# pdp8i-dec.net
KiCad netlist of a schematic drawn in EAGLE
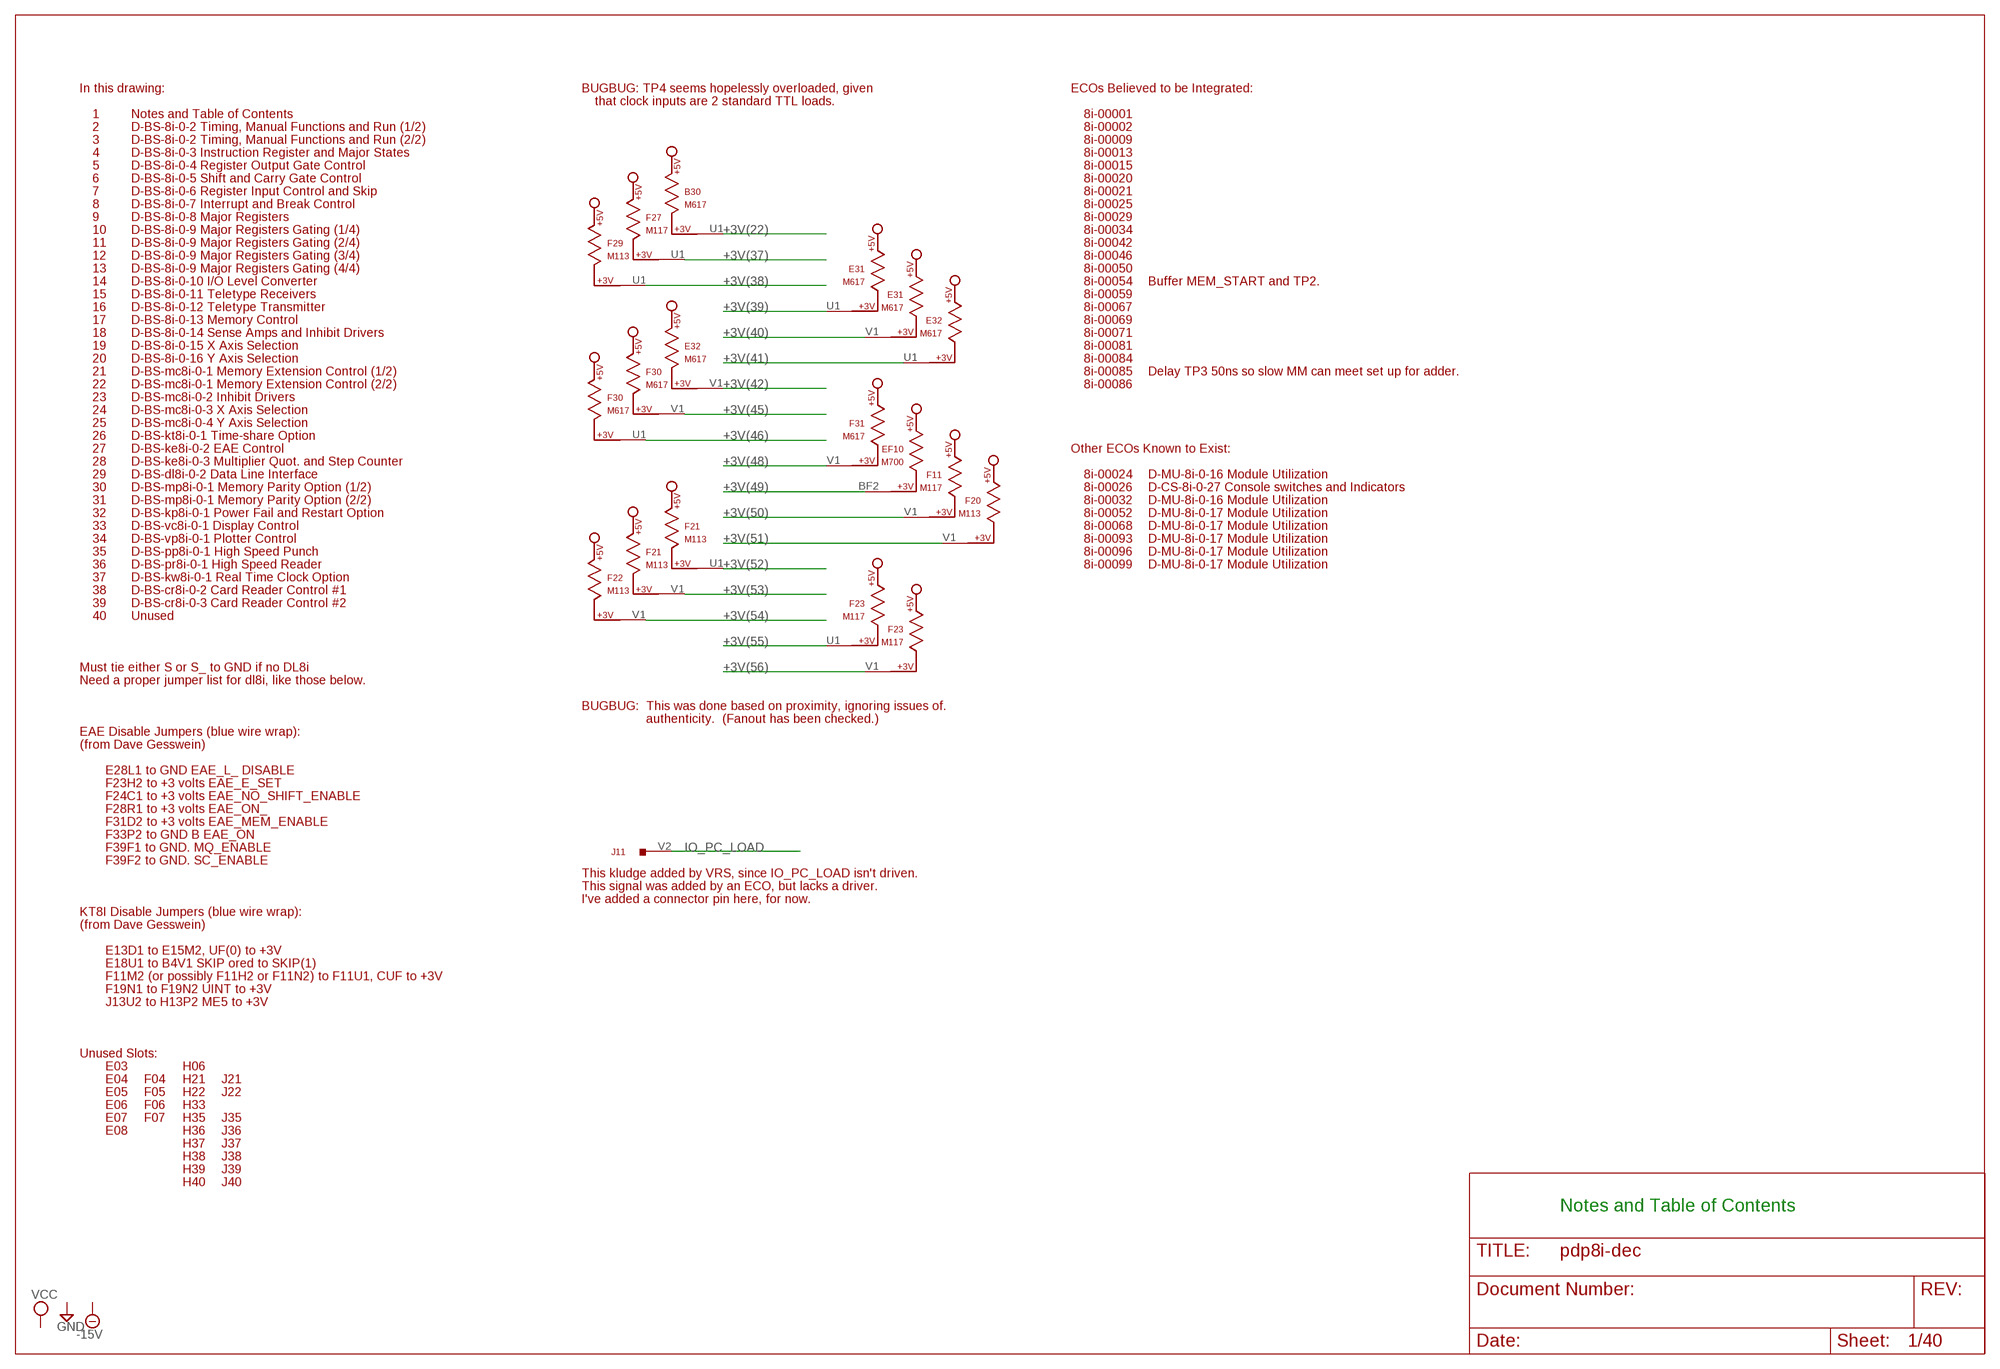
[diagram p0: schematic, sheet 1]
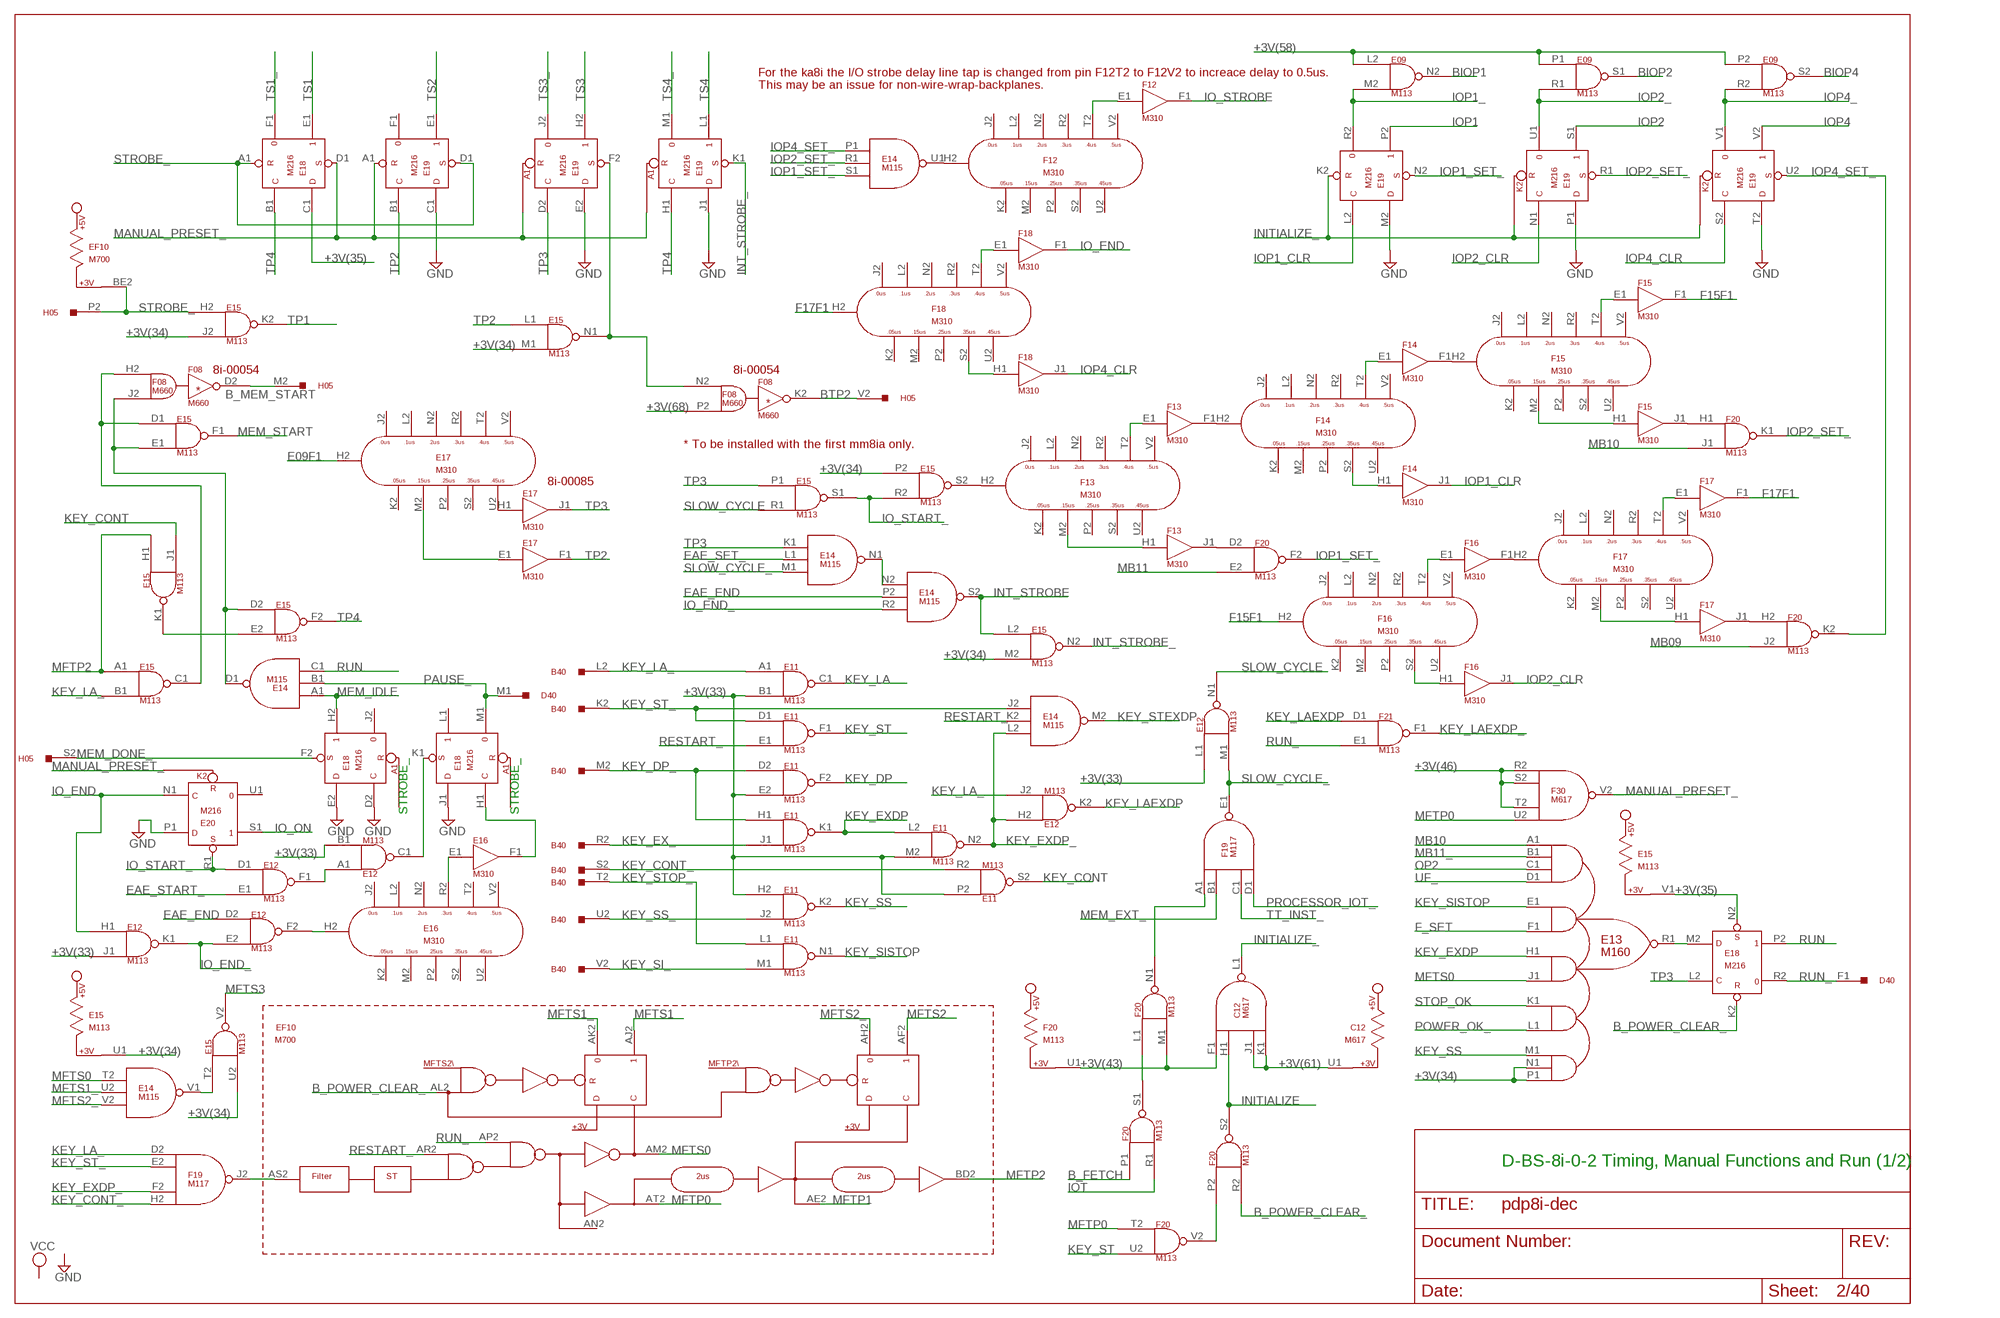
[diagram p1: schematic, sheet 2]
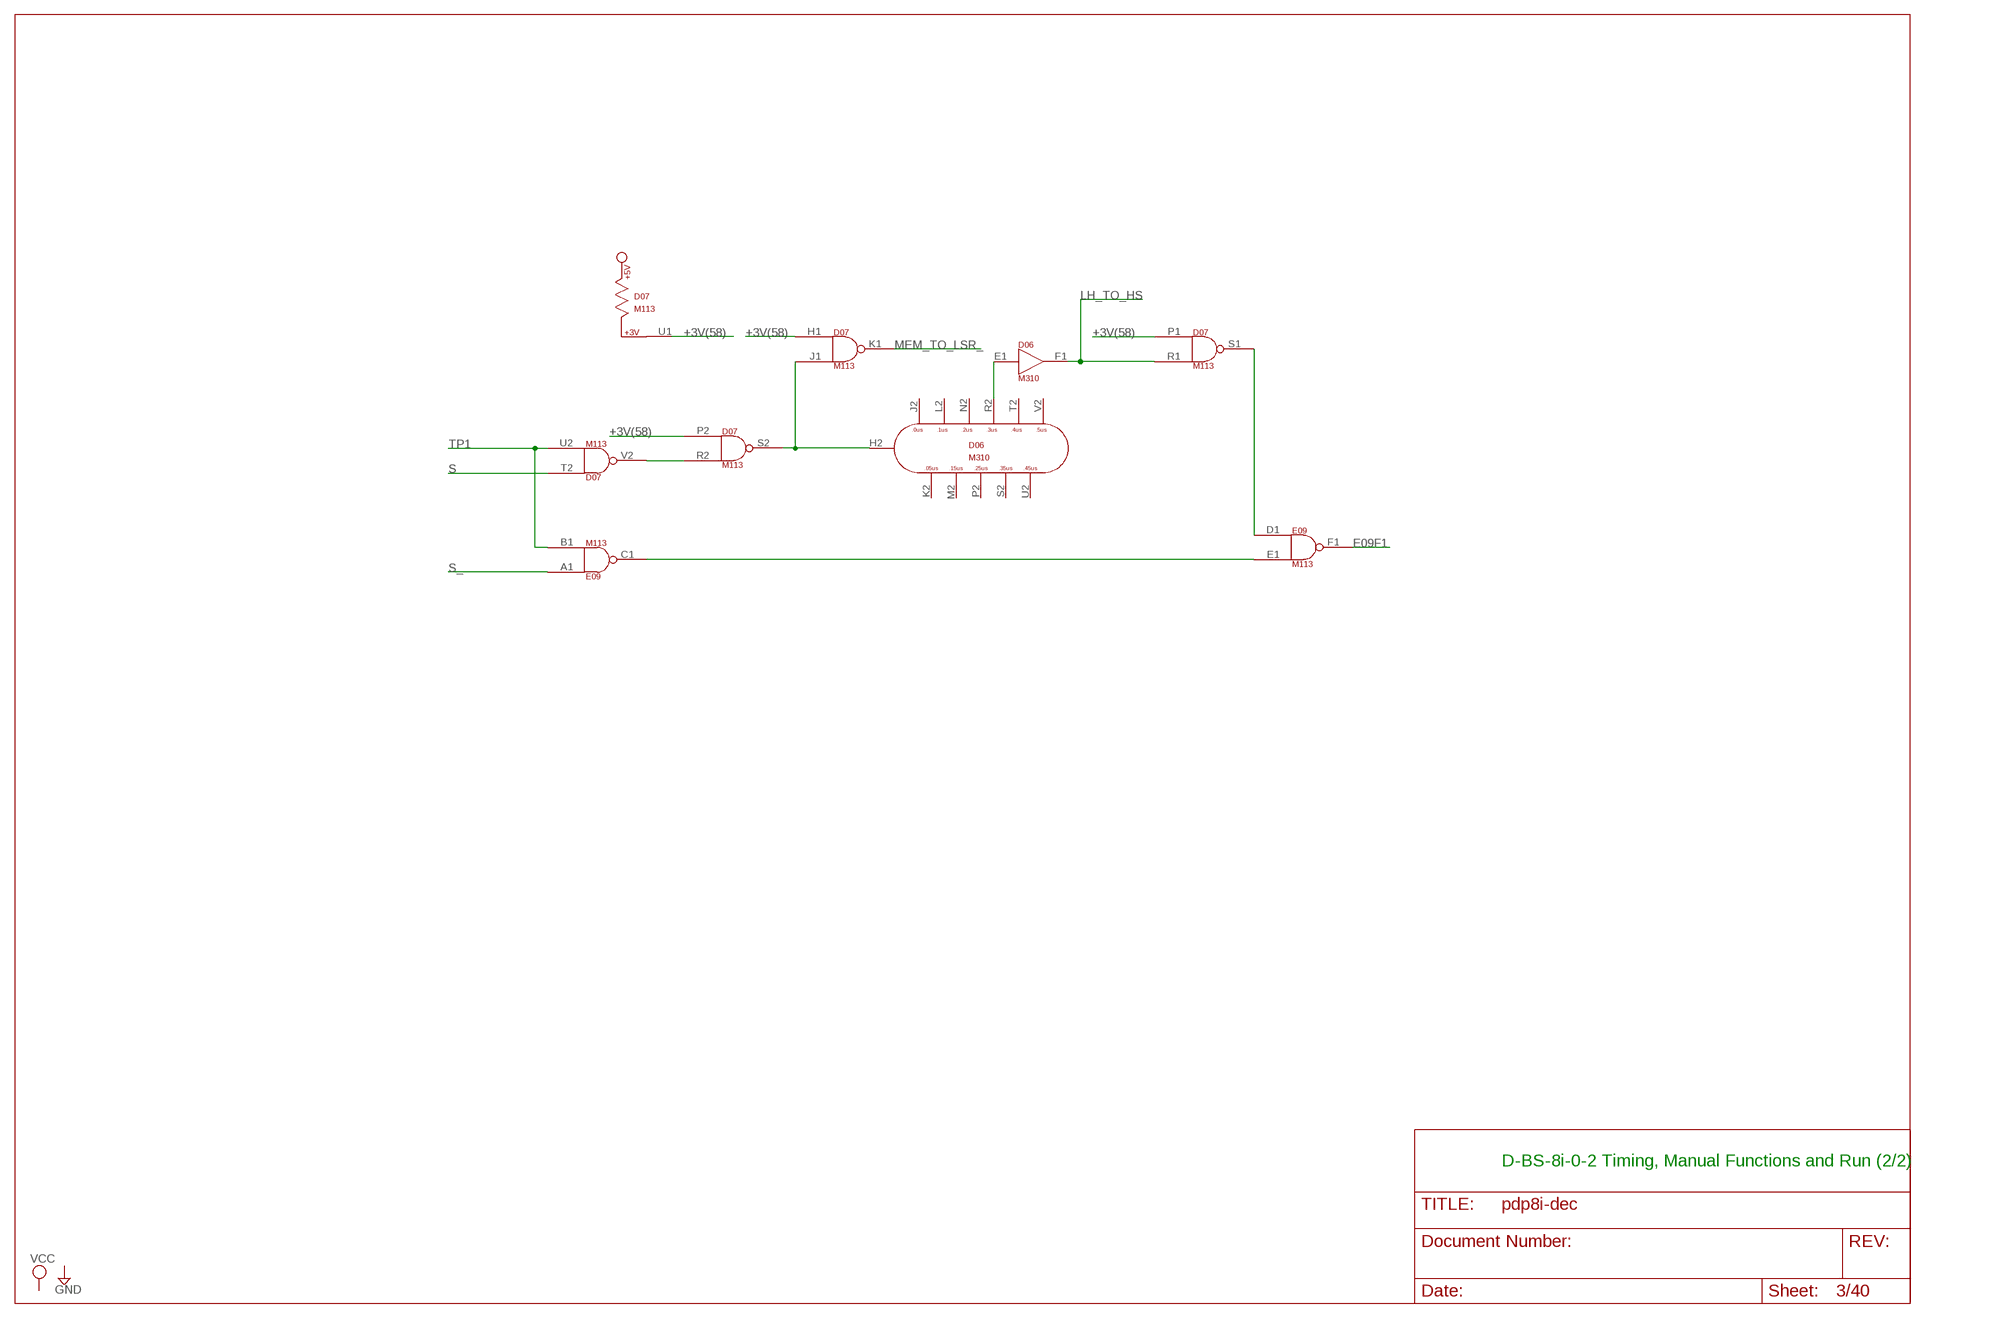
[diagram p2: schematic, sheet 3]
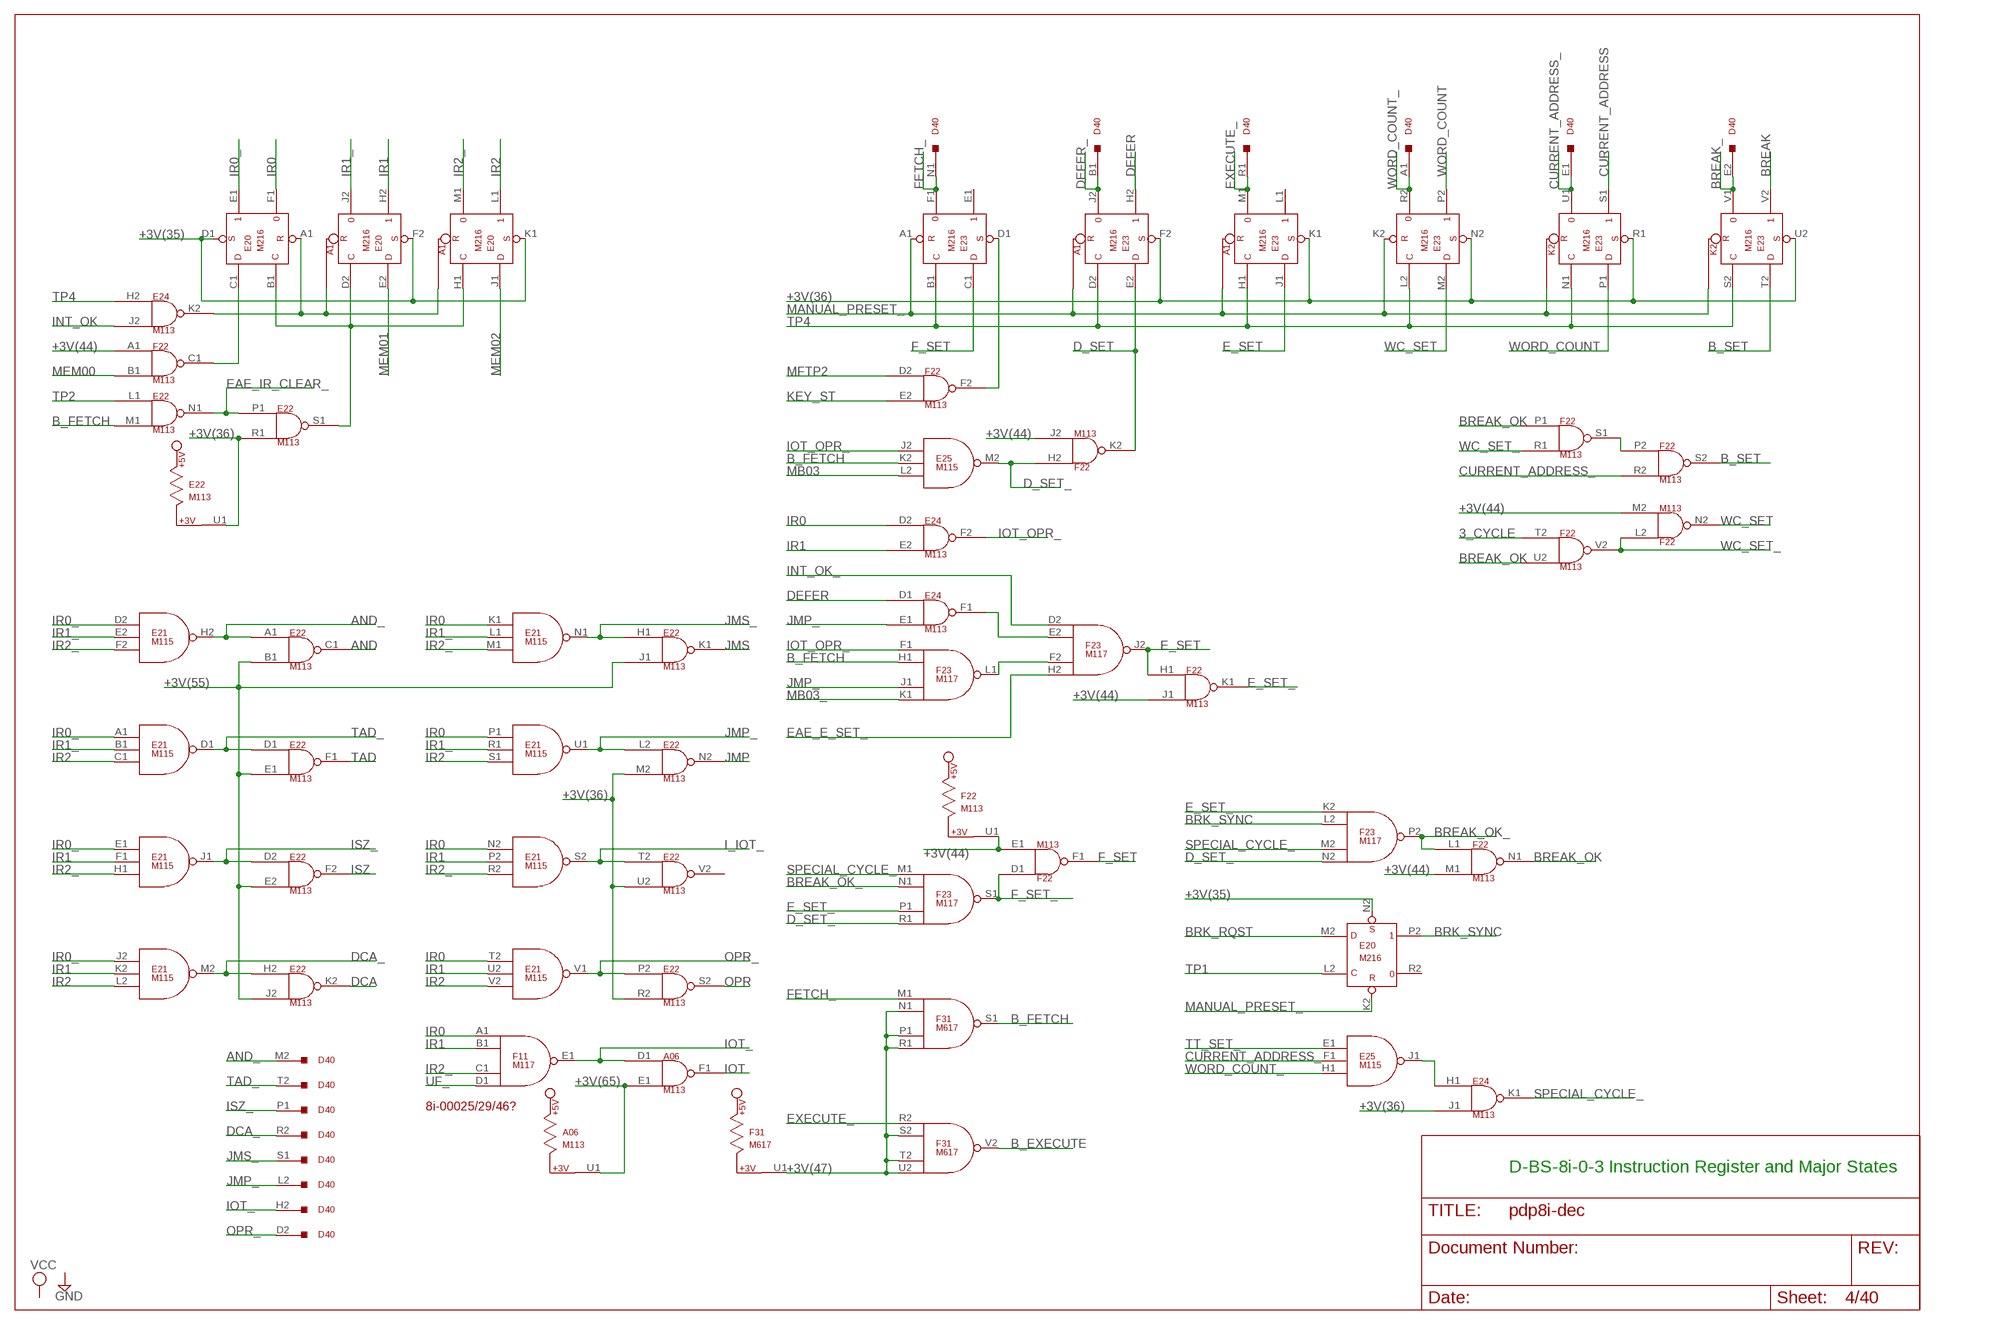
[diagram p3: schematic, sheet 4]
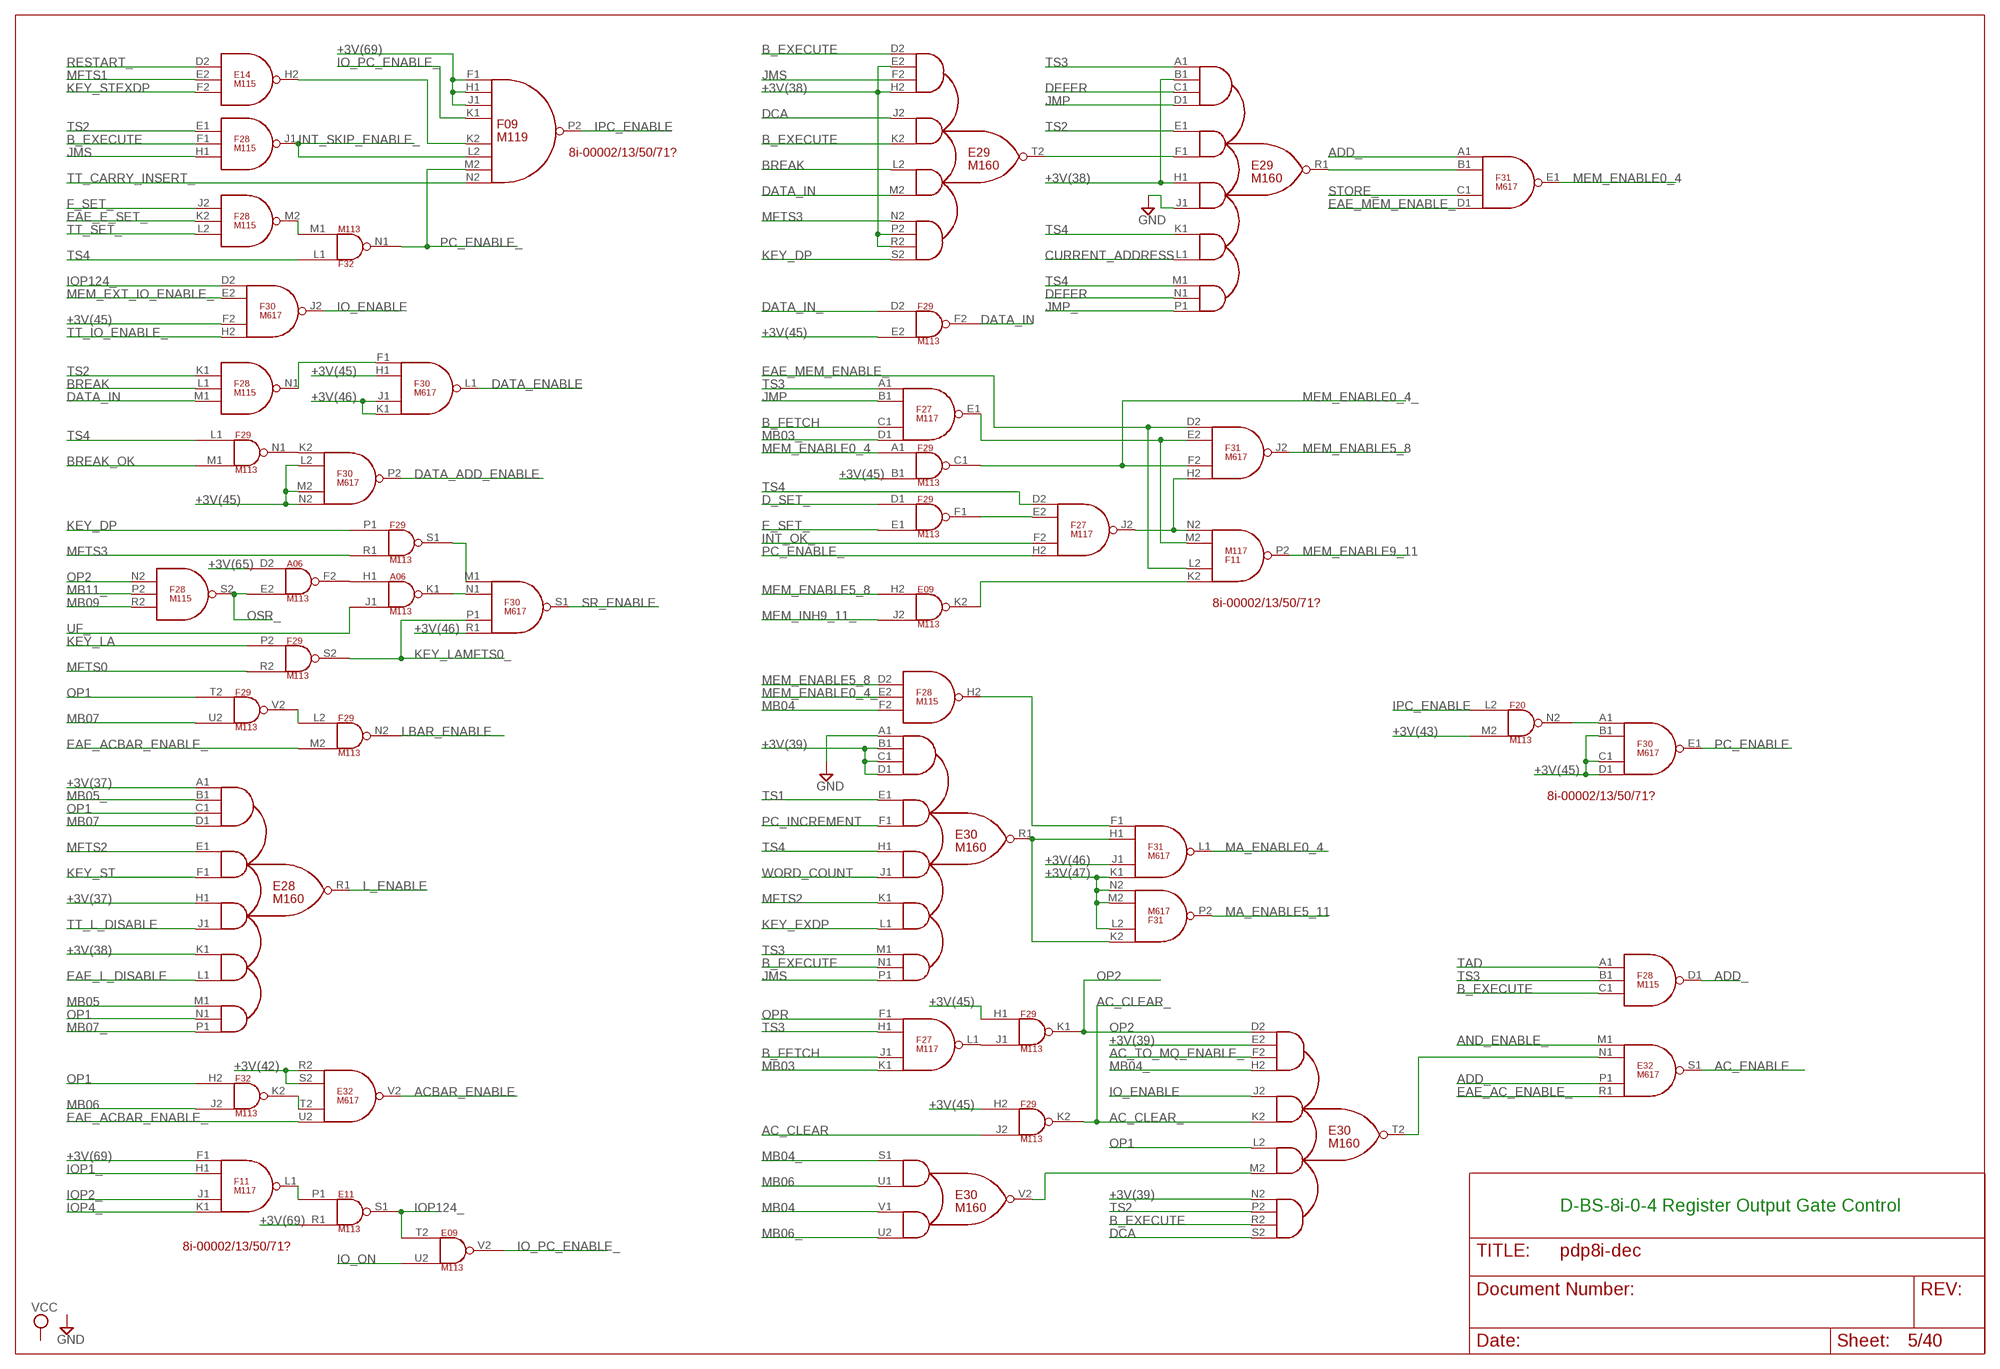
[diagram p4: schematic, sheet 5]
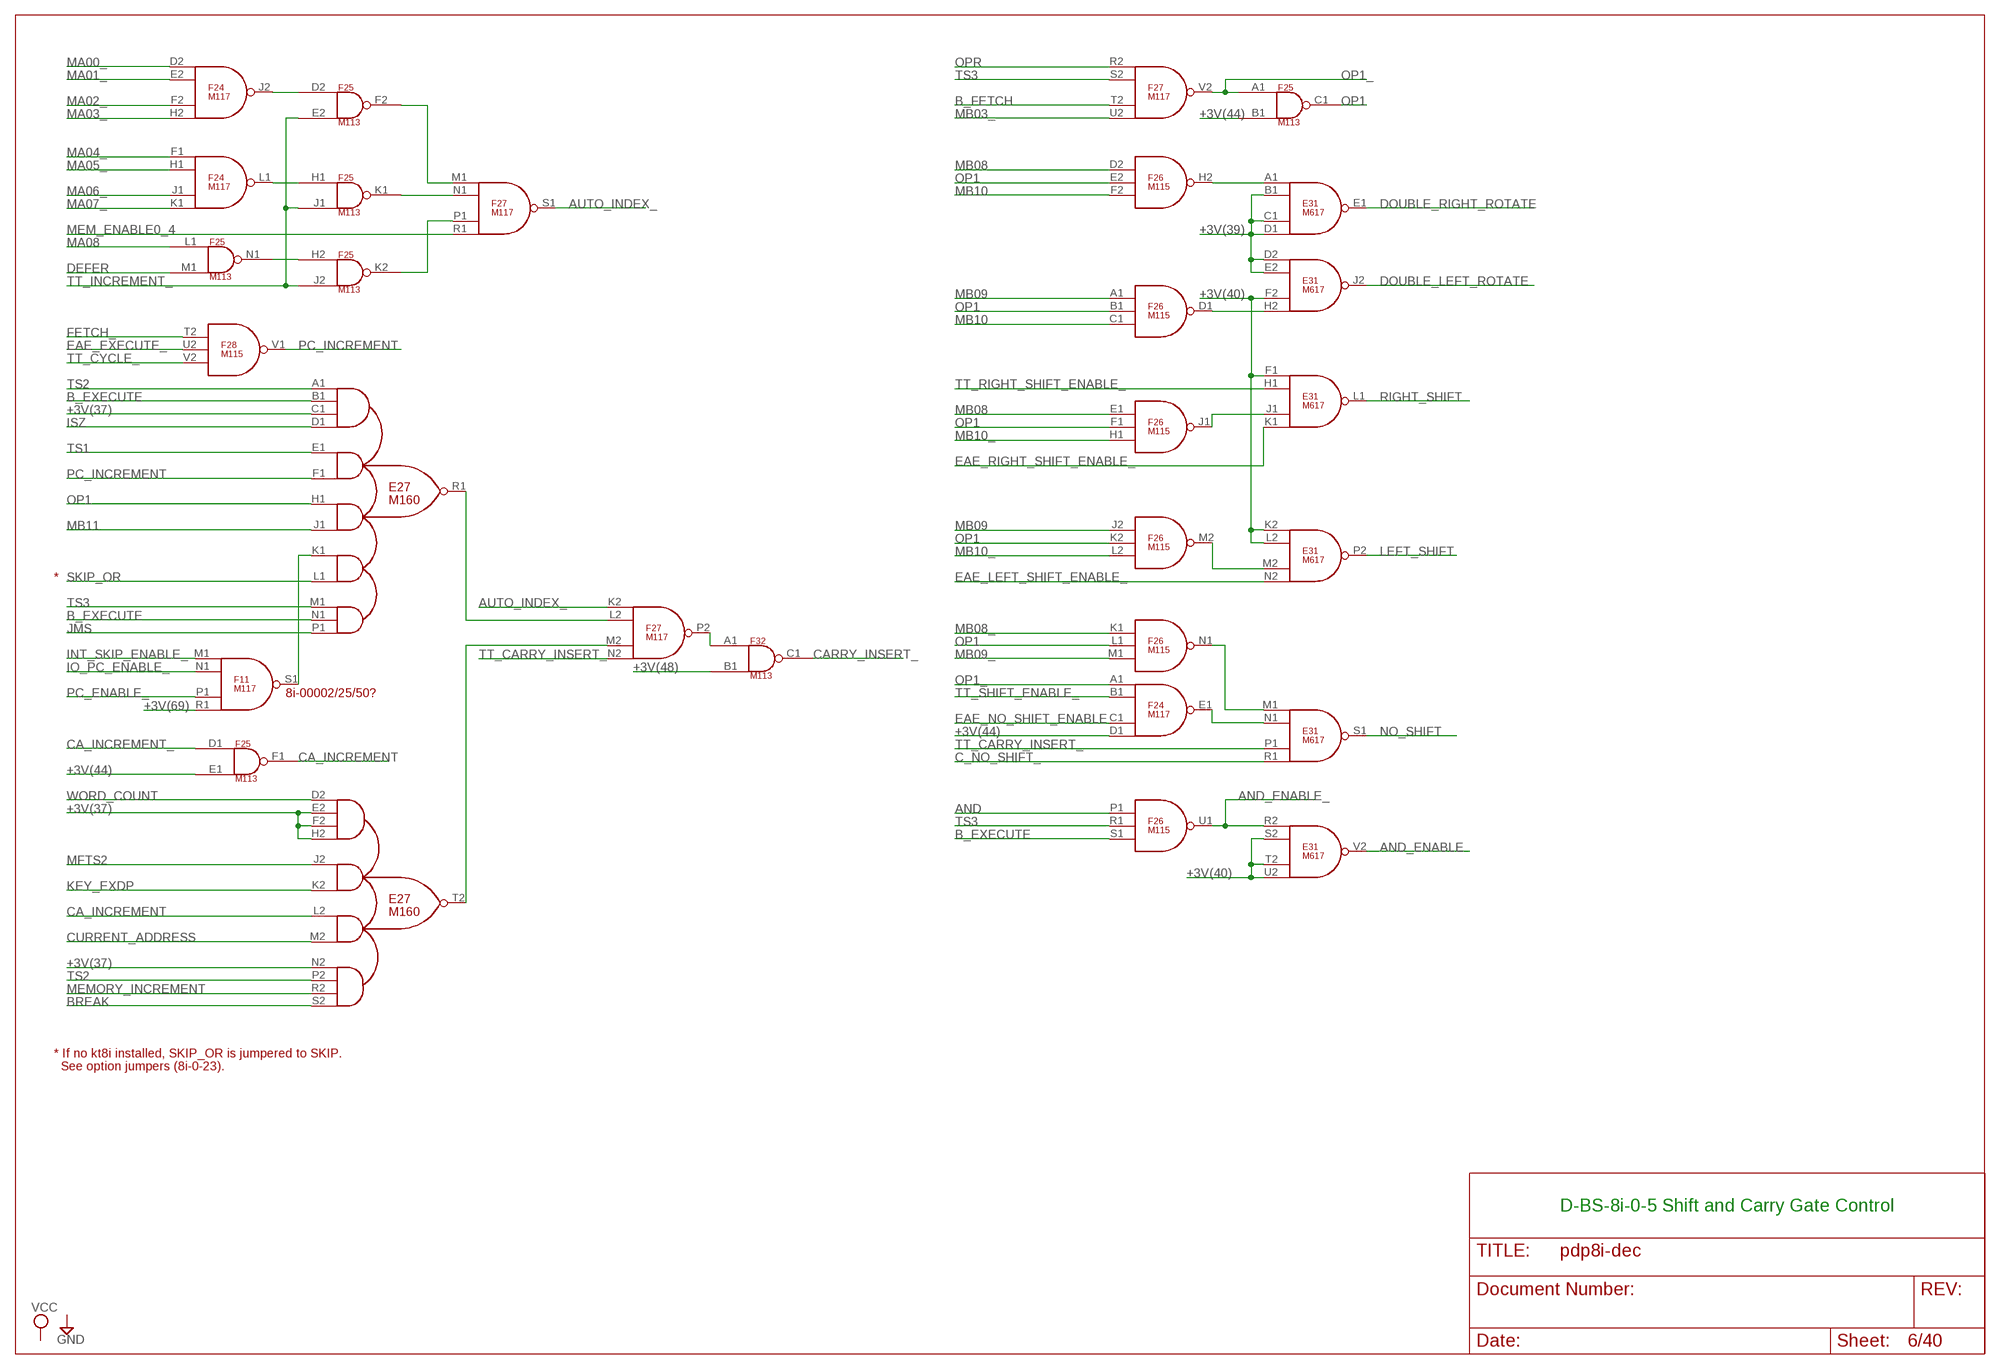
[diagram p5: schematic, sheet 6]
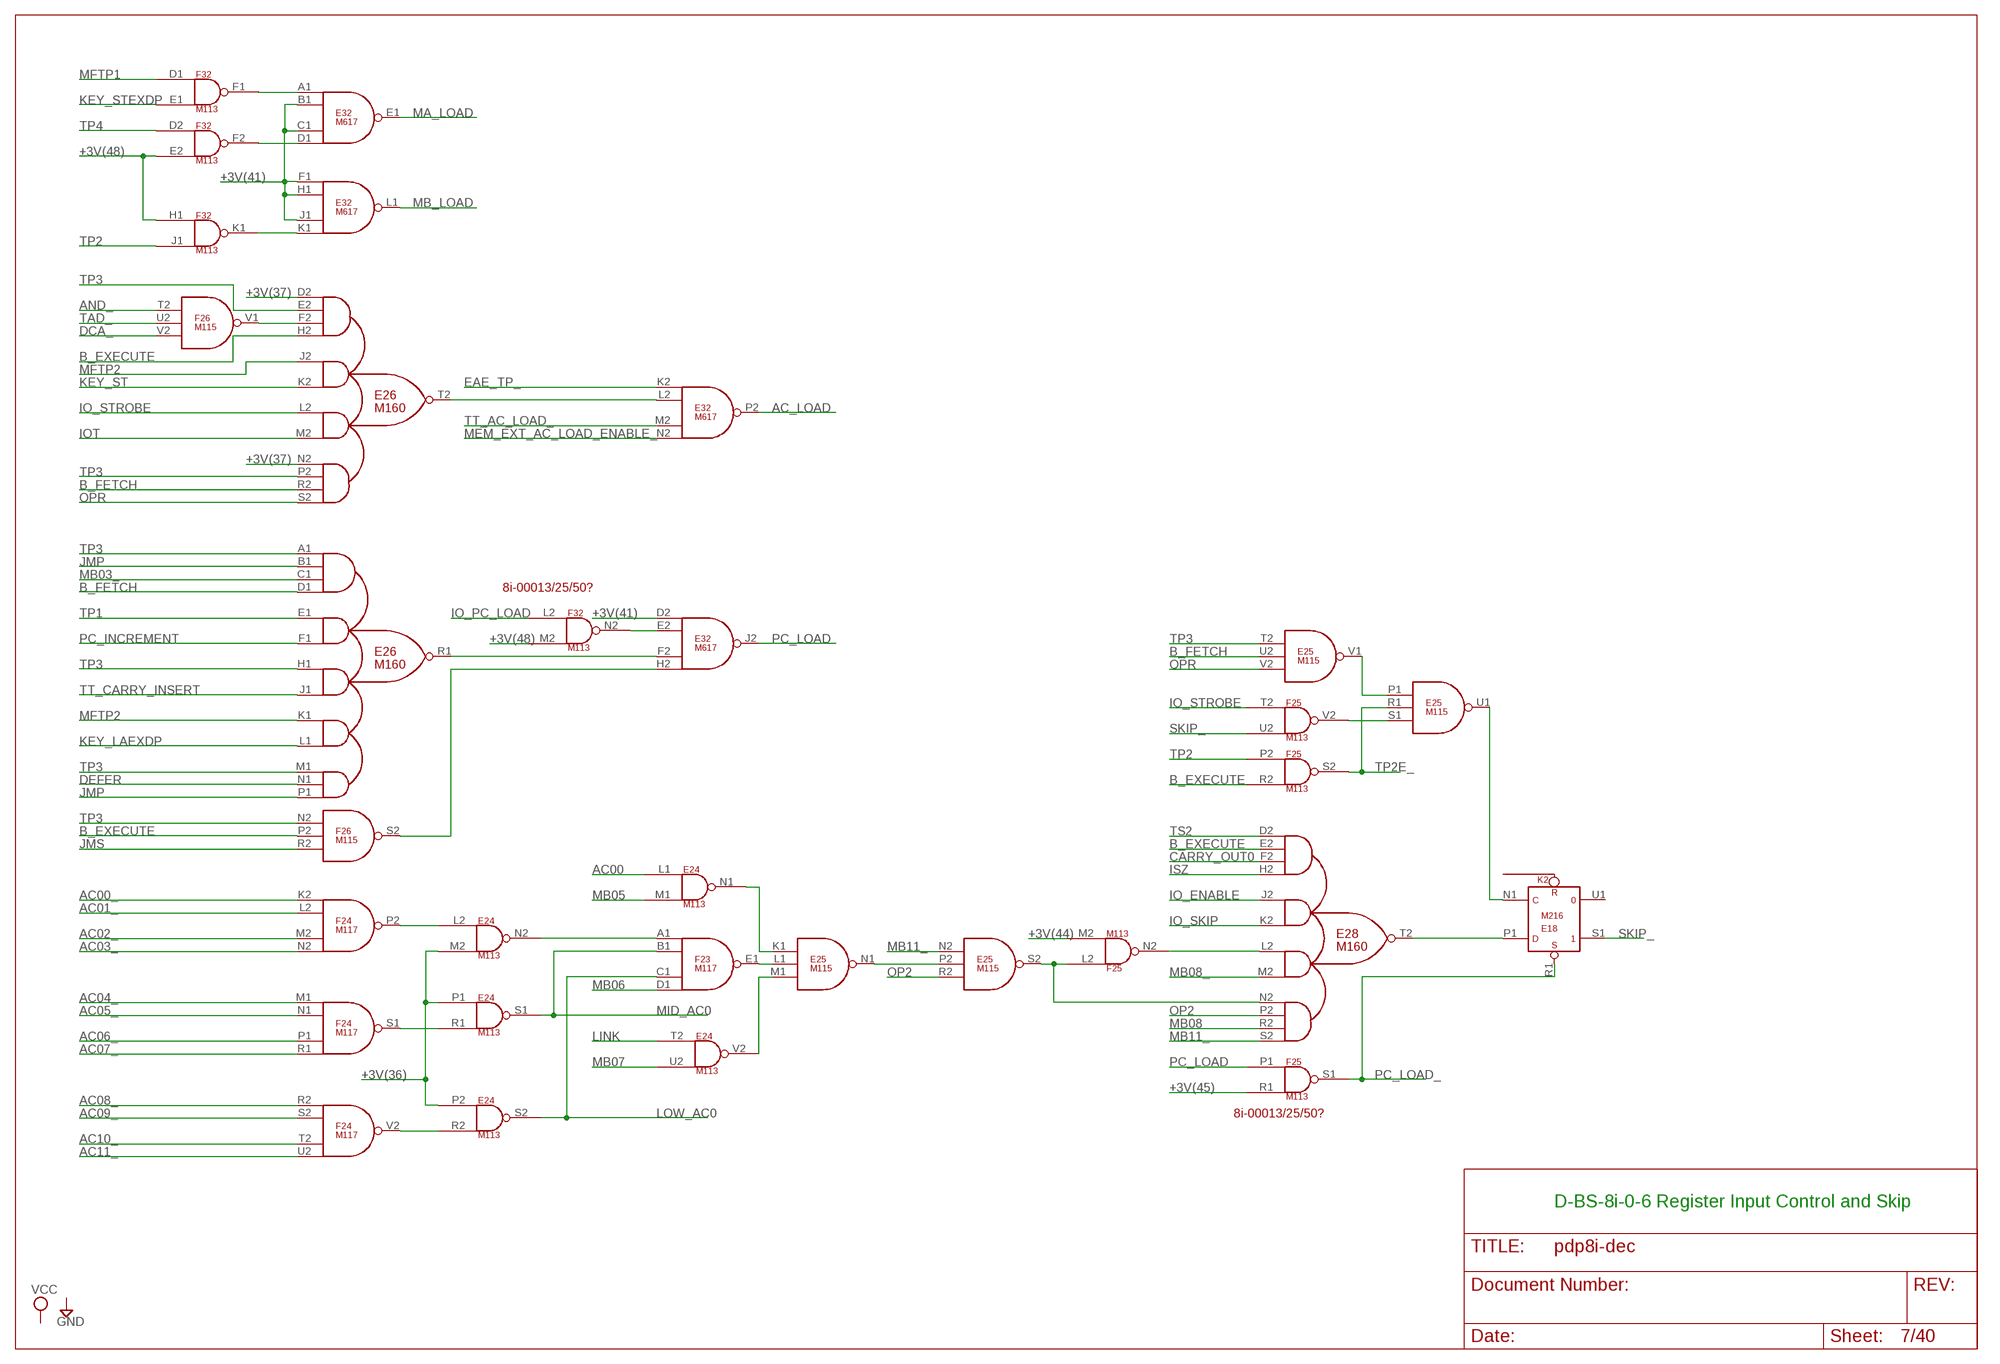
[diagram p6: schematic, sheet 7]
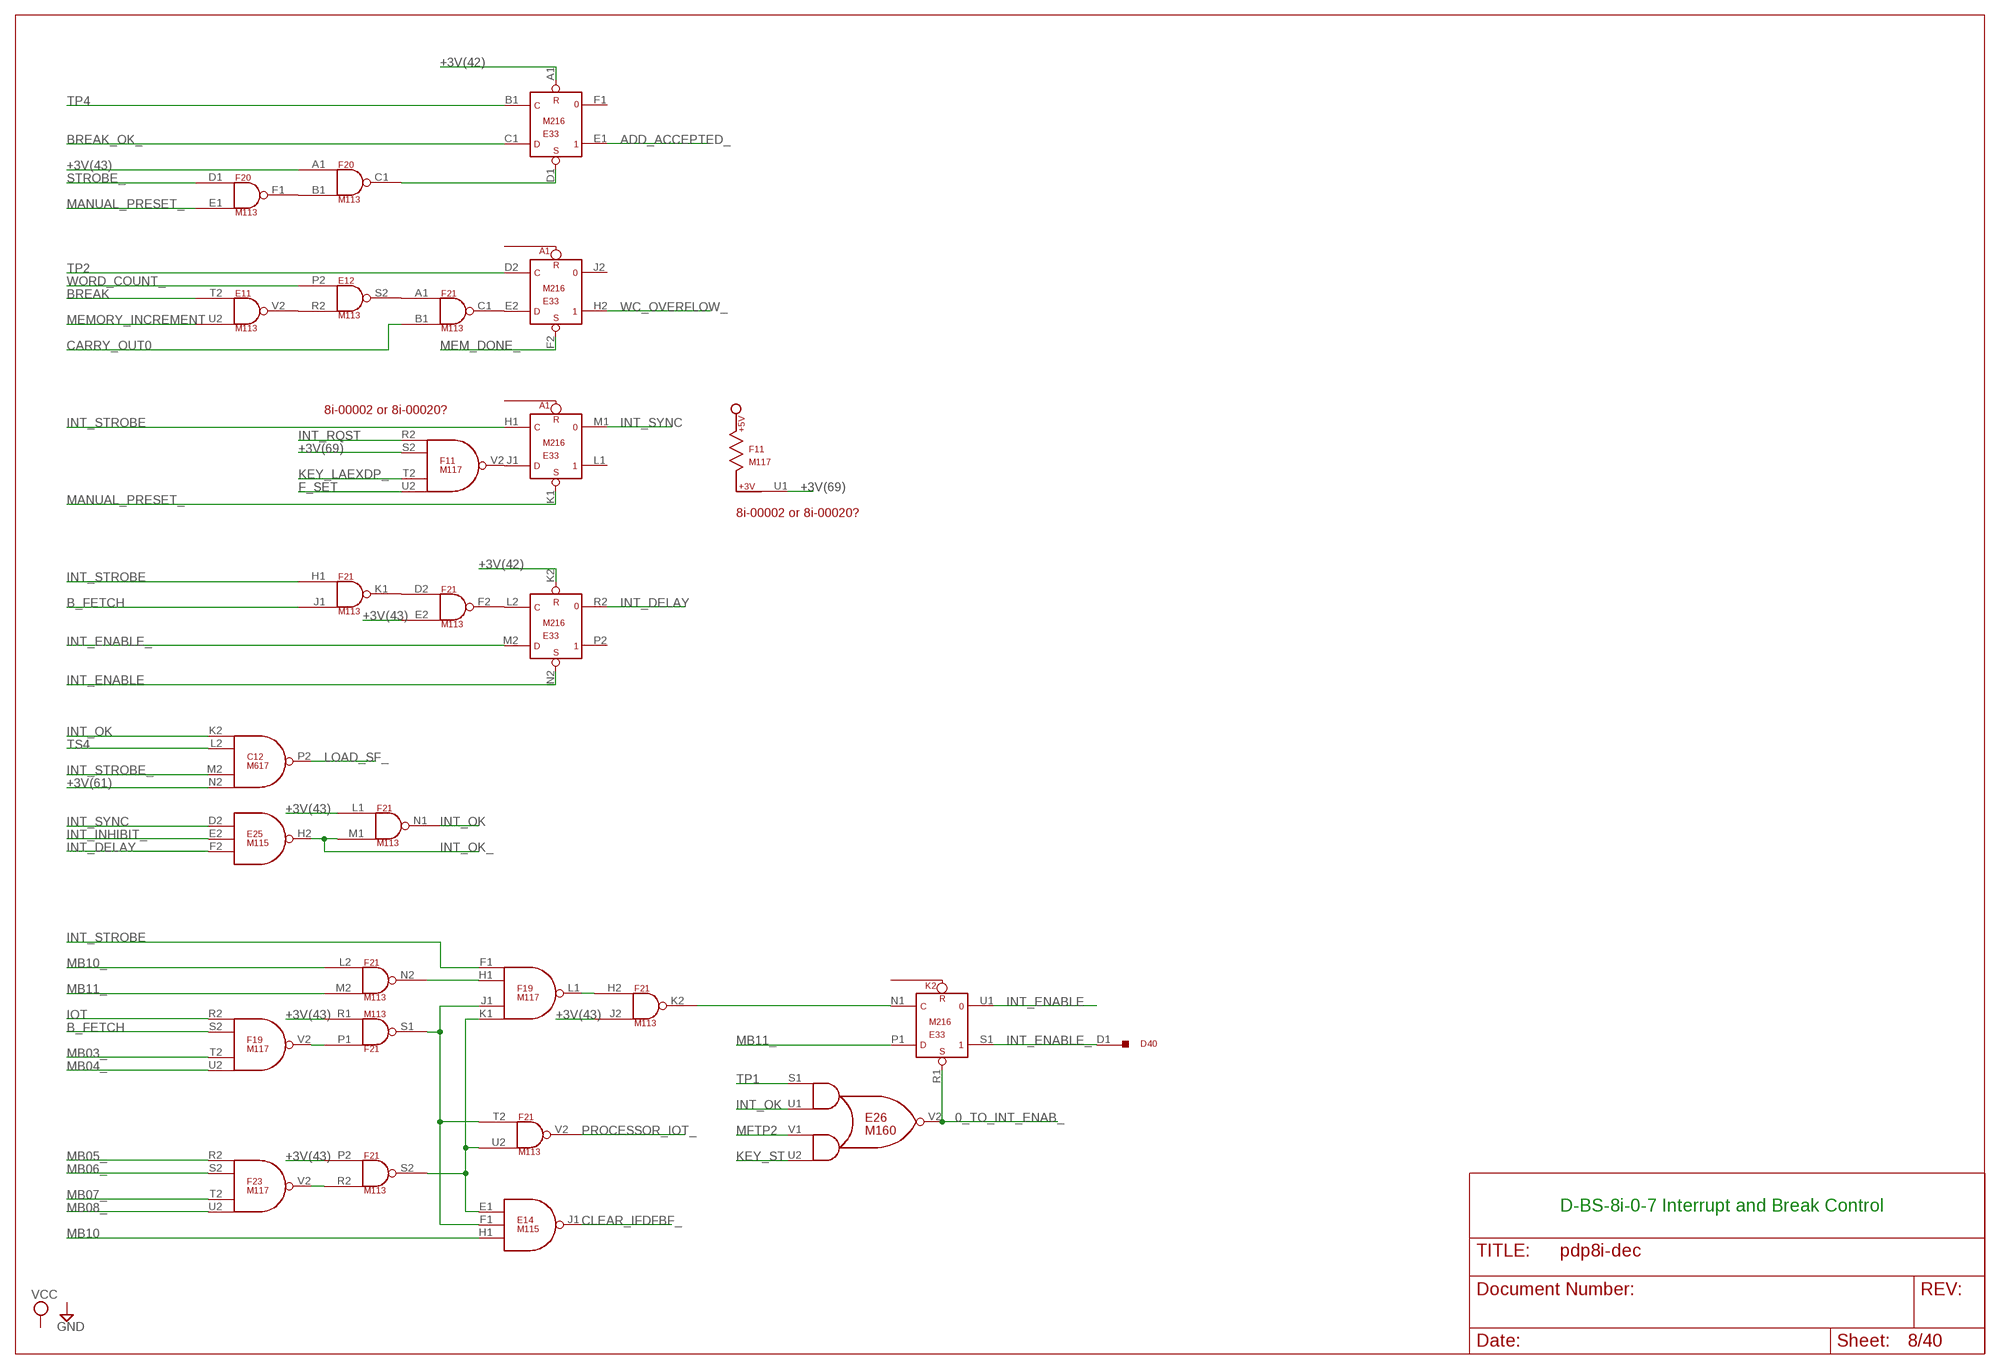
[diagram p7: schematic, sheet 8]
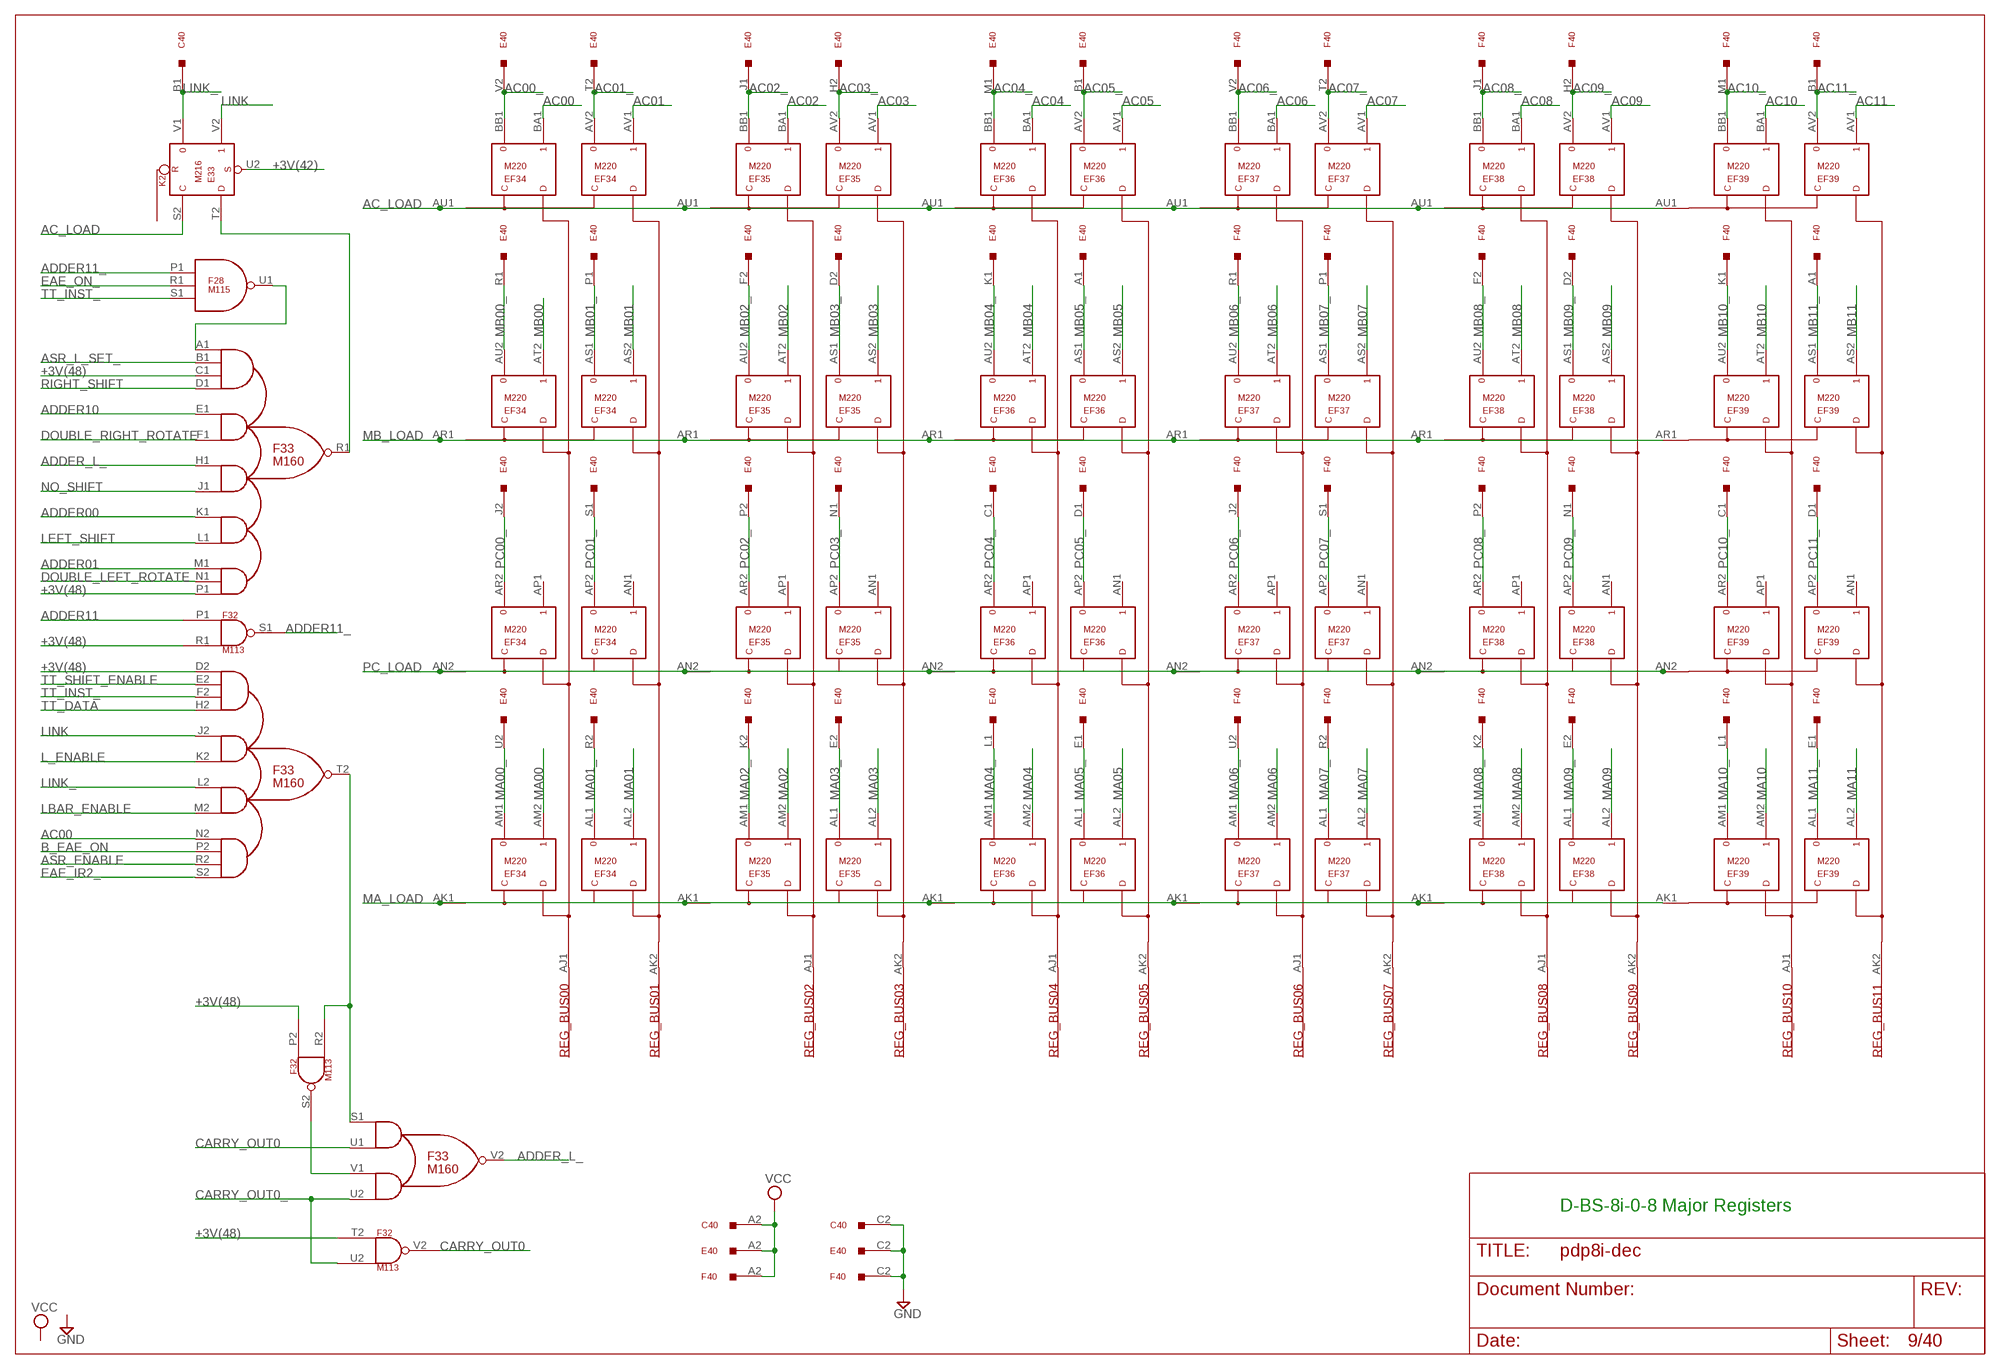
[diagram p8: schematic, sheet 9]
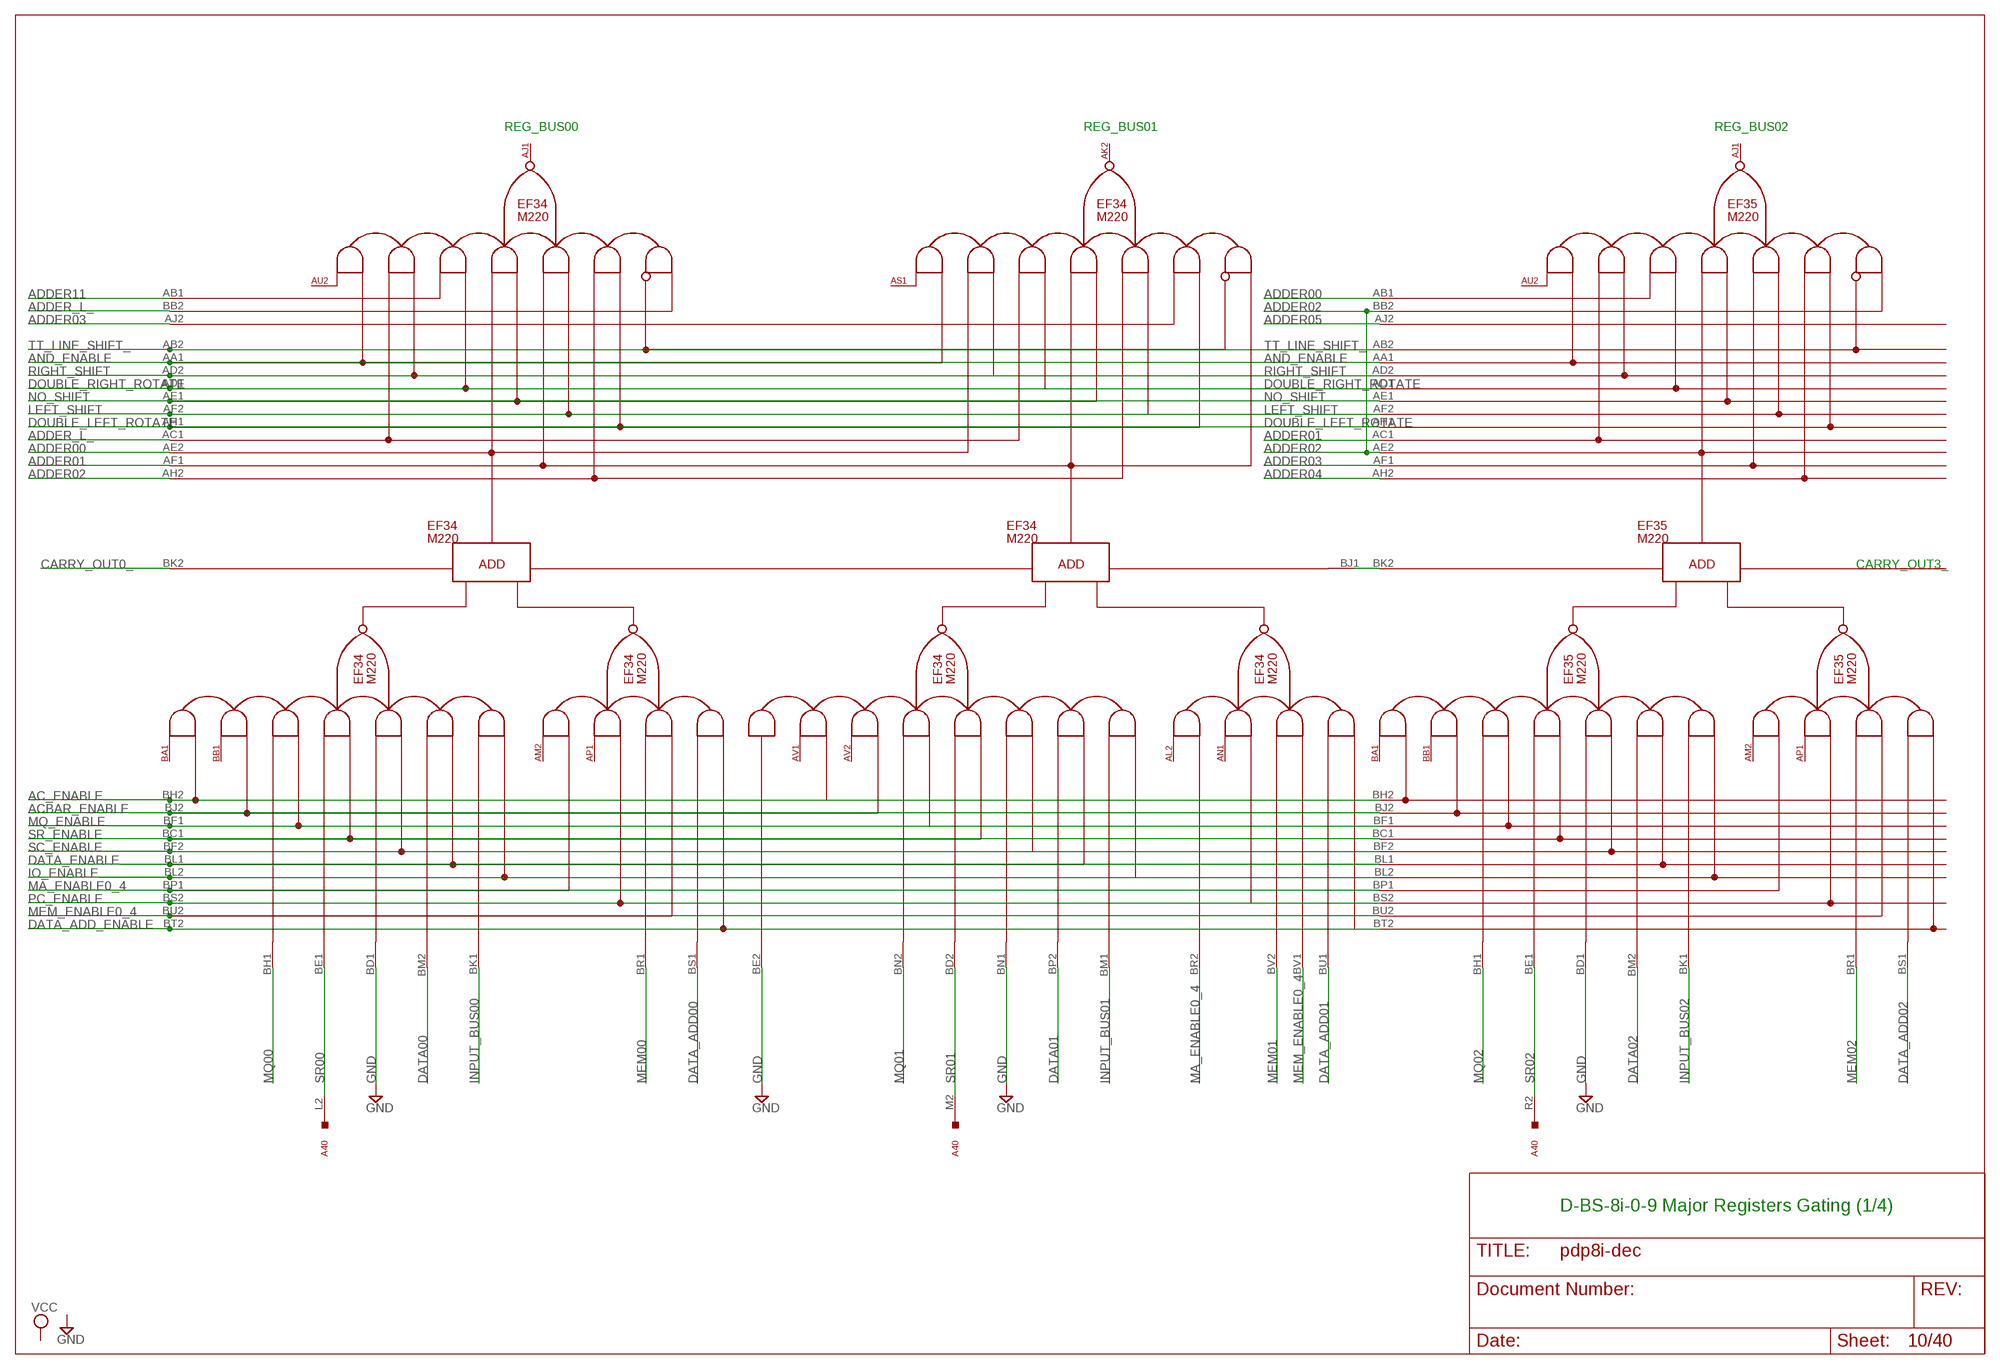
[diagram p9: schematic, sheet 10]
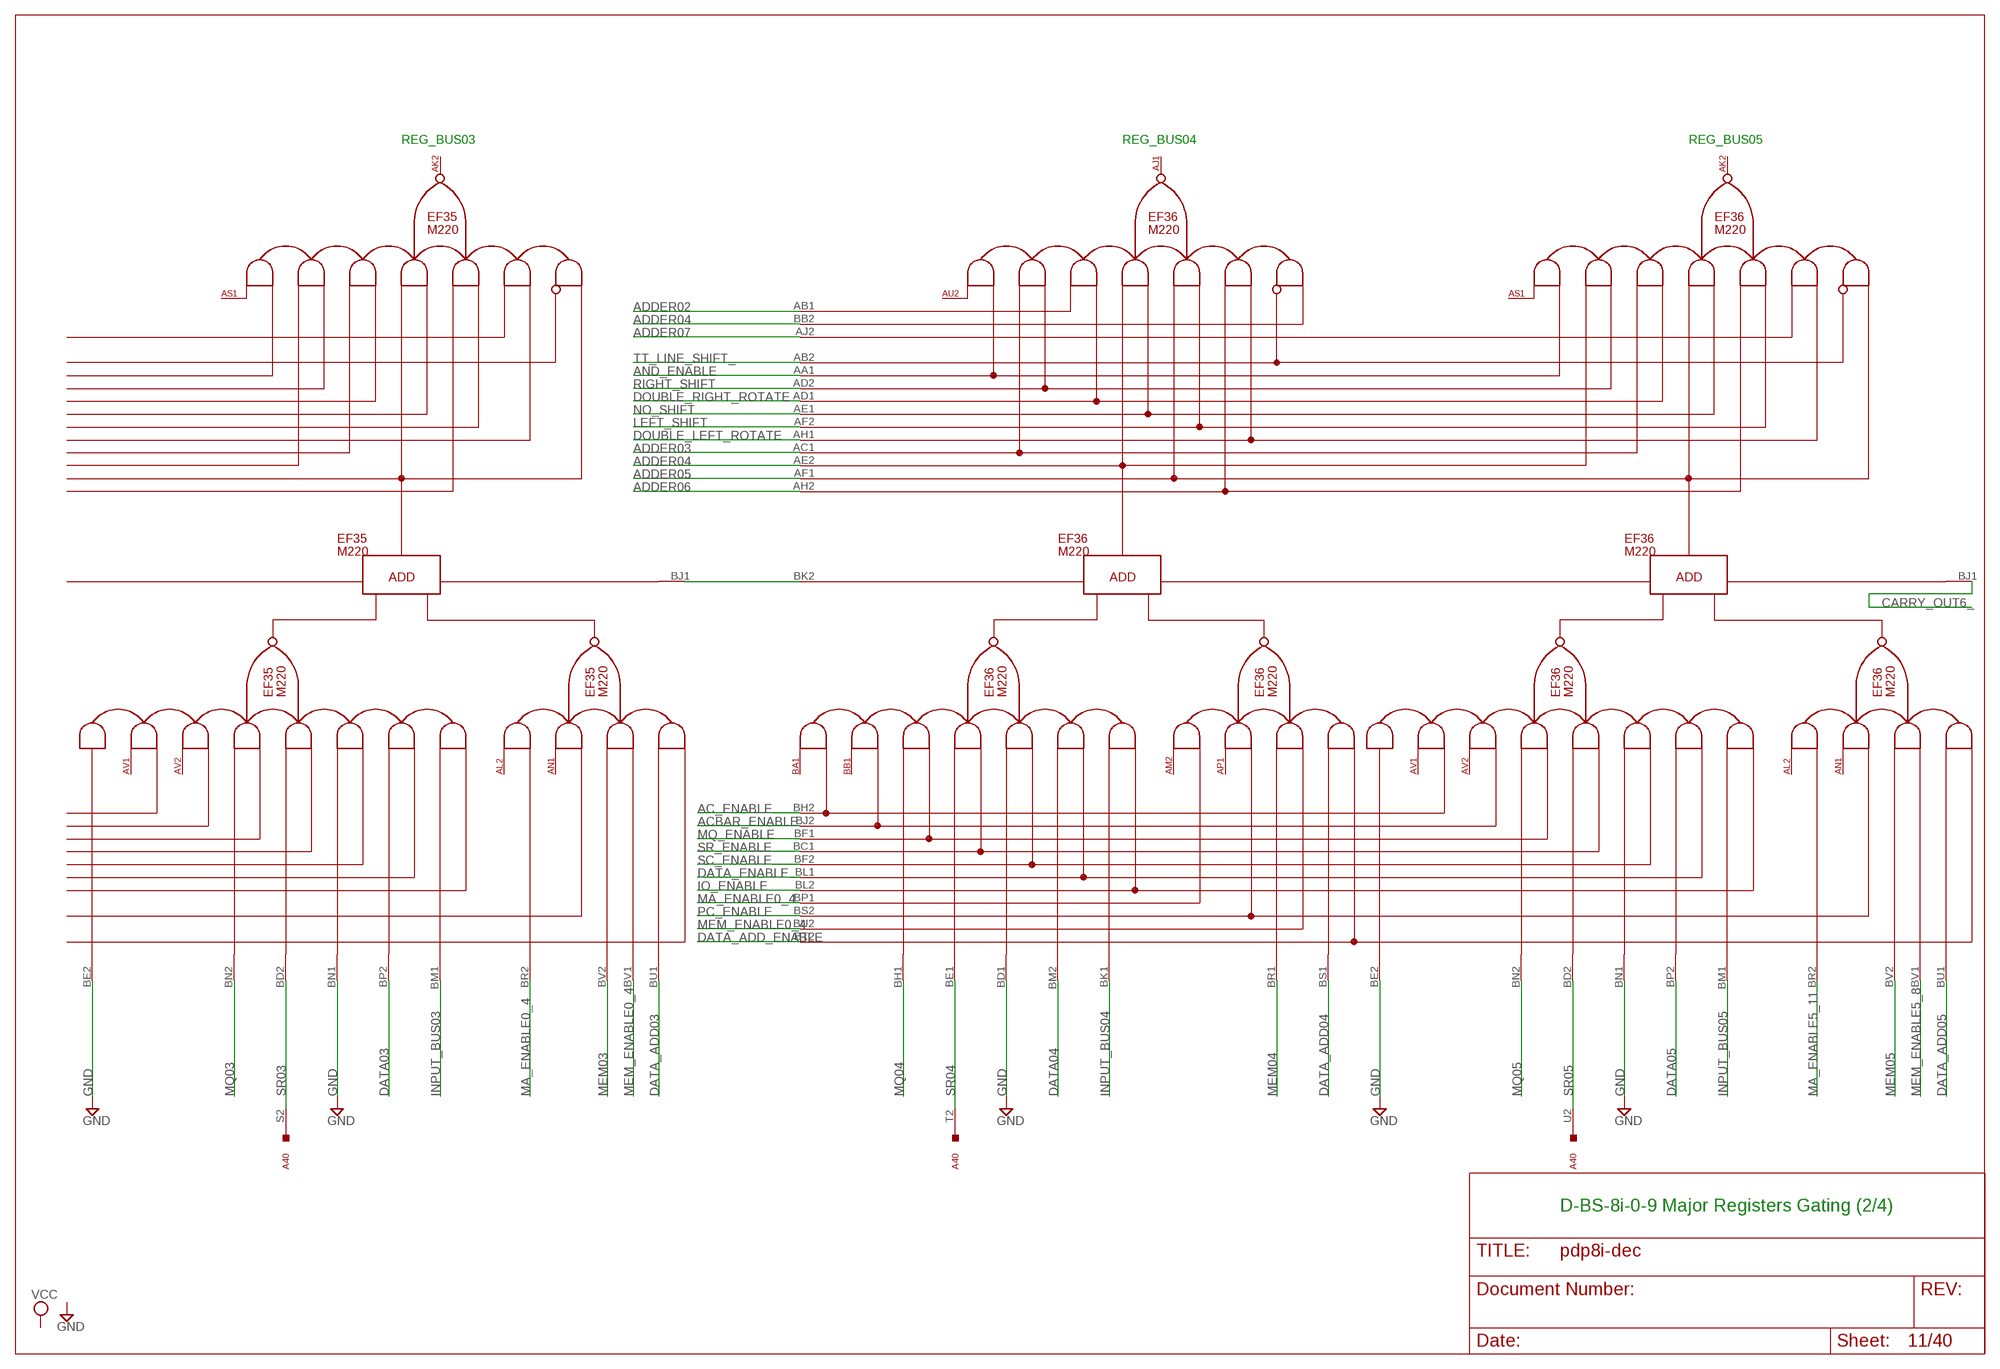
[diagram p10: schematic, sheet 11]
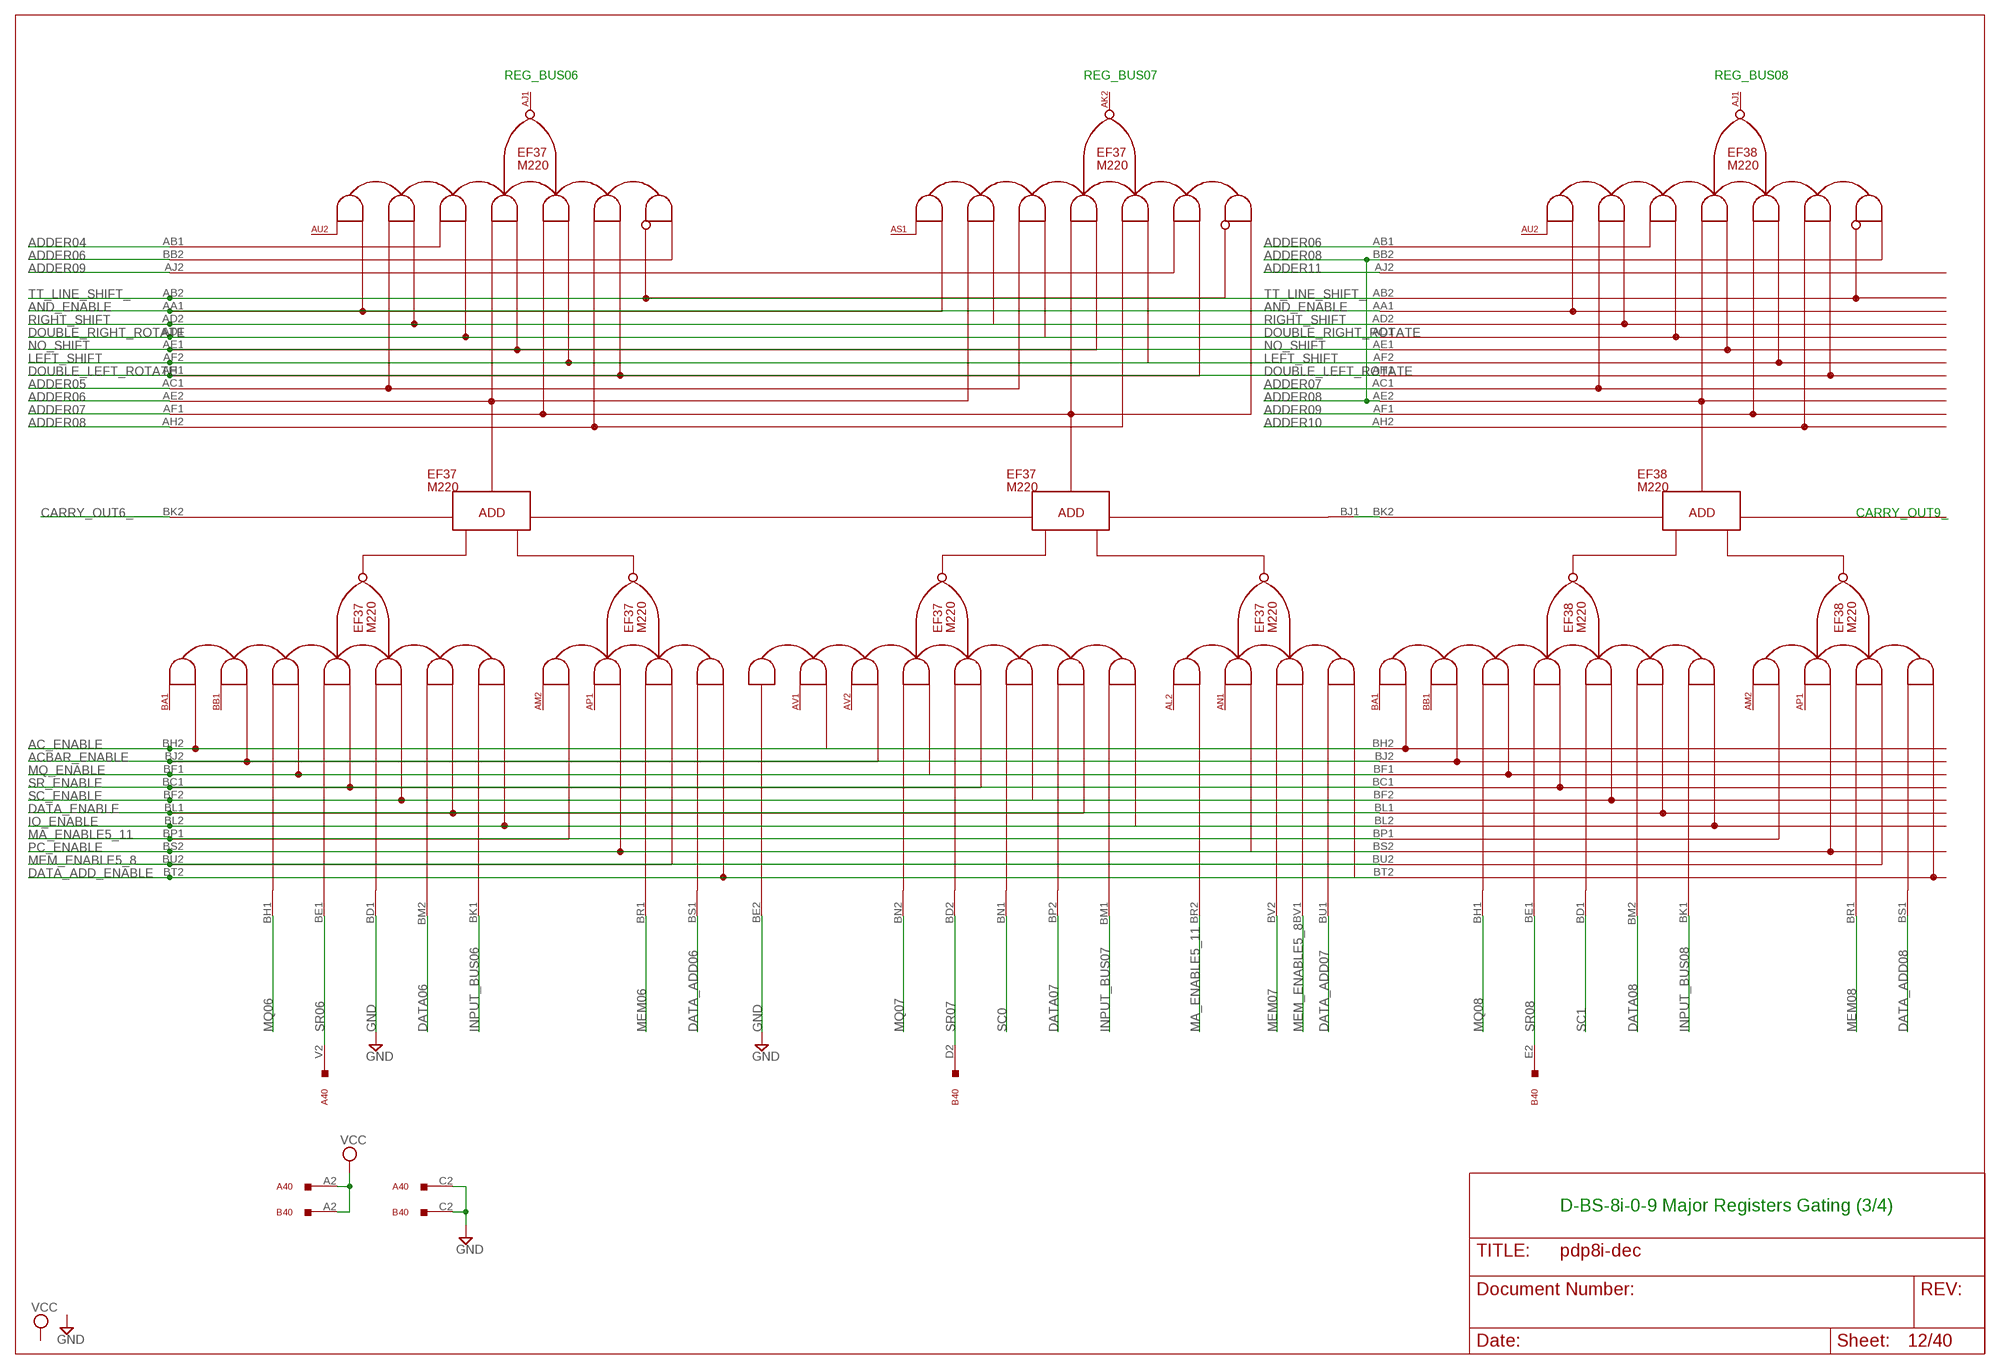
[diagram p11: schematic, sheet 12]
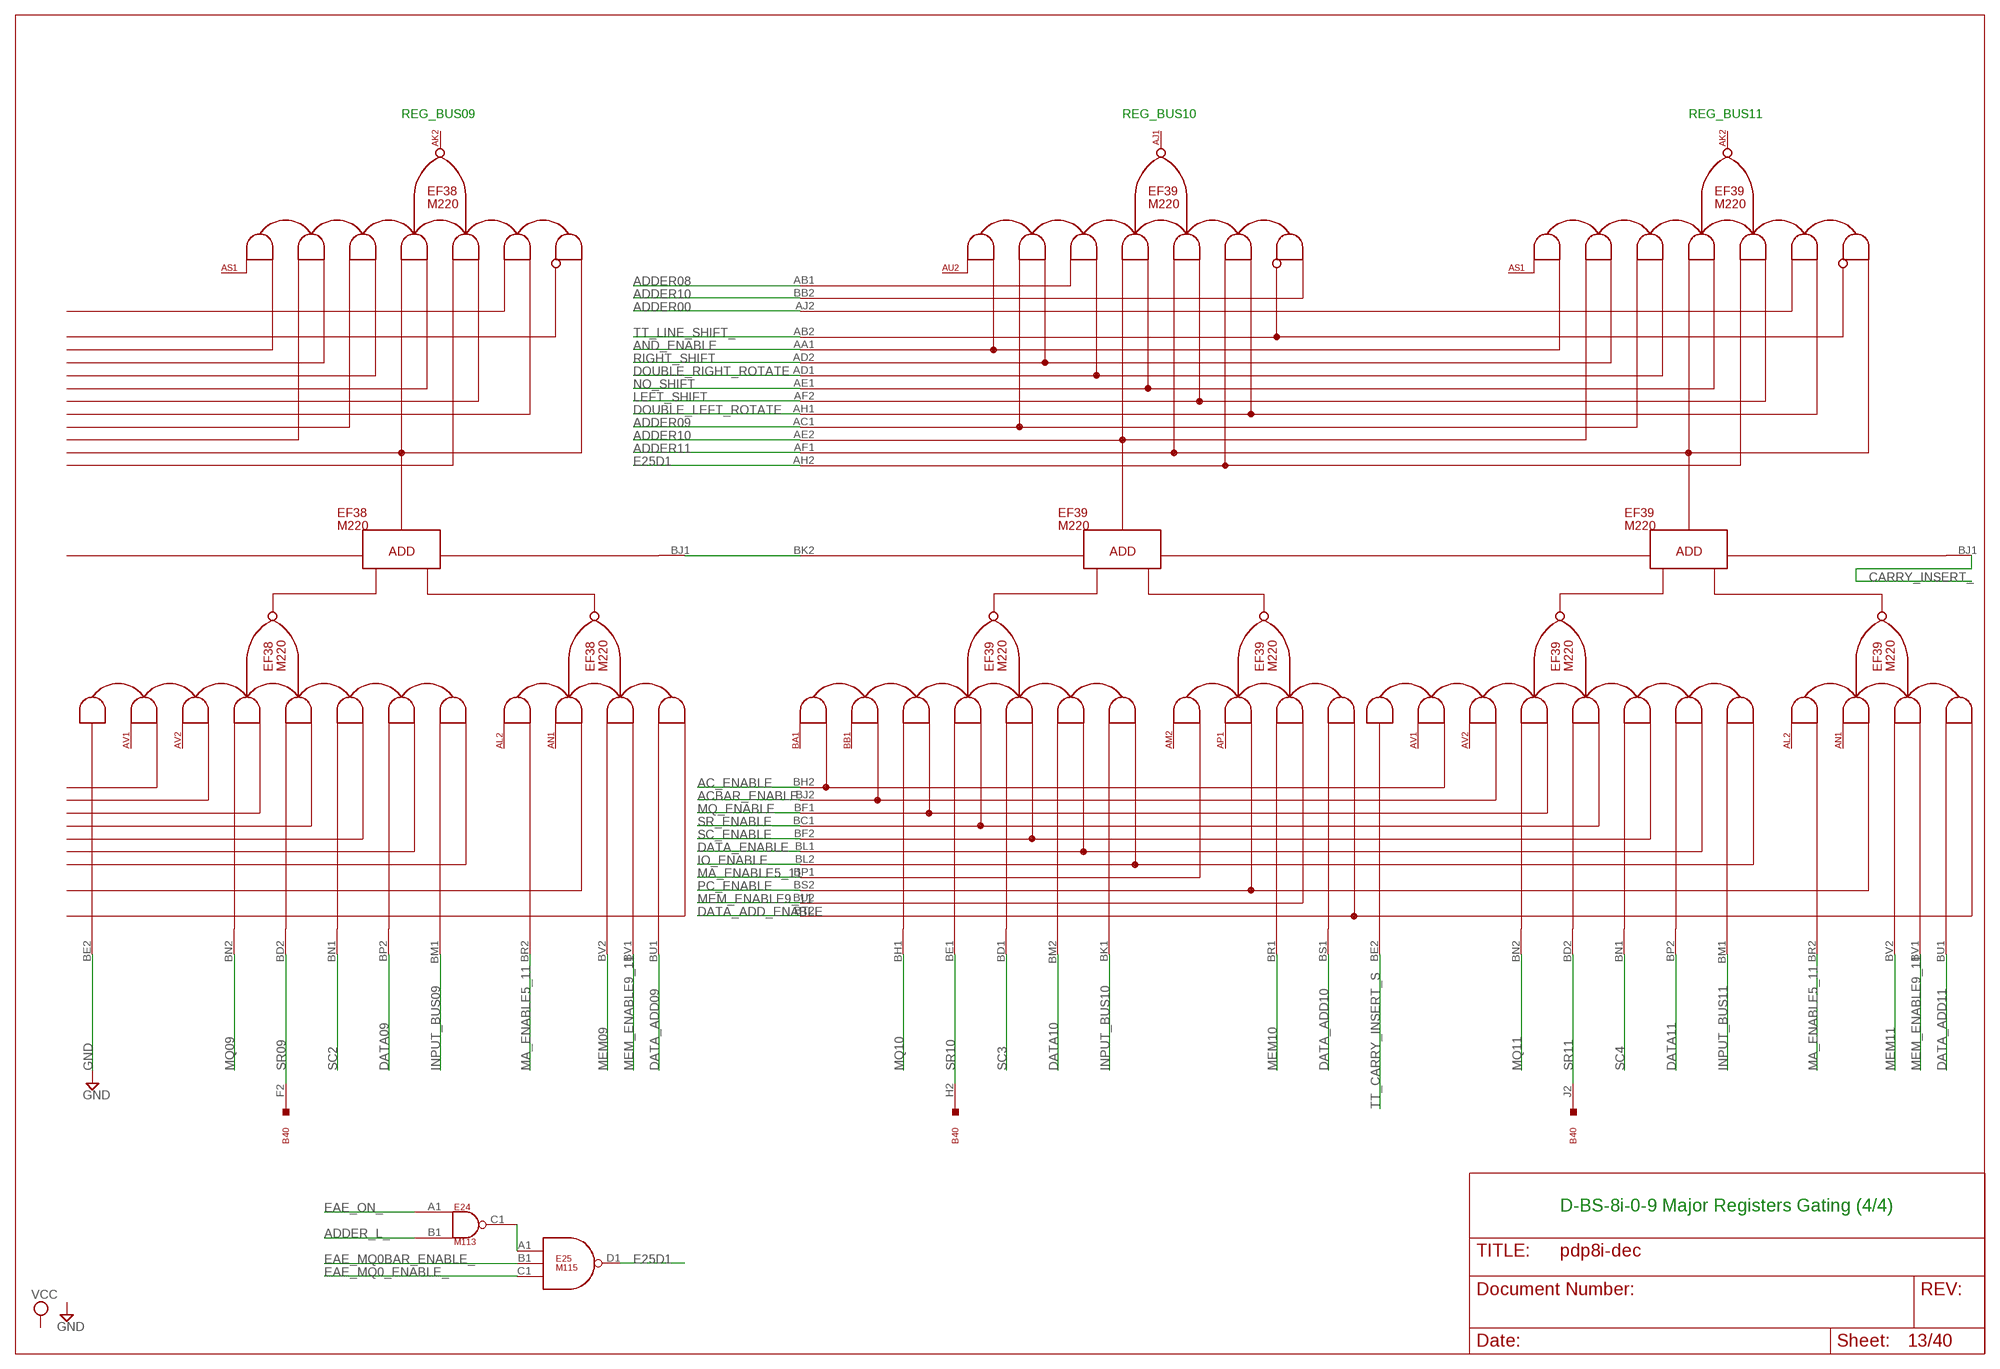
[diagram p12: schematic, sheet 13]
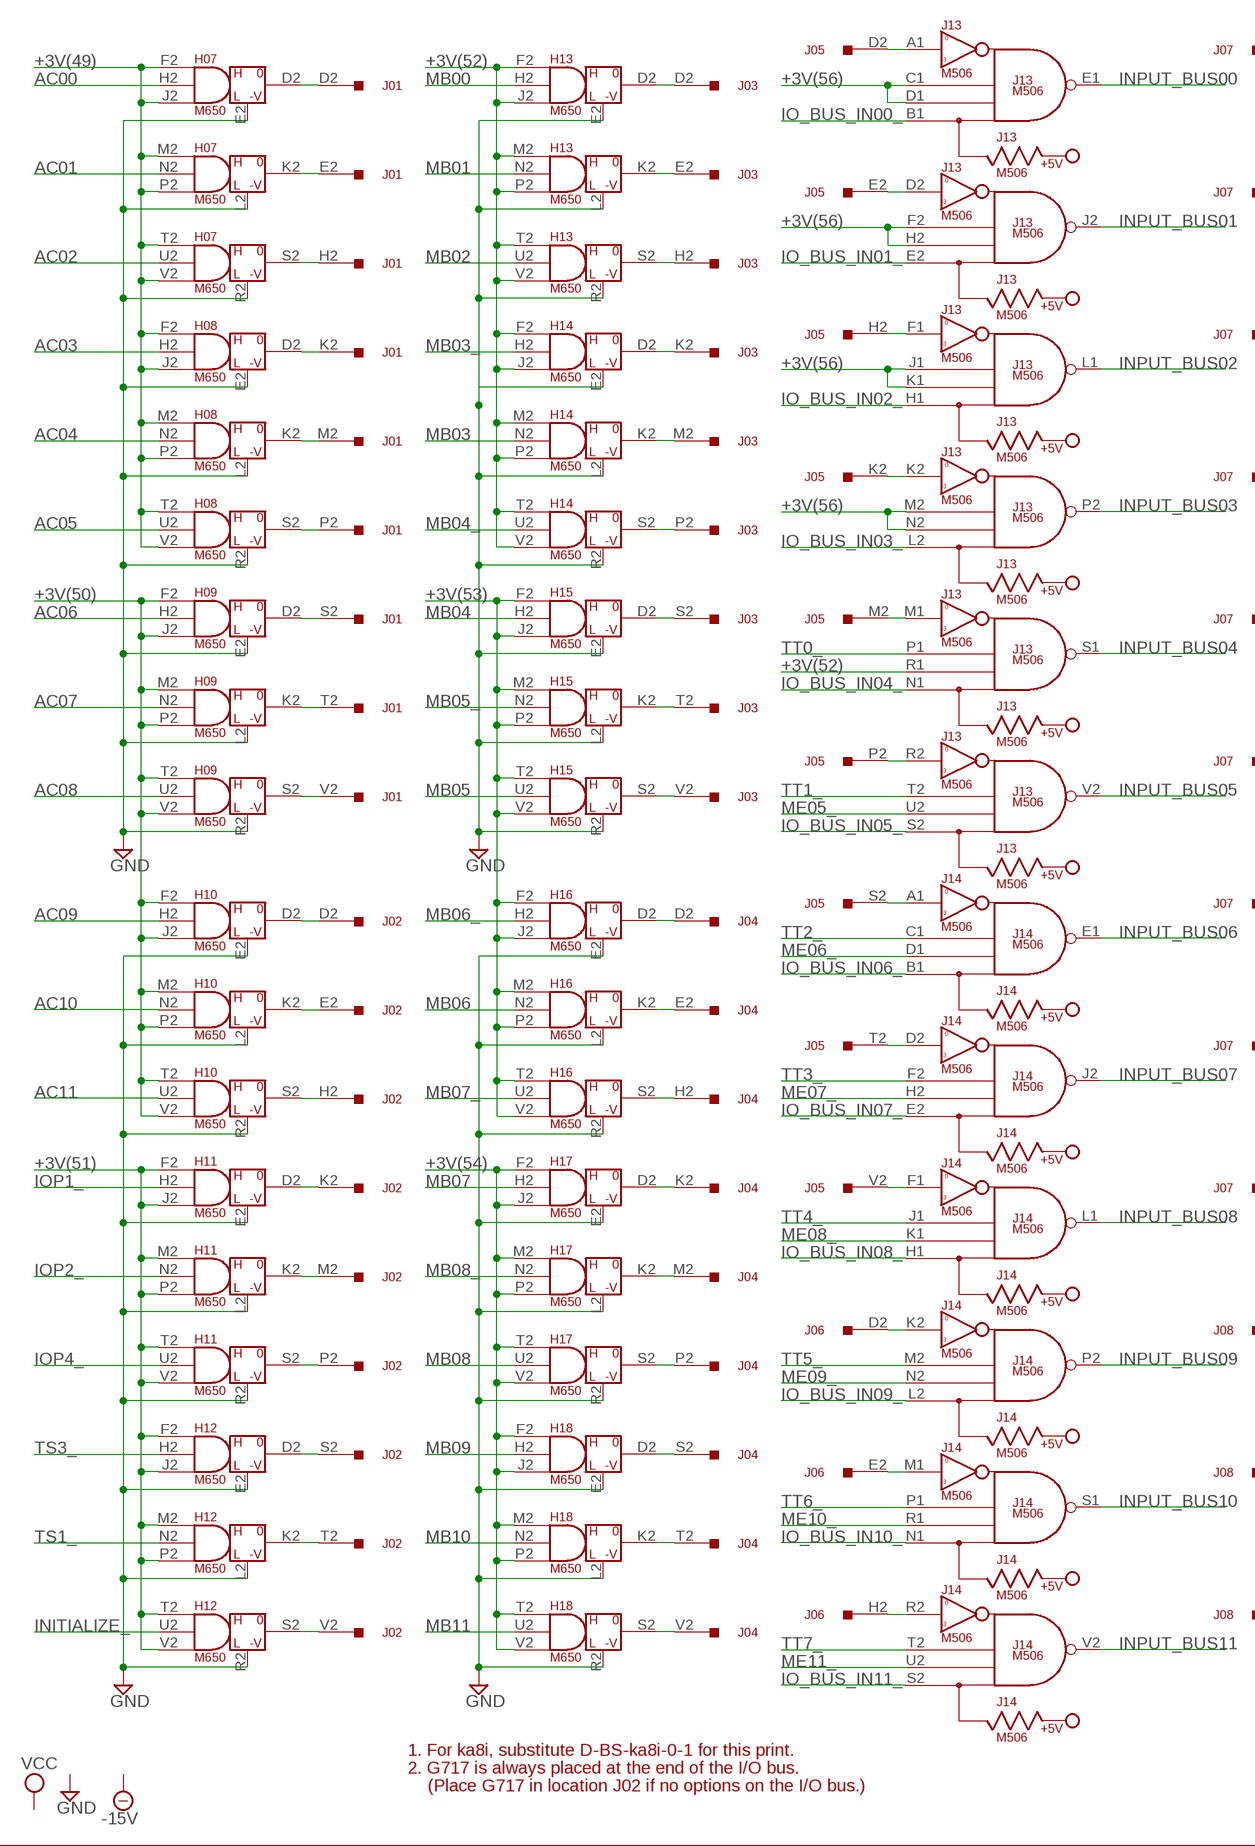
[diagram p13: schematic, sheet 14, part 1 of 2]
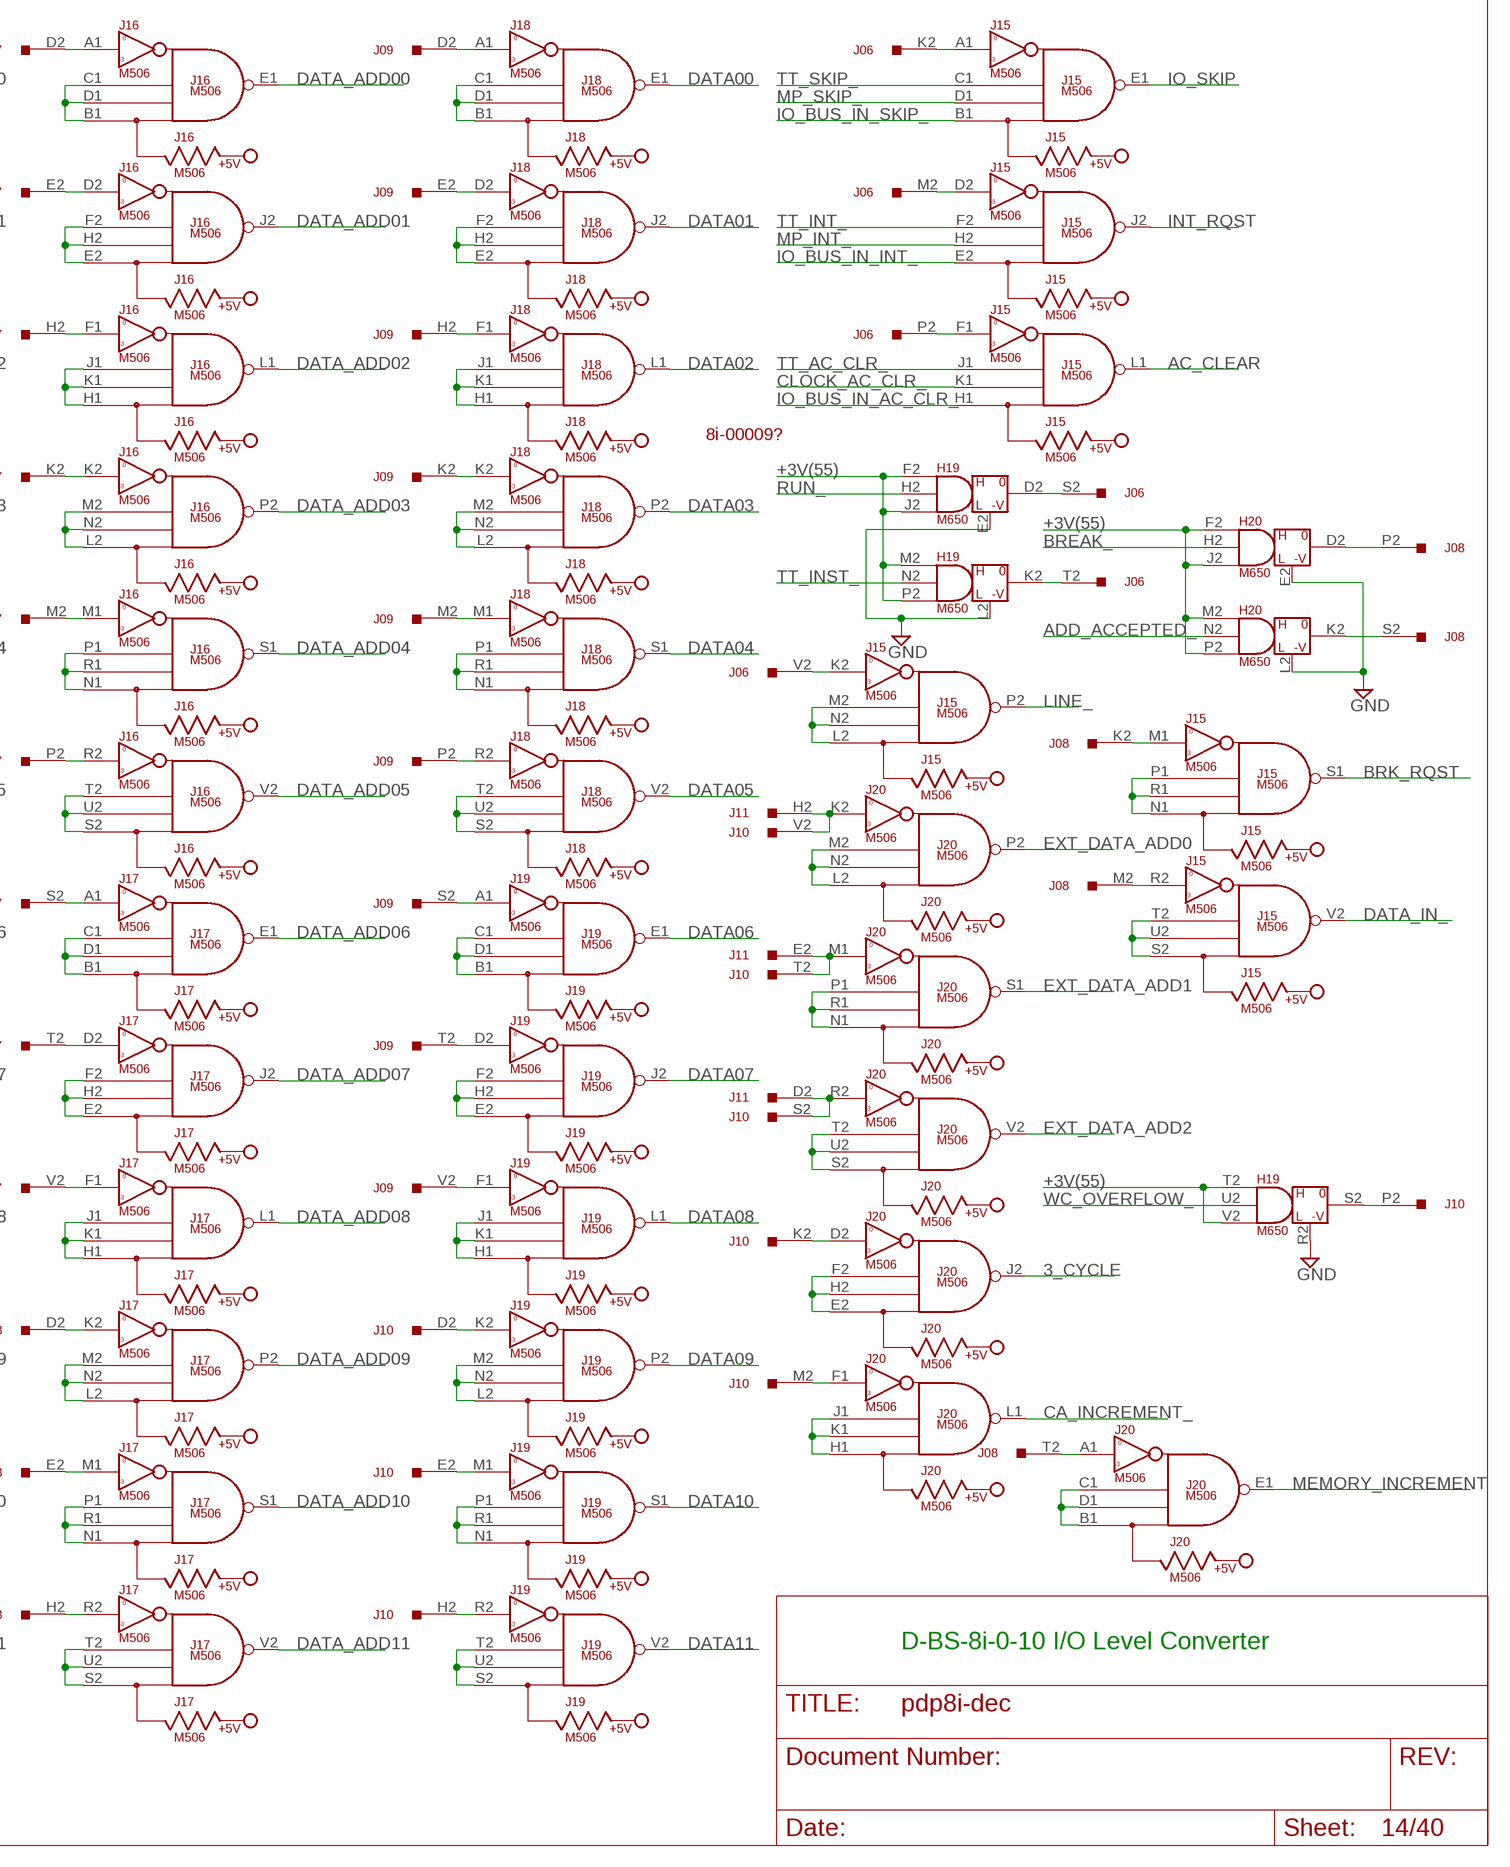
[diagram p14: schematic, sheet 14, part 2 of 2]
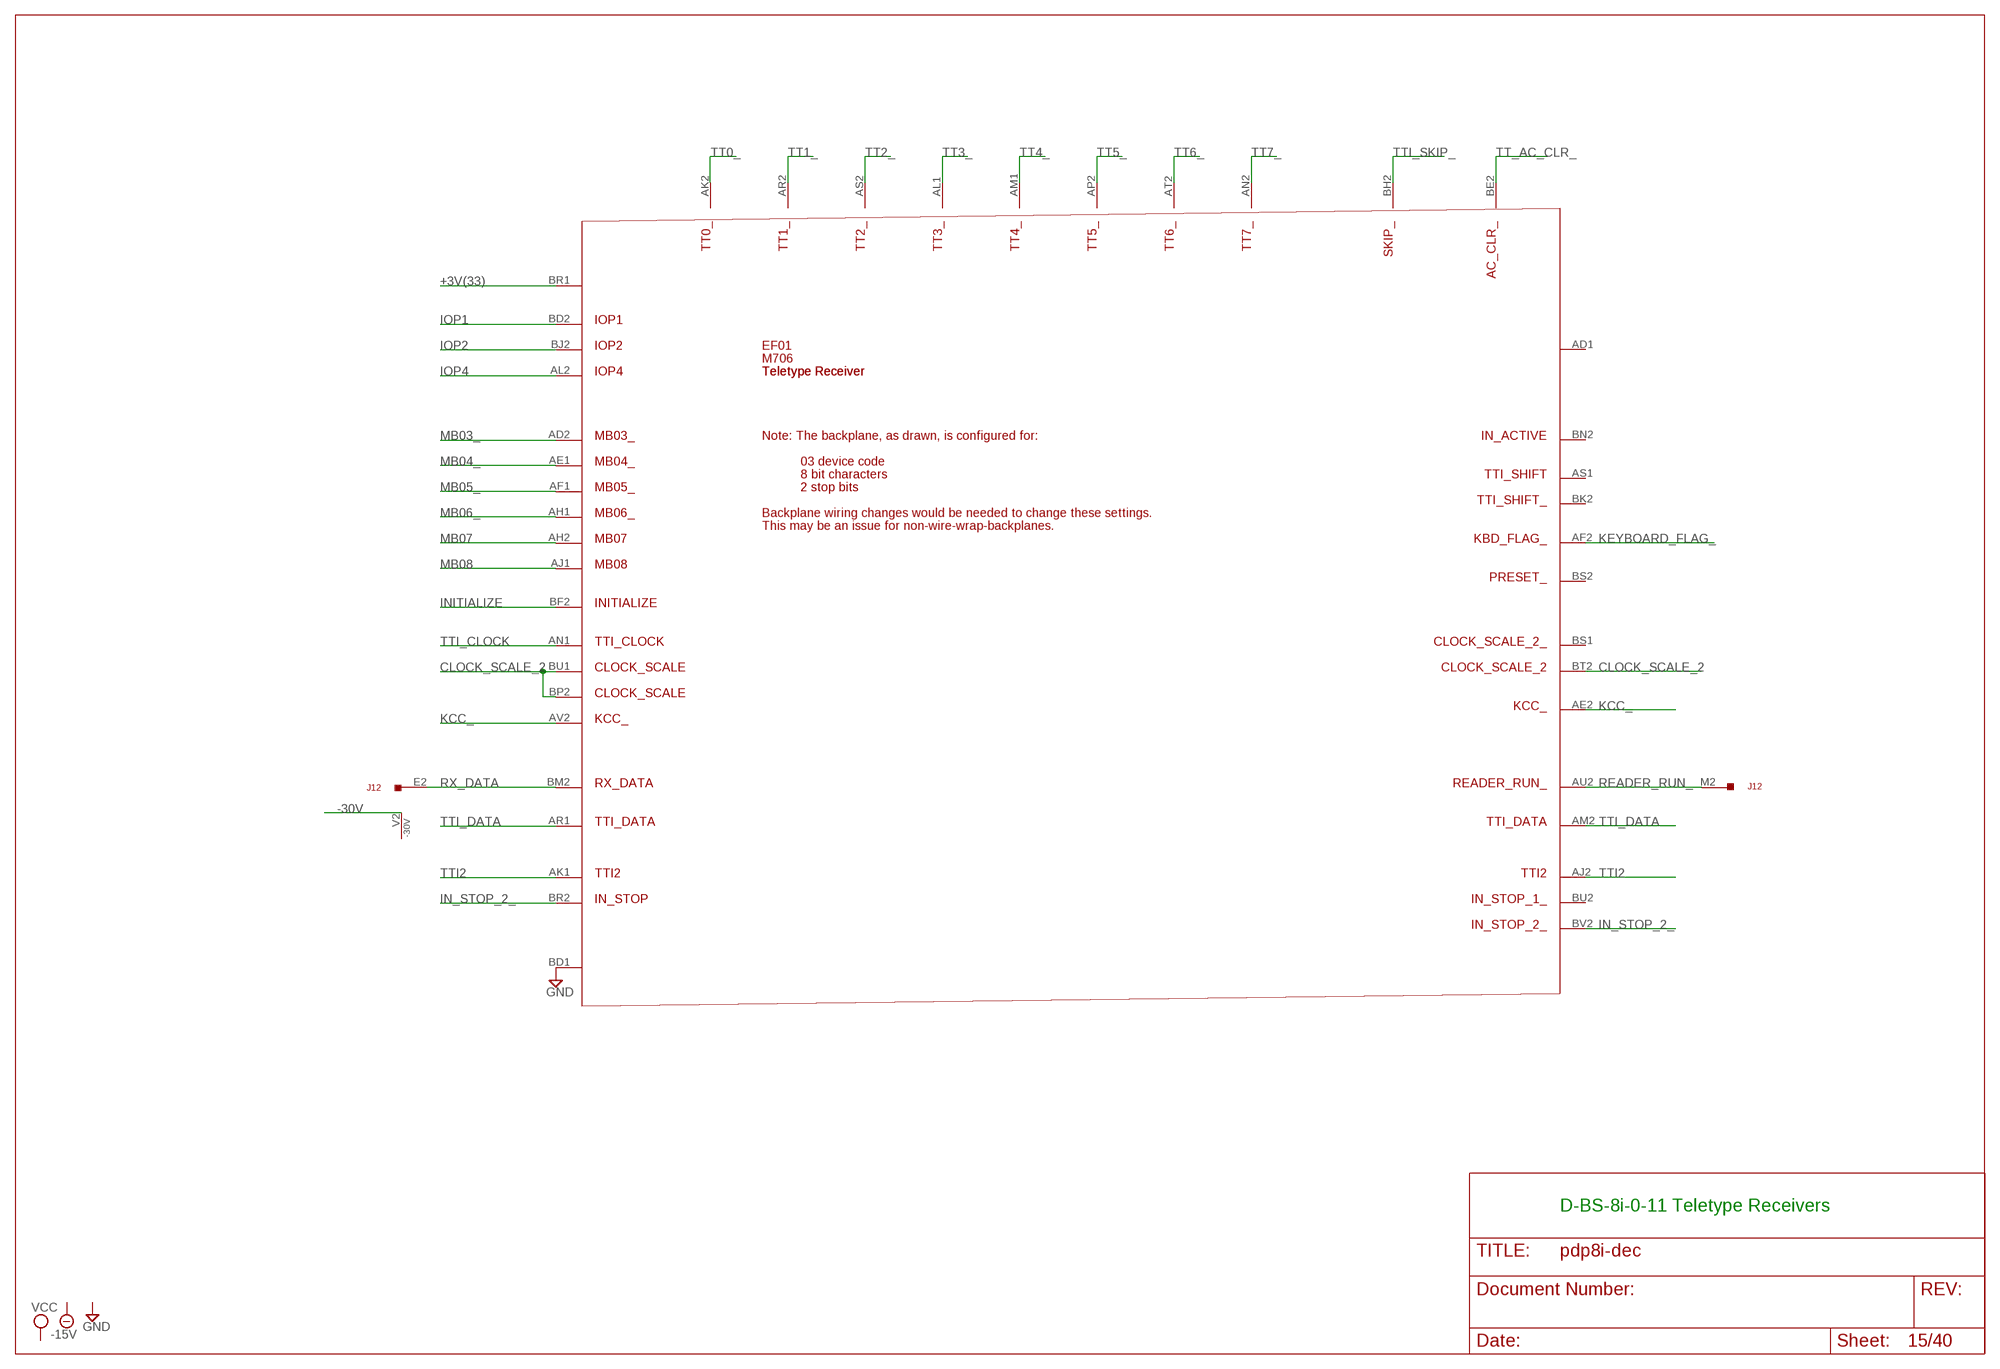
[diagram p15: schematic, sheet 15]
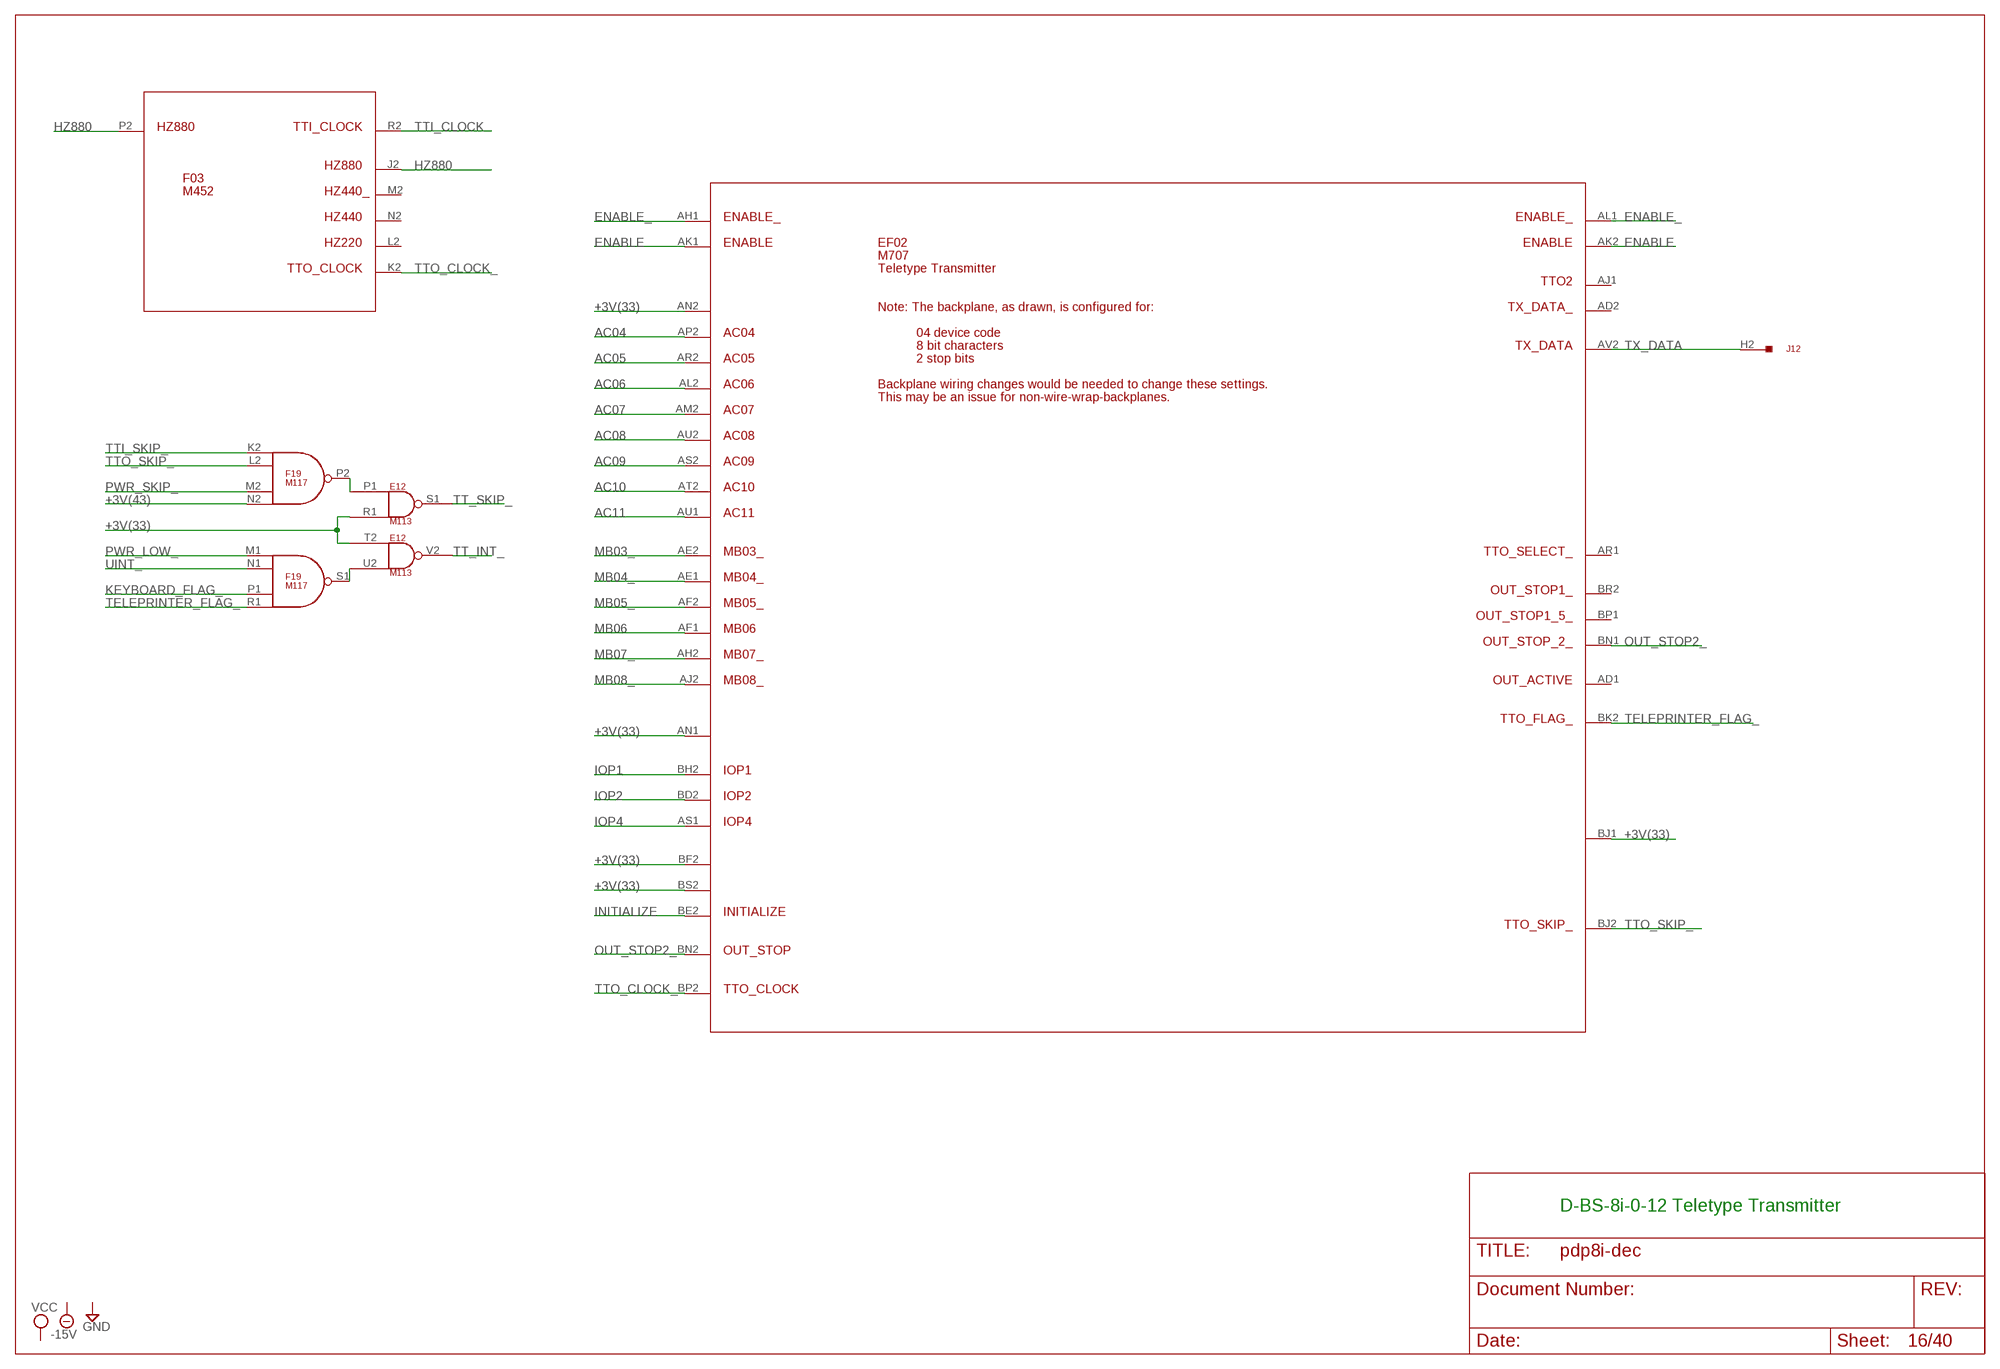
[diagram p16: schematic, sheet 16]
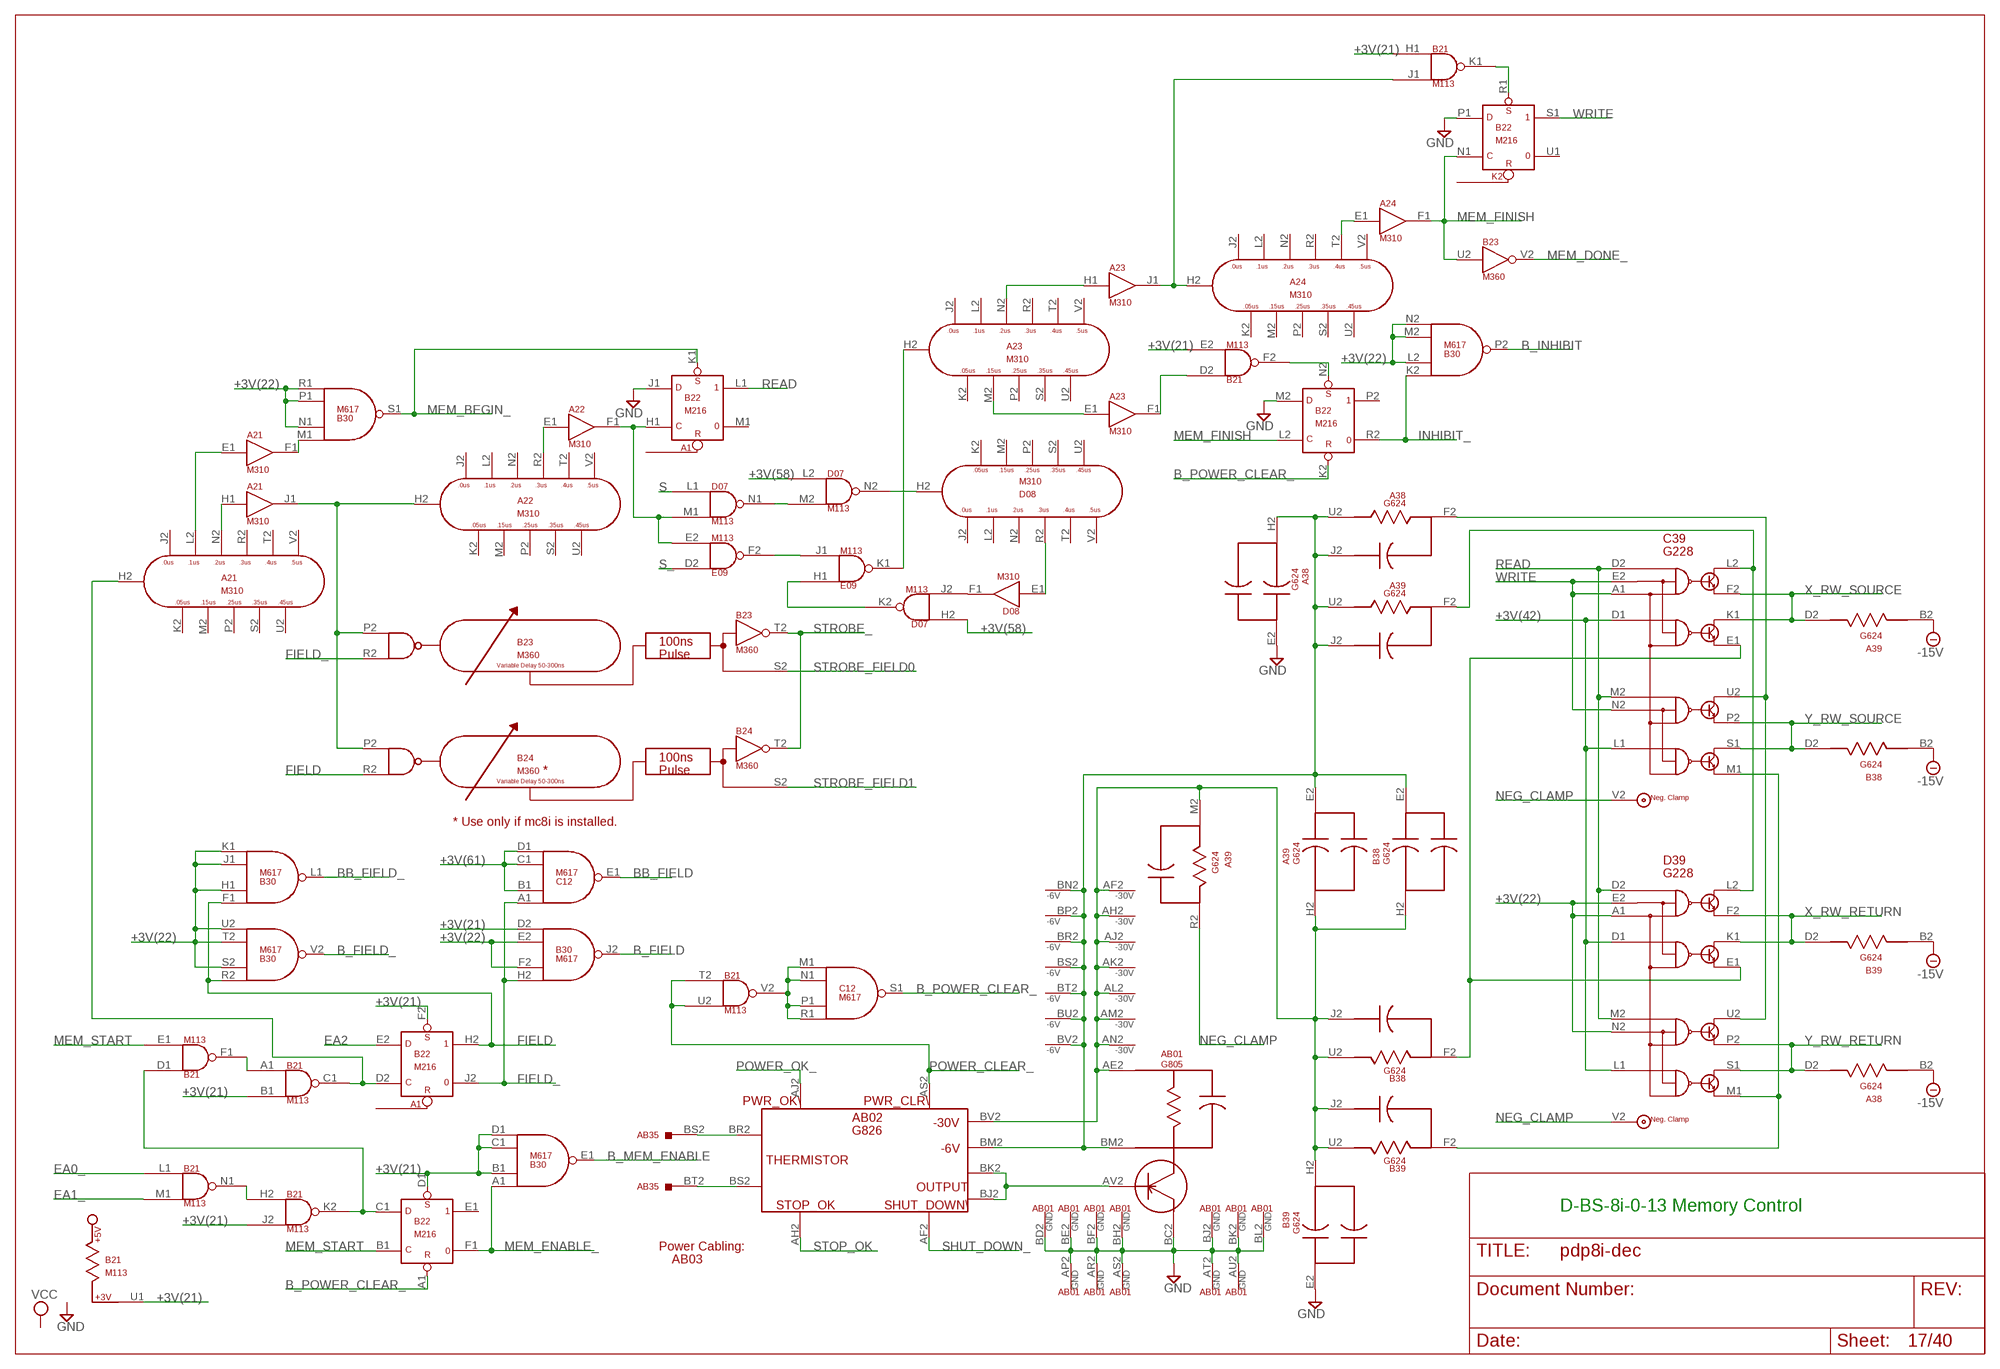
[diagram p17: schematic, sheet 17]
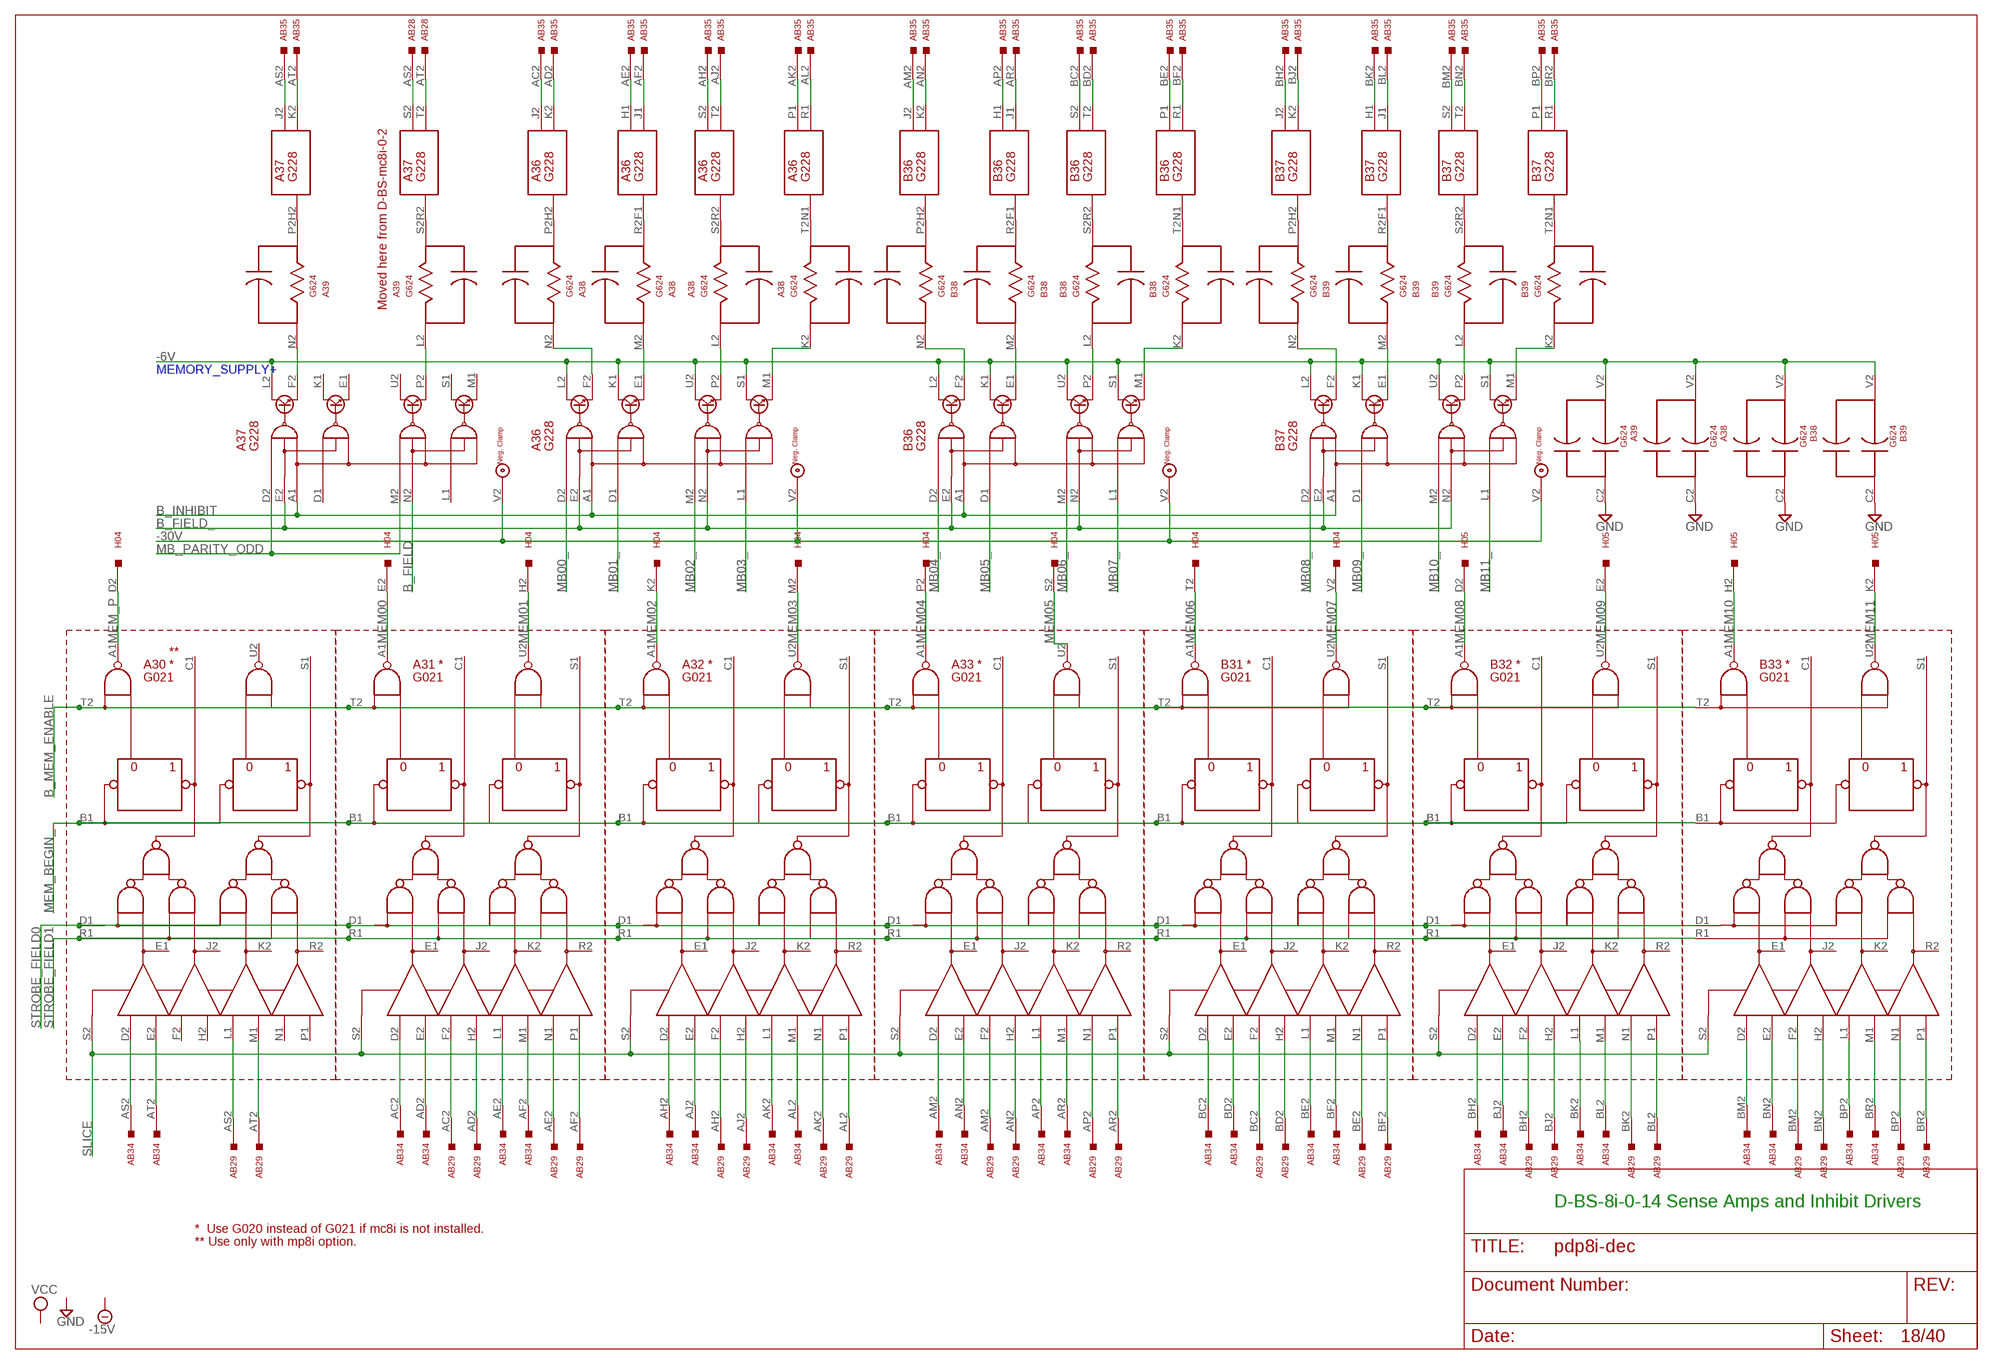
[diagram p18: schematic, sheet 18]
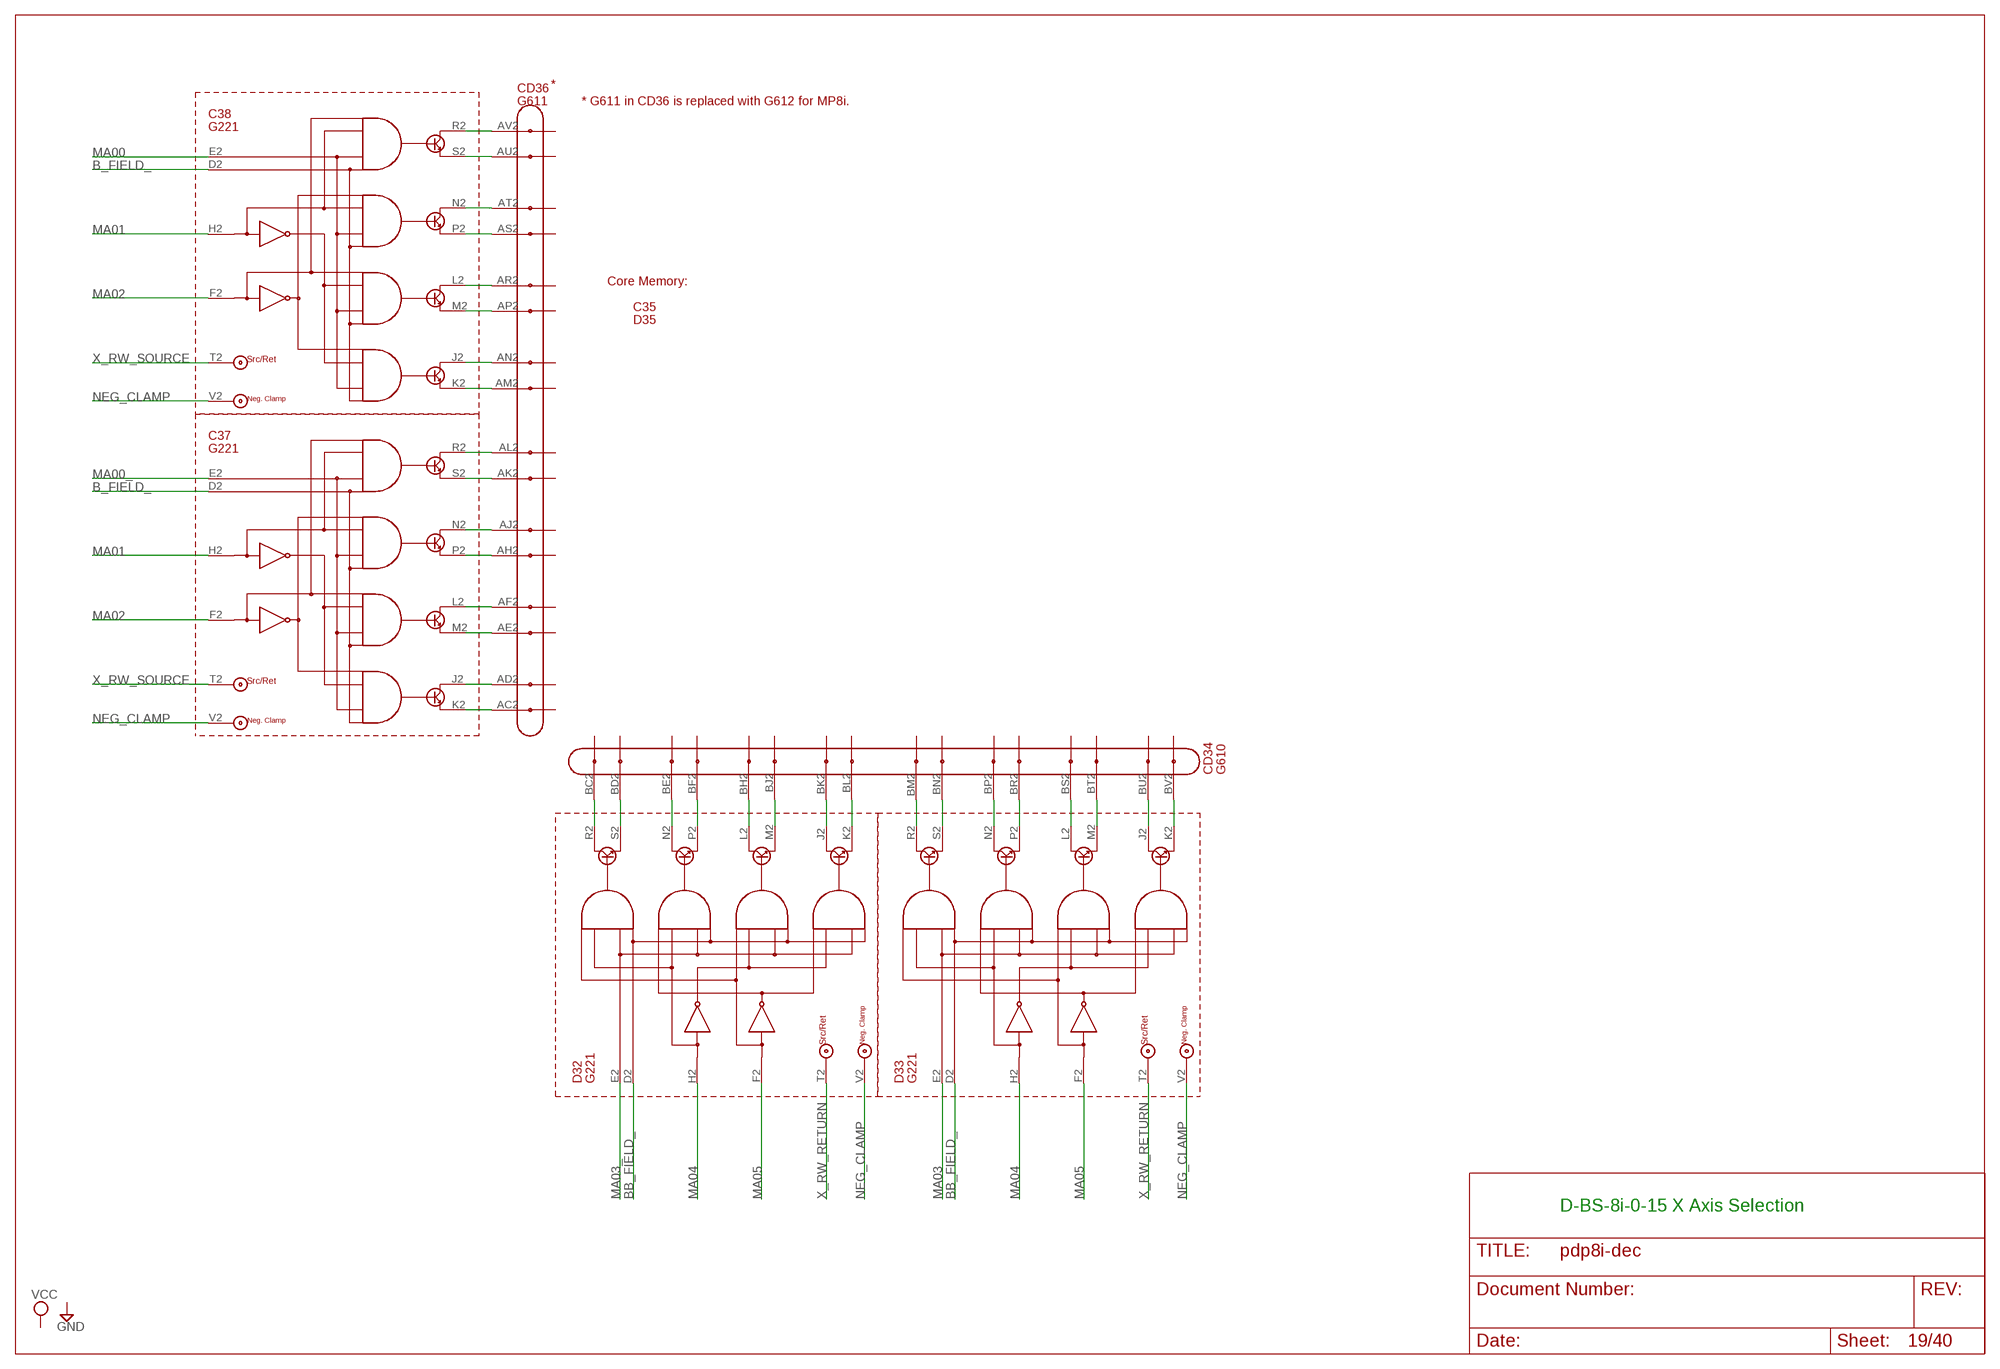
[diagram p19: schematic, sheet 19]
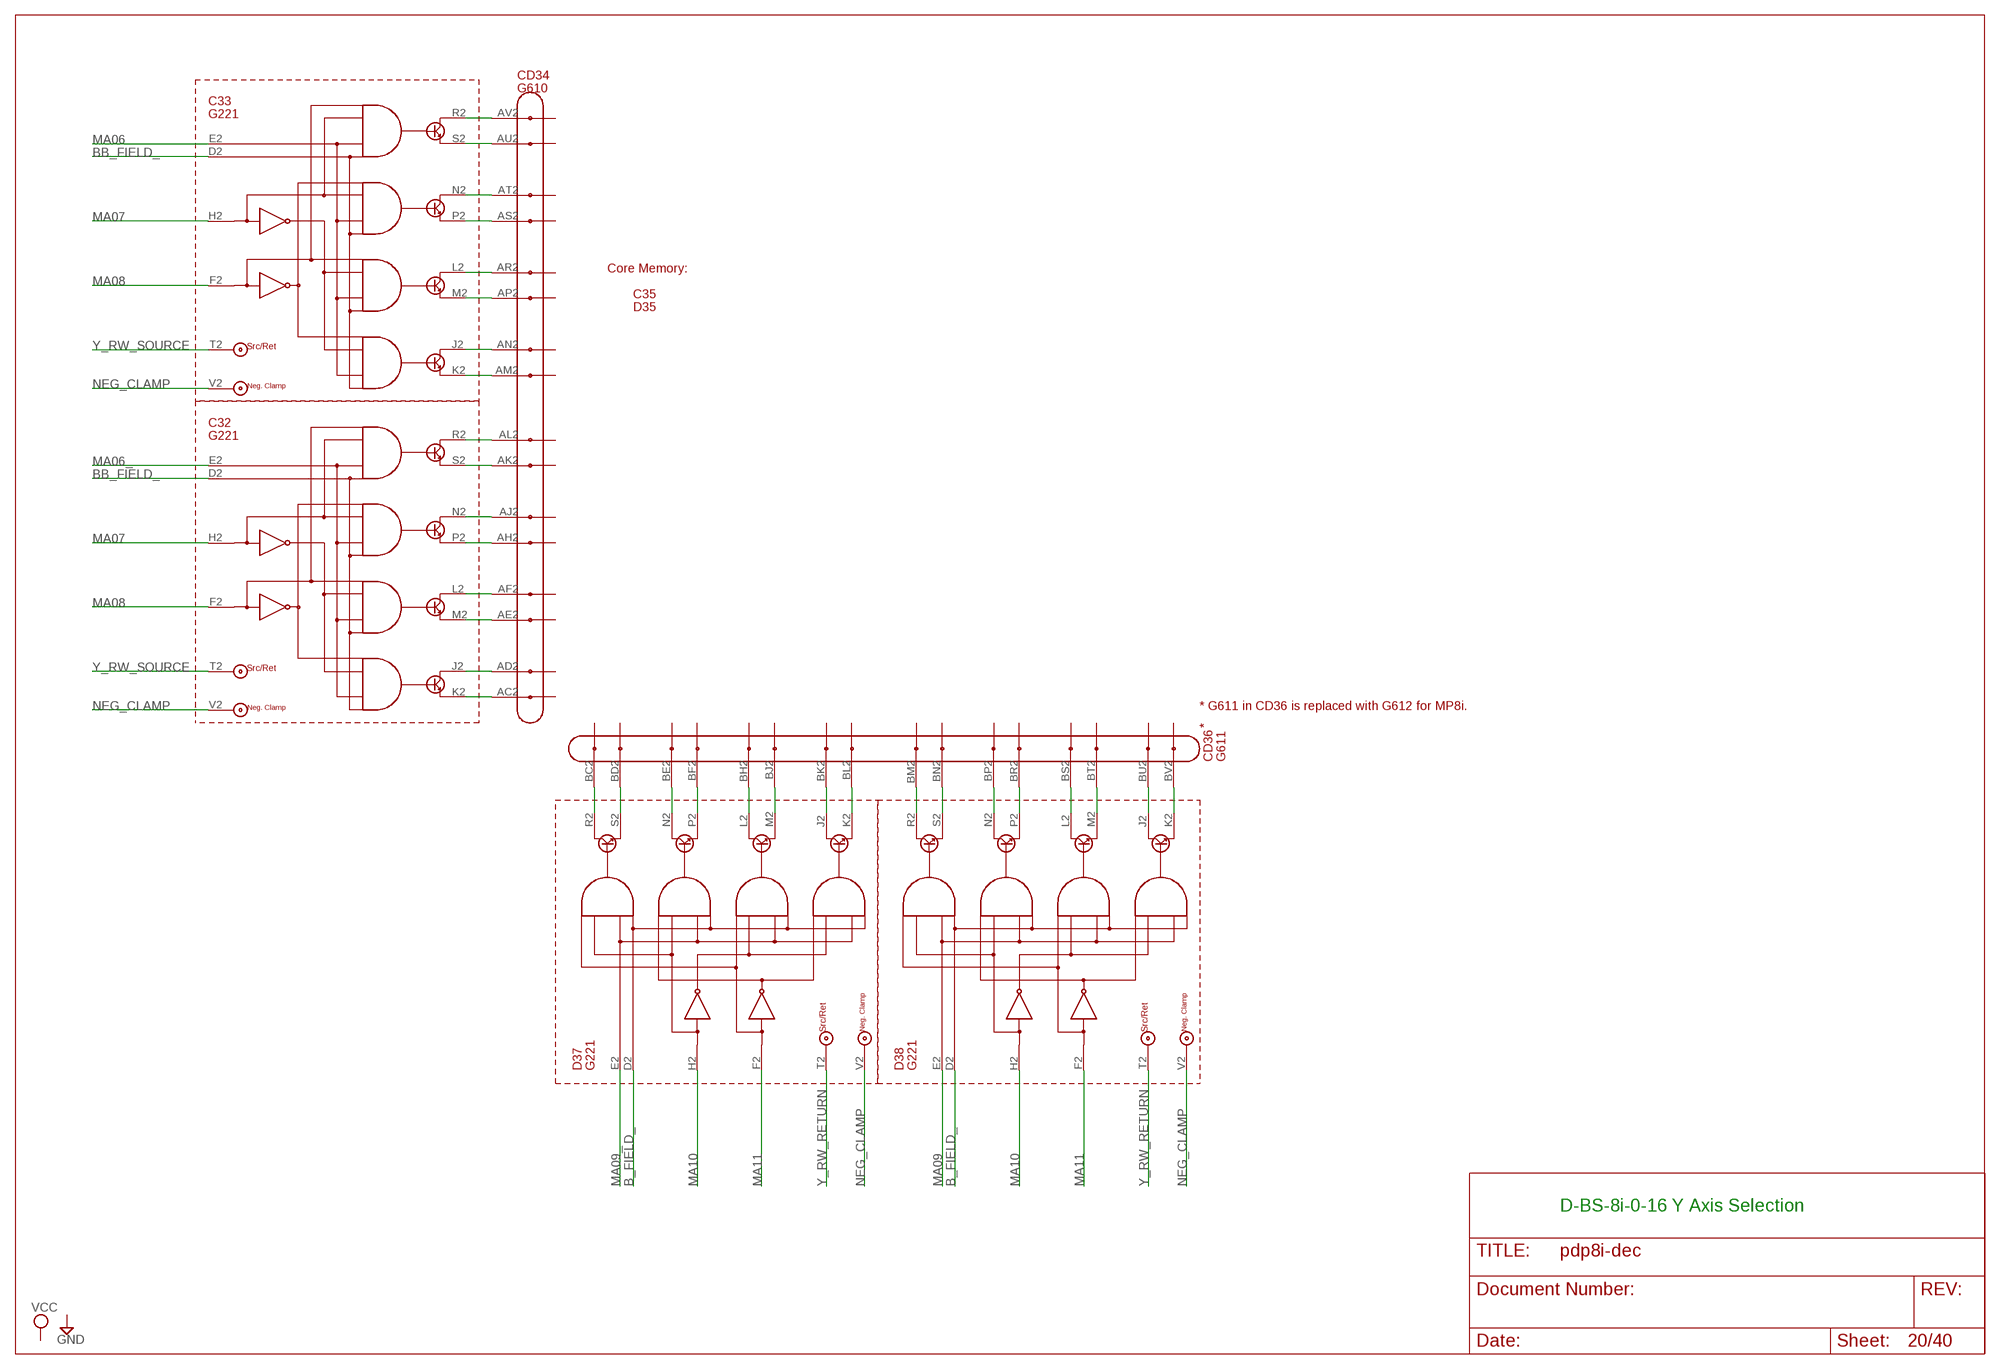
[diagram p20: schematic, sheet 20]
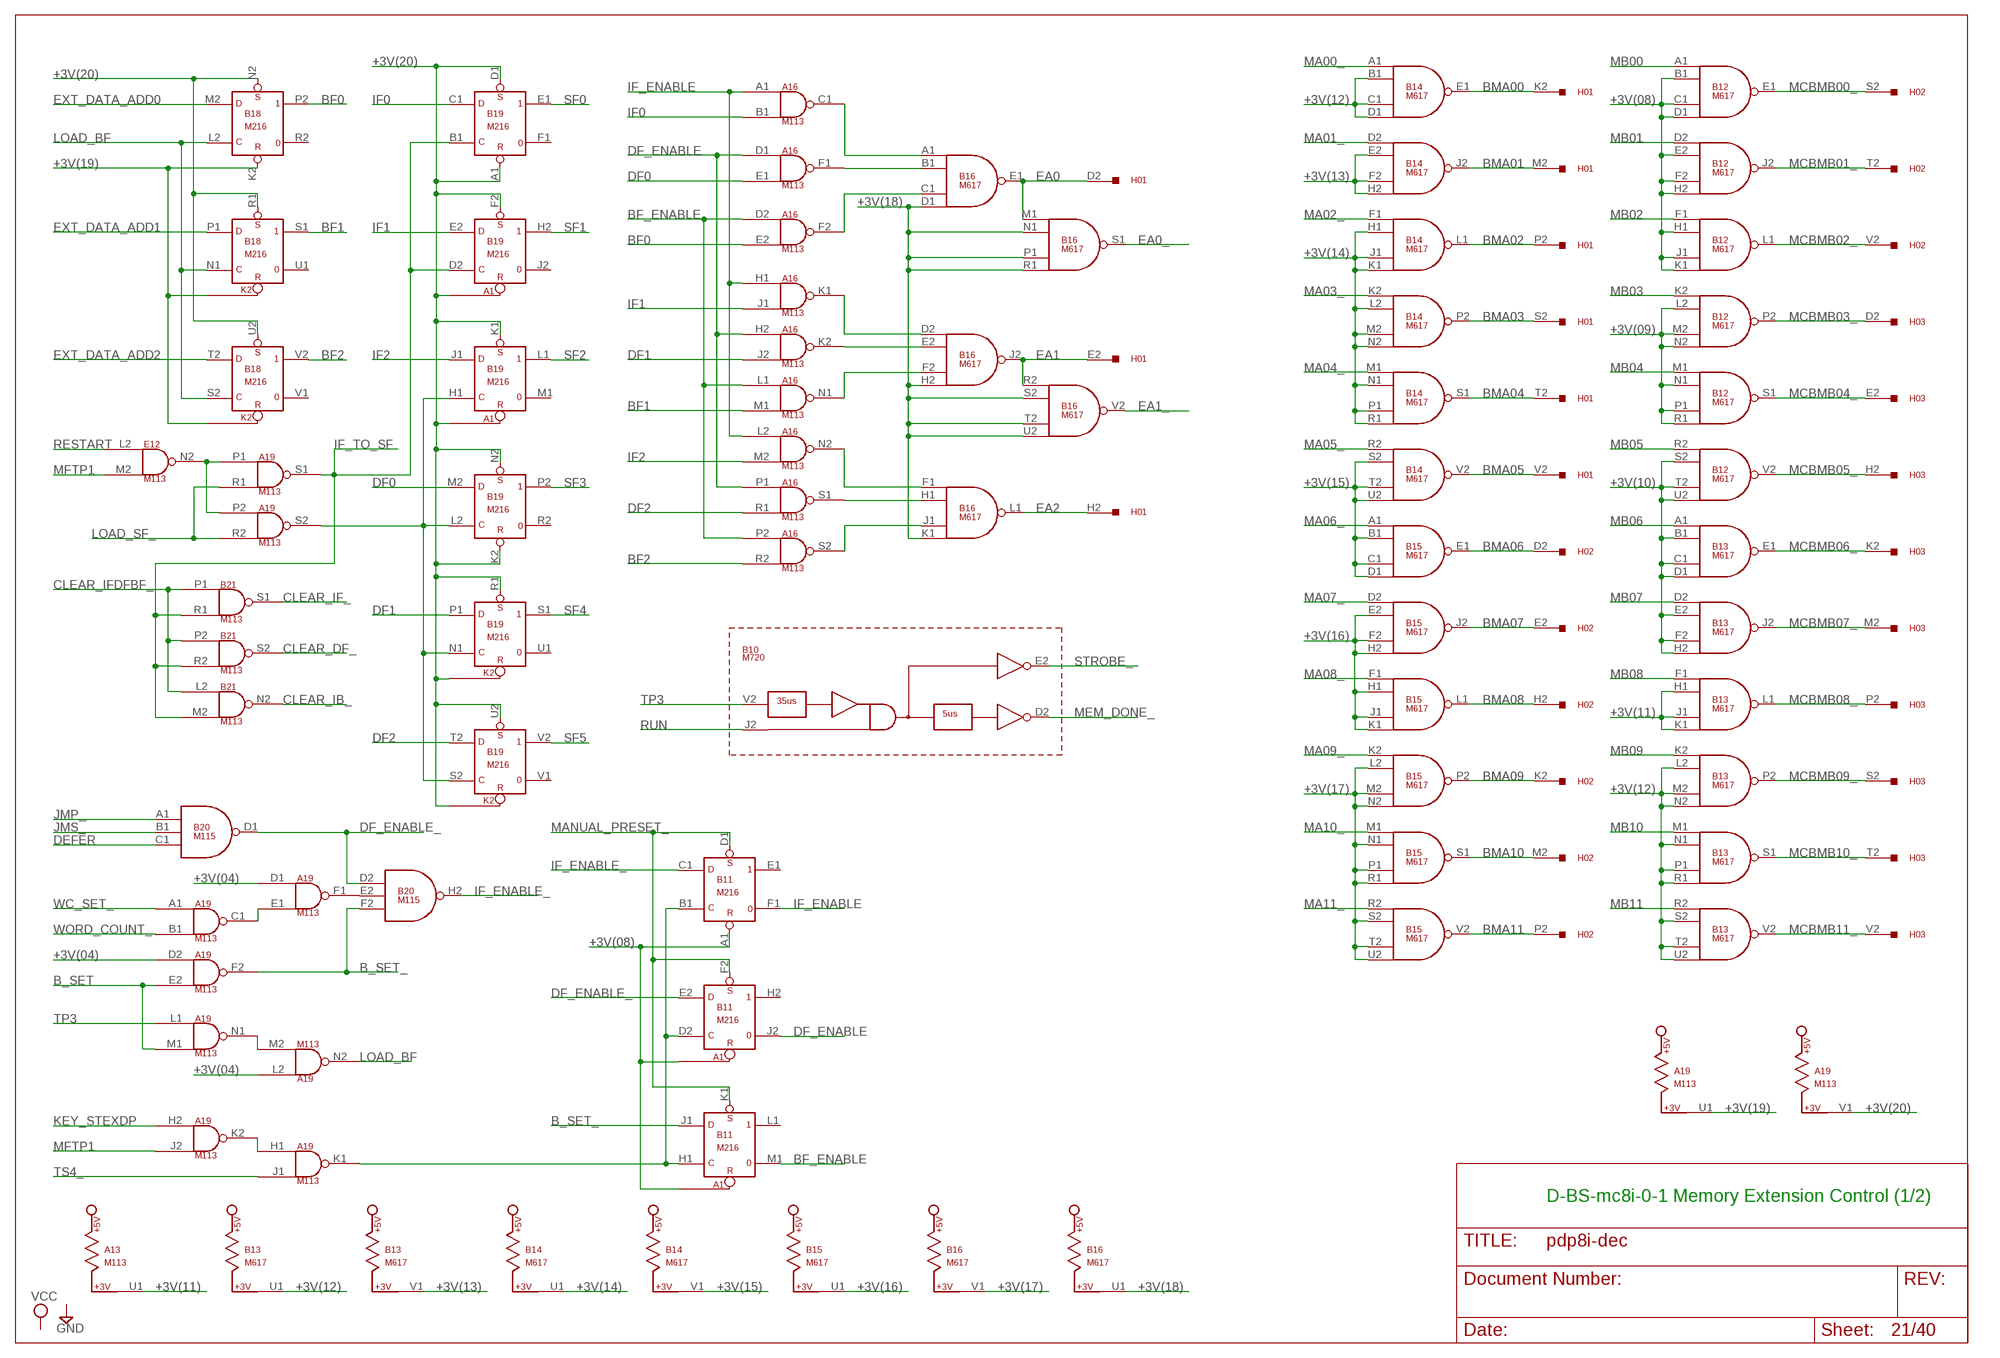
[diagram p21: schematic, sheet 21]
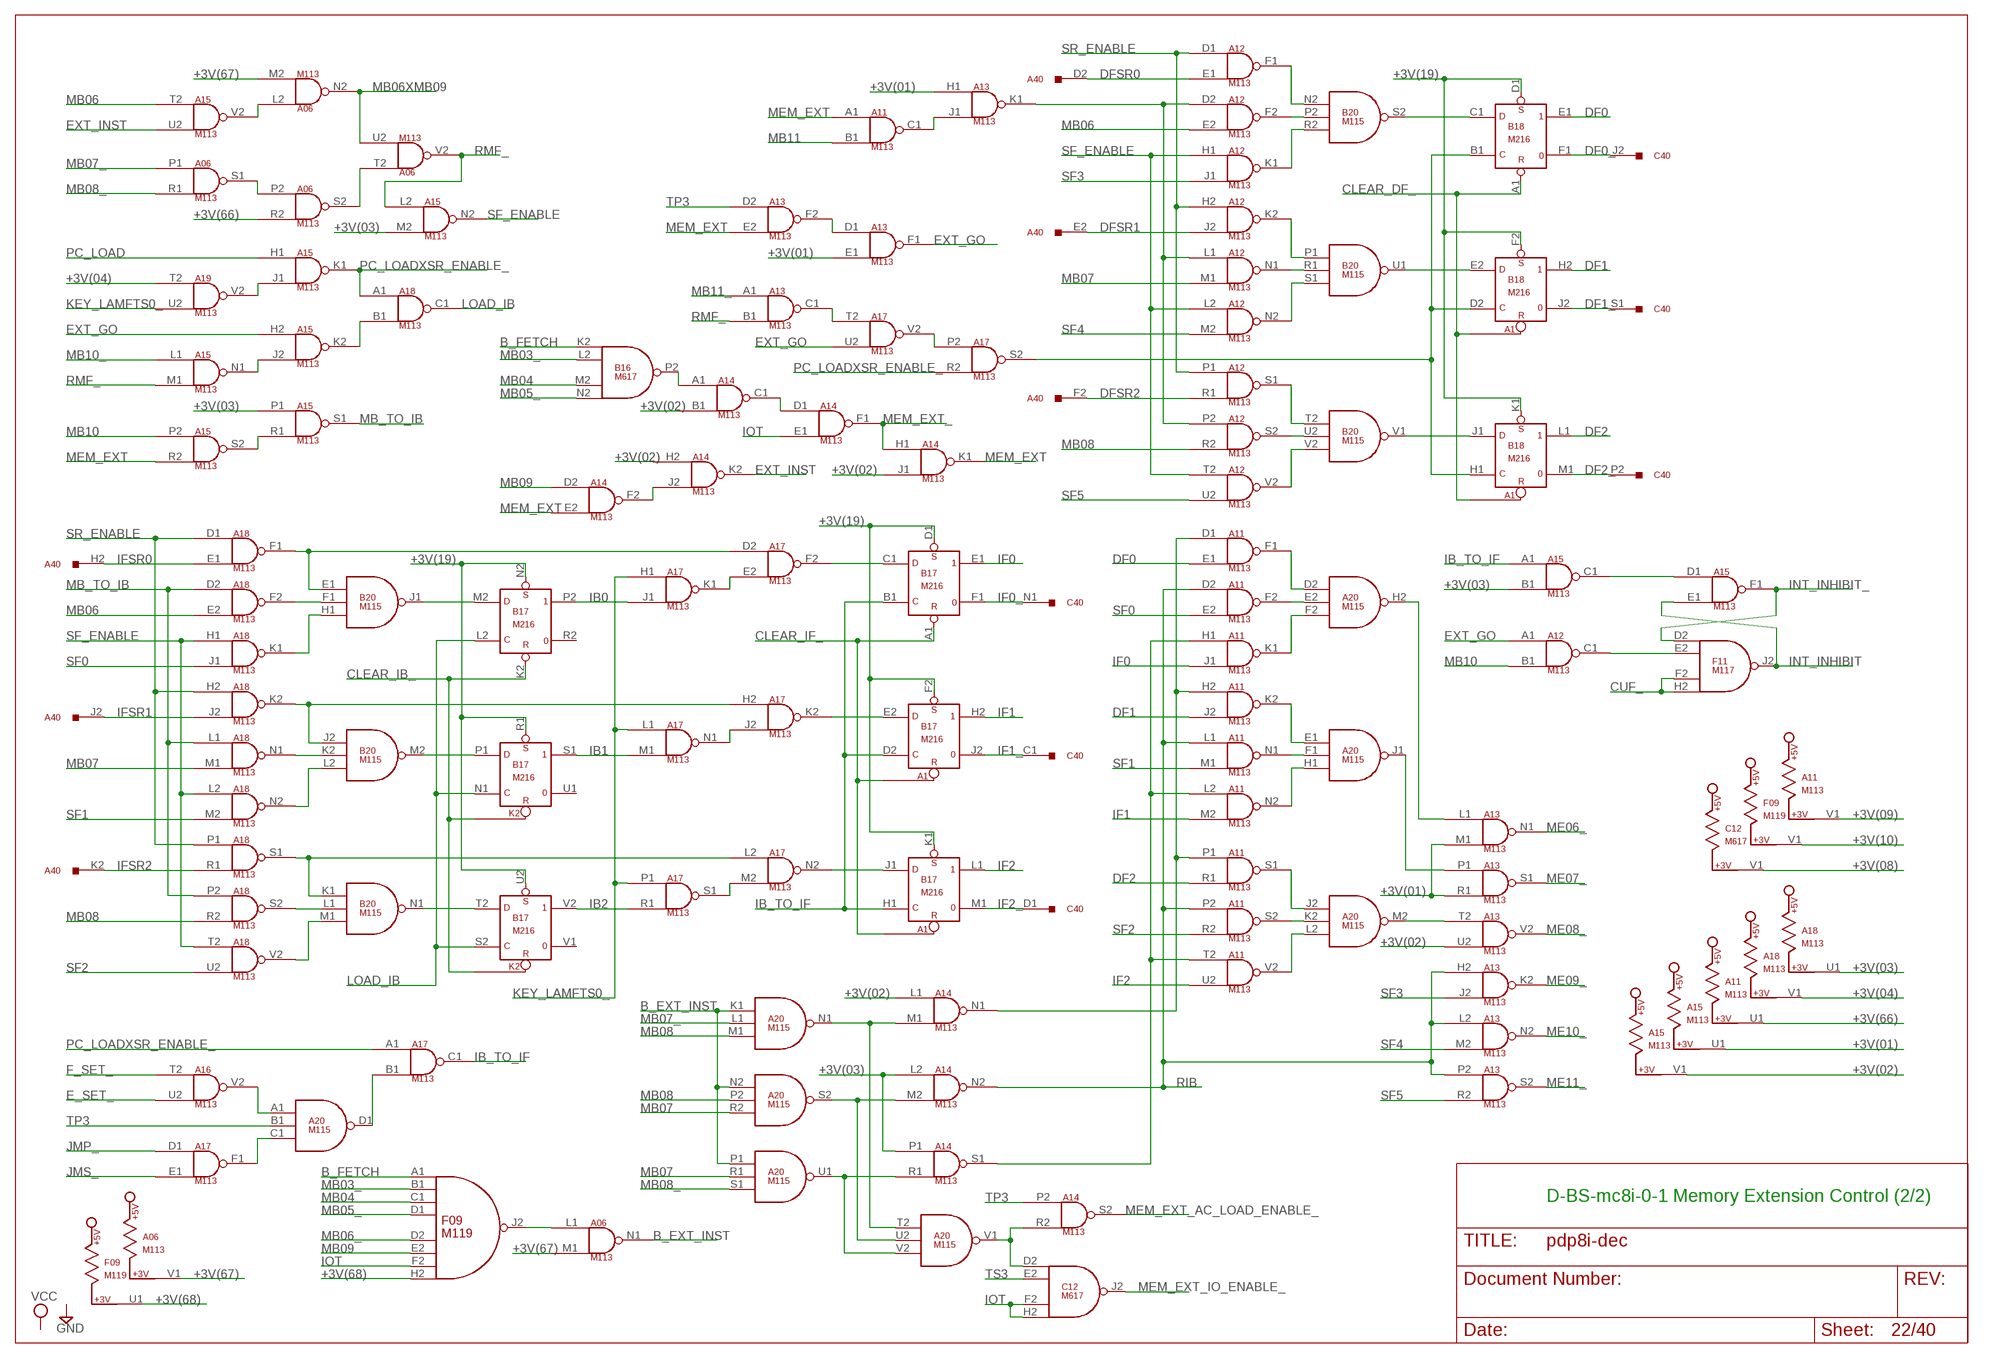
[diagram p22: schematic, sheet 22]
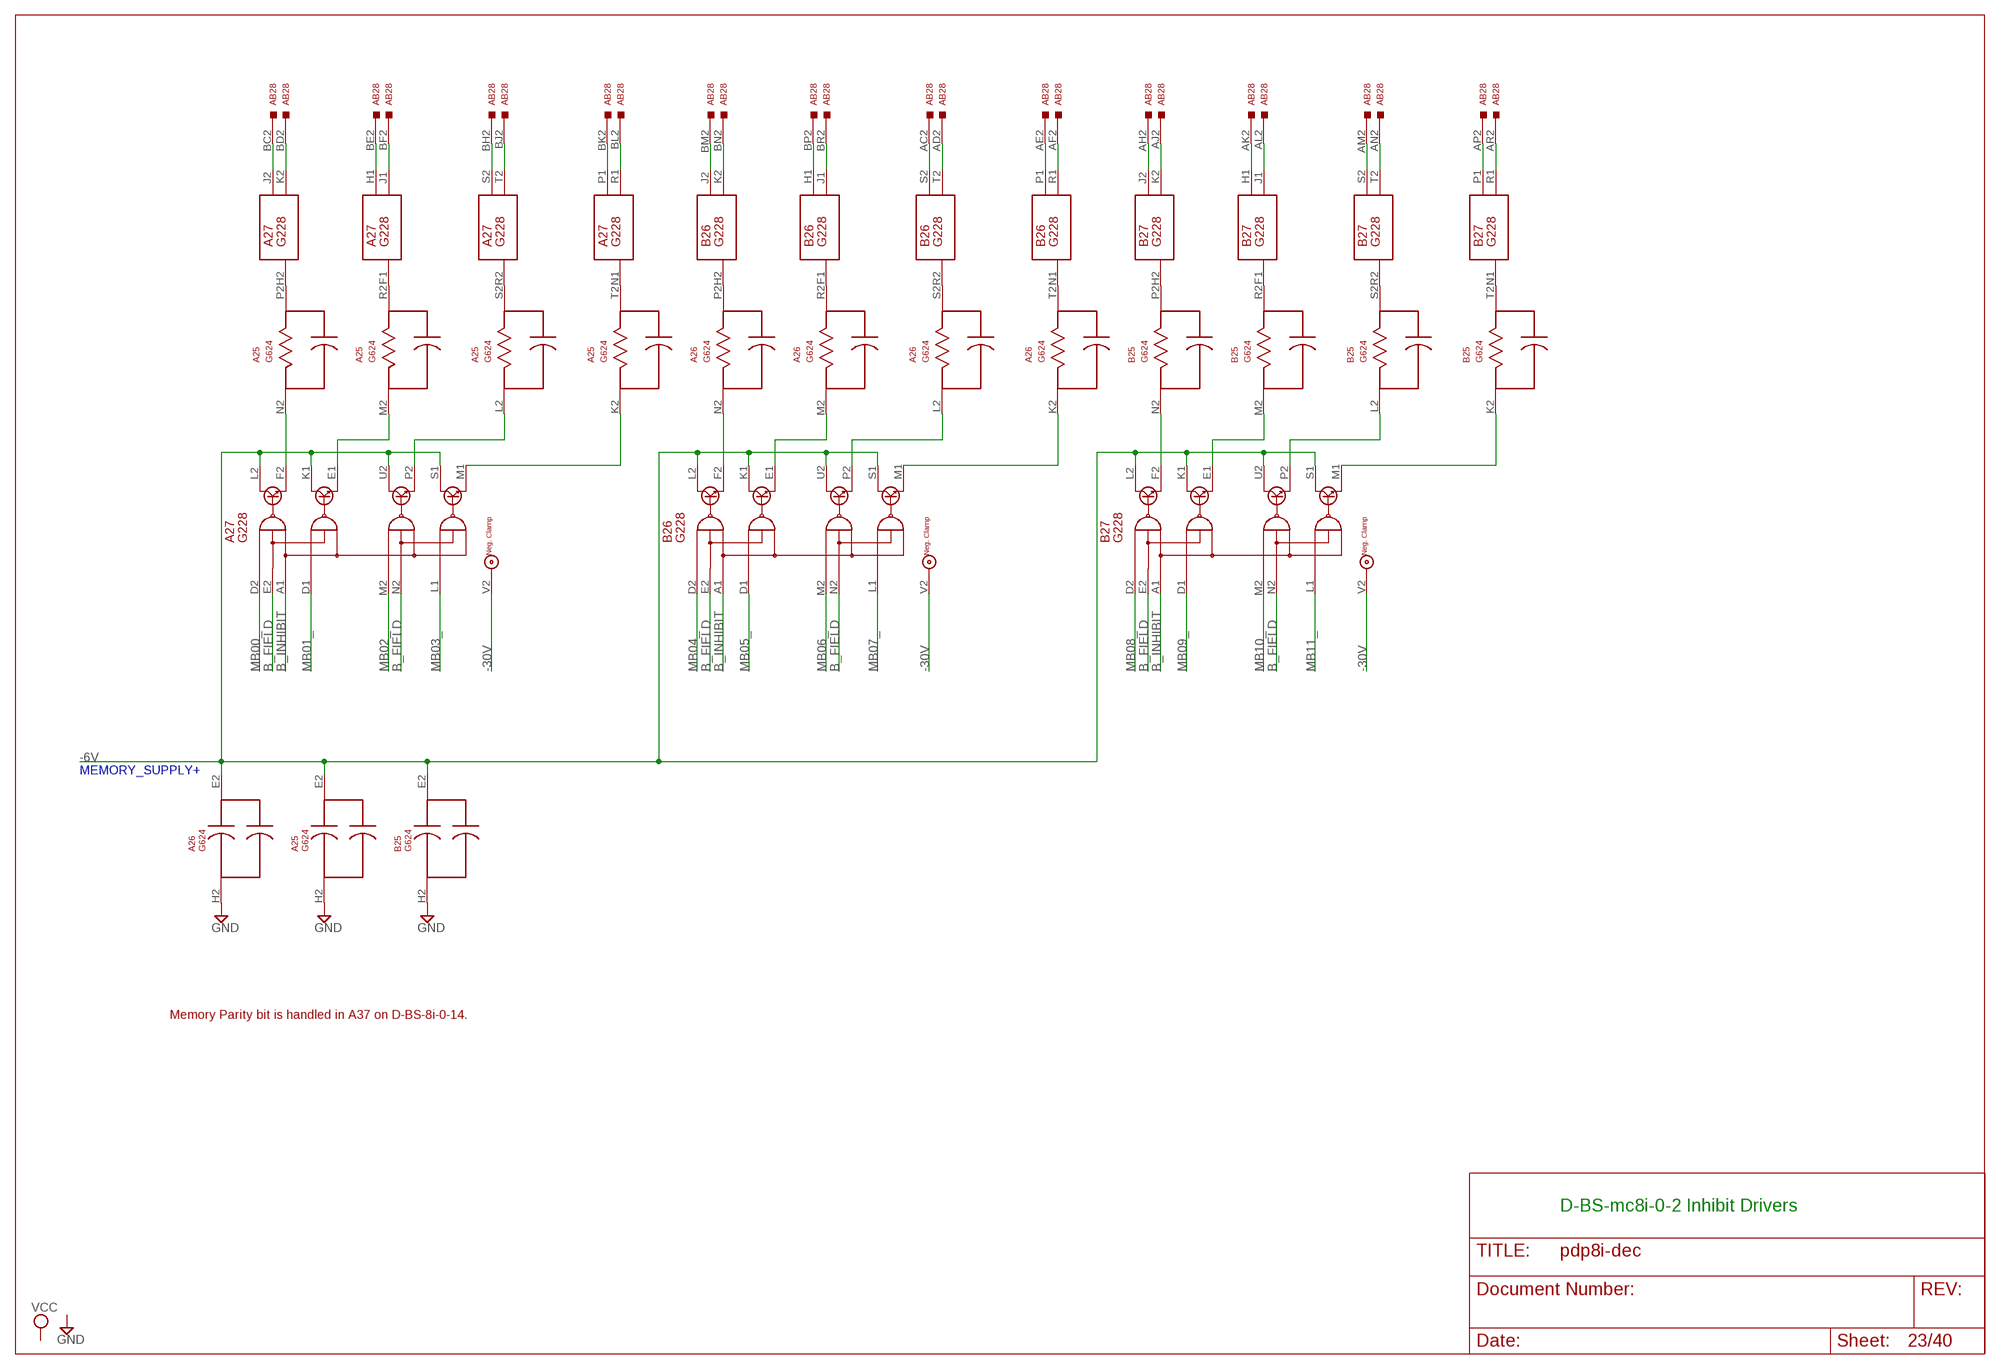
[diagram p23: schematic, sheet 23]
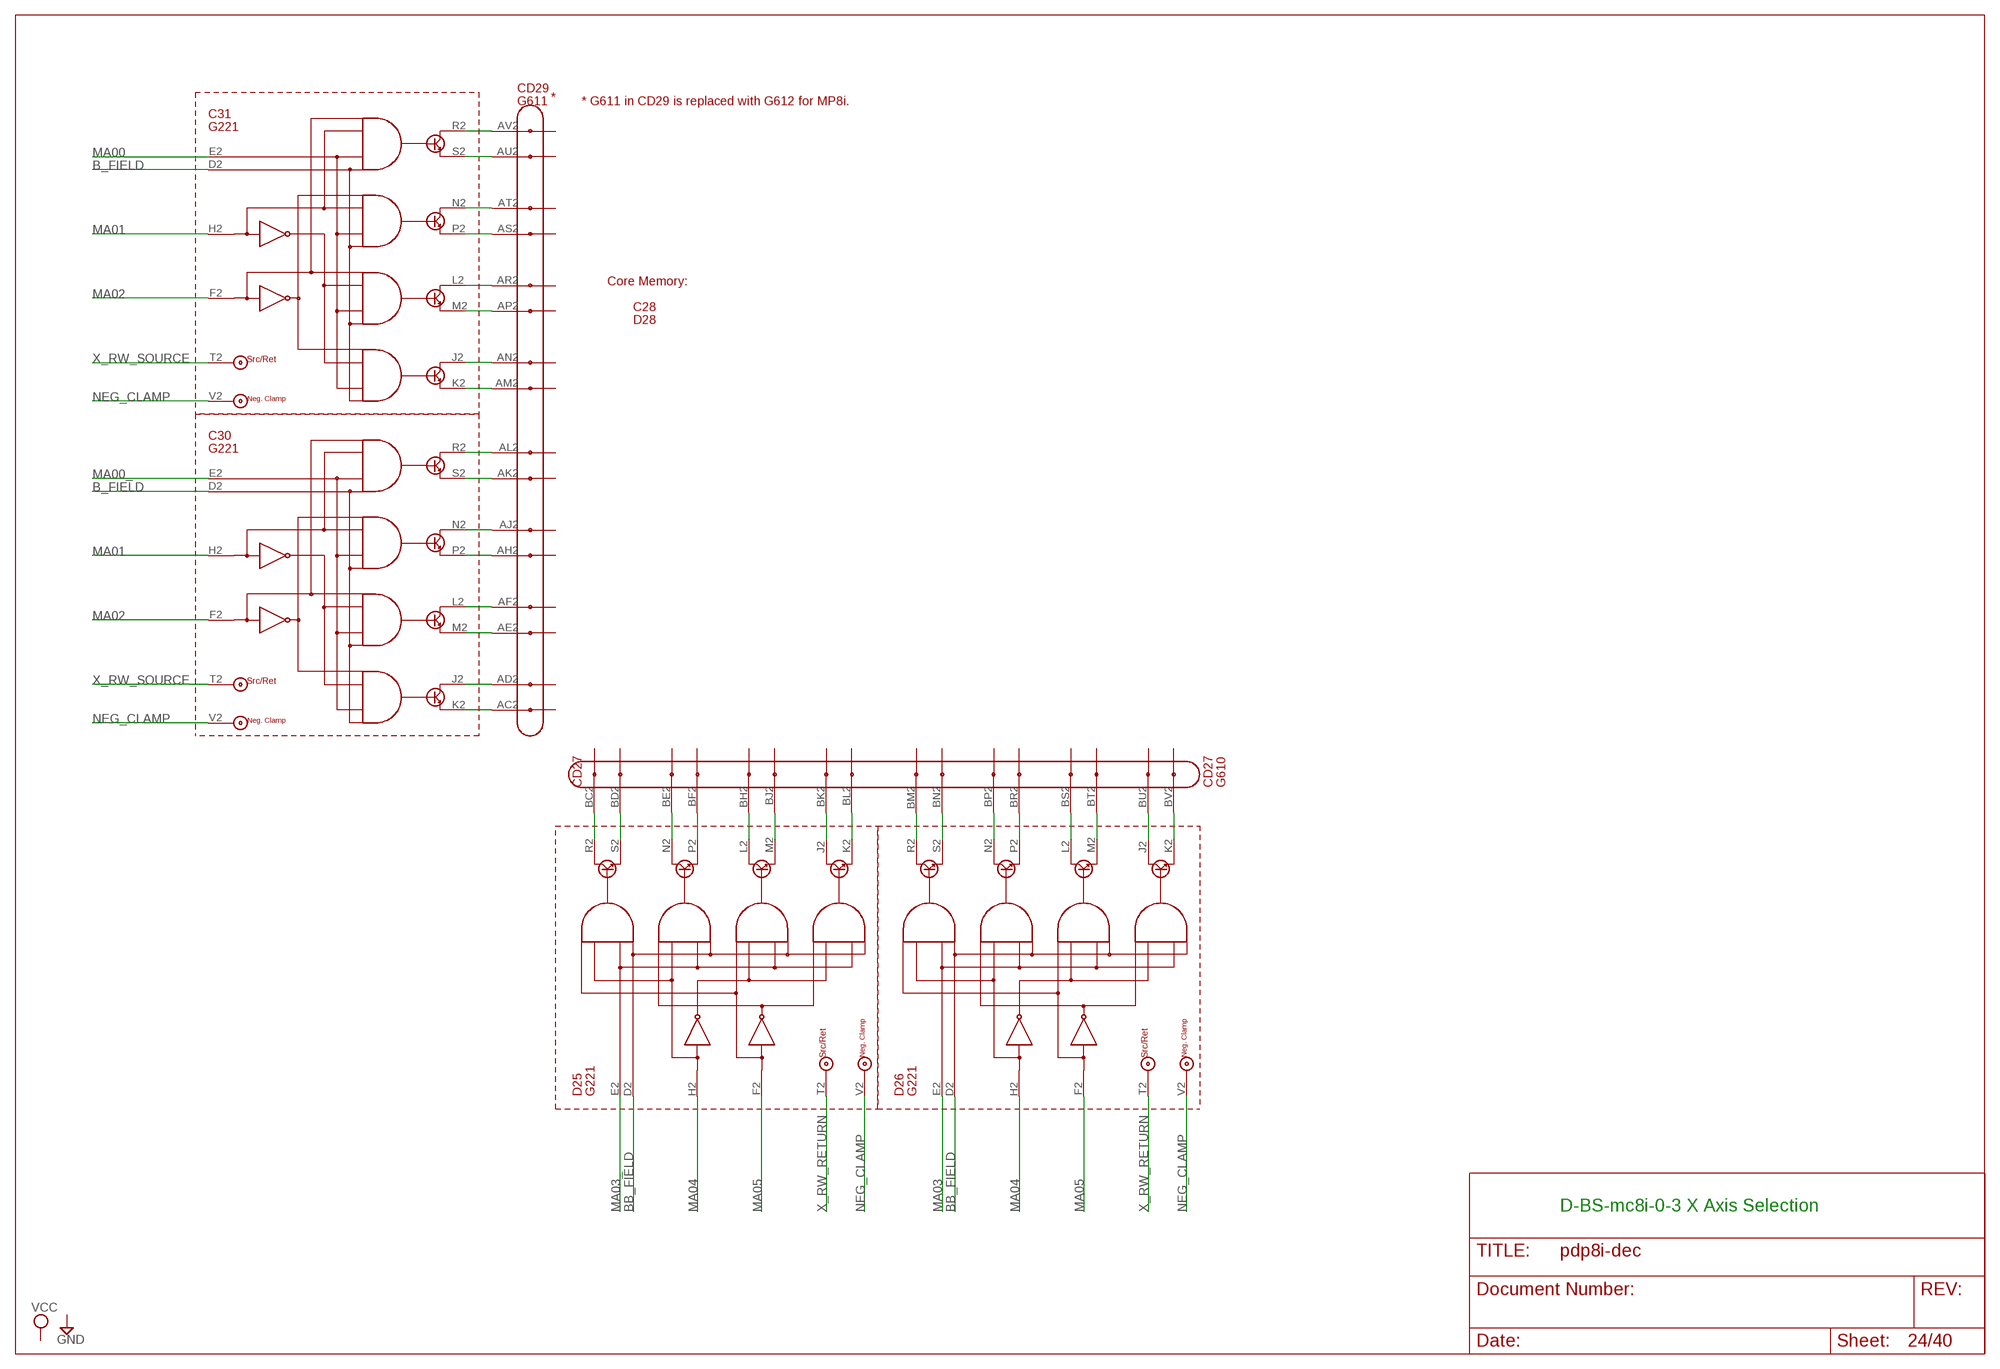
[diagram p24: schematic, sheet 24]
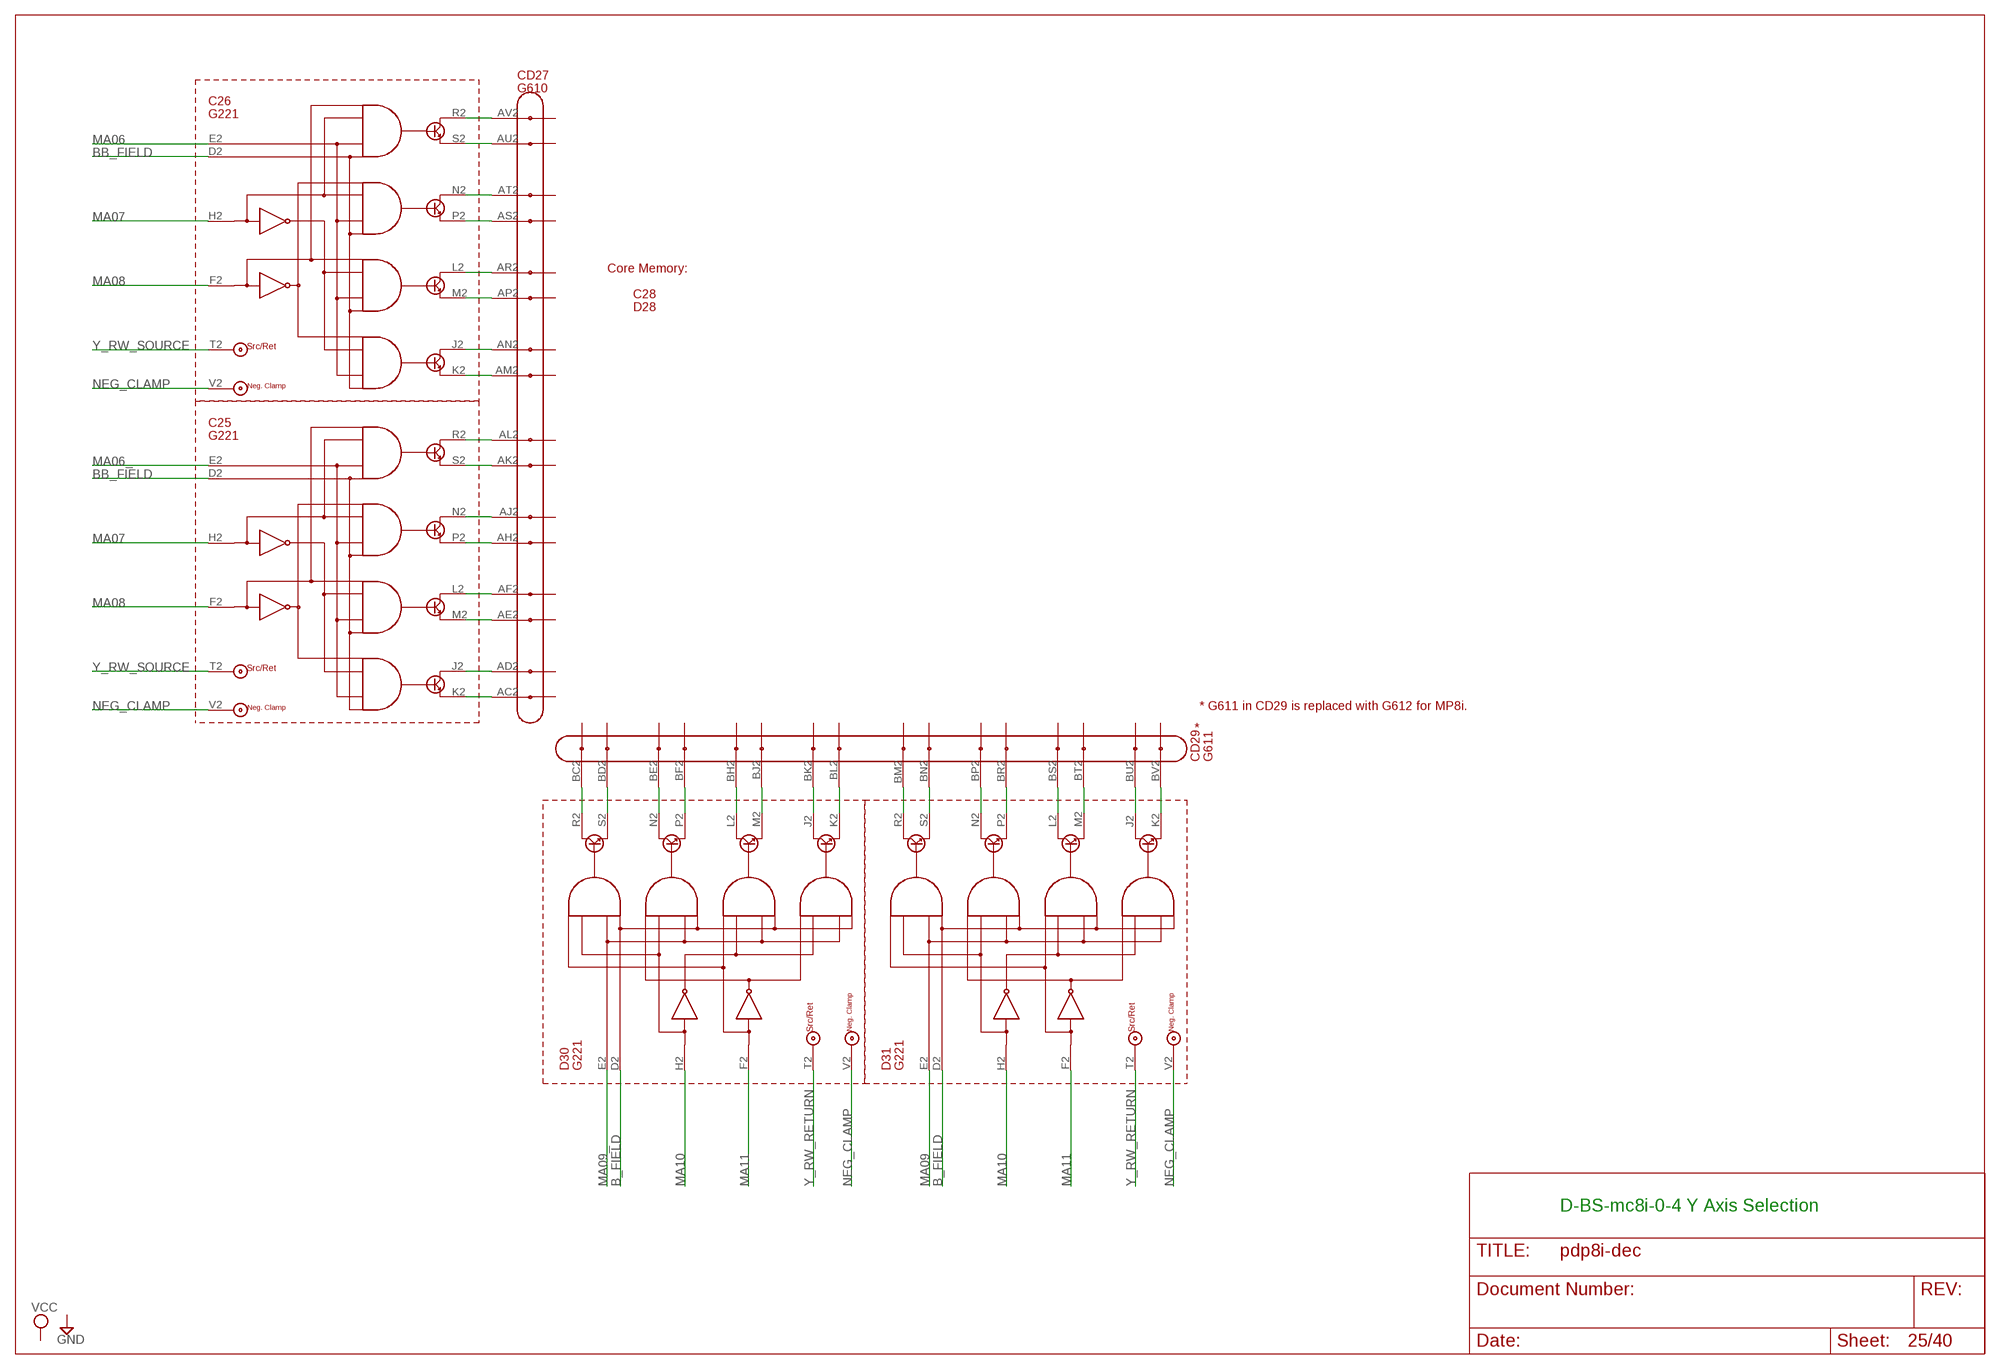
[diagram p25: schematic, sheet 25]
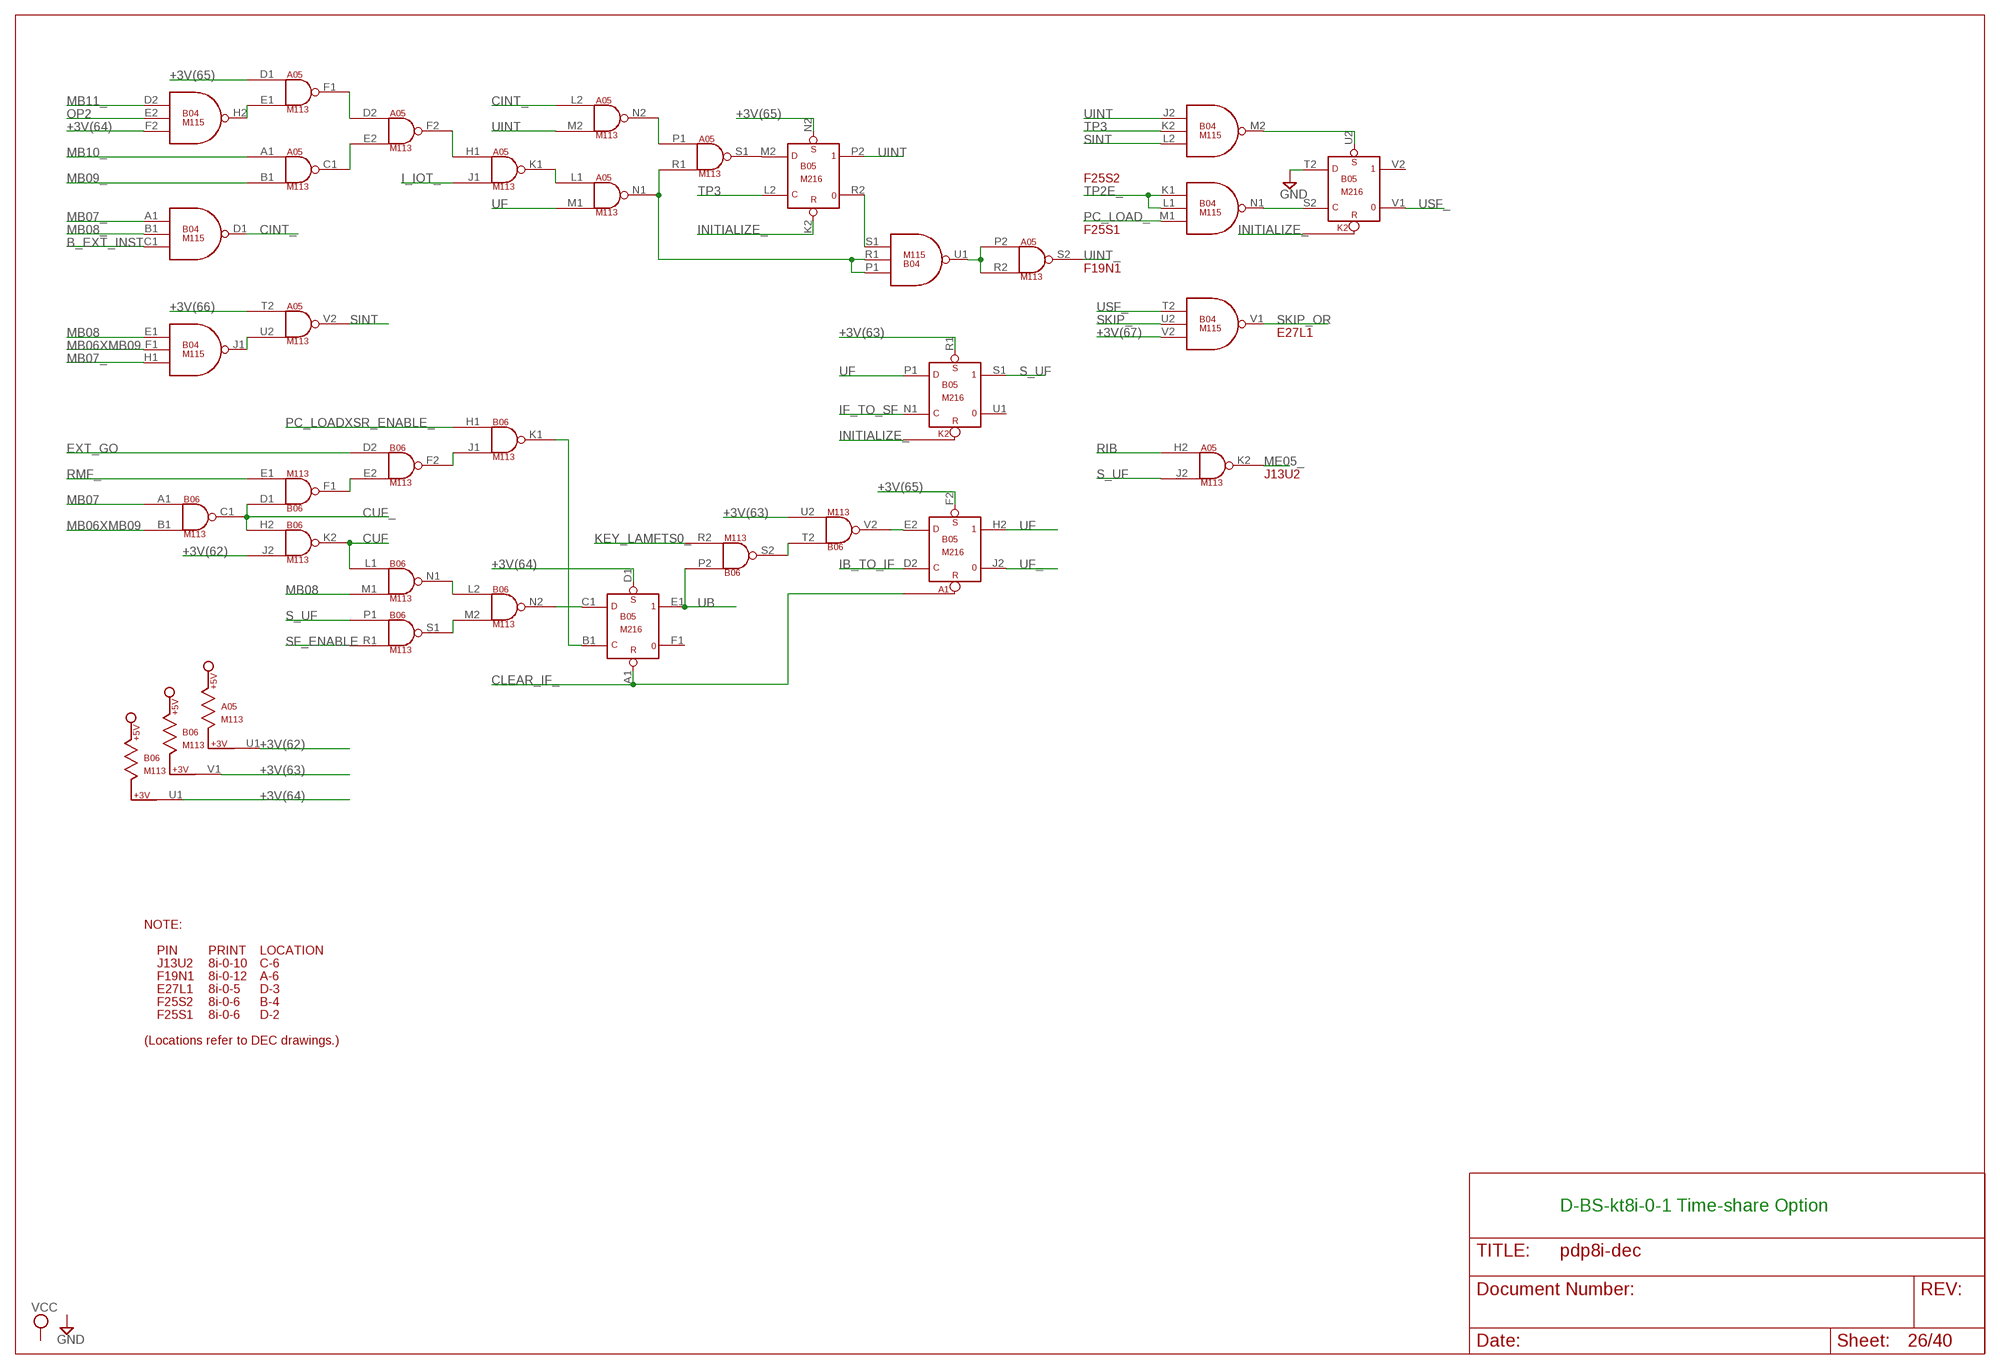
[diagram p26: schematic, sheet 26]
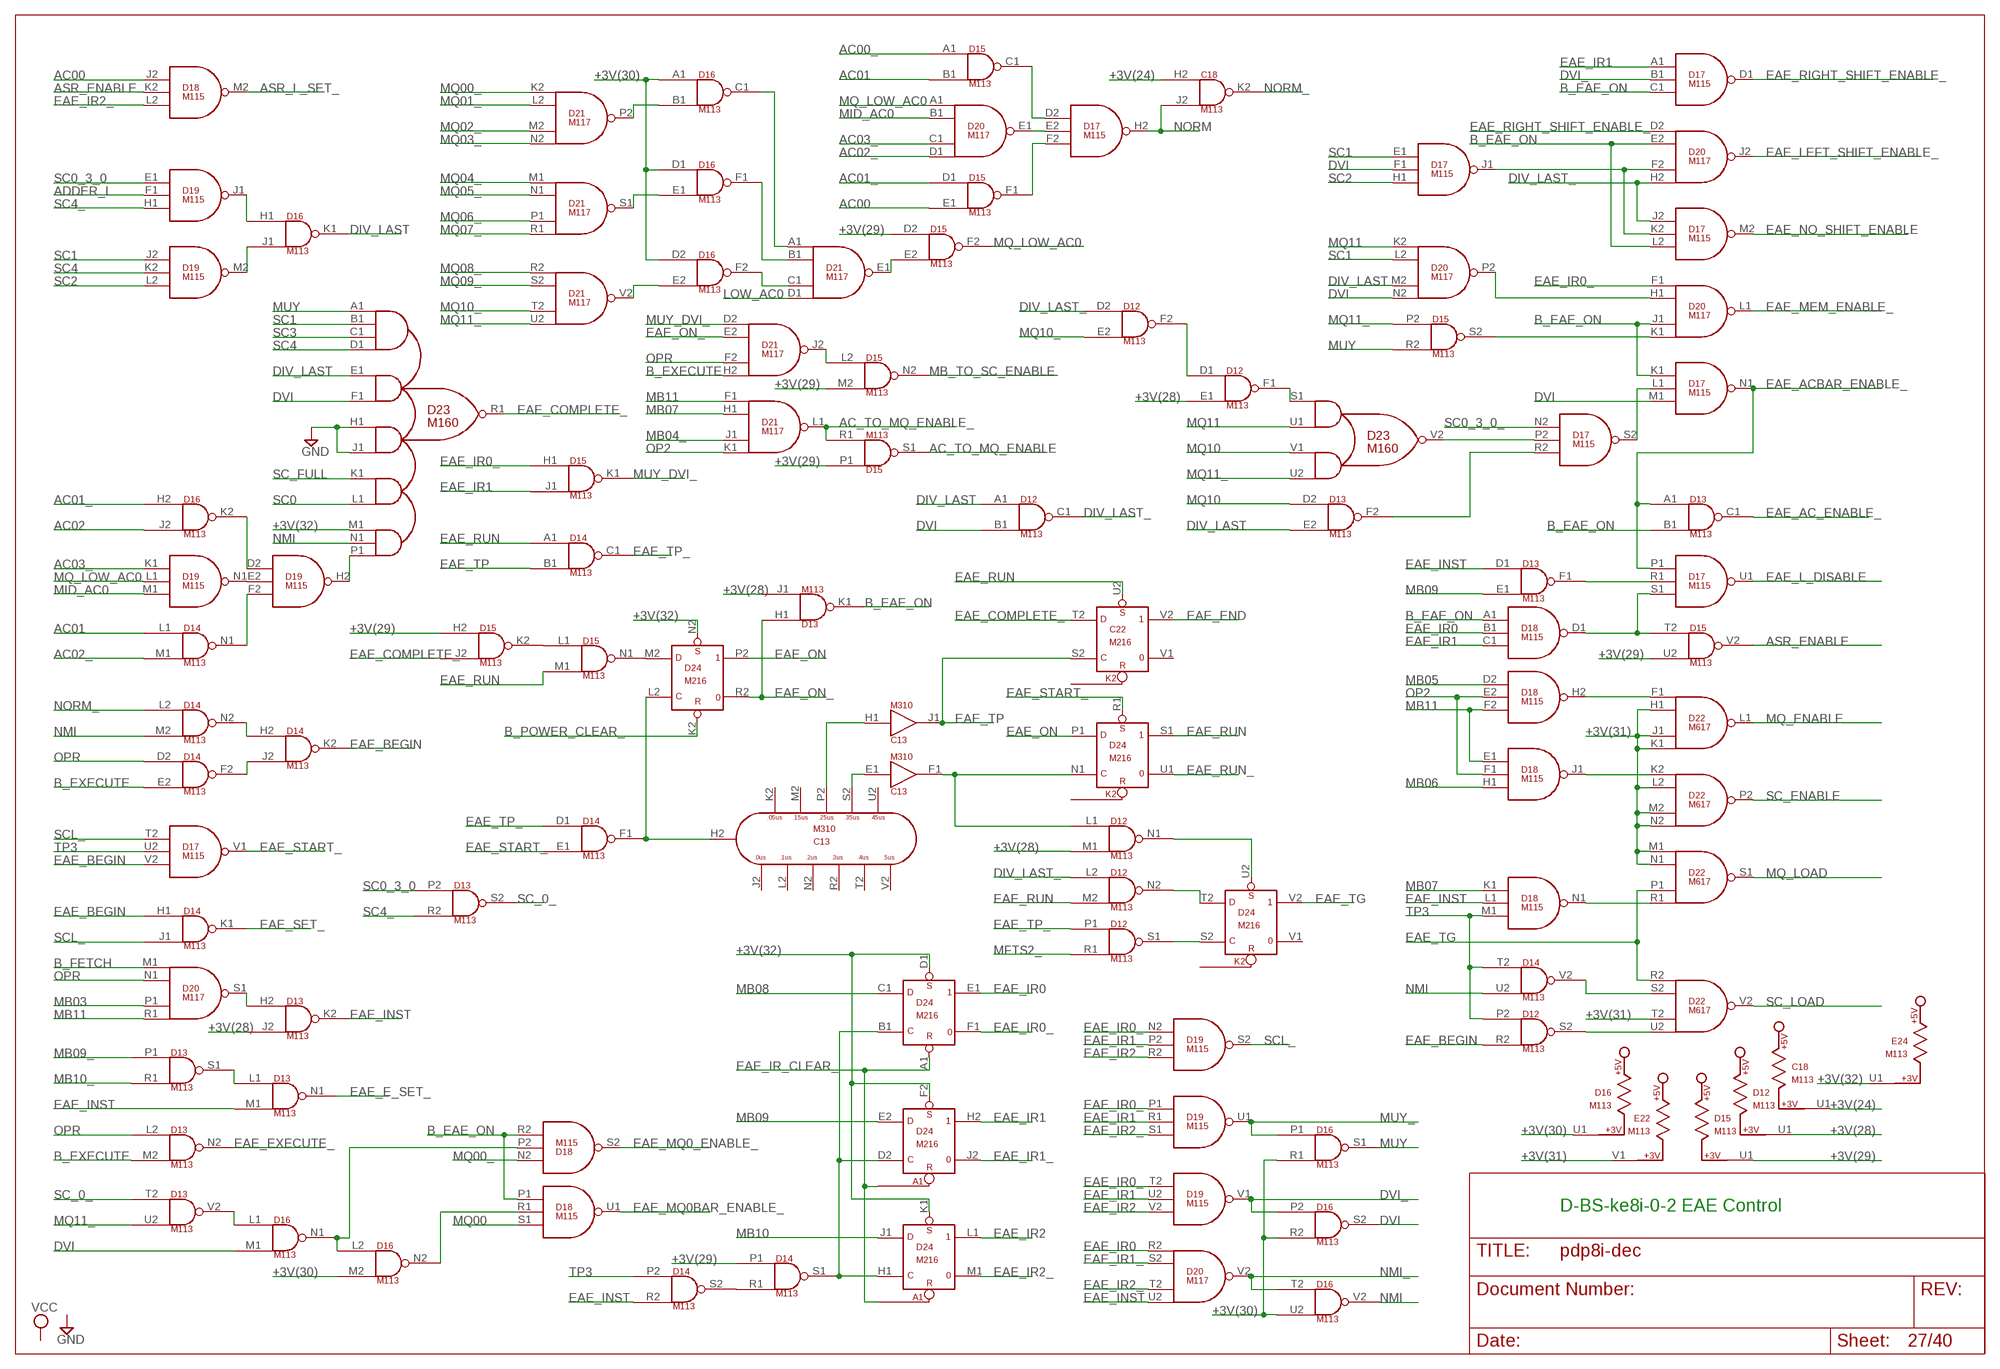
[diagram p27: schematic, sheet 27]
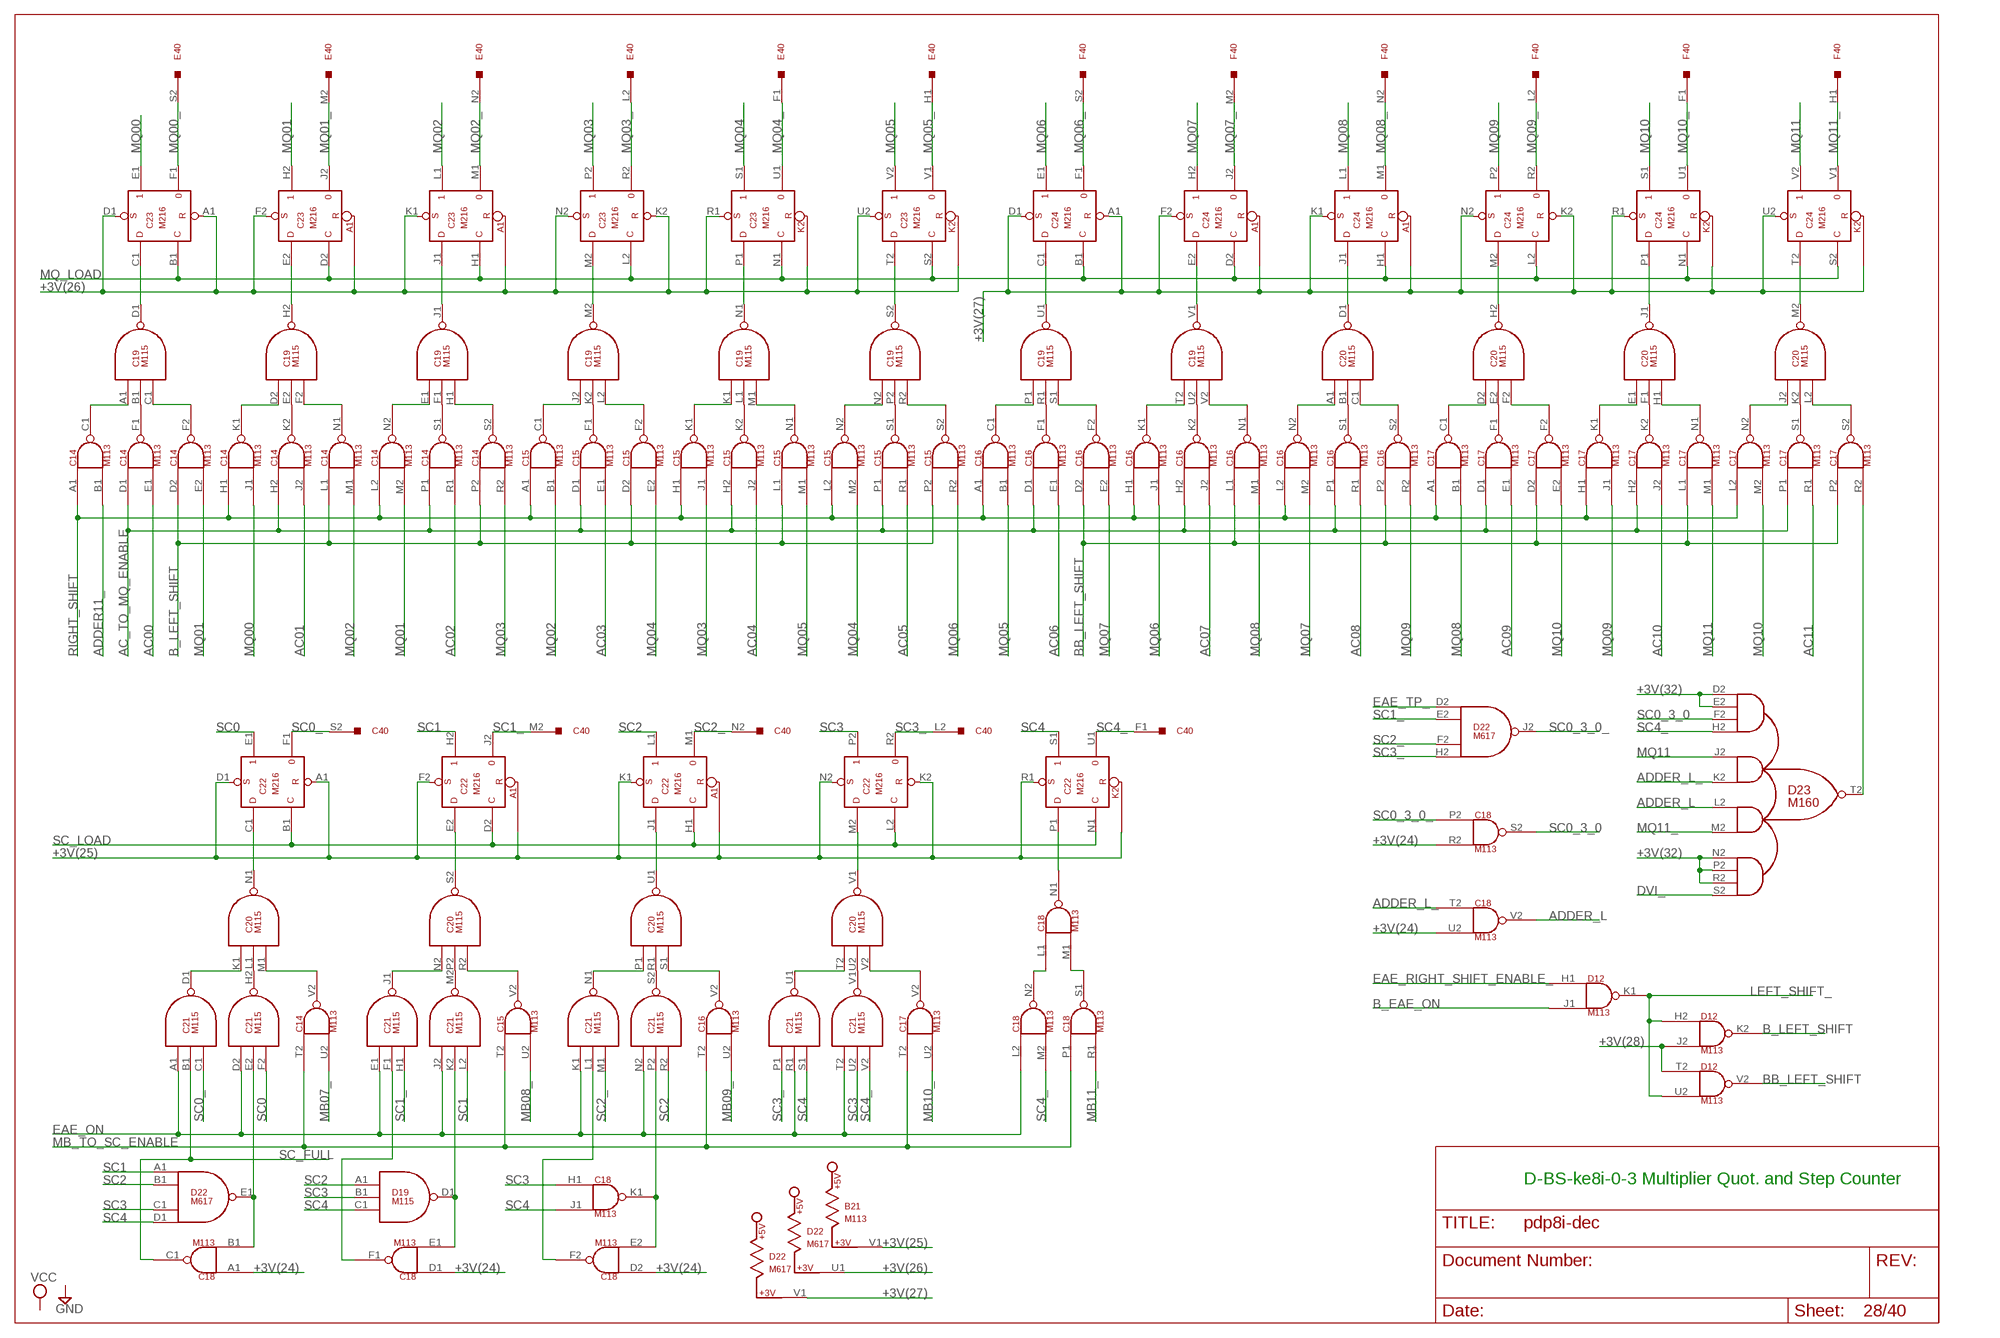
[diagram p28: schematic, sheet 28]
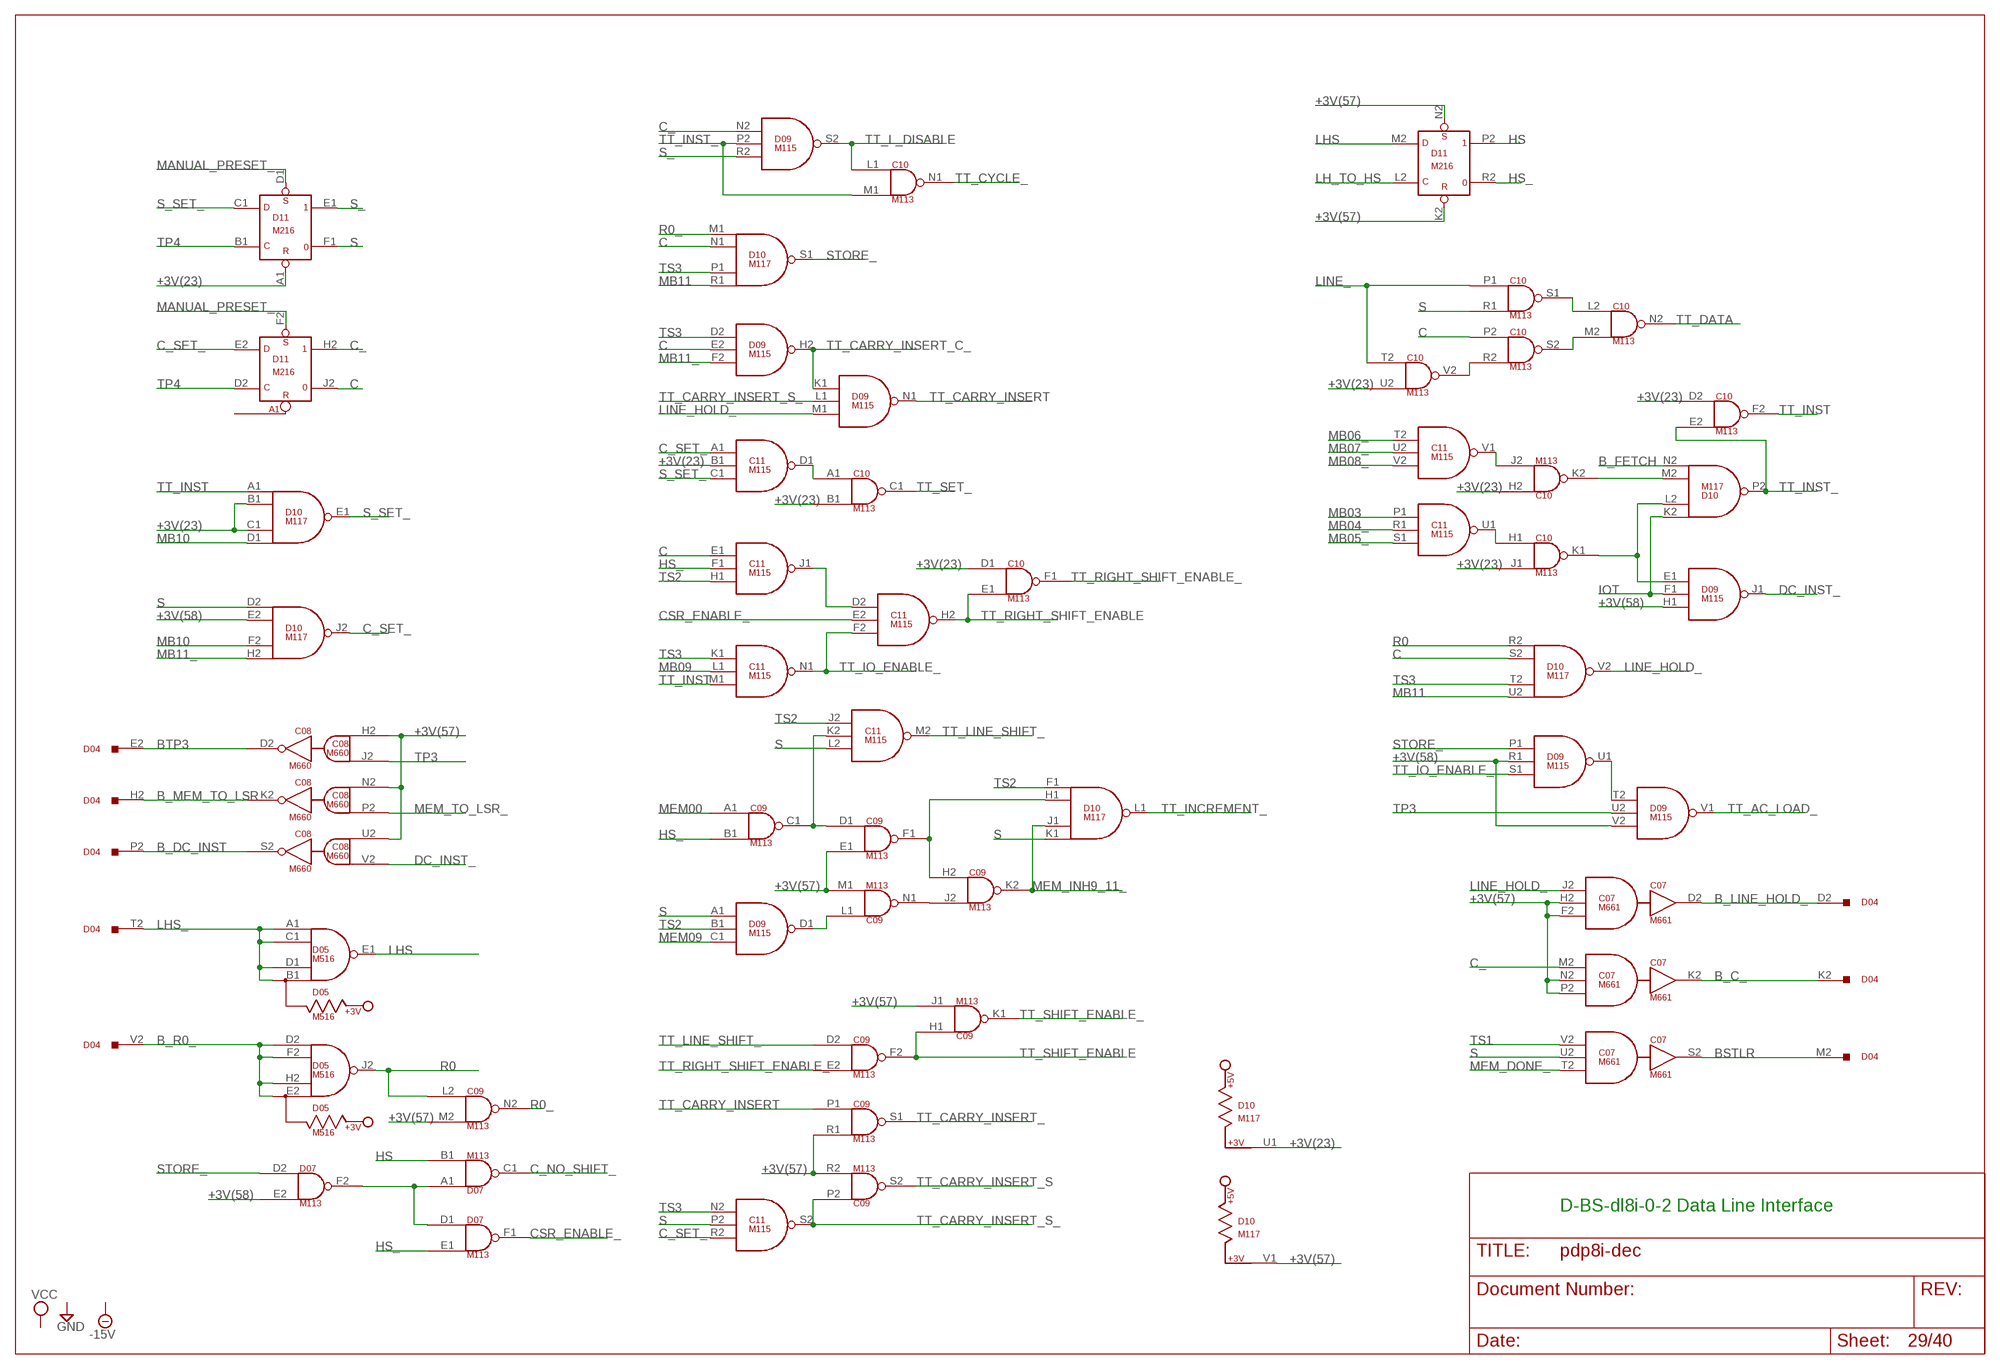
[diagram p29: schematic, sheet 29]
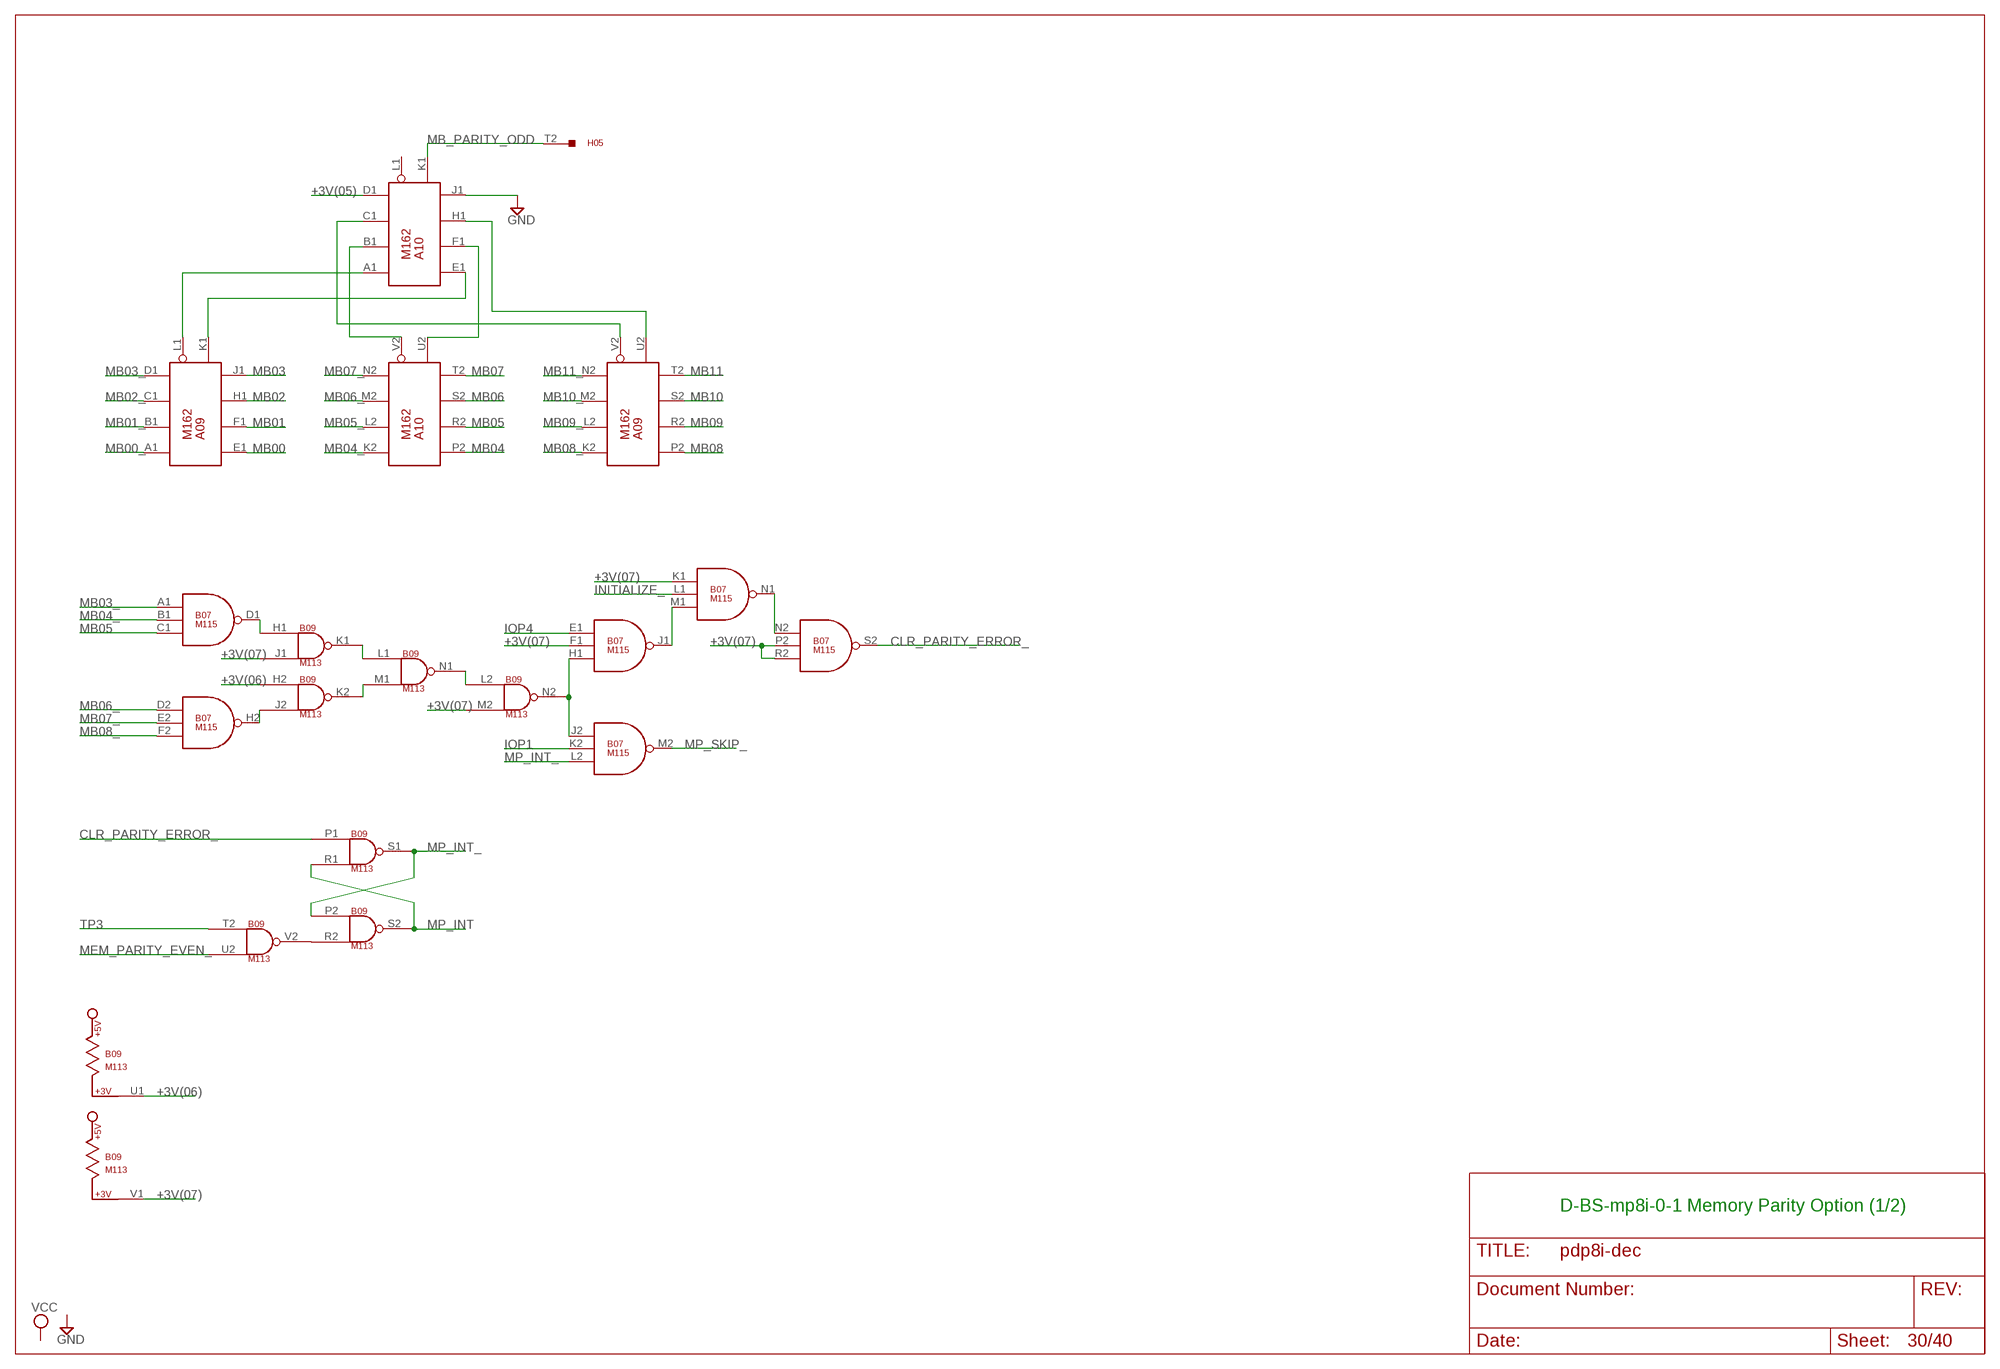
[diagram p30: schematic, sheet 30]
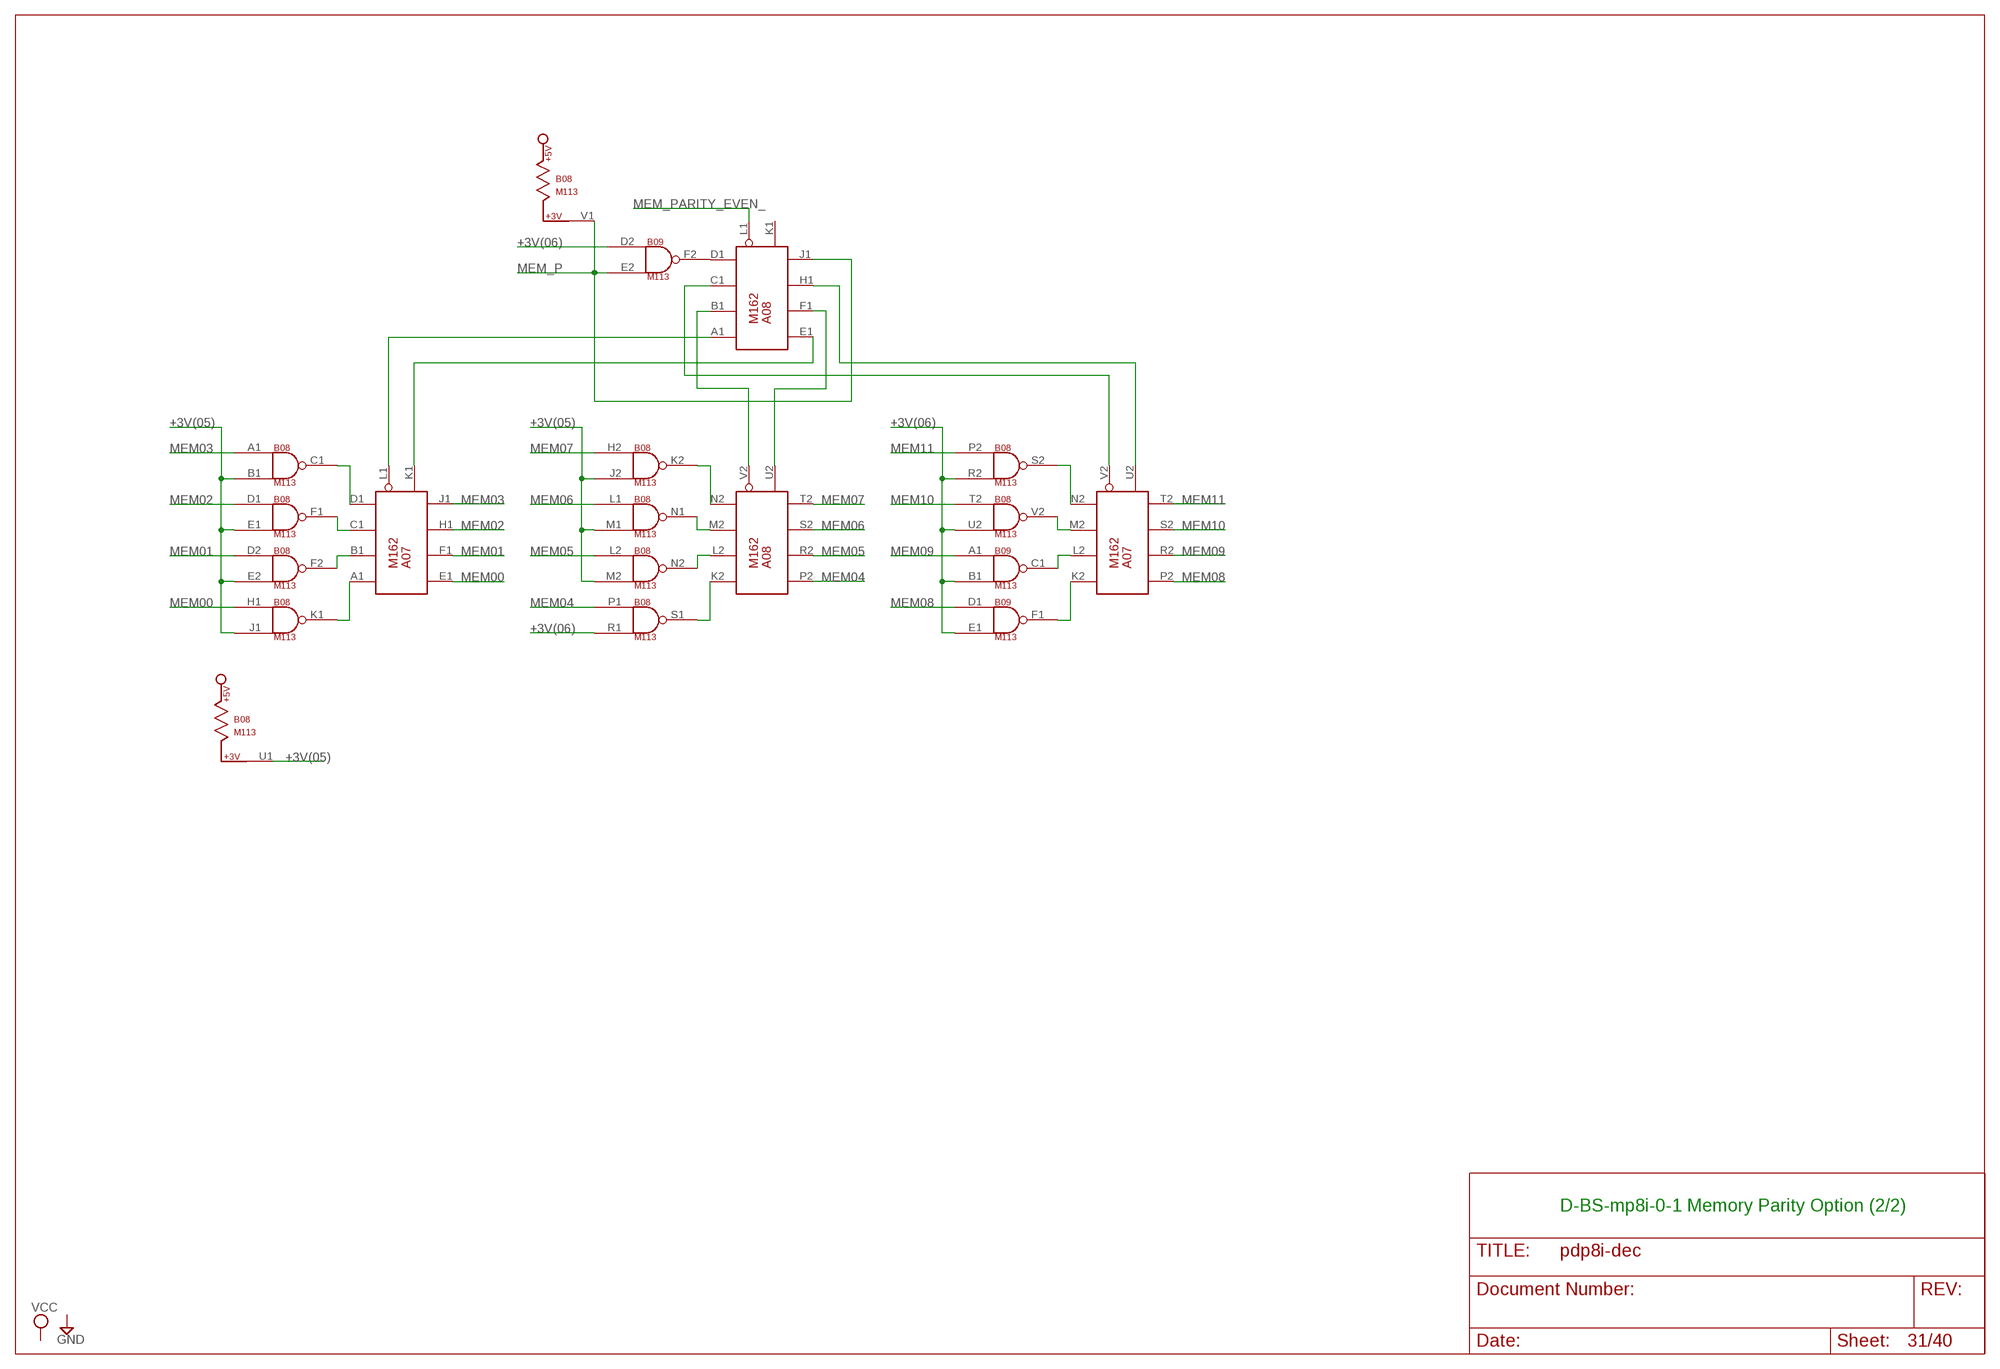
[diagram p31: schematic, sheet 31]
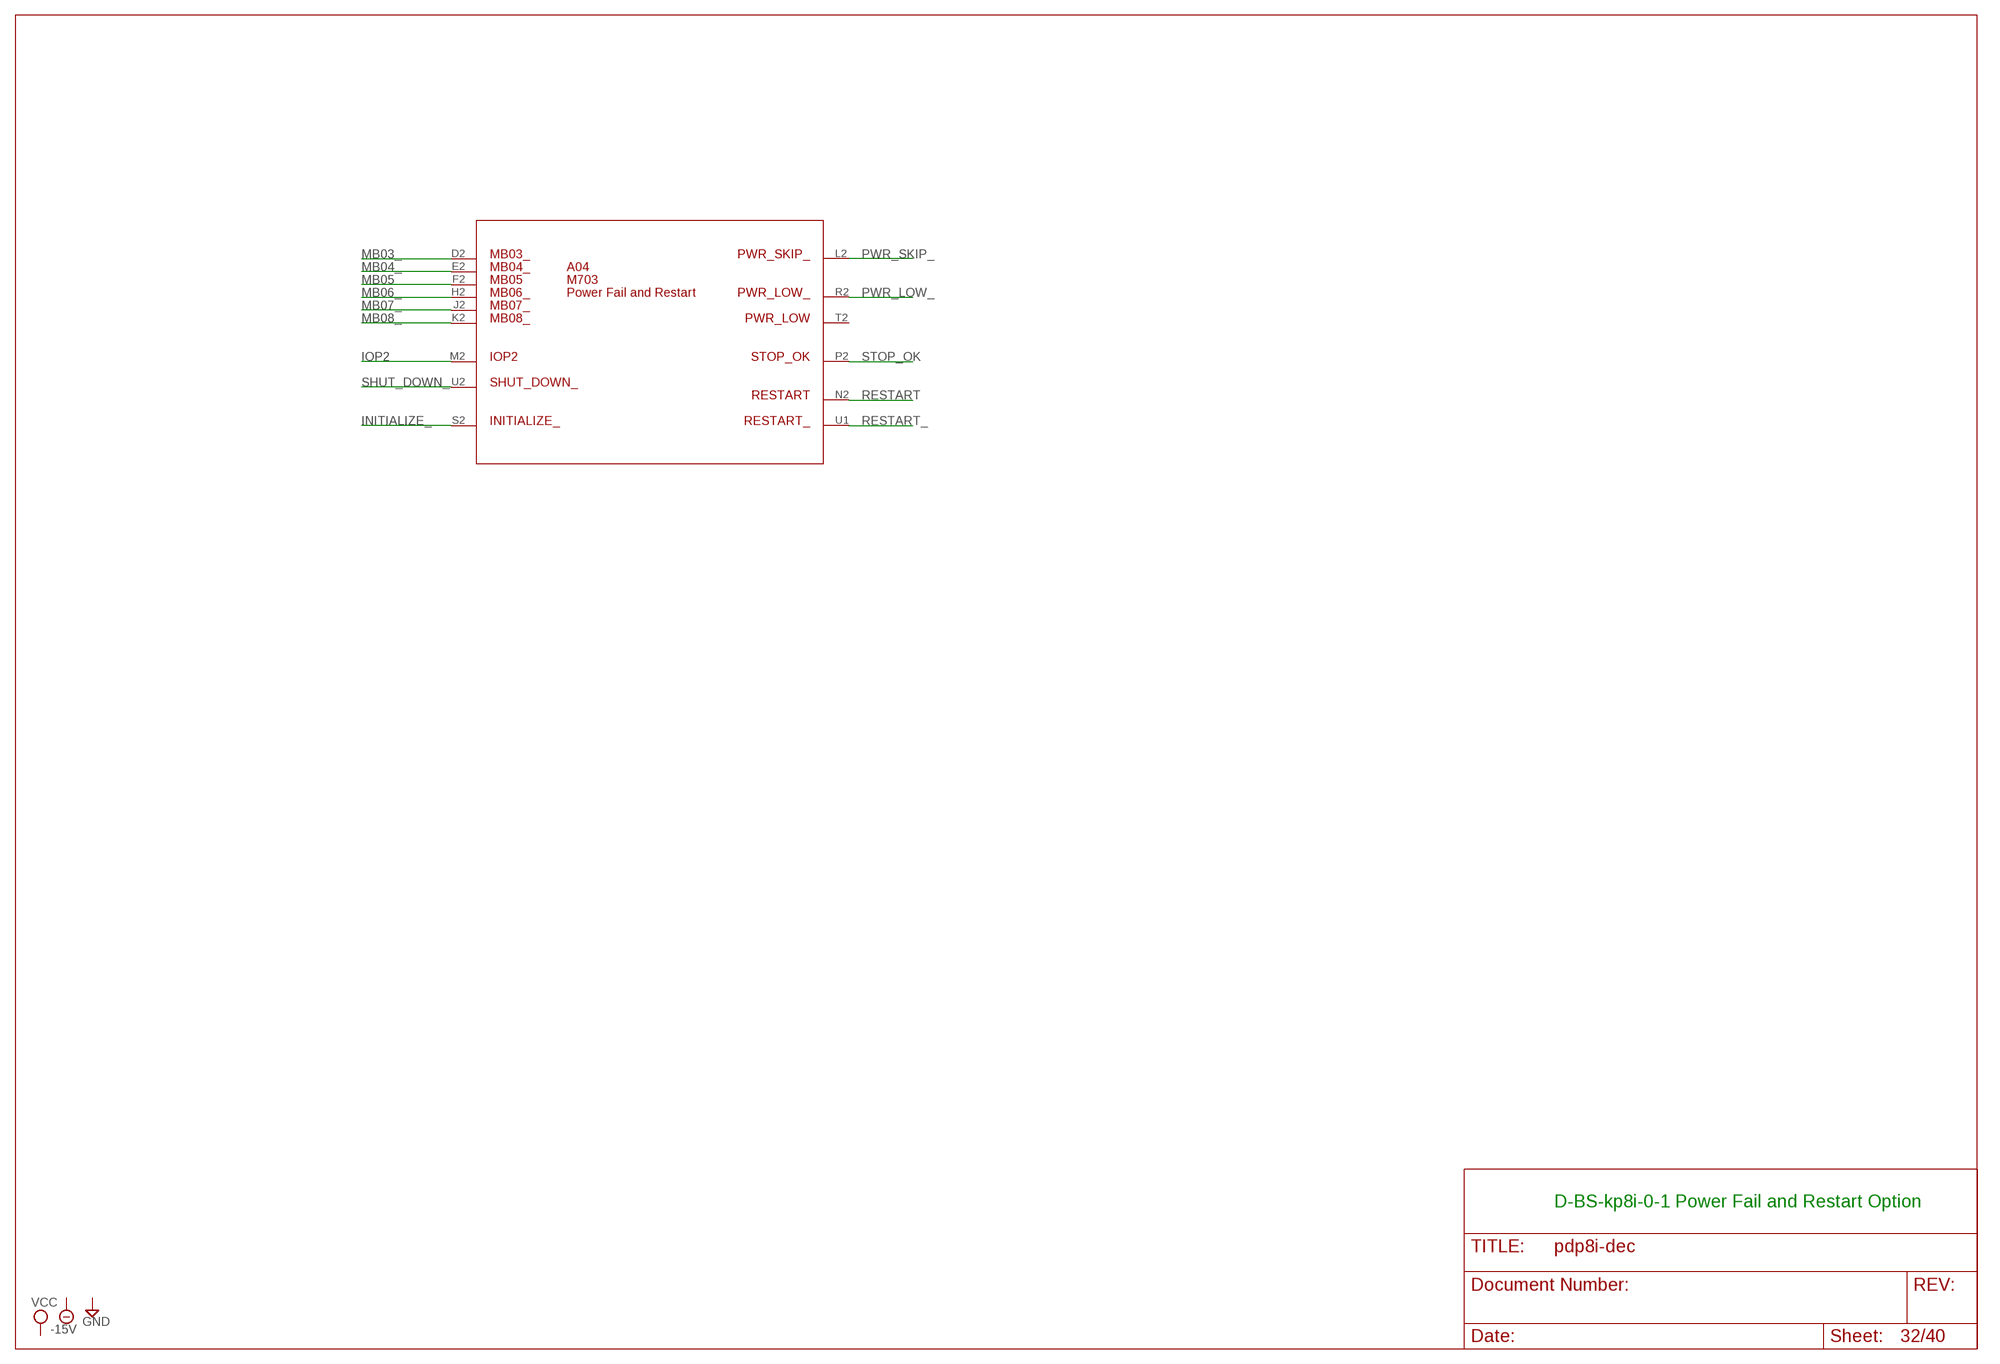
[diagram p32: schematic, sheet 32]
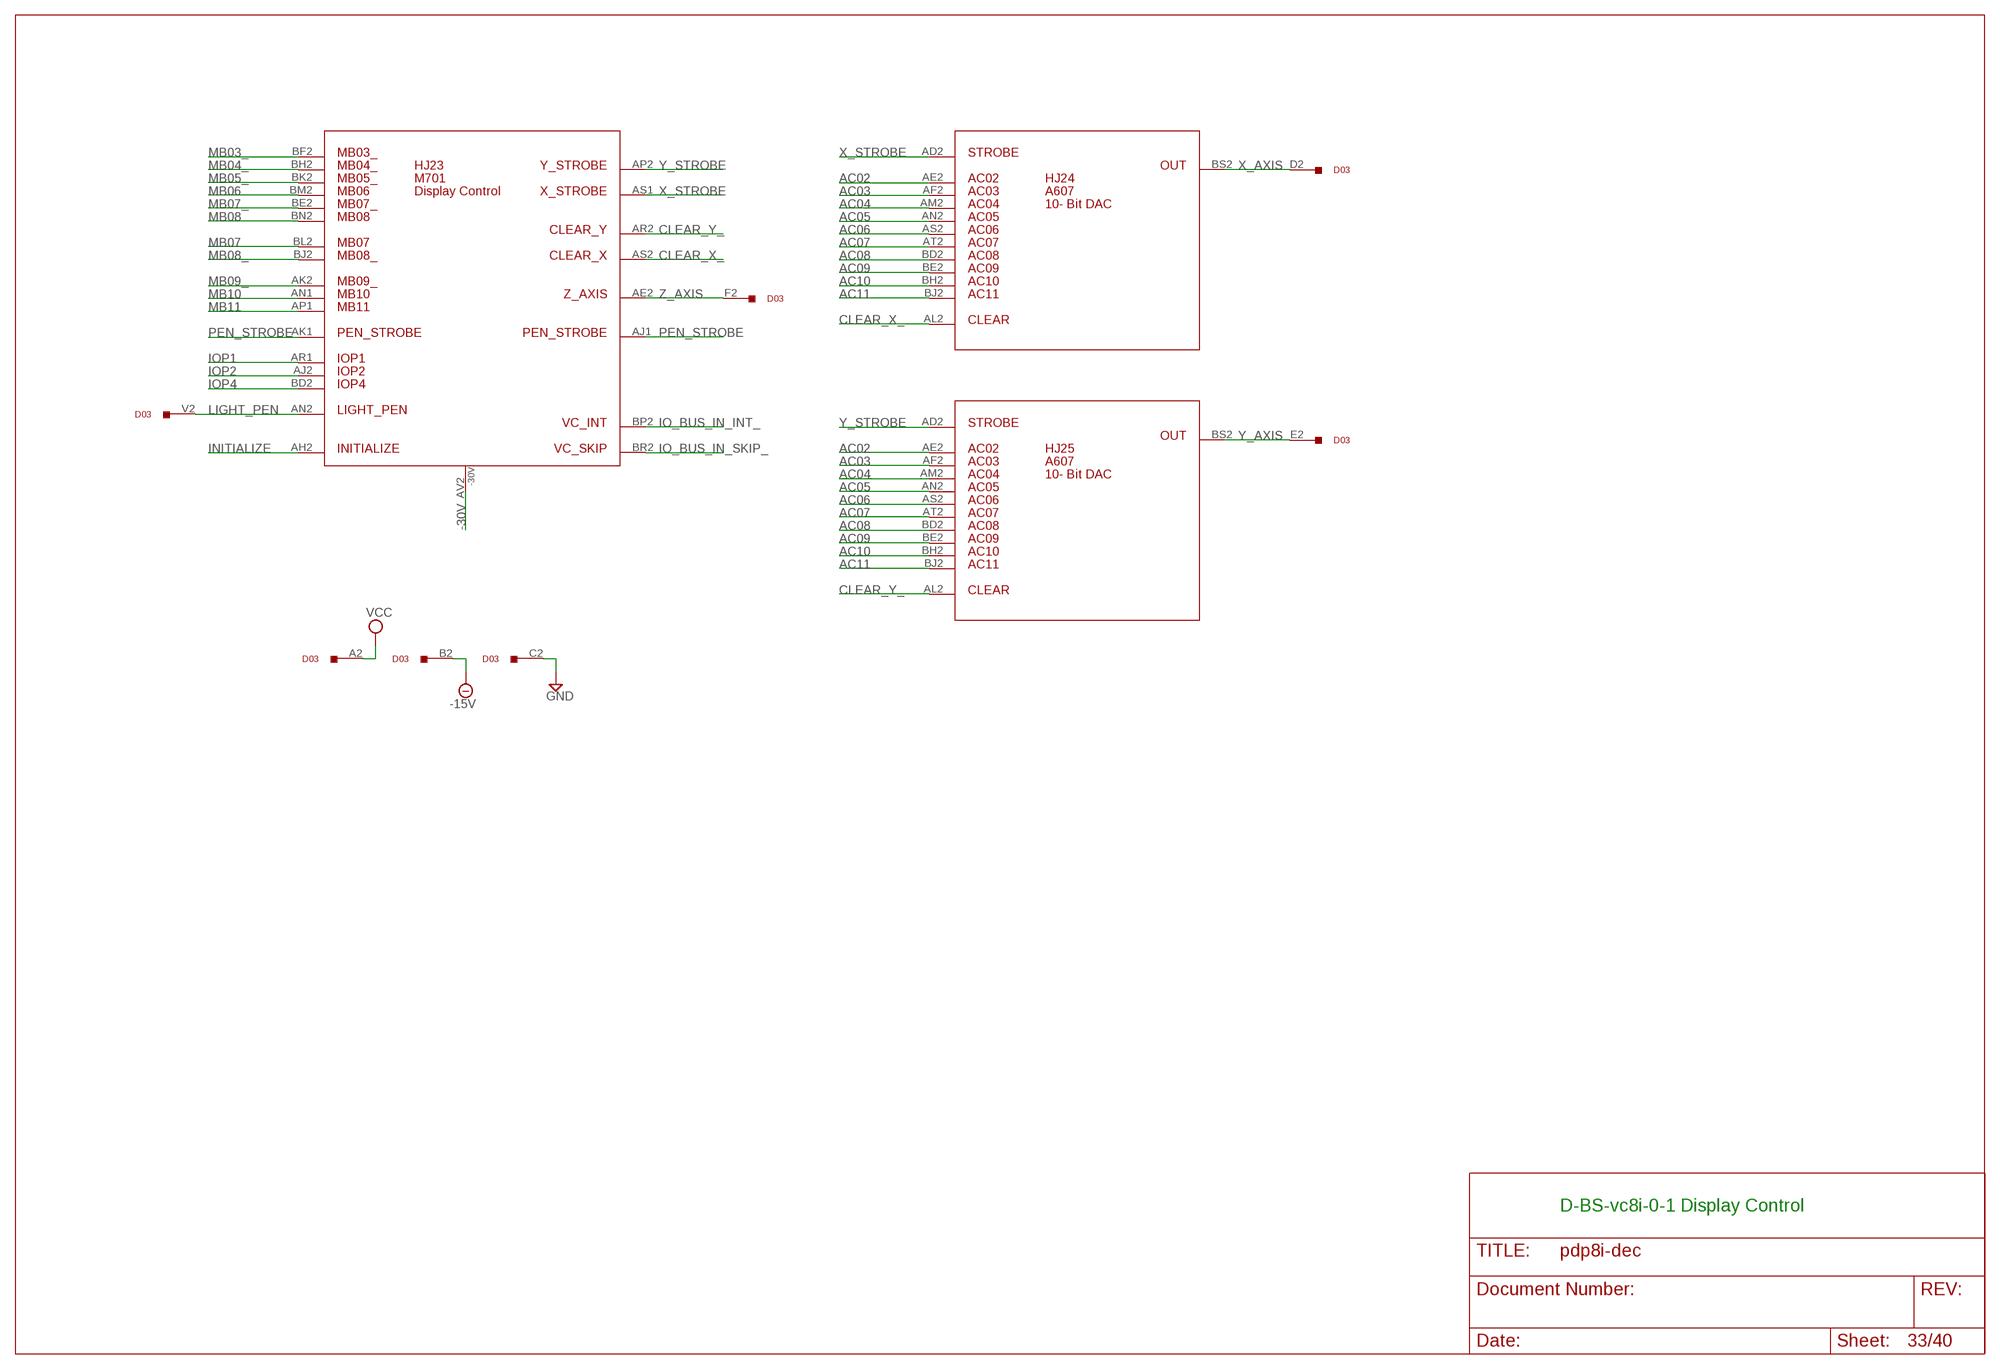
[diagram p33: schematic, sheet 33]
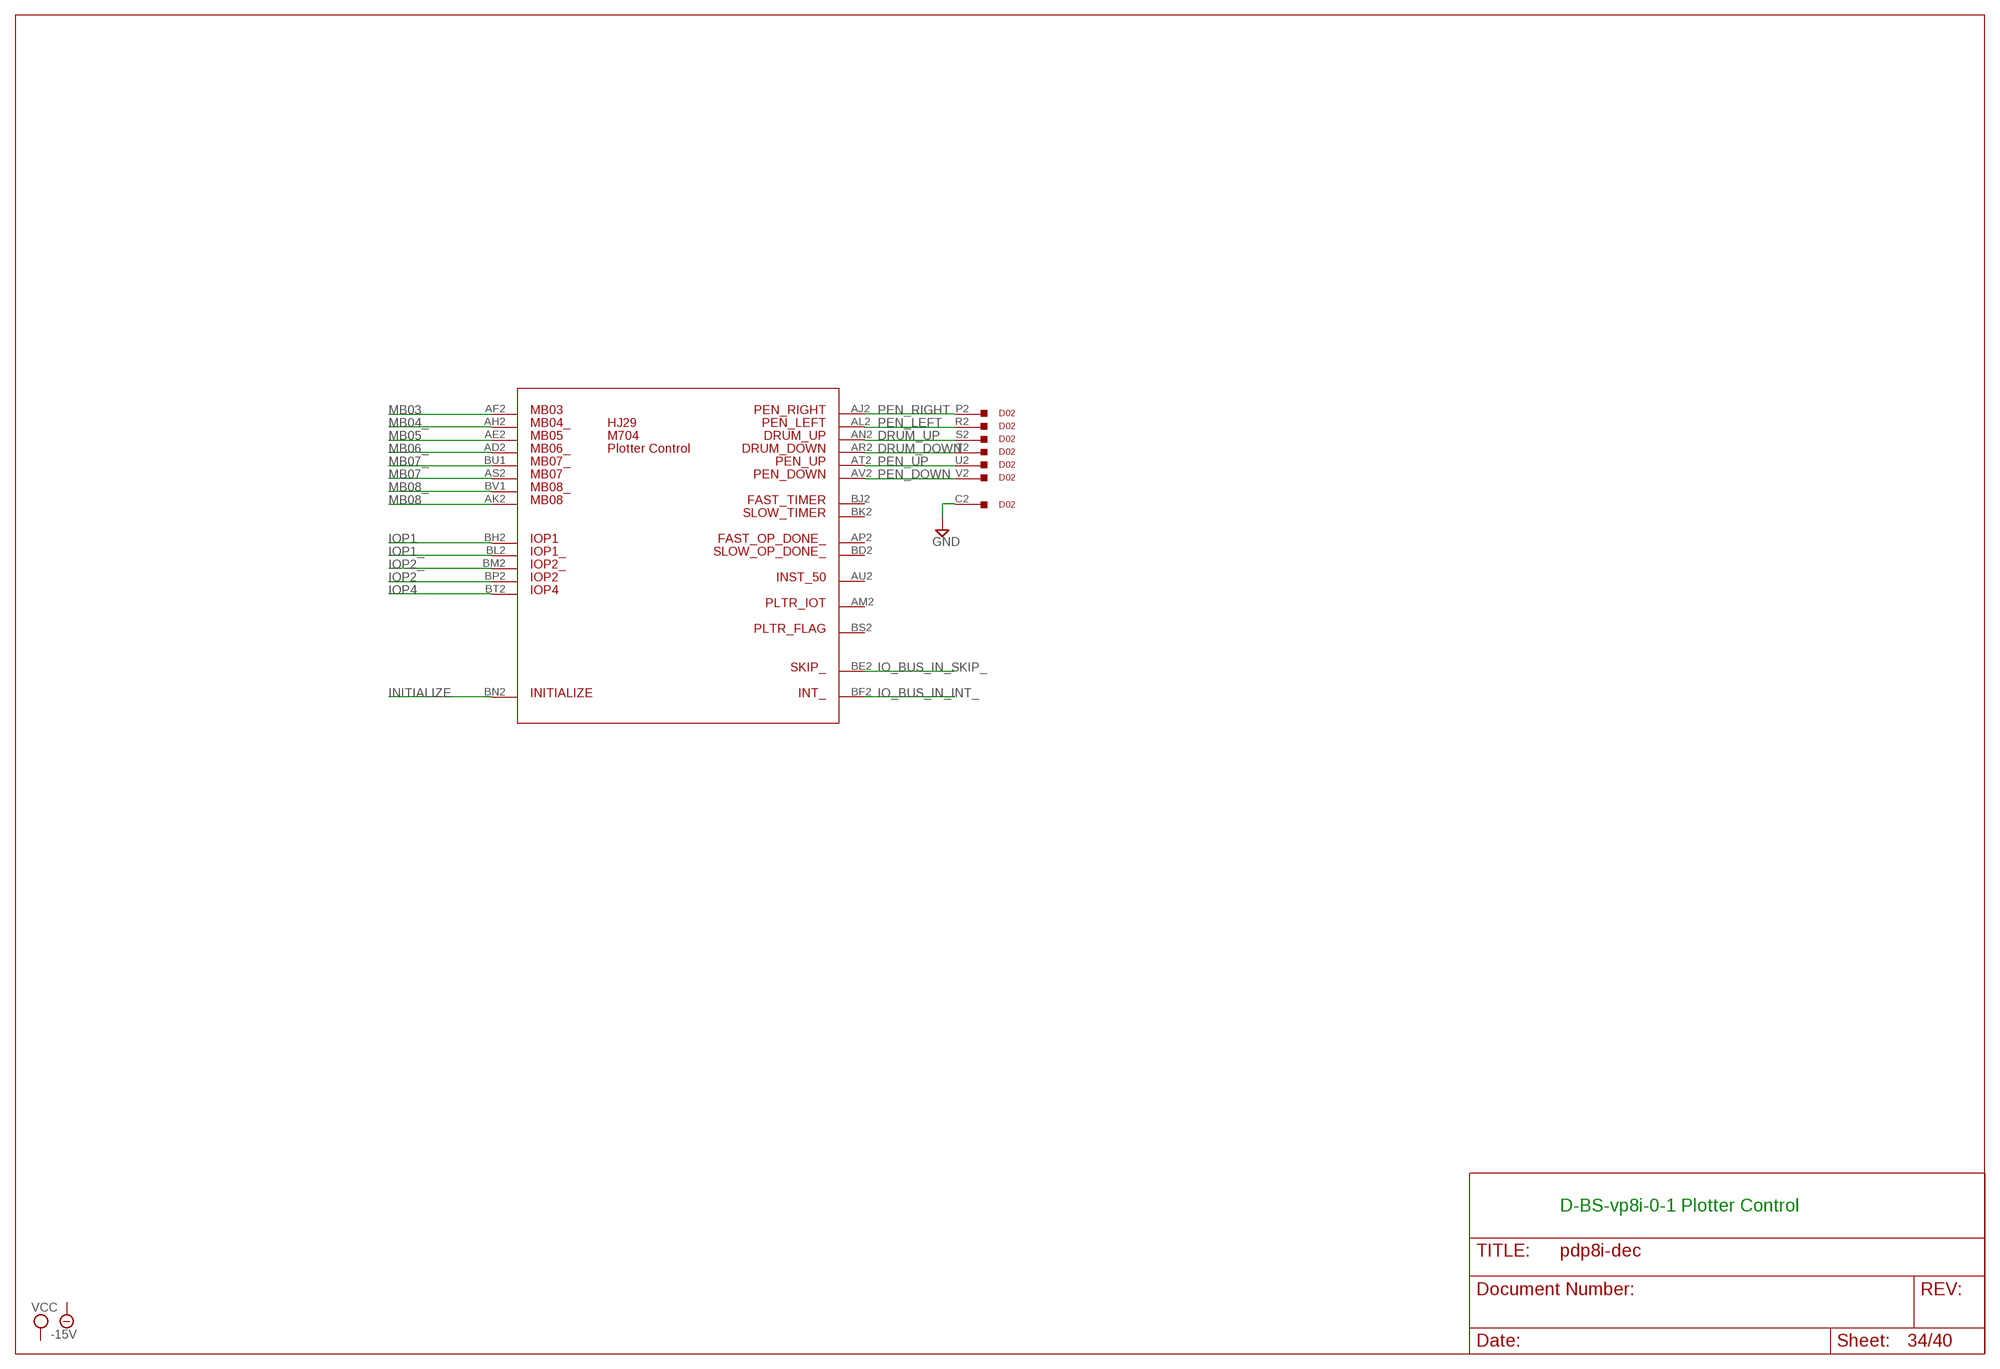
[diagram p34: schematic, sheet 34]
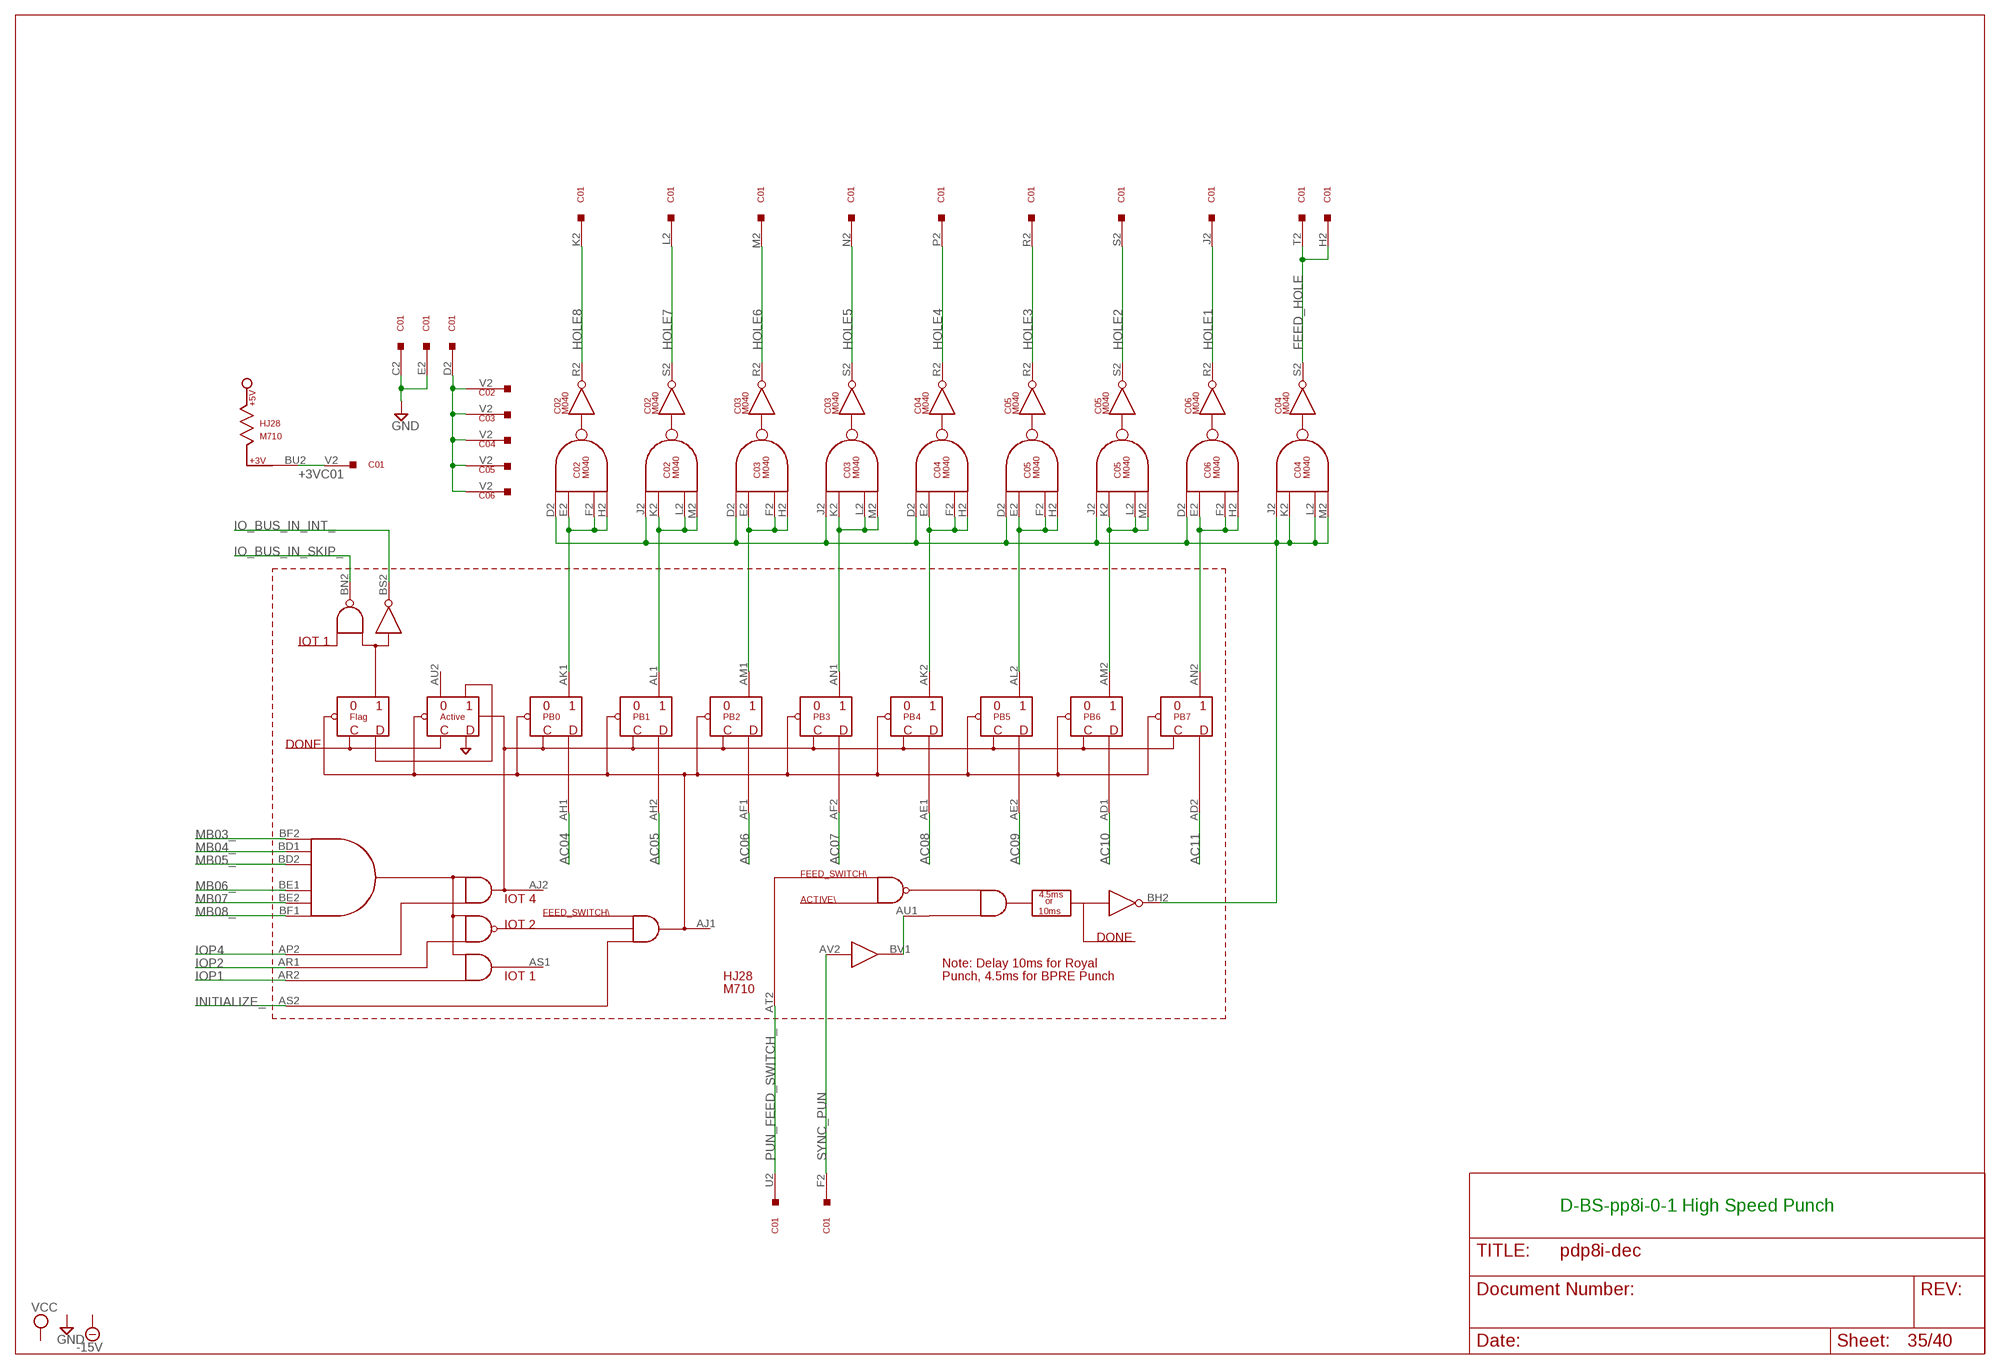
[diagram p35: schematic, sheet 35]
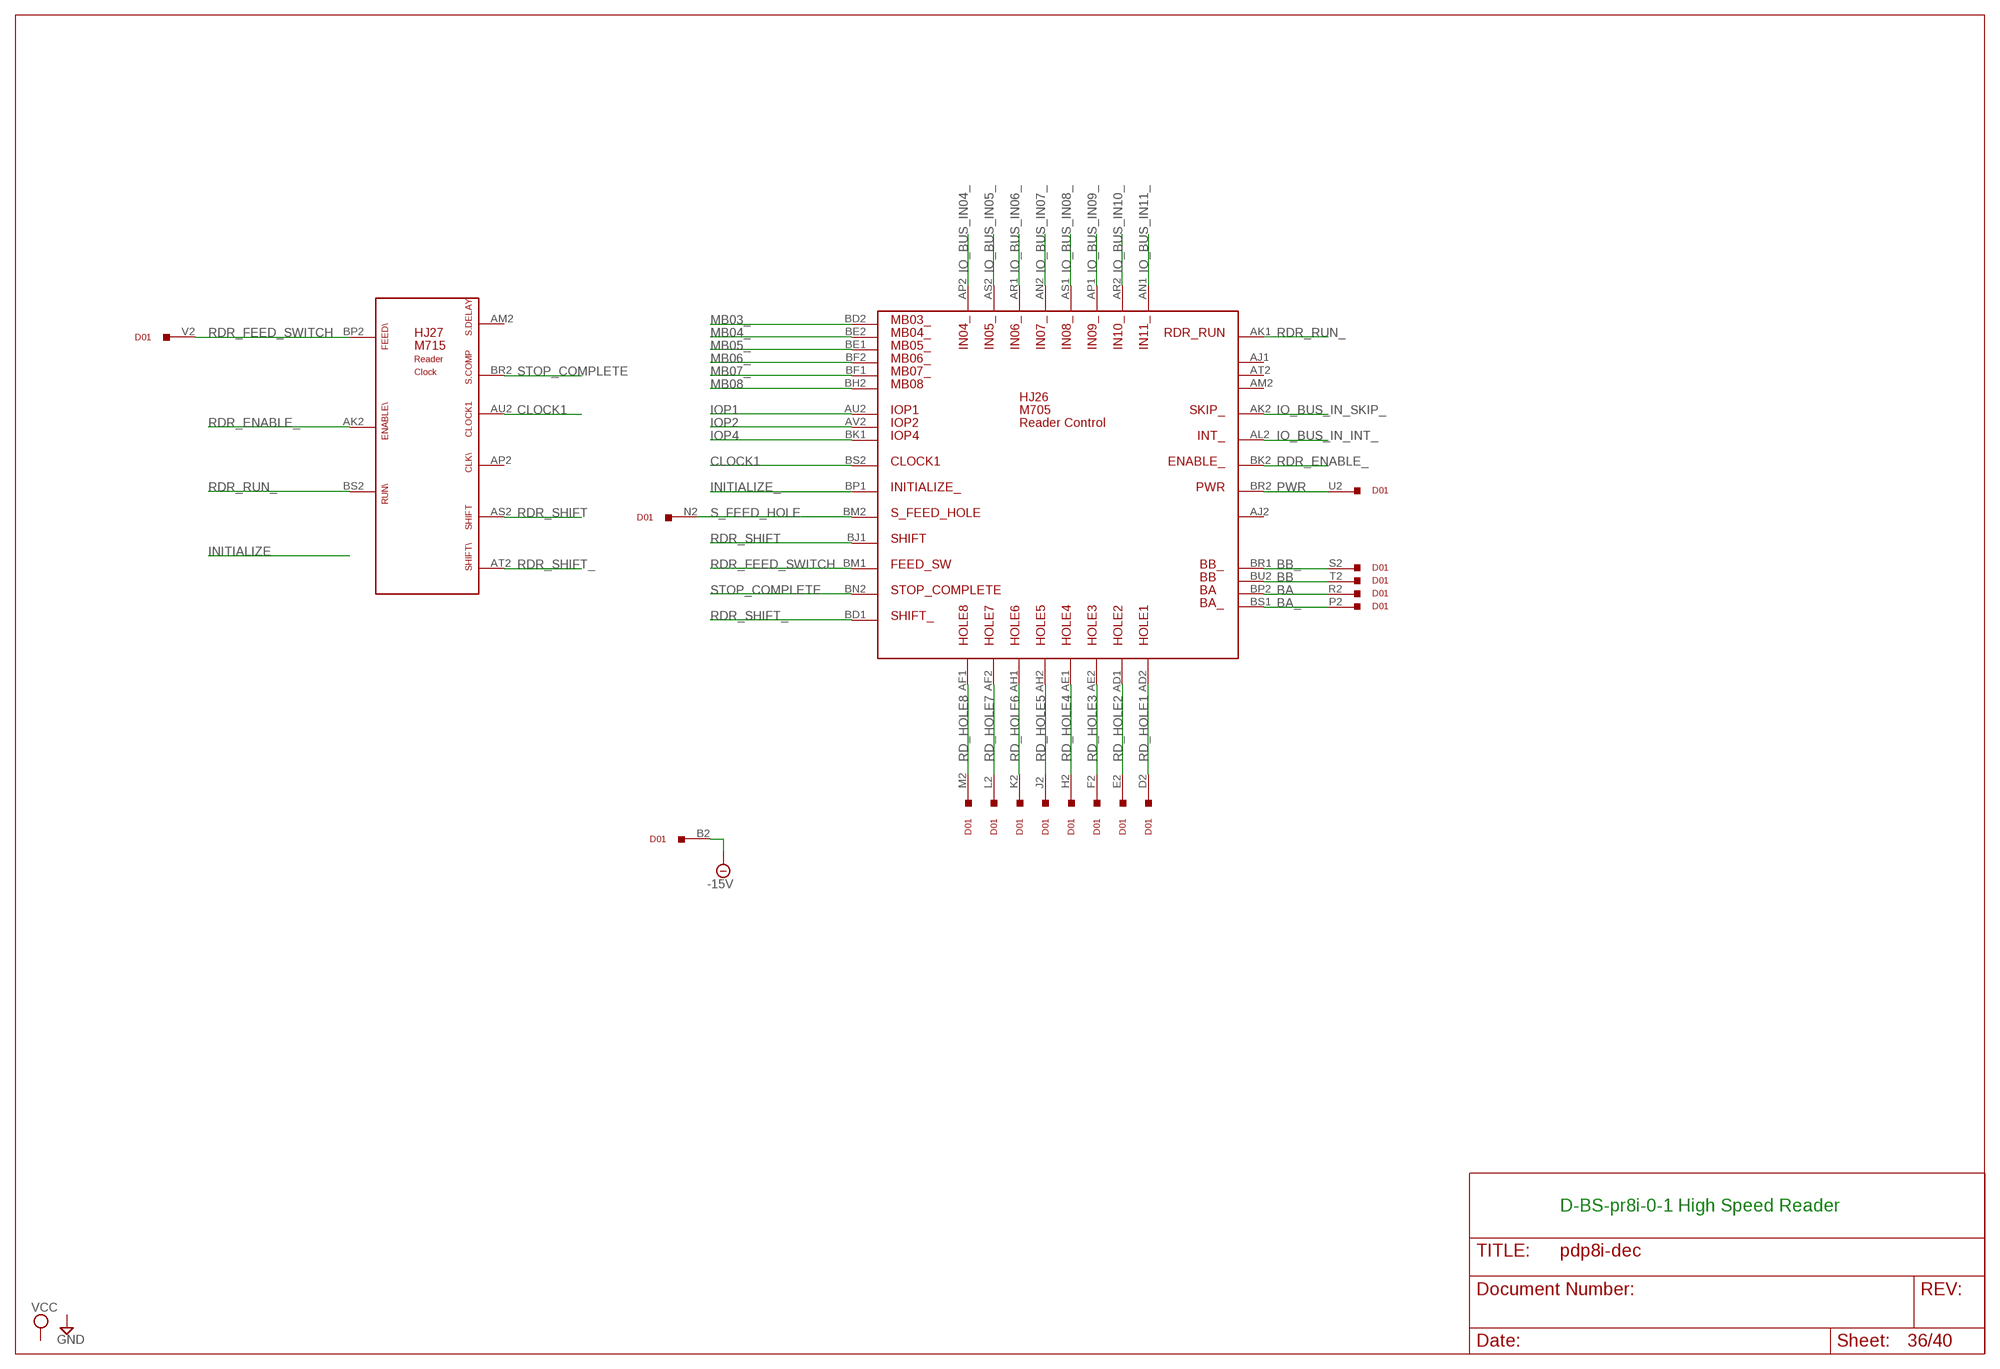
[diagram p36: schematic, sheet 36]
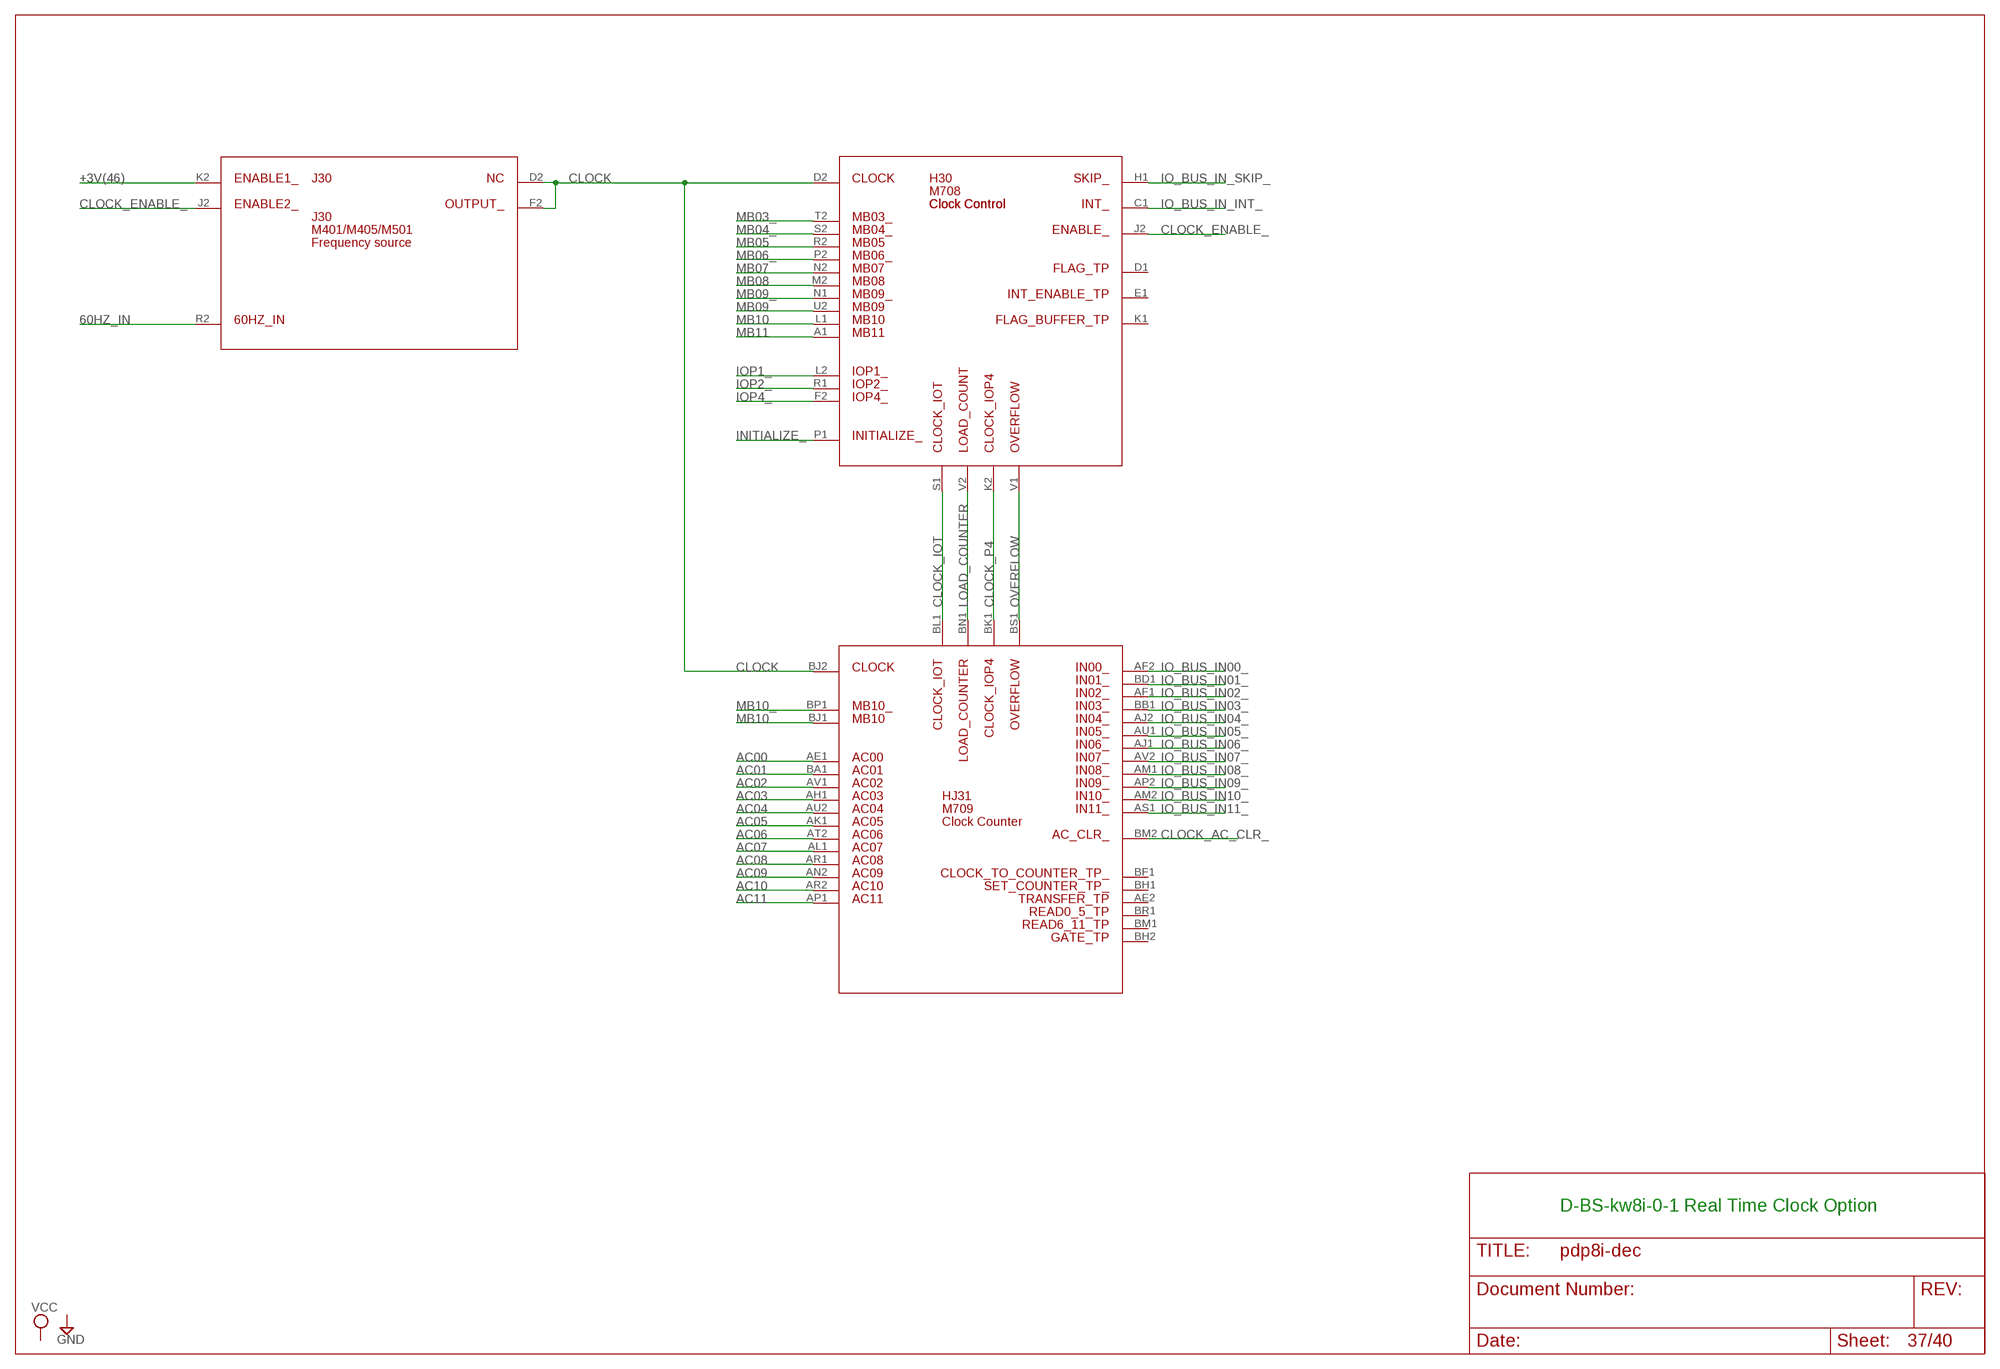
[diagram p37: schematic, sheet 37]
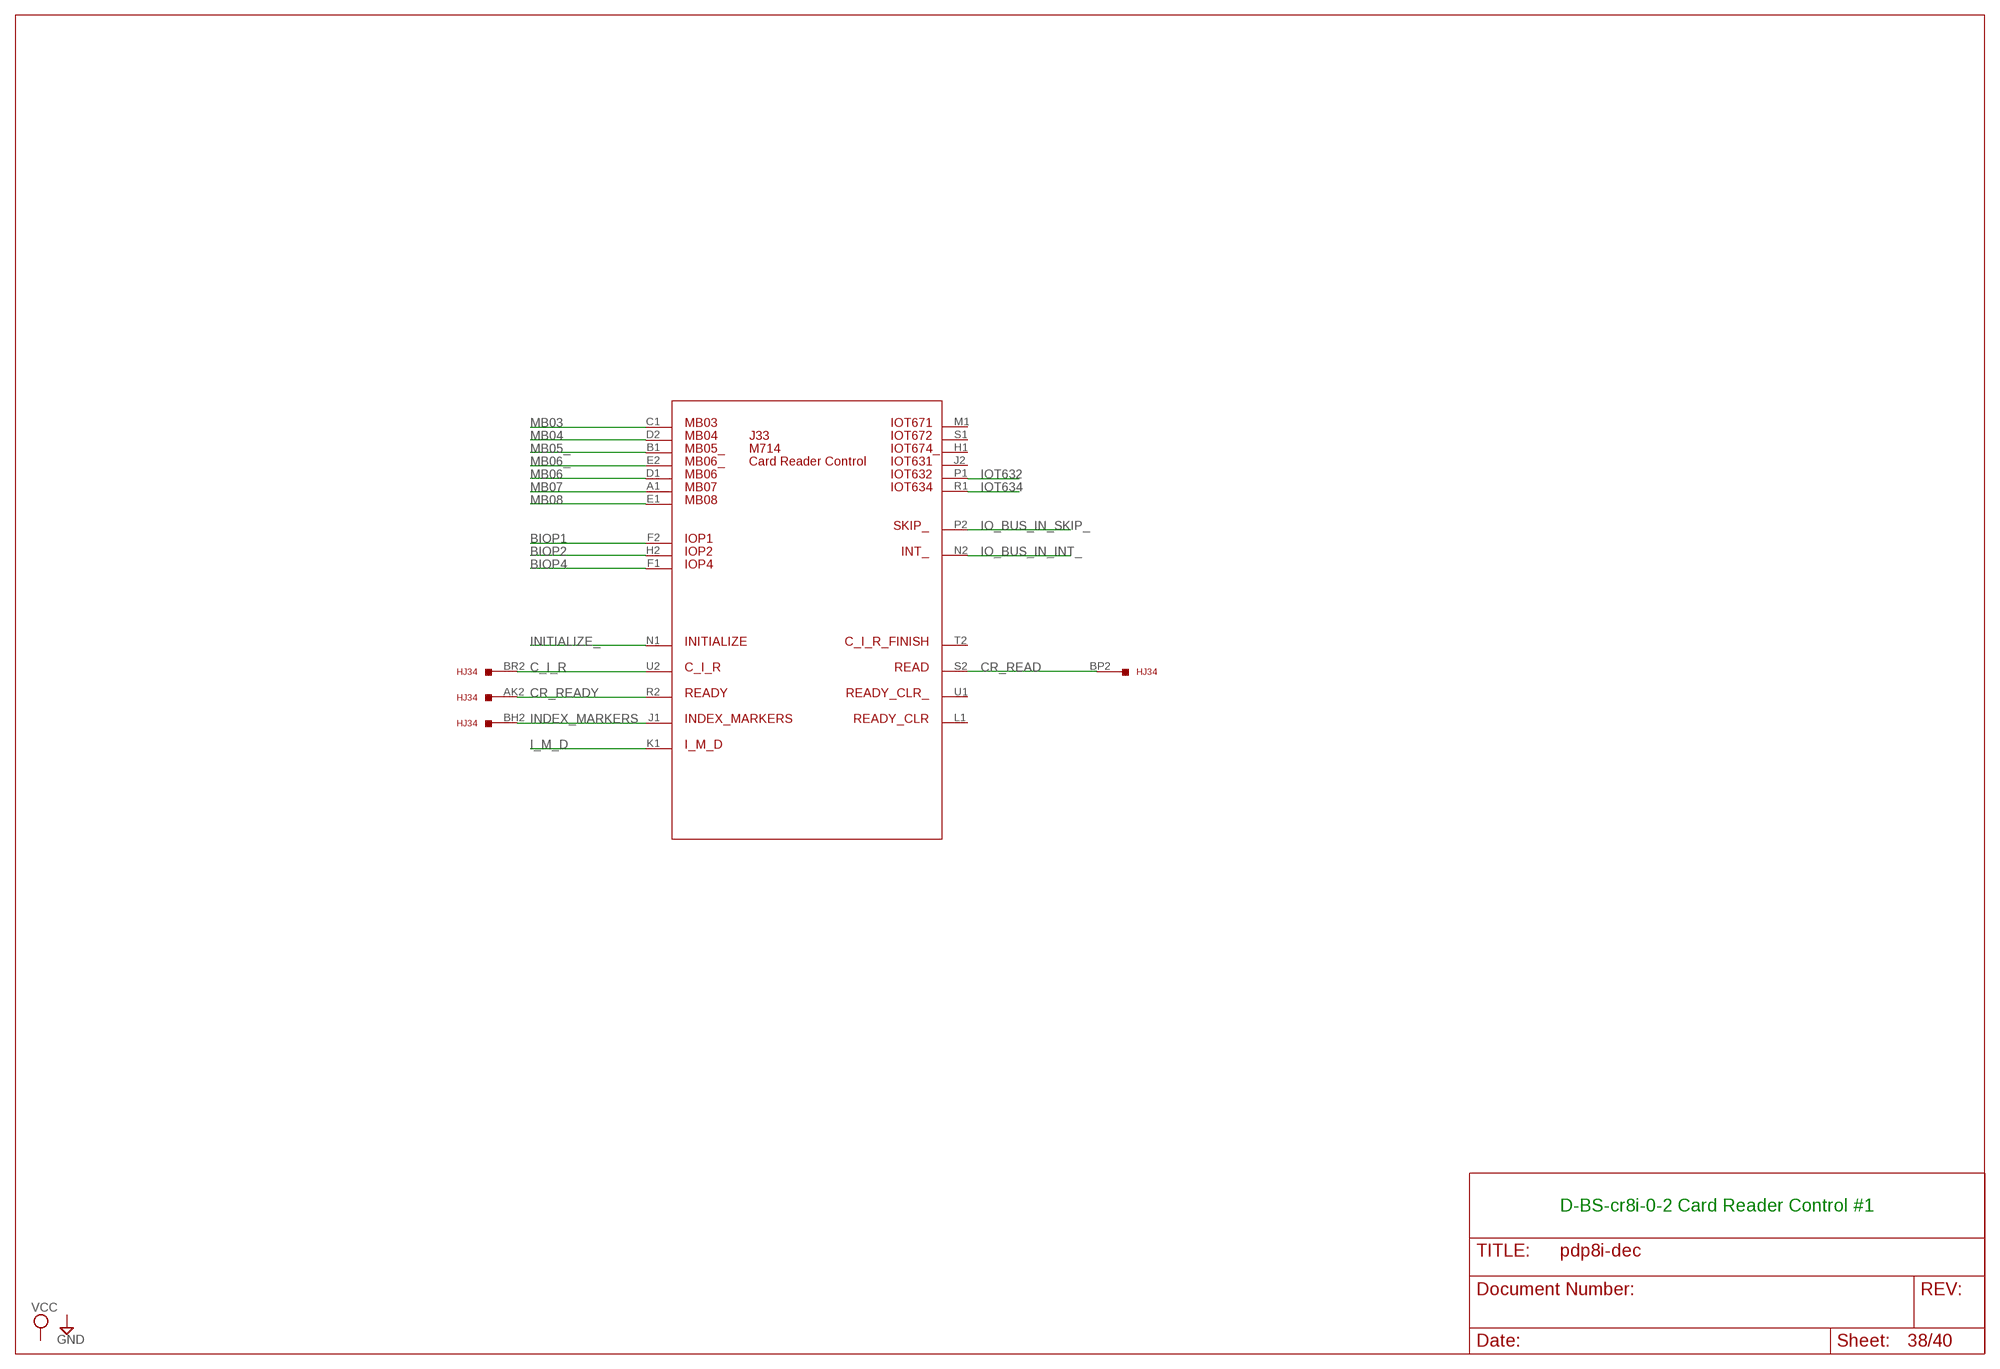
[diagram p38: schematic, sheet 38]
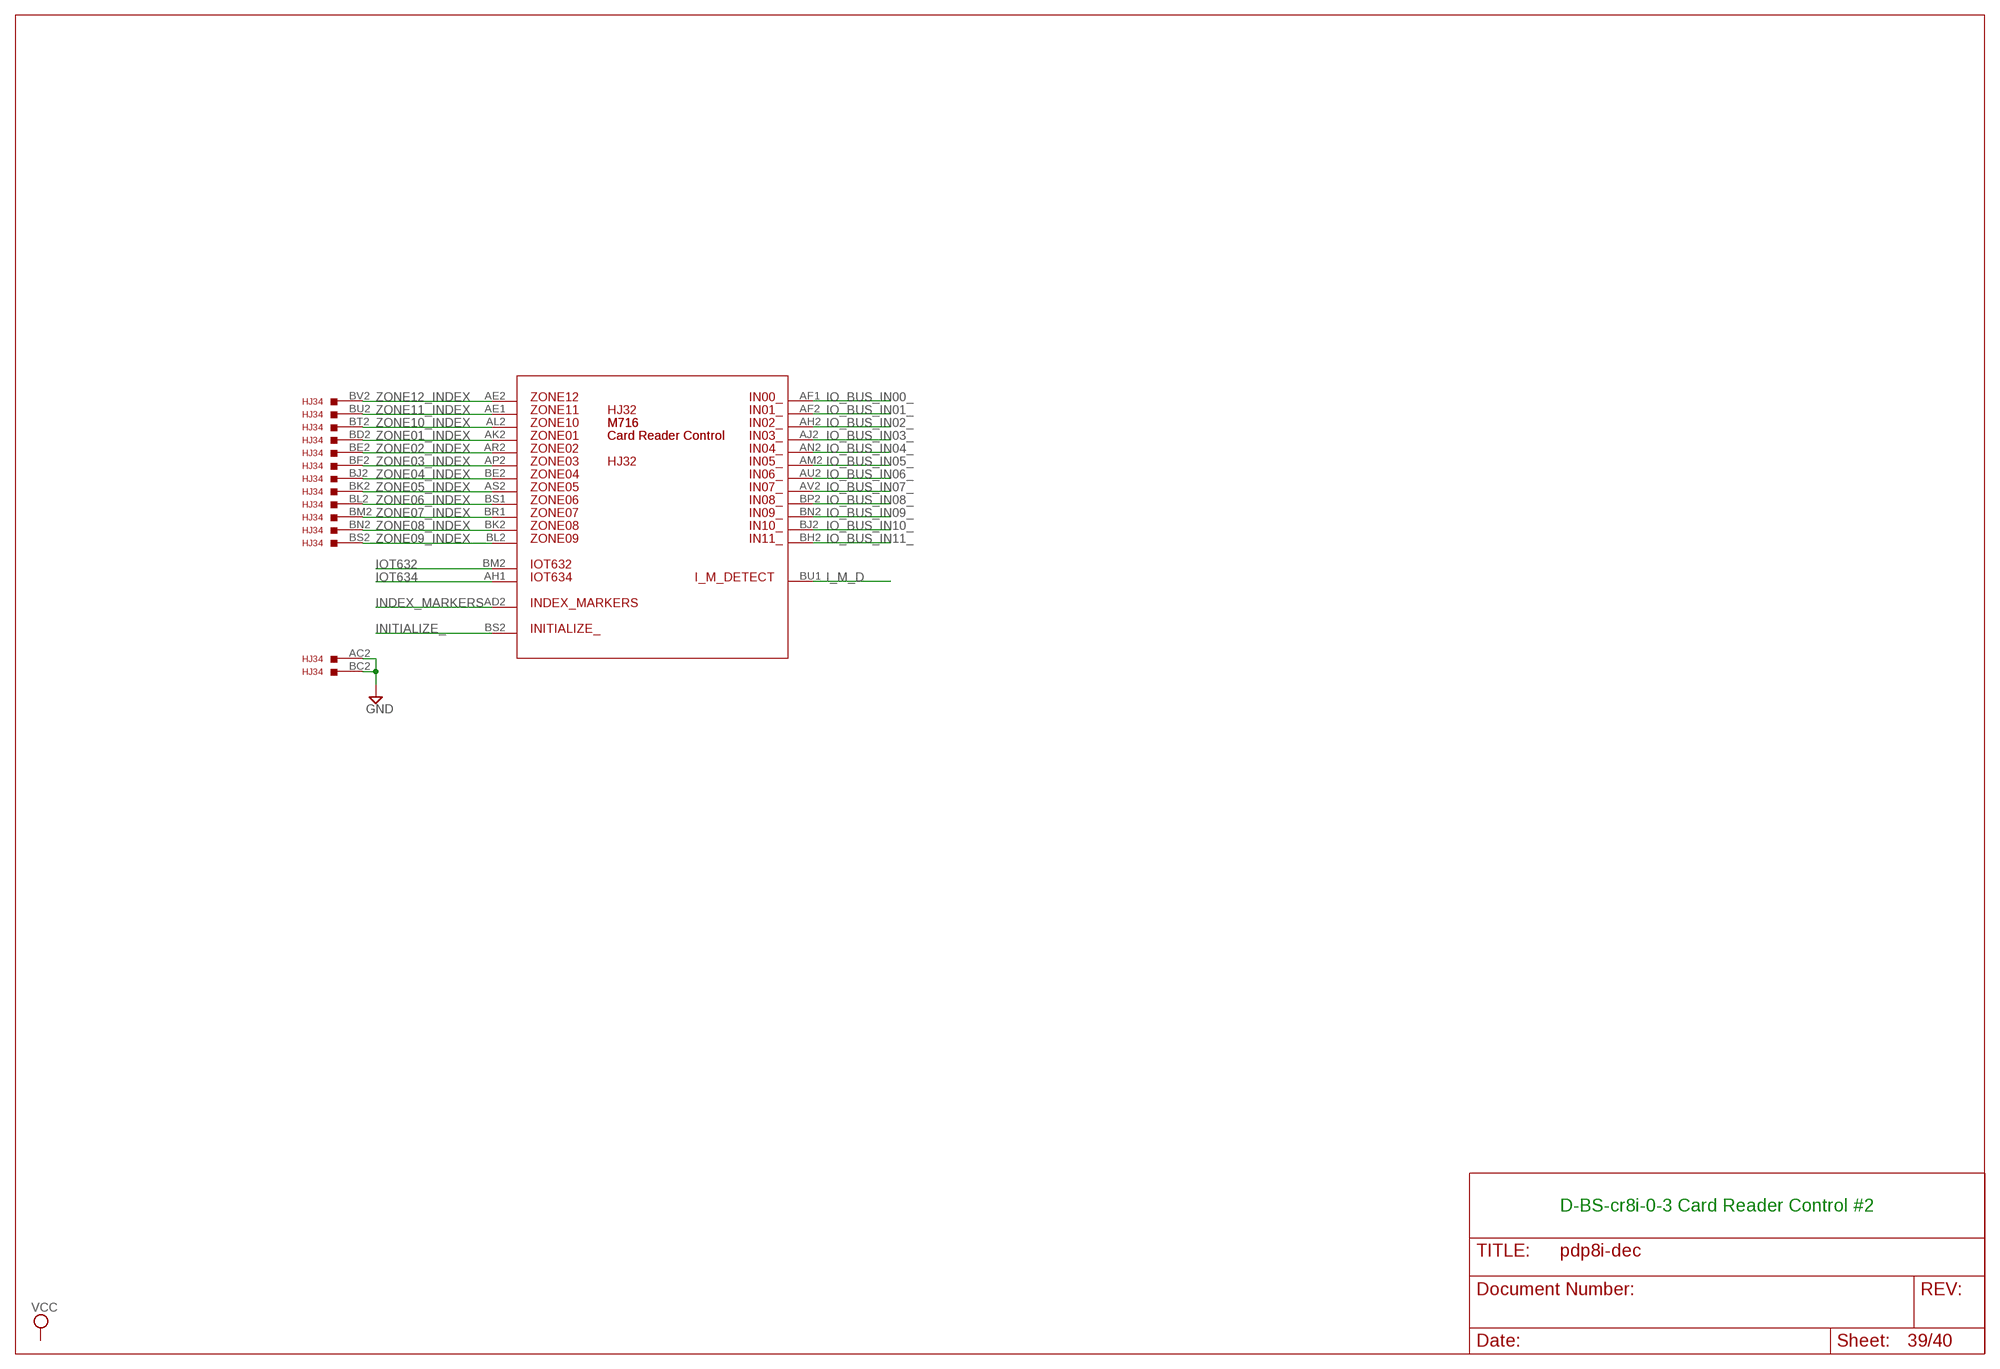
[diagram p39: schematic, sheet 39]
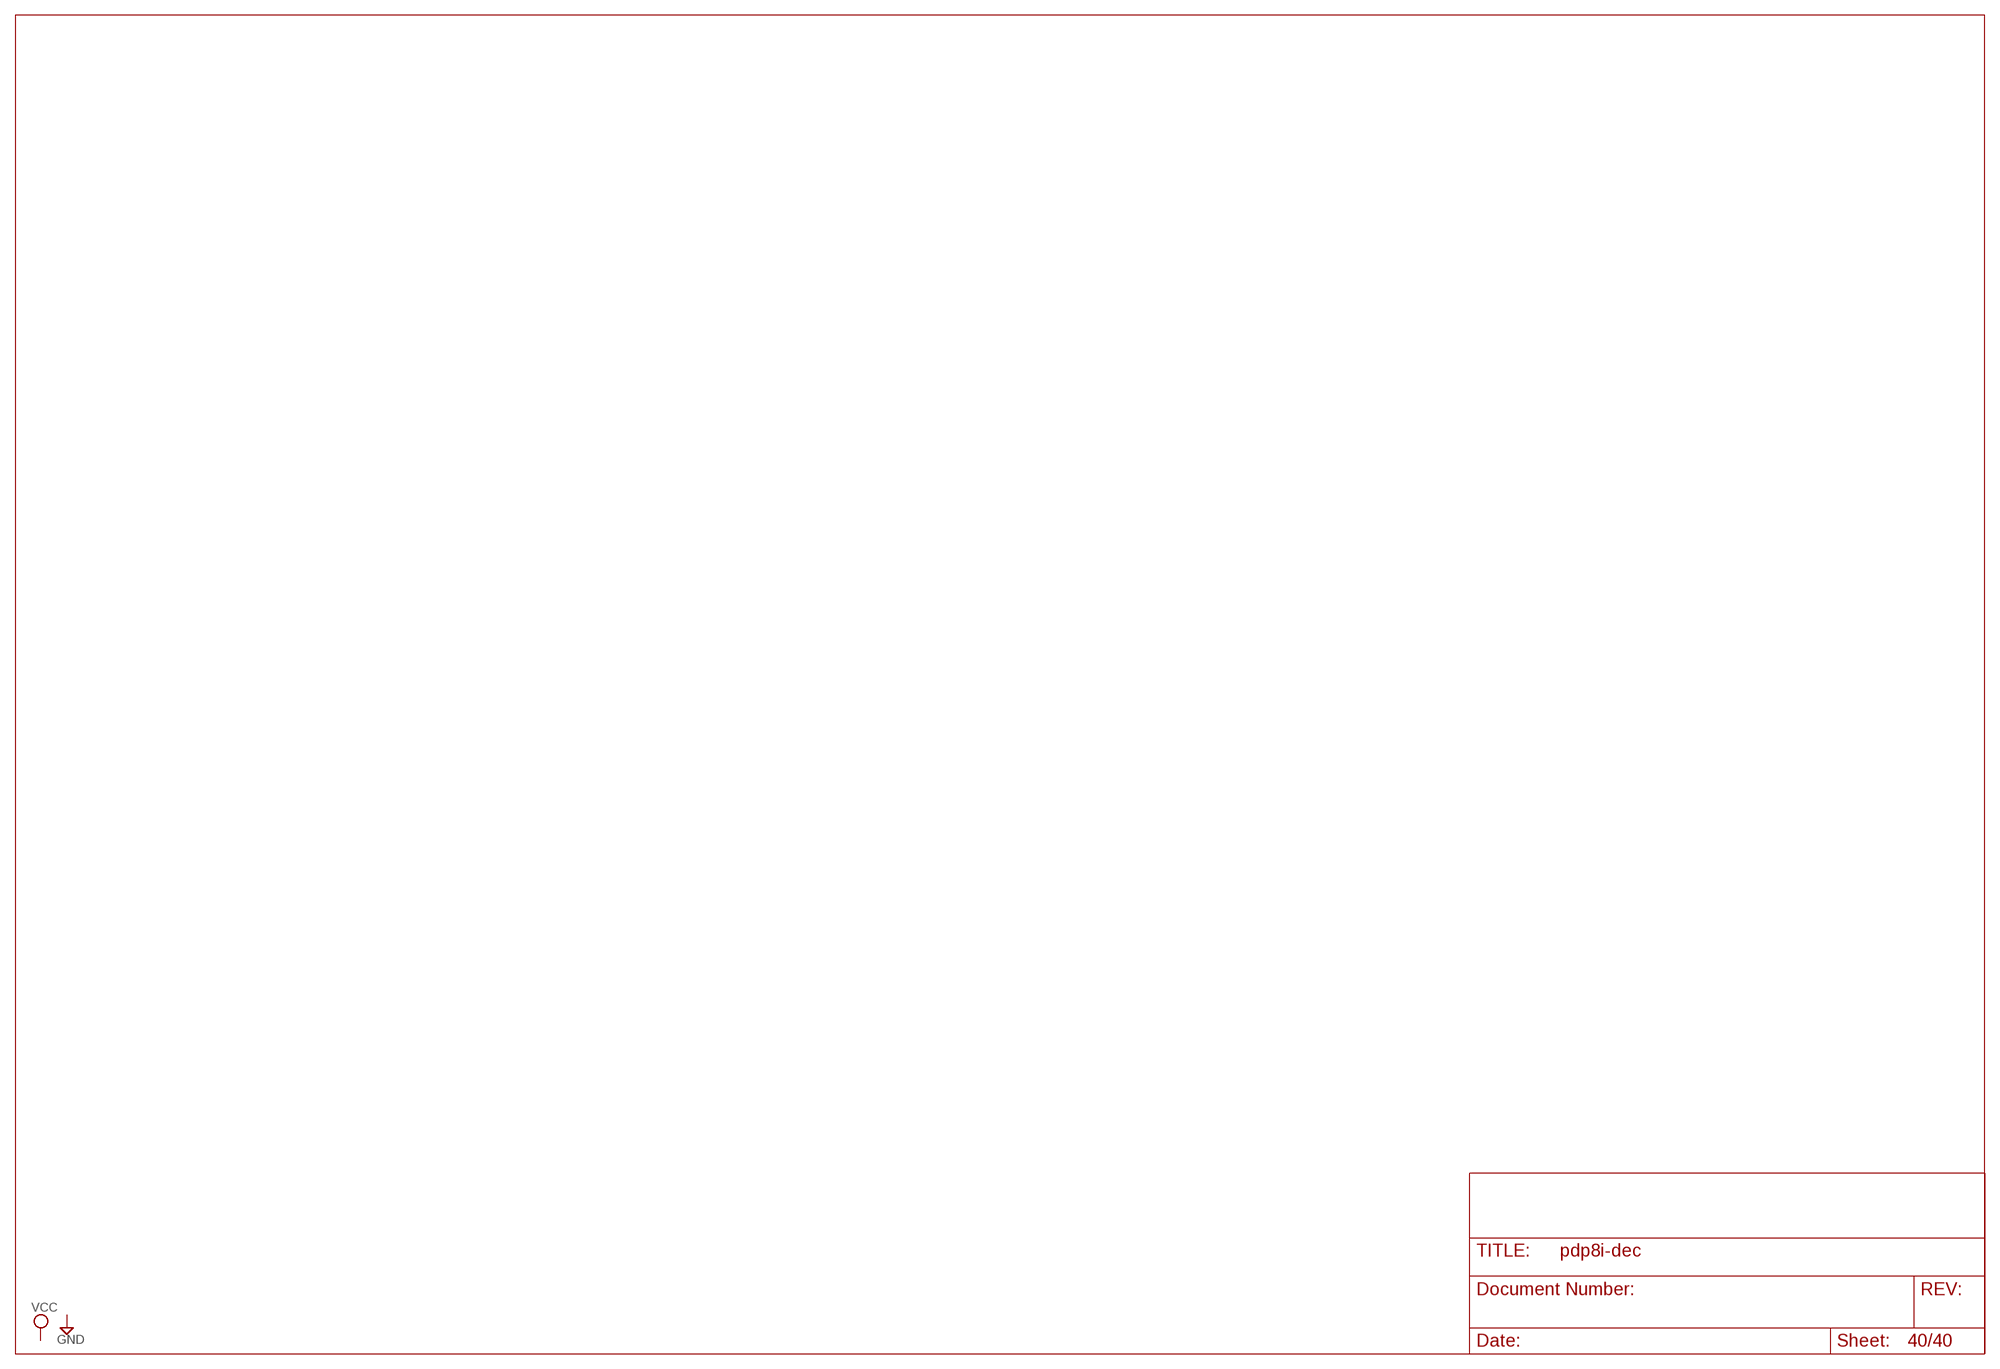
[diagram p40: schematic, sheet 40]

(export (version "E")
  (design (tool "Eeschema 10.0.6"))
  (components
    (comp (ref "EF01")
      (value "M706")
      (footprint "eagle-import:H807-2")
      (libsource (lib "eagle-import") (part "M706"))
    )
    (comp (ref "J12")
      (value "W076")
      (footprint "eagle-import:H807")
      (libsource (lib "eagle-import") (part "W076"))
    )
    (comp (ref "A09")
      (value "M162")
      (footprint "eagle-import:H807")
      (libsource (lib "eagle-import") (part "M162"))
    )
    (comp (ref "A10")
      (value "M162")
      (footprint "eagle-import:H807")
      (libsource (lib "eagle-import") (part "M162"))
    )
    (comp (ref "B07")
      (value "M115")
      (footprint "eagle-import:H807")
      (libsource (lib "eagle-import") (part "M115"))
    )
    (comp (ref "B09")
      (value "M113")
      (footprint "eagle-import:H807")
      (libsource (lib "eagle-import") (part "M113"))
    )
    (comp (ref "H05")
      (value "W011")
      (footprint "eagle-import:H807")
      (libsource (lib "eagle-import") (part "W011"))
    )
    (comp (ref "E27")
      (value "M160")
      (footprint "eagle-import:H807")
      (libsource (lib "eagle-import") (part "M160"))
    )
    (comp (ref "E31")
      (value "M617")
      (footprint "eagle-import:H807")
      (libsource (lib "eagle-import") (part "M617"))
    )
    (comp (ref "F11")
      (value "M117")
      (footprint "eagle-import:H807")
      (libsource (lib "eagle-import") (part "M117"))
    )
    (comp (ref "F24")
      (value "M117")
      (footprint "eagle-import:H807")
      (libsource (lib "eagle-import") (part "M117"))
    )
    (comp (ref "F25")
      (value "M113")
      (footprint "eagle-import:H807")
      (libsource (lib "eagle-import") (part "M113"))
    )
    (comp (ref "F26")
      (value "M115")
      (footprint "eagle-import:H807")
      (libsource (lib "eagle-import") (part "M115"))
    )
    (comp (ref "F27")
      (value "M117")
      (footprint "eagle-import:H807")
      (libsource (lib "eagle-import") (part "M117"))
    )
    (comp (ref "F28")
      (value "M115")
      (footprint "eagle-import:H807")
      (libsource (lib "eagle-import") (part "M115"))
    )
    (comp (ref "F32")
      (value "M113")
      (footprint "eagle-import:H807")
      (libsource (lib "eagle-import") (part "M113"))
    )
    (comp (ref "A21")
      (value "M310")
      (footprint "eagle-import:H807")
      (libsource (lib "eagle-import") (part "M310"))
    )
    (comp (ref "A22")
      (value "M310")
      (footprint "eagle-import:H807")
      (libsource (lib "eagle-import") (part "M310"))
    )
    (comp (ref "A23")
      (value "M310")
      (footprint "eagle-import:H807")
      (libsource (lib "eagle-import") (part "M310"))
    )
    (comp (ref "A24")
      (value "M310")
      (footprint "eagle-import:H807")
      (libsource (lib "eagle-import") (part "M310"))
    )
    (comp (ref "A38")
      (value "G624")
      (footprint "eagle-import:H807")
      (libsource (lib "eagle-import") (part "G624"))
    )
    (comp (ref "A39")
      (value "G624")
      (footprint "eagle-import:H807")
      (libsource (lib "eagle-import") (part "G624"))
    )
    (comp (ref "AB01")
      (value "G805")
      (footprint "eagle-import:H807-2")
      (libsource (lib "eagle-import") (part "G805"))
    )
    (comp (ref "AB02")
      (value "G826")
      (footprint "eagle-import:H807-2")
      (libsource (lib "eagle-import") (part "G826"))
    )
    (comp (ref "AB03")
      (value "G792")
      (footprint "eagle-import:H807-2")
      (libsource (lib "eagle-import") (part "G792"))
    )
    (comp (ref "AB35")
      (value "W025")
      (footprint "eagle-import:H807-2")
      (libsource (lib "eagle-import") (part "W025"))
    )
    (comp (ref "B21")
      (value "M113")
      (footprint "eagle-import:H807")
      (libsource (lib "eagle-import") (part "M113"))
    )
    (comp (ref "B22")
      (value "M216")
      (footprint "eagle-import:H807")
      (libsource (lib "eagle-import") (part "M206X"))
    )
    (comp (ref "B23")
      (value "M360")
      (footprint "eagle-import:H807")
      (libsource (lib "eagle-import") (part "M360"))
    )
    (comp (ref "B24")
      (value "M360")
      (footprint "eagle-import:H807")
      (libsource (lib "eagle-import") (part "M360"))
    )
    (comp (ref "B30")
      (value "M617")
      (footprint "eagle-import:H807")
      (libsource (lib "eagle-import") (part "M617"))
    )
    (comp (ref "B38")
      (value "G624")
      (footprint "eagle-import:H807")
      (libsource (lib "eagle-import") (part "G624"))
    )
    (comp (ref "B39")
      (value "G624")
      (footprint "eagle-import:H807")
      (libsource (lib "eagle-import") (part "G624"))
    )
    (comp (ref "C12")
      (value "M617")
      (footprint "eagle-import:H807")
      (libsource (lib "eagle-import") (part "M617"))
    )
    (comp (ref "C39")
      (value "G228")
      (footprint "eagle-import:H807")
      (libsource (lib "eagle-import") (part "G228"))
    )
    (comp (ref "D07")
      (value "M113")
      (footprint "eagle-import:H807")
      (libsource (lib "eagle-import") (part "M113"))
    )
    (comp (ref "D08")
      (value "M310")
      (footprint "eagle-import:H807")
      (libsource (lib "eagle-import") (part "M310"))
    )
    (comp (ref "D39")
      (value "G228")
      (footprint "eagle-import:H807")
      (libsource (lib "eagle-import") (part "G228"))
    )
    (comp (ref "E09")
      (value "M113")
      (footprint "eagle-import:H807")
      (libsource (lib "eagle-import") (part "M113"))
    )
    (comp (ref "E18")
      (value "M216")
      (footprint "eagle-import:H807")
      (libsource (lib "eagle-import") (part "M206X"))
    )
    (comp (ref "E24")
      (value "M113")
      (footprint "eagle-import:H807")
      (libsource (lib "eagle-import") (part "M113"))
    )
    (comp (ref "E25")
      (value "M115")
      (footprint "eagle-import:H807")
      (libsource (lib "eagle-import") (part "M115"))
    )
    (comp (ref "E26")
      (value "M160")
      (footprint "eagle-import:H807")
      (libsource (lib "eagle-import") (part "M160"))
    )
    (comp (ref "E28")
      (value "M160")
      (footprint "eagle-import:H807")
      (libsource (lib "eagle-import") (part "M160"))
    )
    (comp (ref "E32")
      (value "M617")
      (footprint "eagle-import:H807")
      (libsource (lib "eagle-import") (part "M617"))
    )
    (comp (ref "F23")
      (value "M117")
      (footprint "eagle-import:H807")
      (libsource (lib "eagle-import") (part "M117"))
    )
    (comp (ref "A40")
      (value "W077")
      (footprint "eagle-import:H807")
      (libsource (lib "eagle-import") (part "M916"))
    )
    (comp (ref "B40")
      (value "W077")
      (footprint "eagle-import:H807")
      (libsource (lib "eagle-import") (part "M916"))
    )
    (comp (ref "EF37")
      (value "M220")
      (footprint "eagle-import:H807-2")
      (libsource (lib "eagle-import") (part "M220"))
    )
    (comp (ref "EF38")
      (value "M220")
      (footprint "eagle-import:H807-2")
      (libsource (lib "eagle-import") (part "M220"))
    )
    (comp (ref "A30")
      (value "G021")
      (footprint "eagle-import:H807")
      (libsource (lib "eagle-import") (part "G021"))
    )
    (comp (ref "A31")
      (value "G021")
      (footprint "eagle-import:H807")
      (libsource (lib "eagle-import") (part "G021"))
    )
    (comp (ref "A32")
      (value "G021")
      (footprint "eagle-import:H807")
      (libsource (lib "eagle-import") (part "G021"))
    )
    (comp (ref "A33")
      (value "G021")
      (footprint "eagle-import:H807")
      (libsource (lib "eagle-import") (part "G021"))
    )
    (comp (ref "A36")
      (value "G228")
      (footprint "eagle-import:H807")
      (libsource (lib "eagle-import") (part "G228"))
    )
    (comp (ref "A37")
      (value "G228")
      (footprint "eagle-import:H807")
      (libsource (lib "eagle-import") (part "G228"))
    )
    (comp (ref "AB28")
      (value "W025")
      (footprint "eagle-import:H807-2")
      (libsource (lib "eagle-import") (part "W025"))
    )
    (comp (ref "AB29")
      (value "W025")
      (footprint "eagle-import:H807-2")
      (libsource (lib "eagle-import") (part "W025"))
    )
    (comp (ref "AB34")
      (value "W025")
      (footprint "eagle-import:H807-2")
      (libsource (lib "eagle-import") (part "W025"))
    )
    (comp (ref "B31")
      (value "G021")
      (footprint "eagle-import:H807")
      (libsource (lib "eagle-import") (part "G021"))
    )
    (comp (ref "B32")
      (value "G021")
      (footprint "eagle-import:H807")
      (libsource (lib "eagle-import") (part "G021"))
    )
    (comp (ref "B33")
      (value "G021")
      (footprint "eagle-import:H807")
      (libsource (lib "eagle-import") (part "G021"))
    )
    (comp (ref "B36")
      (value "G228")
      (footprint "eagle-import:H807")
      (libsource (lib "eagle-import") (part "G228"))
    )
    (comp (ref "B37")
      (value "G228")
      (footprint "eagle-import:H807")
      (libsource (lib "eagle-import") (part "G228"))
    )
    (comp (ref "H04")
      (value "W011")
      (footprint "eagle-import:H807")
      (libsource (lib "eagle-import") (part "W011"))
    )
    (comp (ref "D01")
      (value "W077")
      (footprint "eagle-import:H807")
      (libsource (lib "eagle-import") (part "W023"))
    )
    (comp (ref "HJ26")
      (value "M705")
      (footprint "eagle-import:H807-2")
      (libsource (lib "eagle-import") (part "M705"))
    )
    (comp (ref "HJ27")
      (value "M715")
      (footprint "eagle-import:H807-2")
      (libsource (lib "eagle-import") (part "M715"))
    )
    (comp (ref "EF35")
      (value "M220")
      (footprint "eagle-import:H807-2")
      (libsource (lib "eagle-import") (part "M220"))
    )
    (comp (ref "EF36")
      (value "M220")
      (footprint "eagle-import:H807-2")
      (libsource (lib "eagle-import") (part "M220"))
    )
    (comp (ref "A06")
      (value "M113")
      (footprint "eagle-import:H807")
      (libsource (lib "eagle-import") (part "M113"))
    )
    (comp (ref "D40")
      (value "M900")
      (footprint "eagle-import:H807")
      (libsource (lib "eagle-import") (part "M916"))
    )
    (comp (ref "E20")
      (value "M216")
      (footprint "eagle-import:H807")
      (libsource (lib "eagle-import") (part "M206X"))
    )
    (comp (ref "E21")
      (value "M115")
      (footprint "eagle-import:H807")
      (libsource (lib "eagle-import") (part "M115"))
    )
    (comp (ref "E22")
      (value "M113")
      (footprint "eagle-import:H807")
      (libsource (lib "eagle-import") (part "M113"))
    )
    (comp (ref "E23")
      (value "M216")
      (footprint "eagle-import:H807")
      (libsource (lib "eagle-import") (part "M206X"))
    )
    (comp (ref "F22")
      (value "M113")
      (footprint "eagle-import:H807")
      (libsource (lib "eagle-import") (part "M113"))
    )
    (comp (ref "F31")
      (value "M617")
      (footprint "eagle-import:H807")
      (libsource (lib "eagle-import") (part "M617"))
    )
    (comp (ref "C25")
      (value "G221")
      (footprint "eagle-import:H807")
      (libsource (lib "eagle-import") (part "G221"))
    )
    (comp (ref "C26")
      (value "G221")
      (footprint "eagle-import:H807")
      (libsource (lib "eagle-import") (part "G221"))
    )
    (comp (ref "CD27")
      (value "G610")
      (footprint "eagle-import:H807-2")
      (libsource (lib "eagle-import") (part "G610"))
    )
    (comp (ref "CD29")
      (value "G611")
      (footprint "eagle-import:H807-2")
      (libsource (lib "eagle-import") (part "G610"))
    )
    (comp (ref "D30")
      (value "G221")
      (footprint "eagle-import:H807")
      (libsource (lib "eagle-import") (part "G221"))
    )
    (comp (ref "D31")
      (value "G221")
      (footprint "eagle-import:H807")
      (libsource (lib "eagle-import") (part "G221"))
    )
    (comp (ref "E03")
      (value "EMPTY")
      (footprint "eagle-import:H807")
      (libsource (lib "eagle-import") (part "EMPTY"))
    )
    (comp (ref "E04")
      (value "EMPTY")
      (footprint "eagle-import:H807")
      (libsource (lib "eagle-import") (part "EMPTY"))
    )
    (comp (ref "E05")
      (value "EMPTY")
      (footprint "eagle-import:H807")
      (libsource (lib "eagle-import") (part "EMPTY"))
    )
    (comp (ref "E06")
      (value "EMPTY")
      (footprint "eagle-import:H807")
      (libsource (lib "eagle-import") (part "EMPTY"))
    )
    (comp (ref "E07")
      (value "EMPTY")
      (footprint "eagle-import:H807")
      (libsource (lib "eagle-import") (part "EMPTY"))
    )
    (comp (ref "E08")
      (value "EMPTY")
      (footprint "eagle-import:H807")
      (libsource (lib "eagle-import") (part "EMPTY"))
    )
    (comp (ref "EF10")
      (value "M700")
      (footprint "eagle-import:H807-2")
      (libsource (lib "eagle-import") (part "M700"))
    )
    (comp (ref "F04")
      (value "EMPTY")
      (footprint "eagle-import:H807")
      (libsource (lib "eagle-import") (part "EMPTY"))
    )
    (comp (ref "F05")
      (value "EMPTY")
      (footprint "eagle-import:H807")
      (libsource (lib "eagle-import") (part "EMPTY"))
    )
    (comp (ref "F06")
      (value "EMPTY")
      (footprint "eagle-import:H807")
      (libsource (lib "eagle-import") (part "EMPTY"))
    )
    (comp (ref "F07")
      (value "EMPTY")
      (footprint "eagle-import:H807")
      (libsource (lib "eagle-import") (part "EMPTY"))
    )
    (comp (ref "F20")
      (value "M113")
      (footprint "eagle-import:H807")
      (libsource (lib "eagle-import") (part "M113"))
    )
    (comp (ref "F21")
      (value "M113")
      (footprint "eagle-import:H807")
      (libsource (lib "eagle-import") (part "M113"))
    )
    (comp (ref "F29")
      (value "M113")
      (footprint "eagle-import:H807")
      (libsource (lib "eagle-import") (part "M113"))
    )
    (comp (ref "F30")
      (value "M617")
      (footprint "eagle-import:H807")
      (libsource (lib "eagle-import") (part "M617"))
    )
    (comp (ref "H06")
      (value "EMPTY")
      (footprint "eagle-import:H807")
      (libsource (lib "eagle-import") (part "EMPTY"))
    )
    (comp (ref "H21")
      (value "EMPTY")
      (footprint "eagle-import:H807")
      (libsource (lib "eagle-import") (part "EMPTY"))
    )
    (comp (ref "H22")
      (value "EMPTY")
      (footprint "eagle-import:H807")
      (libsource (lib "eagle-import") (part "EMPTY"))
    )
    (comp (ref "H33")
      (value "EMPTY")
      (footprint "eagle-import:H807")
      (libsource (lib "eagle-import") (part "EMPTY"))
    )
    (comp (ref "H35")
      (value "EMPTY")
      (footprint "eagle-import:H807")
      (libsource (lib "eagle-import") (part "EMPTY"))
    )
    (comp (ref "H36")
      (value "EMPTY")
      (footprint "eagle-import:H807")
      (libsource (lib "eagle-import") (part "EMPTY"))
    )
    (comp (ref "H37")
      (value "EMPTY")
      (footprint "eagle-import:H807")
      (libsource (lib "eagle-import") (part "EMPTY"))
    )
    (comp (ref "H38")
      (value "EMPTY")
      (footprint "eagle-import:H807")
      (libsource (lib "eagle-import") (part "EMPTY"))
    )
    (comp (ref "H39")
      (value "EMPTY")
      (footprint "eagle-import:H807")
      (libsource (lib "eagle-import") (part "EMPTY"))
    )
    (comp (ref "H40")
      (value "EMPTY")
      (footprint "eagle-import:H807")
      (libsource (lib "eagle-import") (part "EMPTY"))
    )
    (comp (ref "J11")
      (value "W011")
      (footprint "eagle-import:H807")
      (libsource (lib "eagle-import") (part "W011"))
    )
    (comp (ref "J21")
      (value "EMPTY")
      (footprint "eagle-import:H807")
      (libsource (lib "eagle-import") (part "EMPTY"))
    )
    (comp (ref "J22")
      (value "EMPTY")
      (footprint "eagle-import:H807")
      (libsource (lib "eagle-import") (part "EMPTY"))
    )
    (comp (ref "J35")
      (value "EMPTY")
      (footprint "eagle-import:H807")
      (libsource (lib "eagle-import") (part "EMPTY"))
    )
    (comp (ref "J36")
      (value "EMPTY")
      (footprint "eagle-import:H807")
      (libsource (lib "eagle-import") (part "EMPTY"))
    )
    (comp (ref "J37")
      (value "EMPTY")
      (footprint "eagle-import:H807")
      (libsource (lib "eagle-import") (part "EMPTY"))
    )
    (comp (ref "J38")
      (value "EMPTY")
      (footprint "eagle-import:H807")
      (libsource (lib "eagle-import") (part "EMPTY"))
    )
    (comp (ref "J39")
      (value "EMPTY")
      (footprint "eagle-import:H807")
      (libsource (lib "eagle-import") (part "EMPTY"))
    )
    (comp (ref "J40")
      (value "EMPTY")
      (footprint "eagle-import:H807")
      (libsource (lib "eagle-import") (part "EMPTY"))
    )
    (comp (ref "C28")
      (value "H807")
      (footprint "eagle-import:H807")
      (libsource (lib "eagle-import") (part "H807"))
    )
    (comp (ref "C30")
      (value "G221")
      (footprint "eagle-import:H807")
      (libsource (lib "eagle-import") (part "G221"))
    )
    (comp (ref "C31")
      (value "G221")
      (footprint "eagle-import:H807")
      (libsource (lib "eagle-import") (part "G221"))
    )
    (comp (ref "D25")
      (value "G221")
      (footprint "eagle-import:H807")
      (libsource (lib "eagle-import") (part "G221"))
    )
    (comp (ref "D26")
      (value "G221")
      (footprint "eagle-import:H807")
      (libsource (lib "eagle-import") (part "G221"))
    )
    (comp (ref "D28")
      (value "H807")
      (footprint "eagle-import:H807")
      (libsource (lib "eagle-import") (part "H807"))
    )
    (comp (ref "C35")
      (value "H807")
      (footprint "eagle-import:H807")
      (libsource (lib "eagle-import") (part "H807"))
    )
    (comp (ref "C37")
      (value "G221")
      (footprint "eagle-import:H807")
      (libsource (lib "eagle-import") (part "G221"))
    )
    (comp (ref "C38")
      (value "G221")
      (footprint "eagle-import:H807")
      (libsource (lib "eagle-import") (part "G221"))
    )
    (comp (ref "CD34")
      (value "G610")
      (footprint "eagle-import:H807-2")
      (libsource (lib "eagle-import") (part "G610"))
    )
    (comp (ref "CD36")
      (value "G611")
      (footprint "eagle-import:H807-2")
      (libsource (lib "eagle-import") (part "G610"))
    )
    (comp (ref "D32")
      (value "G221")
      (footprint "eagle-import:H807")
      (libsource (lib "eagle-import") (part "G221"))
    )
    (comp (ref "D33")
      (value "G221")
      (footprint "eagle-import:H807")
      (libsource (lib "eagle-import") (part "G221"))
    )
    (comp (ref "D35")
      (value "H807")
      (footprint "eagle-import:H807")
      (libsource (lib "eagle-import") (part "H807"))
    )
    (comp (ref "C40")
      (value "M900")
      (footprint "eagle-import:H807")
      (libsource (lib "eagle-import") (part "M916"))
    )
    (comp (ref "E33")
      (value "M216")
      (footprint "eagle-import:H807")
      (libsource (lib "eagle-import") (part "M206X"))
    )
    (comp (ref "E40")
      (value "M900")
      (footprint "eagle-import:H807")
      (libsource (lib "eagle-import") (part "M916"))
    )
    (comp (ref "EF34")
      (value "M220")
      (footprint "eagle-import:H807-2")
      (libsource (lib "eagle-import") (part "M220"))
    )
    (comp (ref "EF39")
      (value "M220")
      (footprint "eagle-import:H807-2")
      (libsource (lib "eagle-import") (part "M220"))
    )
    (comp (ref "F33")
      (value "M160")
      (footprint "eagle-import:H807")
      (libsource (lib "eagle-import") (part "M160"))
    )
    (comp (ref "F40")
      (value "M900")
      (footprint "eagle-import:H807")
      (libsource (lib "eagle-import") (part "M916"))
    )
    (comp (ref "C14")
      (value "M113")
      (footprint "eagle-import:H807")
      (libsource (lib "eagle-import") (part "M113"))
    )
    (comp (ref "C15")
      (value "M113")
      (footprint "eagle-import:H807")
      (libsource (lib "eagle-import") (part "M113"))
    )
    (comp (ref "C16")
      (value "M113")
      (footprint "eagle-import:H807")
      (libsource (lib "eagle-import") (part "M113"))
    )
    (comp (ref "C17")
      (value "M113")
      (footprint "eagle-import:H807")
      (libsource (lib "eagle-import") (part "M113"))
    )
    (comp (ref "C18")
      (value "M113")
      (footprint "eagle-import:H807")
      (libsource (lib "eagle-import") (part "M113"))
    )
    (comp (ref "C19")
      (value "M115")
      (footprint "eagle-import:H807")
      (libsource (lib "eagle-import") (part "M115"))
    )
    (comp (ref "C20")
      (value "M115")
      (footprint "eagle-import:H807")
      (libsource (lib "eagle-import") (part "M115"))
    )
    (comp (ref "C21")
      (value "M115")
      (footprint "eagle-import:H807")
      (libsource (lib "eagle-import") (part "M115"))
    )
    (comp (ref "C22")
      (value "M216")
      (footprint "eagle-import:H807")
      (libsource (lib "eagle-import") (part "M216"))
    )
    (comp (ref "C23")
      (value "M216")
      (footprint "eagle-import:H807")
      (libsource (lib "eagle-import") (part "M216"))
    )
    (comp (ref "C24")
      (value "M216")
      (footprint "eagle-import:H807")
      (libsource (lib "eagle-import") (part "M216"))
    )
    (comp (ref "D12")
      (value "M113")
      (footprint "eagle-import:H807")
      (libsource (lib "eagle-import") (part "M113"))
    )
    (comp (ref "D19")
      (value "M115")
      (footprint "eagle-import:H807")
      (libsource (lib "eagle-import") (part "M115"))
    )
    (comp (ref "D22")
      (value "M617")
      (footprint "eagle-import:H807")
      (libsource (lib "eagle-import") (part "M617"))
    )
    (comp (ref "D23")
      (value "M160")
      (footprint "eagle-import:H807")
      (libsource (lib "eagle-import") (part "M160"))
    )
    (comp (ref "A07")
      (value "M162")
      (footprint "eagle-import:H807")
      (libsource (lib "eagle-import") (part "M162"))
    )
    (comp (ref "A08")
      (value "M162")
      (footprint "eagle-import:H807")
      (libsource (lib "eagle-import") (part "M162"))
    )
    (comp (ref "B08")
      (value "M113")
      (footprint "eagle-import:H807")
      (libsource (lib "eagle-import") (part "M113"))
    )
    (comp (ref "D03")
      (value "W023")
      (footprint "eagle-import:H807")
      (libsource (lib "eagle-import") (part "W023"))
    )
    (comp (ref "HJ23")
      (value "M701")
      (footprint "eagle-import:H807-2")
      (libsource (lib "eagle-import") (part "M701"))
    )
    (comp (ref "HJ24")
      (value "A607")
      (footprint "eagle-import:H807-2")
      (libsource (lib "eagle-import") (part "A607"))
    )
    (comp (ref "HJ25")
      (value "A607")
      (footprint "eagle-import:H807-2")
      (libsource (lib "eagle-import") (part "A607"))
    )
    (comp (ref "C13")
      (value "M310")
      (footprint "eagle-import:H807")
      (libsource (lib "eagle-import") (part "M310"))
    )
    (comp (ref "D13")
      (value "M113")
      (footprint "eagle-import:H807")
      (libsource (lib "eagle-import") (part "M113"))
    )
    (comp (ref "D14")
      (value "M113")
      (footprint "eagle-import:H807")
      (libsource (lib "eagle-import") (part "M113"))
    )
    (comp (ref "D15")
      (value "M113")
      (footprint "eagle-import:H807")
      (libsource (lib "eagle-import") (part "M113"))
    )
    (comp (ref "D16")
      (value "M113")
      (footprint "eagle-import:H807")
      (libsource (lib "eagle-import") (part "M113"))
    )
    (comp (ref "D17")
      (value "M115")
      (footprint "eagle-import:H807")
      (libsource (lib "eagle-import") (part "M115"))
    )
    (comp (ref "D18")
      (value "M115")
      (footprint "eagle-import:H807")
      (libsource (lib "eagle-import") (part "M115"))
    )
    (comp (ref "D20")
      (value "M117")
      (footprint "eagle-import:H807")
      (libsource (lib "eagle-import") (part "M117"))
    )
    (comp (ref "D21")
      (value "M117")
      (footprint "eagle-import:H807")
      (libsource (lib "eagle-import") (part "M117"))
    )
    (comp (ref "D24")
      (value "M216")
      (footprint "eagle-import:H807")
      (libsource (lib "eagle-import") (part "M216"))
    )
    (comp (ref "C32")
      (value "G221")
      (footprint "eagle-import:H807")
      (libsource (lib "eagle-import") (part "G221"))
    )
    (comp (ref "C33")
      (value "G221")
      (footprint "eagle-import:H807")
      (libsource (lib "eagle-import") (part "G221"))
    )
    (comp (ref "D37")
      (value "G221")
      (footprint "eagle-import:H807")
      (libsource (lib "eagle-import") (part "G221"))
    )
    (comp (ref "D38")
      (value "G221")
      (footprint "eagle-import:H807")
      (libsource (lib "eagle-import") (part "G221"))
    )
    (comp (ref "A05")
      (value "M113")
      (footprint "eagle-import:H807")
      (libsource (lib "eagle-import") (part "M113"))
    )
    (comp (ref "B04")
      (value "M115")
      (footprint "eagle-import:H807")
      (libsource (lib "eagle-import") (part "M115"))
    )
    (comp (ref "B05")
      (value "M216")
      (footprint "eagle-import:H807")
      (libsource (lib "eagle-import") (part "M216"))
    )
    (comp (ref "B06")
      (value "M113")
      (footprint "eagle-import:H807")
      (libsource (lib "eagle-import") (part "M113"))
    )
    (comp (ref "A11")
      (value "M113")
      (footprint "eagle-import:H807")
      (libsource (lib "eagle-import") (part "M113"))
    )
    (comp (ref "A12")
      (value "M113")
      (footprint "eagle-import:H807")
      (libsource (lib "eagle-import") (part "M113"))
    )
    (comp (ref "A13")
      (value "M113")
      (footprint "eagle-import:H807")
      (libsource (lib "eagle-import") (part "M113"))
    )
    (comp (ref "A14")
      (value "M113")
      (footprint "eagle-import:H807")
      (libsource (lib "eagle-import") (part "M113"))
    )
    (comp (ref "A15")
      (value "M113")
      (footprint "eagle-import:H807")
      (libsource (lib "eagle-import") (part "M113"))
    )
    (comp (ref "A16")
      (value "M113")
      (footprint "eagle-import:H807")
      (libsource (lib "eagle-import") (part "M113"))
    )
    (comp (ref "A17")
      (value "M113")
      (footprint "eagle-import:H807")
      (libsource (lib "eagle-import") (part "M113"))
    )
    (comp (ref "A18")
      (value "M113")
      (footprint "eagle-import:H807")
      (libsource (lib "eagle-import") (part "M113"))
    )
    (comp (ref "A19")
      (value "M113")
      (footprint "eagle-import:H807")
      (libsource (lib "eagle-import") (part "M113"))
    )
    (comp (ref "A20")
      (value "M115")
      (footprint "eagle-import:H807")
      (libsource (lib "eagle-import") (part "M115"))
    )
    (comp (ref "B16")
      (value "M617")
      (footprint "eagle-import:H807")
      (libsource (lib "eagle-import") (part "M617"))
    )
    (comp (ref "B17")
      (value "M216")
      (footprint "eagle-import:H807")
      (libsource (lib "eagle-import") (part "M216"))
    )
    (comp (ref "B18")
      (value "M216")
      (footprint "eagle-import:H807")
      (libsource (lib "eagle-import") (part "M216"))
    )
    (comp (ref "B20")
      (value "M115")
      (footprint "eagle-import:H807")
      (libsource (lib "eagle-import") (part "M115"))
    )
    (comp (ref "F09")
      (value "M119")
      (footprint "eagle-import:H807")
      (libsource (lib "eagle-import") (part "M119"))
    )
    (comp (ref "E11")
      (value "M113")
      (footprint "eagle-import:H807")
      (libsource (lib "eagle-import") (part "M113"))
    )
    (comp (ref "E14")
      (value "M115")
      (footprint "eagle-import:H807")
      (libsource (lib "eagle-import") (part "M115"))
    )
    (comp (ref "E29")
      (value "M160")
      (footprint "eagle-import:H807")
      (libsource (lib "eagle-import") (part "M160"))
    )
    (comp (ref "E30")
      (value "M160")
      (footprint "eagle-import:H807")
      (libsource (lib "eagle-import") (part "M160"))
    )
    (comp (ref "HJ32")
      (value "M716")
      (footprint "eagle-import:H807-2")
      (libsource (lib "eagle-import") (part "M716"))
    )
    (comp (ref "HJ34")
      (value "W991")
      (footprint "eagle-import:H807-2")
      (libsource (lib "eagle-import") (part "W991"))
    )
    (comp (ref "H30")
      (value "M708")
      (footprint "eagle-import:H807")
      (libsource (lib "eagle-import") (part "M708"))
    )
    (comp (ref "HJ31")
      (value "M709")
      (footprint "eagle-import:H807-2")
      (libsource (lib "eagle-import") (part "M709"))
    )
    (comp (ref "J30")
      (value "M401/M405/M501")
      (footprint "eagle-import:H807")
      (libsource (lib "eagle-import") (part "M501"))
    )
    (comp (ref "E12")
      (value "M113")
      (footprint "eagle-import:H807")
      (libsource (lib "eagle-import") (part "M113"))
    )
    (comp (ref "E13")
      (value "M160")
      (footprint "eagle-import:H807")
      (libsource (lib "eagle-import") (part "M160"))
    )
    (comp (ref "E15")
      (value "M113")
      (footprint "eagle-import:H807")
      (libsource (lib "eagle-import") (part "M113"))
    )
    (comp (ref "E16")
      (value "M310")
      (footprint "eagle-import:H807")
      (libsource (lib "eagle-import") (part "M310"))
    )
    (comp (ref "E17")
      (value "M310")
      (footprint "eagle-import:H807")
      (libsource (lib "eagle-import") (part "M310"))
    )
    (comp (ref "E19")
      (value "M216")
      (footprint "eagle-import:H807")
      (libsource (lib "eagle-import") (part "M206X"))
    )
    (comp (ref "F08")
      (value "M660")
      (footprint "eagle-import:H807")
      (libsource (lib "eagle-import") (part "M660"))
    )
    (comp (ref "F12")
      (value "M310")
      (footprint "eagle-import:H807")
      (libsource (lib "eagle-import") (part "M310"))
    )
    (comp (ref "F13")
      (value "M310")
      (footprint "eagle-import:H807")
      (libsource (lib "eagle-import") (part "M310"))
    )
    (comp (ref "F14")
      (value "M310")
      (footprint "eagle-import:H807")
      (libsource (lib "eagle-import") (part "M310"))
    )
    (comp (ref "F15")
      (value "M310")
      (footprint "eagle-import:H807")
      (libsource (lib "eagle-import") (part "M310"))
    )
    (comp (ref "F16")
      (value "M310")
      (footprint "eagle-import:H807")
      (libsource (lib "eagle-import") (part "M310"))
    )
    (comp (ref "F17")
      (value "M310")
      (footprint "eagle-import:H807")
      (libsource (lib "eagle-import") (part "M310"))
    )
    (comp (ref "F18")
      (value "M310")
      (footprint "eagle-import:H807")
      (libsource (lib "eagle-import") (part "M310"))
    )
    (comp (ref "F19")
      (value "M117")
      (footprint "eagle-import:H807")
      (libsource (lib "eagle-import") (part "M117"))
    )
    (comp (ref "EF02")
      (value "M707")
      (footprint "eagle-import:H807-2")
      (libsource (lib "eagle-import") (part "M707"))
    )
    (comp (ref "F03")
      (value "M452")
      (footprint "eagle-import:H807")
      (libsource (lib "eagle-import") (part "M452"))
    )
    (comp (ref "A25")
      (value "G624")
      (footprint "eagle-import:H807")
      (libsource (lib "eagle-import") (part "G624"))
    )
    (comp (ref "A26")
      (value "G624")
      (footprint "eagle-import:H807")
      (libsource (lib "eagle-import") (part "G624"))
    )
    (comp (ref "A27")
      (value "G228")
      (footprint "eagle-import:H807")
      (libsource (lib "eagle-import") (part "G228"))
    )
    (comp (ref "B25")
      (value "G624")
      (footprint "eagle-import:H807")
      (libsource (lib "eagle-import") (part "G624"))
    )
    (comp (ref "B26")
      (value "G228")
      (footprint "eagle-import:H807")
      (libsource (lib "eagle-import") (part "G228"))
    )
    (comp (ref "B27")
      (value "G228")
      (footprint "eagle-import:H807")
      (libsource (lib "eagle-import") (part "G228"))
    )
    (comp (ref "J33")
      (value "M714")
      (footprint "eagle-import:H807")
      (libsource (lib "eagle-import") (part "M714"))
    )
    (comp (ref "A04")
      (value "M703")
      (footprint "eagle-import:H807")
      (libsource (lib "eagle-import") (part "M703"))
    )
    (comp (ref "C07")
      (value "M661")
      (footprint "eagle-import:H807")
      (libsource (lib "eagle-import") (part "M661"))
    )
    (comp (ref "C08")
      (value "M660")
      (footprint "eagle-import:H807")
      (libsource (lib "eagle-import") (part "M660"))
    )
    (comp (ref "C09")
      (value "M113")
      (footprint "eagle-import:H807")
      (libsource (lib "eagle-import") (part "M113"))
    )
    (comp (ref "C10")
      (value "M113")
      (footprint "eagle-import:H807")
      (libsource (lib "eagle-import") (part "M113"))
    )
    (comp (ref "C11")
      (value "M115")
      (footprint "eagle-import:H807")
      (libsource (lib "eagle-import") (part "M115"))
    )
    (comp (ref "D04")
      (value "W011")
      (footprint "eagle-import:H807")
      (libsource (lib "eagle-import") (part "W011"))
    )
    (comp (ref "D05")
      (value "M516")
      (footprint "eagle-import:H807")
      (libsource (lib "eagle-import") (part "M516"))
    )
    (comp (ref "D09")
      (value "M115")
      (footprint "eagle-import:H807")
      (libsource (lib "eagle-import") (part "M115"))
    )
    (comp (ref "D10")
      (value "M117")
      (footprint "eagle-import:H807")
      (libsource (lib "eagle-import") (part "M117"))
    )
    (comp (ref "D11")
      (value "M216")
      (footprint "eagle-import:H807")
      (libsource (lib "eagle-import") (part "M216"))
    )
    (comp (ref "D02")
      (value "W023")
      (footprint "eagle-import:H807")
      (libsource (lib "eagle-import") (part "W023"))
    )
    (comp (ref "HJ29")
      (value "M704")
      (footprint "eagle-import:H807-2")
      (libsource (lib "eagle-import") (part "M704"))
    )
    (comp (ref "C01")
      (value "W023")
      (footprint "eagle-import:H807")
      (libsource (lib "eagle-import") (part "W023"))
    )
    (comp (ref "C02")
      (value "M040")
      (footprint "eagle-import:H807")
      (libsource (lib "eagle-import") (part "M040"))
    )
    (comp (ref "C03")
      (value "M040")
      (footprint "eagle-import:H807")
      (libsource (lib "eagle-import") (part "M040"))
    )
    (comp (ref "C04")
      (value "M040")
      (footprint "eagle-import:H807")
      (libsource (lib "eagle-import") (part "M040"))
    )
    (comp (ref "C05")
      (value "M040")
      (footprint "eagle-import:H807")
      (libsource (lib "eagle-import") (part "M040"))
    )
    (comp (ref "C06")
      (value "M040")
      (footprint "eagle-import:H807")
      (libsource (lib "eagle-import") (part "M040"))
    )
    (comp (ref "HJ28")
      (value "M710")
      (footprint "eagle-import:H807-2")
      (libsource (lib "eagle-import") (part "M710"))
    )
    (comp (ref "H07")
      (value "M650")
      (footprint "eagle-import:H807")
      (libsource (lib "eagle-import") (part "M650"))
    )
    (comp (ref "H08")
      (value "M650")
      (footprint "eagle-import:H807")
      (libsource (lib "eagle-import") (part "M650"))
    )
    (comp (ref "H09")
      (value "M650")
      (footprint "eagle-import:H807")
      (libsource (lib "eagle-import") (part "M650"))
    )
    (comp (ref "H10")
      (value "M650")
      (footprint "eagle-import:H807")
      (libsource (lib "eagle-import") (part "M650"))
    )
    (comp (ref "H11")
      (value "M650")
      (footprint "eagle-import:H807")
      (libsource (lib "eagle-import") (part "M650"))
    )
    (comp (ref "H12")
      (value "M650")
      (footprint "eagle-import:H807")
      (libsource (lib "eagle-import") (part "M650"))
    )
    (comp (ref "H13")
      (value "M650")
      (footprint "eagle-import:H807")
      (libsource (lib "eagle-import") (part "M650"))
    )
    (comp (ref "H14")
      (value "M650")
      (footprint "eagle-import:H807")
      (libsource (lib "eagle-import") (part "M650"))
    )
    (comp (ref "H15")
      (value "M650")
      (footprint "eagle-import:H807")
      (libsource (lib "eagle-import") (part "M650"))
    )
    (comp (ref "H16")
      (value "M650")
      (footprint "eagle-import:H807")
      (libsource (lib "eagle-import") (part "M650"))
    )
    (comp (ref "H17")
      (value "M650")
      (footprint "eagle-import:H807")
      (libsource (lib "eagle-import") (part "M650"))
    )
    (comp (ref "H18")
      (value "M650")
      (footprint "eagle-import:H807")
      (libsource (lib "eagle-import") (part "M650"))
    )
    (comp (ref "H19")
      (value "M650")
      (footprint "eagle-import:H807")
      (libsource (lib "eagle-import") (part "M650"))
    )
    (comp (ref "H20")
      (value "M650")
      (footprint "eagle-import:H807")
      (libsource (lib "eagle-import") (part "M650"))
    )
    (comp (ref "J01")
      (value "W011")
      (footprint "eagle-import:H807")
      (libsource (lib "eagle-import") (part "W011"))
    )
    (comp (ref "J02")
      (value "W011")
      (footprint "eagle-import:H807")
      (libsource (lib "eagle-import") (part "W011"))
    )
    (comp (ref "J03")
      (value "W011")
      (footprint "eagle-import:H807")
      (libsource (lib "eagle-import") (part "W011"))
    )
    (comp (ref "J04")
      (value "W011")
      (footprint "eagle-import:H807")
      (libsource (lib "eagle-import") (part "W011"))
    )
    (comp (ref "J05")
      (value "W011")
      (footprint "eagle-import:H807")
      (libsource (lib "eagle-import") (part "W011"))
    )
    (comp (ref "J06")
      (value "W011")
      (footprint "eagle-import:H807")
      (libsource (lib "eagle-import") (part "W011"))
    )
    (comp (ref "J07")
      (value "W011")
      (footprint "eagle-import:H807")
      (libsource (lib "eagle-import") (part "W011"))
    )
    (comp (ref "J08")
      (value "W011")
      (footprint "eagle-import:H807")
      (libsource (lib "eagle-import") (part "W011"))
    )
    (comp (ref "J09")
      (value "W011")
      (footprint "eagle-import:H807")
      (libsource (lib "eagle-import") (part "W011"))
    )
    (comp (ref "J10")
      (value "W011")
      (footprint "eagle-import:H807")
      (libsource (lib "eagle-import") (part "W011"))
    )
    (comp (ref "J13")
      (value "M506")
      (footprint "eagle-import:H807")
      (libsource (lib "eagle-import") (part "M506"))
    )
    (comp (ref "J14")
      (value "M506")
      (footprint "eagle-import:H807")
      (libsource (lib "eagle-import") (part "M506"))
    )
    (comp (ref "J15")
      (value "M506")
      (footprint "eagle-import:H807")
      (libsource (lib "eagle-import") (part "M506"))
    )
    (comp (ref "J16")
      (value "M506")
      (footprint "eagle-import:H807")
      (libsource (lib "eagle-import") (part "M506"))
    )
    (comp (ref "J17")
      (value "M506")
      (footprint "eagle-import:H807")
      (libsource (lib "eagle-import") (part "M506"))
    )
    (comp (ref "J18")
      (value "M506")
      (footprint "eagle-import:H807")
      (libsource (lib "eagle-import") (part "M506"))
    )
    (comp (ref "J19")
      (value "M506")
      (footprint "eagle-import:H807")
      (libsource (lib "eagle-import") (part "M506"))
    )
    (comp (ref "J20")
      (value "M506")
      (footprint "eagle-import:H807")
      (libsource (lib "eagle-import") (part "M506"))
    )
    (comp (ref "B10")
      (value "M720")
      (footprint "eagle-import:H807")
      (libsource (lib "eagle-import") (part "M720"))
    )
    (comp (ref "B11")
      (value "M216")
      (footprint "eagle-import:H807")
      (libsource (lib "eagle-import") (part "M216"))
    )
    (comp (ref "B12")
      (value "M617")
      (footprint "eagle-import:H807")
      (libsource (lib "eagle-import") (part "M617"))
    )
    (comp (ref "B13")
      (value "M617")
      (footprint "eagle-import:H807")
      (libsource (lib "eagle-import") (part "M617"))
    )
    (comp (ref "B14")
      (value "M617")
      (footprint "eagle-import:H807")
      (libsource (lib "eagle-import") (part "M617"))
    )
    (comp (ref "B15")
      (value "M617")
      (footprint "eagle-import:H807")
      (libsource (lib "eagle-import") (part "M617"))
    )
    (comp (ref "B19")
      (value "M216")
      (footprint "eagle-import:H807")
      (libsource (lib "eagle-import") (part "M216"))
    )
    (comp (ref "H01")
      (value "W011")
      (footprint "eagle-import:H807")
      (libsource (lib "eagle-import") (part "W011"))
    )
    (comp (ref "H02")
      (value "W011")
      (footprint "eagle-import:H807")
      (libsource (lib "eagle-import") (part "W011"))
    )
    (comp (ref "H03")
      (value "W011")
      (footprint "eagle-import:H807")
      (libsource (lib "eagle-import") (part "W011"))
    )
    (comp (ref "D06")
      (value "M310")
      (footprint "eagle-import:H807")
      (libsource (lib "eagle-import") (part "M310"))
    )
  )
  (nets
    (net (code "1") (name "+3V(01)") (class "Default")
      (node (ref "A13") (pin "E1") (pinfunction "IN2_E1") (pintype "input"))
      (node (ref "A13") (pin "H1") (pinfunction "IN1_H1") (pintype "input"))
      (node (ref "A13") (pin "M1") (pinfunction "IN2_M1") (pintype "input"))
      (node (ref "A13") (pin "R1") (pinfunction "IN2_R1") (pintype "input"))
      (node (ref "A15") (pin "U1") (pinfunction "P$1_U1") (pintype "passive"))
    )
    (net (code "2") (name "+3V(02)") (class "Default")
      (node (ref "A13") (pin "U2") (pinfunction "IN2_U2") (pintype "input"))
      (node (ref "A14") (pin "B1") (pinfunction "IN2_B1") (pintype "input"))
      (node (ref "A14") (pin "H2") (pinfunction "IN1_H2") (pintype "input"))
      (node (ref "A14") (pin "J1") (pinfunction "IN2_J1") (pintype "input"))
      (node (ref "A14") (pin "L1") (pinfunction "IN1_L1") (pintype "input"))
      (node (ref "A15") (pin "V1") (pinfunction "P$1_V1") (pintype "passive"))
    )
    (net (code "3") (name "+3V(03)") (class "Default")
      (node (ref "A14") (pin "L2") (pinfunction "IN1_L2") (pintype "input"))
      (node (ref "A14") (pin "P1") (pinfunction "IN1_P1") (pintype "input"))
      (node (ref "A15") (pin "B1") (pinfunction "IN2_B1") (pintype "input"))
      (node (ref "A15") (pin "M2") (pinfunction "IN2_M2") (pintype "input"))
      (node (ref "A15") (pin "P1") (pinfunction "IN1_P1") (pintype "input"))
      (node (ref "A18") (pin "U1") (pinfunction "P$1_U1") (pintype "passive"))
    )
    (net (code "4") (name "+3V(04)") (class "Default")
      (node (ref "A18") (pin "V1") (pinfunction "P$1_V1") (pintype "passive"))
      (node (ref "A19") (pin "D1") (pinfunction "IN1_D1") (pintype "input"))
      (node (ref "A19") (pin "D2") (pinfunction "IN1_D2") (pintype "input"))
      (node (ref "A19") (pin "L2") (pinfunction "IN1_L2") (pintype "input"))
      (node (ref "A19") (pin "T2") (pinfunction "IN1_T2") (pintype "input"))
    )
    (net (code "5") (name "+3V(05)") (class "Default")
      (node (ref "A10") (pin "D1") (pinfunction "8B_D1") (pintype "input"))
      (node (ref "B08") (pin "B1") (pinfunction "IN2_B1") (pintype "input"))
      (node (ref "B08") (pin "E1") (pinfunction "IN2_E1") (pintype "input"))
      (node (ref "B08") (pin "E2") (pinfunction "IN2_E2") (pintype "input"))
      (node (ref "B08") (pin "J1") (pinfunction "IN2_J1") (pintype "input"))
      (node (ref "B08") (pin "J2") (pinfunction "IN2_J2") (pintype "input"))
      (node (ref "B08") (pin "M1") (pinfunction "IN2_M1") (pintype "input"))
      (node (ref "B08") (pin "M2") (pinfunction "IN2_M2") (pintype "input"))
      (node (ref "B08") (pin "U1") (pinfunction "P$1_U1") (pintype "passive"))
    )
    (net (code "6") (name "+3V(06)") (class "Default")
      (node (ref "B08") (pin "R1") (pinfunction "IN2_R1") (pintype "input"))
      (node (ref "B08") (pin "R2") (pinfunction "IN2_R2") (pintype "input"))
      (node (ref "B08") (pin "U2") (pinfunction "IN2_U2") (pintype "input"))
      (node (ref "B09") (pin "B1") (pinfunction "IN2_B1") (pintype "input"))
      (node (ref "B09") (pin "D2") (pinfunction "IN1_D2") (pintype "input"))
      (node (ref "B09") (pin "E1") (pinfunction "IN2_E1") (pintype "input"))
      (node (ref "B09") (pin "H2") (pinfunction "IN1_H2") (pintype "input"))
      (node (ref "B09") (pin "U1") (pinfunction "P$1_U1") (pintype "passive"))
    )
    (net (code "7") (name "+3V(07)") (class "Default")
      (node (ref "B07") (pin "F1") (pinfunction "IN2_F1") (pintype "input"))
      (node (ref "B07") (pin "K1") (pinfunction "IN1_K1") (pintype "input"))
      (node (ref "B07") (pin "P2") (pinfunction "IN2_P2") (pintype "input"))
      (node (ref "B07") (pin "R2") (pinfunction "IN3_R2") (pintype "input"))
      (node (ref "B09") (pin "J1") (pinfunction "IN2_J1") (pintype "input"))
      (node (ref "B09") (pin "M2") (pinfunction "IN2_M2") (pintype "input"))
      (node (ref "B09") (pin "V1") (pinfunction "P$1_V1") (pintype "passive"))
    )
    (net (code "8") (name "+3V(08)") (class "Default")
      (node (ref "B11") (pin "A1") (pinfunction "R_A1") (pintype "input"))
      (node (ref "B12") (pin "B1") (pinfunction "IN2_B1") (pintype "input"))
      (node (ref "B12") (pin "C1") (pinfunction "IN3_C1") (pintype "input"))
      (node (ref "B12") (pin "D1") (pinfunction "IN4_D1") (pintype "input"))
      (node (ref "B12") (pin "E2") (pinfunction "IN2_E2") (pintype "input"))
      (node (ref "B12") (pin "F2") (pinfunction "IN3_F2") (pintype "input"))
      (node (ref "B12") (pin "H1") (pinfunction "IN2_H1") (pintype "input"))
      (node (ref "B12") (pin "H2") (pinfunction "IN4_H2") (pintype "input"))
      (node (ref "B12") (pin "J1") (pinfunction "IN3_J1") (pintype "input"))
      (node (ref "B12") (pin "K1") (pinfunction "IN4_K1") (pintype "input"))
      (node (ref "C12") (pin "V1") (pinfunction "P$1_V1") (pintype "passive"))
    )
    (net (code "9") (name "+3V(09)") (class "Default")
      (node (ref "A11") (pin "V1") (pinfunction "P$1_V1") (pintype "passive"))
      (node (ref "B12") (pin "L2") (pinfunction "IN2_L2") (pintype "input"))
      (node (ref "B12") (pin "M2") (pinfunction "IN3_M2") (pintype "input"))
      (node (ref "B12") (pin "N1") (pinfunction "IN2_N1") (pintype "input"))
      (node (ref "B12") (pin "N2") (pinfunction "IN4_N2") (pintype "input"))
      (node (ref "B12") (pin "P1") (pinfunction "IN3_P1") (pintype "input"))
      (node (ref "B12") (pin "R1") (pinfunction "IN4_R1") (pintype "input"))
    )
    (net (code "10") (name "+3V(10)") (class "Default")
      (node (ref "B12") (pin "S2") (pinfunction "IN2_S2") (pintype "input"))
      (node (ref "B12") (pin "T2") (pinfunction "IN3_T2") (pintype "input"))
      (node (ref "B12") (pin "U2") (pinfunction "IN4_U2") (pintype "input"))
      (node (ref "B13") (pin "B1") (pinfunction "IN2_B1") (pintype "input"))
      (node (ref "B13") (pin "C1") (pinfunction "IN3_C1") (pintype "input"))
      (node (ref "B13") (pin "D1") (pinfunction "IN4_D1") (pintype "input"))
      (node (ref "B13") (pin "E2") (pinfunction "IN2_E2") (pintype "input"))
      (node (ref "B13") (pin "F2") (pinfunction "IN3_F2") (pintype "input"))
      (node (ref "B13") (pin "H2") (pinfunction "IN4_H2") (pintype "input"))
      (node (ref "F09") (pin "V1") (pinfunction "P$1_V1") (pintype "passive"))
    )
    (net (code "11") (name "+3V(11)") (class "Default")
      (node (ref "A13") (pin "U1") (pinfunction "P$1_U1") (pintype "passive"))
      (node (ref "B13") (pin "H1") (pinfunction "IN2_H1") (pintype "input"))
      (node (ref "B13") (pin "J1") (pinfunction "IN3_J1") (pintype "input"))
      (node (ref "B13") (pin "K1") (pinfunction "IN4_K1") (pintype "input"))
    )
    (net (code "12") (name "+3V(12)") (class "Default")
      (node (ref "B13") (pin "L2") (pinfunction "IN2_L2") (pintype "input"))
      (node (ref "B13") (pin "M2") (pinfunction "IN3_M2") (pintype "input"))
      (node (ref "B13") (pin "N1") (pinfunction "IN2_N1") (pintype "input"))
      (node (ref "B13") (pin "N2") (pinfunction "IN4_N2") (pintype "input"))
      (node (ref "B13") (pin "P1") (pinfunction "IN3_P1") (pintype "input"))
      (node (ref "B13") (pin "R1") (pinfunction "IN4_R1") (pintype "input"))
      (node (ref "B13") (pin "S2") (pinfunction "IN2_S2") (pintype "input"))
      (node (ref "B13") (pin "T2") (pinfunction "IN3_T2") (pintype "input"))
      (node (ref "B13") (pin "U1") (pinfunction "P$1_U1") (pintype "passive"))
      (node (ref "B13") (pin "U2") (pinfunction "IN4_U2") (pintype "input"))
      (node (ref "B14") (pin "B1") (pinfunction "IN2_B1") (pintype "input"))
      (node (ref "B14") (pin "C1") (pinfunction "IN3_C1") (pintype "input"))
      (node (ref "B14") (pin "D1") (pinfunction "IN4_D1") (pintype "input"))
    )
    (net (code "13") (name "+3V(13)") (class "Default")
      (node (ref "B13") (pin "V1") (pinfunction "P$1_V1") (pintype "passive"))
      (node (ref "B14") (pin "E2") (pinfunction "IN2_E2") (pintype "input"))
      (node (ref "B14") (pin "F2") (pinfunction "IN3_F2") (pintype "input"))
      (node (ref "B14") (pin "H2") (pinfunction "IN4_H2") (pintype "input"))
    )
    (net (code "14") (name "+3V(14)") (class "Default")
      (node (ref "B14") (pin "H1") (pinfunction "IN2_H1") (pintype "input"))
      (node (ref "B14") (pin "J1") (pinfunction "IN3_J1") (pintype "input"))
      (node (ref "B14") (pin "K1") (pinfunction "IN4_K1") (pintype "input"))
      (node (ref "B14") (pin "L2") (pinfunction "IN2_L2") (pintype "input"))
      (node (ref "B14") (pin "M2") (pinfunction "IN3_M2") (pintype "input"))
      (node (ref "B14") (pin "N1") (pinfunction "IN2_N1") (pintype "input"))
      (node (ref "B14") (pin "N2") (pinfunction "IN4_N2") (pintype "input"))
      (node (ref "B14") (pin "P1") (pinfunction "IN3_P1") (pintype "input"))
      (node (ref "B14") (pin "R1") (pinfunction "IN4_R1") (pintype "input"))
      (node (ref "B14") (pin "U1") (pinfunction "P$1_U1") (pintype "passive"))
    )
    (net (code "15") (name "+3V(15)") (class "Default")
      (node (ref "B14") (pin "S2") (pinfunction "IN2_S2") (pintype "input"))
      (node (ref "B14") (pin "T2") (pinfunction "IN3_T2") (pintype "input"))
      (node (ref "B14") (pin "U2") (pinfunction "IN4_U2") (pintype "input"))
      (node (ref "B14") (pin "V1") (pinfunction "P$1_V1") (pintype "passive"))
      (node (ref "B15") (pin "B1") (pinfunction "IN2_B1") (pintype "input"))
      (node (ref "B15") (pin "C1") (pinfunction "IN3_C1") (pintype "input"))
      (node (ref "B15") (pin "D1") (pinfunction "IN4_D1") (pintype "input"))
    )
    (net (code "16") (name "+3V(16)") (class "Default")
      (node (ref "B15") (pin "E2") (pinfunction "IN2_E2") (pintype "input"))
      (node (ref "B15") (pin "F2") (pinfunction "IN3_F2") (pintype "input"))
      (node (ref "B15") (pin "H1") (pinfunction "IN2_H1") (pintype "input"))
      (node (ref "B15") (pin "H2") (pinfunction "IN4_H2") (pintype "input"))
      (node (ref "B15") (pin "J1") (pinfunction "IN3_J1") (pintype "input"))
      (node (ref "B15") (pin "K1") (pinfunction "IN4_K1") (pintype "input"))
      (node (ref "B15") (pin "U1") (pinfunction "P$1_U1") (pintype "passive"))
    )
    (net (code "17") (name "+3V(17)") (class "Default")
      (node (ref "B15") (pin "L2") (pinfunction "IN2_L2") (pintype "input"))
      (node (ref "B15") (pin "M2") (pinfunction "IN3_M2") (pintype "input"))
      (node (ref "B15") (pin "N1") (pinfunction "IN2_N1") (pintype "input"))
      (node (ref "B15") (pin "N2") (pinfunction "IN4_N2") (pintype "input"))
      (node (ref "B15") (pin "P1") (pinfunction "IN3_P1") (pintype "input"))
      (node (ref "B15") (pin "R1") (pinfunction "IN4_R1") (pintype "input"))
      (node (ref "B15") (pin "S2") (pinfunction "IN2_S2") (pintype "input"))
      (node (ref "B15") (pin "T2") (pinfunction "IN3_T2") (pintype "input"))
      (node (ref "B15") (pin "U2") (pinfunction "IN4_U2") (pintype "input"))
      (node (ref "B16") (pin "V1") (pinfunction "P$1_V1") (pintype "passive"))
    )
    (net (code "18") (name "+3V(18)") (class "Default")
      (node (ref "B16") (pin "D1") (pinfunction "IN4_D1") (pintype "input"))
      (node (ref "B16") (pin "H2") (pinfunction "IN4_H2") (pintype "input"))
      (node (ref "B16") (pin "K1") (pinfunction "IN4_K1") (pintype "input"))
      (node (ref "B16") (pin "N1") (pinfunction "IN2_N1") (pintype "input"))
      (node (ref "B16") (pin "P1") (pinfunction "IN3_P1") (pintype "input"))
      (node (ref "B16") (pin "R1") (pinfunction "IN4_R1") (pintype "input"))
      (node (ref "B16") (pin "S2") (pinfunction "IN2_S2") (pintype "input"))
      (node (ref "B16") (pin "T2") (pinfunction "IN3_T2") (pintype "input"))
      (node (ref "B16") (pin "U1") (pinfunction "P$1_U1") (pintype "passive"))
      (node (ref "B16") (pin "U2") (pinfunction "IN4_U2") (pintype "input"))
    )
    (net (code "19") (name "+3V(19)") (class "Default")
      (node (ref "A19") (pin "U1") (pinfunction "P$1_U1") (pintype "passive"))
      (node (ref "B17") (pin "D1") (pinfunction "S_D1") (pintype "input"))
      (node (ref "B17") (pin "F2") (pinfunction "S_F2") (pintype "input"))
      (node (ref "B17") (pin "K1") (pinfunction "S_K1") (pintype "input"))
      (node (ref "B17") (pin "N2") (pinfunction "S_N2") (pintype "input"))
      (node (ref "B17") (pin "R1") (pinfunction "S_R1") (pintype "input"))
      (node (ref "B17") (pin "U2") (pinfunction "S_U2") (pintype "input"))
      (node (ref "B18") (pin "D1") (pinfunction "S_D1") (pintype "input"))
      (node (ref "B18") (pin "F2") (pinfunction "S_F2") (pintype "input"))
      (node (ref "B18") (pin "K1") (pinfunction "S_K1") (pintype "input"))
      (node (ref "B18") (pin "K2") (pinfunction "R_K2") (pintype "input"))
    )
    (net (code "20") (name "+3V(20)") (class "Default")
      (node (ref "A19") (pin "V1") (pinfunction "P$1_V1") (pintype "passive"))
      (node (ref "B18") (pin "N2") (pinfunction "S_N2") (pintype "input"))
      (node (ref "B18") (pin "R1") (pinfunction "S_R1") (pintype "input"))
      (node (ref "B18") (pin "U2") (pinfunction "S_U2") (pintype "input"))
      (node (ref "B19") (pin "A1") (pinfunction "R_A1") (pintype "input"))
      (node (ref "B19") (pin "D1") (pinfunction "S_D1") (pintype "input"))
      (node (ref "B19") (pin "F2") (pinfunction "S_F2") (pintype "input"))
      (node (ref "B19") (pin "K1") (pinfunction "S_K1") (pintype "input"))
      (node (ref "B19") (pin "K2") (pinfunction "R_K2") (pintype "input"))
      (node (ref "B19") (pin "N2") (pinfunction "S_N2") (pintype "input"))
      (node (ref "B19") (pin "R1") (pinfunction "S_R1") (pintype "input"))
      (node (ref "B19") (pin "U2") (pinfunction "S_U2") (pintype "input"))
    )
    (net (code "21") (name "+3V(21)") (class "Default")
      (node (ref "B21") (pin "B1") (pinfunction "IN2_B1") (pintype "input"))
      (node (ref "B21") (pin "E2") (pinfunction "IN2_E2") (pintype "input"))
      (node (ref "B21") (pin "H1") (pinfunction "IN1_H1") (pintype "input"))
      (node (ref "B21") (pin "J2") (pinfunction "IN2_J2") (pintype "input"))
      (node (ref "B21") (pin "U1") (pinfunction "P$1_U1") (pintype "passive"))
      (node (ref "B22") (pin "D1") (pinfunction "S_D1") (pintype "input"))
      (node (ref "B22") (pin "F2") (pinfunction "S_F2") (pintype "input"))
      (node (ref "B30") (pin "B1") (pinfunction "IN2_B1") (pintype "input"))
      (node (ref "B30") (pin "C1") (pinfunction "IN3_C1") (pintype "input"))
      (node (ref "B30") (pin "D1") (pinfunction "IN4_D1") (pintype "input"))
      (node (ref "B30") (pin "D2") (pinfunction "IN1_D2") (pintype "input"))
    )
    (net (code "22") (name "+3V(22)") (class "Default")
      (node (ref "B30") (pin "E2") (pinfunction "IN2_E2") (pintype "input"))
      (node (ref "B30") (pin "F2") (pinfunction "IN3_F2") (pintype "input"))
      (node (ref "B30") (pin "H1") (pinfunction "IN2_H1") (pintype "input"))
      (node (ref "B30") (pin "J1") (pinfunction "IN3_J1") (pintype "input"))
      (node (ref "B30") (pin "K1") (pinfunction "IN4_K1") (pintype "input"))
      (node (ref "B30") (pin "L2") (pinfunction "IN2_L2") (pintype "input"))
      (node (ref "B30") (pin "M2") (pinfunction "IN3_M2") (pintype "input"))
      (node (ref "B30") (pin "N1") (pinfunction "IN2_N1") (pintype "input"))
      (node (ref "B30") (pin "N2") (pinfunction "IN4_N2") (pintype "input"))
      (node (ref "B30") (pin "P1") (pinfunction "IN3_P1") (pintype "input"))
      (node (ref "B30") (pin "R1") (pinfunction "IN4_R1") (pintype "input"))
      (node (ref "B30") (pin "S2") (pinfunction "IN2_S2") (pintype "input"))
      (node (ref "B30") (pin "T2") (pinfunction "IN3_T2") (pintype "input"))
      (node (ref "B30") (pin "U1") (pinfunction "P$1_U1") (pintype "passive"))
      (node (ref "B30") (pin "U2") (pinfunction "IN4_U2") (pintype "input"))
      (node (ref "D39") (pin "A1") (pinfunction "A1_A1") (pintype "input"))
      (node (ref "D39") (pin "E2") (pinfunction "E2_E2") (pintype "input"))
      (node (ref "D39") (pin "N2") (pinfunction "N2_N2") (pintype "input"))
    )
    (net (code "23") (name "+3V(23)") (class "Default")
      (node (ref "C10") (pin "B1") (pinfunction "IN2_B1") (pintype "input"))
      (node (ref "C10") (pin "D1") (pinfunction "IN1_D1") (pintype "input"))
      (node (ref "C10") (pin "D2") (pinfunction "IN1_D2") (pintype "input"))
      (node (ref "C10") (pin "H2") (pinfunction "IN1_H2") (pintype "input"))
      (node (ref "C10") (pin "J1") (pinfunction "IN2_J1") (pintype "input"))
      (node (ref "C10") (pin "U2") (pinfunction "IN2_U2") (pintype "input"))
      (node (ref "C11") (pin "B1") (pinfunction "IN2_B1") (pintype "input"))
      (node (ref "D10") (pin "B1") (pinfunction "IN2_B1") (pintype "input"))
      (node (ref "D10") (pin "C1") (pinfunction "IN3_C1") (pintype "input"))
      (node (ref "D10") (pin "U1") (pinfunction "P$1_U1") (pintype "passive"))
      (node (ref "D11") (pin "A1") (pinfunction "R_A1") (pintype "input"))
    )
    (net (code "24") (name "+3V(24)") (class "Default")
      (node (ref "C18") (pin "A1") (pinfunction "IN1_A1") (pintype "input"))
      (node (ref "C18") (pin "D1") (pinfunction "IN1_D1") (pintype "input"))
      (node (ref "C18") (pin "D2") (pinfunction "IN1_D2") (pintype "input"))
      (node (ref "C18") (pin "H2") (pinfunction "IN1_H2") (pintype "input"))
      (node (ref "C18") (pin "R2") (pinfunction "IN2_R2") (pintype "input"))
      (node (ref "C18") (pin "U1") (pinfunction "P$1_U1") (pintype "passive"))
      (node (ref "C18") (pin "U2") (pinfunction "IN2_U2") (pintype "input"))
    )
    (net (code "25") (name "+3V(25)") (class "Default")
      (node (ref "B21") (pin "V1") (pinfunction "P$1_V1") (pintype "passive"))
      (node (ref "C22") (pin "A1") (pinfunction "R_A1") (pintype "input"))
      (node (ref "C22") (pin "D1") (pinfunction "S_D1") (pintype "input"))
      (node (ref "C22") (pin "F2") (pinfunction "S_F2") (pintype "input"))
      (node (ref "C22") (pin "K1") (pinfunction "S_K1") (pintype "input"))
      (node (ref "C22") (pin "K2") (pinfunction "R_K2") (pintype "input"))
      (node (ref "C22") (pin "N2") (pinfunction "S_N2") (pintype "input"))
      (node (ref "C22") (pin "R1") (pinfunction "S_R1") (pintype "input"))
    )
    (net (code "26") (name "+3V(26)") (class "Default")
      (node (ref "C23") (pin "A1") (pinfunction "R_A1") (pintype "input"))
      (node (ref "C23") (pin "D1") (pinfunction "S_D1") (pintype "input"))
      (node (ref "C23") (pin "F2") (pinfunction "S_F2") (pintype "input"))
      (node (ref "C23") (pin "K1") (pinfunction "S_K1") (pintype "input"))
      (node (ref "C23") (pin "K2") (pinfunction "R_K2") (pintype "input"))
      (node (ref "C23") (pin "N2") (pinfunction "S_N2") (pintype "input"))
      (node (ref "C23") (pin "R1") (pinfunction "S_R1") (pintype "input"))
      (node (ref "C23") (pin "U2") (pinfunction "S_U2") (pintype "input"))
      (node (ref "D22") (pin "U1") (pinfunction "P$1_U1") (pintype "passive"))
    )
    (net (code "27") (name "+3V(27)") (class "Default")
      (node (ref "C24") (pin "A1") (pinfunction "R_A1") (pintype "input"))
      (node (ref "C24") (pin "D1") (pinfunction "S_D1") (pintype "input"))
      (node (ref "C24") (pin "F2") (pinfunction "S_F2") (pintype "input"))
      (node (ref "C24") (pin "K1") (pinfunction "S_K1") (pintype "input"))
      (node (ref "C24") (pin "K2") (pinfunction "R_K2") (pintype "input"))
      (node (ref "C24") (pin "N2") (pinfunction "S_N2") (pintype "input"))
      (node (ref "C24") (pin "R1") (pinfunction "S_R1") (pintype "input"))
      (node (ref "C24") (pin "U2") (pinfunction "S_U2") (pintype "input"))
      (node (ref "D22") (pin "V1") (pinfunction "P$1_V1") (pintype "passive"))
    )
    (net (code "28") (name "+3V(28)") (class "Default")
      (node (ref "D12") (pin "E1") (pinfunction "IN2_E1") (pintype "input"))
      (node (ref "D12") (pin "J2") (pinfunction "IN2_J2") (pintype "input"))
      (node (ref "D12") (pin "M1") (pinfunction "IN2_M1") (pintype "input"))
      (node (ref "D12") (pin "T2") (pinfunction "IN1_T2") (pintype "input"))
      (node (ref "D12") (pin "U1") (pinfunction "P$1_U1") (pintype "passive"))
      (node (ref "D13") (pin "J1") (pinfunction "IN2_J1") (pintype "input"))
      (node (ref "D13") (pin "J2") (pinfunction "IN2_J2") (pintype "input"))
    )
    (net (code "29") (name "+3V(29)") (class "Default")
      (node (ref "D14") (pin "P1") (pinfunction "IN1_P1") (pintype "input"))
      (node (ref "D15") (pin "D2") (pinfunction "IN1_D2") (pintype "input"))
      (node (ref "D15") (pin "H2") (pinfunction "IN1_H2") (pintype "input"))
      (node (ref "D15") (pin "M2") (pinfunction "IN2_M2") (pintype "input"))
      (node (ref "D15") (pin "P1") (pinfunction "IN1_P1") (pintype "input"))
      (node (ref "D15") (pin "U1") (pinfunction "P$1_U1") (pintype "passive"))
      (node (ref "D15") (pin "U2") (pinfunction "IN2_U2") (pintype "input"))
    )
    (net (code "30") (name "+3V(30)") (class "Default")
      (node (ref "D16") (pin "A1") (pinfunction "IN1_A1") (pintype "input"))
      (node (ref "D16") (pin "D1") (pinfunction "IN1_D1") (pintype "input"))
      (node (ref "D16") (pin "D2") (pinfunction "IN1_D2") (pintype "input"))
      (node (ref "D16") (pin "M2") (pinfunction "IN2_M2") (pintype "input"))
      (node (ref "D16") (pin "R1") (pinfunction "IN2_R1") (pintype "input"))
      (node (ref "D16") (pin "R2") (pinfunction "IN2_R2") (pintype "input"))
      (node (ref "D16") (pin "U1") (pinfunction "P$1_U1") (pintype "passive"))
      (node (ref "D16") (pin "U2") (pinfunction "IN2_U2") (pintype "input"))
    )
    (net (code "31") (name "+3V(31)") (class "Default")
      (node (ref "D22") (pin "H1") (pinfunction "IN2_H1") (pintype "input"))
      (node (ref "D22") (pin "J1") (pinfunction "IN3_J1") (pintype "input"))
      (node (ref "D22") (pin "K1") (pinfunction "IN4_K1") (pintype "input"))
      (node (ref "D22") (pin "L2") (pinfunction "IN2_L2") (pintype "input"))
      (node (ref "D22") (pin "M1") (pinfunction "IN1_M1") (pintype "input"))
      (node (ref "D22") (pin "M2") (pinfunction "IN3_M2") (pintype "input"))
      (node (ref "D22") (pin "N1") (pinfunction "IN2_N1") (pintype "input"))
      (node (ref "D22") (pin "N2") (pinfunction "IN4_N2") (pintype "input"))
      (node (ref "D22") (pin "T2") (pinfunction "IN3_T2") (pintype "input"))
      (node (ref "E22") (pin "V1") (pinfunction "P$1_V1") (pintype "passive"))
    )
    (net (code "32") (name "+3V(32)") (class "Default")
      (node (ref "D23") (pin "D2") (pinfunction "IN1A_D2") (pintype "input"))
      (node (ref "D23") (pin "E2") (pinfunction "IN1B_E2") (pintype "input"))
      (node (ref "D23") (pin "M1") (pinfunction "IN5A_M1") (pintype "input"))
      (node (ref "D23") (pin "N2") (pinfunction "IN4A_N2") (pintype "input"))
      (node (ref "D23") (pin "P2") (pinfunction "IN4B_P2") (pintype "input"))
      (node (ref "D23") (pin "R2") (pinfunction "IN4C_R2") (pintype "input"))
      (node (ref "D24") (pin "D1") (pinfunction "S_D1") (pintype "input"))
      (node (ref "D24") (pin "F2") (pinfunction "S_F2") (pintype "input"))
      (node (ref "D24") (pin "K1") (pinfunction "S_K1") (pintype "input"))
      (node (ref "D24") (pin "N2") (pinfunction "S_N2") (pintype "input"))
      (node (ref "E24") (pin "U1") (pinfunction "P$1_U1") (pintype "passive"))
    )
    (net (code "33") (name "+3V(33)") (class "Default")
      (node (ref "E11") (pin "B1") (pinfunction "IN2_B1") (pintype "input"))
      (node (ref "E11") (pin "E2") (pinfunction "IN2_E2") (pintype "input"))
      (node (ref "E11") (pin "H2") (pinfunction "IN1_H2") (pintype "input"))
      (node (ref "E11") (pin "M2") (pinfunction "IN2_M2") (pintype "input"))
      (node (ref "E11") (pin "P2") (pinfunction "IN1_P2") (pintype "input"))
      (node (ref "E12") (pin "B1") (pinfunction "IN2_B1") (pintype "input"))
      (node (ref "E12") (pin "J1") (pinfunction "IN2_J1") (pintype "input"))
      (node (ref "E12") (pin "L1") (pinfunction "IN1_L1") (pintype "input"))
      (node (ref "E12") (pin "R1") (pinfunction "IN2_R1") (pintype "input"))
      (node (ref "E12") (pin "T2") (pinfunction "IN1_T2") (pintype "input"))
      (node (ref "EF01") (pin "BR1") (pinfunction "BR1_BR1") (pintype "input"))
      (node (ref "EF02") (pin "AN1") (pinfunction "AN1_AN1") (pintype "input"))
      (node (ref "EF02") (pin "AN2") (pinfunction "AN2_AN2") (pintype "input"))
      (node (ref "EF02") (pin "BF2") (pinfunction "BF2_BF2") (pintype "input"))
      (node (ref "EF02") (pin "BJ1") (pinfunction "BJ1_BJ1") (pintype "output"))
      (node (ref "EF02") (pin "BS2") (pinfunction "BS2_BS2") (pintype "input"))
    )
    (net (code "34") (name "+3V(34)") (class "Default")
      (node (ref "E13") (pin "N1") (pinfunction "IN5B_N1") (pintype "input"))
      (node (ref "E13") (pin "P1") (pinfunction "IN5C_P1") (pintype "input"))
      (node (ref "E15") (pin "J2") (pinfunction "IN2_J2") (pintype "input"))
      (node (ref "E15") (pin "M1") (pinfunction "IN2_M1") (pintype "input"))
      (node (ref "E15") (pin "M2") (pinfunction "IN2_M2") (pintype "input"))
      (node (ref "E15") (pin "P2") (pinfunction "IN1_P2") (pintype "input"))
      (node (ref "E15") (pin "U1") (pinfunction "P$1_U1") (pintype "passive"))
      (node (ref "E15") (pin "U2") (pinfunction "IN2_U2") (pintype "input"))
    )
    (net (code "35") (name "+3V(35)") (class "Default")
      (node (ref "E15") (pin "V1") (pinfunction "P$1_V1") (pintype "passive"))
      (node (ref "E18") (pin "C1") (pinfunction "D_C1") (pintype "input"))
      (node (ref "E18") (pin "N2") (pinfunction "S_N2") (pintype "input"))
      (node (ref "E20") (pin "D1") (pinfunction "S_D1") (pintype "input"))
      (node (ref "E20") (pin "F2") (pinfunction "S_F2") (pintype "input"))
      (node (ref "E20") (pin "K1") (pinfunction "S_K1") (pintype "input"))
      (node (ref "E20") (pin "N2") (pinfunction "S_N2") (pintype "input"))
    )
    (net (code "36") (name "+3V(36)") (class "Default")
      (node (ref "E22") (pin "M2") (pinfunction "IN2_M2") (pintype "input"))
      (node (ref "E22") (pin "R1") (pinfunction "IN2_R1") (pintype "input"))
      (node (ref "E22") (pin "R2") (pinfunction "IN2_R2") (pintype "input"))
      (node (ref "E22") (pin "U1") (pinfunction "P$1_U1") (pintype "passive"))
      (node (ref "E22") (pin "U2") (pinfunction "IN2_U2") (pintype "input"))
      (node (ref "E23") (pin "F2") (pinfunction "S_F2") (pintype "input"))
      (node (ref "E23") (pin "K1") (pinfunction "S_K1") (pintype "input"))
      (node (ref "E23") (pin "N2") (pinfunction "S_N2") (pintype "input"))
      (node (ref "E23") (pin "R1") (pinfunction "S_R1") (pintype "input"))
      (node (ref "E23") (pin "U2") (pinfunction "S_U2") (pintype "input"))
      (node (ref "E24") (pin "J1") (pinfunction "IN2_J1") (pintype "input"))
      (node (ref "E24") (pin "M2") (pinfunction "IN2_M2") (pintype "input"))
      (node (ref "E24") (pin "P1") (pinfunction "IN1_P1") (pintype "input"))
      (node (ref "E24") (pin "P2") (pinfunction "IN1_P2") (pintype "input"))
    )
    (net (code "37") (name "+3V(37)") (class "Default")
      (node (ref "E26") (pin "D2") (pinfunction "IN1A_D2") (pintype "input"))
      (node (ref "E26") (pin "N2") (pinfunction "IN4A_N2") (pintype "input"))
      (node (ref "E27") (pin "C1") (pinfunction "IN1C_C1") (pintype "input"))
      (node (ref "E27") (pin "E2") (pinfunction "IN1B_E2") (pintype "input"))
      (node (ref "E27") (pin "F2") (pinfunction "IN1C_F2") (pintype "input"))
      (node (ref "E27") (pin "H2") (pinfunction "IN1D_H2") (pintype "input"))
      (node (ref "E27") (pin "N2") (pinfunction "IN4A_N2") (pintype "input"))
      (node (ref "E28") (pin "A1") (pinfunction "IN1A_A1") (pintype "input"))
      (node (ref "E28") (pin "H1") (pinfunction "IN3A_H1") (pintype "input"))
      (node (ref "F27") (pin "U1") (pinfunction "P$1_U1") (pintype "passive"))
    )
    (net (code "38") (name "+3V(38)") (class "Default")
      (node (ref "E28") (pin "K1") (pinfunction "IN4A_K1") (pintype "input"))
      (node (ref "E29") (pin "B1") (pinfunction "IN1B_B1") (pintype "input"))
      (node (ref "E29") (pin "E2") (pinfunction "IN1B_E2") (pintype "input"))
      (node (ref "E29") (pin "H1") (pinfunction "IN3A_H1") (pintype "input"))
      (node (ref "E29") (pin "H2") (pinfunction "IN1D_H2") (pintype "input"))
      (node (ref "E29") (pin "P2") (pinfunction "IN4B_P2") (pintype "input"))
      (node (ref "E29") (pin "R2") (pinfunction "IN4C_R2") (pintype "input"))
      (node (ref "F29") (pin "U1") (pinfunction "P$1_U1") (pintype "passive"))
    )
    (net (code "39") (name "+3V(39)") (class "Default")
      (node (ref "E30") (pin "B1") (pinfunction "IN1B_B1") (pintype "input"))
      (node (ref "E30") (pin "C1") (pinfunction "IN1C_C1") (pintype "input"))
      (node (ref "E30") (pin "D1") (pinfunction "IN1D_D1") (pintype "input"))
      (node (ref "E30") (pin "E2") (pinfunction "IN1B_E2") (pintype "input"))
      (node (ref "E30") (pin "N2") (pinfunction "IN4A_N2") (pintype "input"))
      (node (ref "E31") (pin "B1") (pinfunction "IN2_B1") (pintype "input"))
      (node (ref "E31") (pin "C1") (pinfunction "IN3_C1") (pintype "input"))
      (node (ref "E31") (pin "D1") (pinfunction "IN4_D1") (pintype "input"))
      (node (ref "E31") (pin "D2") (pinfunction "IN1_D2") (pintype "input"))
      (node (ref "E31") (pin "E2") (pinfunction "IN2_E2") (pintype "input"))
      (node (ref "E31") (pin "U1") (pinfunction "P$1_U1") (pintype "passive"))
    )
    (net (code "40") (name "+3V(40)") (class "Default")
      (node (ref "E31") (pin "F1") (pinfunction "IN1_F1") (pintype "input"))
      (node (ref "E31") (pin "F2") (pinfunction "IN3_F2") (pintype "input"))
      (node (ref "E31") (pin "K2") (pinfunction "IN1_K2") (pintype "input"))
      (node (ref "E31") (pin "L2") (pinfunction "IN2_L2") (pintype "input"))
      (node (ref "E31") (pin "S2") (pinfunction "IN2_S2") (pintype "input"))
      (node (ref "E31") (pin "T2") (pinfunction "IN3_T2") (pintype "input"))
      (node (ref "E31") (pin "U2") (pinfunction "IN4_U2") (pintype "input"))
      (node (ref "E31") (pin "V1") (pinfunction "P$1_V1") (pintype "passive"))
    )
    (net (code "41") (name "+3V(41)") (class "Default")
      (node (ref "E32") (pin "B1") (pinfunction "IN2_B1") (pintype "input"))
      (node (ref "E32") (pin "C1") (pinfunction "IN3_C1") (pintype "input"))
      (node (ref "E32") (pin "D2") (pinfunction "IN1_D2") (pintype "input"))
      (node (ref "E32") (pin "F1") (pinfunction "IN1_F1") (pintype "input"))
      (node (ref "E32") (pin "H1") (pinfunction "IN2_H1") (pintype "input"))
      (node (ref "E32") (pin "J1") (pinfunction "IN3_J1") (pintype "input"))
      (node (ref "E32") (pin "U1") (pinfunction "P$1_U1") (pintype "passive"))
    )
    (net (code "42") (name "+3V(42)") (class "Default")
      (node (ref "C39") (pin "D1") (pinfunction "D1_D1") (pintype "input"))
      (node (ref "C39") (pin "L1") (pinfunction "L1_L1") (pintype "input"))
      (node (ref "D39") (pin "D1") (pinfunction "D1_D1") (pintype "input"))
      (node (ref "D39") (pin "L1") (pinfunction "L1_L1") (pintype "input"))
      (node (ref "E32") (pin "R2") (pinfunction "IN1_R2") (pintype "input"))
      (node (ref "E32") (pin "S2") (pinfunction "IN2_S2") (pintype "input"))
      (node (ref "E32") (pin "V1") (pinfunction "P$1_V1") (pintype "passive"))
      (node (ref "E33") (pin "A1") (pinfunction "R_A1") (pintype "input"))
      (node (ref "E33") (pin "K2") (pinfunction "R_K2") (pintype "input"))
      (node (ref "E33") (pin "U2") (pinfunction "S_U2") (pintype "input"))
    )
    (net (code "43") (name "+3V(43)") (class "Default")
      (node (ref "C12") (pin "F1") (pinfunction "IN1_F1") (pintype "input"))
      (node (ref "F19") (pin "N2") (pinfunction "IN4_N2") (pintype "input"))
      (node (ref "F20") (pin "A1") (pinfunction "IN1_A1") (pintype "input"))
      (node (ref "F20") (pin "M1") (pinfunction "IN2_M1") (pintype "input"))
      (node (ref "F20") (pin "M2") (pinfunction "IN2_M2") (pintype "input"))
      (node (ref "F20") (pin "U1") (pinfunction "P$1_U1") (pintype "passive"))
      (node (ref "F21") (pin "E2") (pinfunction "IN2_E2") (pintype "input"))
      (node (ref "F21") (pin "J2") (pinfunction "IN2_J2") (pintype "input"))
      (node (ref "F21") (pin "L1") (pinfunction "IN1_L1") (pintype "input"))
      (node (ref "F21") (pin "P2") (pinfunction "IN1_P2") (pintype "input"))
      (node (ref "F21") (pin "R1") (pinfunction "IN2_R1") (pintype "input"))
    )
    (net (code "44") (name "+3V(44)") (class "Default")
      (node (ref "F22") (pin "A1") (pinfunction "IN1_A1") (pintype "input"))
      (node (ref "F22") (pin "E1") (pinfunction "IN2_E1") (pintype "input"))
      (node (ref "F22") (pin "J1") (pinfunction "IN2_J1") (pintype "input"))
      (node (ref "F22") (pin "J2") (pinfunction "IN2_J2") (pintype "input"))
      (node (ref "F22") (pin "M1") (pinfunction "IN2_M1") (pintype "input"))
      (node (ref "F22") (pin "M2") (pinfunction "IN2_M2") (pintype "input"))
      (node (ref "F22") (pin "U1") (pinfunction "P$1_U1") (pintype "passive"))
      (node (ref "F24") (pin "D1") (pinfunction "IN4_D1") (pintype "input"))
      (node (ref "F25") (pin "B1") (pinfunction "IN2_B1") (pintype "input"))
      (node (ref "F25") (pin "E1") (pinfunction "IN2_E1") (pintype "input"))
      (node (ref "F25") (pin "M2") (pinfunction "IN2_M2") (pintype "input"))
    )
    (net (code "45") (name "+3V(45)") (class "Default")
      (node (ref "F25") (pin "R1") (pinfunction "IN2_R1") (pintype "input"))
      (node (ref "F29") (pin "B1") (pinfunction "IN2_B1") (pintype "input"))
      (node (ref "F29") (pin "E2") (pinfunction "IN2_E2") (pintype "input"))
      (node (ref "F29") (pin "H1") (pinfunction "IN1_H1") (pintype "input"))
      (node (ref "F29") (pin "H2") (pinfunction "IN1_H2") (pintype "input"))
      (node (ref "F30") (pin "B1") (pinfunction "IN2_B1") (pintype "input"))
      (node (ref "F30") (pin "C1") (pinfunction "IN3_C1") (pintype "input"))
      (node (ref "F30") (pin "D1") (pinfunction "IN4_D1") (pintype "input"))
      (node (ref "F30") (pin "F2") (pinfunction "IN3_F2") (pintype "input"))
      (node (ref "F30") (pin "H1") (pinfunction "IN2_H1") (pintype "input"))
      (node (ref "F30") (pin "L2") (pinfunction "IN2_L2") (pintype "input"))
      (node (ref "F30") (pin "M2") (pinfunction "IN3_M2") (pintype "input"))
      (node (ref "F30") (pin "N2") (pinfunction "IN4_N2") (pintype "input"))
      (node (ref "F30") (pin "V1") (pinfunction "P$1_V1") (pintype "passive"))
    )
    (net (code "46") (name "+3V(46)") (class "Default")
      (node (ref "F30") (pin "J1") (pinfunction "IN3_J1") (pintype "input"))
      (node (ref "F30") (pin "K1") (pinfunction "IN4_K1") (pintype "input"))
      (node (ref "F30") (pin "R1") (pinfunction "IN4_R1") (pintype "input"))
      (node (ref "F30") (pin "R2") (pinfunction "IN1_R2") (pintype "input"))
      (node (ref "F30") (pin "S2") (pinfunction "IN2_S2") (pintype "input"))
      (node (ref "F30") (pin "T2") (pinfunction "IN3_T2") (pintype "input"))
      (node (ref "F30") (pin "U1") (pinfunction "P$1_U1") (pintype "passive"))
      (node (ref "F31") (pin "J1") (pinfunction "IN3_J1") (pintype "input"))
      (node (ref "J30") (pin "K2") (pinfunction "K2_K2") (pintype "input"))
    )
    (net (code "47") (name "+3V(47)") (class "Default")
      (node (ref "F31") (pin "K1") (pinfunction "IN4_K1") (pintype "input"))
      (node (ref "F31") (pin "L2") (pinfunction "IN2_L2") (pintype "input"))
      (node (ref "F31") (pin "M2") (pinfunction "IN3_M2") (pintype "input"))
      (node (ref "F31") (pin "N1") (pinfunction "IN2_N1") (pintype "input"))
      (node (ref "F31") (pin "N2") (pinfunction "IN4_N2") (pintype "input"))
      (node (ref "F31") (pin "P1") (pinfunction "IN3_P1") (pintype "input"))
      (node (ref "F31") (pin "R1") (pinfunction "IN4_R1") (pintype "input"))
      (node (ref "F31") (pin "S2") (pinfunction "IN2_S2") (pintype "input"))
      (node (ref "F31") (pin "T2") (pinfunction "IN3_T2") (pintype "input"))
      (node (ref "F31") (pin "U1") (pinfunction "P$1_U1") (pintype "passive"))
      (node (ref "F31") (pin "U2") (pinfunction "IN4_U2") (pintype "input"))
    )
    (net (code "48") (name "+3V(48)") (class "Default")
      (node (ref "F31") (pin "V1") (pinfunction "P$1_V1") (pintype "passive"))
      (node (ref "F32") (pin "B1") (pinfunction "IN2_B1") (pintype "input"))
      (node (ref "F32") (pin "E2") (pinfunction "IN2_E2") (pintype "input"))
      (node (ref "F32") (pin "H1") (pinfunction "IN1_H1") (pintype "input"))
      (node (ref "F32") (pin "M2") (pinfunction "IN2_M2") (pintype "input"))
      (node (ref "F32") (pin "P2") (pinfunction "IN1_P2") (pintype "input"))
      (node (ref "F32") (pin "R1") (pinfunction "IN2_R1") (pintype "input"))
      (node (ref "F32") (pin "T2") (pinfunction "IN1_T2") (pintype "input"))
      (node (ref "F33") (pin "C1") (pinfunction "IN1C_C1") (pintype "input"))
      (node (ref "F33") (pin "D2") (pinfunction "IN1A_D2") (pintype "input"))
      (node (ref "F33") (pin "P1") (pinfunction "IN5C_P1") (pintype "input"))
    )
    (net (code "49") (name "+3V(49)") (class "Default")
      (node (ref "EF10") (pin "BF2") (pinfunction "P$1_BF2") (pintype "passive"))
      (node (ref "H07") (pin "F2") (pinfunction "IN1_F2") (pintype "input"))
      (node (ref "H07") (pin "J2") (pinfunction "IN3_J2") (pintype "input"))
      (node (ref "H07") (pin "M2") (pinfunction "IN1_M2") (pintype "input"))
      (node (ref "H07") (pin "P2") (pinfunction "IN3_P2") (pintype "input"))
      (node (ref "H07") (pin "T2") (pinfunction "IN1_T2") (pintype "input"))
      (node (ref "H07") (pin "V2") (pinfunction "IN3_V2") (pintype "input"))
      (node (ref "H08") (pin "F2") (pinfunction "IN1_F2") (pintype "input"))
      (node (ref "H08") (pin "J2") (pinfunction "IN3_J2") (pintype "input"))
      (node (ref "H08") (pin "M2") (pinfunction "IN1_M2") (pintype "input"))
      (node (ref "H08") (pin "P2") (pinfunction "IN3_P2") (pintype "input"))
      (node (ref "H08") (pin "T2") (pinfunction "IN1_T2") (pintype "input"))
      (node (ref "H08") (pin "V2") (pinfunction "IN3_V2") (pintype "input"))
    )
    (net (code "50") (name "+3V(50)") (class "Default")
      (node (ref "F11") (pin "V1") (pinfunction "P$1_V1") (pintype "passive"))
      (node (ref "H09") (pin "F2") (pinfunction "IN1_F2") (pintype "input"))
      (node (ref "H09") (pin "J2") (pinfunction "IN3_J2") (pintype "input"))
      (node (ref "H09") (pin "M2") (pinfunction "IN1_M2") (pintype "input"))
      (node (ref "H09") (pin "P2") (pinfunction "IN3_P2") (pintype "input"))
      (node (ref "H09") (pin "T2") (pinfunction "IN1_T2") (pintype "input"))
      (node (ref "H09") (pin "V2") (pinfunction "IN3_V2") (pintype "input"))
      (node (ref "H10") (pin "F2") (pinfunction "IN1_F2") (pintype "input"))
      (node (ref "H10") (pin "J2") (pinfunction "IN3_J2") (pintype "input"))
      (node (ref "H10") (pin "M2") (pinfunction "IN1_M2") (pintype "input"))
      (node (ref "H10") (pin "P2") (pinfunction "IN3_P2") (pintype "input"))
      (node (ref "H10") (pin "T2") (pinfunction "IN1_T2") (pintype "input"))
      (node (ref "H10") (pin "V2") (pinfunction "IN3_V2") (pintype "input"))
    )
    (net (code "51") (name "+3V(51)") (class "Default")
      (node (ref "F20") (pin "V1") (pinfunction "P$1_V1") (pintype "passive"))
      (node (ref "H11") (pin "F2") (pinfunction "IN1_F2") (pintype "input"))
      (node (ref "H11") (pin "J2") (pinfunction "IN3_J2") (pintype "input"))
      (node (ref "H11") (pin "M2") (pinfunction "IN1_M2") (pintype "input"))
      (node (ref "H11") (pin "P2") (pinfunction "IN3_P2") (pintype "input"))
      (node (ref "H11") (pin "T2") (pinfunction "IN1_T2") (pintype "input"))
      (node (ref "H11") (pin "V2") (pinfunction "IN3_V2") (pintype "input"))
      (node (ref "H12") (pin "F2") (pinfunction "IN1_F2") (pintype "input"))
      (node (ref "H12") (pin "J2") (pinfunction "IN3_J2") (pintype "input"))
      (node (ref "H12") (pin "M2") (pinfunction "IN1_M2") (pintype "input"))
      (node (ref "H12") (pin "P2") (pinfunction "IN3_P2") (pintype "input"))
      (node (ref "H12") (pin "T2") (pinfunction "IN1_T2") (pintype "input"))
      (node (ref "H12") (pin "V2") (pinfunction "IN3_V2") (pintype "input"))
    )
    (net (code "52") (name "+3V(52)") (class "Default")
      (node (ref "F21") (pin "U1") (pinfunction "P$1_U1") (pintype "passive"))
      (node (ref "H13") (pin "F2") (pinfunction "IN1_F2") (pintype "input"))
      (node (ref "H13") (pin "J2") (pinfunction "IN3_J2") (pintype "input"))
      (node (ref "H13") (pin "M2") (pinfunction "IN1_M2") (pintype "input"))
      (node (ref "H13") (pin "P2") (pinfunction "IN3_P2") (pintype "input"))
      (node (ref "H13") (pin "T2") (pinfunction "IN1_T2") (pintype "input"))
      (node (ref "H13") (pin "V2") (pinfunction "IN3_V2") (pintype "input"))
      (node (ref "H14") (pin "F2") (pinfunction "IN1_F2") (pintype "input"))
      (node (ref "H14") (pin "J2") (pinfunction "IN3_J2") (pintype "input"))
      (node (ref "H14") (pin "M2") (pinfunction "IN1_M2") (pintype "input"))
      (node (ref "H14") (pin "P2") (pinfunction "IN3_P2") (pintype "input"))
      (node (ref "H14") (pin "T2") (pinfunction "IN1_T2") (pintype "input"))
      (node (ref "H14") (pin "V2") (pinfunction "IN3_V2") (pintype "input"))
      (node (ref "J13") (pin "R1") (pinfunction "IN4_R1") (pintype "input"))
    )
    (net (code "53") (name "+3V(53)") (class "Default")
      (node (ref "F21") (pin "V1") (pinfunction "P$1_V1") (pintype "passive"))
      (node (ref "H15") (pin "F2") (pinfunction "IN1_F2") (pintype "input"))
      (node (ref "H15") (pin "J2") (pinfunction "IN3_J2") (pintype "input"))
      (node (ref "H15") (pin "M2") (pinfunction "IN1_M2") (pintype "input"))
      (node (ref "H15") (pin "P2") (pinfunction "IN3_P2") (pintype "input"))
      (node (ref "H15") (pin "T2") (pinfunction "IN1_T2") (pintype "input"))
      (node (ref "H15") (pin "V2") (pinfunction "IN3_V2") (pintype "input"))
      (node (ref "H16") (pin "F2") (pinfunction "IN1_F2") (pintype "input"))
      (node (ref "H16") (pin "J2") (pinfunction "IN3_J2") (pintype "input"))
      (node (ref "H16") (pin "M2") (pinfunction "IN1_M2") (pintype "input"))
      (node (ref "H16") (pin "P2") (pinfunction "IN3_P2") (pintype "input"))
      (node (ref "H16") (pin "T2") (pinfunction "IN1_T2") (pintype "input"))
      (node (ref "H16") (pin "V2") (pinfunction "IN3_V2") (pintype "input"))
    )
    (net (code "54") (name "+3V(54)") (class "Default")
      (node (ref "F22") (pin "V1") (pinfunction "P$1_V1") (pintype "passive"))
      (node (ref "H17") (pin "F2") (pinfunction "IN1_F2") (pintype "input"))
      (node (ref "H17") (pin "J2") (pinfunction "IN3_J2") (pintype "input"))
      (node (ref "H17") (pin "M2") (pinfunction "IN1_M2") (pintype "input"))
      (node (ref "H17") (pin "P2") (pinfunction "IN3_P2") (pintype "input"))
      (node (ref "H17") (pin "T2") (pinfunction "IN1_T2") (pintype "input"))
      (node (ref "H17") (pin "V2") (pinfunction "IN3_V2") (pintype "input"))
      (node (ref "H18") (pin "F2") (pinfunction "IN1_F2") (pintype "input"))
      (node (ref "H18") (pin "J2") (pinfunction "IN3_J2") (pintype "input"))
      (node (ref "H18") (pin "M2") (pinfunction "IN1_M2") (pintype "input"))
      (node (ref "H18") (pin "P2") (pinfunction "IN3_P2") (pintype "input"))
      (node (ref "H18") (pin "T2") (pinfunction "IN1_T2") (pintype "input"))
      (node (ref "H18") (pin "V2") (pinfunction "IN3_V2") (pintype "input"))
    )
    (net (code "55") (name "+3V(55)") (class "Default")
      (node (ref "E22") (pin "B1") (pinfunction "IN2_B1") (pintype "input"))
      (node (ref "E22") (pin "E1") (pinfunction "IN2_E1") (pintype "input"))
      (node (ref "E22") (pin "E2") (pinfunction "IN2_E2") (pintype "input"))
      (node (ref "E22") (pin "J1") (pinfunction "IN2_J1") (pintype "input"))
      (node (ref "E22") (pin "J2") (pinfunction "IN2_J2") (pintype "input"))
      (node (ref "F23") (pin "U1") (pinfunction "P$1_U1") (pintype "passive"))
      (node (ref "H19") (pin "F2") (pinfunction "IN1_F2") (pintype "input"))
      (node (ref "H19") (pin "J2") (pinfunction "IN3_J2") (pintype "input"))
      (node (ref "H19") (pin "M2") (pinfunction "IN1_M2") (pintype "input"))
      (node (ref "H19") (pin "P2") (pinfunction "IN3_P2") (pintype "input"))
      (node (ref "H19") (pin "T2") (pinfunction "IN1_T2") (pintype "input"))
      (node (ref "H19") (pin "V2") (pinfunction "IN3_V2") (pintype "input"))
      (node (ref "H20") (pin "F2") (pinfunction "IN1_F2") (pintype "input"))
      (node (ref "H20") (pin "J2") (pinfunction "IN3_J2") (pintype "input"))
      (node (ref "H20") (pin "M2") (pinfunction "IN1_M2") (pintype "input"))
      (node (ref "H20") (pin "P2") (pinfunction "IN3_P2") (pintype "input"))
    )
    (net (code "56") (name "+3V(56)") (class "Default")
      (node (ref "F23") (pin "V1") (pinfunction "P$1_V1") (pintype "passive"))
      (node (ref "J13") (pin "C1") (pinfunction "IN3_C1") (pintype "input"))
      (node (ref "J13") (pin "D1") (pinfunction "IN4_D1") (pintype "input"))
      (node (ref "J13") (pin "F2") (pinfunction "IN3_F2") (pintype "input"))
      (node (ref "J13") (pin "H2") (pinfunction "IN4_H2") (pintype "input"))
      (node (ref "J13") (pin "J1") (pinfunction "IN3_J1") (pintype "input"))
      (node (ref "J13") (pin "K1") (pinfunction "IN4_K1") (pintype "input"))
      (node (ref "J13") (pin "M2") (pinfunction "IN3_M2") (pintype "input"))
      (node (ref "J13") (pin "N2") (pinfunction "IN4_N2") (pintype "input"))
    )
    (net (code "57") (name "+3V(57)") (class "Default")
      (node (ref "C07") (pin "F2") (pinfunction "IN3_F2") (pintype "input"))
      (node (ref "C07") (pin "H2") (pinfunction "IN2_H2") (pintype "input"))
      (node (ref "C07") (pin "N2") (pinfunction "IN2_N2") (pintype "input"))
      (node (ref "C07") (pin "P2") (pinfunction "IN3_P2") (pintype "input"))
      (node (ref "C08") (pin "H2") (pinfunction "IN1_H2") (pintype "input"))
      (node (ref "C08") (pin "N2") (pinfunction "IN1_N2") (pintype "input"))
      (node (ref "C08") (pin "U2") (pinfunction "IN1_U2") (pintype "input"))
      (node (ref "C09") (pin "E1") (pinfunction "IN2_E1") (pintype "input"))
      (node (ref "C09") (pin "J1") (pinfunction "IN2_J1") (pintype "input"))
      (node (ref "C09") (pin "M1") (pinfunction "IN2_M1") (pintype "input"))
      (node (ref "C09") (pin "M2") (pinfunction "IN2_M2") (pintype "input"))
      (node (ref "C09") (pin "R1") (pinfunction "IN2_R1") (pintype "input"))
      (node (ref "C09") (pin "R2") (pinfunction "IN2_R2") (pintype "input"))
      (node (ref "D10") (pin "V1") (pinfunction "P$1_V1") (pintype "passive"))
      (node (ref "D11") (pin "K2") (pinfunction "R_K2") (pintype "input"))
      (node (ref "D11") (pin "N2") (pinfunction "S_N2") (pintype "input"))
    )
    (net (code "58") (name "+3V(58)") (class "Default")
      (node (ref "D07") (pin "E2") (pinfunction "IN2_E2") (pintype "input"))
      (node (ref "D07") (pin "H1") (pinfunction "IN1_H1") (pintype "input"))
      (node (ref "D07") (pin "H2") (pinfunction "IN1_H2") (pintype "input"))
      (node (ref "D07") (pin "L2") (pinfunction "IN1_L2") (pintype "input"))
      (node (ref "D07") (pin "P1") (pinfunction "IN1_P1") (pintype "input"))
      (node (ref "D07") (pin "P2") (pinfunction "IN1_P2") (pintype "input"))
      (node (ref "D07") (pin "U1") (pinfunction "P$1_U1") (pintype "passive"))
      (node (ref "D09") (pin "H1") (pinfunction "IN3_H1") (pintype "input"))
      (node (ref "D09") (pin "R1") (pinfunction "IN2_R1") (pintype "input"))
      (node (ref "D09") (pin "V2") (pinfunction "IN3_V2") (pintype "input"))
      (node (ref "D10") (pin "E2") (pinfunction "IN2_E2") (pintype "input"))
      (node (ref "E09") (pin "L2") (pinfunction "IN1_L2") (pintype "input"))
      (node (ref "E09") (pin "P1") (pinfunction "IN1_P1") (pintype "input"))
      (node (ref "E09") (pin "P2") (pinfunction "IN1_P2") (pintype "input"))
    )
    (net (code "59") (name "+3V(61)") (class "Default")
      (node (ref "C12") (pin "B1") (pinfunction "IN2_B1") (pintype "input"))
      (node (ref "C12") (pin "C1") (pinfunction "IN3_C1") (pintype "input"))
      (node (ref "C12") (pin "D1") (pinfunction "IN4_D1") (pintype "input"))
      (node (ref "C12") (pin "J1") (pinfunction "IN3_J1") (pintype "input"))
      (node (ref "C12") (pin "K1") (pinfunction "IN4_K1") (pintype "input"))
      (node (ref "C12") (pin "N2") (pinfunction "IN4_N2") (pintype "input"))
      (node (ref "C12") (pin "U1") (pinfunction "P$1_U1") (pintype "passive"))
    )
    (net (code "60") (name "+3V(62)") (class "Default")
      (node (ref "A05") (pin "U1") (pinfunction "P$1_U1") (pintype "passive"))
      (node (ref "B06") (pin "J2") (pinfunction "IN2_J2") (pintype "input"))
    )
    (net (code "61") (name "+3V(63)") (class "Default")
      (node (ref "B05") (pin "R1") (pinfunction "S_R1") (pintype "input"))
      (node (ref "B06") (pin "U2") (pinfunction "IN2_U2") (pintype "input"))
      (node (ref "B06") (pin "V1") (pinfunction "P$1_V1") (pintype "passive"))
    )
    (net (code "62") (name "+3V(64)") (class "Default")
      (node (ref "B04") (pin "F2") (pinfunction "IN3_F2") (pintype "input"))
      (node (ref "B05") (pin "D1") (pinfunction "S_D1") (pintype "input"))
      (node (ref "B06") (pin "U1") (pinfunction "P$1_U1") (pintype "passive"))
    )
    (net (code "63") (name "+3V(65)") (class "Default")
      (node (ref "A05") (pin "D1") (pinfunction "IN1_D1") (pintype "input"))
      (node (ref "A06") (pin "D2") (pinfunction "IN1_D2") (pintype "input"))
      (node (ref "A06") (pin "E1") (pinfunction "IN2_E1") (pintype "input"))
      (node (ref "A06") (pin "U1") (pinfunction "P$1_U1") (pintype "passive"))
      (node (ref "B05") (pin "F2") (pinfunction "S_F2") (pintype "input"))
      (node (ref "B05") (pin "N2") (pinfunction "S_N2") (pintype "input"))
    )
    (net (code "64") (name "+3V(66)") (class "Default")
      (node (ref "A05") (pin "T2") (pinfunction "IN1_T2") (pintype "input"))
      (node (ref "A06") (pin "R2") (pinfunction "IN2_R2") (pintype "input"))
      (node (ref "A11") (pin "U1") (pinfunction "P$1_U1") (pintype "passive"))
    )
    (net (code "65") (name "+3V(67)") (class "Default")
      (node (ref "A06") (pin "M1") (pinfunction "IN2_M1") (pintype "input"))
      (node (ref "A06") (pin "M2") (pinfunction "IN2_M2") (pintype "input"))
      (node (ref "A06") (pin "V1") (pinfunction "P$1_V1") (pintype "passive"))
      (node (ref "B04") (pin "V2") (pinfunction "IN3_V2") (pintype "input"))
    )
    (net (code "66") (name "+3V(68)") (class "Default")
      (node (ref "F08") (pin "P2") (pinfunction "IN2_P2") (pintype "input"))
      (node (ref "F09") (pin "H2") (pinfunction "IN8_H2") (pintype "input"))
      (node (ref "F09") (pin "U1") (pinfunction "P$1_U1") (pintype "passive"))
    )
    (net (code "67") (name "+3V(69)") (class "Default")
      (node (ref "E11") (pin "R1") (pinfunction "IN2_R1") (pintype "input"))
      (node (ref "F09") (pin "F1") (pinfunction "IN1_F1") (pintype "input"))
      (node (ref "F09") (pin "H1") (pinfunction "IN2_H1") (pintype "input"))
      (node (ref "F09") (pin "J1") (pinfunction "IN3_J1") (pintype "input"))
      (node (ref "F11") (pin "F1") (pinfunction "IN1_F1") (pintype "input"))
      (node (ref "F11") (pin "R1") (pinfunction "IN4_R1") (pintype "input"))
      (node (ref "F11") (pin "S2") (pinfunction "IN2_S2") (pintype "input"))
      (node (ref "F11") (pin "U1") (pinfunction "P$1_U1") (pintype "passive"))
    )
    (net (code "68") (name "+3VC01") (class "Default")
      (node (ref "C01") (pin "V2") (pinfunction "P$2_V2") (pintype "bidirectional"))
      (node (ref "HJ28") (pin "BU2") (pinfunction "P$1_BU2") (pintype "passive"))
    )
    (net (code "69") (name "-6V") (class "Default")
      (node (ref "A25") (pin "E2") (pinfunction "P$2_E2") (pintype "passive"))
      (node (ref "A26") (pin "E2") (pinfunction "P$2_E2") (pintype "passive"))
      (node (ref "A27") (pin "K1") (pinfunction "K1_K1") (pintype "passive"))
      (node (ref "A27") (pin "L2") (pinfunction "L2_L2") (pintype "passive"))
      (node (ref "A27") (pin "S1") (pinfunction "S1_S1") (pintype "passive"))
      (node (ref "A27") (pin "U2") (pinfunction "U2_U2") (pintype "passive"))
      (node (ref "A36") (pin "K1") (pinfunction "K1_K1") (pintype "passive"))
      (node (ref "A36") (pin "L2") (pinfunction "L2_L2") (pintype "passive"))
      (node (ref "A36") (pin "S1") (pinfunction "S1_S1") (pintype "passive"))
      (node (ref "A36") (pin "U2") (pinfunction "U2_U2") (pintype "passive"))
      (node (ref "A37") (pin "L2") (pinfunction "L2_L2") (pintype "passive"))
      (node (ref "A38") (pin "H2") (pinfunction "P$1_H2") (pintype "passive"))
      (node (ref "A38") (pin "J2") (pinfunction "P$3_J2") (pintype "passive"))
      (node (ref "A38") (pin "U2") (pinfunction "P$2_U2") (pintype "passive"))
      (node (ref "A38") (pin "V2") (pinfunction "P$1_V2") (pintype "passive"))
      (node (ref "A39") (pin "E2") (pinfunction "P$2_E2") (pintype "passive"))
      (node (ref "A39") (pin "J2") (pinfunction "P$3_J2") (pintype "passive"))
      (node (ref "A39") (pin "U2") (pinfunction "P$2_U2") (pintype "passive"))
      (node (ref "A39") (pin "V2") (pinfunction "P$1_V2") (pintype "passive"))
      (node (ref "AB01") (pin "BM2") (pinfunction "-6V_BM2") (pintype "power_in"))
      (node (ref "AB01") (pin "BN2") (pinfunction "-6V_BN2") (pintype "power_in"))
      (node (ref "AB01") (pin "BP2") (pinfunction "-6V_BP2") (pintype "power_in"))
      (node (ref "AB01") (pin "BR2") (pinfunction "-6V_BR2") (pintype "power_in"))
      (node (ref "AB01") (pin "BS2") (pinfunction "-6V_BS2") (pintype "power_in"))
      (node (ref "AB01") (pin "BT2") (pinfunction "-6V_BT2") (pintype "power_in"))
      (node (ref "AB01") (pin "BU2") (pinfunction "-6V_BU2") (pintype "power_in"))
      (node (ref "AB01") (pin "BV2") (pinfunction "-6V_BV2") (pintype "power_in"))
      (node (ref "AB02") (pin "BM2") (pinfunction "-6V_BM2") (pintype "power_in"))
      (node (ref "B25") (pin "E2") (pinfunction "P$2_E2") (pintype "passive"))
      (node (ref "B26") (pin "K1") (pinfunction "K1_K1") (pintype "passive"))
      (node (ref "B26") (pin "L2") (pinfunction "L2_L2") (pintype "passive"))
      (node (ref "B26") (pin "S1") (pinfunction "S1_S1") (pintype "passive"))
      (node (ref "B26") (pin "U2") (pinfunction "U2_U2") (pintype "passive"))
      (node (ref "B27") (pin "K1") (pinfunction "K1_K1") (pintype "passive"))
      (node (ref "B27") (pin "L2") (pinfunction "L2_L2") (pintype "passive"))
      (node (ref "B27") (pin "S1") (pinfunction "S1_S1") (pintype "passive"))
      (node (ref "B27") (pin "U2") (pinfunction "U2_U2") (pintype "passive"))
      (node (ref "B36") (pin "K1") (pinfunction "K1_K1") (pintype "passive"))
      (node (ref "B36") (pin "L2") (pinfunction "L2_L2") (pintype "passive"))
      (node (ref "B36") (pin "S1") (pinfunction "S1_S1") (pintype "passive"))
      (node (ref "B36") (pin "U2") (pinfunction "U2_U2") (pintype "passive"))
      (node (ref "B37") (pin "K1") (pinfunction "K1_K1") (pintype "passive"))
      (node (ref "B37") (pin "L2") (pinfunction "L2_L2") (pintype "passive"))
      (node (ref "B37") (pin "S1") (pinfunction "S1_S1") (pintype "passive"))
      (node (ref "B37") (pin "U2") (pinfunction "U2_U2") (pintype "passive"))
      (node (ref "B38") (pin "E2") (pinfunction "P$2_E2") (pintype "passive"))
      (node (ref "B38") (pin "V2") (pinfunction "P$1_V2") (pintype "passive"))
      (node (ref "B39") (pin "V2") (pinfunction "P$1_V2") (pintype "passive"))
    )
    (net (code "70") (name "-15V") (class "Default")
      (node (ref "A38") (pin "B2") (pinfunction "P$1_B2") (pintype "passive"))
      (node (ref "A39") (pin "B2") (pinfunction "P$1_B2") (pintype "passive"))
      (node (ref "B38") (pin "B2") (pinfunction "P$1_B2") (pintype "passive"))
      (node (ref "B39") (pin "B2") (pinfunction "P$1_B2") (pintype "passive"))
      (node (ref "D01") (pin "B2") (pinfunction "P$2_B2") (pintype "bidirectional"))
      (node (ref "D03") (pin "B2") (pinfunction "P$2_B2") (pintype "bidirectional"))
    )
    (net (code "71") (name "-30V") (class "Default")
      (node (ref "A27") (pin "V2") (pinfunction "V2_V2") (pintype "input"))
      (node (ref "A36") (pin "V2") (pinfunction "V2_V2") (pintype "input"))
      (node (ref "A37") (pin "V2") (pinfunction "V2_V2") (pintype "input"))
      (node (ref "A39") (pin "H2") (pinfunction "P$1_H2") (pintype "passive"))
      (node (ref "A39") (pin "M2") (pinfunction "P$1_M2") (pintype "passive"))
      (node (ref "AB01") (pin "AE2") (pinfunction "-30V_AE2") (pintype "power_in"))
      (node (ref "AB01") (pin "AF2") (pinfunction "-30V_AF2") (pintype "power_in"))
      (node (ref "AB01") (pin "AH2") (pinfunction "-30V_AH2") (pintype "power_in"))
      (node (ref "AB01") (pin "AJ2") (pinfunction "-30V_AJ2") (pintype "power_in"))
      (node (ref "AB01") (pin "AK2") (pinfunction "-30V_AK2") (pintype "power_in"))
      (node (ref "AB01") (pin "AL2") (pinfunction "-30V_AL2") (pintype "power_in"))
      (node (ref "AB01") (pin "AM2") (pinfunction "-30V_AM2") (pintype "power_in"))
      (node (ref "AB01") (pin "AN2") (pinfunction "-30V_AN2") (pintype "power_in"))
      (node (ref "AB02") (pin "BV2") (pinfunction "-30V_BV2") (pintype "power_in"))
      (node (ref "B26") (pin "V2") (pinfunction "V2_V2") (pintype "input"))
      (node (ref "B27") (pin "V2") (pinfunction "V2_V2") (pintype "input"))
      (node (ref "B36") (pin "V2") (pinfunction "V2_V2") (pintype "input"))
      (node (ref "B37") (pin "V2") (pinfunction "V2_V2") (pintype "input"))
      (node (ref "B38") (pin "H2") (pinfunction "P$1_H2") (pintype "passive"))
      (node (ref "B38") (pin "J2") (pinfunction "P$3_J2") (pintype "passive"))
      (node (ref "B38") (pin "U2") (pinfunction "P$2_U2") (pintype "passive"))
      (node (ref "B39") (pin "H2") (pinfunction "P$1_H2") (pintype "passive"))
      (node (ref "B39") (pin "J2") (pinfunction "P$3_J2") (pintype "passive"))
      (node (ref "B39") (pin "U2") (pinfunction "P$2_U2") (pintype "passive"))
      (node (ref "HJ23") (pin "AV2") (pinfunction "-30V_AV2") (pintype "power_in"))
      (node (ref "J12") (pin "V2") (pinfunction "-30V_V2") (pintype "power_in"))
    )
    (net (code "72") (name "0_TO_INT_ENAB_") (class "Default")
      (node (ref "E26") (pin "V2") (pinfunction "OUT_V2") (pintype "output"))
      (node (ref "E33") (pin "R1") (pinfunction "S_R1") (pintype "input"))
    )
    (net (code "73") (name "3_CYCLE") (class "Default")
      (node (ref "F22") (pin "T2") (pinfunction "IN1_T2") (pintype "input"))
      (node (ref "J20") (pin "J2") (pinfunction "OUT_J2") (pintype "output"))
    )
    (net (code "74") (name "60HZ_IN") (class "Default")
      (node (ref "J30") (pin "R2") (pinfunction "R2_R2") (pintype "input"))
    )
    (net (code "75") (name "AC00") (class "Default")
      (node (ref "C14") (pin "E1") (pinfunction "IN2_E1") (pintype "input"))
      (node (ref "D15") (pin "E1") (pinfunction "IN2_E1") (pintype "input"))
      (node (ref "D18") (pin "J2") (pinfunction "IN1_J2") (pintype "input"))
      (node (ref "E24") (pin "L1") (pinfunction "IN1_L1") (pintype "input"))
      (node (ref "EF34") (pin "BA1") (pinfunction "BA1_BA1") (pintype "output"))
      (node (ref "F33") (pin "N2") (pinfunction "IN4A_N2") (pintype "input"))
      (node (ref "H07") (pin "H2") (pinfunction "IN2_H2") (pintype "input"))
      (node (ref "HJ31") (pin "AE1") (pinfunction "AE1_AE1") (pintype "input"))
    )
    (net (code "76") (name "AC00_") (class "Default")
      (node (ref "D15") (pin "A1") (pinfunction "IN1_A1") (pintype "input"))
      (node (ref "E40") (pin "V2") (pinfunction "P$2_V2") (pintype "bidirectional"))
      (node (ref "EF34") (pin "BB1") (pinfunction "BB1_BB1") (pintype "output"))
      (node (ref "F24") (pin "K2") (pinfunction "IN1_K2") (pintype "input"))
    )
    (net (code "77") (name "AC01") (class "Default")
      (node (ref "C14") (pin "J2") (pinfunction "IN2_J2") (pintype "input"))
      (node (ref "D14") (pin "L1") (pinfunction "IN1_L1") (pintype "input"))
      (node (ref "D15") (pin "B1") (pinfunction "IN2_B1") (pintype "input"))
      (node (ref "EF34") (pin "AV1") (pinfunction "AV1_AV1") (pintype "output"))
      (node (ref "H07") (pin "N2") (pinfunction "IN2_N2") (pintype "input"))
      (node (ref "HJ31") (pin "BA1") (pinfunction "BA1_BA1") (pintype "input"))
    )
    (net (code "78") (name "AC01_") (class "Default")
      (node (ref "D15") (pin "D1") (pinfunction "IN1_D1") (pintype "input"))
      (node (ref "D16") (pin "H2") (pinfunction "IN1_H2") (pintype "input"))
      (node (ref "E40") (pin "T2") (pinfunction "P$2_T2") (pintype "bidirectional"))
      (node (ref "EF34") (pin "AV2") (pinfunction "AV2_AV2") (pintype "output"))
      (node (ref "F24") (pin "L2") (pinfunction "IN2_L2") (pintype "input"))
    )
    (net (code "79") (name "AC02") (class "Default")
      (node (ref "C14") (pin "R1") (pinfunction "IN2_R1") (pintype "input"))
      (node (ref "D16") (pin "J2") (pinfunction "IN2_J2") (pintype "input"))
      (node (ref "EF35") (pin "BA1") (pinfunction "BA1_BA1") (pintype "output"))
      (node (ref "H07") (pin "U2") (pinfunction "IN2_U2") (pintype "input"))
      (node (ref "HJ24") (pin "AE2") (pinfunction "AE2_AE2") (pintype "input"))
      (node (ref "HJ25") (pin "AE2") (pinfunction "AE2_AE2") (pintype "input"))
      (node (ref "HJ31") (pin "AV1") (pinfunction "AV1_AV1") (pintype "input"))
    )
    (net (code "80") (name "AC02_") (class "Default")
      (node (ref "D14") (pin "M1") (pinfunction "IN2_M1") (pintype "input"))
      (node (ref "D20") (pin "D1") (pinfunction "IN4_D1") (pintype "input"))
      (node (ref "E40") (pin "J1") (pinfunction "P$2_J1") (pintype "bidirectional"))
      (node (ref "EF35") (pin "BB1") (pinfunction "BB1_BB1") (pintype "output"))
      (node (ref "F24") (pin "M2") (pinfunction "IN3_M2") (pintype "input"))
    )
    (net (code "81") (name "AC03") (class "Default")
      (node (ref "C15") (pin "E1") (pinfunction "IN2_E1") (pintype "input"))
      (node (ref "EF35") (pin "AV1") (pinfunction "AV1_AV1") (pintype "output"))
      (node (ref "H08") (pin "H2") (pinfunction "IN2_H2") (pintype "input"))
      (node (ref "HJ24") (pin "AF2") (pinfunction "AF2_AF2") (pintype "input"))
      (node (ref "HJ25") (pin "AF2") (pinfunction "AF2_AF2") (pintype "input"))
      (node (ref "HJ31") (pin "AH1") (pinfunction "AH1_AH1") (pintype "input"))
    )
    (net (code "82") (name "AC03_") (class "Default")
      (node (ref "D19") (pin "K1") (pinfunction "IN1_K1") (pintype "input"))
      (node (ref "D20") (pin "C1") (pinfunction "IN3_C1") (pintype "input"))
      (node (ref "E40") (pin "H2") (pinfunction "P$2_H2") (pintype "bidirectional"))
      (node (ref "EF35") (pin "AV2") (pinfunction "AV2_AV2") (pintype "output"))
      (node (ref "F24") (pin "N2") (pinfunction "IN4_N2") (pintype "input"))
    )
    (net (code "83") (name "AC04") (class "Default")
      (node (ref "C15") (pin "J2") (pinfunction "IN2_J2") (pintype "input"))
      (node (ref "EF02") (pin "AP2") (pinfunction "AP2_AP2") (pintype "input"))
      (node (ref "EF36") (pin "BA1") (pinfunction "BA1_BA1") (pintype "output"))
      (node (ref "H08") (pin "N2") (pinfunction "IN2_N2") (pintype "input"))
      (node (ref "HJ24") (pin "AM2") (pinfunction "AM2_AM2") (pintype "input"))
      (node (ref "HJ25") (pin "AM2") (pinfunction "AM2_AM2") (pintype "input"))
      (node (ref "HJ28") (pin "AH1") (pinfunction "AH1_AH1") (pintype "input"))
      (node (ref "HJ31") (pin "AU2") (pinfunction "AU2_AU2") (pintype "input"))
    )
    (net (code "84") (name "AC04_") (class "Default")
      (node (ref "E40") (pin "M1") (pinfunction "P$2_M1") (pintype "bidirectional"))
      (node (ref "EF36") (pin "BB1") (pinfunction "BB1_BB1") (pintype "output"))
      (node (ref "F24") (pin "M1") (pinfunction "IN1_M1") (pintype "input"))
    )
    (net (code "85") (name "AC05") (class "Default")
      (node (ref "C15") (pin "R1") (pinfunction "IN2_R1") (pintype "input"))
      (node (ref "EF02") (pin "AR2") (pinfunction "AR2_AR2") (pintype "input"))
      (node (ref "EF36") (pin "AV1") (pinfunction "AV1_AV1") (pintype "output"))
      (node (ref "H08") (pin "U2") (pinfunction "IN2_U2") (pintype "input"))
      (node (ref "HJ24") (pin "AN2") (pinfunction "AN2_AN2") (pintype "input"))
      (node (ref "HJ25") (pin "AN2") (pinfunction "AN2_AN2") (pintype "input"))
      (node (ref "HJ28") (pin "AH2") (pinfunction "AH2_AH2") (pintype "input"))
      (node (ref "HJ31") (pin "AK1") (pinfunction "AK1_AK1") (pintype "input"))
    )
    (net (code "86") (name "AC05_") (class "Default")
      (node (ref "E40") (pin "B1") (pinfunction "P$2_B1") (pintype "bidirectional"))
      (node (ref "EF36") (pin "AV2") (pinfunction "AV2_AV2") (pintype "output"))
      (node (ref "F24") (pin "N1") (pinfunction "IN2_N1") (pintype "input"))
    )
    (net (code "87") (name "AC06") (class "Default")
      (node (ref "C16") (pin "E1") (pinfunction "IN2_E1") (pintype "input"))
      (node (ref "EF02") (pin "AL2") (pinfunction "AL2_AL2") (pintype "input"))
      (node (ref "EF37") (pin "BA1") (pinfunction "BA1_BA1") (pintype "output"))
      (node (ref "H09") (pin "H2") (pinfunction "IN2_H2") (pintype "input"))
      (node (ref "HJ24") (pin "AS2") (pinfunction "AS2_AS2") (pintype "input"))
      (node (ref "HJ25") (pin "AS2") (pinfunction "AS2_AS2") (pintype "input"))
      (node (ref "HJ28") (pin "AF1") (pinfunction "AF1_AF1") (pintype "input"))
      (node (ref "HJ31") (pin "AT2") (pinfunction "AT2_AT2") (pintype "input"))
    )
    (net (code "88") (name "AC06_") (class "Default")
      (node (ref "EF37") (pin "BB1") (pinfunction "BB1_BB1") (pintype "output"))
      (node (ref "F24") (pin "P1") (pinfunction "IN3_P1") (pintype "input"))
      (node (ref "F40") (pin "V2") (pinfunction "P$2_V2") (pintype "bidirectional"))
    )
    (net (code "89") (name "AC07") (class "Default")
      (node (ref "C16") (pin "J2") (pinfunction "IN2_J2") (pintype "input"))
      (node (ref "EF02") (pin "AM2") (pinfunction "AM2_AM2") (pintype "input"))
      (node (ref "EF37") (pin "AV1") (pinfunction "AV1_AV1") (pintype "output"))
      (node (ref "H09") (pin "N2") (pinfunction "IN2_N2") (pintype "input"))
      (node (ref "HJ24") (pin "AT2") (pinfunction "AT2_AT2") (pintype "input"))
      (node (ref "HJ25") (pin "AT2") (pinfunction "AT2_AT2") (pintype "input"))
      (node (ref "HJ28") (pin "AF2") (pinfunction "AF2_AF2") (pintype "input"))
      (node (ref "HJ31") (pin "AL1") (pinfunction "AL1_AL1") (pintype "input"))
    )
    (net (code "90") (name "AC07_") (class "Default")
      (node (ref "EF37") (pin "AV2") (pinfunction "AV2_AV2") (pintype "output"))
      (node (ref "F24") (pin "R1") (pinfunction "IN4_R1") (pintype "input"))
      (node (ref "F40") (pin "T2") (pinfunction "P$2_T2") (pintype "bidirectional"))
    )
    (net (code "91") (name "AC08") (class "Default")
      (node (ref "C16") (pin "R1") (pinfunction "IN2_R1") (pintype "input"))
      (node (ref "EF02") (pin "AU2") (pinfunction "AU2_AU2") (pintype "input"))
      (node (ref "EF38") (pin "BA1") (pinfunction "BA1_BA1") (pintype "output"))
      (node (ref "H09") (pin "U2") (pinfunction "IN2_U2") (pintype "input"))
      (node (ref "HJ24") (pin "BD2") (pinfunction "BD2_BD2") (pintype "input"))
      (node (ref "HJ25") (pin "BD2") (pinfunction "BD2_BD2") (pintype "input"))
      (node (ref "HJ28") (pin "AE1") (pinfunction "AE1_AE1") (pintype "input"))
      (node (ref "HJ31") (pin "AR1") (pinfunction "AR1_AR1") (pintype "input"))
    )
    (net (code "92") (name "AC08_") (class "Default")
      (node (ref "EF38") (pin "BB1") (pinfunction "BB1_BB1") (pintype "output"))
      (node (ref "F24") (pin "R2") (pinfunction "IN1_R2") (pintype "input"))
      (node (ref "F40") (pin "J1") (pinfunction "P$2_J1") (pintype "bidirectional"))
    )
    (net (code "93") (name "AC09") (class "Default")
      (node (ref "C17") (pin "E1") (pinfunction "IN2_E1") (pintype "input"))
      (node (ref "EF02") (pin "AS2") (pinfunction "AS2_AS2") (pintype "input"))
      (node (ref "EF38") (pin "AV1") (pinfunction "AV1_AV1") (pintype "output"))
      (node (ref "H10") (pin "H2") (pinfunction "IN2_H2") (pintype "input"))
      (node (ref "HJ24") (pin "BE2") (pinfunction "BE2_BE2") (pintype "input"))
      (node (ref "HJ25") (pin "BE2") (pinfunction "BE2_BE2") (pintype "input"))
      (node (ref "HJ28") (pin "AE2") (pinfunction "AE2_AE2") (pintype "input"))
      (node (ref "HJ31") (pin "AN2") (pinfunction "AN2_AN2") (pintype "input"))
    )
    (net (code "94") (name "AC09_") (class "Default")
      (node (ref "EF38") (pin "AV2") (pinfunction "AV2_AV2") (pintype "output"))
      (node (ref "F24") (pin "S2") (pinfunction "IN2_S2") (pintype "input"))
      (node (ref "F40") (pin "H2") (pinfunction "P$2_H2") (pintype "bidirectional"))
    )
    (net (code "95") (name "AC10") (class "Default")
      (node (ref "C17") (pin "J2") (pinfunction "IN2_J2") (pintype "input"))
      (node (ref "EF02") (pin "AT2") (pinfunction "AT2_AT2") (pintype "input"))
      (node (ref "EF39") (pin "BA1") (pinfunction "BA1_BA1") (pintype "output"))
      (node (ref "H10") (pin "N2") (pinfunction "IN2_N2") (pintype "input"))
      (node (ref "HJ24") (pin "BH2") (pinfunction "BH2_BH2") (pintype "input"))
      (node (ref "HJ25") (pin "BH2") (pinfunction "BH2_BH2") (pintype "input"))
      (node (ref "HJ28") (pin "AD1") (pinfunction "AD1_AD1") (pintype "input"))
      (node (ref "HJ31") (pin "AR2") (pinfunction "AR2_AR2") (pintype "input"))
    )
    (net (code "96") (name "AC10_") (class "Default")
      (node (ref "EF39") (pin "BB1") (pinfunction "BB1_BB1") (pintype "output"))
      (node (ref "F24") (pin "T2") (pinfunction "IN3_T2") (pintype "input"))
      (node (ref "F40") (pin "M1") (pinfunction "P$2_M1") (pintype "bidirectional"))
    )
    (net (code "97") (name "AC11") (class "Default")
      (node (ref "C17") (pin "R1") (pinfunction "IN2_R1") (pintype "input"))
      (node (ref "EF02") (pin "AU1") (pinfunction "AU1_AU1") (pintype "input"))
      (node (ref "EF39") (pin "AV1") (pinfunction "AV1_AV1") (pintype "output"))
      (node (ref "H10") (pin "U2") (pinfunction "IN2_U2") (pintype "input"))
      (node (ref "HJ24") (pin "BJ2") (pinfunction "BJ2_BJ2") (pintype "input"))
      (node (ref "HJ25") (pin "BJ2") (pinfunction "BJ2_BJ2") (pintype "input"))
      (node (ref "HJ28") (pin "AD2") (pinfunction "AD2_AD2") (pintype "input"))
      (node (ref "HJ31") (pin "AP1") (pinfunction "AP1_AP1") (pintype "input"))
    )
    (net (code "98") (name "AC11_") (class "Default")
      (node (ref "EF39") (pin "AV2") (pinfunction "AV2_AV2") (pintype "output"))
      (node (ref "F24") (pin "U2") (pinfunction "IN4_U2") (pintype "input"))
      (node (ref "F40") (pin "B1") (pinfunction "P$2_B1") (pintype "bidirectional"))
    )
    (net (code "99") (name "ACBAR_ENABLE") (class "Default")
      (node (ref "E32") (pin "V2") (pinfunction "OUT_V2") (pintype "open_collector"))
      (node (ref "EF34") (pin "BJ2") (pinfunction "BJ2_BJ2") (pintype "input"))
      (node (ref "EF35") (pin "BJ2") (pinfunction "BJ2_BJ2") (pintype "input"))
      (node (ref "EF36") (pin "BJ2") (pinfunction "BJ2_BJ2") (pintype "input"))
      (node (ref "EF37") (pin "BJ2") (pinfunction "BJ2_BJ2") (pintype "input"))
      (node (ref "EF38") (pin "BJ2") (pinfunction "BJ2_BJ2") (pintype "input"))
      (node (ref "EF39") (pin "BJ2") (pinfunction "BJ2_BJ2") (pintype "input"))
    )
    (net (code "100") (name "AC_CLEAR") (class "Default")
      (node (ref "F29") (pin "J2") (pinfunction "IN2_J2") (pintype "input"))
      (node (ref "J15") (pin "L1") (pinfunction "OUT_L1") (pintype "output"))
    )
    (net (code "101") (name "AC_CLEAR_") (class "Default")
      (node (ref "E30") (pin "K2") (pinfunction "IN2B_K2") (pintype "input"))
      (node (ref "F29") (pin "K2") (pinfunction "OUT_K2") (pintype "output"))
    )
    (net (code "102") (name "AC_ENABLE") (class "Default")
      (node (ref "E32") (pin "S1") (pinfunction "OUT_S1") (pintype "open_collector"))
      (node (ref "EF34") (pin "BH2") (pinfunction "BH2_BH2") (pintype "input"))
      (node (ref "EF35") (pin "BH2") (pinfunction "BH2_BH2") (pintype "input"))
      (node (ref "EF36") (pin "BH2") (pinfunction "BH2_BH2") (pintype "input"))
      (node (ref "EF37") (pin "BH2") (pinfunction "BH2_BH2") (pintype "input"))
      (node (ref "EF38") (pin "BH2") (pinfunction "BH2_BH2") (pintype "input"))
      (node (ref "EF39") (pin "BH2") (pinfunction "BH2_BH2") (pintype "input"))
    )
    (net (code "103") (name "AC_LOAD") (class "Default")
      (node (ref "E32") (pin "P2") (pinfunction "OUT_P2") (pintype "open_collector"))
      (node (ref "E33") (pin "S2") (pinfunction "C_S2") (pintype "input"))
      (node (ref "EF34") (pin "AU1") (pinfunction "AU1_AU1") (pintype "input"))
      (node (ref "EF35") (pin "AU1") (pinfunction "AU1_AU1") (pintype "input"))
      (node (ref "EF36") (pin "AU1") (pinfunction "AU1_AU1") (pintype "input"))
      (node (ref "EF37") (pin "AU1") (pinfunction "AU1_AU1") (pintype "input"))
      (node (ref "EF38") (pin "AU1") (pinfunction "AU1_AU1") (pintype "input"))
      (node (ref "EF39") (pin "AU1") (pinfunction "AU1_AU1") (pintype "input"))
    )
    (net (code "104") (name "AC_TO_MQ_ENABLE") (class "Default")
      (node (ref "C14") (pin "D1") (pinfunction "IN1_D1") (pintype "input"))
      (node (ref "C14") (pin "H2") (pinfunction "IN1_H2") (pintype "input"))
      (node (ref "C14") (pin "P1") (pinfunction "IN1_P1") (pintype "input"))
      (node (ref "C15") (pin "D1") (pinfunction "IN1_D1") (pintype "input"))
      (node (ref "C15") (pin "H2") (pinfunction "IN1_H2") (pintype "input"))
      (node (ref "C15") (pin "P1") (pinfunction "IN1_P1") (pintype "input"))
      (node (ref "C16") (pin "D1") (pinfunction "IN1_D1") (pintype "input"))
      (node (ref "C16") (pin "H2") (pinfunction "IN1_H2") (pintype "input"))
      (node (ref "C16") (pin "P1") (pinfunction "IN1_P1") (pintype "input"))
      (node (ref "C17") (pin "D1") (pinfunction "IN1_D1") (pintype "input"))
      (node (ref "C17") (pin "H2") (pinfunction "IN1_H2") (pintype "input"))
      (node (ref "C17") (pin "P1") (pinfunction "IN1_P1") (pintype "input"))
      (node (ref "D15") (pin "S1") (pinfunction "OUT_S1") (pintype "output"))
    )
    (net (code "105") (name "AC_TO_MQ_ENABLE_") (class "Default")
      (node (ref "D15") (pin "R1") (pinfunction "IN2_R1") (pintype "input"))
      (node (ref "D21") (pin "L1") (pinfunction "OUT_L1") (pintype "output"))
      (node (ref "E30") (pin "F2") (pinfunction "IN1C_F2") (pintype "input"))
    )
    (net (code "106") (name "ADDER00") (class "Default")
      (node (ref "EF34") (pin "AE2") (pinfunction "AE2_AE2") (pintype "output"))
      (node (ref "EF35") (pin "AB1") (pinfunction "AB1_AB1") (pintype "input"))
      (node (ref "EF39") (pin "AJ2") (pinfunction "AJ2_AJ2") (pintype "input"))
      (node (ref "F33") (pin "K1") (pinfunction "IN4A_K1") (pintype "input"))
    )
    (net (code "107") (name "ADDER01") (class "Default")
      (node (ref "EF34") (pin "AF1") (pinfunction "AF1_AF1") (pintype "output"))
      (node (ref "EF35") (pin "AC1") (pinfunction "AC1_AC1") (pintype "input"))
      (node (ref "F33") (pin "M1") (pinfunction "IN5A_M1") (pintype "input"))
    )
    (net (code "108") (name "ADDER02") (class "Default")
      (node (ref "EF34") (pin "AH2") (pinfunction "AH2_AH2") (pintype "input"))
      (node (ref "EF35") (pin "AE2") (pinfunction "AE2_AE2") (pintype "output"))
      (node (ref "EF35") (pin "BB2") (pinfunction "BB2_BB2") (pintype "input"))
      (node (ref "EF36") (pin "AB1") (pinfunction "AB1_AB1") (pintype "input"))
    )
    (net (code "109") (name "ADDER03") (class "Default")
      (node (ref "EF34") (pin "AJ2") (pinfunction "AJ2_AJ2") (pintype "input"))
      (node (ref "EF35") (pin "AF1") (pinfunction "AF1_AF1") (pintype "output"))
      (node (ref "EF36") (pin "AC1") (pinfunction "AC1_AC1") (pintype "input"))
    )
    (net (code "110") (name "ADDER04") (class "Default")
      (node (ref "EF35") (pin "AH2") (pinfunction "AH2_AH2") (pintype "input"))
      (node (ref "EF36") (pin "AE2") (pinfunction "AE2_AE2") (pintype "output"))
      (node (ref "EF36") (pin "BB2") (pinfunction "BB2_BB2") (pintype "input"))
      (node (ref "EF37") (pin "AB1") (pinfunction "AB1_AB1") (pintype "input"))
    )
    (net (code "111") (name "ADDER05") (class "Default")
      (node (ref "EF35") (pin "AJ2") (pinfunction "AJ2_AJ2") (pintype "input"))
      (node (ref "EF36") (pin "AF1") (pinfunction "AF1_AF1") (pintype "output"))
      (node (ref "EF37") (pin "AC1") (pinfunction "AC1_AC1") (pintype "input"))
    )
    (net (code "112") (name "ADDER06") (class "Default")
      (node (ref "EF36") (pin "AH2") (pinfunction "AH2_AH2") (pintype "input"))
      (node (ref "EF37") (pin "AE2") (pinfunction "AE2_AE2") (pintype "output"))
      (node (ref "EF37") (pin "BB2") (pinfunction "BB2_BB2") (pintype "input"))
      (node (ref "EF38") (pin "AB1") (pinfunction "AB1_AB1") (pintype "input"))
    )
    (net (code "113") (name "ADDER07") (class "Default")
      (node (ref "EF36") (pin "AJ2") (pinfunction "AJ2_AJ2") (pintype "input"))
      (node (ref "EF37") (pin "AF1") (pinfunction "AF1_AF1") (pintype "output"))
      (node (ref "EF38") (pin "AC1") (pinfunction "AC1_AC1") (pintype "input"))
    )
    (net (code "114") (name "ADDER08") (class "Default")
      (node (ref "EF37") (pin "AH2") (pinfunction "AH2_AH2") (pintype "input"))
      (node (ref "EF38") (pin "AE2") (pinfunction "AE2_AE2") (pintype "output"))
      (node (ref "EF38") (pin "BB2") (pinfunction "BB2_BB2") (pintype "input"))
      (node (ref "EF39") (pin "AB1") (pinfunction "AB1_AB1") (pintype "input"))
    )
    (net (code "115") (name "ADDER09") (class "Default")
      (node (ref "EF37") (pin "AJ2") (pinfunction "AJ2_AJ2") (pintype "input"))
      (node (ref "EF38") (pin "AF1") (pinfunction "AF1_AF1") (pintype "output"))
      (node (ref "EF39") (pin "AC1") (pinfunction "AC1_AC1") (pintype "input"))
    )
    (net (code "116") (name "ADDER10") (class "Default")
      (node (ref "EF38") (pin "AH2") (pinfunction "AH2_AH2") (pintype "input"))
      (node (ref "EF39") (pin "AE2") (pinfunction "AE2_AE2") (pintype "output"))
      (node (ref "EF39") (pin "BB2") (pinfunction "BB2_BB2") (pintype "input"))
      (node (ref "F33") (pin "E1") (pinfunction "IN2A_E1") (pintype "input"))
    )
    (net (code "117") (name "ADDER11") (class "Default")
      (node (ref "EF34") (pin "AB1") (pinfunction "AB1_AB1") (pintype "input"))
      (node (ref "EF38") (pin "AJ2") (pinfunction "AJ2_AJ2") (pintype "input"))
      (node (ref "EF39") (pin "AF1") (pinfunction "AF1_AF1") (pintype "output"))
      (node (ref "F32") (pin "P1") (pinfunction "IN1_P1") (pintype "input"))
    )
    (net (code "118") (name "ADDER11_") (class "Default")
      (node (ref "C14") (pin "B1") (pinfunction "IN2_B1") (pintype "input"))
      (node (ref "F28") (pin "P1") (pinfunction "IN1_P1") (pintype "input"))
      (node (ref "F32") (pin "S1") (pinfunction "OUT_S1") (pintype "output"))
    )
    (net (code "119") (name "ADDER_L") (class "Default")
      (node (ref "C18") (pin "V2") (pinfunction "OUT_V2") (pintype "output"))
      (node (ref "D19") (pin "F1") (pinfunction "IN2_F1") (pintype "input"))
      (node (ref "D23") (pin "L2") (pinfunction "IN3A_L2") (pintype "input"))
    )
    (net (code "120") (name "ADDER_L_") (class "Default")
      (node (ref "C18") (pin "T2") (pinfunction "IN1_T2") (pintype "input"))
      (node (ref "D23") (pin "K2") (pinfunction "IN2B_K2") (pintype "input"))
      (node (ref "E24") (pin "B1") (pinfunction "IN2_B1") (pintype "input"))
      (node (ref "EF34") (pin "AC1") (pinfunction "AC1_AC1") (pintype "input"))
      (node (ref "EF34") (pin "BB2") (pinfunction "BB2_BB2") (pintype "input"))
      (node (ref "F33") (pin "H1") (pinfunction "IN3A_H1") (pintype "input"))
      (node (ref "F33") (pin "V2") (pinfunction "OUT_V2") (pintype "output"))
    )
    (net (code "121") (name "ADD_") (class "Default")
      (node (ref "E32") (pin "P1") (pinfunction "IN3_P1") (pintype "input"))
      (node (ref "F28") (pin "D1") (pinfunction "OUT_D1") (pintype "output"))
      (node (ref "F31") (pin "A1") (pinfunction "IN1_A1") (pintype "input"))
    )
    (net (code "122") (name "ADD_ACCEPTED_") (class "Default")
      (node (ref "E33") (pin "E1") (pinfunction "1_E1") (pintype "output"))
      (node (ref "H20") (pin "N2") (pinfunction "IN2_N2") (pintype "input"))
    )
    (net (code "123") (name "AND") (class "Default")
      (node (ref "E22") (pin "C1") (pinfunction "OUT_C1") (pintype "output"))
      (node (ref "F26") (pin "P1") (pinfunction "IN1_P1") (pintype "input"))
    )
    (net (code "124") (name "AND_") (class "Default")
      (node (ref "D40") (pin "M2") (pinfunction "P$2_M2") (pintype "bidirectional"))
      (node (ref "E21") (pin "H2") (pinfunction "OUT_H2") (pintype "output"))
      (node (ref "E22") (pin "A1") (pinfunction "IN1_A1") (pintype "input"))
      (node (ref "F26") (pin "T2") (pinfunction "IN1_T2") (pintype "input"))
    )
    (net (code "125") (name "AND_ENABLE") (class "Default")
      (node (ref "E31") (pin "V2") (pinfunction "OUT_V2") (pintype "open_collector"))
      (node (ref "EF34") (pin "AA1") (pinfunction "AA1_AA1") (pintype "input"))
      (node (ref "EF35") (pin "AA1") (pinfunction "AA1_AA1") (pintype "input"))
      (node (ref "EF36") (pin "AA1") (pinfunction "AA1_AA1") (pintype "input"))
      (node (ref "EF37") (pin "AA1") (pinfunction "AA1_AA1") (pintype "input"))
      (node (ref "EF38") (pin "AA1") (pinfunction "AA1_AA1") (pintype "input"))
      (node (ref "EF39") (pin "AA1") (pinfunction "AA1_AA1") (pintype "input"))
    )
    (net (code "126") (name "AND_ENABLE_") (class "Default")
      (node (ref "E31") (pin "R2") (pinfunction "IN1_R2") (pintype "input"))
      (node (ref "E32") (pin "M1") (pinfunction "IN1_M1") (pintype "input"))
      (node (ref "F26") (pin "U1") (pinfunction "OUT_U1") (pintype "output"))
    )
    (net (code "127") (name "ASR_ENABLE") (class "Default")
      (node (ref "D15") (pin "V2") (pinfunction "OUT_V2") (pintype "output"))
      (node (ref "D18") (pin "K2") (pinfunction "IN2_K2") (pintype "input"))
      (node (ref "F33") (pin "R2") (pinfunction "IN4C_R2") (pintype "input"))
    )
    (net (code "128") (name "ASR_L_SET_") (class "Default")
      (node (ref "D18") (pin "M2") (pinfunction "OUT_M2") (pintype "output"))
      (node (ref "F33") (pin "B1") (pinfunction "IN1B_B1") (pintype "input"))
    )
    (net (code "129") (name "AUTO_INDEX_") (class "Default")
      (node (ref "F27") (pin "K2") (pinfunction "IN1_K2") (pintype "input"))
      (node (ref "F27") (pin "S1") (pinfunction "OUT_S1") (pintype "output"))
    )
    (net (code "130") (name "BA") (class "Default")
      (node (ref "D01") (pin "R2") (pinfunction "P$2_R2") (pintype "bidirectional"))
      (node (ref "HJ26") (pin "BP2") (pinfunction "BP2_BP2") (pintype "output"))
    )
    (net (code "131") (name "BA_") (class "Default")
      (node (ref "D01") (pin "P2") (pinfunction "P$2_P2") (pintype "bidirectional"))
      (node (ref "HJ26") (pin "BS1") (pinfunction "BS1_BS1") (pintype "output"))
    )
    (net (code "132") (name "BB") (class "Default")
      (node (ref "D01") (pin "T2") (pinfunction "P$2_T2") (pintype "bidirectional"))
      (node (ref "HJ26") (pin "BU2") (pinfunction "BU2_BU2") (pintype "output"))
    )
    (net (code "133") (name "BB_") (class "Default")
      (node (ref "D01") (pin "S2") (pinfunction "P$2_S2") (pintype "bidirectional"))
      (node (ref "HJ26") (pin "BR1") (pinfunction "BR1_BR1") (pintype "output"))
    )
    (net (code "134") (name "BB_FIELD") (class "Default")
      (node (ref "C12") (pin "E1") (pinfunction "OUT_E1") (pintype "open_collector"))
      (node (ref "C25") (pin "D2") (pinfunction "D2_D2") (pintype "input"))
      (node (ref "C26") (pin "D2") (pinfunction "D2_D2") (pintype "input"))
      (node (ref "D25") (pin "D2") (pinfunction "D2_D2") (pintype "input"))
      (node (ref "D26") (pin "D2") (pinfunction "D2_D2") (pintype "input"))
    )
    (net (code "135") (name "BB_FIELD_") (class "Default")
      (node (ref "B30") (pin "L1") (pinfunction "OUT_L1") (pintype "open_collector"))
      (node (ref "C32") (pin "D2") (pinfunction "D2_D2") (pintype "input"))
      (node (ref "C33") (pin "D2") (pinfunction "D2_D2") (pintype "input"))
      (node (ref "D32") (pin "D2") (pinfunction "D2_D2") (pintype "input"))
      (node (ref "D33") (pin "D2") (pinfunction "D2_D2") (pintype "input"))
    )
    (net (code "136") (name "BB_LEFT_SHIFT") (class "Default")
      (node (ref "C16") (pin "D2") (pinfunction "IN1_D2") (pintype "input"))
      (node (ref "C16") (pin "L1") (pinfunction "IN1_L1") (pintype "input"))
      (node (ref "C16") (pin "P2") (pinfunction "IN1_P2") (pintype "input"))
      (node (ref "C17") (pin "D2") (pinfunction "IN1_D2") (pintype "input"))
      (node (ref "C17") (pin "L1") (pinfunction "IN1_L1") (pintype "input"))
      (node (ref "C17") (pin "P2") (pinfunction "IN1_P2") (pintype "input"))
      (node (ref "D12") (pin "V2") (pinfunction "OUT_V2") (pintype "output"))
    )
    (net (code "137") (name "BF0") (class "Default")
      (node (ref "A16") (pin "E2") (pinfunction "IN2_E2") (pintype "input"))
      (node (ref "B18") (pin "P2") (pinfunction "1_P2") (pintype "output"))
    )
    (net (code "138") (name "BF1") (class "Default")
      (node (ref "A16") (pin "M1") (pinfunction "IN2_M1") (pintype "input"))
      (node (ref "B18") (pin "S1") (pinfunction "1_S1") (pintype "output"))
    )
    (net (code "139") (name "BF2") (class "Default")
      (node (ref "A16") (pin "R2") (pinfunction "IN2_R2") (pintype "input"))
      (node (ref "B18") (pin "V2") (pinfunction "1_V2") (pintype "output"))
    )
    (net (code "140") (name "BF_ENABLE") (class "Default")
      (node (ref "A16") (pin "D2") (pinfunction "IN1_D2") (pintype "input"))
      (node (ref "A16") (pin "L1") (pinfunction "IN1_L1") (pintype "input"))
      (node (ref "A16") (pin "P2") (pinfunction "IN1_P2") (pintype "input"))
      (node (ref "B11") (pin "M1") (pinfunction "0_M1") (pintype "output"))
    )
    (net (code "141") (name "BIOP1") (class "Default")
      (node (ref "E09") (pin "N2") (pinfunction "OUT_N2") (pintype "output"))
      (node (ref "J33") (pin "F2") (pinfunction "F2_F2") (pintype "input"))
    )
    (net (code "142") (name "BIOP2") (class "Default")
      (node (ref "E09") (pin "S1") (pinfunction "OUT_S1") (pintype "output"))
      (node (ref "J33") (pin "H2") (pinfunction "H2_H2") (pintype "input"))
    )
    (net (code "143") (name "BIOP4") (class "Default")
      (node (ref "E09") (pin "S2") (pinfunction "OUT_S2") (pintype "output"))
      (node (ref "J33") (pin "F1") (pinfunction "F1_F1") (pintype "input"))
    )
    (net (code "144") (name "BMA00") (class "Default")
      (node (ref "B14") (pin "E1") (pinfunction "OUT_E1") (pintype "open_collector"))
      (node (ref "H01") (pin "K2") (pinfunction "P$2_K2") (pintype "bidirectional"))
    )
    (net (code "145") (name "BMA01") (class "Default")
      (node (ref "B14") (pin "J2") (pinfunction "OUT_J2") (pintype "open_collector"))
      (node (ref "H01") (pin "M2") (pinfunction "P$2_M2") (pintype "bidirectional"))
    )
    (net (code "146") (name "BMA02") (class "Default")
      (node (ref "B14") (pin "L1") (pinfunction "OUT_L1") (pintype "open_collector"))
      (node (ref "H01") (pin "P2") (pinfunction "P$2_P2") (pintype "bidirectional"))
    )
    (net (code "147") (name "BMA03") (class "Default")
      (node (ref "B14") (pin "P2") (pinfunction "OUT_P2") (pintype "open_collector"))
      (node (ref "H01") (pin "S2") (pinfunction "P$2_S2") (pintype "bidirectional"))
    )
    (net (code "148") (name "BMA04") (class "Default")
      (node (ref "B14") (pin "S1") (pinfunction "OUT_S1") (pintype "open_collector"))
      (node (ref "H01") (pin "T2") (pinfunction "P$2_T2") (pintype "bidirectional"))
    )
    (net (code "149") (name "BMA05") (class "Default")
      (node (ref "B14") (pin "V2") (pinfunction "OUT_V2") (pintype "open_collector"))
      (node (ref "H01") (pin "V2") (pinfunction "P$2_V2") (pintype "bidirectional"))
    )
    (net (code "150") (name "BMA06") (class "Default")
      (node (ref "B15") (pin "E1") (pinfunction "OUT_E1") (pintype "open_collector"))
      (node (ref "H02") (pin "D2") (pinfunction "P$2_D2") (pintype "bidirectional"))
    )
    (net (code "151") (name "BMA07") (class "Default")
      (node (ref "B15") (pin "J2") (pinfunction "OUT_J2") (pintype "open_collector"))
      (node (ref "H02") (pin "E2") (pinfunction "P$2_E2") (pintype "bidirectional"))
    )
    (net (code "152") (name "BMA08") (class "Default")
      (node (ref "B15") (pin "L1") (pinfunction "OUT_L1") (pintype "open_collector"))
      (node (ref "H02") (pin "H2") (pinfunction "P$2_H2") (pintype "bidirectional"))
    )
    (net (code "153") (name "BMA09") (class "Default")
      (node (ref "B15") (pin "P2") (pinfunction "OUT_P2") (pintype "open_collector"))
      (node (ref "H02") (pin "K2") (pinfunction "P$2_K2") (pintype "bidirectional"))
    )
    (net (code "154") (name "BMA10") (class "Default")
      (node (ref "B15") (pin "S1") (pinfunction "OUT_S1") (pintype "open_collector"))
      (node (ref "H02") (pin "M2") (pinfunction "P$2_M2") (pintype "bidirectional"))
    )
    (net (code "155") (name "BMA11") (class "Default")
      (node (ref "B15") (pin "V2") (pinfunction "OUT_V2") (pintype "open_collector"))
      (node (ref "H02") (pin "P2") (pinfunction "P$2_P2") (pintype "bidirectional"))
    )
    (net (code "156") (name "BREAK") (class "Default")
      (node (ref "E11") (pin "T2") (pinfunction "IN1_T2") (pintype "input"))
      (node (ref "E23") (pin "V2") (pinfunction "1_V2") (pintype "output"))
      (node (ref "E27") (pin "S2") (pinfunction "IN4D_S2") (pintype "input"))
      (node (ref "E29") (pin "L2") (pinfunction "IN3A_L2") (pintype "input"))
      (node (ref "F28") (pin "L1") (pinfunction "IN2_L1") (pintype "input"))
    )
    (net (code "157") (name "BREAK_") (class "Default")
      (node (ref "D40") (pin "E2") (pinfunction "P$2_E2") (pintype "bidirectional"))
      (node (ref "E23") (pin "V1") (pinfunction "0_V1") (pintype "output"))
      (node (ref "H20") (pin "H2") (pinfunction "IN2_H2") (pintype "input"))
    )
    (net (code "158") (name "BREAK_OK") (class "Default")
      (node (ref "F22") (pin "N1") (pinfunction "OUT_N1") (pintype "output"))
      (node (ref "F22") (pin "P1") (pinfunction "IN1_P1") (pintype "input"))
      (node (ref "F22") (pin "U2") (pinfunction "IN2_U2") (pintype "input"))
      (node (ref "F29") (pin "M1") (pinfunction "IN2_M1") (pintype "input"))
    )
    (net (code "159") (name "BREAK_OK_") (class "Default")
      (node (ref "E33") (pin "C1") (pinfunction "D_C1") (pintype "input"))
      (node (ref "F22") (pin "L1") (pinfunction "IN1_L1") (pintype "input"))
      (node (ref "F23") (pin "N1") (pinfunction "IN2_N1") (pintype "input"))
      (node (ref "F23") (pin "P2") (pinfunction "OUT_P2") (pintype "output"))
    )
    (net (code "160") (name "BRK_RQST") (class "Default")
      (node (ref "E20") (pin "M2") (pinfunction "D_M2") (pintype "input"))
      (node (ref "J15") (pin "S1") (pinfunction "OUT_S1") (pintype "output"))
    )
    (net (code "161") (name "BRK_SYNC") (class "Default")
      (node (ref "E20") (pin "P2") (pinfunction "1_P2") (pintype "output"))
      (node (ref "F23") (pin "L2") (pinfunction "IN2_L2") (pintype "input"))
    )
    (net (code "162") (name "BSTLR") (class "Default")
      (node (ref "C07") (pin "S2") (pinfunction "OUT_S2") (pintype "output"))
      (node (ref "D04") (pin "M2") (pinfunction "P$2_M2") (pintype "bidirectional"))
    )
    (net (code "163") (name "BTP2") (class "Default")
      (node (ref "F08") (pin "K2") (pinfunction "OUT_K2") (pintype "output"))
      (node (ref "H05") (pin "V2") (pinfunction "P$2_V2") (pintype "bidirectional"))
    )
    (net (code "164") (name "BTP3") (class "Default")
      (node (ref "C08") (pin "D2") (pinfunction "OUT_D2") (pintype "output"))
      (node (ref "D04") (pin "E2") (pinfunction "P$2_E2") (pintype "bidirectional"))
    )
    (net (code "165") (name "B_C_") (class "Default")
      (node (ref "C07") (pin "K2") (pinfunction "OUT_K2") (pintype "output"))
      (node (ref "D04") (pin "K2") (pinfunction "P$2_K2") (pintype "bidirectional"))
    )
    (net (code "166") (name "B_DC_INST") (class "Default")
      (node (ref "C08") (pin "S2") (pinfunction "OUT_S2") (pintype "output"))
      (node (ref "D04") (pin "P2") (pinfunction "P$2_P2") (pintype "bidirectional"))
    )
    (net (code "167") (name "B_EAE_ON") (class "Default")
      (node (ref "D12") (pin "J1") (pinfunction "IN2_J1") (pintype "input"))
      (node (ref "D13") (pin "B1") (pinfunction "IN2_B1") (pintype "input"))
      (node (ref "D13") (pin "K1") (pinfunction "OUT_K1") (pintype "output"))
      (node (ref "D17") (pin "C1") (pinfunction "IN3_C1") (pintype "input"))
      (node (ref "D17") (pin "K1") (pinfunction "IN1_K1") (pintype "input"))
      (node (ref "D17") (pin "L2") (pinfunction "IN3_L2") (pintype "input"))
      (node (ref "D18") (pin "A1") (pinfunction "IN1_A1") (pintype "input"))
      (node (ref "D18") (pin "P1") (pinfunction "IN1_P1") (pintype "input"))
      (node (ref "D18") (pin "R2") (pinfunction "IN3_R2") (pintype "input"))
      (node (ref "D20") (pin "E2") (pinfunction "IN2_E2") (pintype "input"))
      (node (ref "D20") (pin "J1") (pinfunction "IN3_J1") (pintype "input"))
      (node (ref "F33") (pin "P2") (pinfunction "IN4B_P2") (pintype "input"))
    )
    (net (code "168") (name "B_EXECUTE") (class "Default")
      (node (ref "D13") (pin "M2") (pinfunction "IN2_M2") (pintype "input"))
      (node (ref "D14") (pin "E2") (pinfunction "IN2_E2") (pintype "input"))
      (node (ref "D21") (pin "H2") (pinfunction "IN4_H2") (pintype "input"))
      (node (ref "E26") (pin "H2") (pinfunction "IN1D_H2") (pintype "input"))
      (node (ref "E27") (pin "B1") (pinfunction "IN1B_B1") (pintype "input"))
      (node (ref "E27") (pin "N1") (pinfunction "IN5B_N1") (pintype "input"))
      (node (ref "E28") (pin "E2") (pinfunction "IN1B_E2") (pintype "input"))
      (node (ref "E29") (pin "D2") (pinfunction "IN1A_D2") (pintype "input"))
      (node (ref "E29") (pin "K2") (pinfunction "IN2B_K2") (pintype "input"))
      (node (ref "E30") (pin "N1") (pinfunction "IN5B_N1") (pintype "input"))
      (node (ref "E30") (pin "R2") (pinfunction "IN4C_R2") (pintype "input"))
      (node (ref "F25") (pin "R2") (pinfunction "IN2_R2") (pintype "input"))
      (node (ref "F26") (pin "P2") (pinfunction "IN2_P2") (pintype "input"))
      (node (ref "F26") (pin "S1") (pinfunction "IN3_S1") (pintype "input"))
      (node (ref "F28") (pin "C1") (pinfunction "IN3_C1") (pintype "input"))
      (node (ref "F28") (pin "F1") (pinfunction "IN2_F1") (pintype "input"))
      (node (ref "F31") (pin "V2") (pinfunction "OUT_V2") (pintype "open_collector"))
    )
    (net (code "169") (name "B_EXT_INST") (class "Default")
      (node (ref "A06") (pin "N1") (pinfunction "OUT_N1") (pintype "output"))
      (node (ref "A20") (pin "K1") (pinfunction "IN1_K1") (pintype "input"))
      (node (ref "A20") (pin "N2") (pinfunction "IN1_N2") (pintype "input"))
      (node (ref "A20") (pin "P1") (pinfunction "IN1_P1") (pintype "input"))
      (node (ref "B04") (pin "C1") (pinfunction "IN3_C1") (pintype "input"))
    )
    (net (code "170") (name "B_FETCH") (class "Default")
      (node (ref "B16") (pin "K2") (pinfunction "IN1_K2") (pintype "input"))
      (node (ref "D10") (pin "N2") (pinfunction "IN4_N2") (pintype "input"))
      (node (ref "D20") (pin "M1") (pinfunction "IN1_M1") (pintype "input"))
      (node (ref "E22") (pin "M1") (pinfunction "IN2_M1") (pintype "input"))
      (node (ref "E25") (pin "K2") (pinfunction "IN2_K2") (pintype "input"))
      (node (ref "E25") (pin "U2") (pinfunction "IN2_U2") (pintype "input"))
      (node (ref "E26") (pin "D1") (pinfunction "IN1D_D1") (pintype "input"))
      (node (ref "E26") (pin "R2") (pinfunction "IN4C_R2") (pintype "input"))
      (node (ref "F09") (pin "A1") (pinfunction "IN1_A1") (pintype "input"))
      (node (ref "F19") (pin "S2") (pinfunction "IN2_S2") (pintype "input"))
      (node (ref "F20") (pin "P1") (pinfunction "IN1_P1") (pintype "input"))
      (node (ref "F21") (pin "J1") (pinfunction "IN2_J1") (pintype "input"))
      (node (ref "F23") (pin "H1") (pinfunction "IN2_H1") (pintype "input"))
      (node (ref "F27") (pin "C1") (pinfunction "IN3_C1") (pintype "input"))
      (node (ref "F27") (pin "J1") (pinfunction "IN3_J1") (pintype "input"))
      (node (ref "F27") (pin "T2") (pinfunction "IN3_T2") (pintype "input"))
      (node (ref "F31") (pin "S1") (pinfunction "OUT_S1") (pintype "open_collector"))
    )
    (net (code "171") (name "B_FIELD") (class "Default")
      (node (ref "A27") (pin "E2") (pinfunction "E2_E2") (pintype "input"))
      (node (ref "A27") (pin "N2") (pinfunction "N2_N2") (pintype "input"))
      (node (ref "A37") (pin "N2") (pinfunction "N2_N2") (pintype "input"))
      (node (ref "B26") (pin "E2") (pinfunction "E2_E2") (pintype "input"))
      (node (ref "B26") (pin "N2") (pinfunction "N2_N2") (pintype "input"))
      (node (ref "B27") (pin "E2") (pinfunction "E2_E2") (pintype "input"))
      (node (ref "B27") (pin "N2") (pinfunction "N2_N2") (pintype "input"))
      (node (ref "B30") (pin "J2") (pinfunction "OUT_J2") (pintype "open_collector"))
      (node (ref "C30") (pin "D2") (pinfunction "D2_D2") (pintype "input"))
      (node (ref "C31") (pin "D2") (pinfunction "D2_D2") (pintype "input"))
      (node (ref "D30") (pin "D2") (pinfunction "D2_D2") (pintype "input"))
      (node (ref "D31") (pin "D2") (pinfunction "D2_D2") (pintype "input"))
    )
    (net (code "172") (name "B_FIELD_") (class "Default")
      (node (ref "A36") (pin "E2") (pinfunction "E2_E2") (pintype "input"))
      (node (ref "A36") (pin "N2") (pinfunction "N2_N2") (pintype "input"))
      (node (ref "A37") (pin "E2") (pinfunction "E2_E2") (pintype "input"))
      (node (ref "B30") (pin "V2") (pinfunction "OUT_V2") (pintype "open_collector"))
      (node (ref "B36") (pin "E2") (pinfunction "E2_E2") (pintype "input"))
      (node (ref "B36") (pin "N2") (pinfunction "N2_N2") (pintype "input"))
      (node (ref "B37") (pin "E2") (pinfunction "E2_E2") (pintype "input"))
      (node (ref "B37") (pin "N2") (pinfunction "N2_N2") (pintype "input"))
      (node (ref "C37") (pin "D2") (pinfunction "D2_D2") (pintype "input"))
      (node (ref "C38") (pin "D2") (pinfunction "D2_D2") (pintype "input"))
      (node (ref "D37") (pin "D2") (pinfunction "D2_D2") (pintype "input"))
      (node (ref "D38") (pin "D2") (pinfunction "D2_D2") (pintype "input"))
    )
    (net (code "173") (name "B_INHIBIT") (class "Default")
      (node (ref "A27") (pin "A1") (pinfunction "A1_A1") (pintype "input"))
      (node (ref "A36") (pin "A1") (pinfunction "A1_A1") (pintype "input"))
      (node (ref "A37") (pin "A1") (pinfunction "A1_A1") (pintype "input"))
      (node (ref "B26") (pin "A1") (pinfunction "A1_A1") (pintype "input"))
      (node (ref "B27") (pin "A1") (pinfunction "A1_A1") (pintype "input"))
      (node (ref "B30") (pin "P2") (pinfunction "OUT_P2") (pintype "open_collector"))
      (node (ref "B36") (pin "A1") (pinfunction "A1_A1") (pintype "input"))
      (node (ref "B37") (pin "A1") (pinfunction "A1_A1") (pintype "input"))
    )
    (net (code "174") (name "B_LEFT_SHIFT") (class "Default")
      (node (ref "C14") (pin "D2") (pinfunction "IN1_D2") (pintype "input"))
      (node (ref "C14") (pin "L1") (pinfunction "IN1_L1") (pintype "input"))
      (node (ref "C14") (pin "P2") (pinfunction "IN1_P2") (pintype "input"))
      (node (ref "C15") (pin "D2") (pinfunction "IN1_D2") (pintype "input"))
      (node (ref "C15") (pin "L1") (pinfunction "IN1_L1") (pintype "input"))
      (node (ref "C15") (pin "P2") (pinfunction "IN1_P2") (pintype "input"))
      (node (ref "D12") (pin "K2") (pinfunction "OUT_K2") (pintype "output"))
    )
    (net (code "175") (name "B_LINE_HOLD_") (class "Default")
      (node (ref "C07") (pin "D2") (pinfunction "OUT_D2") (pintype "output"))
      (node (ref "D04") (pin "D2") (pinfunction "P$2_D2") (pintype "bidirectional"))
    )
    (net (code "176") (name "B_MEM_ENABLE") (class "Default")
      (node (ref "A30") (pin "T2") (pinfunction "T2_T2") (pintype "input"))
      (node (ref "A31") (pin "T2") (pinfunction "T2_T2") (pintype "input"))
      (node (ref "A32") (pin "T2") (pinfunction "T2_T2") (pintype "input"))
      (node (ref "A33") (pin "T2") (pinfunction "T2_T2") (pintype "input"))
      (node (ref "B30") (pin "E1") (pinfunction "OUT_E1") (pintype "open_collector"))
      (node (ref "B31") (pin "T2") (pinfunction "T2_T2") (pintype "input"))
      (node (ref "B32") (pin "T2") (pinfunction "T2_T2") (pintype "input"))
      (node (ref "B33") (pin "T2") (pinfunction "T2_T2") (pintype "input"))
    )
    (net (code "177") (name "B_MEM_START") (class "Default")
      (node (ref "F08") (pin "D2") (pinfunction "OUT_D2") (pintype "output"))
      (node (ref "H05") (pin "M2") (pinfunction "P$2_M2") (pintype "bidirectional"))
    )
    (net (code "178") (name "B_MEM_TO_LSR") (class "Default")
      (node (ref "C08") (pin "K2") (pinfunction "OUT_K2") (pintype "output"))
      (node (ref "D04") (pin "H2") (pinfunction "P$2_H2") (pintype "bidirectional"))
    )
    (net (code "179") (name "B_POWER_CLEAR_") (class "Default")
      (node (ref "B22") (pin "A1") (pinfunction "R_A1") (pintype "input"))
      (node (ref "B22") (pin "K2") (pinfunction "R_K2") (pintype "input"))
      (node (ref "C12") (pin "S1") (pinfunction "OUT_S1") (pintype "open_collector"))
      (node (ref "D24") (pin "K2") (pinfunction "R_K2") (pintype "input"))
      (node (ref "E18") (pin "K2") (pinfunction "R_K2") (pintype "input"))
      (node (ref "EF10") (pin "AL2") (pinfunction "CL2_AL2") (pintype "input"))
      (node (ref "F20") (pin "R2") (pinfunction "IN2_R2") (pintype "input"))
    )
    (net (code "180") (name "B_R0_") (class "Default")
      (node (ref "D04") (pin "V2") (pinfunction "P$2_V2") (pintype "bidirectional"))
      (node (ref "D05") (pin "D2") (pinfunction "IN_D2") (pintype "input"))
      (node (ref "D05") (pin "E2") (pinfunction "IN2_E2") (pintype "bidirectional"))
      (node (ref "D05") (pin "F2") (pinfunction "IN3_F2") (pintype "input"))
      (node (ref "D05") (pin "H2") (pinfunction "IN4_H2") (pintype "input"))
    )
    (net (code "181") (name "B_SET") (class "Default")
      (node (ref "A19") (pin "E2") (pinfunction "IN2_E2") (pintype "input"))
      (node (ref "A19") (pin "M1") (pinfunction "IN2_M1") (pintype "input"))
      (node (ref "E23") (pin "T2") (pinfunction "D_T2") (pintype "input"))
      (node (ref "F22") (pin "S2") (pinfunction "OUT_S2") (pintype "output"))
    )
    (net (code "182") (name "B_SET_") (class "Default")
      (node (ref "A19") (pin "F2") (pinfunction "OUT_F2") (pintype "output"))
      (node (ref "B11") (pin "J1") (pinfunction "D_J1") (pintype "input"))
      (node (ref "B20") (pin "F2") (pinfunction "IN3_F2") (pintype "input"))
    )
    (net (code "183") (name "C") (class "Default")
      (node (ref "C10") (pin "P2") (pinfunction "IN1_P2") (pintype "input"))
      (node (ref "C11") (pin "E1") (pinfunction "IN1_E1") (pintype "input"))
      (node (ref "D09") (pin "E2") (pinfunction "IN2_E2") (pintype "input"))
      (node (ref "D10") (pin "N1") (pinfunction "IN2_N1") (pintype "input"))
      (node (ref "D10") (pin "S2") (pinfunction "IN2_S2") (pintype "input"))
      (node (ref "D11") (pin "J2") (pinfunction "0_J2") (pintype "output"))
    )
    (net (code "184") (name "CARRY_INSERT_") (class "Default")
      (node (ref "EF39") (pin "BJ1") (pinfunction "BJ1_BJ1") (pintype "input"))
      (node (ref "F32") (pin "C1") (pinfunction "OUT_C1") (pintype "output"))
    )
    (net (code "185") (name "CARRY_OUT0") (class "Default")
      (node (ref "E28") (pin "F2") (pinfunction "IN1C_F2") (pintype "input"))
      (node (ref "F21") (pin "B1") (pinfunction "IN2_B1") (pintype "input"))
      (node (ref "F32") (pin "V2") (pinfunction "OUT_V2") (pintype "output"))
      (node (ref "F33") (pin "U1") (pinfunction "IN1B_U1") (pintype "input"))
    )
    (net (code "186") (name "CARRY_OUT0_") (class "Default")
      (node (ref "EF34") (pin "BK2") (pinfunction "BK2_BK2") (pintype "output"))
      (node (ref "F32") (pin "U2") (pinfunction "IN2_U2") (pintype "input"))
      (node (ref "F33") (pin "U2") (pinfunction "IN2B_U2") (pintype "input"))
    )
    (net (code "187") (name "CARRY_OUT6_") (class "Default")
      (node (ref "EF36") (pin "BJ1") (pinfunction "BJ1_BJ1") (pintype "input"))
      (node (ref "EF37") (pin "BK2") (pinfunction "BK2_BK2") (pintype "output"))
    )
    (net (code "188") (name "CA_INCREMENT") (class "Default")
      (node (ref "E27") (pin "L2") (pinfunction "IN3A_L2") (pintype "input"))
      (node (ref "F25") (pin "F1") (pinfunction "OUT_F1") (pintype "output"))
    )
    (net (code "189") (name "CA_INCREMENT_") (class "Default")
      (node (ref "F25") (pin "D1") (pinfunction "IN1_D1") (pintype "input"))
      (node (ref "J20") (pin "L1") (pinfunction "OUT_L1") (pintype "output"))
    )
    (net (code "190") (name "CINT_") (class "Default")
      (node (ref "A05") (pin "L2") (pinfunction "IN1_L2") (pintype "input"))
      (node (ref "B04") (pin "D1") (pinfunction "OUT_D1") (pintype "output"))
    )
    (net (code "191") (name "CLEAR_DF_") (class "Default")
      (node (ref "B18") (pin "A1") (pinfunction "R_A1") (pintype "input"))
      (node (ref "B21") (pin "S2") (pinfunction "OUT_S2") (pintype "output"))
    )
    (net (code "192") (name "CLEAR_IB_") (class "Default")
      (node (ref "B17") (pin "K2") (pinfunction "R_K2") (pintype "input"))
      (node (ref "B21") (pin "N2") (pinfunction "OUT_N2") (pintype "output"))
    )
    (net (code "193") (name "CLEAR_IFDFBF_") (class "Default")
      (node (ref "B21") (pin "L2") (pinfunction "IN1_L2") (pintype "input"))
      (node (ref "B21") (pin "P1") (pinfunction "IN1_P1") (pintype "input"))
      (node (ref "B21") (pin "P2") (pinfunction "IN1_P2") (pintype "input"))
      (node (ref "E14") (pin "J1") (pinfunction "OUT_J1") (pintype "output"))
    )
    (net (code "194") (name "CLEAR_IF_") (class "Default")
      (node (ref "B05") (pin "A1") (pinfunction "R_A1") (pintype "input"))
      (node (ref "B17") (pin "A1") (pinfunction "R_A1") (pintype "input"))
      (node (ref "B21") (pin "S1") (pinfunction "OUT_S1") (pintype "output"))
    )
    (net (code "195") (name "CLEAR_X_") (class "Default")
      (node (ref "HJ23") (pin "AS2") (pinfunction "AS2_AS2") (pintype "output"))
      (node (ref "HJ24") (pin "AL2") (pinfunction "AL2_AL2") (pintype "bidirectional"))
    )
    (net (code "196") (name "CLEAR_Y_") (class "Default")
      (node (ref "HJ23") (pin "AR2") (pinfunction "AR2_AR2") (pintype "output"))
      (node (ref "HJ25") (pin "AL2") (pinfunction "AL2_AL2") (pintype "bidirectional"))
    )
    (net (code "197") (name "CLOCK") (class "Default")
      (node (ref "H30") (pin "D2") (pinfunction "D2_D2") (pintype "input"))
      (node (ref "HJ31") (pin "BJ2") (pinfunction "BJ2_BJ2") (pintype "input"))
      (node (ref "J30") (pin "D2") (pinfunction "D2_D2") (pintype "output"))
      (node (ref "J30") (pin "F2") (pinfunction "F2_F2") (pintype "bidirectional"))
    )
    (net (code "198") (name "CLOCK1") (class "Default")
      (node (ref "HJ26") (pin "BS2") (pinfunction "BS2_BS2") (pintype "input"))
      (node (ref "HJ27") (pin "AU2") (pinfunction "AU_AU2") (pintype "output"))
    )
    (net (code "199") (name "CLOCK_AC_CLR_") (class "Default")
      (node (ref "HJ31") (pin "BM2") (pinfunction "BM2_BM2") (pintype "open_collector"))
      (node (ref "J15") (pin "K1") (pinfunction "IN4_K1") (pintype "input"))
    )
    (net (code "200") (name "CLOCK_ENABLE_") (class "Default")
      (node (ref "H30") (pin "J2") (pinfunction "J2_J2") (pintype "output"))
      (node (ref "J30") (pin "J2") (pinfunction "J2_J2") (pintype "input"))
    )
    (net (code "201") (name "CLOCK_IOT") (class "Default")
      (node (ref "H30") (pin "S1") (pinfunction "S1_S1") (pintype "output"))
      (node (ref "HJ31") (pin "BL1") (pinfunction "BL1_BL1") (pintype "input"))
    )
    (net (code "202") (name "CLOCK_P4") (class "Default")
      (node (ref "H30") (pin "K2") (pinfunction "K2_K2") (pintype "output"))
      (node (ref "HJ31") (pin "BK1") (pinfunction "BK1_BK1") (pintype "input"))
    )
    (net (code "203") (name "CLOCK_SCALE_2") (class "Default")
      (node (ref "EF01") (pin "BP2") (pinfunction "BP2_BP2") (pintype "input"))
      (node (ref "EF01") (pin "BT2") (pinfunction "BT2_BT2") (pintype "output"))
      (node (ref "EF01") (pin "BU1") (pinfunction "BU1_BU1") (pintype "input"))
    )
    (net (code "204") (name "CLR_PARITY_ERROR_") (class "Default")
      (node (ref "B07") (pin "S2") (pinfunction "OUT_S2") (pintype "output"))
      (node (ref "B09") (pin "P1") (pinfunction "IN1_P1") (pintype "input"))
    )
    (net (code "205") (name "CR_READ") (class "Default")
      (node (ref "HJ34") (pin "BP2") (pinfunction "P$2_BP2") (pintype "bidirectional"))
      (node (ref "J33") (pin "S2") (pinfunction "S2_S2") (pintype "output"))
    )
    (net (code "206") (name "CR_READY") (class "Default")
      (node (ref "HJ34") (pin "AK2") (pinfunction "P$2_AK2") (pintype "bidirectional"))
      (node (ref "J33") (pin "R2") (pinfunction "R2_R2") (pintype "input"))
    )
    (net (code "207") (name "CSR_ENABLE_") (class "Default")
      (node (ref "C11") (pin "E2") (pinfunction "IN2_E2") (pintype "input"))
      (node (ref "D07") (pin "F1") (pinfunction "OUT_F1") (pintype "output"))
    )
    (net (code "208") (name "CUF") (class "Default")
      (node (ref "B06") (pin "K2") (pinfunction "OUT_K2") (pintype "output"))
      (node (ref "B06") (pin "L1") (pinfunction "IN1_L1") (pintype "input"))
    )
    (net (code "209") (name "CUF_") (class "Default")
      (node (ref "B06") (pin "C1") (pinfunction "OUT_C1") (pintype "output"))
      (node (ref "B06") (pin "D1") (pinfunction "IN1_D1") (pintype "input"))
      (node (ref "B06") (pin "H2") (pinfunction "IN1_H2") (pintype "input"))
      (node (ref "F11") (pin "F2") (pinfunction "IN3_F2") (pintype "input"))
      (node (ref "F11") (pin "H2") (pinfunction "IN4_H2") (pintype "input"))
    )
    (net (code "210") (name "CURRENT_ADDRESS") (class "Default")
      (node (ref "E23") (pin "S1") (pinfunction "1_S1") (pintype "output"))
      (node (ref "E27") (pin "M2") (pinfunction "IN3B_M2") (pintype "input"))
      (node (ref "E29") (pin "L1") (pinfunction "IN4B_L1") (pintype "input"))
    )
    (net (code "211") (name "CURRENT_ADDRESS_") (class "Default")
      (node (ref "D40") (pin "E1") (pinfunction "P$2_E1") (pintype "bidirectional"))
      (node (ref "E23") (pin "U1") (pinfunction "0_U1") (pintype "output"))
      (node (ref "E25") (pin "F1") (pinfunction "IN2_F1") (pintype "input"))
      (node (ref "F22") (pin "R2") (pinfunction "IN2_R2") (pintype "input"))
    )
    (net (code "212") (name "C_") (class "Default")
      (node (ref "C07") (pin "M2") (pinfunction "IN1_M2") (pintype "input"))
      (node (ref "D09") (pin "N2") (pinfunction "IN1_N2") (pintype "input"))
      (node (ref "D11") (pin "H2") (pinfunction "1_H2") (pintype "output"))
    )
    (net (code "213") (name "C_I_R") (class "Default")
      (node (ref "HJ34") (pin "BR2") (pinfunction "P$2_BR2") (pintype "bidirectional"))
      (node (ref "J33") (pin "U2") (pinfunction "U2_U2") (pintype "input"))
    )
    (net (code "214") (name "C_NO_SHIFT_") (class "Default")
      (node (ref "D07") (pin "C1") (pinfunction "OUT_C1") (pintype "output"))
      (node (ref "E31") (pin "R1") (pinfunction "IN4_R1") (pintype "input"))
    )
    (net (code "215") (name "C_SET_") (class "Default")
      (node (ref "C11") (pin "A1") (pinfunction "IN1_A1") (pintype "input"))
      (node (ref "C11") (pin "R2") (pinfunction "IN3_R2") (pintype "input"))
      (node (ref "D10") (pin "J2") (pinfunction "OUT_J2") (pintype "output"))
      (node (ref "D11") (pin "E2") (pinfunction "D_E2") (pintype "input"))
    )
    (net (code "216") (name "DATA00") (class "Default")
      (node (ref "EF34") (pin "BM2") (pinfunction "BM2_BM2") (pintype "input"))
      (node (ref "J18") (pin "E1") (pinfunction "OUT_E1") (pintype "output"))
    )
    (net (code "217") (name "DATA01") (class "Default")
      (node (ref "EF34") (pin "BP2") (pinfunction "BP2_BP2") (pintype "input"))
      (node (ref "J18") (pin "J2") (pinfunction "OUT_J2") (pintype "output"))
    )
    (net (code "218") (name "DATA02") (class "Default")
      (node (ref "EF35") (pin "BM2") (pinfunction "BM2_BM2") (pintype "input"))
      (node (ref "J18") (pin "L1") (pinfunction "OUT_L1") (pintype "output"))
    )
    (net (code "219") (name "DATA03") (class "Default")
      (node (ref "EF35") (pin "BP2") (pinfunction "BP2_BP2") (pintype "input"))
      (node (ref "J18") (pin "P2") (pinfunction "OUT_P2") (pintype "output"))
    )
    (net (code "220") (name "DATA04") (class "Default")
      (node (ref "EF36") (pin "BM2") (pinfunction "BM2_BM2") (pintype "input"))
      (node (ref "J18") (pin "S1") (pinfunction "OUT_S1") (pintype "output"))
    )
    (net (code "221") (name "DATA05") (class "Default")
      (node (ref "EF36") (pin "BP2") (pinfunction "BP2_BP2") (pintype "input"))
      (node (ref "J18") (pin "V2") (pinfunction "OUT_V2") (pintype "output"))
    )
    (net (code "222") (name "DATA06") (class "Default")
      (node (ref "EF37") (pin "BM2") (pinfunction "BM2_BM2") (pintype "input"))
      (node (ref "J19") (pin "E1") (pinfunction "OUT_E1") (pintype "output"))
    )
    (net (code "223") (name "DATA07") (class "Default")
      (node (ref "EF37") (pin "BP2") (pinfunction "BP2_BP2") (pintype "input"))
      (node (ref "J19") (pin "J2") (pinfunction "OUT_J2") (pintype "output"))
    )
    (net (code "224") (name "DATA08") (class "Default")
      (node (ref "EF38") (pin "BM2") (pinfunction "BM2_BM2") (pintype "input"))
      (node (ref "J19") (pin "L1") (pinfunction "OUT_L1") (pintype "output"))
    )
    (net (code "225") (name "DATA09") (class "Default")
      (node (ref "EF38") (pin "BP2") (pinfunction "BP2_BP2") (pintype "input"))
      (node (ref "J19") (pin "P2") (pinfunction "OUT_P2") (pintype "output"))
    )
    (net (code "226") (name "DATA10") (class "Default")
      (node (ref "EF39") (pin "BM2") (pinfunction "BM2_BM2") (pintype "input"))
      (node (ref "J19") (pin "S1") (pinfunction "OUT_S1") (pintype "output"))
    )
    (net (code "227") (name "DATA11") (class "Default")
      (node (ref "EF39") (pin "BP2") (pinfunction "BP2_BP2") (pintype "input"))
      (node (ref "J19") (pin "V2") (pinfunction "OUT_V2") (pintype "output"))
    )
    (net (code "228") (name "DATA_ADD00") (class "Default")
      (node (ref "EF34") (pin "BS1") (pinfunction "BS1_BS1") (pintype "input"))
      (node (ref "J16") (pin "E1") (pinfunction "OUT_E1") (pintype "output"))
    )
    (net (code "229") (name "DATA_ADD01") (class "Default")
      (node (ref "EF34") (pin "BU1") (pinfunction "BU1_BU1") (pintype "input"))
      (node (ref "J16") (pin "J2") (pinfunction "OUT_J2") (pintype "output"))
    )
    (net (code "230") (name "DATA_ADD02") (class "Default")
      (node (ref "EF35") (pin "BS1") (pinfunction "BS1_BS1") (pintype "input"))
      (node (ref "J16") (pin "L1") (pinfunction "OUT_L1") (pintype "output"))
    )
    (net (code "231") (name "DATA_ADD03") (class "Default")
      (node (ref "EF35") (pin "BU1") (pinfunction "BU1_BU1") (pintype "input"))
      (node (ref "J16") (pin "P2") (pinfunction "OUT_P2") (pintype "output"))
    )
    (net (code "232") (name "DATA_ADD04") (class "Default")
      (node (ref "EF36") (pin "BS1") (pinfunction "BS1_BS1") (pintype "input"))
      (node (ref "J16") (pin "S1") (pinfunction "OUT_S1") (pintype "output"))
    )
    (net (code "233") (name "DATA_ADD05") (class "Default")
      (node (ref "EF36") (pin "BU1") (pinfunction "BU1_BU1") (pintype "input"))
      (node (ref "J16") (pin "V2") (pinfunction "OUT_V2") (pintype "output"))
    )
    (net (code "234") (name "DATA_ADD06") (class "Default")
      (node (ref "EF37") (pin "BS1") (pinfunction "BS1_BS1") (pintype "input"))
      (node (ref "J17") (pin "E1") (pinfunction "OUT_E1") (pintype "output"))
    )
    (net (code "235") (name "DATA_ADD07") (class "Default")
      (node (ref "EF37") (pin "BU1") (pinfunction "BU1_BU1") (pintype "input"))
      (node (ref "J17") (pin "J2") (pinfunction "OUT_J2") (pintype "output"))
    )
    (net (code "236") (name "DATA_ADD08") (class "Default")
      (node (ref "EF38") (pin "BS1") (pinfunction "BS1_BS1") (pintype "input"))
      (node (ref "J17") (pin "L1") (pinfunction "OUT_L1") (pintype "output"))
    )
    (net (code "237") (name "DATA_ADD09") (class "Default")
      (node (ref "EF38") (pin "BU1") (pinfunction "BU1_BU1") (pintype "input"))
      (node (ref "J17") (pin "P2") (pinfunction "OUT_P2") (pintype "output"))
    )
    (net (code "238") (name "DATA_ADD10") (class "Default")
      (node (ref "EF39") (pin "BS1") (pinfunction "BS1_BS1") (pintype "input"))
      (node (ref "J17") (pin "S1") (pinfunction "OUT_S1") (pintype "output"))
    )
    (net (code "239") (name "DATA_ADD11") (class "Default")
      (node (ref "EF39") (pin "BU1") (pinfunction "BU1_BU1") (pintype "input"))
      (node (ref "J17") (pin "V2") (pinfunction "OUT_V2") (pintype "output"))
    )
    (net (code "240") (name "DATA_ADD_ENABLE") (class "Default")
      (node (ref "EF34") (pin "BT2") (pinfunction "BT2_BT2") (pintype "input"))
      (node (ref "EF35") (pin "BT2") (pinfunction "BT2_BT2") (pintype "input"))
      (node (ref "EF36") (pin "BT2") (pinfunction "BT2_BT2") (pintype "input"))
      (node (ref "EF37") (pin "BT2") (pinfunction "BT2_BT2") (pintype "input"))
      (node (ref "EF38") (pin "BT2") (pinfunction "BT2_BT2") (pintype "input"))
      (node (ref "EF39") (pin "BT2") (pinfunction "BT2_BT2") (pintype "input"))
      (node (ref "F30") (pin "P2") (pinfunction "OUT_P2") (pintype "open_collector"))
    )
    (net (code "241") (name "DATA_ENABLE") (class "Default")
      (node (ref "EF34") (pin "BL1") (pinfunction "BL1_BL1") (pintype "input"))
      (node (ref "EF35") (pin "BL1") (pinfunction "BL1_BL1") (pintype "input"))
      (node (ref "EF36") (pin "BL1") (pinfunction "BL1_BL1") (pintype "input"))
      (node (ref "EF37") (pin "BL1") (pinfunction "BL1_BL1") (pintype "input"))
      (node (ref "EF38") (pin "BL1") (pinfunction "BL1_BL1") (pintype "input"))
      (node (ref "EF39") (pin "BL1") (pinfunction "BL1_BL1") (pintype "input"))
      (node (ref "F30") (pin "L1") (pinfunction "OUT_L1") (pintype "open_collector"))
    )
    (net (code "242") (name "DATA_IN") (class "Default")
      (node (ref "E29") (pin "M2") (pinfunction "IN3B_M2") (pintype "input"))
      (node (ref "F28") (pin "M1") (pinfunction "IN3_M1") (pintype "input"))
      (node (ref "F29") (pin "F2") (pinfunction "OUT_F2") (pintype "output"))
    )
    (net (code "243") (name "DATA_IN_") (class "Default")
      (node (ref "F29") (pin "D2") (pinfunction "IN1_D2") (pintype "input"))
      (node (ref "J15") (pin "V2") (pinfunction "OUT_V2") (pintype "output"))
    )
    (net (code "244") (name "DCA") (class "Default")
      (node (ref "E22") (pin "K2") (pinfunction "OUT_K2") (pintype "output"))
      (node (ref "E29") (pin "J2") (pinfunction "IN2A_J2") (pintype "input"))
      (node (ref "E30") (pin "S2") (pinfunction "IN4D_S2") (pintype "input"))
    )
    (net (code "245") (name "DCA_") (class "Default")
      (node (ref "D40") (pin "R2") (pinfunction "P$2_R2") (pintype "bidirectional"))
      (node (ref "E21") (pin "M2") (pinfunction "OUT_M2") (pintype "output"))
      (node (ref "E22") (pin "H2") (pinfunction "IN1_H2") (pintype "input"))
      (node (ref "F26") (pin "V2") (pinfunction "IN3_V2") (pintype "input"))
    )
    (net (code "246") (name "DC_INST_") (class "Default")
      (node (ref "C08") (pin "V2") (pinfunction "IN2_V2") (pintype "input"))
      (node (ref "D09") (pin "J1") (pinfunction "OUT_J1") (pintype "output"))
    )
    (net (code "247") (name "DEFER") (class "Default")
      (node (ref "B20") (pin "C1") (pinfunction "IN3_C1") (pintype "input"))
      (node (ref "E23") (pin "H2") (pinfunction "1_H2") (pintype "output"))
      (node (ref "E24") (pin "D1") (pinfunction "IN1_D1") (pintype "input"))
      (node (ref "E26") (pin "N1") (pinfunction "IN5B_N1") (pintype "input"))
      (node (ref "E29") (pin "C1") (pinfunction "IN1C_C1") (pintype "input"))
      (node (ref "E29") (pin "N1") (pinfunction "IN5B_N1") (pintype "input"))
      (node (ref "F25") (pin "M1") (pinfunction "IN2_M1") (pintype "input"))
    )
    (net (code "248") (name "DEFER_") (class "Default")
      (node (ref "D40") (pin "B1") (pinfunction "P$2_B1") (pintype "bidirectional"))
      (node (ref "E23") (pin "J2") (pinfunction "0_J2") (pintype "output"))
    )
    (net (code "249") (name "DF0") (class "Default")
      (node (ref "A11") (pin "E1") (pinfunction "IN2_E1") (pintype "input"))
      (node (ref "A16") (pin "E1") (pinfunction "IN2_E1") (pintype "input"))
      (node (ref "B18") (pin "E1") (pinfunction "1_E1") (pintype "output"))
      (node (ref "B19") (pin "M2") (pinfunction "D_M2") (pintype "input"))
    )
    (net (code "250") (name "DF0_") (class "Default")
      (node (ref "B18") (pin "F1") (pinfunction "0_F1") (pintype "output"))
      (node (ref "C40") (pin "J2") (pinfunction "P$2_J2") (pintype "bidirectional"))
    )
    (net (code "251") (name "DF1") (class "Default")
      (node (ref "A11") (pin "J2") (pinfunction "IN2_J2") (pintype "input"))
      (node (ref "A16") (pin "J2") (pinfunction "IN2_J2") (pintype "input"))
      (node (ref "B18") (pin "H2") (pinfunction "1_H2") (pintype "output"))
      (node (ref "B19") (pin "P1") (pinfunction "D_P1") (pintype "input"))
    )
    (net (code "252") (name "DF1_") (class "Default")
      (node (ref "B18") (pin "J2") (pinfunction "0_J2") (pintype "output"))
      (node (ref "C40") (pin "S1") (pinfunction "P$2_S1") (pintype "bidirectional"))
    )
    (net (code "253") (name "DF2") (class "Default")
      (node (ref "A11") (pin "R1") (pinfunction "IN2_R1") (pintype "input"))
      (node (ref "A16") (pin "R1") (pinfunction "IN2_R1") (pintype "input"))
      (node (ref "B18") (pin "L1") (pinfunction "1_L1") (pintype "output"))
      (node (ref "B19") (pin "T2") (pinfunction "D_T2") (pintype "input"))
    )
    (net (code "254") (name "DF2_") (class "Default")
      (node (ref "B18") (pin "M1") (pinfunction "0_M1") (pintype "output"))
      (node (ref "C40") (pin "P2") (pinfunction "P$2_P2") (pintype "bidirectional"))
    )
    (net (code "255") (name "DFSR0") (class "Default")
      (node (ref "A12") (pin "E1") (pinfunction "IN2_E1") (pintype "input"))
      (node (ref "A40") (pin "D2") (pinfunction "P$2_D2") (pintype "bidirectional"))
    )
    (net (code "256") (name "DFSR1") (class "Default")
      (node (ref "A12") (pin "J2") (pinfunction "IN2_J2") (pintype "input"))
      (node (ref "A40") (pin "E2") (pinfunction "P$2_E2") (pintype "bidirectional"))
    )
    (net (code "257") (name "DFSR2") (class "Default")
      (node (ref "A12") (pin "R1") (pinfunction "IN2_R1") (pintype "input"))
      (node (ref "A40") (pin "F2") (pinfunction "P$2_F2") (pintype "bidirectional"))
    )
    (net (code "258") (name "DF_ENABLE") (class "Default")
      (node (ref "A16") (pin "D1") (pinfunction "IN1_D1") (pintype "input"))
      (node (ref "A16") (pin "H2") (pinfunction "IN1_H2") (pintype "input"))
      (node (ref "A16") (pin "P1") (pinfunction "IN1_P1") (pintype "input"))
      (node (ref "B11") (pin "J2") (pinfunction "0_J2") (pintype "output"))
    )
    (net (code "259") (name "DF_ENABLE_") (class "Default")
      (node (ref "B11") (pin "E2") (pinfunction "D_E2") (pintype "input"))
      (node (ref "B20") (pin "D1") (pinfunction "OUT_D1") (pintype "output"))
      (node (ref "B20") (pin "D2") (pinfunction "IN1_D2") (pintype "input"))
    )
    (net (code "260") (name "DIV_LAST") (class "Default")
      (node (ref "D12") (pin "A1") (pinfunction "IN1_A1") (pintype "input"))
      (node (ref "D13") (pin "E2") (pinfunction "IN2_E2") (pintype "input"))
      (node (ref "D16") (pin "K1") (pinfunction "OUT_K1") (pintype "output"))
      (node (ref "D20") (pin "M2") (pinfunction "IN3_M2") (pintype "input"))
      (node (ref "D23") (pin "E1") (pinfunction "IN2A_E1") (pintype "input"))
    )
    (net (code "261") (name "DIV_LAST_") (class "Default")
      (node (ref "D12") (pin "C1") (pinfunction "OUT_C1") (pintype "output"))
      (node (ref "D12") (pin "D2") (pinfunction "IN1_D2") (pintype "input"))
      (node (ref "D12") (pin "L2") (pinfunction "IN1_L2") (pintype "input"))
      (node (ref "D17") (pin "J2") (pinfunction "IN1_J2") (pintype "input"))
      (node (ref "D20") (pin "H2") (pinfunction "IN4_H2") (pintype "input"))
    )
    (net (code "262") (name "DOUBLE_LEFT_ROTATE") (class "Default")
      (node (ref "E31") (pin "J2") (pinfunction "OUT_J2") (pintype "open_collector"))
      (node (ref "EF34") (pin "AH1") (pinfunction "AH1_AH1") (pintype "input"))
      (node (ref "EF35") (pin "AH1") (pinfunction "AH1_AH1") (pintype "input"))
      (node (ref "EF36") (pin "AH1") (pinfunction "AH1_AH1") (pintype "input"))
      (node (ref "EF37") (pin "AH1") (pinfunction "AH1_AH1") (pintype "input"))
      (node (ref "EF38") (pin "AH1") (pinfunction "AH1_AH1") (pintype "input"))
      (node (ref "EF39") (pin "AH1") (pinfunction "AH1_AH1") (pintype "input"))
      (node (ref "F33") (pin "N1") (pinfunction "IN5B_N1") (pintype "input"))
    )
    (net (code "263") (name "DOUBLE_RIGHT_ROTATE") (class "Default")
      (node (ref "E31") (pin "E1") (pinfunction "OUT_E1") (pintype "open_collector"))
      (node (ref "EF34") (pin "AD1") (pinfunction "AD1_AD1") (pintype "input"))
      (node (ref "EF35") (pin "AD1") (pinfunction "AD1_AD1") (pintype "input"))
      (node (ref "EF36") (pin "AD1") (pinfunction "AD1_AD1") (pintype "input"))
      (node (ref "EF37") (pin "AD1") (pinfunction "AD1_AD1") (pintype "input"))
      (node (ref "EF38") (pin "AD1") (pinfunction "AD1_AD1") (pintype "input"))
      (node (ref "EF39") (pin "AD1") (pinfunction "AD1_AD1") (pintype "input"))
      (node (ref "F33") (pin "F1") (pinfunction "IN2B_F1") (pintype "input"))
    )
    (net (code "264") (name "DRUM_DOWN") (class "Default")
      (node (ref "D02") (pin "T2") (pinfunction "P$2_T2") (pintype "bidirectional"))
      (node (ref "HJ29") (pin "AR2") (pinfunction "AR2_AR2") (pintype "output"))
    )
    (net (code "265") (name "DRUM_UP") (class "Default")
      (node (ref "D02") (pin "S2") (pinfunction "P$2_S2") (pintype "bidirectional"))
      (node (ref "HJ29") (pin "AN2") (pinfunction "AN2_AN2") (pintype "output"))
    )
    (net (code "266") (name "DVI") (class "Default")
      (node (ref "D12") (pin "B1") (pinfunction "IN2_B1") (pintype "input"))
      (node (ref "D16") (pin "M1") (pinfunction "IN2_M1") (pintype "input"))
      (node (ref "D16") (pin "S2") (pinfunction "OUT_S2") (pintype "output"))
      (node (ref "D17") (pin "F1") (pinfunction "IN2_F1") (pintype "input"))
      (node (ref "D17") (pin "M1") (pinfunction "IN3_M1") (pintype "input"))
      (node (ref "D20") (pin "N2") (pinfunction "IN4_N2") (pintype "input"))
      (node (ref "D23") (pin "F1") (pinfunction "IN2B_F1") (pintype "input"))
    )
    (net (code "267") (name "DVI_") (class "Default")
      (node (ref "D16") (pin "P2") (pinfunction "IN1_P2") (pintype "input"))
      (node (ref "D17") (pin "B1") (pinfunction "IN2_B1") (pintype "input"))
      (node (ref "D19") (pin "V1") (pinfunction "OUT_V1") (pintype "output"))
      (node (ref "D23") (pin "S2") (pinfunction "IN4D_S2") (pintype "input"))
    )
    (net (code "268") (name "D_SET") (class "Default")
      (node (ref "E23") (pin "E2") (pinfunction "D_E2") (pintype "input"))
      (node (ref "F22") (pin "K2") (pinfunction "OUT_K2") (pintype "output"))
    )
    (net (code "269") (name "D_SET_") (class "Default")
      (node (ref "E25") (pin "M2") (pinfunction "OUT_M2") (pintype "output"))
      (node (ref "F22") (pin "H2") (pinfunction "IN1_H2") (pintype "input"))
      (node (ref "F23") (pin "N2") (pinfunction "IN4_N2") (pintype "input"))
      (node (ref "F23") (pin "R1") (pinfunction "IN4_R1") (pintype "input"))
      (node (ref "F29") (pin "D1") (pinfunction "IN1_D1") (pintype "input"))
    )
    (net (code "270") (name "E09F1") (class "Default")
      (node (ref "E09") (pin "F1") (pinfunction "OUT_F1") (pintype "output"))
      (node (ref "E17") (pin "H2") (pinfunction "H2_H2") (pintype "input"))
    )
    (net (code "271") (name "E25D1") (class "Default")
      (node (ref "E25") (pin "D1") (pinfunction "OUT_D1") (pintype "output"))
      (node (ref "EF39") (pin "AH2") (pinfunction "AH2_AH2") (pintype "input"))
    )
    (net (code "272") (name "EA0") (class "Default")
      (node (ref "B16") (pin "E1") (pinfunction "OUT_E1") (pintype "open_collector"))
      (node (ref "B16") (pin "M1") (pinfunction "IN1_M1") (pintype "input"))
      (node (ref "H01") (pin "D2") (pinfunction "P$2_D2") (pintype "bidirectional"))
    )
    (net (code "273") (name "EA0_") (class "Default")
      (node (ref "B16") (pin "S1") (pinfunction "OUT_S1") (pintype "open_collector"))
      (node (ref "B21") (pin "L1") (pinfunction "IN1_L1") (pintype "input"))
    )
    (net (code "274") (name "EA1") (class "Default")
      (node (ref "B16") (pin "J2") (pinfunction "OUT_J2") (pintype "open_collector"))
      (node (ref "B16") (pin "R2") (pinfunction "IN1_R2") (pintype "input"))
      (node (ref "H01") (pin "E2") (pinfunction "P$2_E2") (pintype "bidirectional"))
    )
    (net (code "275") (name "EA1_") (class "Default")
      (node (ref "B16") (pin "V2") (pinfunction "OUT_V2") (pintype "open_collector"))
      (node (ref "B21") (pin "M1") (pinfunction "IN2_M1") (pintype "input"))
    )
    (net (code "276") (name "EA2") (class "Default")
      (node (ref "B16") (pin "L1") (pinfunction "OUT_L1") (pintype "open_collector"))
      (node (ref "B22") (pin "E2") (pinfunction "D_E2") (pintype "input"))
      (node (ref "H01") (pin "H2") (pinfunction "P$2_H2") (pintype "bidirectional"))
    )
    (net (code "277") (name "EAE_ACBAR_ENABLE_") (class "Default")
      (node (ref "D13") (pin "A1") (pinfunction "IN1_A1") (pintype "input"))
      (node (ref "D17") (pin "N1") (pinfunction "OUT_N1") (pintype "output"))
      (node (ref "D17") (pin "P1") (pinfunction "IN1_P1") (pintype "input"))
      (node (ref "E32") (pin "U2") (pinfunction "IN4_U2") (pintype "input"))
      (node (ref "F29") (pin "M2") (pinfunction "IN2_M2") (pintype "input"))
    )
    (net (code "278") (name "EAE_AC_ENABLE_") (class "Default")
      (node (ref "D13") (pin "C1") (pinfunction "OUT_C1") (pintype "output"))
      (node (ref "E32") (pin "R1") (pinfunction "IN4_R1") (pintype "input"))
    )
    (net (code "279") (name "EAE_BEGIN") (class "Default")
      (node (ref "D12") (pin "R2") (pinfunction "IN2_R2") (pintype "input"))
      (node (ref "D14") (pin "H1") (pinfunction "IN1_H1") (pintype "input"))
      (node (ref "D14") (pin "K2") (pinfunction "OUT_K2") (pintype "output"))
      (node (ref "D17") (pin "V2") (pinfunction "IN3_V2") (pintype "input"))
    )
    (net (code "280") (name "EAE_COMPLETE_") (class "Default")
      (node (ref "C22") (pin "T2") (pinfunction "D_T2") (pintype "input"))
      (node (ref "D15") (pin "J2") (pinfunction "IN2_J2") (pintype "input"))
      (node (ref "D23") (pin "R1") (pinfunction "OUT_R1") (pintype "output"))
    )
    (net (code "281") (name "EAE_END") (class "Default")
      (node (ref "C22") (pin "V2") (pinfunction "1_V2") (pintype "output"))
      (node (ref "E12") (pin "D2") (pinfunction "IN1_D2") (pintype "input"))
      (node (ref "E14") (pin "P2") (pinfunction "IN2_P2") (pintype "input"))
    )
    (net (code "282") (name "EAE_EXECUTE_") (class "Default")
      (node (ref "D13") (pin "N2") (pinfunction "OUT_N2") (pintype "output"))
      (node (ref "F28") (pin "U2") (pinfunction "IN2_U2") (pintype "input"))
    )
    (net (code "283") (name "EAE_E_SET_") (class "Default")
      (node (ref "D13") (pin "N1") (pinfunction "OUT_N1") (pintype "output"))
      (node (ref "F23") (pin "H2") (pinfunction "IN4_H2") (pintype "input"))
      (node (ref "F28") (pin "K2") (pinfunction "IN2_K2") (pintype "input"))
    )
    (net (code "284") (name "EAE_INST") (class "Default")
      (node (ref "D13") (pin "D1") (pinfunction "IN1_D1") (pintype "input"))
      (node (ref "D13") (pin "K2") (pinfunction "OUT_K2") (pintype "output"))
      (node (ref "D13") (pin "M1") (pinfunction "IN2_M1") (pintype "input"))
      (node (ref "D14") (pin "R2") (pinfunction "IN2_R2") (pintype "input"))
      (node (ref "D18") (pin "L1") (pinfunction "IN2_L1") (pintype "input"))
      (node (ref "D20") (pin "U2") (pinfunction "IN4_U2") (pintype "input"))
    )
    (net (code "285") (name "EAE_IR0") (class "Default")
      (node (ref "D18") (pin "B1") (pinfunction "IN2_B1") (pintype "input"))
      (node (ref "D20") (pin "R2") (pinfunction "IN1_R2") (pintype "input"))
      (node (ref "D24") (pin "E1") (pinfunction "1_E1") (pintype "output"))
    )
    (net (code "286") (name "EAE_IR0_") (class "Default")
      (node (ref "D15") (pin "H1") (pinfunction "IN1_H1") (pintype "input"))
      (node (ref "D19") (pin "N2") (pinfunction "IN1_N2") (pintype "input"))
      (node (ref "D19") (pin "P1") (pinfunction "IN1_P1") (pintype "input"))
      (node (ref "D19") (pin "T2") (pinfunction "IN1_T2") (pintype "input"))
      (node (ref "D20") (pin "F1") (pinfunction "IN1_F1") (pintype "input"))
      (node (ref "D24") (pin "F1") (pinfunction "0_F1") (pintype "output"))
    )
    (net (code "287") (name "EAE_IR1") (class "Default")
      (node (ref "D15") (pin "J1") (pinfunction "IN2_J1") (pintype "input"))
      (node (ref "D17") (pin "A1") (pinfunction "IN1_A1") (pintype "input"))
      (node (ref "D18") (pin "C1") (pinfunction "IN3_C1") (pintype "input"))
      (node (ref "D19") (pin "R1") (pinfunction "IN2_R1") (pintype "input"))
      (node (ref "D19") (pin "U2") (pinfunction "IN2_U2") (pintype "input"))
      (node (ref "D24") (pin "H2") (pinfunction "1_H2") (pintype "output"))
    )
    (net (code "288") (name "EAE_IR1_") (class "Default")
      (node (ref "D19") (pin "P2") (pinfunction "IN2_P2") (pintype "input"))
      (node (ref "D20") (pin "S2") (pinfunction "IN2_S2") (pintype "input"))
      (node (ref "D24") (pin "J2") (pinfunction "0_J2") (pintype "output"))
    )
    (net (code "289") (name "EAE_IR2") (class "Default")
      (node (ref "D19") (pin "R2") (pinfunction "IN3_R2") (pintype "input"))
      (node (ref "D19") (pin "V2") (pinfunction "IN3_V2") (pintype "input"))
      (node (ref "D24") (pin "L1") (pinfunction "1_L1") (pintype "output"))
    )
    (net (code "290") (name "EAE_IR2_") (class "Default")
      (node (ref "D18") (pin "L2") (pinfunction "IN3_L2") (pintype "input"))
      (node (ref "D19") (pin "S1") (pinfunction "IN3_S1") (pintype "input"))
      (node (ref "D20") (pin "T2") (pinfunction "IN3_T2") (pintype "input"))
      (node (ref "D24") (pin "M1") (pinfunction "0_M1") (pintype "output"))
      (node (ref "F33") (pin "S2") (pinfunction "IN4D_S2") (pintype "input"))
    )
    (net (code "291") (name "EAE_IR_CLEAR_") (class "Default")
      (node (ref "D24") (pin "A1") (pinfunction "R_A1") (pintype "input"))
      (node (ref "E22") (pin "N1") (pinfunction "OUT_N1") (pintype "output"))
      (node (ref "E22") (pin "P1") (pinfunction "IN1_P1") (pintype "input"))
    )
    (net (code "292") (name "EAE_LEFT_SHIFT_ENABLE_") (class "Default")
      (node (ref "D20") (pin "J2") (pinfunction "OUT_J2") (pintype "output"))
      (node (ref "E31") (pin "N2") (pinfunction "IN4_N2") (pintype "input"))
    )
    (net (code "293") (name "EAE_L_DISABLE") (class "Default")
      (node (ref "D17") (pin "U1") (pinfunction "OUT_U1") (pintype "output"))
      (node (ref "E28") (pin "L1") (pinfunction "IN4B_L1") (pintype "input"))
    )
    (net (code "294") (name "EAE_MEM_ENABLE_") (class "Default")
      (node (ref "D20") (pin "L1") (pinfunction "OUT_L1") (pintype "output"))
      (node (ref "F11") (pin "L2") (pinfunction "IN2_L2") (pintype "input"))
      (node (ref "F31") (pin "D1") (pinfunction "IN4_D1") (pintype "input"))
      (node (ref "F31") (pin "D2") (pinfunction "IN1_D2") (pintype "input"))
    )
    (net (code "295") (name "EAE_MQ0BAR_ENABLE_") (class "Default")
      (node (ref "D18") (pin "U1") (pinfunction "OUT_U1") (pintype "output"))
      (node (ref "E25") (pin "B1") (pinfunction "IN2_B1") (pintype "input"))
    )
    (net (code "296") (name "EAE_MQ0_ENABLE_") (class "Default")
      (node (ref "D18") (pin "S2") (pinfunction "OUT_S2") (pintype "output"))
      (node (ref "E25") (pin "C1") (pinfunction "IN3_C1") (pintype "input"))
    )
    (net (code "297") (name "EAE_NO_SHIFT_ENABLE") (class "Default")
      (node (ref "D17") (pin "M2") (pinfunction "OUT_M2") (pintype "output"))
      (node (ref "F24") (pin "C1") (pinfunction "IN3_C1") (pintype "input"))
    )
    (net (code "298") (name "EAE_ON") (class "Default")
      (node (ref "C18") (pin "L2") (pinfunction "IN1_L2") (pintype "input"))
      (node (ref "C21") (pin "A1") (pinfunction "IN1_A1") (pintype "input"))
      (node (ref "C21") (pin "D2") (pinfunction "IN1_D2") (pintype "input"))
      (node (ref "C21") (pin "E1") (pinfunction "IN1_E1") (pintype "input"))
      (node (ref "C21") (pin "J2") (pinfunction "IN1_J2") (pintype "input"))
      (node (ref "C21") (pin "K1") (pinfunction "IN1_K1") (pintype "input"))
      (node (ref "C21") (pin "N2") (pinfunction "IN1_N2") (pintype "input"))
      (node (ref "C21") (pin "R1") (pinfunction "IN2_R1") (pintype "input"))
      (node (ref "C21") (pin "T2") (pinfunction "IN1_T2") (pintype "input"))
      (node (ref "D24") (pin "P1") (pinfunction "D_P1") (pintype "input"))
      (node (ref "D24") (pin "P2") (pinfunction "1_P2") (pintype "output"))
    )
    (net (code "299") (name "EAE_ON_") (class "Default")
      (node (ref "D13") (pin "H1") (pinfunction "IN1_H1") (pintype "input"))
      (node (ref "D21") (pin "E2") (pinfunction "IN2_E2") (pintype "input"))
      (node (ref "D24") (pin "R2") (pinfunction "0_R2") (pintype "output"))
      (node (ref "E24") (pin "A1") (pinfunction "IN1_A1") (pintype "input"))
      (node (ref "F28") (pin "R1") (pinfunction "IN2_R1") (pintype "input"))
    )
    (net (code "300") (name "EAE_RIGHT_SHIFT_ENABLE_") (class "Default")
      (node (ref "D12") (pin "H1") (pinfunction "IN1_H1") (pintype "input"))
      (node (ref "D17") (pin "D1") (pinfunction "OUT_D1") (pintype "output"))
      (node (ref "D20") (pin "D2") (pinfunction "IN1_D2") (pintype "input"))
      (node (ref "E31") (pin "K1") (pinfunction "IN4_K1") (pintype "input"))
    )
    (net (code "301") (name "EAE_RUN") (class "Default")
      (node (ref "C22") (pin "U2") (pinfunction "S_U2") (pintype "input"))
      (node (ref "D12") (pin "M2") (pinfunction "IN2_M2") (pintype "input"))
      (node (ref "D14") (pin "A1") (pinfunction "IN1_A1") (pintype "input"))
      (node (ref "D15") (pin "M1") (pinfunction "IN2_M1") (pintype "input"))
      (node (ref "D24") (pin "S1") (pinfunction "1_S1") (pintype "output"))
    )
    (net (code "302") (name "EAE_RUN_") (class "Default")
      (node (ref "D24") (pin "U1") (pinfunction "0_U1") (pintype "output"))
    )
    (net (code "303") (name "EAE_SET_") (class "Default")
      (node (ref "D14") (pin "K1") (pinfunction "OUT_K1") (pintype "output"))
      (node (ref "E14") (pin "L1") (pinfunction "IN2_L1") (pintype "input"))
    )
    (net (code "304") (name "EAE_START_") (class "Default")
      (node (ref "D14") (pin "E1") (pinfunction "IN2_E1") (pintype "input"))
      (node (ref "D17") (pin "V1") (pinfunction "OUT_V1") (pintype "output"))
      (node (ref "D24") (pin "R1") (pinfunction "S_R1") (pintype "input"))
      (node (ref "E12") (pin "E1") (pinfunction "IN2_E1") (pintype "input"))
    )
    (net (code "305") (name "EAE_TG") (class "Default")
      (node (ref "D22") (pin "P1") (pinfunction "IN3_P1") (pintype "input"))
      (node (ref "D22") (pin "R2") (pinfunction "IN1_R2") (pintype "input"))
      (node (ref "D24") (pin "V2") (pinfunction "1_V2") (pintype "output"))
    )
    (net (code "306") (name "EAE_TP") (class "Default")
      (node (ref "C13") (pin "J1") (pinfunction "OUT_J1") (pintype "output"))
      (node (ref "C22") (pin "S2") (pinfunction "C_S2") (pintype "input"))
      (node (ref "D14") (pin "B1") (pinfunction "IN2_B1") (pintype "input"))
    )
    (net (code "307") (name "EAE_TP_") (class "Default")
      (node (ref "D12") (pin "P1") (pinfunction "IN1_P1") (pintype "input"))
      (node (ref "D14") (pin "C1") (pinfunction "OUT_C1") (pintype "output"))
      (node (ref "D14") (pin "D1") (pinfunction "IN1_D1") (pintype "input"))
      (node (ref "D22") (pin "D2") (pinfunction "IN1_D2") (pintype "input"))
      (node (ref "E32") (pin "K2") (pinfunction "IN1_K2") (pintype "input"))
    )
    (net (code "308") (name "ENABLE") (class "Default")
      (node (ref "EF02") (pin "AK1") (pinfunction "AK1_AK1") (pintype "input"))
      (node (ref "EF02") (pin "AK2") (pinfunction "AK2_AK2") (pintype "output"))
    )
    (net (code "309") (name "ENABLE_") (class "Default")
      (node (ref "EF02") (pin "AH1") (pinfunction "AH1_AH1") (pintype "input"))
      (node (ref "EF02") (pin "AL1") (pinfunction "AL1_AL1") (pintype "output"))
    )
    (net (code "310") (name "EXECUTE_") (class "Default")
      (node (ref "D40") (pin "R1") (pinfunction "P$2_R1") (pintype "bidirectional"))
      (node (ref "E23") (pin "M1") (pinfunction "0_M1") (pintype "output"))
      (node (ref "F31") (pin "R2") (pinfunction "IN1_R2") (pintype "input"))
    )
    (net (code "311") (name "EXT_DATA_ADD0") (class "Default")
      (node (ref "B18") (pin "M2") (pinfunction "D_M2") (pintype "input"))
      (node (ref "J20") (pin "P2") (pinfunction "OUT_P2") (pintype "output"))
    )
    (net (code "312") (name "EXT_DATA_ADD1") (class "Default")
      (node (ref "B18") (pin "P1") (pinfunction "D_P1") (pintype "input"))
      (node (ref "J20") (pin "S1") (pinfunction "OUT_S1") (pintype "output"))
    )
    (net (code "313") (name "EXT_DATA_ADD2") (class "Default")
      (node (ref "B18") (pin "T2") (pinfunction "D_T2") (pintype "input"))
      (node (ref "J20") (pin "V2") (pinfunction "OUT_V2") (pintype "output"))
    )
    (net (code "314") (name "EXT_GO") (class "Default")
      (node (ref "A12") (pin "A1") (pinfunction "IN1_A1") (pintype "input"))
      (node (ref "A13") (pin "F1") (pinfunction "OUT_F1") (pintype "output"))
      (node (ref "A15") (pin "H2") (pinfunction "IN1_H2") (pintype "input"))
      (node (ref "A17") (pin "U2") (pinfunction "IN2_U2") (pintype "input"))
      (node (ref "B06") (pin "D2") (pinfunction "IN1_D2") (pintype "input"))
    )
    (net (code "315") (name "EXT_INST") (class "Default")
      (node (ref "A14") (pin "K2") (pinfunction "OUT_K2") (pintype "output"))
      (node (ref "A15") (pin "U2") (pinfunction "IN2_U2") (pintype "input"))
    )
    (net (code "316") (name "E_SET") (class "Default")
      (node (ref "E23") (pin "J1") (pinfunction "D_J1") (pintype "input"))
      (node (ref "F22") (pin "H1") (pinfunction "IN1_H1") (pintype "input"))
      (node (ref "F23") (pin "J2") (pinfunction "OUT_J2") (pintype "output"))
    )
    (net (code "317") (name "E_SET_") (class "Default")
      (node (ref "A16") (pin "U2") (pinfunction "IN2_U2") (pintype "input"))
      (node (ref "F22") (pin "K1") (pinfunction "OUT_K1") (pintype "output"))
      (node (ref "F23") (pin "K2") (pinfunction "IN1_K2") (pintype "input"))
      (node (ref "F23") (pin "P1") (pinfunction "IN3_P1") (pintype "input"))
      (node (ref "F29") (pin "E1") (pinfunction "IN2_E1") (pintype "input"))
    )
    (net (code "318") (name "F15F1") (class "Default")
      (node (ref "F15") (pin "F1") (pinfunction "OUT_F1") (pintype "output"))
      (node (ref "F16") (pin "H2") (pinfunction "H2_H2") (pintype "input"))
    )
    (net (code "319") (name "F17F1") (class "Default")
      (node (ref "F17") (pin "F1") (pinfunction "OUT_F1") (pintype "output"))
      (node (ref "F18") (pin "H2") (pinfunction "H2_H2") (pintype "input"))
    )
    (net (code "320") (name "FEED_HOLE") (class "Default")
      (node (ref "C01") (pin "H2") (pinfunction "P$2_H2") (pintype "bidirectional"))
      (node (ref "C01") (pin "T2") (pinfunction "P$2_T2") (pintype "bidirectional"))
      (node (ref "C04") (pin "S2") (pinfunction "R_S2") (pintype "open_collector"))
    )
    (net (code "321") (name "FETCH_") (class "Default")
      (node (ref "D40") (pin "N1") (pinfunction "P$2_N1") (pintype "bidirectional"))
      (node (ref "E23") (pin "F1") (pinfunction "0_F1") (pintype "output"))
      (node (ref "F28") (pin "T2") (pinfunction "IN1_T2") (pintype "input"))
      (node (ref "F31") (pin "M1") (pinfunction "IN1_M1") (pintype "input"))
    )
    (net (code "322") (name "FIELD") (class "Default")
      (node (ref "B22") (pin "H2") (pinfunction "1_H2") (pintype "output"))
      (node (ref "B24") (pin "R2") (pinfunction "R_R2") (pintype "input"))
      (node (ref "B30") (pin "F1") (pinfunction "IN1_F1") (pintype "input"))
      (node (ref "B30") (pin "R2") (pinfunction "IN1_R2") (pintype "input"))
    )
    (net (code "323") (name "FIELD_") (class "Default")
      (node (ref "B22") (pin "J2") (pinfunction "0_J2") (pintype "output"))
      (node (ref "B23") (pin "R2") (pinfunction "R_R2") (pintype "input"))
      (node (ref "B30") (pin "H2") (pinfunction "IN4_H2") (pintype "input"))
      (node (ref "C12") (pin "A1") (pinfunction "IN1_A1") (pintype "input"))
    )
    (net (code "324") (name "F_SET") (class "Default")
      (node (ref "E13") (pin "F1") (pinfunction "IN2B_F1") (pintype "input"))
      (node (ref "E23") (pin "C1") (pinfunction "D_C1") (pintype "input"))
      (node (ref "F11") (pin "U2") (pinfunction "IN4_U2") (pintype "input"))
      (node (ref "F22") (pin "F1") (pinfunction "OUT_F1") (pintype "output"))
    )
    (net (code "325") (name "F_SET_") (class "Default")
      (node (ref "A16") (pin "T2") (pinfunction "IN1_T2") (pintype "input"))
      (node (ref "F22") (pin "D1") (pinfunction "IN1_D1") (pintype "input"))
      (node (ref "F23") (pin "S1") (pinfunction "OUT_S1") (pintype "output"))
      (node (ref "F28") (pin "J2") (pinfunction "IN1_J2") (pintype "input"))
    )
    (net (code "326") (name "GND") (class "Default")
      (node (ref "A10") (pin "J1") (pinfunction "8A_J1") (pintype "input"))
      (node (ref "A25") (pin "H2") (pinfunction "P$1_H2") (pintype "passive"))
      (node (ref "A26") (pin "H2") (pinfunction "P$1_H2") (pintype "passive"))
      (node (ref "A38") (pin "C2") (pinfunction "P$2_C2") (pintype "passive"))
      (node (ref "A38") (pin "E2") (pinfunction "P$2_E2") (pintype "passive"))
      (node (ref "A39") (pin "C2") (pinfunction "P$2_C2") (pintype "passive"))
      (node (ref "A40") (pin "C2") (pinfunction "P$2_C2") (pintype "bidirectional"))
      (node (ref "AB01") (pin "AP2") (pinfunction "GND_AP2") (pintype "power_in"))
      (node (ref "AB01") (pin "AR2") (pinfunction "GND_AR2") (pintype "power_in"))
      (node (ref "AB01") (pin "AS2") (pinfunction "GND_AS2") (pintype "power_in"))
      (node (ref "AB01") (pin "AT2") (pinfunction "GND_AT2") (pintype "power_in"))
      (node (ref "AB01") (pin "AU2") (pinfunction "GND_AU2") (pintype "power_in"))
      (node (ref "AB01") (pin "BC2") (pinfunction "GND_BC2") (pintype "power_in"))
      (node (ref "AB01") (pin "BD2") (pinfunction "GND_BD2") (pintype "power_in"))
      (node (ref "AB01") (pin "BE2") (pinfunction "GND_BE2") (pintype "power_in"))
      (node (ref "AB01") (pin "BF2") (pinfunction "GND_BF2") (pintype "power_in"))
      (node (ref "AB01") (pin "BH2") (pinfunction "GND_BH2") (pintype "power_in"))
      (node (ref "AB01") (pin "BJ2") (pinfunction "GND_BJ2") (pintype "power_in"))
      (node (ref "AB01") (pin "BK2") (pinfunction "GND_BK2") (pintype "power_in"))
      (node (ref "AB01") (pin "BL2") (pinfunction "GND_BL2") (pintype "power_in"))
      (node (ref "B05") (pin "T2") (pinfunction "D_T2") (pintype "input"))
      (node (ref "B22") (pin "J1") (pinfunction "D_J1") (pintype "input"))
      (node (ref "B22") (pin "M2") (pinfunction "D_M2") (pintype "input"))
      (node (ref "B22") (pin "P1") (pinfunction "D_P1") (pintype "input"))
      (node (ref "B25") (pin "H2") (pinfunction "P$1_H2") (pintype "passive"))
      (node (ref "B38") (pin "C2") (pinfunction "P$2_C2") (pintype "passive"))
      (node (ref "B39") (pin "C2") (pinfunction "P$2_C2") (pintype "passive"))
      (node (ref "B39") (pin "E2") (pinfunction "P$2_E2") (pintype "passive"))
      (node (ref "B40") (pin "C2") (pinfunction "P$2_C2") (pintype "bidirectional"))
      (node (ref "C01") (pin "C2") (pinfunction "P$2_C2") (pintype "bidirectional"))
      (node (ref "C01") (pin "E2") (pinfunction "P$2_E2") (pintype "bidirectional"))
      (node (ref "C40") (pin "C2") (pinfunction "P$2_C2") (pintype "bidirectional"))
      (node (ref "D02") (pin "C2") (pinfunction "P$2_C2") (pintype "bidirectional"))
      (node (ref "D03") (pin "C2") (pinfunction "P$2_C2") (pintype "bidirectional"))
      (node (ref "D23") (pin "H1") (pinfunction "IN3A_H1") (pintype "input"))
      (node (ref "D23") (pin "J1") (pinfunction "IN3B_J1") (pintype "input"))
      (node (ref "E18") (pin "D2") (pinfunction "C_D2") (pintype "input"))
      (node (ref "E18") (pin "E2") (pinfunction "D_E2") (pintype "input"))
      (node (ref "E18") (pin "J1") (pinfunction "D_J1") (pintype "input"))
      (node (ref "E19") (pin "C1") (pinfunction "D_C1") (pintype "input"))
      (node (ref "E19") (pin "E2") (pinfunction "D_E2") (pintype "input"))
      (node (ref "E19") (pin "J1") (pinfunction "D_J1") (pintype "input"))
      (node (ref "E19") (pin "M2") (pinfunction "D_M2") (pintype "input"))
      (node (ref "E19") (pin "P1") (pinfunction "D_P1") (pintype "input"))
      (node (ref "E19") (pin "T2") (pinfunction "D_T2") (pintype "input"))
      (node (ref "E20") (pin "P1") (pinfunction "D_P1") (pintype "input"))
      (node (ref "E29") (pin "J1") (pinfunction "IN3B_J1") (pintype "input"))
      (node (ref "E30") (pin "A1") (pinfunction "IN1A_A1") (pintype "input"))
      (node (ref "E40") (pin "C2") (pinfunction "P$2_C2") (pintype "bidirectional"))
      (node (ref "EF01") (pin "BD1") (pinfunction "BD1_BD1") (pintype "input"))
      (node (ref "EF34") (pin "BD1") (pinfunction "BD1_BD1") (pintype "input"))
      (node (ref "EF34") (pin "BE2") (pinfunction "BE2_BE2") (pintype "input"))
      (node (ref "EF34") (pin "BN1") (pinfunction "BN1_BN1") (pintype "input"))
      (node (ref "EF35") (pin "BD1") (pinfunction "BD1_BD1") (pintype "input"))
      (node (ref "EF35") (pin "BE2") (pinfunction "BE2_BE2") (pintype "input"))
      (node (ref "EF35") (pin "BN1") (pinfunction "BN1_BN1") (pintype "input"))
      (node (ref "EF36") (pin "BD1") (pinfunction "BD1_BD1") (pintype "input"))
      (node (ref "EF36") (pin "BE2") (pinfunction "BE2_BE2") (pintype "input"))
      (node (ref "EF36") (pin "BN1") (pinfunction "BN1_BN1") (pintype "input"))
      (node (ref "EF37") (pin "BD1") (pinfunction "BD1_BD1") (pintype "input"))
      (node (ref "EF37") (pin "BE2") (pinfunction "BE2_BE2") (pintype "input"))
      (node (ref "EF38") (pin "BE2") (pinfunction "BE2_BE2") (pintype "input"))
      (node (ref "F40") (pin "C2") (pinfunction "P$2_C2") (pintype "bidirectional"))
      (node (ref "H07") (pin "E2") (pinfunction "SLOW_E2") (pintype "passive"))
      (node (ref "H07") (pin "L2") (pinfunction "SLOW_L2") (pintype "passive"))
      (node (ref "H07") (pin "R2") (pinfunction "SLOW_R2") (pintype "passive"))
      (node (ref "H08") (pin "E2") (pinfunction "SLOW_E2") (pintype "passive"))
      (node (ref "H08") (pin "L2") (pinfunction "SLOW_L2") (pintype "passive"))
      (node (ref "H08") (pin "R2") (pinfunction "SLOW_R2") (pintype "passive"))
      (node (ref "H09") (pin "E2") (pinfunction "SLOW_E2") (pintype "passive"))
      (node (ref "H09") (pin "L2") (pinfunction "SLOW_L2") (pintype "passive"))
      (node (ref "H09") (pin "R2") (pinfunction "SLOW_R2") (pintype "passive"))
      (node (ref "H10") (pin "E2") (pinfunction "SLOW_E2") (pintype "passive"))
      (node (ref "H10") (pin "L2") (pinfunction "SLOW_L2") (pintype "passive"))
      (node (ref "H10") (pin "R2") (pinfunction "SLOW_R2") (pintype "passive"))
      (node (ref "H11") (pin "E2") (pinfunction "SLOW_E2") (pintype "passive"))
      (node (ref "H11") (pin "L2") (pinfunction "SLOW_L2") (pintype "passive"))
      (node (ref "H11") (pin "R2") (pinfunction "SLOW_R2") (pintype "passive"))
      (node (ref "H12") (pin "E2") (pinfunction "SLOW_E2") (pintype "passive"))
      (node (ref "H12") (pin "L2") (pinfunction "SLOW_L2") (pintype "passive"))
      (node (ref "H12") (pin "R2") (pinfunction "SLOW_R2") (pintype "passive"))
      (node (ref "H13") (pin "E2") (pinfunction "SLOW_E2") (pintype "passive"))
      (node (ref "H13") (pin "L2") (pinfunction "SLOW_L2") (pintype "passive"))
      (node (ref "H13") (pin "R2") (pinfunction "SLOW_R2") (pintype "passive"))
      (node (ref "H14") (pin "E2") (pinfunction "SLOW_E2") (pintype "passive"))
      (node (ref "H14") (pin "L2") (pinfunction "SLOW_L2") (pintype "passive"))
      (node (ref "H14") (pin "R2") (pinfunction "SLOW_R2") (pintype "passive"))
      (node (ref "H15") (pin "E2") (pinfunction "SLOW_E2") (pintype "passive"))
      (node (ref "H15") (pin "L2") (pinfunction "SLOW_L2") (pintype "passive"))
      (node (ref "H15") (pin "R2") (pinfunction "SLOW_R2") (pintype "passive"))
      (node (ref "H16") (pin "E2") (pinfunction "SLOW_E2") (pintype "passive"))
      (node (ref "H16") (pin "L2") (pinfunction "SLOW_L2") (pintype "passive"))
      (node (ref "H16") (pin "R2") (pinfunction "SLOW_R2") (pintype "passive"))
      (node (ref "H17") (pin "E2") (pinfunction "SLOW_E2") (pintype "passive"))
      (node (ref "H17") (pin "L2") (pinfunction "SLOW_L2") (pintype "passive"))
      (node (ref "H17") (pin "R2") (pinfunction "SLOW_R2") (pintype "passive"))
      (node (ref "H18") (pin "E2") (pinfunction "SLOW_E2") (pintype "passive"))
      (node (ref "H18") (pin "L2") (pinfunction "SLOW_L2") (pintype "passive"))
      (node (ref "H18") (pin "R2") (pinfunction "SLOW_R2") (pintype "passive"))
      (node (ref "H19") (pin "E2") (pinfunction "SLOW_E2") (pintype "passive"))
      (node (ref "H19") (pin "L2") (pinfunction "SLOW_L2") (pintype "passive"))
      (node (ref "H19") (pin "R2") (pinfunction "SLOW_R2") (pintype "passive"))
      (node (ref "H20") (pin "E2") (pinfunction "SLOW_E2") (pintype "passive"))
      (node (ref "H20") (pin "L2") (pinfunction "SLOW_L2") (pintype "passive"))
      (node (ref "HJ34") (pin "AC2") (pinfunction "P$2_AC2") (pintype "bidirectional"))
      (node (ref "HJ34") (pin "BC2") (pinfunction "P$2_BC2") (pintype "bidirectional"))
    )
    (net (code "327") (name "HOLE1") (class "Default")
      (node (ref "C01") (pin "J2") (pinfunction "P$2_J2") (pintype "bidirectional"))
      (node (ref "C06") (pin "R2") (pinfunction "R_R2") (pintype "open_collector"))
    )
    (net (code "328") (name "HOLE2") (class "Default")
      (node (ref "C01") (pin "S2") (pinfunction "P$2_S2") (pintype "bidirectional"))
      (node (ref "C05") (pin "S2") (pinfunction "R_S2") (pintype "open_collector"))
    )
    (net (code "329") (name "HOLE3") (class "Default")
      (node (ref "C01") (pin "R2") (pinfunction "P$2_R2") (pintype "bidirectional"))
      (node (ref "C05") (pin "R2") (pinfunction "R_R2") (pintype "open_collector"))
    )
    (net (code "330") (name "HOLE4") (class "Default")
      (node (ref "C01") (pin "P2") (pinfunction "P$2_P2") (pintype "bidirectional"))
      (node (ref "C04") (pin "R2") (pinfunction "R_R2") (pintype "open_collector"))
    )
    (net (code "331") (name "HOLE5") (class "Default")
      (node (ref "C01") (pin "N2") (pinfunction "P$2_N2") (pintype "bidirectional"))
      (node (ref "C03") (pin "S2") (pinfunction "R_S2") (pintype "open_collector"))
    )
    (net (code "332") (name "HOLE6") (class "Default")
      (node (ref "C01") (pin "M2") (pinfunction "P$2_M2") (pintype "bidirectional"))
      (node (ref "C03") (pin "R2") (pinfunction "R_R2") (pintype "open_collector"))
    )
    (net (code "333") (name "HOLE7") (class "Default")
      (node (ref "C01") (pin "L2") (pinfunction "P$2_L2") (pintype "bidirectional"))
      (node (ref "C02") (pin "S2") (pinfunction "R_S2") (pintype "open_collector"))
    )
    (net (code "334") (name "HOLE8") (class "Default")
      (node (ref "C01") (pin "K2") (pinfunction "P$2_K2") (pintype "bidirectional"))
      (node (ref "C02") (pin "R2") (pinfunction "R_R2") (pintype "open_collector"))
    )
    (net (code "335") (name "HS") (class "Default")
      (node (ref "D07") (pin "B1") (pinfunction "IN2_B1") (pintype "input"))
      (node (ref "D11") (pin "P2") (pinfunction "1_P2") (pintype "output"))
    )
    (net (code "336") (name "HS_") (class "Default")
      (node (ref "C09") (pin "B1") (pinfunction "IN2_B1") (pintype "input"))
      (node (ref "C11") (pin "F1") (pinfunction "IN2_F1") (pintype "input"))
      (node (ref "D07") (pin "E1") (pinfunction "IN2_E1") (pintype "input"))
      (node (ref "D11") (pin "R2") (pinfunction "0_R2") (pintype "output"))
    )
    (net (code "337") (name "HZ880") (class "Default")
      (node (ref "F03") (pin "J2") (pinfunction "J2_J2") (pintype "output"))
      (node (ref "F03") (pin "P2") (pinfunction "P2_P2") (pintype "input"))
    )
    (net (code "338") (name "IB0") (class "Default")
      (node (ref "A17") (pin "J1") (pinfunction "IN2_J1") (pintype "input"))
      (node (ref "B17") (pin "P2") (pinfunction "1_P2") (pintype "output"))
    )
    (net (code "339") (name "IB1") (class "Default")
      (node (ref "A17") (pin "M1") (pinfunction "IN2_M1") (pintype "input"))
      (node (ref "B17") (pin "S1") (pinfunction "1_S1") (pintype "output"))
    )
    (net (code "340") (name "IB2") (class "Default")
      (node (ref "A17") (pin "R1") (pinfunction "IN2_R1") (pintype "input"))
      (node (ref "B17") (pin "V2") (pinfunction "1_V2") (pintype "output"))
    )
    (net (code "341") (name "IB_TO_IF") (class "Default")
      (node (ref "A15") (pin "A1") (pinfunction "IN1_A1") (pintype "input"))
      (node (ref "A17") (pin "C1") (pinfunction "OUT_C1") (pintype "output"))
      (node (ref "B05") (pin "D2") (pinfunction "C_D2") (pintype "input"))
      (node (ref "B17") (pin "B1") (pinfunction "C_B1") (pintype "input"))
      (node (ref "B17") (pin "D2") (pinfunction "C_D2") (pintype "input"))
      (node (ref "B17") (pin "H1") (pinfunction "C_H1") (pintype "input"))
    )
    (net (code "342") (name "IF0") (class "Default")
      (node (ref "A11") (pin "J1") (pinfunction "IN2_J1") (pintype "input"))
      (node (ref "A16") (pin "B1") (pinfunction "IN2_B1") (pintype "input"))
      (node (ref "B17") (pin "E1") (pinfunction "1_E1") (pintype "output"))
      (node (ref "B19") (pin "C1") (pinfunction "D_C1") (pintype "input"))
    )
    (net (code "343") (name "IF0_") (class "Default")
      (node (ref "B17") (pin "F1") (pinfunction "0_F1") (pintype "output"))
      (node (ref "C40") (pin "N1") (pinfunction "P$2_N1") (pintype "bidirectional"))
    )
    (net (code "344") (name "IF1") (class "Default")
      (node (ref "A11") (pin "M2") (pinfunction "IN2_M2") (pintype "input"))
      (node (ref "A16") (pin "J1") (pinfunction "IN2_J1") (pintype "input"))
      (node (ref "B17") (pin "H2") (pinfunction "1_H2") (pintype "output"))
      (node (ref "B19") (pin "E2") (pinfunction "D_E2") (pintype "input"))
    )
    (net (code "345") (name "IF1_") (class "Default")
      (node (ref "B17") (pin "J2") (pinfunction "0_J2") (pintype "output"))
      (node (ref "C40") (pin "C1") (pinfunction "P$2_C1") (pintype "bidirectional"))
    )
    (net (code "346") (name "IF2") (class "Default")
      (node (ref "A11") (pin "U2") (pinfunction "IN2_U2") (pintype "input"))
      (node (ref "A16") (pin "M2") (pinfunction "IN2_M2") (pintype "input"))
      (node (ref "B17") (pin "L1") (pinfunction "1_L1") (pintype "output"))
      (node (ref "B19") (pin "J1") (pinfunction "D_J1") (pintype "input"))
    )
    (net (code "347") (name "IF2_") (class "Default")
      (node (ref "B17") (pin "M1") (pinfunction "0_M1") (pintype "output"))
      (node (ref "C40") (pin "D1") (pinfunction "P$2_D1") (pintype "bidirectional"))
    )
    (net (code "348") (name "IFSR0") (class "Default")
      (node (ref "A18") (pin "E1") (pinfunction "IN2_E1") (pintype "input"))
      (node (ref "A40") (pin "H2") (pinfunction "P$2_H2") (pintype "bidirectional"))
    )
    (net (code "349") (name "IFSR1") (class "Default")
      (node (ref "A18") (pin "J2") (pinfunction "IN2_J2") (pintype "input"))
      (node (ref "A40") (pin "J2") (pinfunction "P$2_J2") (pintype "bidirectional"))
    )
    (net (code "350") (name "IFSR2") (class "Default")
      (node (ref "A18") (pin "R1") (pinfunction "IN2_R1") (pintype "input"))
      (node (ref "A40") (pin "K2") (pinfunction "P$2_K2") (pintype "bidirectional"))
    )
    (net (code "351") (name "IF_ENABLE") (class "Default")
      (node (ref "A16") (pin "A1") (pinfunction "IN1_A1") (pintype "input"))
      (node (ref "A16") (pin "H1") (pinfunction "IN1_H1") (pintype "input"))
      (node (ref "A16") (pin "L2") (pinfunction "IN1_L2") (pintype "input"))
      (node (ref "B11") (pin "F1") (pinfunction "0_F1") (pintype "output"))
    )
    (net (code "352") (name "IF_ENABLE_") (class "Default")
      (node (ref "B11") (pin "C1") (pinfunction "D_C1") (pintype "input"))
      (node (ref "B20") (pin "H2") (pinfunction "OUT_H2") (pintype "output"))
    )
    (net (code "353") (name "IF_TO_SF") (class "Default")
      (node (ref "A19") (pin "S1") (pinfunction "OUT_S1") (pintype "output"))
      (node (ref "B05") (pin "N1") (pinfunction "C_N1") (pintype "input"))
      (node (ref "B19") (pin "B1") (pinfunction "C_B1") (pintype "input"))
      (node (ref "B19") (pin "D2") (pinfunction "C_D2") (pintype "input"))
      (node (ref "B21") (pin "M2") (pinfunction "IN2_M2") (pintype "input"))
      (node (ref "B21") (pin "R1") (pinfunction "IN2_R1") (pintype "input"))
      (node (ref "B21") (pin "R2") (pinfunction "IN2_R2") (pintype "input"))
    )
    (net (code "354") (name "INDEX_MARKERS") (class "Default")
      (node (ref "HJ32") (pin "AD2") (pinfunction "AD2_AD2") (pintype "input"))
      (node (ref "HJ34") (pin "BH2") (pinfunction "P$2_BH2") (pintype "bidirectional"))
      (node (ref "J33") (pin "J1") (pinfunction "J1_J1") (pintype "input"))
    )
    (net (code "355") (name "INHIBIT_") (class "Default")
      (node (ref "B22") (pin "R2") (pinfunction "0_R2") (pintype "output"))
      (node (ref "B30") (pin "K2") (pinfunction "IN1_K2") (pintype "input"))
    )
    (net (code "356") (name "INITIALIZE") (class "Default")
      (node (ref "C12") (pin "H1") (pinfunction "IN2_H1") (pintype "input"))
      (node (ref "EF01") (pin "BF2") (pinfunction "BF2_BF2") (pintype "input"))
      (node (ref "EF02") (pin "BE2") (pinfunction "BE2_BE2") (pintype "input"))
      (node (ref "F20") (pin "S2") (pinfunction "OUT_S2") (pintype "output"))
      (node (ref "HJ23") (pin "AH2") (pinfunction "AH2_AH2") (pintype "input"))
      (node (ref "HJ29") (pin "BN2") (pinfunction "BN2_BN2") (pintype "input"))
    )
    (net (code "357") (name "INITIALIZE_") (class "Default")
      (node (ref "A04") (pin "S2") (pinfunction "S2_S2") (pintype "input"))
      (node (ref "B05") (pin "K2") (pinfunction "R_K2") (pintype "input"))
      (node (ref "B07") (pin "L1") (pinfunction "IN2_L1") (pintype "input"))
      (node (ref "C12") (pin "L1") (pinfunction "OUT_L1") (pintype "open_collector"))
      (node (ref "E19") (pin "K2") (pinfunction "R_K2") (pintype "input"))
      (node (ref "H12") (pin "U2") (pinfunction "IN2_U2") (pintype "input"))
      (node (ref "H30") (pin "P1") (pinfunction "P1_P1") (pintype "input"))
      (node (ref "HJ26") (pin "BP1") (pinfunction "BP1_BP1") (pintype "input"))
      (node (ref "HJ28") (pin "AS2") (pinfunction "AS2_AS2") (pintype "input"))
      (node (ref "HJ32") (pin "BS2") (pinfunction "BS2_BS2") (pintype "input"))
      (node (ref "J33") (pin "N1") (pinfunction "N1_N1") (pintype "input"))
    )
    (net (code "358") (name "INPUT_BUS00") (class "Default")
      (node (ref "EF34") (pin "BK1") (pinfunction "BK1_BK1") (pintype "input"))
      (node (ref "J13") (pin "E1") (pinfunction "OUT_E1") (pintype "output"))
    )
    (net (code "359") (name "INPUT_BUS01") (class "Default")
      (node (ref "EF34") (pin "BM1") (pinfunction "BM1_BM1") (pintype "input"))
      (node (ref "J13") (pin "J2") (pinfunction "OUT_J2") (pintype "output"))
    )
    (net (code "360") (name "INPUT_BUS02") (class "Default")
      (node (ref "EF35") (pin "BK1") (pinfunction "BK1_BK1") (pintype "input"))
      (node (ref "J13") (pin "L1") (pinfunction "OUT_L1") (pintype "output"))
    )
    (net (code "361") (name "INPUT_BUS03") (class "Default")
      (node (ref "EF35") (pin "BM1") (pinfunction "BM1_BM1") (pintype "input"))
      (node (ref "J13") (pin "P2") (pinfunction "OUT_P2") (pintype "output"))
    )
    (net (code "362") (name "INPUT_BUS04") (class "Default")
      (node (ref "EF36") (pin "BK1") (pinfunction "BK1_BK1") (pintype "input"))
      (node (ref "J13") (pin "S1") (pinfunction "OUT_S1") (pintype "output"))
    )
    (net (code "363") (name "INPUT_BUS05") (class "Default")
      (node (ref "EF36") (pin "BM1") (pinfunction "BM1_BM1") (pintype "input"))
      (node (ref "J13") (pin "V2") (pinfunction "OUT_V2") (pintype "output"))
    )
    (net (code "364") (name "INPUT_BUS06") (class "Default")
      (node (ref "EF37") (pin "BK1") (pinfunction "BK1_BK1") (pintype "input"))
      (node (ref "J14") (pin "E1") (pinfunction "OUT_E1") (pintype "output"))
    )
    (net (code "365") (name "INPUT_BUS07") (class "Default")
      (node (ref "EF37") (pin "BM1") (pinfunction "BM1_BM1") (pintype "input"))
      (node (ref "J14") (pin "J2") (pinfunction "OUT_J2") (pintype "output"))
    )
    (net (code "366") (name "INPUT_BUS08") (class "Default")
      (node (ref "EF38") (pin "BK1") (pinfunction "BK1_BK1") (pintype "input"))
      (node (ref "J14") (pin "L1") (pinfunction "OUT_L1") (pintype "output"))
    )
    (net (code "367") (name "INPUT_BUS09") (class "Default")
      (node (ref "EF38") (pin "BM1") (pinfunction "BM1_BM1") (pintype "input"))
      (node (ref "J14") (pin "P2") (pinfunction "OUT_P2") (pintype "output"))
    )
    (net (code "368") (name "INPUT_BUS10") (class "Default")
      (node (ref "EF39") (pin "BK1") (pinfunction "BK1_BK1") (pintype "input"))
      (node (ref "J14") (pin "S1") (pinfunction "OUT_S1") (pintype "output"))
    )
    (net (code "369") (name "INPUT_BUS11") (class "Default")
      (node (ref "EF39") (pin "BM1") (pinfunction "BM1_BM1") (pintype "input"))
      (node (ref "J14") (pin "V2") (pinfunction "OUT_V2") (pintype "output"))
    )
    (net (code "370") (name "INT_DELAY") (class "Default")
      (node (ref "E25") (pin "F2") (pinfunction "IN3_F2") (pintype "input"))
      (node (ref "E33") (pin "R2") (pinfunction "0_R2") (pintype "output"))
    )
    (net (code "371") (name "INT_ENABLE") (class "Default")
      (node (ref "E33") (pin "N2") (pinfunction "S_N2") (pintype "input"))
      (node (ref "E33") (pin "U1") (pinfunction "0_U1") (pintype "output"))
    )
    (net (code "372") (name "INT_ENABLE_") (class "Default")
      (node (ref "D40") (pin "D1") (pinfunction "P$2_D1") (pintype "bidirectional"))
      (node (ref "E33") (pin "M2") (pinfunction "D_M2") (pintype "input"))
      (node (ref "E33") (pin "S1") (pinfunction "1_S1") (pintype "output"))
    )
    (net (code "373") (name "INT_INHIBIT") (class "Default")
      (node (ref "A15") (pin "E1") (pinfunction "IN2_E1") (pintype "input"))
      (node (ref "F11") (pin "J2") (pinfunction "OUT_J2") (pintype "output"))
    )
    (net (code "374") (name "INT_INHIBIT_") (class "Default")
      (node (ref "A15") (pin "F1") (pinfunction "OUT_F1") (pintype "output"))
      (node (ref "E25") (pin "E2") (pinfunction "IN2_E2") (pintype "input"))
      (node (ref "F11") (pin "D2") (pinfunction "IN1_D2") (pintype "input"))
    )
    (net (code "375") (name "INT_OK") (class "Default")
      (node (ref "C12") (pin "K2") (pinfunction "IN1_K2") (pintype "input"))
      (node (ref "E24") (pin "J2") (pinfunction "IN2_J2") (pintype "input"))
      (node (ref "E26") (pin "U1") (pinfunction "IN1B_U1") (pintype "input"))
      (node (ref "F21") (pin "N1") (pinfunction "OUT_N1") (pintype "output"))
    )
    (net (code "376") (name "INT_OK_") (class "Default")
      (node (ref "E25") (pin "H2") (pinfunction "OUT_H2") (pintype "output"))
      (node (ref "F21") (pin "M1") (pinfunction "IN2_M1") (pintype "input"))
      (node (ref "F23") (pin "D2") (pinfunction "IN1_D2") (pintype "input"))
      (node (ref "F27") (pin "F2") (pinfunction "IN3_F2") (pintype "input"))
    )
    (net (code "377") (name "INT_RQST") (class "Default")
      (node (ref "F11") (pin "R2") (pinfunction "IN1_R2") (pintype "input"))
      (node (ref "J15") (pin "J2") (pinfunction "OUT_J2") (pintype "output"))
    )
    (net (code "378") (name "INT_SKIP_ENABLE_") (class "Default")
      (node (ref "F09") (pin "L2") (pinfunction "IN6_L2") (pintype "input"))
      (node (ref "F11") (pin "M1") (pinfunction "IN1_M1") (pintype "input"))
      (node (ref "F28") (pin "J1") (pinfunction "OUT_J1") (pintype "output"))
    )
    (net (code "379") (name "INT_STROBE") (class "Default")
      (node (ref "E14") (pin "S2") (pinfunction "OUT_S2") (pintype "output"))
      (node (ref "E15") (pin "L2") (pinfunction "IN1_L2") (pintype "input"))
      (node (ref "E33") (pin "H1") (pinfunction "C_H1") (pintype "input"))
      (node (ref "F19") (pin "F1") (pinfunction "IN1_F1") (pintype "input"))
      (node (ref "F21") (pin "H1") (pinfunction "IN1_H1") (pintype "input"))
    )
    (net (code "380") (name "INT_STROBE_") (class "Default")
      (node (ref "C12") (pin "M2") (pinfunction "IN3_M2") (pintype "input"))
      (node (ref "E15") (pin "N2") (pinfunction "OUT_N2") (pintype "output"))
      (node (ref "E19") (pin "K1") (pinfunction "S_K1") (pintype "input"))
    )
    (net (code "381") (name "INT_SYNC") (class "Default")
      (node (ref "E25") (pin "D2") (pinfunction "IN1_D2") (pintype "input"))
      (node (ref "E33") (pin "M1") (pinfunction "0_M1") (pintype "output"))
    )
    (net (code "382") (name "IN_STOP_2_") (class "Default")
      (node (ref "EF01") (pin "BR2") (pinfunction "BR2_BR2") (pintype "input"))
      (node (ref "EF01") (pin "BV2") (pinfunction "BV2_BV2") (pintype "output"))
    )
    (net (code "383") (name "IOP1") (class "Default")
      (node (ref "B07") (pin "K2") (pinfunction "IN2_K2") (pintype "input"))
      (node (ref "E19") (pin "P2") (pinfunction "1_P2") (pintype "output"))
      (node (ref "EF01") (pin "BD2") (pinfunction "BD2_BD2") (pintype "input"))
      (node (ref "EF02") (pin "BH2") (pinfunction "BH2_BH2") (pintype "input"))
      (node (ref "HJ23") (pin "AR1") (pinfunction "AR1_AR1") (pintype "input"))
      (node (ref "HJ26") (pin "AU2") (pinfunction "AU2_AU2") (pintype "input"))
      (node (ref "HJ28") (pin "AR2") (pinfunction "AR2_AR2") (pintype "input"))
      (node (ref "HJ29") (pin "BH2") (pinfunction "BH2_BH2") (pintype "input"))
    )
    (net (code "384") (name "IOP1_") (class "Default")
      (node (ref "E09") (pin "M2") (pinfunction "IN2_M2") (pintype "input"))
      (node (ref "E19") (pin "R2") (pinfunction "0_R2") (pintype "output"))
      (node (ref "F11") (pin "H1") (pinfunction "IN2_H1") (pintype "input"))
      (node (ref "H11") (pin "H2") (pinfunction "IN2_H2") (pintype "input"))
      (node (ref "H30") (pin "L2") (pinfunction "L2_L2") (pintype "input"))
      (node (ref "HJ29") (pin "BL2") (pinfunction "BL2_BL2") (pintype "input"))
    )
    (net (code "385") (name "IOP1_CLR") (class "Default")
      (node (ref "E19") (pin "L2") (pinfunction "C_L2") (pintype "input"))
      (node (ref "F14") (pin "J1") (pinfunction "OUT_J1") (pintype "output"))
    )
    (net (code "386") (name "IOP1_SET_") (class "Default")
      (node (ref "E14") (pin "S1") (pinfunction "IN3_S1") (pintype "input"))
      (node (ref "E19") (pin "N2") (pinfunction "S_N2") (pintype "input"))
      (node (ref "F20") (pin "F2") (pinfunction "OUT_F2") (pintype "output"))
    )
    (net (code "387") (name "IOP2") (class "Default")
      (node (ref "A04") (pin "M2") (pinfunction "M2_M2") (pintype "input"))
      (node (ref "E19") (pin "S1") (pinfunction "1_S1") (pintype "output"))
      (node (ref "EF01") (pin "BJ2") (pinfunction "BJ2_BJ2") (pintype "input"))
      (node (ref "EF02") (pin "BD2") (pinfunction "BD2_BD2") (pintype "input"))
      (node (ref "HJ23") (pin "AJ2") (pinfunction "AJ2_AJ2") (pintype "input"))
      (node (ref "HJ26") (pin "AV2") (pinfunction "AV2_AV2") (pintype "input"))
      (node (ref "HJ28") (pin "AR1") (pinfunction "AR1_AR1") (pintype "input"))
      (node (ref "HJ29") (pin "BP2") (pinfunction "BP2_BP2") (pintype "input"))
    )
    (net (code "388") (name "IOP2_") (class "Default")
      (node (ref "E09") (pin "R1") (pinfunction "IN2_R1") (pintype "input"))
      (node (ref "E19") (pin "U1") (pinfunction "0_U1") (pintype "output"))
      (node (ref "F11") (pin "J1") (pinfunction "IN3_J1") (pintype "input"))
      (node (ref "H11") (pin "N2") (pinfunction "IN2_N2") (pintype "input"))
      (node (ref "H30") (pin "R1") (pinfunction "R1_R1") (pintype "input"))
      (node (ref "HJ29") (pin "BM2") (pinfunction "BM2_BM2") (pintype "input"))
    )
    (net (code "389") (name "IOP2_CLR") (class "Default")
      (node (ref "E19") (pin "N1") (pinfunction "C_N1") (pintype "input"))
      (node (ref "F16") (pin "J1") (pinfunction "OUT_J1") (pintype "output"))
    )
    (net (code "390") (name "IOP2_SET_") (class "Default")
      (node (ref "E14") (pin "R1") (pinfunction "IN2_R1") (pintype "input"))
      (node (ref "E19") (pin "R1") (pinfunction "S_R1") (pintype "input"))
      (node (ref "F20") (pin "K1") (pinfunction "OUT_K1") (pintype "output"))
    )
    (net (code "391") (name "IOP4") (class "Default")
      (node (ref "B07") (pin "E1") (pinfunction "IN1_E1") (pintype "input"))
      (node (ref "E19") (pin "V2") (pinfunction "1_V2") (pintype "output"))
      (node (ref "EF01") (pin "AL2") (pinfunction "AL2_AL2") (pintype "input"))
      (node (ref "EF02") (pin "AS1") (pinfunction "AS1_AS1") (pintype "input"))
      (node (ref "HJ23") (pin "BD2") (pinfunction "BD2_BD2") (pintype "input"))
      (node (ref "HJ26") (pin "BK1") (pinfunction "BK1_BK1") (pintype "input"))
      (node (ref "HJ28") (pin "AP2") (pinfunction "AP2_AP2") (pintype "input"))
      (node (ref "HJ29") (pin "BT2") (pinfunction "BT2_BT2") (pintype "input"))
    )
    (net (code "392") (name "IOP4_") (class "Default")
      (node (ref "E09") (pin "R2") (pinfunction "IN2_R2") (pintype "input"))
      (node (ref "E19") (pin "V1") (pinfunction "0_V1") (pintype "output"))
      (node (ref "F11") (pin "K1") (pinfunction "IN4_K1") (pintype "input"))
      (node (ref "H11") (pin "U2") (pinfunction "IN2_U2") (pintype "input"))
      (node (ref "H30") (pin "F2") (pinfunction "F2_F2") (pintype "input"))
    )
    (net (code "393") (name "IOP4_CLR") (class "Default")
      (node (ref "E19") (pin "S2") (pinfunction "C_S2") (pintype "input"))
      (node (ref "F18") (pin "J1") (pinfunction "OUT_J1") (pintype "output"))
    )
    (net (code "394") (name "IOP4_SET_") (class "Default")
      (node (ref "E14") (pin "P1") (pinfunction "IN1_P1") (pintype "input"))
      (node (ref "E19") (pin "U2") (pinfunction "S_U2") (pintype "input"))
      (node (ref "F20") (pin "K2") (pinfunction "OUT_K2") (pintype "output"))
    )
    (net (code "395") (name "IOP124_") (class "Default")
      (node (ref "E09") (pin "T2") (pinfunction "IN1_T2") (pintype "input"))
      (node (ref "E11") (pin "S1") (pinfunction "OUT_S1") (pintype "output"))
      (node (ref "F30") (pin "D2") (pinfunction "IN1_D2") (pintype "input"))
    )
    (net (code "396") (name "IOT") (class "Default")
      (node (ref "A06") (pin "F1") (pinfunction "OUT_F1") (pintype "output"))
      (node (ref "A14") (pin "E1") (pinfunction "IN2_E1") (pintype "input"))
      (node (ref "C12") (pin "F2") (pinfunction "IN3_F2") (pintype "input"))
      (node (ref "C12") (pin "H2") (pinfunction "IN4_H2") (pintype "input"))
      (node (ref "D09") (pin "F1") (pinfunction "IN2_F1") (pintype "input"))
      (node (ref "D10") (pin "K2") (pinfunction "IN1_K2") (pintype "input"))
      (node (ref "E26") (pin "M2") (pinfunction "IN3B_M2") (pintype "input"))
      (node (ref "F09") (pin "F2") (pinfunction "IN7_F2") (pintype "input"))
      (node (ref "F19") (pin "R2") (pinfunction "IN1_R2") (pintype "input"))
      (node (ref "F20") (pin "R1") (pinfunction "IN2_R1") (pintype "input"))
    )
    (net (code "397") (name "IOT632") (class "Default")
      (node (ref "HJ32") (pin "BM2") (pinfunction "BM2_BM2") (pintype "input"))
      (node (ref "J33") (pin "P1") (pinfunction "P1_P1") (pintype "output"))
    )
    (net (code "398") (name "IOT634") (class "Default")
      (node (ref "HJ32") (pin "AH1") (pinfunction "AH1_AH1") (pintype "input"))
      (node (ref "J33") (pin "R1") (pinfunction "R1_R1") (pintype "output"))
    )
    (net (code "399") (name "IOT_") (class "Default")
      (node (ref "A06") (pin "D1") (pinfunction "IN1_D1") (pintype "input"))
      (node (ref "D40") (pin "H2") (pinfunction "P$2_H2") (pintype "bidirectional"))
      (node (ref "F11") (pin "E1") (pinfunction "OUT_E1") (pintype "output"))
    )
    (net (code "400") (name "IOT_OPR_") (class "Default")
      (node (ref "E24") (pin "F2") (pinfunction "OUT_F2") (pintype "output"))
      (node (ref "E25") (pin "J2") (pinfunction "IN1_J2") (pintype "input"))
      (node (ref "F23") (pin "F1") (pinfunction "IN1_F1") (pintype "input"))
    )
    (net (code "401") (name "IO_BUS_IN00_") (class "Default")
      (node (ref "HJ31") (pin "AF2") (pinfunction "AF2_AF2") (pintype "open_collector"))
      (node (ref "HJ32") (pin "AF1") (pinfunction "AF1_AF1") (pintype "open_collector"))
      (node (ref "J13") (pin "B1") (pinfunction "IN2_B1") (pintype "passive"))
    )
    (net (code "402") (name "IO_BUS_IN01_") (class "Default")
      (node (ref "HJ31") (pin "BD1") (pinfunction "BD1_BD1") (pintype "open_collector"))
      (node (ref "HJ32") (pin "AF2") (pinfunction "AF2_AF2") (pintype "open_collector"))
      (node (ref "J13") (pin "E2") (pinfunction "IN2_E2") (pintype "passive"))
    )
    (net (code "403") (name "IO_BUS_IN02_") (class "Default")
      (node (ref "HJ31") (pin "AF1") (pinfunction "AF1_AF1") (pintype "open_collector"))
      (node (ref "HJ32") (pin "AH2") (pinfunction "AH2_AH2") (pintype "open_collector"))
      (node (ref "J13") (pin "H1") (pinfunction "IN2_H1") (pintype "passive"))
    )
    (net (code "404") (name "IO_BUS_IN03_") (class "Default")
      (node (ref "HJ31") (pin "BB1") (pinfunction "BB1_BB1") (pintype "open_collector"))
      (node (ref "HJ32") (pin "AJ2") (pinfunction "AJ2_AJ2") (pintype "open_collector"))
      (node (ref "J13") (pin "L2") (pinfunction "IN2_L2") (pintype "passive"))
    )
    (net (code "405") (name "IO_BUS_IN04_") (class "Default")
      (node (ref "HJ26") (pin "AP2") (pinfunction "AP2_AP2") (pintype "open_collector"))
      (node (ref "HJ31") (pin "AJ2") (pinfunction "AJ2_AJ2") (pintype "open_collector"))
      (node (ref "HJ32") (pin "AN2") (pinfunction "AN2_AN2") (pintype "open_collector"))
      (node (ref "J13") (pin "N1") (pinfunction "IN2_N1") (pintype "passive"))
    )
    (net (code "406") (name "IO_BUS_IN05_") (class "Default")
      (node (ref "HJ26") (pin "AS2") (pinfunction "AS2_AS2") (pintype "open_collector"))
      (node (ref "HJ31") (pin "AU1") (pinfunction "AU1_AU1") (pintype "open_collector"))
      (node (ref "HJ32") (pin "AM2") (pinfunction "AM2_AM2") (pintype "open_collector"))
      (node (ref "J13") (pin "S2") (pinfunction "IN2_S2") (pintype "passive"))
    )
    (net (code "407") (name "IO_BUS_IN06_") (class "Default")
      (node (ref "HJ26") (pin "AR1") (pinfunction "AR1_AR1") (pintype "open_collector"))
      (node (ref "HJ31") (pin "AJ1") (pinfunction "AJ1_AJ1") (pintype "open_collector"))
      (node (ref "HJ32") (pin "AU2") (pinfunction "AU2_AU2") (pintype "open_collector"))
      (node (ref "J14") (pin "B1") (pinfunction "IN2_B1") (pintype "passive"))
    )
    (net (code "408") (name "IO_BUS_IN07_") (class "Default")
      (node (ref "HJ26") (pin "AN2") (pinfunction "AN2_AN2") (pintype "open_collector"))
      (node (ref "HJ31") (pin "AV2") (pinfunction "AV2_AV2") (pintype "open_collector"))
      (node (ref "HJ32") (pin "AV2") (pinfunction "AV2_AV2") (pintype "open_collector"))
      (node (ref "J14") (pin "E2") (pinfunction "IN2_E2") (pintype "passive"))
    )
    (net (code "409") (name "IO_BUS_IN08_") (class "Default")
      (node (ref "HJ26") (pin "AS1") (pinfunction "AS1_AS1") (pintype "open_collector"))
      (node (ref "HJ31") (pin "AM1") (pinfunction "AM1_AM1") (pintype "open_collector"))
      (node (ref "HJ32") (pin "BP2") (pinfunction "BP2_BP2") (pintype "open_collector"))
      (node (ref "J14") (pin "H1") (pinfunction "IN2_H1") (pintype "passive"))
    )
    (net (code "410") (name "IO_BUS_IN09_") (class "Default")
      (node (ref "HJ26") (pin "AP1") (pinfunction "AP1_AP1") (pintype "open_collector"))
      (node (ref "HJ31") (pin "AP2") (pinfunction "AP2_AP2") (pintype "open_collector"))
      (node (ref "HJ32") (pin "BN2") (pinfunction "BN2_BN2") (pintype "open_collector"))
      (node (ref "J14") (pin "L2") (pinfunction "IN2_L2") (pintype "passive"))
    )
    (net (code "411") (name "IO_BUS_IN10_") (class "Default")
      (node (ref "HJ26") (pin "AR2") (pinfunction "AR2_AR2") (pintype "open_collector"))
      (node (ref "HJ31") (pin "AM2") (pinfunction "AM2_AM2") (pintype "open_collector"))
      (node (ref "HJ32") (pin "BJ2") (pinfunction "BJ2_BJ2") (pintype "open_collector"))
      (node (ref "J14") (pin "N1") (pinfunction "IN2_N1") (pintype "passive"))
    )
    (net (code "412") (name "IO_BUS_IN11_") (class "Default")
      (node (ref "HJ26") (pin "AN1") (pinfunction "AN1_AN1") (pintype "open_collector"))
      (node (ref "HJ31") (pin "AS1") (pinfunction "AS1_AS1") (pintype "open_collector"))
      (node (ref "HJ32") (pin "BH2") (pinfunction "BH2_BH2") (pintype "open_collector"))
      (node (ref "J14") (pin "S2") (pinfunction "IN2_S2") (pintype "passive"))
    )
    (net (code "413") (name "IO_BUS_IN_AC_CLR_") (class "Default")
      (node (ref "J15") (pin "H1") (pinfunction "IN2_H1") (pintype "passive"))
    )
    (net (code "414") (name "IO_BUS_IN_INT_") (class "Default")
      (node (ref "H30") (pin "C1") (pinfunction "C1_C1") (pintype "open_collector"))
      (node (ref "HJ23") (pin "BP2") (pinfunction "BP2_BP2") (pintype "open_collector"))
      (node (ref "HJ26") (pin "AL2") (pinfunction "AL2_AL2") (pintype "open_collector"))
      (node (ref "HJ28") (pin "BS2") (pinfunction "BS2_BS2") (pintype "open_collector"))
      (node (ref "HJ29") (pin "BF2") (pinfunction "BF2_BF2") (pintype "open_collector"))
      (node (ref "J15") (pin "E2") (pinfunction "IN2_E2") (pintype "passive"))
      (node (ref "J33") (pin "N2") (pinfunction "N2_N2") (pintype "open_collector"))
    )
    (net (code "415") (name "IO_BUS_IN_SKIP_") (class "Default")
      (node (ref "H30") (pin "H1") (pinfunction "H1_H1") (pintype "open_collector"))
      (node (ref "HJ23") (pin "BR2") (pinfunction "BR2_BR2") (pintype "open_collector"))
      (node (ref "HJ26") (pin "AK2") (pinfunction "AK2_AK2") (pintype "open_collector"))
      (node (ref "HJ28") (pin "BN2") (pinfunction "BN2_BN2") (pintype "open_collector"))
      (node (ref "HJ29") (pin "BE2") (pinfunction "BE2_BE2") (pintype "open_collector"))
      (node (ref "J15") (pin "B1") (pinfunction "IN2_B1") (pintype "passive"))
      (node (ref "J33") (pin "P2") (pinfunction "P2_P2") (pintype "open_collector"))
    )
    (net (code "416") (name "IO_ENABLE") (class "Default")
      (node (ref "E28") (pin "J2") (pinfunction "IN2A_J2") (pintype "input"))
      (node (ref "E30") (pin "J2") (pinfunction "IN2A_J2") (pintype "input"))
      (node (ref "EF34") (pin "BL2") (pinfunction "BL2_BL2") (pintype "input"))
      (node (ref "EF35") (pin "BL2") (pinfunction "BL2_BL2") (pintype "input"))
      (node (ref "EF36") (pin "BL2") (pinfunction "BL2_BL2") (pintype "input"))
      (node (ref "EF37") (pin "BL2") (pinfunction "BL2_BL2") (pintype "input"))
      (node (ref "EF38") (pin "BL2") (pinfunction "BL2_BL2") (pintype "input"))
      (node (ref "EF39") (pin "BL2") (pinfunction "BL2_BL2") (pintype "input"))
      (node (ref "F30") (pin "J2") (pinfunction "OUT_J2") (pintype "open_collector"))
    )
    (net (code "417") (name "IO_END") (class "Default")
      (node (ref "E12") (pin "H1") (pinfunction "IN1_H1") (pintype "input"))
      (node (ref "E20") (pin "N1") (pinfunction "C_N1") (pintype "input"))
      (node (ref "F18") (pin "F1") (pinfunction "OUT_F1") (pintype "output"))
    )
    (net (code "418") (name "IO_END_") (class "Default")
      (node (ref "E12") (pin "E2") (pinfunction "IN2_E2") (pintype "input"))
      (node (ref "E12") (pin "K1") (pinfunction "OUT_K1") (pintype "output"))
      (node (ref "E14") (pin "R2") (pinfunction "IN3_R2") (pintype "input"))
    )
    (net (code "419") (name "IO_ON") (class "Default")
      (node (ref "E09") (pin "U2") (pinfunction "IN2_U2") (pintype "input"))
      (node (ref "E20") (pin "S1") (pinfunction "1_S1") (pintype "output"))
    )
    (net (code "420") (name "IO_PC_ENABLE_") (class "Default")
      (node (ref "E09") (pin "V2") (pinfunction "OUT_V2") (pintype "output"))
      (node (ref "F09") (pin "K1") (pinfunction "IN4_K1") (pintype "input"))
      (node (ref "F11") (pin "N1") (pinfunction "IN2_N1") (pintype "input"))
    )
    (net (code "421") (name "IO_PC_LOAD") (class "Default")
      (node (ref "F32") (pin "L2") (pinfunction "IN1_L2") (pintype "input"))
      (node (ref "J11") (pin "V2") (pinfunction "P$2_V2") (pintype "bidirectional"))
    )
    (net (code "422") (name "IO_SKIP") (class "Default")
      (node (ref "E28") (pin "K2") (pinfunction "IN2B_K2") (pintype "input"))
      (node (ref "J15") (pin "E1") (pinfunction "OUT_E1") (pintype "output"))
    )
    (net (code "423") (name "IO_START_") (class "Default")
      (node (ref "E12") (pin "D1") (pinfunction "IN1_D1") (pintype "input"))
      (node (ref "E15") (pin "R2") (pinfunction "IN2_R2") (pintype "input"))
      (node (ref "E15") (pin "S1") (pinfunction "OUT_S1") (pintype "output"))
      (node (ref "E20") (pin "R1") (pinfunction "S_R1") (pintype "input"))
    )
    (net (code "424") (name "IO_STROBE") (class "Default")
      (node (ref "E26") (pin "L2") (pinfunction "IN3A_L2") (pintype "input"))
      (node (ref "F12") (pin "F1") (pinfunction "OUT_F1") (pintype "output"))
      (node (ref "F25") (pin "T2") (pinfunction "IN1_T2") (pintype "input"))
    )
    (net (code "425") (name "IPC_ENABLE") (class "Default")
      (node (ref "F09") (pin "P2") (pinfunction "OUT_P2") (pintype "output"))
      (node (ref "F20") (pin "L2") (pinfunction "IN1_L2") (pintype "input"))
    )
    (net (code "426") (name "IR0") (class "Default")
      (node (ref "E20") (pin "F1") (pinfunction "0_F1") (pintype "output"))
      (node (ref "E21") (pin "K1") (pinfunction "IN1_K1") (pintype "input"))
      (node (ref "E21") (pin "N2") (pinfunction "IN1_N2") (pintype "input"))
      (node (ref "E21") (pin "P1") (pinfunction "IN1_P1") (pintype "input"))
      (node (ref "E21") (pin "T2") (pinfunction "IN1_T2") (pintype "input"))
      (node (ref "E24") (pin "D2") (pinfunction "IN1_D2") (pintype "input"))
      (node (ref "F11") (pin "A1") (pinfunction "IN1_A1") (pintype "input"))
    )
    (net (code "427") (name "IR0_") (class "Default")
      (node (ref "E20") (pin "E1") (pinfunction "1_E1") (pintype "output"))
      (node (ref "E21") (pin "A1") (pinfunction "IN1_A1") (pintype "input"))
      (node (ref "E21") (pin "D2") (pinfunction "IN1_D2") (pintype "input"))
      (node (ref "E21") (pin "E1") (pinfunction "IN1_E1") (pintype "input"))
      (node (ref "E21") (pin "J2") (pinfunction "IN1_J2") (pintype "input"))
    )
    (net (code "428") (name "IR1") (class "Default")
      (node (ref "E20") (pin "H2") (pinfunction "1_H2") (pintype "output"))
      (node (ref "E21") (pin "F1") (pinfunction "IN2_F1") (pintype "input"))
      (node (ref "E21") (pin "K2") (pinfunction "IN2_K2") (pintype "input"))
      (node (ref "E21") (pin "P2") (pinfunction "IN2_P2") (pintype "input"))
      (node (ref "E21") (pin "U2") (pinfunction "IN2_U2") (pintype "input"))
      (node (ref "E24") (pin "E2") (pinfunction "IN2_E2") (pintype "input"))
      (node (ref "F11") (pin "B1") (pinfunction "IN2_B1") (pintype "input"))
    )
    (net (code "429") (name "IR1_") (class "Default")
      (node (ref "E20") (pin "J2") (pinfunction "0_J2") (pintype "output"))
      (node (ref "E21") (pin "B1") (pinfunction "IN2_B1") (pintype "input"))
      (node (ref "E21") (pin "E2") (pinfunction "IN2_E2") (pintype "input"))
      (node (ref "E21") (pin "L1") (pinfunction "IN2_L1") (pintype "input"))
      (node (ref "E21") (pin "R1") (pinfunction "IN2_R1") (pintype "input"))
    )
    (net (code "430") (name "IR2") (class "Default")
      (node (ref "E20") (pin "L1") (pinfunction "1_L1") (pintype "output"))
      (node (ref "E21") (pin "C1") (pinfunction "IN3_C1") (pintype "input"))
      (node (ref "E21") (pin "L2") (pinfunction "IN3_L2") (pintype "input"))
      (node (ref "E21") (pin "S1") (pinfunction "IN3_S1") (pintype "input"))
      (node (ref "E21") (pin "V2") (pinfunction "IN3_V2") (pintype "input"))
    )
    (net (code "431") (name "IR2_") (class "Default")
      (node (ref "E20") (pin "M1") (pinfunction "0_M1") (pintype "output"))
      (node (ref "E21") (pin "F2") (pinfunction "IN3_F2") (pintype "input"))
      (node (ref "E21") (pin "H1") (pinfunction "IN3_H1") (pintype "input"))
      (node (ref "E21") (pin "M1") (pinfunction "IN3_M1") (pintype "input"))
      (node (ref "E21") (pin "R2") (pinfunction "IN3_R2") (pintype "input"))
      (node (ref "F11") (pin "C1") (pinfunction "IN3_C1") (pintype "input"))
    )
    (net (code "432") (name "ISZ") (class "Default")
      (node (ref "E22") (pin "F2") (pinfunction "OUT_F2") (pintype "output"))
      (node (ref "E27") (pin "D1") (pinfunction "IN1D_D1") (pintype "input"))
      (node (ref "E28") (pin "H2") (pinfunction "IN1D_H2") (pintype "input"))
    )
    (net (code "433") (name "ISZ_") (class "Default")
      (node (ref "D40") (pin "P1") (pinfunction "P$2_P1") (pintype "bidirectional"))
      (node (ref "E21") (pin "J1") (pinfunction "OUT_J1") (pintype "output"))
      (node (ref "E22") (pin "D2") (pinfunction "IN1_D2") (pintype "input"))
    )
    (net (code "434") (name "I_IOT_") (class "Default")
      (node (ref "A05") (pin "J1") (pinfunction "IN2_J1") (pintype "input"))
      (node (ref "E21") (pin "S2") (pinfunction "OUT_S2") (pintype "output"))
      (node (ref "E22") (pin "T2") (pinfunction "IN1_T2") (pintype "input"))
    )
    (net (code "435") (name "I_M_D") (class "Default")
      (node (ref "HJ32") (pin "BU1") (pinfunction "BU1_BU1") (pintype "output"))
      (node (ref "J33") (pin "K1") (pinfunction "K1_K1") (pintype "input"))
    )
    (net (code "436") (name "JMP") (class "Default")
      (node (ref "E22") (pin "N2") (pinfunction "OUT_N2") (pintype "output"))
      (node (ref "E26") (pin "B1") (pinfunction "IN1B_B1") (pintype "input"))
      (node (ref "E26") (pin "P1") (pinfunction "IN5C_P1") (pintype "input"))
      (node (ref "E29") (pin "D1") (pinfunction "IN1D_D1") (pintype "input"))
      (node (ref "F27") (pin "B1") (pinfunction "IN2_B1") (pintype "input"))
    )
    (net (code "437") (name "JMP_") (class "Default")
      (node (ref "A17") (pin "D1") (pinfunction "IN1_D1") (pintype "input"))
      (node (ref "B20") (pin "A1") (pinfunction "IN1_A1") (pintype "input"))
      (node (ref "D40") (pin "L2") (pinfunction "P$2_L2") (pintype "bidirectional"))
      (node (ref "E21") (pin "U1") (pinfunction "OUT_U1") (pintype "output"))
      (node (ref "E22") (pin "L2") (pinfunction "IN1_L2") (pintype "input"))
      (node (ref "E24") (pin "E1") (pinfunction "IN2_E1") (pintype "input"))
      (node (ref "E29") (pin "P1") (pinfunction "IN5C_P1") (pintype "input"))
      (node (ref "F23") (pin "J1") (pinfunction "IN3_J1") (pintype "input"))
    )
    (net (code "438") (name "JMS") (class "Default")
      (node (ref "E22") (pin "K1") (pinfunction "OUT_K1") (pintype "output"))
      (node (ref "E27") (pin "P1") (pinfunction "IN5C_P1") (pintype "input"))
      (node (ref "E29") (pin "F2") (pinfunction "IN1C_F2") (pintype "input"))
      (node (ref "E30") (pin "P1") (pinfunction "IN5C_P1") (pintype "input"))
      (node (ref "F26") (pin "R2") (pinfunction "IN3_R2") (pintype "input"))
      (node (ref "F28") (pin "H1") (pinfunction "IN3_H1") (pintype "input"))
    )
    (net (code "439") (name "JMS_") (class "Default")
      (node (ref "A17") (pin "E1") (pinfunction "IN2_E1") (pintype "input"))
      (node (ref "B20") (pin "B1") (pinfunction "IN2_B1") (pintype "input"))
      (node (ref "D40") (pin "S1") (pinfunction "P$2_S1") (pintype "bidirectional"))
      (node (ref "E21") (pin "N1") (pinfunction "OUT_N1") (pintype "output"))
      (node (ref "E22") (pin "H1") (pinfunction "IN1_H1") (pintype "input"))
    )
    (net (code "440") (name "KCC_") (class "Default")
      (node (ref "EF01") (pin "AE2") (pinfunction "AE2_AE2") (pintype "output"))
      (node (ref "EF01") (pin "AV2") (pinfunction "AV2_AV2") (pintype "input"))
    )
    (net (code "441") (name "KEYBOARD_FLAG_") (class "Default")
      (node (ref "EF01") (pin "AF2") (pinfunction "AF2_AF2") (pintype "output"))
      (node (ref "F19") (pin "P1") (pinfunction "IN3_P1") (pintype "input"))
    )
    (net (code "442") (name "KEY_CONT") (class "Default")
      (node (ref "E11") (pin "S2") (pinfunction "OUT_S2") (pintype "output"))
      (node (ref "E15") (pin "J1") (pinfunction "IN2_J1") (pintype "input"))
    )
    (net (code "443") (name "KEY_CONT_") (class "Default")
      (node (ref "B40") (pin "S2") (pinfunction "P$2_S2") (pintype "bidirectional"))
      (node (ref "E11") (pin "R2") (pinfunction "IN2_R2") (pintype "input"))
      (node (ref "F19") (pin "H2") (pinfunction "IN4_H2") (pintype "input"))
    )
    (net (code "444") (name "KEY_DP") (class "Default")
      (node (ref "E11") (pin "F2") (pinfunction "OUT_F2") (pintype "output"))
      (node (ref "E29") (pin "S2") (pinfunction "IN4D_S2") (pintype "input"))
      (node (ref "F29") (pin "P1") (pinfunction "IN1_P1") (pintype "input"))
    )
    (net (code "445") (name "KEY_DP_") (class "Default")
      (node (ref "B40") (pin "M2") (pinfunction "P$2_M2") (pintype "bidirectional"))
      (node (ref "E11") (pin "D2") (pinfunction "IN1_D2") (pintype "input"))
      (node (ref "E11") (pin "H1") (pinfunction "IN1_H1") (pintype "input"))
    )
    (net (code "446") (name "KEY_EXDP") (class "Default")
      (node (ref "E11") (pin "K1") (pinfunction "OUT_K1") (pintype "output"))
      (node (ref "E11") (pin "L2") (pinfunction "IN1_L2") (pintype "input"))
      (node (ref "E13") (pin "H1") (pinfunction "IN3A_H1") (pintype "input"))
      (node (ref "E27") (pin "K2") (pinfunction "IN2B_K2") (pintype "input"))
      (node (ref "E30") (pin "L1") (pinfunction "IN4B_L1") (pintype "input"))
    )
    (net (code "447") (name "KEY_EXDP_") (class "Default")
      (node (ref "E11") (pin "N2") (pinfunction "OUT_N2") (pintype "output"))
      (node (ref "E12") (pin "H2") (pinfunction "IN1_H2") (pintype "input"))
      (node (ref "E14") (pin "L2") (pinfunction "IN3_L2") (pintype "input"))
      (node (ref "F19") (pin "F2") (pinfunction "IN3_F2") (pintype "input"))
    )
    (net (code "448") (name "KEY_EX_") (class "Default")
      (node (ref "B40") (pin "R2") (pinfunction "P$2_R2") (pintype "bidirectional"))
      (node (ref "E11") (pin "J1") (pinfunction "IN2_J1") (pintype "input"))
    )
    (net (code "449") (name "KEY_LA") (class "Default")
      (node (ref "E11") (pin "C1") (pinfunction "OUT_C1") (pintype "output"))
      (node (ref "F29") (pin "P2") (pinfunction "IN1_P2") (pintype "input"))
    )
    (net (code "450") (name "KEY_LAEXDP") (class "Default")
      (node (ref "E12") (pin "K2") (pinfunction "OUT_K2") (pintype "output"))
      (node (ref "E26") (pin "L1") (pinfunction "IN4B_L1") (pintype "input"))
      (node (ref "F21") (pin "D1") (pinfunction "IN1_D1") (pintype "input"))
    )
    (net (code "451") (name "KEY_LAEXDP_") (class "Default")
      (node (ref "F11") (pin "T2") (pinfunction "IN3_T2") (pintype "input"))
      (node (ref "F21") (pin "F1") (pinfunction "OUT_F1") (pintype "output"))
    )
    (net (code "452") (name "KEY_LAMFTS0_") (class "Default")
      (node (ref "A17") (pin "H1") (pinfunction "IN1_H1") (pintype "input"))
      (node (ref "A17") (pin "L1") (pinfunction "IN1_L1") (pintype "input"))
      (node (ref "A17") (pin "P1") (pinfunction "IN1_P1") (pintype "input"))
      (node (ref "A19") (pin "U2") (pinfunction "IN2_U2") (pintype "input"))
      (node (ref "B06") (pin "R2") (pinfunction "IN2_R2") (pintype "input"))
      (node (ref "F29") (pin "S2") (pinfunction "OUT_S2") (pintype "output"))
      (node (ref "F30") (pin "P1") (pinfunction "IN3_P1") (pintype "input"))
    )
    (net (code "453") (name "KEY_LA_") (class "Default")
      (node (ref "B40") (pin "L2") (pinfunction "P$2_L2") (pintype "bidirectional"))
      (node (ref "E11") (pin "A1") (pinfunction "IN1_A1") (pintype "input"))
      (node (ref "E12") (pin "J2") (pinfunction "IN2_J2") (pintype "input"))
      (node (ref "E15") (pin "B1") (pinfunction "IN2_B1") (pintype "input"))
      (node (ref "F19") (pin "D2") (pinfunction "IN1_D2") (pintype "input"))
    )
    (net (code "454") (name "KEY_SISTOP") (class "Default")
      (node (ref "E11") (pin "N1") (pinfunction "OUT_N1") (pintype "output"))
      (node (ref "E13") (pin "E1") (pinfunction "IN2A_E1") (pintype "input"))
    )
    (net (code "455") (name "KEY_SI_") (class "Default")
      (node (ref "B40") (pin "V2") (pinfunction "P$2_V2") (pintype "bidirectional"))
      (node (ref "E11") (pin "M1") (pinfunction "IN2_M1") (pintype "input"))
    )
    (net (code "456") (name "KEY_SS") (class "Default")
      (node (ref "E11") (pin "K2") (pinfunction "OUT_K2") (pintype "output"))
      (node (ref "E13") (pin "M1") (pinfunction "IN5A_M1") (pintype "input"))
    )
    (net (code "457") (name "KEY_SS_") (class "Default")
      (node (ref "B40") (pin "U2") (pinfunction "P$2_U2") (pintype "bidirectional"))
      (node (ref "E11") (pin "J2") (pinfunction "IN2_J2") (pintype "input"))
    )
    (net (code "458") (name "KEY_ST") (class "Default")
      (node (ref "E11") (pin "F1") (pinfunction "OUT_F1") (pintype "output"))
      (node (ref "E26") (pin "K2") (pinfunction "IN2B_K2") (pintype "input"))
      (node (ref "E26") (pin "U2") (pinfunction "IN2B_U2") (pintype "input"))
      (node (ref "E28") (pin "F1") (pinfunction "IN2B_F1") (pintype "input"))
      (node (ref "F20") (pin "U2") (pinfunction "IN2_U2") (pintype "input"))
      (node (ref "F22") (pin "E2") (pinfunction "IN2_E2") (pintype "input"))
    )
    (net (code "459") (name "KEY_STEXDP") (class "Default")
      (node (ref "A19") (pin "H2") (pinfunction "IN1_H2") (pintype "input"))
      (node (ref "E14") (pin "F2") (pinfunction "IN3_F2") (pintype "input"))
      (node (ref "E14") (pin "M2") (pinfunction "OUT_M2") (pintype "output"))
      (node (ref "F32") (pin "E1") (pinfunction "IN2_E1") (pintype "input"))
    )
    (net (code "460") (name "KEY_STOP_") (class "Default")
      (node (ref "B40") (pin "T2") (pinfunction "P$2_T2") (pintype "bidirectional"))
      (node (ref "E11") (pin "L1") (pinfunction "IN1_L1") (pintype "input"))
    )
    (net (code "461") (name "KEY_ST_") (class "Default")
      (node (ref "B40") (pin "K2") (pinfunction "P$2_K2") (pintype "bidirectional"))
      (node (ref "E11") (pin "D1") (pinfunction "IN1_D1") (pintype "input"))
      (node (ref "E14") (pin "J2") (pinfunction "IN1_J2") (pintype "input"))
      (node (ref "F19") (pin "E2") (pinfunction "IN2_E2") (pintype "input"))
    )
    (net (code "462") (name "LBAR_ENABLE") (class "Default")
      (node (ref "F29") (pin "N2") (pinfunction "OUT_N2") (pintype "output"))
      (node (ref "F33") (pin "M2") (pinfunction "IN3B_M2") (pintype "input"))
    )
    (net (code "463") (name "LEFT_SHIFT") (class "Default")
      (node (ref "E31") (pin "P2") (pinfunction "OUT_P2") (pintype "open_collector"))
      (node (ref "EF34") (pin "AF2") (pinfunction "AF2_AF2") (pintype "input"))
      (node (ref "EF35") (pin "AF2") (pinfunction "AF2_AF2") (pintype "input"))
      (node (ref "EF36") (pin "AF2") (pinfunction "AF2_AF2") (pintype "input"))
      (node (ref "EF37") (pin "AF2") (pinfunction "AF2_AF2") (pintype "input"))
      (node (ref "EF38") (pin "AF2") (pinfunction "AF2_AF2") (pintype "input"))
      (node (ref "EF39") (pin "AF2") (pinfunction "AF2_AF2") (pintype "input"))
      (node (ref "F33") (pin "L1") (pinfunction "IN4B_L1") (pintype "input"))
    )
    (net (code "464") (name "LEFT_SHIFT_") (class "Default")
      (node (ref "D12") (pin "H2") (pinfunction "IN1_H2") (pintype "input"))
      (node (ref "D12") (pin "K1") (pinfunction "OUT_K1") (pintype "output"))
      (node (ref "D12") (pin "U2") (pinfunction "IN2_U2") (pintype "input"))
    )
    (net (code "465") (name "LHS") (class "Default")
      (node (ref "D05") (pin "E1") (pinfunction "OUT_E1") (pintype "output"))
      (node (ref "D11") (pin "M2") (pinfunction "D_M2") (pintype "input"))
    )
    (net (code "466") (name "LHS_") (class "Default")
      (node (ref "D04") (pin "T2") (pinfunction "P$2_T2") (pintype "bidirectional"))
      (node (ref "D05") (pin "A1") (pinfunction "IN_A1") (pintype "input"))
      (node (ref "D05") (pin "B1") (pinfunction "IN2_B1") (pintype "bidirectional"))
      (node (ref "D05") (pin "C1") (pinfunction "IN3_C1") (pintype "input"))
      (node (ref "D05") (pin "D1") (pinfunction "IN4_D1") (pintype "input"))
    )
    (net (code "467") (name "LH_TO_HS") (class "Default")
      (node (ref "D06") (pin "F1") (pinfunction "OUT_F1") (pintype "output"))
      (node (ref "D07") (pin "R1") (pinfunction "IN2_R1") (pintype "input"))
      (node (ref "D11") (pin "L2") (pinfunction "C_L2") (pintype "input"))
    )
    (net (code "468") (name "LIGHT_PEN") (class "Default")
      (node (ref "D03") (pin "V2") (pinfunction "P$2_V2") (pintype "bidirectional"))
      (node (ref "HJ23") (pin "AN2") (pinfunction "AN2_AN2") (pintype "input"))
    )
    (net (code "469") (name "LINE_") (class "Default")
      (node (ref "C10") (pin "P1") (pinfunction "IN1_P1") (pintype "input"))
      (node (ref "C10") (pin "T2") (pinfunction "IN1_T2") (pintype "input"))
      (node (ref "J15") (pin "P2") (pinfunction "OUT_P2") (pintype "output"))
    )
    (net (code "470") (name "LINE_HOLD_") (class "Default")
      (node (ref "C07") (pin "J2") (pinfunction "IN1_J2") (pintype "input"))
      (node (ref "D09") (pin "M1") (pinfunction "IN3_M1") (pintype "input"))
      (node (ref "D10") (pin "V2") (pinfunction "OUT_V2") (pintype "output"))
    )
    (net (code "471") (name "LINK") (class "Default")
      (node (ref "E24") (pin "T2") (pinfunction "IN1_T2") (pintype "input"))
      (node (ref "E33") (pin "V2") (pinfunction "1_V2") (pintype "output"))
      (node (ref "F33") (pin "J2") (pinfunction "IN2A_J2") (pintype "input"))
    )
    (net (code "472") (name "LINK_") (class "Default")
      (node (ref "C40") (pin "B1") (pinfunction "P$2_B1") (pintype "bidirectional"))
      (node (ref "E33") (pin "V1") (pinfunction "0_V1") (pintype "output"))
      (node (ref "F33") (pin "L2") (pinfunction "IN3A_L2") (pintype "input"))
    )
    (net (code "473") (name "LOAD_BF") (class "Default")
      (node (ref "A19") (pin "N2") (pinfunction "OUT_N2") (pintype "output"))
      (node (ref "B18") (pin "L2") (pinfunction "C_L2") (pintype "input"))
      (node (ref "B18") (pin "N1") (pinfunction "C_N1") (pintype "input"))
      (node (ref "B18") (pin "S2") (pinfunction "C_S2") (pintype "input"))
    )
    (net (code "474") (name "LOAD_COUNTER") (class "Default")
      (node (ref "H30") (pin "V2") (pinfunction "V2_V2") (pintype "input"))
      (node (ref "HJ31") (pin "BN1") (pinfunction "BN1_BN1") (pintype "output"))
    )
    (net (code "475") (name "LOAD_IB") (class "Default")
      (node (ref "A18") (pin "C1") (pinfunction "OUT_C1") (pintype "output"))
      (node (ref "B17") (pin "L2") (pinfunction "C_L2") (pintype "input"))
      (node (ref "B17") (pin "N1") (pinfunction "C_N1") (pintype "input"))
      (node (ref "B17") (pin "S2") (pinfunction "C_S2") (pintype "input"))
    )
    (net (code "476") (name "LOAD_SF_") (class "Default")
      (node (ref "A19") (pin "R1") (pinfunction "IN2_R1") (pintype "input"))
      (node (ref "A19") (pin "R2") (pinfunction "IN2_R2") (pintype "input"))
      (node (ref "C12") (pin "P2") (pinfunction "OUT_P2") (pintype "open_collector"))
    )
    (net (code "477") (name "LOW_AC0") (class "Default")
      (node (ref "D21") (pin "D1") (pinfunction "IN4_D1") (pintype "input"))
      (node (ref "E24") (pin "S2") (pinfunction "OUT_S2") (pintype "output"))
      (node (ref "F23") (pin "C1") (pinfunction "IN3_C1") (pintype "input"))
    )
    (net (code "478") (name "L_ENABLE") (class "Default")
      (node (ref "E28") (pin "R1") (pinfunction "OUT_R1") (pintype "output"))
      (node (ref "F33") (pin "K2") (pinfunction "IN2B_K2") (pintype "input"))
    )
    (net (code "479") (name "MA00") (class "Default")
      (node (ref "C31") (pin "E2") (pinfunction "E2_E2") (pintype "input"))
      (node (ref "C38") (pin "E2") (pinfunction "E2_E2") (pintype "input"))
      (node (ref "EF34") (pin "AM2") (pinfunction "AM2_AM2") (pintype "output"))
    )
    (net (code "480") (name "MA00_") (class "Default")
      (node (ref "B14") (pin "A1") (pinfunction "IN1_A1") (pintype "input"))
      (node (ref "C30") (pin "E2") (pinfunction "E2_E2") (pintype "input"))
      (node (ref "C37") (pin "E2") (pinfunction "E2_E2") (pintype "input"))
      (node (ref "E40") (pin "U2") (pinfunction "P$2_U2") (pintype "bidirectional"))
      (node (ref "EF34") (pin "AM1") (pinfunction "AM1_AM1") (pintype "output"))
      (node (ref "F24") (pin "D2") (pinfunction "IN1_D2") (pintype "input"))
    )
    (net (code "481") (name "MA01") (class "Default")
      (node (ref "C30") (pin "H2") (pinfunction "H2_H2") (pintype "input"))
      (node (ref "C31") (pin "H2") (pinfunction "H2_H2") (pintype "input"))
      (node (ref "C37") (pin "H2") (pinfunction "H2_H2") (pintype "input"))
      (node (ref "C38") (pin "H2") (pinfunction "H2_H2") (pintype "input"))
      (node (ref "EF34") (pin "AL2") (pinfunction "AL2_AL2") (pintype "output"))
    )
    (net (code "482") (name "MA01_") (class "Default")
      (node (ref "B14") (pin "D2") (pinfunction "IN1_D2") (pintype "input"))
      (node (ref "E40") (pin "R2") (pinfunction "P$2_R2") (pintype "bidirectional"))
      (node (ref "EF34") (pin "AL1") (pinfunction "AL1_AL1") (pintype "output"))
      (node (ref "F24") (pin "E2") (pinfunction "IN2_E2") (pintype "input"))
    )
    (net (code "483") (name "MA02") (class "Default")
      (node (ref "C30") (pin "F2") (pinfunction "F2_F2") (pintype "input"))
      (node (ref "C31") (pin "F2") (pinfunction "F2_F2") (pintype "input"))
      (node (ref "C37") (pin "F2") (pinfunction "F2_F2") (pintype "input"))
      (node (ref "C38") (pin "F2") (pinfunction "F2_F2") (pintype "input"))
      (node (ref "EF35") (pin "AM2") (pinfunction "AM2_AM2") (pintype "output"))
    )
    (net (code "484") (name "MA02_") (class "Default")
      (node (ref "B14") (pin "F1") (pinfunction "IN1_F1") (pintype "input"))
      (node (ref "E40") (pin "K2") (pinfunction "P$2_K2") (pintype "bidirectional"))
      (node (ref "EF35") (pin "AM1") (pinfunction "AM1_AM1") (pintype "output"))
      (node (ref "F24") (pin "F2") (pinfunction "IN3_F2") (pintype "input"))
    )
    (net (code "485") (name "MA03") (class "Default")
      (node (ref "D26") (pin "E2") (pinfunction "E2_E2") (pintype "input"))
      (node (ref "D33") (pin "E2") (pinfunction "E2_E2") (pintype "input"))
      (node (ref "EF35") (pin "AL2") (pinfunction "AL2_AL2") (pintype "output"))
    )
    (net (code "486") (name "MA03_") (class "Default")
      (node (ref "B14") (pin "K2") (pinfunction "IN1_K2") (pintype "input"))
      (node (ref "D25") (pin "E2") (pinfunction "E2_E2") (pintype "input"))
      (node (ref "D32") (pin "E2") (pinfunction "E2_E2") (pintype "input"))
      (node (ref "E40") (pin "E2") (pinfunction "P$2_E2") (pintype "bidirectional"))
      (node (ref "EF35") (pin "AL1") (pinfunction "AL1_AL1") (pintype "output"))
      (node (ref "F24") (pin "H2") (pinfunction "IN4_H2") (pintype "input"))
    )
    (net (code "487") (name "MA04") (class "Default")
      (node (ref "D25") (pin "H2") (pinfunction "H2_H2") (pintype "input"))
      (node (ref "D26") (pin "H2") (pinfunction "H2_H2") (pintype "input"))
      (node (ref "D32") (pin "H2") (pinfunction "H2_H2") (pintype "input"))
      (node (ref "D33") (pin "H2") (pinfunction "H2_H2") (pintype "input"))
      (node (ref "EF36") (pin "AM2") (pinfunction "AM2_AM2") (pintype "output"))
    )
    (net (code "488") (name "MA04_") (class "Default")
      (node (ref "B14") (pin "M1") (pinfunction "IN1_M1") (pintype "input"))
      (node (ref "E40") (pin "L1") (pinfunction "P$2_L1") (pintype "bidirectional"))
      (node (ref "EF36") (pin "AM1") (pinfunction "AM1_AM1") (pintype "output"))
      (node (ref "F24") (pin "F1") (pinfunction "IN1_F1") (pintype "input"))
    )
    (net (code "489") (name "MA05") (class "Default")
      (node (ref "D25") (pin "F2") (pinfunction "F2_F2") (pintype "input"))
      (node (ref "D26") (pin "F2") (pinfunction "F2_F2") (pintype "input"))
      (node (ref "D32") (pin "F2") (pinfunction "F2_F2") (pintype "input"))
      (node (ref "D33") (pin "F2") (pinfunction "F2_F2") (pintype "input"))
      (node (ref "EF36") (pin "AL2") (pinfunction "AL2_AL2") (pintype "output"))
    )
    (net (code "490") (name "MA05_") (class "Default")
      (node (ref "B14") (pin "R2") (pinfunction "IN1_R2") (pintype "input"))
      (node (ref "E40") (pin "E1") (pinfunction "P$2_E1") (pintype "bidirectional"))
      (node (ref "EF36") (pin "AL1") (pinfunction "AL1_AL1") (pintype "output"))
      (node (ref "F24") (pin "H1") (pinfunction "IN2_H1") (pintype "input"))
    )
    (net (code "491") (name "MA06") (class "Default")
      (node (ref "C26") (pin "E2") (pinfunction "E2_E2") (pintype "input"))
      (node (ref "C33") (pin "E2") (pinfunction "E2_E2") (pintype "input"))
      (node (ref "EF37") (pin "AM2") (pinfunction "AM2_AM2") (pintype "output"))
    )
    (net (code "492") (name "MA06_") (class "Default")
      (node (ref "B15") (pin "A1") (pinfunction "IN1_A1") (pintype "input"))
      (node (ref "C25") (pin "E2") (pinfunction "E2_E2") (pintype "input"))
      (node (ref "C32") (pin "E2") (pinfunction "E2_E2") (pintype "input"))
      (node (ref "EF37") (pin "AM1") (pinfunction "AM1_AM1") (pintype "output"))
      (node (ref "F24") (pin "J1") (pinfunction "IN3_J1") (pintype "input"))
      (node (ref "F40") (pin "U2") (pinfunction "P$2_U2") (pintype "bidirectional"))
    )
    (net (code "493") (name "MA07") (class "Default")
      (node (ref "C25") (pin "H2") (pinfunction "H2_H2") (pintype "input"))
      (node (ref "C26") (pin "H2") (pinfunction "H2_H2") (pintype "input"))
      (node (ref "C32") (pin "H2") (pinfunction "H2_H2") (pintype "input"))
      (node (ref "C33") (pin "H2") (pinfunction "H2_H2") (pintype "input"))
      (node (ref "EF37") (pin "AL2") (pinfunction "AL2_AL2") (pintype "output"))
    )
    (net (code "494") (name "MA07_") (class "Default")
      (node (ref "B15") (pin "D2") (pinfunction "IN1_D2") (pintype "input"))
      (node (ref "EF37") (pin "AL1") (pinfunction "AL1_AL1") (pintype "output"))
      (node (ref "F24") (pin "K1") (pinfunction "IN4_K1") (pintype "input"))
      (node (ref "F40") (pin "R2") (pinfunction "P$2_R2") (pintype "bidirectional"))
    )
    (net (code "495") (name "MA08") (class "Default")
      (node (ref "C25") (pin "F2") (pinfunction "F2_F2") (pintype "input"))
      (node (ref "C26") (pin "F2") (pinfunction "F2_F2") (pintype "input"))
      (node (ref "C32") (pin "F2") (pinfunction "F2_F2") (pintype "input"))
      (node (ref "C33") (pin "F2") (pinfunction "F2_F2") (pintype "input"))
      (node (ref "EF38") (pin "AM2") (pinfunction "AM2_AM2") (pintype "output"))
      (node (ref "F25") (pin "L1") (pinfunction "IN1_L1") (pintype "input"))
    )
    (net (code "496") (name "MA08_") (class "Default")
      (node (ref "B15") (pin "F1") (pinfunction "IN1_F1") (pintype "input"))
      (node (ref "EF38") (pin "AM1") (pinfunction "AM1_AM1") (pintype "output"))
      (node (ref "F40") (pin "K2") (pinfunction "P$2_K2") (pintype "bidirectional"))
    )
    (net (code "497") (name "MA09") (class "Default")
      (node (ref "D31") (pin "E2") (pinfunction "E2_E2") (pintype "input"))
      (node (ref "D38") (pin "E2") (pinfunction "E2_E2") (pintype "input"))
      (node (ref "EF38") (pin "AL2") (pinfunction "AL2_AL2") (pintype "output"))
    )
    (net (code "498") (name "MA09_") (class "Default")
      (node (ref "B15") (pin "K2") (pinfunction "IN1_K2") (pintype "input"))
      (node (ref "D30") (pin "E2") (pinfunction "E2_E2") (pintype "input"))
      (node (ref "D37") (pin "E2") (pinfunction "E2_E2") (pintype "input"))
      (node (ref "EF38") (pin "AL1") (pinfunction "AL1_AL1") (pintype "output"))
      (node (ref "F40") (pin "E2") (pinfunction "P$2_E2") (pintype "bidirectional"))
    )
    (net (code "499") (name "MA10") (class "Default")
      (node (ref "D30") (pin "H2") (pinfunction "H2_H2") (pintype "input"))
      (node (ref "D31") (pin "H2") (pinfunction "H2_H2") (pintype "input"))
      (node (ref "D37") (pin "H2") (pinfunction "H2_H2") (pintype "input"))
      (node (ref "D38") (pin "H2") (pinfunction "H2_H2") (pintype "input"))
      (node (ref "EF39") (pin "AM2") (pinfunction "AM2_AM2") (pintype "output"))
    )
    (net (code "500") (name "MA10_") (class "Default")
      (node (ref "B15") (pin "M1") (pinfunction "IN1_M1") (pintype "input"))
      (node (ref "EF39") (pin "AM1") (pinfunction "AM1_AM1") (pintype "output"))
      (node (ref "F40") (pin "L1") (pinfunction "P$2_L1") (pintype "bidirectional"))
    )
    (net (code "501") (name "MA11") (class "Default")
      (node (ref "D30") (pin "F2") (pinfunction "F2_F2") (pintype "input"))
      (node (ref "D31") (pin "F2") (pinfunction "F2_F2") (pintype "input"))
      (node (ref "D37") (pin "F2") (pinfunction "F2_F2") (pintype "input"))
      (node (ref "D38") (pin "F2") (pinfunction "F2_F2") (pintype "input"))
      (node (ref "EF39") (pin "AL2") (pinfunction "AL2_AL2") (pintype "output"))
    )
    (net (code "502") (name "MA11_") (class "Default")
      (node (ref "B15") (pin "R2") (pinfunction "IN1_R2") (pintype "input"))
      (node (ref "EF39") (pin "AL1") (pinfunction "AL1_AL1") (pintype "output"))
      (node (ref "F40") (pin "E1") (pinfunction "P$2_E1") (pintype "bidirectional"))
    )
    (net (code "503") (name "MANUAL_PRESET_") (class "Default")
      (node (ref "B11") (pin "D1") (pinfunction "S_D1") (pintype "input"))
      (node (ref "B11") (pin "F2") (pinfunction "S_F2") (pintype "input"))
      (node (ref "B11") (pin "K1") (pinfunction "S_K1") (pintype "input"))
      (node (ref "D11") (pin "D1") (pinfunction "S_D1") (pintype "input"))
      (node (ref "D11") (pin "F2") (pinfunction "S_F2") (pintype "input"))
      (node (ref "E18") (pin "D1") (pinfunction "S_D1") (pintype "input"))
      (node (ref "E19") (pin "A1") (pinfunction "R_A1") (pintype "input"))
      (node (ref "E20") (pin "K2") (pinfunction "R_K2") (pintype "input"))
      (node (ref "E23") (pin "A1") (pinfunction "R_A1") (pintype "input"))
      (node (ref "E23") (pin "K2") (pinfunction "R_K2") (pintype "input"))
      (node (ref "E33") (pin "K1") (pinfunction "S_K1") (pintype "input"))
      (node (ref "F20") (pin "E1") (pinfunction "IN2_E1") (pintype "input"))
      (node (ref "F30") (pin "V2") (pinfunction "OUT_V2") (pintype "open_collector"))
    )
    (net (code "504") (name "MA_ENABLE0_4") (class "Default")
      (node (ref "EF34") (pin "BP1") (pinfunction "BP1_BP1") (pintype "input"))
      (node (ref "EF34") (pin "BR2") (pinfunction "BR2_BR2") (pintype "input"))
      (node (ref "EF35") (pin "BP1") (pinfunction "BP1_BP1") (pintype "input"))
      (node (ref "EF35") (pin "BR2") (pinfunction "BR2_BR2") (pintype "input"))
      (node (ref "EF36") (pin "BP1") (pinfunction "BP1_BP1") (pintype "input"))
      (node (ref "F31") (pin "L1") (pinfunction "OUT_L1") (pintype "open_collector"))
    )
    (net (code "505") (name "MA_ENABLE5_11") (class "Default")
      (node (ref "EF36") (pin "BR2") (pinfunction "BR2_BR2") (pintype "input"))
      (node (ref "EF37") (pin "BP1") (pinfunction "BP1_BP1") (pintype "input"))
      (node (ref "EF37") (pin "BR2") (pinfunction "BR2_BR2") (pintype "input"))
      (node (ref "EF38") (pin "BP1") (pinfunction "BP1_BP1") (pintype "input"))
      (node (ref "EF38") (pin "BR2") (pinfunction "BR2_BR2") (pintype "input"))
      (node (ref "EF39") (pin "BP1") (pinfunction "BP1_BP1") (pintype "input"))
      (node (ref "EF39") (pin "BR2") (pinfunction "BR2_BR2") (pintype "input"))
      (node (ref "F31") (pin "P2") (pinfunction "OUT_P2") (pintype "open_collector"))
    )
    (net (code "506") (name "MA_LOAD") (class "Default")
      (node (ref "E32") (pin "E1") (pinfunction "OUT_E1") (pintype "open_collector"))
      (node (ref "EF34") (pin "AK1") (pinfunction "AK1_AK1") (pintype "input"))
      (node (ref "EF35") (pin "AK1") (pinfunction "AK1_AK1") (pintype "input"))
      (node (ref "EF36") (pin "AK1") (pinfunction "AK1_AK1") (pintype "input"))
      (node (ref "EF37") (pin "AK1") (pinfunction "AK1_AK1") (pintype "input"))
      (node (ref "EF38") (pin "AK1") (pinfunction "AK1_AK1") (pintype "input"))
      (node (ref "EF39") (pin "AK1") (pinfunction "AK1_AK1") (pintype "input"))
    )
    (net (code "507") (name "MB00") (class "Default")
      (node (ref "A09") (pin "E1") (pinfunction "1A_E1") (pintype "input"))
      (node (ref "B12") (pin "A1") (pinfunction "IN1_A1") (pintype "input"))
      (node (ref "EF34") (pin "AT2") (pinfunction "AT2_AT2") (pintype "output"))
      (node (ref "H13") (pin "H2") (pinfunction "IN2_H2") (pintype "input"))
    )
    (net (code "508") (name "MB00_") (class "Default")
      (node (ref "A09") (pin "A1") (pinfunction "1B_A1") (pintype "input"))
      (node (ref "A27") (pin "D2") (pinfunction "D2_D2") (pintype "input"))
      (node (ref "A36") (pin "D2") (pinfunction "D2_D2") (pintype "input"))
      (node (ref "E40") (pin "R1") (pinfunction "P$2_R1") (pintype "bidirectional"))
      (node (ref "EF34") (pin "AU2") (pinfunction "AU2_AU2") (pintype "output"))
    )
    (net (code "509") (name "MB01") (class "Default")
      (node (ref "A09") (pin "F1") (pinfunction "2A_F1") (pintype "input"))
      (node (ref "B12") (pin "D2") (pinfunction "IN1_D2") (pintype "input"))
      (node (ref "EF34") (pin "AS2") (pinfunction "AS2_AS2") (pintype "output"))
      (node (ref "H13") (pin "N2") (pinfunction "IN2_N2") (pintype "input"))
    )
    (net (code "510") (name "MB01_") (class "Default")
      (node (ref "A09") (pin "B1") (pinfunction "2B_B1") (pintype "input"))
      (node (ref "A27") (pin "D1") (pinfunction "D1_D1") (pintype "input"))
      (node (ref "A36") (pin "D1") (pinfunction "D1_D1") (pintype "input"))
      (node (ref "E40") (pin "P1") (pinfunction "P$2_P1") (pintype "bidirectional"))
      (node (ref "EF34") (pin "AS1") (pinfunction "AS1_AS1") (pintype "output"))
    )
    (net (code "511") (name "MB02") (class "Default")
      (node (ref "A09") (pin "H1") (pinfunction "4A_H1") (pintype "input"))
      (node (ref "B12") (pin "F1") (pinfunction "IN1_F1") (pintype "input"))
      (node (ref "EF35") (pin "AT2") (pinfunction "AT2_AT2") (pintype "output"))
      (node (ref "H13") (pin "U2") (pinfunction "IN2_U2") (pintype "input"))
    )
    (net (code "512") (name "MB02_") (class "Default")
      (node (ref "A09") (pin "C1") (pinfunction "4B_C1") (pintype "input"))
      (node (ref "A27") (pin "M2") (pinfunction "M2_M2") (pintype "input"))
      (node (ref "A36") (pin "M2") (pinfunction "M2_M2") (pintype "input"))
      (node (ref "E40") (pin "F2") (pinfunction "P$2_F2") (pintype "bidirectional"))
      (node (ref "EF35") (pin "AU2") (pinfunction "AU2_AU2") (pintype "output"))
    )
    (net (code "513") (name "MB03") (class "Default")
      (node (ref "A09") (pin "J1") (pinfunction "8A_J1") (pintype "input"))
      (node (ref "B12") (pin "K2") (pinfunction "IN1_K2") (pintype "input"))
      (node (ref "C11") (pin "P1") (pinfunction "IN1_P1") (pintype "input"))
      (node (ref "D20") (pin "P1") (pinfunction "IN3_P1") (pintype "input"))
      (node (ref "E25") (pin "L2") (pinfunction "IN3_L2") (pintype "input"))
      (node (ref "EF35") (pin "AS2") (pinfunction "AS2_AS2") (pintype "output"))
      (node (ref "F27") (pin "K1") (pinfunction "IN4_K1") (pintype "input"))
      (node (ref "H14") (pin "N2") (pinfunction "IN2_N2") (pintype "input"))
      (node (ref "HJ29") (pin "AF2") (pinfunction "AF2_AF2") (pintype "input"))
      (node (ref "J33") (pin "C1") (pinfunction "C1_C1") (pintype "input"))
    )
    (net (code "514") (name "MB03_") (class "Default")
      (node (ref "A04") (pin "D2") (pinfunction "D2_D2") (pintype "input"))
      (node (ref "A09") (pin "D1") (pinfunction "8B_D1") (pintype "input"))
      (node (ref "A27") (pin "L1") (pinfunction "L1_L1") (pintype "input"))
      (node (ref "A36") (pin "L1") (pinfunction "L1_L1") (pintype "input"))
      (node (ref "B07") (pin "A1") (pinfunction "IN1_A1") (pintype "input"))
      (node (ref "B16") (pin "L2") (pinfunction "IN2_L2") (pintype "input"))
      (node (ref "E26") (pin "C1") (pinfunction "IN1C_C1") (pintype "input"))
      (node (ref "E40") (pin "D2") (pinfunction "P$2_D2") (pintype "bidirectional"))
      (node (ref "EF01") (pin "AD2") (pinfunction "AD2_AD2") (pintype "input"))
      (node (ref "EF02") (pin "AE2") (pinfunction "AE2_AE2") (pintype "input"))
      (node (ref "EF35") (pin "AS1") (pinfunction "AS1_AS1") (pintype "output"))
      (node (ref "F09") (pin "B1") (pinfunction "IN2_B1") (pintype "input"))
      (node (ref "F19") (pin "T2") (pinfunction "IN3_T2") (pintype "input"))
      (node (ref "F23") (pin "K1") (pinfunction "IN4_K1") (pintype "input"))
      (node (ref "F27") (pin "D1") (pinfunction "IN4_D1") (pintype "input"))
      (node (ref "F27") (pin "U2") (pinfunction "IN4_U2") (pintype "input"))
      (node (ref "H14") (pin "H2") (pinfunction "IN2_H2") (pintype "input"))
      (node (ref "H30") (pin "T2") (pinfunction "T2_T2") (pintype "input"))
      (node (ref "HJ23") (pin "BF2") (pinfunction "BF2_BF2") (pintype "input"))
      (node (ref "HJ26") (pin "BD2") (pinfunction "BD2_BD2") (pintype "input"))
      (node (ref "HJ28") (pin "BF2") (pinfunction "BF2_BF2") (pintype "input"))
    )
    (net (code "515") (name "MB04") (class "Default")
      (node (ref "A10") (pin "P2") (pinfunction "1A_P2") (pintype "input"))
      (node (ref "B12") (pin "M1") (pinfunction "IN1_M1") (pintype "input"))
      (node (ref "B16") (pin "M2") (pinfunction "IN3_M2") (pintype "input"))
      (node (ref "E30") (pin "V1") (pinfunction "IN2A_V1") (pintype "input"))
      (node (ref "EF36") (pin "AT2") (pinfunction "AT2_AT2") (pintype "output"))
      (node (ref "F09") (pin "C1") (pinfunction "IN3_C1") (pintype "input"))
      (node (ref "F28") (pin "F2") (pinfunction "IN3_F2") (pintype "input"))
      (node (ref "H15") (pin "H2") (pinfunction "IN2_H2") (pintype "input"))
      (node (ref "J33") (pin "D2") (pinfunction "D2_D2") (pintype "input"))
    )
    (net (code "516") (name "MB04_") (class "Default")
      (node (ref "A04") (pin "E2") (pinfunction "E2_E2") (pintype "input"))
      (node (ref "A10") (pin "K2") (pinfunction "1B_K2") (pintype "input"))
      (node (ref "B07") (pin "B1") (pinfunction "IN2_B1") (pintype "input"))
      (node (ref "B26") (pin "D2") (pinfunction "D2_D2") (pintype "input"))
      (node (ref "B36") (pin "D2") (pinfunction "D2_D2") (pintype "input"))
      (node (ref "C11") (pin "R1") (pinfunction "IN2_R1") (pintype "input"))
      (node (ref "D21") (pin "J1") (pinfunction "IN3_J1") (pintype "input"))
      (node (ref "E30") (pin "H2") (pinfunction "IN1D_H2") (pintype "input"))
      (node (ref "E30") (pin "S1") (pinfunction "IN1A_S1") (pintype "input"))
      (node (ref "E40") (pin "K1") (pinfunction "P$2_K1") (pintype "bidirectional"))
      (node (ref "EF01") (pin "AE1") (pinfunction "AE1_AE1") (pintype "input"))
      (node (ref "EF02") (pin "AE1") (pinfunction "AE1_AE1") (pintype "input"))
      (node (ref "EF36") (pin "AU2") (pinfunction "AU2_AU2") (pintype "output"))
      (node (ref "F19") (pin "U2") (pinfunction "IN4_U2") (pintype "input"))
      (node (ref "H14") (pin "U2") (pinfunction "IN2_U2") (pintype "input"))
      (node (ref "H30") (pin "S2") (pinfunction "S2_S2") (pintype "input"))
      (node (ref "HJ23") (pin "BH2") (pinfunction "BH2_BH2") (pintype "input"))
      (node (ref "HJ26") (pin "BE2") (pinfunction "BE2_BE2") (pintype "input"))
      (node (ref "HJ28") (pin "BD1") (pinfunction "BD1_BD1") (pintype "input"))
      (node (ref "HJ29") (pin "AH2") (pinfunction "AH2_AH2") (pintype "input"))
    )
    (net (code "517") (name "MB05") (class "Default")
      (node (ref "A04") (pin "F2") (pinfunction "F2_F2") (pintype "input"))
      (node (ref "A10") (pin "R2") (pinfunction "2A_R2") (pintype "input"))
      (node (ref "B07") (pin "C1") (pinfunction "IN3_C1") (pintype "input"))
      (node (ref "B12") (pin "R2") (pinfunction "IN1_R2") (pintype "input"))
      (node (ref "D18") (pin "D2") (pinfunction "IN1_D2") (pintype "input"))
      (node (ref "E24") (pin "M1") (pinfunction "IN2_M1") (pintype "input"))
      (node (ref "E28") (pin "M1") (pinfunction "IN5A_M1") (pintype "input"))
      (node (ref "EF36") (pin "AS2") (pinfunction "AS2_AS2") (pintype "output"))
      (node (ref "H15") (pin "U2") (pinfunction "IN2_U2") (pintype "input"))
      (node (ref "H30") (pin "R2") (pinfunction "R2_R2") (pintype "input"))
      (node (ref "HJ29") (pin "AE2") (pinfunction "AE2_AE2") (pintype "input"))
    )
    (net (code "518") (name "MB05_") (class "Default")
      (node (ref "A10") (pin "L2") (pinfunction "2B_L2") (pintype "input"))
      (node (ref "B16") (pin "N2") (pinfunction "IN4_N2") (pintype "input"))
      (node (ref "B26") (pin "D1") (pinfunction "D1_D1") (pintype "input"))
      (node (ref "B36") (pin "D1") (pinfunction "D1_D1") (pintype "input"))
      (node (ref "C11") (pin "S1") (pinfunction "IN3_S1") (pintype "input"))
      (node (ref "E28") (pin "B1") (pinfunction "IN1B_B1") (pintype "input"))
      (node (ref "E40") (pin "A1") (pinfunction "P$2_A1") (pintype "bidirectional"))
      (node (ref "EF01") (pin "AF1") (pinfunction "AF1_AF1") (pintype "input"))
      (node (ref "EF02") (pin "AF2") (pinfunction "AF2_AF2") (pintype "input"))
      (node (ref "EF36") (pin "AS1") (pinfunction "AS1_AS1") (pintype "output"))
      (node (ref "F09") (pin "D1") (pinfunction "IN4_D1") (pintype "input"))
      (node (ref "F23") (pin "R2") (pinfunction "IN1_R2") (pintype "input"))
      (node (ref "H15") (pin "N2") (pinfunction "IN2_N2") (pintype "input"))
      (node (ref "HJ23") (pin "BK2") (pinfunction "BK2_BK2") (pintype "input"))
      (node (ref "HJ26") (pin "BE1") (pinfunction "BE1_BE1") (pintype "input"))
      (node (ref "HJ28") (pin "BD2") (pinfunction "BD2_BD2") (pintype "input"))
      (node (ref "J33") (pin "B1") (pinfunction "B1_B1") (pintype "input"))
    )
    (net (code "519") (name "MB06") (class "Default")
      (node (ref "A10") (pin "S2") (pinfunction "4A_S2") (pintype "input"))
      (node (ref "A12") (pin "E2") (pinfunction "IN2_E2") (pintype "input"))
      (node (ref "A15") (pin "T2") (pinfunction "IN1_T2") (pintype "input"))
      (node (ref "A18") (pin "E2") (pinfunction "IN2_E2") (pintype "input"))
      (node (ref "B13") (pin "A1") (pinfunction "IN1_A1") (pintype "input"))
      (node (ref "D18") (pin "H1") (pinfunction "IN3_H1") (pintype "input"))
      (node (ref "E30") (pin "U1") (pinfunction "IN1B_U1") (pintype "input"))
      (node (ref "EF02") (pin "AF1") (pinfunction "AF1_AF1") (pintype "input"))
      (node (ref "EF37") (pin "AT2") (pinfunction "AT2_AT2") (pintype "output"))
      (node (ref "F23") (pin "D1") (pinfunction "IN4_D1") (pintype "input"))
      (node (ref "F32") (pin "J2") (pinfunction "IN2_J2") (pintype "input"))
      (node (ref "H16") (pin "N2") (pinfunction "IN2_N2") (pintype "input"))
      (node (ref "HJ23") (pin "BM2") (pinfunction "BM2_BM2") (pintype "input"))
      (node (ref "J33") (pin "D1") (pinfunction "D1_D1") (pintype "input"))
    )
    (net (code "520") (name "MB06XMB09") (class "Default")
      (node (ref "A06") (pin "N2") (pinfunction "OUT_N2") (pintype "output"))
      (node (ref "A06") (pin "U2") (pinfunction "IN2_U2") (pintype "input"))
      (node (ref "B04") (pin "F1") (pinfunction "IN2_F1") (pintype "input"))
      (node (ref "B06") (pin "B1") (pinfunction "IN2_B1") (pintype "input"))
    )
    (net (code "521") (name "MB06_") (class "Default")
      (node (ref "A04") (pin "H2") (pinfunction "H2_H2") (pintype "input"))
      (node (ref "A10") (pin "M2") (pinfunction "4B_M2") (pintype "input"))
      (node (ref "B07") (pin "D2") (pinfunction "IN1_D2") (pintype "input"))
      (node (ref "B26") (pin "M2") (pinfunction "M2_M2") (pintype "input"))
      (node (ref "B36") (pin "M2") (pinfunction "M2_M2") (pintype "input"))
      (node (ref "C11") (pin "T2") (pinfunction "IN1_T2") (pintype "input"))
      (node (ref "E30") (pin "U2") (pinfunction "IN2B_U2") (pintype "input"))
      (node (ref "EF01") (pin "AH1") (pinfunction "AH1_AH1") (pintype "input"))
      (node (ref "EF37") (pin "AU2") (pinfunction "AU2_AU2") (pintype "output"))
      (node (ref "F09") (pin "D2") (pinfunction "IN5_D2") (pintype "input"))
      (node (ref "F23") (pin "S2") (pinfunction "IN2_S2") (pintype "input"))
      (node (ref "F40") (pin "R1") (pinfunction "P$2_R1") (pintype "bidirectional"))
      (node (ref "H16") (pin "H2") (pinfunction "IN2_H2") (pintype "input"))
      (node (ref "H30") (pin "P2") (pinfunction "P2_P2") (pintype "input"))
      (node (ref "HJ26") (pin "BF2") (pinfunction "BF2_BF2") (pintype "input"))
      (node (ref "HJ28") (pin "BE1") (pinfunction "BE1_BE1") (pintype "input"))
      (node (ref "HJ29") (pin "AD2") (pinfunction "AD2_AD2") (pintype "input"))
      (node (ref "J33") (pin "E2") (pinfunction "E2_E2") (pintype "input"))
    )
    (net (code "522") (name "MB07") (class "Default")
      (node (ref "A10") (pin "T2") (pinfunction "8A_T2") (pintype "input"))
      (node (ref "A12") (pin "M1") (pinfunction "IN2_M1") (pintype "input"))
      (node (ref "A18") (pin "M1") (pinfunction "IN2_M1") (pintype "input"))
      (node (ref "A20") (pin "R1") (pinfunction "IN2_R1") (pintype "input"))
      (node (ref "A20") (pin "R2") (pinfunction "IN3_R2") (pintype "input"))
      (node (ref "B06") (pin "A1") (pinfunction "IN1_A1") (pintype "input"))
      (node (ref "B13") (pin "D2") (pinfunction "IN1_D2") (pintype "input"))
      (node (ref "D18") (pin "K1") (pinfunction "IN1_K1") (pintype "input"))
      (node (ref "D21") (pin "H1") (pinfunction "IN2_H1") (pintype "input"))
      (node (ref "E24") (pin "U2") (pinfunction "IN2_U2") (pintype "input"))
      (node (ref "E28") (pin "D1") (pinfunction "IN1D_D1") (pintype "input"))
      (node (ref "EF01") (pin "AH2") (pinfunction "AH2_AH2") (pintype "input"))
      (node (ref "EF37") (pin "AS2") (pinfunction "AS2_AS2") (pintype "output"))
      (node (ref "F29") (pin "U2") (pinfunction "IN2_U2") (pintype "input"))
      (node (ref "H17") (pin "H2") (pinfunction "IN2_H2") (pintype "input"))
      (node (ref "H30") (pin "N2") (pinfunction "N2_N2") (pintype "input"))
      (node (ref "HJ23") (pin "BL2") (pinfunction "BL2_BL2") (pintype "input"))
      (node (ref "HJ28") (pin "BE2") (pinfunction "BE2_BE2") (pintype "input"))
      (node (ref "HJ29") (pin "AS2") (pinfunction "AS2_AS2") (pintype "input"))
      (node (ref "J33") (pin "A1") (pinfunction "A1_A1") (pintype "input"))
    )
    (net (code "523") (name "MB07_") (class "Default")
      (node (ref "A04") (pin "J2") (pinfunction "J2_J2") (pintype "input"))
      (node (ref "A06") (pin "P1") (pinfunction "IN1_P1") (pintype "input"))
      (node (ref "A10") (pin "N2") (pinfunction "8B_N2") (pintype "input"))
      (node (ref "A20") (pin "L1") (pinfunction "IN2_L1") (pintype "input"))
      (node (ref "B04") (pin "A1") (pinfunction "IN1_A1") (pintype "input"))
      (node (ref "B04") (pin "H1") (pinfunction "IN3_H1") (pintype "input"))
      (node (ref "B07") (pin "E2") (pinfunction "IN2_E2") (pintype "input"))
      (node (ref "B26") (pin "L1") (pinfunction "L1_L1") (pintype "input"))
      (node (ref "B36") (pin "L1") (pinfunction "L1_L1") (pintype "input"))
      (node (ref "C11") (pin "U2") (pinfunction "IN2_U2") (pintype "input"))
      (node (ref "C14") (pin "U2") (pinfunction "IN2_U2") (pintype "input"))
      (node (ref "E28") (pin "P1") (pinfunction "IN5C_P1") (pintype "input"))
      (node (ref "EF02") (pin "AH2") (pinfunction "AH2_AH2") (pintype "input"))
      (node (ref "EF37") (pin "AS1") (pinfunction "AS1_AS1") (pintype "output"))
      (node (ref "F23") (pin "T2") (pinfunction "IN3_T2") (pintype "input"))
      (node (ref "F40") (pin "P1") (pinfunction "P$2_P1") (pintype "bidirectional"))
      (node (ref "H16") (pin "U2") (pinfunction "IN2_U2") (pintype "input"))
      (node (ref "HJ23") (pin "BE2") (pinfunction "BE2_BE2") (pintype "input"))
      (node (ref "HJ26") (pin "BF1") (pinfunction "BF1_BF1") (pintype "input"))
      (node (ref "HJ29") (pin "BU1") (pinfunction "BU1_BU1") (pintype "input"))
    )
    (net (code "524") (name "MB08") (class "Default")
      (node (ref "A09") (pin "P2") (pinfunction "1A_P2") (pintype "input"))
      (node (ref "A12") (pin "R2") (pinfunction "IN2_R2") (pintype "input"))
      (node (ref "A18") (pin "R2") (pinfunction "IN2_R2") (pintype "input"))
      (node (ref "A20") (pin "M1") (pinfunction "IN3_M1") (pintype "input"))
      (node (ref "A20") (pin "P2") (pinfunction "IN2_P2") (pintype "input"))
      (node (ref "B04") (pin "E1") (pinfunction "IN1_E1") (pintype "input"))
      (node (ref "B06") (pin "M1") (pinfunction "IN2_M1") (pintype "input"))
      (node (ref "B13") (pin "F1") (pinfunction "IN1_F1") (pintype "input"))
      (node (ref "D24") (pin "C1") (pinfunction "D_C1") (pintype "input"))
      (node (ref "E28") (pin "R2") (pinfunction "IN4C_R2") (pintype "input"))
      (node (ref "EF01") (pin "AJ1") (pinfunction "AJ1_AJ1") (pintype "input"))
      (node (ref "EF38") (pin "AT2") (pinfunction "AT2_AT2") (pintype "output"))
      (node (ref "F26") (pin "D2") (pinfunction "IN1_D2") (pintype "input"))
      (node (ref "F26") (pin "E1") (pinfunction "IN1_E1") (pintype "input"))
      (node (ref "H17") (pin "U2") (pinfunction "IN2_U2") (pintype "input"))
      (node (ref "H30") (pin "M2") (pinfunction "M2_M2") (pintype "input"))
      (node (ref "HJ23") (pin "BN2") (pinfunction "BN2_BN2") (pintype "input"))
      (node (ref "HJ26") (pin "BH2") (pinfunction "BH2_BH2") (pintype "input"))
      (node (ref "HJ29") (pin "AK2") (pinfunction "AK2_AK2") (pintype "input"))
      (node (ref "J33") (pin "E1") (pinfunction "E1_E1") (pintype "input"))
    )
    (net (code "525") (name "MB08_") (class "Default")
      (node (ref "A04") (pin "K2") (pinfunction "K2_K2") (pintype "input"))
      (node (ref "A06") (pin "R1") (pinfunction "IN2_R1") (pintype "input"))
      (node (ref "A09") (pin "K2") (pinfunction "1B_K2") (pintype "input"))
      (node (ref "A20") (pin "S1") (pinfunction "IN3_S1") (pintype "input"))
      (node (ref "B04") (pin "B1") (pinfunction "IN2_B1") (pintype "input"))
      (node (ref "B07") (pin "F2") (pinfunction "IN3_F2") (pintype "input"))
      (node (ref "B27") (pin "D2") (pinfunction "D2_D2") (pintype "input"))
      (node (ref "B37") (pin "D2") (pinfunction "D2_D2") (pintype "input"))
      (node (ref "C11") (pin "V2") (pinfunction "IN3_V2") (pintype "input"))
      (node (ref "C15") (pin "U2") (pinfunction "IN2_U2") (pintype "input"))
      (node (ref "E28") (pin "M2") (pinfunction "IN3B_M2") (pintype "input"))
      (node (ref "EF02") (pin "AJ2") (pinfunction "AJ2_AJ2") (pintype "input"))
      (node (ref "EF38") (pin "AU2") (pinfunction "AU2_AU2") (pintype "output"))
      (node (ref "F23") (pin "U2") (pinfunction "IN4_U2") (pintype "input"))
      (node (ref "F26") (pin "K1") (pinfunction "IN1_K1") (pintype "input"))
      (node (ref "F40") (pin "F2") (pinfunction "P$2_F2") (pintype "bidirectional"))
      (node (ref "H17") (pin "N2") (pinfunction "IN2_N2") (pintype "input"))
      (node (ref "HJ23") (pin "BJ2") (pinfunction "BJ2_BJ2") (pintype "input"))
      (node (ref "HJ28") (pin "BF1") (pinfunction "BF1_BF1") (pintype "input"))
      (node (ref "HJ29") (pin "BV1") (pinfunction "BV1_BV1") (pintype "input"))
    )
    (net (code "526") (name "MB09") (class "Default")
      (node (ref "A09") (pin "R2") (pinfunction "2A_R2") (pintype "input"))
      (node (ref "A14") (pin "D2") (pinfunction "IN1_D2") (pintype "input"))
      (node (ref "B13") (pin "K2") (pinfunction "IN1_K2") (pintype "input"))
      (node (ref "C11") (pin "L1") (pinfunction "IN2_L1") (pintype "input"))
      (node (ref "D13") (pin "E1") (pinfunction "IN2_E1") (pintype "input"))
      (node (ref "D24") (pin "E2") (pinfunction "D_E2") (pintype "input"))
      (node (ref "EF38") (pin "AS2") (pinfunction "AS2_AS2") (pintype "output"))
      (node (ref "F09") (pin "E2") (pinfunction "IN6_E2") (pintype "input"))
      (node (ref "F20") (pin "J2") (pinfunction "IN2_J2") (pintype "input"))
      (node (ref "F26") (pin "A1") (pinfunction "IN1_A1") (pintype "input"))
      (node (ref "F26") (pin "J2") (pinfunction "IN1_J2") (pintype "input"))
      (node (ref "F28") (pin "R2") (pinfunction "IN3_R2") (pintype "input"))
      (node (ref "H18") (pin "H2") (pinfunction "IN2_H2") (pintype "input"))
      (node (ref "H30") (pin "U2") (pinfunction "U2_U2") (pintype "input"))
    )
    (net (code "527") (name "MB09_") (class "Default")
      (node (ref "A05") (pin "B1") (pinfunction "IN2_B1") (pintype "input"))
      (node (ref "A09") (pin "L2") (pinfunction "2B_L2") (pintype "input"))
      (node (ref "B27") (pin "D1") (pinfunction "D1_D1") (pintype "input"))
      (node (ref "B37") (pin "D1") (pinfunction "D1_D1") (pintype "input"))
      (node (ref "C16") (pin "U2") (pinfunction "IN2_U2") (pintype "input"))
      (node (ref "D13") (pin "P1") (pinfunction "IN1_P1") (pintype "input"))
      (node (ref "EF38") (pin "AS1") (pinfunction "AS1_AS1") (pintype "output"))
      (node (ref "F26") (pin "M1") (pinfunction "IN3_M1") (pintype "input"))
      (node (ref "F40") (pin "D2") (pinfunction "P$2_D2") (pintype "bidirectional"))
      (node (ref "H30") (pin "N1") (pinfunction "N1_N1") (pintype "input"))
      (node (ref "HJ23") (pin "AK2") (pinfunction "AK2_AK2") (pintype "input"))
    )
    (net (code "528") (name "MB10") (class "Default")
      (node (ref "A09") (pin "S2") (pinfunction "4A_S2") (pintype "input"))
      (node (ref "A12") (pin "B1") (pinfunction "IN2_B1") (pintype "input"))
      (node (ref "A15") (pin "P2") (pinfunction "IN1_P2") (pintype "input"))
      (node (ref "B13") (pin "M1") (pinfunction "IN1_M1") (pintype "input"))
      (node (ref "D10") (pin "D1") (pinfunction "IN4_D1") (pintype "input"))
      (node (ref "D10") (pin "F2") (pinfunction "IN3_F2") (pintype "input"))
      (node (ref "D24") (pin "J1") (pinfunction "D_J1") (pintype "input"))
      (node (ref "E13") (pin "A1") (pinfunction "IN1A_A1") (pintype "input"))
      (node (ref "E14") (pin "H1") (pinfunction "IN3_H1") (pintype "input"))
      (node (ref "EF39") (pin "AT2") (pinfunction "AT2_AT2") (pintype "output"))
      (node (ref "F20") (pin "J1") (pinfunction "IN2_J1") (pintype "input"))
      (node (ref "F26") (pin "C1") (pinfunction "IN3_C1") (pintype "input"))
      (node (ref "F26") (pin "F2") (pinfunction "IN3_F2") (pintype "input"))
      (node (ref "H18") (pin "N2") (pinfunction "IN2_N2") (pintype "input"))
      (node (ref "H30") (pin "L1") (pinfunction "L1_L1") (pintype "input"))
      (node (ref "HJ23") (pin "AN1") (pinfunction "AN1_AN1") (pintype "input"))
      (node (ref "HJ31") (pin "BJ1") (pinfunction "BJ1_BJ1") (pintype "input"))
    )
    (net (code "529") (name "MB10_") (class "Default")
      (node (ref "A05") (pin "A1") (pinfunction "IN1_A1") (pintype "input"))
      (node (ref "A09") (pin "M2") (pinfunction "4B_M2") (pintype "input"))
      (node (ref "A15") (pin "L1") (pinfunction "IN1_L1") (pintype "input"))
      (node (ref "B27") (pin "M2") (pinfunction "M2_M2") (pintype "input"))
      (node (ref "B37") (pin "M2") (pinfunction "M2_M2") (pintype "input"))
      (node (ref "C17") (pin "U2") (pinfunction "IN2_U2") (pintype "input"))
      (node (ref "D13") (pin "R1") (pinfunction "IN2_R1") (pintype "input"))
      (node (ref "EF39") (pin "AU2") (pinfunction "AU2_AU2") (pintype "output"))
      (node (ref "F21") (pin "L2") (pinfunction "IN1_L2") (pintype "input"))
      (node (ref "F26") (pin "H1") (pinfunction "IN3_H1") (pintype "input"))
      (node (ref "F26") (pin "L2") (pinfunction "IN3_L2") (pintype "input"))
      (node (ref "F40") (pin "K1") (pinfunction "P$2_K1") (pintype "bidirectional"))
      (node (ref "HJ31") (pin "BP1") (pinfunction "BP1_BP1") (pintype "input"))
    )
    (net (code "530") (name "MB11") (class "Default")
      (node (ref "A09") (pin "T2") (pinfunction "8A_T2") (pintype "input"))
      (node (ref "A11") (pin "B1") (pinfunction "IN2_B1") (pintype "input"))
      (node (ref "B13") (pin "R2") (pinfunction "IN1_R2") (pintype "input"))
      (node (ref "D10") (pin "R1") (pinfunction "IN4_R1") (pintype "input"))
      (node (ref "D10") (pin "U2") (pinfunction "IN4_U2") (pintype "input"))
      (node (ref "D18") (pin "E1") (pinfunction "IN1_E1") (pintype "input"))
      (node (ref "D18") (pin "F2") (pinfunction "IN3_F2") (pintype "input"))
      (node (ref "D20") (pin "R1") (pinfunction "IN4_R1") (pintype "input"))
      (node (ref "D21") (pin "F1") (pinfunction "IN1_F1") (pintype "input"))
      (node (ref "E27") (pin "J1") (pinfunction "IN3B_J1") (pintype "input"))
      (node (ref "EF39") (pin "AS2") (pinfunction "AS2_AS2") (pintype "output"))
      (node (ref "F20") (pin "E2") (pinfunction "IN2_E2") (pintype "input"))
      (node (ref "H18") (pin "U2") (pinfunction "IN2_U2") (pintype "input"))
      (node (ref "H30") (pin "A1") (pinfunction "A1_A1") (pintype "input"))
      (node (ref "HJ23") (pin "AP1") (pinfunction "AP1_AP1") (pintype "input"))
    )
    (net (code "531") (name "MB11_") (class "Default")
      (node (ref "A09") (pin "N2") (pinfunction "8B_N2") (pintype "input"))
      (node (ref "A13") (pin "A1") (pinfunction "IN1_A1") (pintype "input"))
      (node (ref "B04") (pin "D2") (pinfunction "IN1_D2") (pintype "input"))
      (node (ref "B27") (pin "L1") (pinfunction "L1_L1") (pintype "input"))
      (node (ref "B37") (pin "L1") (pinfunction "L1_L1") (pintype "input"))
      (node (ref "C18") (pin "R1") (pinfunction "IN2_R1") (pintype "input"))
      (node (ref "D09") (pin "F2") (pinfunction "IN3_F2") (pintype "input"))
      (node (ref "D10") (pin "H2") (pinfunction "IN4_H2") (pintype "input"))
      (node (ref "E13") (pin "B1") (pinfunction "IN1B_B1") (pintype "input"))
      (node (ref "E25") (pin "N2") (pinfunction "IN1_N2") (pintype "input"))
      (node (ref "E28") (pin "S2") (pinfunction "IN4D_S2") (pintype "input"))
      (node (ref "E33") (pin "P1") (pinfunction "D_P1") (pintype "input"))
      (node (ref "EF39") (pin "AS1") (pinfunction "AS1_AS1") (pintype "output"))
      (node (ref "F21") (pin "M2") (pinfunction "IN2_M2") (pintype "input"))
      (node (ref "F28") (pin "P2") (pinfunction "IN2_P2") (pintype "input"))
      (node (ref "F40") (pin "A1") (pinfunction "P$2_A1") (pintype "bidirectional"))
    )
    (net (code "532") (name "MB_LOAD") (class "Default")
      (node (ref "E32") (pin "L1") (pinfunction "OUT_L1") (pintype "open_collector"))
      (node (ref "EF34") (pin "AR1") (pinfunction "AR1_AR1") (pintype "input"))
      (node (ref "EF35") (pin "AR1") (pinfunction "AR1_AR1") (pintype "input"))
      (node (ref "EF36") (pin "AR1") (pinfunction "AR1_AR1") (pintype "input"))
      (node (ref "EF37") (pin "AR1") (pinfunction "AR1_AR1") (pintype "input"))
      (node (ref "EF38") (pin "AR1") (pinfunction "AR1_AR1") (pintype "input"))
      (node (ref "EF39") (pin "AR1") (pinfunction "AR1_AR1") (pintype "input"))
    )
    (net (code "533") (name "MB_PARITY_ODD") (class "Default")
      (node (ref "A10") (pin "K1") (pinfunction "ODD_K1") (pintype "output"))
      (node (ref "A37") (pin "D2") (pinfunction "D2_D2") (pintype "input"))
      (node (ref "A37") (pin "M2") (pinfunction "M2_M2") (pintype "input"))
      (node (ref "H05") (pin "T2") (pinfunction "P$2_T2") (pintype "bidirectional"))
    )
    (net (code "534") (name "MB_TO_IB") (class "Default")
      (node (ref "A15") (pin "S1") (pinfunction "OUT_S1") (pintype "output"))
      (node (ref "A18") (pin "D2") (pinfunction "IN1_D2") (pintype "input"))
      (node (ref "A18") (pin "L1") (pinfunction "IN1_L1") (pintype "input"))
      (node (ref "A18") (pin "P2") (pinfunction "IN1_P2") (pintype "input"))
    )
    (net (code "535") (name "MB_TO_SC_ENABLE") (class "Default")
      (node (ref "C14") (pin "T2") (pinfunction "IN1_T2") (pintype "input"))
      (node (ref "C15") (pin "T2") (pinfunction "IN1_T2") (pintype "input"))
      (node (ref "C16") (pin "T2") (pinfunction "IN1_T2") (pintype "input"))
      (node (ref "C17") (pin "T2") (pinfunction "IN1_T2") (pintype "input"))
      (node (ref "C18") (pin "P1") (pinfunction "IN1_P1") (pintype "input"))
      (node (ref "D15") (pin "N2") (pinfunction "OUT_N2") (pintype "output"))
    )
    (net (code "536") (name "MCBMB00_") (class "Default")
      (node (ref "B12") (pin "E1") (pinfunction "OUT_E1") (pintype "open_collector"))
      (node (ref "H02") (pin "S2") (pinfunction "P$2_S2") (pintype "bidirectional"))
    )
    (net (code "537") (name "MCBMB01_") (class "Default")
      (node (ref "B12") (pin "J2") (pinfunction "OUT_J2") (pintype "open_collector"))
      (node (ref "H02") (pin "T2") (pinfunction "P$2_T2") (pintype "bidirectional"))
    )
    (net (code "538") (name "MCBMB02_") (class "Default")
      (node (ref "B12") (pin "L1") (pinfunction "OUT_L1") (pintype "open_collector"))
      (node (ref "H02") (pin "V2") (pinfunction "P$2_V2") (pintype "bidirectional"))
    )
    (net (code "539") (name "MCBMB03_") (class "Default")
      (node (ref "B12") (pin "P2") (pinfunction "OUT_P2") (pintype "open_collector"))
      (node (ref "H03") (pin "D2") (pinfunction "P$2_D2") (pintype "bidirectional"))
    )
    (net (code "540") (name "MCBMB04_") (class "Default")
      (node (ref "B12") (pin "S1") (pinfunction "OUT_S1") (pintype "open_collector"))
      (node (ref "H03") (pin "E2") (pinfunction "P$2_E2") (pintype "bidirectional"))
    )
    (net (code "541") (name "MCBMB05_") (class "Default")
      (node (ref "B12") (pin "V2") (pinfunction "OUT_V2") (pintype "open_collector"))
      (node (ref "H03") (pin "H2") (pinfunction "P$2_H2") (pintype "bidirectional"))
    )
    (net (code "542") (name "MCBMB06_") (class "Default")
      (node (ref "B13") (pin "E1") (pinfunction "OUT_E1") (pintype "open_collector"))
      (node (ref "H03") (pin "K2") (pinfunction "P$2_K2") (pintype "bidirectional"))
    )
    (net (code "543") (name "MCBMB07_") (class "Default")
      (node (ref "B13") (pin "J2") (pinfunction "OUT_J2") (pintype "open_collector"))
      (node (ref "H03") (pin "M2") (pinfunction "P$2_M2") (pintype "bidirectional"))
    )
    (net (code "544") (name "MCBMB08_") (class "Default")
      (node (ref "B13") (pin "L1") (pinfunction "OUT_L1") (pintype "open_collector"))
      (node (ref "H03") (pin "P2") (pinfunction "P$2_P2") (pintype "bidirectional"))
    )
    (net (code "545") (name "MCBMB09_") (class "Default")
      (node (ref "B13") (pin "P2") (pinfunction "OUT_P2") (pintype "open_collector"))
      (node (ref "H03") (pin "S2") (pinfunction "P$2_S2") (pintype "bidirectional"))
    )
    (net (code "546") (name "MCBMB10_") (class "Default")
      (node (ref "B13") (pin "S1") (pinfunction "OUT_S1") (pintype "open_collector"))
      (node (ref "H03") (pin "T2") (pinfunction "P$2_T2") (pintype "bidirectional"))
    )
    (net (code "547") (name "MCBMB11_") (class "Default")
      (node (ref "B13") (pin "V2") (pinfunction "OUT_V2") (pintype "open_collector"))
      (node (ref "H03") (pin "V2") (pinfunction "P$2_V2") (pintype "bidirectional"))
    )
    (net (code "548") (name "ME05_") (class "Default")
      (node (ref "A05") (pin "K2") (pinfunction "OUT_K2") (pintype "output"))
      (node (ref "J13") (pin "U2") (pinfunction "IN4_U2") (pintype "input"))
    )
    (net (code "549") (name "ME06_") (class "Default")
      (node (ref "A13") (pin "N1") (pinfunction "OUT_N1") (pintype "output"))
      (node (ref "J14") (pin "D1") (pinfunction "IN4_D1") (pintype "input"))
    )
    (net (code "550") (name "ME07_") (class "Default")
      (node (ref "A13") (pin "S1") (pinfunction "OUT_S1") (pintype "output"))
      (node (ref "J14") (pin "H2") (pinfunction "IN4_H2") (pintype "input"))
    )
    (net (code "551") (name "ME08_") (class "Default")
      (node (ref "A13") (pin "V2") (pinfunction "OUT_V2") (pintype "output"))
      (node (ref "J14") (pin "K1") (pinfunction "IN4_K1") (pintype "input"))
    )
    (net (code "552") (name "ME09_") (class "Default")
      (node (ref "A13") (pin "K2") (pinfunction "OUT_K2") (pintype "output"))
      (node (ref "J14") (pin "N2") (pinfunction "IN4_N2") (pintype "input"))
    )
    (net (code "553") (name "ME10_") (class "Default")
      (node (ref "A13") (pin "N2") (pinfunction "OUT_N2") (pintype "output"))
      (node (ref "J14") (pin "R1") (pinfunction "IN4_R1") (pintype "input"))
    )
    (net (code "554") (name "ME11_") (class "Default")
      (node (ref "A13") (pin "S2") (pinfunction "OUT_S2") (pintype "output"))
      (node (ref "J14") (pin "U2") (pinfunction "IN4_U2") (pintype "input"))
    )
    (net (code "555") (name "MEM00") (class "Default")
      (node (ref "A07") (pin "E1") (pinfunction "1A_E1") (pintype "input"))
      (node (ref "A31") (pin "A1") (pinfunction "A1_A1") (pintype "open_collector"))
      (node (ref "B08") (pin "H1") (pinfunction "IN1_H1") (pintype "input"))
      (node (ref "C09") (pin "A1") (pinfunction "IN1_A1") (pintype "input"))
      (node (ref "EF34") (pin "BR1") (pinfunction "BR1_BR1") (pintype "input"))
      (node (ref "F22") (pin "B1") (pinfunction "IN2_B1") (pintype "input"))
      (node (ref "H04") (pin "E2") (pinfunction "P$2_E2") (pintype "bidirectional"))
    )
    (net (code "556") (name "MEM01") (class "Default")
      (node (ref "A07") (pin "F1") (pinfunction "2A_F1") (pintype "input"))
      (node (ref "A31") (pin "U2") (pinfunction "U2_U2") (pintype "open_collector"))
      (node (ref "B08") (pin "D2") (pinfunction "IN1_D2") (pintype "input"))
      (node (ref "E20") (pin "E2") (pinfunction "D_E2") (pintype "input"))
      (node (ref "EF34") (pin "BV2") (pinfunction "BV2_BV2") (pintype "input"))
      (node (ref "H04") (pin "H2") (pinfunction "P$2_H2") (pintype "bidirectional"))
    )
    (net (code "557") (name "MEM02") (class "Default")
      (node (ref "A07") (pin "H1") (pinfunction "4A_H1") (pintype "input"))
      (node (ref "A32") (pin "A1") (pinfunction "A1_A1") (pintype "open_collector"))
      (node (ref "B08") (pin "D1") (pinfunction "IN1_D1") (pintype "input"))
      (node (ref "E20") (pin "J1") (pinfunction "D_J1") (pintype "input"))
      (node (ref "EF35") (pin "BR1") (pinfunction "BR1_BR1") (pintype "input"))
      (node (ref "H04") (pin "K2") (pinfunction "P$2_K2") (pintype "bidirectional"))
    )
    (net (code "558") (name "MEM03") (class "Default")
      (node (ref "A07") (pin "J1") (pinfunction "8A_J1") (pintype "input"))
      (node (ref "A32") (pin "U2") (pinfunction "U2_U2") (pintype "open_collector"))
      (node (ref "B08") (pin "A1") (pinfunction "IN1_A1") (pintype "input"))
      (node (ref "EF35") (pin "BV2") (pinfunction "BV2_BV2") (pintype "input"))
      (node (ref "H04") (pin "M2") (pinfunction "P$2_M2") (pintype "bidirectional"))
    )
    (net (code "559") (name "MEM04") (class "Default")
      (node (ref "A08") (pin "P2") (pinfunction "1A_P2") (pintype "input"))
      (node (ref "A33") (pin "A1") (pinfunction "A1_A1") (pintype "open_collector"))
      (node (ref "B08") (pin "P1") (pinfunction "IN1_P1") (pintype "input"))
      (node (ref "EF36") (pin "BR1") (pinfunction "BR1_BR1") (pintype "input"))
      (node (ref "H04") (pin "P2") (pinfunction "P$2_P2") (pintype "bidirectional"))
    )
    (net (code "560") (name "MEM05") (class "Default")
      (node (ref "A08") (pin "R2") (pinfunction "2A_R2") (pintype "input"))
      (node (ref "A33") (pin "U2") (pinfunction "U2_U2") (pintype "open_collector"))
      (node (ref "B08") (pin "L2") (pinfunction "IN1_L2") (pintype "input"))
      (node (ref "EF36") (pin "BV2") (pinfunction "BV2_BV2") (pintype "input"))
      (node (ref "H04") (pin "S2") (pinfunction "P$2_S2") (pintype "bidirectional"))
    )
    (net (code "561") (name "MEM06") (class "Default")
      (node (ref "A08") (pin "S2") (pinfunction "4A_S2") (pintype "input"))
      (node (ref "B08") (pin "L1") (pinfunction "IN1_L1") (pintype "input"))
      (node (ref "B31") (pin "A1") (pinfunction "A1_A1") (pintype "open_collector"))
      (node (ref "EF37") (pin "BR1") (pinfunction "BR1_BR1") (pintype "input"))
      (node (ref "H04") (pin "T2") (pinfunction "P$2_T2") (pintype "bidirectional"))
    )
    (net (code "562") (name "MEM07") (class "Default")
      (node (ref "A08") (pin "T2") (pinfunction "8A_T2") (pintype "input"))
      (node (ref "B08") (pin "H2") (pinfunction "IN1_H2") (pintype "input"))
      (node (ref "B31") (pin "U2") (pinfunction "U2_U2") (pintype "open_collector"))
      (node (ref "EF37") (pin "BV2") (pinfunction "BV2_BV2") (pintype "input"))
      (node (ref "H04") (pin "V2") (pinfunction "P$2_V2") (pintype "bidirectional"))
    )
    (net (code "563") (name "MEM08") (class "Default")
      (node (ref "A07") (pin "P2") (pinfunction "1A_P2") (pintype "input"))
      (node (ref "B09") (pin "D1") (pinfunction "IN1_D1") (pintype "input"))
      (node (ref "B32") (pin "A1") (pinfunction "A1_A1") (pintype "open_collector"))
      (node (ref "EF38") (pin "BR1") (pinfunction "BR1_BR1") (pintype "input"))
      (node (ref "H05") (pin "D2") (pinfunction "P$2_D2") (pintype "bidirectional"))
    )
    (net (code "564") (name "MEM09") (class "Default")
      (node (ref "A07") (pin "R2") (pinfunction "2A_R2") (pintype "input"))
      (node (ref "B09") (pin "A1") (pinfunction "IN1_A1") (pintype "input"))
      (node (ref "B32") (pin "U2") (pinfunction "U2_U2") (pintype "open_collector"))
      (node (ref "D09") (pin "C1") (pinfunction "IN3_C1") (pintype "input"))
      (node (ref "EF38") (pin "BV2") (pinfunction "BV2_BV2") (pintype "input"))
      (node (ref "H05") (pin "E2") (pinfunction "P$2_E2") (pintype "bidirectional"))
    )
    (net (code "565") (name "MEM10") (class "Default")
      (node (ref "A07") (pin "S2") (pinfunction "4A_S2") (pintype "input"))
      (node (ref "B08") (pin "T2") (pinfunction "IN1_T2") (pintype "input"))
      (node (ref "B33") (pin "A1") (pinfunction "A1_A1") (pintype "open_collector"))
      (node (ref "EF39") (pin "BR1") (pinfunction "BR1_BR1") (pintype "input"))
      (node (ref "H05") (pin "H2") (pinfunction "P$2_H2") (pintype "bidirectional"))
    )
    (net (code "566") (name "MEM11") (class "Default")
      (node (ref "A07") (pin "T2") (pinfunction "8A_T2") (pintype "input"))
      (node (ref "B08") (pin "P2") (pinfunction "IN1_P2") (pintype "input"))
      (node (ref "B33") (pin "U2") (pinfunction "U2_U2") (pintype "open_collector"))
      (node (ref "EF39") (pin "BV2") (pinfunction "BV2_BV2") (pintype "input"))
      (node (ref "H05") (pin "K2") (pinfunction "P$2_K2") (pintype "bidirectional"))
    )
    (net (code "567") (name "MEMORY_INCREMENT") (class "Default")
      (node (ref "E11") (pin "U2") (pinfunction "IN2_U2") (pintype "input"))
      (node (ref "E27") (pin "R2") (pinfunction "IN4C_R2") (pintype "input"))
      (node (ref "J20") (pin "E1") (pinfunction "OUT_E1") (pintype "output"))
    )
    (net (code "568") (name "MEM_BEGIN_") (class "Default")
      (node (ref "A30") (pin "B1") (pinfunction "B1_B1") (pintype "input"))
      (node (ref "A31") (pin "B1") (pinfunction "B1_B1") (pintype "input"))
      (node (ref "A32") (pin "B1") (pinfunction "B1_B1") (pintype "input"))
      (node (ref "A33") (pin "B1") (pinfunction "B1_B1") (pintype "input"))
      (node (ref "B22") (pin "K1") (pinfunction "S_K1") (pintype "input"))
      (node (ref "B30") (pin "S1") (pinfunction "OUT_S1") (pintype "open_collector"))
      (node (ref "B31") (pin "B1") (pinfunction "B1_B1") (pintype "input"))
      (node (ref "B32") (pin "B1") (pinfunction "B1_B1") (pintype "input"))
      (node (ref "B33") (pin "B1") (pinfunction "B1_B1") (pintype "input"))
    )
    (net (code "569") (name "MEM_DONE_") (class "Default")
      (node (ref "B10") (pin "D2") (pinfunction "D2_D2") (pintype "open_collector"))
      (node (ref "B23") (pin "V2") (pinfunction "OUT_V2") (pintype "open_collector"))
      (node (ref "C07") (pin "T2") (pinfunction "IN3_T2") (pintype "input"))
      (node (ref "E18") (pin "F2") (pinfunction "S_F2") (pintype "input"))
      (node (ref "E33") (pin "F2") (pinfunction "S_F2") (pintype "input"))
      (node (ref "H05") (pin "S2") (pinfunction "P$2_S2") (pintype "bidirectional"))
    )
    (net (code "570") (name "MEM_ENABLE0_4") (class "Default")
      (node (ref "EF34") (pin "BU2") (pinfunction "BU2_BU2") (pintype "input"))
      (node (ref "EF34") (pin "BV1") (pinfunction "BV1_BV1") (pintype "input"))
      (node (ref "EF35") (pin "BU2") (pinfunction "BU2_BU2") (pintype "input"))
      (node (ref "EF35") (pin "BV1") (pinfunction "BV1_BV1") (pintype "input"))
      (node (ref "EF36") (pin "BU2") (pinfunction "BU2_BU2") (pintype "input"))
      (node (ref "F27") (pin "R1") (pinfunction "IN4_R1") (pintype "input"))
      (node (ref "F29") (pin "A1") (pinfunction "IN1_A1") (pintype "input"))
      (node (ref "F31") (pin "E1") (pinfunction "OUT_E1") (pintype "open_collector"))
    )
    (net (code "571") (name "MEM_ENABLE0_4_") (class "Default")
      (node (ref "F28") (pin "E2") (pinfunction "IN2_E2") (pintype "input"))
      (node (ref "F29") (pin "C1") (pinfunction "OUT_C1") (pintype "output"))
      (node (ref "F31") (pin "F2") (pinfunction "IN3_F2") (pintype "input"))
    )
    (net (code "572") (name "MEM_ENABLE5_8") (class "Default")
      (node (ref "E09") (pin "H2") (pinfunction "IN1_H2") (pintype "input"))
      (node (ref "EF36") (pin "BV1") (pinfunction "BV1_BV1") (pintype "input"))
      (node (ref "EF37") (pin "BU2") (pinfunction "BU2_BU2") (pintype "input"))
      (node (ref "EF37") (pin "BV1") (pinfunction "BV1_BV1") (pintype "input"))
      (node (ref "EF38") (pin "BU2") (pinfunction "BU2_BU2") (pintype "input"))
      (node (ref "F28") (pin "D2") (pinfunction "IN1_D2") (pintype "input"))
      (node (ref "F31") (pin "J2") (pinfunction "OUT_J2") (pintype "open_collector"))
    )
    (net (code "573") (name "MEM_ENABLE9_11") (class "Default")
      (node (ref "EF38") (pin "BV1") (pinfunction "BV1_BV1") (pintype "input"))
      (node (ref "EF39") (pin "BU2") (pinfunction "BU2_BU2") (pintype "input"))
      (node (ref "EF39") (pin "BV1") (pinfunction "BV1_BV1") (pintype "input"))
      (node (ref "F11") (pin "P2") (pinfunction "OUT_P2") (pintype "output"))
    )
    (net (code "574") (name "MEM_ENABLE_") (class "Default")
      (node (ref "B22") (pin "F1") (pinfunction "0_F1") (pintype "output"))
      (node (ref "B30") (pin "A1") (pinfunction "IN1_A1") (pintype "input"))
    )
    (net (code "575") (name "MEM_EXT") (class "Default")
      (node (ref "A11") (pin "A1") (pinfunction "IN1_A1") (pintype "input"))
      (node (ref "A13") (pin "E2") (pinfunction "IN2_E2") (pintype "input"))
      (node (ref "A14") (pin "E2") (pinfunction "IN2_E2") (pintype "input"))
      (node (ref "A14") (pin "K1") (pinfunction "OUT_K1") (pintype "output"))
      (node (ref "A15") (pin "R2") (pinfunction "IN2_R2") (pintype "input"))
    )
    (net (code "576") (name "MEM_EXT_") (class "Default")
      (node (ref "A14") (pin "F1") (pinfunction "OUT_F1") (pintype "output"))
      (node (ref "A14") (pin "H1") (pinfunction "IN1_H1") (pintype "input"))
      (node (ref "F19") (pin "B1") (pinfunction "IN2_B1") (pintype "input"))
    )
    (net (code "577") (name "MEM_EXT_AC_LOAD_ENABLE_") (class "Default")
      (node (ref "A14") (pin "S2") (pinfunction "OUT_S2") (pintype "output"))
      (node (ref "E32") (pin "N2") (pinfunction "IN4_N2") (pintype "input"))
    )
    (net (code "578") (name "MEM_EXT_IO_ENABLE_") (class "Default")
      (node (ref "C12") (pin "J2") (pinfunction "OUT_J2") (pintype "open_collector"))
      (node (ref "F30") (pin "E2") (pinfunction "IN2_E2") (pintype "input"))
    )
    (net (code "579") (name "MEM_FINISH") (class "Default")
      (node (ref "A24") (pin "F1") (pinfunction "OUT_F1") (pintype "output"))
      (node (ref "B22") (pin "L2") (pinfunction "C_L2") (pintype "input"))
      (node (ref "B22") (pin "N1") (pinfunction "C_N1") (pintype "input"))
      (node (ref "B23") (pin "U2") (pinfunction "IN_U2") (pintype "input"))
    )
    (net (code "580") (name "MEM_IDLE") (class "Default")
      (node (ref "E14") (pin "A1") (pinfunction "IN1_A1") (pintype "input"))
      (node (ref "E18") (pin "H2") (pinfunction "1_H2") (pintype "output"))
    )
    (net (code "581") (name "MEM_INH9_11_") (class "Default")
      (node (ref "C09") (pin "K2") (pinfunction "OUT_K2") (pintype "output"))
      (node (ref "D10") (pin "J1") (pinfunction "IN3_J1") (pintype "input"))
      (node (ref "E09") (pin "J2") (pinfunction "IN2_J2") (pintype "input"))
    )
    (net (code "582") (name "MEM_P") (class "Default")
      (node (ref "A08") (pin "J1") (pinfunction "8A_J1") (pintype "input"))
      (node (ref "A30") (pin "A1") (pinfunction "A1_A1") (pintype "open_collector"))
      (node (ref "B08") (pin "V1") (pinfunction "P$1_V1") (pintype "passive"))
      (node (ref "B09") (pin "E2") (pinfunction "IN2_E2") (pintype "input"))
      (node (ref "H04") (pin "D2") (pinfunction "P$2_D2") (pintype "bidirectional"))
    )
    (net (code "583") (name "MEM_PARITY_EVEN_") (class "Default")
      (node (ref "A08") (pin "L1") (pinfunction "EVEN_L1") (pintype "output"))
      (node (ref "B09") (pin "U2") (pinfunction "IN2_U2") (pintype "input"))
    )
    (net (code "584") (name "MEM_START") (class "Default")
      (node (ref "B21") (pin "E1") (pinfunction "IN2_E1") (pintype "input"))
      (node (ref "B22") (pin "B1") (pinfunction "C_B1") (pintype "input"))
      (node (ref "E15") (pin "F1") (pinfunction "OUT_F1") (pintype "output"))
    )
    (net (code "585") (name "MEM_TO_LSR_") (class "Default")
      (node (ref "C08") (pin "P2") (pinfunction "IN2_P2") (pintype "input"))
      (node (ref "D07") (pin "K1") (pinfunction "OUT_K1") (pintype "output"))
    )
    (net (code "586") (name "MFTP0") (class "Default")
      (node (ref "EF10") (pin "AT2") (pinfunction "CT2_AT2") (pintype "output"))
      (node (ref "F20") (pin "T2") (pinfunction "IN1_T2") (pintype "input"))
      (node (ref "F30") (pin "U2") (pinfunction "IN4_U2") (pintype "input"))
    )
    (net (code "587") (name "MFTP1") (class "Default")
      (node (ref "A19") (pin "J2") (pinfunction "IN2_J2") (pintype "input"))
      (node (ref "E12") (pin "M2") (pinfunction "IN2_M2") (pintype "input"))
      (node (ref "EF10") (pin "AE2") (pinfunction "CE2_AE2") (pintype "output"))
      (node (ref "F32") (pin "D1") (pinfunction "IN1_D1") (pintype "input"))
    )
    (net (code "588") (name "MFTP2") (class "Default")
      (node (ref "E15") (pin "A1") (pinfunction "IN1_A1") (pintype "input"))
      (node (ref "E15") (pin "H1") (pinfunction "IN1_H1") (pintype "input"))
      (node (ref "E26") (pin "J2") (pinfunction "IN2A_J2") (pintype "input"))
      (node (ref "E26") (pin "K1") (pinfunction "IN4A_K1") (pintype "input"))
      (node (ref "E26") (pin "V1") (pinfunction "IN2A_V1") (pintype "input"))
      (node (ref "EF10") (pin "BD2") (pinfunction "DD2_BD2") (pintype "output"))
      (node (ref "F22") (pin "D2") (pinfunction "IN1_D2") (pintype "input"))
    )
    (net (code "589") (name "MFTS0") (class "Default")
      (node (ref "E13") (pin "J1") (pinfunction "IN3B_J1") (pintype "input"))
      (node (ref "E14") (pin "T2") (pinfunction "IN1_T2") (pintype "input"))
      (node (ref "EF10") (pin "AM2") (pinfunction "CM2_AM2") (pintype "output"))
      (node (ref "F29") (pin "R2") (pinfunction "IN2_R2") (pintype "input"))
    )
    (net (code "590") (name "MFTS1") (class "Default")
      (node (ref "E14") (pin "E2") (pinfunction "IN2_E2") (pintype "input"))
      (node (ref "EF10") (pin "AJ2") (pinfunction "CJ2_AJ2") (pintype "output"))
    )
    (net (code "591") (name "MFTS1_") (class "Default")
      (node (ref "E14") (pin "U2") (pinfunction "IN2_U2") (pintype "input"))
      (node (ref "EF10") (pin "AK2") (pinfunction "CK2_AK2") (pintype "output"))
    )
    (net (code "592") (name "MFTS2") (class "Default")
      (node (ref "E27") (pin "J2") (pinfunction "IN2A_J2") (pintype "input"))
      (node (ref "E28") (pin "E1") (pinfunction "IN2A_E1") (pintype "input"))
      (node (ref "E30") (pin "K1") (pinfunction "IN4A_K1") (pintype "input"))
      (node (ref "EF10") (pin "AF2") (pinfunction "CF2_AF2") (pintype "output"))
    )
    (net (code "593") (name "MFTS2_") (class "Default")
      (node (ref "D12") (pin "R1") (pinfunction "IN2_R1") (pintype "input"))
      (node (ref "E14") (pin "V2") (pinfunction "IN3_V2") (pintype "input"))
      (node (ref "EF10") (pin "AH2") (pinfunction "CH2_AH2") (pintype "output"))
    )
    (net (code "594") (name "MFTS3") (class "Default")
      (node (ref "E15") (pin "V2") (pinfunction "OUT_V2") (pintype "output"))
      (node (ref "E29") (pin "N2") (pinfunction "IN4A_N2") (pintype "input"))
      (node (ref "F29") (pin "R1") (pinfunction "IN2_R1") (pintype "input"))
    )
    (net (code "595") (name "MID_AC0") (class "Default")
      (node (ref "D19") (pin "M1") (pinfunction "IN3_M1") (pintype "input"))
      (node (ref "D20") (pin "B1") (pinfunction "IN2_B1") (pintype "input"))
      (node (ref "E24") (pin "S1") (pinfunction "OUT_S1") (pintype "output"))
      (node (ref "F23") (pin "B1") (pinfunction "IN2_B1") (pintype "input"))
    )
    (net (code "596") (name "MP_INT") (class "Default")
      (node (ref "B09") (pin "R1") (pinfunction "IN2_R1") (pintype "input"))
      (node (ref "B09") (pin "S2") (pinfunction "OUT_S2") (pintype "output"))
    )
    (net (code "597") (name "MP_INT_") (class "Default")
      (node (ref "B07") (pin "L2") (pinfunction "IN3_L2") (pintype "input"))
      (node (ref "B09") (pin "P2") (pinfunction "IN1_P2") (pintype "input"))
      (node (ref "B09") (pin "S1") (pinfunction "OUT_S1") (pintype "output"))
      (node (ref "J15") (pin "H2") (pinfunction "IN4_H2") (pintype "input"))
    )
    (net (code "598") (name "MP_SKIP_") (class "Default")
      (node (ref "B07") (pin "M2") (pinfunction "OUT_M2") (pintype "output"))
      (node (ref "J15") (pin "D1") (pinfunction "IN4_D1") (pintype "input"))
    )
    (net (code "599") (name "MQ00") (class "Default")
      (node (ref "C14") (pin "J1") (pinfunction "IN2_J1") (pintype "input"))
      (node (ref "C23") (pin "E1") (pinfunction "1_E1") (pintype "output"))
      (node (ref "D18") (pin "S1") (pinfunction "IN3_S1") (pintype "input"))
      (node (ref "EF34") (pin "BH1") (pinfunction "BH1_BH1") (pintype "input"))
    )
    (net (code "600") (name "MQ00_") (class "Default")
      (node (ref "C23") (pin "F1") (pinfunction "0_F1") (pintype "output"))
      (node (ref "D18") (pin "N2") (pinfunction "IN1_N2") (pintype "input"))
      (node (ref "D21") (pin "K2") (pinfunction "IN1_K2") (pintype "input"))
      (node (ref "E40") (pin "S2") (pinfunction "P$2_S2") (pintype "bidirectional"))
    )
    (net (code "601") (name "MQ01") (class "Default")
      (node (ref "C14") (pin "E2") (pinfunction "IN2_E2") (pintype "input"))
      (node (ref "C14") (pin "M2") (pinfunction "IN2_M2") (pintype "input"))
      (node (ref "C23") (pin "H2") (pinfunction "1_H2") (pintype "output"))
      (node (ref "EF34") (pin "BN2") (pinfunction "BN2_BN2") (pintype "input"))
    )
    (net (code "602") (name "MQ01_") (class "Default")
      (node (ref "C23") (pin "J2") (pinfunction "0_J2") (pintype "output"))
      (node (ref "D21") (pin "L2") (pinfunction "IN2_L2") (pintype "input"))
      (node (ref "E40") (pin "M2") (pinfunction "P$2_M2") (pintype "bidirectional"))
    )
    (net (code "603") (name "MQ02") (class "Default")
      (node (ref "C14") (pin "M1") (pinfunction "IN2_M1") (pintype "input"))
      (node (ref "C15") (pin "B1") (pinfunction "IN2_B1") (pintype "input"))
      (node (ref "C23") (pin "L1") (pinfunction "1_L1") (pintype "output"))
      (node (ref "EF35") (pin "BH1") (pinfunction "BH1_BH1") (pintype "input"))
    )
    (net (code "604") (name "MQ02_") (class "Default")
      (node (ref "C23") (pin "M1") (pinfunction "0_M1") (pintype "output"))
      (node (ref "D21") (pin "M2") (pinfunction "IN3_M2") (pintype "input"))
      (node (ref "E40") (pin "N2") (pinfunction "P$2_N2") (pintype "bidirectional"))
    )
    (net (code "605") (name "MQ03") (class "Default")
      (node (ref "C14") (pin "R2") (pinfunction "IN2_R2") (pintype "input"))
      (node (ref "C15") (pin "J1") (pinfunction "IN2_J1") (pintype "input"))
      (node (ref "C23") (pin "P2") (pinfunction "1_P2") (pintype "output"))
      (node (ref "EF35") (pin "BN2") (pinfunction "BN2_BN2") (pintype "input"))
    )
    (net (code "606") (name "MQ03_") (class "Default")
      (node (ref "C23") (pin "R2") (pinfunction "0_R2") (pintype "output"))
      (node (ref "D21") (pin "N2") (pinfunction "IN4_N2") (pintype "input"))
      (node (ref "E40") (pin "L2") (pinfunction "P$2_L2") (pintype "bidirectional"))
    )
    (net (code "607") (name "MQ04") (class "Default")
      (node (ref "C15") (pin "E2") (pinfunction "IN2_E2") (pintype "input"))
      (node (ref "C15") (pin "M2") (pinfunction "IN2_M2") (pintype "input"))
      (node (ref "C23") (pin "S1") (pinfunction "1_S1") (pintype "output"))
      (node (ref "EF36") (pin "BH1") (pinfunction "BH1_BH1") (pintype "input"))
    )
    (net (code "608") (name "MQ04_") (class "Default")
      (node (ref "C23") (pin "U1") (pinfunction "0_U1") (pintype "output"))
      (node (ref "D21") (pin "M1") (pinfunction "IN1_M1") (pintype "input"))
      (node (ref "E40") (pin "F1") (pinfunction "P$2_F1") (pintype "bidirectional"))
    )
    (net (code "609") (name "MQ05") (class "Default")
      (node (ref "C15") (pin "M1") (pinfunction "IN2_M1") (pintype "input"))
      (node (ref "C16") (pin "B1") (pinfunction "IN2_B1") (pintype "input"))
      (node (ref "C23") (pin "V2") (pinfunction "1_V2") (pintype "output"))
      (node (ref "EF36") (pin "BN2") (pinfunction "BN2_BN2") (pintype "input"))
    )
    (net (code "610") (name "MQ05_") (class "Default")
      (node (ref "C23") (pin "V1") (pinfunction "0_V1") (pintype "output"))
      (node (ref "D21") (pin "N1") (pinfunction "IN2_N1") (pintype "input"))
      (node (ref "E40") (pin "H1") (pinfunction "P$2_H1") (pintype "bidirectional"))
    )
    (net (code "611") (name "MQ06") (class "Default")
      (node (ref "C15") (pin "R2") (pinfunction "IN2_R2") (pintype "input"))
      (node (ref "C16") (pin "J1") (pinfunction "IN2_J1") (pintype "input"))
      (node (ref "C24") (pin "E1") (pinfunction "1_E1") (pintype "output"))
      (node (ref "EF37") (pin "BH1") (pinfunction "BH1_BH1") (pintype "input"))
    )
    (net (code "612") (name "MQ06_") (class "Default")
      (node (ref "C24") (pin "F1") (pinfunction "0_F1") (pintype "output"))
      (node (ref "D21") (pin "P1") (pinfunction "IN3_P1") (pintype "input"))
      (node (ref "F40") (pin "S2") (pinfunction "P$2_S2") (pintype "bidirectional"))
    )
    (net (code "613") (name "MQ07") (class "Default")
      (node (ref "C16") (pin "E2") (pinfunction "IN2_E2") (pintype "input"))
      (node (ref "C16") (pin "M2") (pinfunction "IN2_M2") (pintype "input"))
      (node (ref "C24") (pin "H2") (pinfunction "1_H2") (pintype "output"))
      (node (ref "EF37") (pin "BN2") (pinfunction "BN2_BN2") (pintype "input"))
    )
    (net (code "614") (name "MQ07_") (class "Default")
      (node (ref "C24") (pin "J2") (pinfunction "0_J2") (pintype "output"))
      (node (ref "D21") (pin "R1") (pinfunction "IN4_R1") (pintype "input"))
      (node (ref "F40") (pin "M2") (pinfunction "P$2_M2") (pintype "bidirectional"))
    )
    (net (code "615") (name "MQ08") (class "Default")
      (node (ref "C16") (pin "M1") (pinfunction "IN2_M1") (pintype "input"))
      (node (ref "C17") (pin "B1") (pinfunction "IN2_B1") (pintype "input"))
      (node (ref "C24") (pin "L1") (pinfunction "1_L1") (pintype "output"))
      (node (ref "EF38") (pin "BH1") (pinfunction "BH1_BH1") (pintype "input"))
    )
    (net (code "616") (name "MQ08_") (class "Default")
      (node (ref "C24") (pin "M1") (pinfunction "0_M1") (pintype "output"))
      (node (ref "D21") (pin "R2") (pinfunction "IN1_R2") (pintype "input"))
      (node (ref "F40") (pin "N2") (pinfunction "P$2_N2") (pintype "bidirectional"))
    )
    (net (code "617") (name "MQ09") (class "Default")
      (node (ref "C16") (pin "R2") (pinfunction "IN2_R2") (pintype "input"))
      (node (ref "C17") (pin "J1") (pinfunction "IN2_J1") (pintype "input"))
      (node (ref "C24") (pin "P2") (pinfunction "1_P2") (pintype "output"))
      (node (ref "EF38") (pin "BN2") (pinfunction "BN2_BN2") (pintype "input"))
    )
    (net (code "618") (name "MQ09_") (class "Default")
      (node (ref "C24") (pin "R2") (pinfunction "0_R2") (pintype "output"))
      (node (ref "D21") (pin "S2") (pinfunction "IN2_S2") (pintype "input"))
      (node (ref "F40") (pin "L2") (pinfunction "P$2_L2") (pintype "bidirectional"))
    )
    (net (code "619") (name "MQ10") (class "Default")
      (node (ref "C17") (pin "E2") (pinfunction "IN2_E2") (pintype "input"))
      (node (ref "C17") (pin "M2") (pinfunction "IN2_M2") (pintype "input"))
      (node (ref "C24") (pin "S1") (pinfunction "1_S1") (pintype "output"))
      (node (ref "D13") (pin "D2") (pinfunction "IN1_D2") (pintype "input"))
      (node (ref "D23") (pin "V1") (pinfunction "IN2A_V1") (pintype "input"))
      (node (ref "EF39") (pin "BH1") (pinfunction "BH1_BH1") (pintype "input"))
    )
    (net (code "620") (name "MQ10_") (class "Default")
      (node (ref "C24") (pin "U1") (pinfunction "0_U1") (pintype "output"))
      (node (ref "D12") (pin "E2") (pinfunction "IN2_E2") (pintype "input"))
      (node (ref "D21") (pin "T2") (pinfunction "IN3_T2") (pintype "input"))
      (node (ref "F40") (pin "F1") (pinfunction "P$2_F1") (pintype "bidirectional"))
    )
    (net (code "621") (name "MQ11") (class "Default")
      (node (ref "C17") (pin "M1") (pinfunction "IN2_M1") (pintype "input"))
      (node (ref "C24") (pin "V2") (pinfunction "1_V2") (pintype "output"))
      (node (ref "D20") (pin "K2") (pinfunction "IN1_K2") (pintype "input"))
      (node (ref "D23") (pin "J2") (pinfunction "IN2A_J2") (pintype "input"))
      (node (ref "D23") (pin "U1") (pinfunction "IN1B_U1") (pintype "input"))
      (node (ref "EF39") (pin "BN2") (pinfunction "BN2_BN2") (pintype "input"))
    )
    (net (code "622") (name "MQ11_") (class "Default")
      (node (ref "C24") (pin "V1") (pinfunction "0_V1") (pintype "output"))
      (node (ref "D13") (pin "U2") (pinfunction "IN2_U2") (pintype "input"))
      (node (ref "D15") (pin "P2") (pinfunction "IN1_P2") (pintype "input"))
      (node (ref "D21") (pin "U2") (pinfunction "IN4_U2") (pintype "input"))
      (node (ref "D23") (pin "M2") (pinfunction "IN3B_M2") (pintype "input"))
      (node (ref "D23") (pin "U2") (pinfunction "IN2B_U2") (pintype "input"))
      (node (ref "F40") (pin "H1") (pinfunction "P$2_H1") (pintype "bidirectional"))
    )
    (net (code "623") (name "MQ_ENABLE") (class "Default")
      (node (ref "D22") (pin "L1") (pinfunction "OUT_L1") (pintype "open_collector"))
      (node (ref "EF34") (pin "BF1") (pinfunction "BF1_BF1") (pintype "input"))
      (node (ref "EF35") (pin "BF1") (pinfunction "BF1_BF1") (pintype "input"))
      (node (ref "EF36") (pin "BF1") (pinfunction "BF1_BF1") (pintype "input"))
      (node (ref "EF37") (pin "BF1") (pinfunction "BF1_BF1") (pintype "input"))
      (node (ref "EF38") (pin "BF1") (pinfunction "BF1_BF1") (pintype "input"))
      (node (ref "EF39") (pin "BF1") (pinfunction "BF1_BF1") (pintype "input"))
    )
    (net (code "624") (name "MQ_LOAD") (class "Default")
      (node (ref "C23") (pin "B1") (pinfunction "C_B1") (pintype "input"))
      (node (ref "C23") (pin "D2") (pinfunction "C_D2") (pintype "input"))
      (node (ref "C23") (pin "H1") (pinfunction "C_H1") (pintype "input"))
      (node (ref "C23") (pin "L2") (pinfunction "C_L2") (pintype "input"))
      (node (ref "C23") (pin "N1") (pinfunction "C_N1") (pintype "input"))
      (node (ref "C23") (pin "S2") (pinfunction "C_S2") (pintype "input"))
      (node (ref "C24") (pin "B1") (pinfunction "C_B1") (pintype "input"))
      (node (ref "C24") (pin "D2") (pinfunction "C_D2") (pintype "input"))
      (node (ref "C24") (pin "H1") (pinfunction "C_H1") (pintype "input"))
      (node (ref "C24") (pin "L2") (pinfunction "C_L2") (pintype "input"))
      (node (ref "C24") (pin "N1") (pinfunction "C_N1") (pintype "input"))
      (node (ref "C24") (pin "S2") (pinfunction "C_S2") (pintype "input"))
      (node (ref "D22") (pin "S1") (pinfunction "OUT_S1") (pintype "open_collector"))
    )
    (net (code "625") (name "MQ_LOW_AC0") (class "Default")
      (node (ref "D15") (pin "F2") (pinfunction "OUT_F2") (pintype "output"))
      (node (ref "D19") (pin "L1") (pinfunction "IN2_L1") (pintype "input"))
      (node (ref "D20") (pin "A1") (pinfunction "IN1_A1") (pintype "input"))
    )
    (net (code "626") (name "MUY") (class "Default")
      (node (ref "D15") (pin "R2") (pinfunction "IN2_R2") (pintype "input"))
      (node (ref "D16") (pin "S1") (pinfunction "OUT_S1") (pintype "output"))
      (node (ref "D23") (pin "A1") (pinfunction "IN1A_A1") (pintype "input"))
    )
    (net (code "627") (name "MUY_") (class "Default")
      (node (ref "D16") (pin "P1") (pinfunction "IN1_P1") (pintype "input"))
      (node (ref "D19") (pin "U1") (pinfunction "OUT_U1") (pintype "output"))
    )
    (net (code "628") (name "MUY_DVI_") (class "Default")
      (node (ref "D15") (pin "K1") (pinfunction "OUT_K1") (pintype "output"))
      (node (ref "D21") (pin "D2") (pinfunction "IN1_D2") (pintype "input"))
    )
    (net (code "629") (name "NEG_CLAMP") (class "Default")
      (node (ref "A39") (pin "R2") (pinfunction "P$2_R2") (pintype "passive"))
      (node (ref "C25") (pin "V2") (pinfunction "V2_V2") (pintype "input"))
      (node (ref "C26") (pin "V2") (pinfunction "V2_V2") (pintype "input"))
      (node (ref "C30") (pin "V2") (pinfunction "V2_V2") (pintype "input"))
      (node (ref "C31") (pin "V2") (pinfunction "V2_V2") (pintype "input"))
      (node (ref "C32") (pin "V2") (pinfunction "V2_V2") (pintype "input"))
      (node (ref "C33") (pin "V2") (pinfunction "V2_V2") (pintype "input"))
      (node (ref "C37") (pin "V2") (pinfunction "V2_V2") (pintype "input"))
      (node (ref "C38") (pin "V2") (pinfunction "V2_V2") (pintype "input"))
      (node (ref "C39") (pin "V2") (pinfunction "V2_V2") (pintype "input"))
      (node (ref "D25") (pin "V2") (pinfunction "V2_V2") (pintype "input"))
      (node (ref "D26") (pin "V2") (pinfunction "V2_V2") (pintype "input"))
      (node (ref "D30") (pin "V2") (pinfunction "V2_V2") (pintype "input"))
      (node (ref "D31") (pin "V2") (pinfunction "V2_V2") (pintype "input"))
      (node (ref "D32") (pin "V2") (pinfunction "V2_V2") (pintype "input"))
      (node (ref "D33") (pin "V2") (pinfunction "V2_V2") (pintype "input"))
      (node (ref "D37") (pin "V2") (pinfunction "V2_V2") (pintype "input"))
      (node (ref "D38") (pin "V2") (pinfunction "V2_V2") (pintype "input"))
      (node (ref "D39") (pin "V2") (pinfunction "V2_V2") (pintype "input"))
    )
    (net (code "630") (name "NMI") (class "Default")
      (node (ref "D14") (pin "M2") (pinfunction "IN2_M2") (pintype "input"))
      (node (ref "D14") (pin "U2") (pinfunction "IN2_U2") (pintype "input"))
      (node (ref "D16") (pin "V2") (pinfunction "OUT_V2") (pintype "output"))
      (node (ref "D23") (pin "N1") (pinfunction "IN5B_N1") (pintype "input"))
    )
    (net (code "631") (name "NMI_") (class "Default")
      (node (ref "D16") (pin "T2") (pinfunction "IN1_T2") (pintype "input"))
      (node (ref "D20") (pin "V2") (pinfunction "OUT_V2") (pintype "output"))
    )
    (net (code "632") (name "NORM") (class "Default")
      (node (ref "C18") (pin "J2") (pinfunction "IN2_J2") (pintype "input"))
      (node (ref "D17") (pin "H2") (pinfunction "OUT_H2") (pintype "output"))
    )
    (net (code "633") (name "NORM_") (class "Default")
      (node (ref "C18") (pin "K2") (pinfunction "OUT_K2") (pintype "output"))
      (node (ref "D14") (pin "L2") (pinfunction "IN1_L2") (pintype "input"))
    )
    (net (code "634") (name "NO_SHIFT") (class "Default")
      (node (ref "E31") (pin "S1") (pinfunction "OUT_S1") (pintype "open_collector"))
      (node (ref "EF34") (pin "AE1") (pinfunction "AE1_AE1") (pintype "input"))
      (node (ref "EF35") (pin "AE1") (pinfunction "AE1_AE1") (pintype "input"))
      (node (ref "EF36") (pin "AE1") (pinfunction "AE1_AE1") (pintype "input"))
      (node (ref "EF37") (pin "AE1") (pinfunction "AE1_AE1") (pintype "input"))
      (node (ref "EF38") (pin "AE1") (pinfunction "AE1_AE1") (pintype "input"))
      (node (ref "EF39") (pin "AE1") (pinfunction "AE1_AE1") (pintype "input"))
      (node (ref "F33") (pin "J1") (pinfunction "IN3B_J1") (pintype "input"))
    )
    (net (code "635") (name "Net-(A05A-OUT)") (class "Default")
      (node (ref "A05") (pin "C1") (pinfunction "OUT_C1") (pintype "output"))
      (node (ref "A05") (pin "E2") (pinfunction "IN2_E2") (pintype "input"))
    )
    (net (code "636") (name "Net-(A05B-IN2)") (class "Default")
      (node (ref "A05") (pin "E1") (pinfunction "IN2_E1") (pintype "input"))
      (node (ref "B04") (pin "H2") (pinfunction "OUT_H2") (pintype "output"))
    )
    (net (code "637") (name "Net-(A05B-OUT)") (class "Default")
      (node (ref "A05") (pin "D2") (pinfunction "IN1_D2") (pintype "input"))
      (node (ref "A05") (pin "F1") (pinfunction "OUT_F1") (pintype "output"))
    )
    (net (code "638") (name "Net-(A05C-OUT)") (class "Default")
      (node (ref "A05") (pin "F2") (pinfunction "OUT_F2") (pintype "output"))
      (node (ref "A05") (pin "H1") (pinfunction "IN1_H1") (pintype "input"))
    )
    (net (code "639") (name "Net-(A05F-OUT)") (class "Default")
      (node (ref "A05") (pin "K1") (pinfunction "OUT_K1") (pintype "output"))
      (node (ref "A05") (pin "L1") (pinfunction "IN1_L1") (pintype "input"))
    )
    (net (code "640") (name "Net-(A05H-OUT)") (class "Default")
      (node (ref "A05") (pin "N1") (pinfunction "OUT_N1") (pintype "output"))
      (node (ref "A05") (pin "R1") (pinfunction "IN2_R1") (pintype "input"))
      (node (ref "B04") (pin "P1") (pinfunction "IN1_P1") (pintype "input"))
      (node (ref "B04") (pin "R1") (pinfunction "IN2_R1") (pintype "input"))
    )
    (net (code "641") (name "Net-(A05I-OUT)") (class "Default")
      (node (ref "A05") (pin "N2") (pinfunction "OUT_N2") (pintype "output"))
      (node (ref "A05") (pin "P1") (pinfunction "IN1_P1") (pintype "input"))
    )
    (net (code "642") (name "Net-(A05J-OUT)") (class "Default")
      (node (ref "A05") (pin "S1") (pinfunction "OUT_S1") (pintype "output"))
      (node (ref "B05") (pin "M2") (pinfunction "D_M2") (pintype "input"))
    )
    (net (code "643") (name "Net-(A05K-IN1)") (class "Default")
      (node (ref "A05") (pin "P2") (pinfunction "IN1_P2") (pintype "input"))
      (node (ref "A05") (pin "R2") (pinfunction "IN2_R2") (pintype "input"))
      (node (ref "B04") (pin "U1") (pinfunction "OUT_U1") (pintype "output"))
    )
    (net (code "644") (name "Net-(A05N-IN2)") (class "Default")
      (node (ref "A05") (pin "U2") (pinfunction "IN2_U2") (pintype "input"))
      (node (ref "B04") (pin "J1") (pinfunction "OUT_J1") (pintype "output"))
    )
    (net (code "645") (name "Net-(A06C-OUT)") (class "Default")
      (node (ref "A06") (pin "F2") (pinfunction "OUT_F2") (pintype "output"))
      (node (ref "A06") (pin "H1") (pinfunction "IN1_H1") (pintype "input"))
    )
    (net (code "646") (name "Net-(A06F-OUT)") (class "Default")
      (node (ref "A06") (pin "K1") (pinfunction "OUT_K1") (pintype "output"))
      (node (ref "F30") (pin "N1") (pinfunction "IN2_N1") (pintype "input"))
    )
    (net (code "647") (name "Net-(A06H-IN1)") (class "Default")
      (node (ref "A06") (pin "L1") (pinfunction "IN1_L1") (pintype "input"))
      (node (ref "F09") (pin "J2") (pinfunction "OUT_J2") (pintype "output"))
    )
    (net (code "648") (name "Net-(A06I-IN1)") (class "Default")
      (node (ref "A06") (pin "L2") (pinfunction "IN1_L2") (pintype "input"))
      (node (ref "A15") (pin "V2") (pinfunction "OUT_V2") (pintype "output"))
    )
    (net (code "649") (name "Net-(A06J-OUT)") (class "Default")
      (node (ref "A06") (pin "P2") (pinfunction "IN1_P2") (pintype "input"))
      (node (ref "A06") (pin "S1") (pinfunction "OUT_S1") (pintype "output"))
    )
    (net (code "650") (name "Net-(A06K-OUT)") (class "Default")
      (node (ref "A06") (pin "S2") (pinfunction "OUT_S2") (pintype "output"))
      (node (ref "A06") (pin "T2") (pinfunction "IN1_T2") (pintype "input"))
    )
    (net (code "651") (name "Net-(A07C-1B)") (class "Default")
      (node (ref "A07") (pin "A1") (pinfunction "1B_A1") (pintype "input"))
      (node (ref "B08") (pin "K1") (pinfunction "OUT_K1") (pintype "output"))
    )
    (net (code "652") (name "Net-(A07C-2B)") (class "Default")
      (node (ref "A07") (pin "B1") (pinfunction "2B_B1") (pintype "input"))
      (node (ref "B08") (pin "F2") (pinfunction "OUT_F2") (pintype "output"))
    )
    (net (code "653") (name "Net-(A07C-4B)") (class "Default")
      (node (ref "A07") (pin "C1") (pinfunction "4B_C1") (pintype "input"))
      (node (ref "B08") (pin "F1") (pinfunction "OUT_F1") (pintype "output"))
    )
    (net (code "654") (name "Net-(A07C-8B)") (class "Default")
      (node (ref "A07") (pin "D1") (pinfunction "8B_D1") (pintype "input"))
      (node (ref "B08") (pin "C1") (pinfunction "OUT_C1") (pintype "output"))
    )
    (net (code "655") (name "Net-(A07C-EVEN)") (class "Default")
      (node (ref "A07") (pin "L1") (pinfunction "EVEN_L1") (pintype "output"))
      (node (ref "A08") (pin "A1") (pinfunction "1B_A1") (pintype "input"))
    )
    (net (code "656") (name "Net-(A07C-ODD)") (class "Default")
      (node (ref "A07") (pin "K1") (pinfunction "ODD_K1") (pintype "output"))
      (node (ref "A08") (pin "E1") (pinfunction "1A_E1") (pintype "input"))
    )
    (net (code "657") (name "Net-(A07D-1B)") (class "Default")
      (node (ref "A07") (pin "K2") (pinfunction "1B_K2") (pintype "input"))
      (node (ref "B09") (pin "F1") (pinfunction "OUT_F1") (pintype "output"))
    )
    (net (code "658") (name "Net-(A07D-2B)") (class "Default")
      (node (ref "A07") (pin "L2") (pinfunction "2B_L2") (pintype "input"))
      (node (ref "B09") (pin "C1") (pinfunction "OUT_C1") (pintype "output"))
    )
    (net (code "659") (name "Net-(A07D-4B)") (class "Default")
      (node (ref "A07") (pin "M2") (pinfunction "4B_M2") (pintype "input"))
      (node (ref "B08") (pin "V2") (pinfunction "OUT_V2") (pintype "output"))
    )
    (net (code "660") (name "Net-(A07D-8B)") (class "Default")
      (node (ref "A07") (pin "N2") (pinfunction "8B_N2") (pintype "input"))
      (node (ref "B08") (pin "S2") (pinfunction "OUT_S2") (pintype "output"))
    )
    (net (code "661") (name "Net-(A07D-EVEN)") (class "Default")
      (node (ref "A07") (pin "V2") (pinfunction "EVEN_V2") (pintype "output"))
      (node (ref "A08") (pin "C1") (pinfunction "4B_C1") (pintype "input"))
    )
    (net (code "662") (name "Net-(A07D-ODD)") (class "Default")
      (node (ref "A07") (pin "U2") (pinfunction "ODD_U2") (pintype "output"))
      (node (ref "A08") (pin "H1") (pinfunction "4A_H1") (pintype "input"))
    )
    (net (code "663") (name "Net-(A08C-2A)") (class "Default")
      (node (ref "A08") (pin "F1") (pinfunction "2A_F1") (pintype "input"))
      (node (ref "A08") (pin "U2") (pinfunction "ODD_U2") (pintype "output"))
    )
    (net (code "664") (name "Net-(A08C-2B)") (class "Default")
      (node (ref "A08") (pin "B1") (pinfunction "2B_B1") (pintype "input"))
      (node (ref "A08") (pin "V2") (pinfunction "EVEN_V2") (pintype "output"))
    )
    (net (code "665") (name "Net-(A08C-8B)") (class "Default")
      (node (ref "A08") (pin "D1") (pinfunction "8B_D1") (pintype "input"))
      (node (ref "B09") (pin "F2") (pinfunction "OUT_F2") (pintype "output"))
    )
    (net (code "666") (name "Net-(A08D-1B)") (class "Default")
      (node (ref "A08") (pin "K2") (pinfunction "1B_K2") (pintype "input"))
      (node (ref "B08") (pin "S1") (pinfunction "OUT_S1") (pintype "output"))
    )
    (net (code "667") (name "Net-(A08D-2B)") (class "Default")
      (node (ref "A08") (pin "L2") (pinfunction "2B_L2") (pintype "input"))
      (node (ref "B08") (pin "N2") (pinfunction "OUT_N2") (pintype "output"))
    )
    (net (code "668") (name "Net-(A08D-4B)") (class "Default")
      (node (ref "A08") (pin "M2") (pinfunction "4B_M2") (pintype "input"))
      (node (ref "B08") (pin "N1") (pinfunction "OUT_N1") (pintype "output"))
    )
    (net (code "669") (name "Net-(A08D-8B)") (class "Default")
      (node (ref "A08") (pin "N2") (pinfunction "8B_N2") (pintype "input"))
      (node (ref "B08") (pin "K2") (pinfunction "OUT_K2") (pintype "output"))
    )
    (net (code "670") (name "Net-(A09C-EVEN)") (class "Default")
      (node (ref "A09") (pin "L1") (pinfunction "EVEN_L1") (pintype "output"))
      (node (ref "A10") (pin "A1") (pinfunction "1B_A1") (pintype "input"))
    )
    (net (code "671") (name "Net-(A09C-ODD)") (class "Default")
      (node (ref "A09") (pin "K1") (pinfunction "ODD_K1") (pintype "output"))
      (node (ref "A10") (pin "E1") (pinfunction "1A_E1") (pintype "input"))
    )
    (net (code "672") (name "Net-(A09D-EVEN)") (class "Default")
      (node (ref "A09") (pin "V2") (pinfunction "EVEN_V2") (pintype "output"))
      (node (ref "A10") (pin "C1") (pinfunction "4B_C1") (pintype "input"))
    )
    (net (code "673") (name "Net-(A09D-ODD)") (class "Default")
      (node (ref "A09") (pin "U2") (pinfunction "ODD_U2") (pintype "output"))
      (node (ref "A10") (pin "H1") (pinfunction "4A_H1") (pintype "input"))
    )
    (net (code "674") (name "Net-(A10C-2A)") (class "Default")
      (node (ref "A10") (pin "F1") (pinfunction "2A_F1") (pintype "input"))
      (node (ref "A10") (pin "U2") (pinfunction "ODD_U2") (pintype "output"))
    )
    (net (code "675") (name "Net-(A10C-2B)") (class "Default")
      (node (ref "A10") (pin "B1") (pinfunction "2B_B1") (pintype "input"))
      (node (ref "A10") (pin "V2") (pinfunction "EVEN_V2") (pintype "output"))
    )
    (net (code "676") (name "Net-(A11A-OUT)") (class "Default")
      (node (ref "A11") (pin "C1") (pinfunction "OUT_C1") (pintype "output"))
      (node (ref "A13") (pin "J1") (pinfunction "IN2_J1") (pintype "input"))
    )
    (net (code "677") (name "Net-(A11B-IN1)") (class "Default")
      (node (ref "A11") (pin "D1") (pinfunction "IN1_D1") (pintype "input"))
      (node (ref "A11") (pin "H2") (pinfunction "IN1_H2") (pintype "input"))
      (node (ref "A11") (pin "P1") (pinfunction "IN1_P1") (pintype "input"))
      (node (ref "A14") (pin "N1") (pinfunction "OUT_N1") (pintype "output"))
    )
    (net (code "678") (name "Net-(A11B-OUT)") (class "Default")
      (node (ref "A11") (pin "F1") (pinfunction "OUT_F1") (pintype "output"))
      (node (ref "A20") (pin "D2") (pinfunction "IN1_D2") (pintype "input"))
    )
    (net (code "679") (name "Net-(A11C-OUT)") (class "Default")
      (node (ref "A11") (pin "F2") (pinfunction "OUT_F2") (pintype "output"))
      (node (ref "A20") (pin "E2") (pinfunction "IN2_E2") (pintype "input"))
    )
    (net (code "680") (name "Net-(A11F-IN1)") (class "Default")
      (node (ref "A11") (pin "H1") (pinfunction "IN1_H1") (pintype "input"))
      (node (ref "A11") (pin "L2") (pinfunction "IN1_L2") (pintype "input"))
      (node (ref "A11") (pin "T2") (pinfunction "IN1_T2") (pintype "input"))
      (node (ref "A14") (pin "S1") (pinfunction "OUT_S1") (pintype "output"))
    )
    (net (code "681") (name "Net-(A11F-OUT)") (class "Default")
      (node (ref "A11") (pin "K1") (pinfunction "OUT_K1") (pintype "output"))
      (node (ref "A20") (pin "F2") (pinfunction "IN3_F2") (pintype "input"))
    )
    (net (code "682") (name "Net-(A11G-OUT)") (class "Default")
      (node (ref "A11") (pin "K2") (pinfunction "OUT_K2") (pintype "output"))
      (node (ref "A20") (pin "E1") (pinfunction "IN1_E1") (pintype "input"))
    )
    (net (code "683") (name "Net-(A11H-OUT)") (class "Default")
      (node (ref "A11") (pin "N1") (pinfunction "OUT_N1") (pintype "output"))
      (node (ref "A20") (pin "F1") (pinfunction "IN2_F1") (pintype "input"))
    )
    (net (code "684") (name "Net-(A11I-OUT)") (class "Default")
      (node (ref "A11") (pin "N2") (pinfunction "OUT_N2") (pintype "output"))
      (node (ref "A20") (pin "H1") (pinfunction "IN3_H1") (pintype "input"))
    )
    (net (code "685") (name "Net-(A11J-OUT)") (class "Default")
      (node (ref "A11") (pin "S1") (pinfunction "OUT_S1") (pintype "output"))
      (node (ref "A20") (pin "J2") (pinfunction "IN1_J2") (pintype "input"))
    )
    (net (code "686") (name "Net-(A11K-OUT)") (class "Default")
      (node (ref "A11") (pin "S2") (pinfunction "OUT_S2") (pintype "output"))
      (node (ref "A20") (pin "K2") (pinfunction "IN2_K2") (pintype "input"))
    )
    (net (code "687") (name "Net-(A11N-OUT)") (class "Default")
      (node (ref "A11") (pin "V2") (pinfunction "OUT_V2") (pintype "output"))
      (node (ref "A20") (pin "L2") (pinfunction "IN3_L2") (pintype "input"))
    )
    (net (code "688") (name "Net-(A12A-OUT)") (class "Default")
      (node (ref "A12") (pin "C1") (pinfunction "OUT_C1") (pintype "output"))
      (node (ref "F11") (pin "E2") (pinfunction "IN2_E2") (pintype "input"))
    )
    (net (code "689") (name "Net-(A12B-OUT)") (class "Default")
      (node (ref "A12") (pin "F1") (pinfunction "OUT_F1") (pintype "output"))
      (node (ref "B20") (pin "N2") (pinfunction "IN1_N2") (pintype "input"))
    )
    (net (code "690") (name "Net-(A12C-IN1)") (class "Default")
      (node (ref "A12") (pin "D2") (pinfunction "IN1_D2") (pintype "input"))
      (node (ref "A12") (pin "L1") (pinfunction "IN1_L1") (pintype "input"))
      (node (ref "A12") (pin "P2") (pinfunction "IN1_P2") (pintype "input"))
      (node (ref "A13") (pin "K1") (pinfunction "OUT_K1") (pintype "output"))
    )
    (net (code "691") (name "Net-(A12C-OUT)") (class "Default")
      (node (ref "A12") (pin "F2") (pinfunction "OUT_F2") (pintype "output"))
      (node (ref "B20") (pin "P2") (pinfunction "IN2_P2") (pintype "input"))
    )
    (net (code "692") (name "Net-(A12F-OUT)") (class "Default")
      (node (ref "A12") (pin "K1") (pinfunction "OUT_K1") (pintype "output"))
      (node (ref "B20") (pin "R2") (pinfunction "IN3_R2") (pintype "input"))
    )
    (net (code "693") (name "Net-(A12G-OUT)") (class "Default")
      (node (ref "A12") (pin "K2") (pinfunction "OUT_K2") (pintype "output"))
      (node (ref "B20") (pin "P1") (pinfunction "IN1_P1") (pintype "input"))
    )
    (net (code "694") (name "Net-(A12H-OUT)") (class "Default")
      (node (ref "A12") (pin "N1") (pinfunction "OUT_N1") (pintype "output"))
      (node (ref "B20") (pin "R1") (pinfunction "IN2_R1") (pintype "input"))
    )
    (net (code "695") (name "Net-(A12I-OUT)") (class "Default")
      (node (ref "A12") (pin "N2") (pinfunction "OUT_N2") (pintype "output"))
      (node (ref "B20") (pin "S1") (pinfunction "IN3_S1") (pintype "input"))
    )
    (net (code "696") (name "Net-(A12J-OUT)") (class "Default")
      (node (ref "A12") (pin "S1") (pinfunction "OUT_S1") (pintype "output"))
      (node (ref "B20") (pin "T2") (pinfunction "IN1_T2") (pintype "input"))
    )
    (net (code "697") (name "Net-(A12K-OUT)") (class "Default")
      (node (ref "A12") (pin "S2") (pinfunction "OUT_S2") (pintype "output"))
      (node (ref "B20") (pin "U2") (pinfunction "IN2_U2") (pintype "input"))
    )
    (net (code "698") (name "Net-(A12N-OUT)") (class "Default")
      (node (ref "A12") (pin "V2") (pinfunction "OUT_V2") (pintype "output"))
      (node (ref "B20") (pin "V2") (pinfunction "IN3_V2") (pintype "input"))
    )
    (net (code "699") (name "Net-(A13A-OUT)") (class "Default")
      (node (ref "A13") (pin "C1") (pinfunction "OUT_C1") (pintype "output"))
      (node (ref "A17") (pin "T2") (pinfunction "IN1_T2") (pintype "input"))
    )
    (net (code "700") (name "Net-(A13B-IN1)") (class "Default")
      (node (ref "A13") (pin "D1") (pinfunction "IN1_D1") (pintype "input"))
      (node (ref "A13") (pin "F2") (pinfunction "OUT_F2") (pintype "output"))
    )
    (net (code "701") (name "Net-(A13H-IN1)") (class "Default")
      (node (ref "A13") (pin "L1") (pinfunction "IN1_L1") (pintype "input"))
      (node (ref "A20") (pin "H2") (pinfunction "OUT_H2") (pintype "output"))
    )
    (net (code "702") (name "Net-(A13J-IN1)") (class "Default")
      (node (ref "A13") (pin "P1") (pinfunction "IN1_P1") (pintype "input"))
      (node (ref "A20") (pin "J1") (pinfunction "OUT_J1") (pintype "output"))
    )
    (net (code "703") (name "Net-(A13N-IN1)") (class "Default")
      (node (ref "A13") (pin "T2") (pinfunction "IN1_T2") (pintype "input"))
      (node (ref "A20") (pin "M2") (pinfunction "OUT_M2") (pintype "output"))
    )
    (net (code "704") (name "Net-(A14A-IN1)") (class "Default")
      (node (ref "A14") (pin "A1") (pinfunction "IN1_A1") (pintype "input"))
      (node (ref "B16") (pin "P2") (pinfunction "OUT_P2") (pintype "open_collector"))
    )
    (net (code "705") (name "Net-(A14A-OUT)") (class "Default")
      (node (ref "A14") (pin "C1") (pinfunction "OUT_C1") (pintype "output"))
      (node (ref "A14") (pin "D1") (pinfunction "IN1_D1") (pintype "input"))
    )
    (net (code "706") (name "Net-(A14C-OUT)") (class "Default")
      (node (ref "A14") (pin "F2") (pinfunction "OUT_F2") (pintype "output"))
      (node (ref "A14") (pin "J2") (pinfunction "IN2_J2") (pintype "input"))
    )
    (net (code "707") (name "Net-(A14H-IN2)") (class "Default")
      (node (ref "A14") (pin "M1") (pinfunction "IN2_M1") (pintype "input"))
      (node (ref "A20") (pin "N1") (pinfunction "OUT_N1") (pintype "output"))
      (node (ref "A20") (pin "T2") (pinfunction "IN1_T2") (pintype "input"))
    )
    (net (code "708") (name "Net-(A14I-IN2)") (class "Default")
      (node (ref "A14") (pin "M2") (pinfunction "IN2_M2") (pintype "input"))
      (node (ref "A20") (pin "S2") (pinfunction "OUT_S2") (pintype "output"))
      (node (ref "A20") (pin "U2") (pinfunction "IN2_U2") (pintype "input"))
    )
    (net (code "709") (name "Net-(A14J-IN2)") (class "Default")
      (node (ref "A14") (pin "R1") (pinfunction "IN2_R1") (pintype "input"))
      (node (ref "A20") (pin "U1") (pinfunction "OUT_U1") (pintype "output"))
      (node (ref "A20") (pin "V2") (pinfunction "IN3_V2") (pintype "input"))
    )
    (net (code "710") (name "Net-(A14K-IN2)") (class "Default")
      (node (ref "A14") (pin "R2") (pinfunction "IN2_R2") (pintype "input"))
      (node (ref "A20") (pin "V1") (pinfunction "OUT_V1") (pintype "output"))
      (node (ref "C12") (pin "D2") (pinfunction "IN1_D2") (pintype "input"))
    )
    (net (code "711") (name "Net-(A15A-OUT)") (class "Default")
      (node (ref "A15") (pin "C1") (pinfunction "OUT_C1") (pintype "output"))
      (node (ref "A15") (pin "D1") (pinfunction "IN1_D1") (pintype "input"))
    )
    (net (code "712") (name "Net-(A15F-IN2)") (class "Default")
      (node (ref "A15") (pin "J1") (pinfunction "IN2_J1") (pintype "input"))
      (node (ref "A19") (pin "V2") (pinfunction "OUT_V2") (pintype "output"))
    )
    (net (code "713") (name "Net-(A15G-IN2)") (class "Default")
      (node (ref "A15") (pin "J2") (pinfunction "IN2_J2") (pintype "input"))
      (node (ref "A15") (pin "N1") (pinfunction "OUT_N1") (pintype "output"))
    )
    (net (code "714") (name "Net-(A15G-OUT)") (class "Default")
      (node (ref "A15") (pin "K2") (pinfunction "OUT_K2") (pintype "output"))
      (node (ref "A18") (pin "B1") (pinfunction "IN2_B1") (pintype "input"))
    )
    (net (code "715") (name "Net-(A15J-IN2)") (class "Default")
      (node (ref "A15") (pin "R1") (pinfunction "IN2_R1") (pintype "input"))
      (node (ref "A15") (pin "S2") (pinfunction "OUT_S2") (pintype "output"))
    )
    (net (code "716") (name "Net-(A16A-OUT)") (class "Default")
      (node (ref "A16") (pin "C1") (pinfunction "OUT_C1") (pintype "output"))
      (node (ref "B16") (pin "A1") (pinfunction "IN1_A1") (pintype "input"))
    )
    (net (code "717") (name "Net-(A16B-OUT)") (class "Default")
      (node (ref "A16") (pin "F1") (pinfunction "OUT_F1") (pintype "output"))
      (node (ref "B16") (pin "B1") (pinfunction "IN2_B1") (pintype "input"))
    )
    (net (code "718") (name "Net-(A16C-OUT)") (class "Default")
      (node (ref "A16") (pin "F2") (pinfunction "OUT_F2") (pintype "output"))
      (node (ref "B16") (pin "C1") (pinfunction "IN3_C1") (pintype "input"))
    )
    (net (code "719") (name "Net-(A16F-OUT)") (class "Default")
      (node (ref "A16") (pin "K1") (pinfunction "OUT_K1") (pintype "output"))
      (node (ref "B16") (pin "D2") (pinfunction "IN1_D2") (pintype "input"))
    )
    (net (code "720") (name "Net-(A16G-OUT)") (class "Default")
      (node (ref "A16") (pin "K2") (pinfunction "OUT_K2") (pintype "output"))
      (node (ref "B16") (pin "E2") (pinfunction "IN2_E2") (pintype "input"))
    )
    (net (code "721") (name "Net-(A16H-OUT)") (class "Default")
      (node (ref "A16") (pin "N1") (pinfunction "OUT_N1") (pintype "output"))
      (node (ref "B16") (pin "F2") (pinfunction "IN3_F2") (pintype "input"))
    )
    (net (code "722") (name "Net-(A16I-OUT)") (class "Default")
      (node (ref "A16") (pin "N2") (pinfunction "OUT_N2") (pintype "output"))
      (node (ref "B16") (pin "F1") (pinfunction "IN1_F1") (pintype "input"))
    )
    (net (code "723") (name "Net-(A16J-OUT)") (class "Default")
      (node (ref "A16") (pin "S1") (pinfunction "OUT_S1") (pintype "output"))
      (node (ref "B16") (pin "H1") (pinfunction "IN2_H1") (pintype "input"))
    )
    (net (code "724") (name "Net-(A16K-OUT)") (class "Default")
      (node (ref "A16") (pin "S2") (pinfunction "OUT_S2") (pintype "output"))
      (node (ref "B16") (pin "J1") (pinfunction "IN3_J1") (pintype "input"))
    )
    (net (code "725") (name "Net-(A16N-OUT)") (class "Default")
      (node (ref "A16") (pin "V2") (pinfunction "OUT_V2") (pintype "output"))
      (node (ref "A20") (pin "A1") (pinfunction "IN1_A1") (pintype "input"))
    )
    (net (code "726") (name "Net-(A17A-IN2)") (class "Default")
      (node (ref "A17") (pin "B1") (pinfunction "IN2_B1") (pintype "input"))
      (node (ref "A20") (pin "D1") (pinfunction "OUT_D1") (pintype "output"))
    )
    (net (code "727") (name "Net-(A17B-OUT)") (class "Default")
      (node (ref "A17") (pin "F1") (pinfunction "OUT_F1") (pintype "output"))
      (node (ref "A20") (pin "C1") (pinfunction "IN3_C1") (pintype "input"))
    )
    (net (code "728") (name "Net-(A17C-IN1)") (class "Default")
      (node (ref "A17") (pin "D2") (pinfunction "IN1_D2") (pintype "input"))
      (node (ref "A18") (pin "F1") (pinfunction "OUT_F1") (pintype "output"))
      (node (ref "B20") (pin "E1") (pinfunction "IN1_E1") (pintype "input"))
    )
    (net (code "729") (name "Net-(A17C-IN2)") (class "Default")
      (node (ref "A17") (pin "E2") (pinfunction "IN2_E2") (pintype "input"))
      (node (ref "A17") (pin "K1") (pinfunction "OUT_K1") (pintype "output"))
    )
    (net (code "730") (name "Net-(A17C-OUT)") (class "Default")
      (node (ref "A17") (pin "F2") (pinfunction "OUT_F2") (pintype "output"))
      (node (ref "B17") (pin "C1") (pinfunction "D_C1") (pintype "input"))
    )
    (net (code "731") (name "Net-(A17G-IN1)") (class "Default")
      (node (ref "A17") (pin "H2") (pinfunction "IN1_H2") (pintype "input"))
      (node (ref "A18") (pin "K2") (pinfunction "OUT_K2") (pintype "output"))
      (node (ref "B20") (pin "J2") (pinfunction "IN1_J2") (pintype "input"))
    )
    (net (code "732") (name "Net-(A17G-IN2)") (class "Default")
      (node (ref "A17") (pin "J2") (pinfunction "IN2_J2") (pintype "input"))
      (node (ref "A17") (pin "N1") (pinfunction "OUT_N1") (pintype "output"))
    )
    (net (code "733") (name "Net-(A17G-OUT)") (class "Default")
      (node (ref "A17") (pin "K2") (pinfunction "OUT_K2") (pintype "output"))
      (node (ref "B17") (pin "E2") (pinfunction "D_E2") (pintype "input"))
    )
    (net (code "734") (name "Net-(A17I-IN1)") (class "Default")
      (node (ref "A17") (pin "L2") (pinfunction "IN1_L2") (pintype "input"))
      (node (ref "A18") (pin "S1") (pinfunction "OUT_S1") (pintype "output"))
      (node (ref "B20") (pin "K1") (pinfunction "IN1_K1") (pintype "input"))
    )
    (net (code "735") (name "Net-(A17I-IN2)") (class "Default")
      (node (ref "A17") (pin "M2") (pinfunction "IN2_M2") (pintype "input"))
      (node (ref "A17") (pin "S1") (pinfunction "OUT_S1") (pintype "output"))
    )
    (net (code "736") (name "Net-(A17I-OUT)") (class "Default")
      (node (ref "A17") (pin "N2") (pinfunction "OUT_N2") (pintype "output"))
      (node (ref "B17") (pin "J1") (pinfunction "D_J1") (pintype "input"))
    )
    (net (code "737") (name "Net-(A17K-IN1)") (class "Default")
      (node (ref "A17") (pin "P2") (pinfunction "IN1_P2") (pintype "input"))
      (node (ref "A17") (pin "V2") (pinfunction "OUT_V2") (pintype "output"))
    )
    (net (code "738") (name "Net-(A17K-OUT)") (class "Default")
      (node (ref "A17") (pin "S2") (pinfunction "OUT_S2") (pintype "output"))
      (node (ref "B18") (pin "B1") (pinfunction "C_B1") (pintype "input"))
      (node (ref "B18") (pin "D2") (pinfunction "C_D2") (pintype "input"))
      (node (ref "B18") (pin "H1") (pinfunction "C_H1") (pintype "input"))
    )
    (net (code "739") (name "Net-(A18C-OUT)") (class "Default")
      (node (ref "A18") (pin "F2") (pinfunction "OUT_F2") (pintype "output"))
      (node (ref "B20") (pin "F1") (pinfunction "IN2_F1") (pintype "input"))
    )
    (net (code "740") (name "Net-(A18F-OUT)") (class "Default")
      (node (ref "A18") (pin "K1") (pinfunction "OUT_K1") (pintype "output"))
      (node (ref "B20") (pin "H1") (pinfunction "IN3_H1") (pintype "input"))
    )
    (net (code "741") (name "Net-(A18H-OUT)") (class "Default")
      (node (ref "A18") (pin "N1") (pinfunction "OUT_N1") (pintype "output"))
      (node (ref "B20") (pin "K2") (pinfunction "IN2_K2") (pintype "input"))
    )
    (net (code "742") (name "Net-(A18I-OUT)") (class "Default")
      (node (ref "A18") (pin "N2") (pinfunction "OUT_N2") (pintype "output"))
      (node (ref "B20") (pin "L2") (pinfunction "IN3_L2") (pintype "input"))
    )
    (net (code "743") (name "Net-(A18K-OUT)") (class "Default")
      (node (ref "A18") (pin "S2") (pinfunction "OUT_S2") (pintype "output"))
      (node (ref "B20") (pin "L1") (pinfunction "IN2_L1") (pintype "input"))
    )
    (net (code "744") (name "Net-(A18N-OUT)") (class "Default")
      (node (ref "A18") (pin "V2") (pinfunction "OUT_V2") (pintype "output"))
      (node (ref "B20") (pin "M1") (pinfunction "IN3_M1") (pintype "input"))
    )
    (net (code "745") (name "Net-(A19A-OUT)") (class "Default")
      (node (ref "A19") (pin "C1") (pinfunction "OUT_C1") (pintype "output"))
      (node (ref "A19") (pin "E1") (pinfunction "IN2_E1") (pintype "input"))
    )
    (net (code "746") (name "Net-(A19B-OUT)") (class "Default")
      (node (ref "A19") (pin "F1") (pinfunction "OUT_F1") (pintype "output"))
      (node (ref "B20") (pin "E2") (pinfunction "IN2_E2") (pintype "input"))
    )
    (net (code "747") (name "Net-(A19F-IN1)") (class "Default")
      (node (ref "A19") (pin "H1") (pinfunction "IN1_H1") (pintype "input"))
      (node (ref "A19") (pin "K2") (pinfunction "OUT_K2") (pintype "output"))
    )
    (net (code "748") (name "Net-(A19F-OUT)") (class "Default")
      (node (ref "A19") (pin "K1") (pinfunction "OUT_K1") (pintype "output"))
      (node (ref "B11") (pin "B1") (pinfunction "C_B1") (pintype "input"))
      (node (ref "B11") (pin "D2") (pinfunction "C_D2") (pintype "input"))
      (node (ref "B11") (pin "H1") (pinfunction "C_H1") (pintype "input"))
    )
    (net (code "749") (name "Net-(A19H-OUT)") (class "Default")
      (node (ref "A19") (pin "M2") (pinfunction "IN2_M2") (pintype "input"))
      (node (ref "A19") (pin "N1") (pinfunction "OUT_N1") (pintype "output"))
    )
    (net (code "750") (name "Net-(A19J-IN1)") (class "Default")
      (node (ref "A19") (pin "P1") (pinfunction "IN1_P1") (pintype "input"))
      (node (ref "A19") (pin "P2") (pinfunction "IN1_P2") (pintype "input"))
      (node (ref "E12") (pin "N2") (pinfunction "OUT_N2") (pintype "output"))
    )
    (net (code "751") (name "Net-(A19K-OUT)") (class "Default")
      (node (ref "A19") (pin "S2") (pinfunction "OUT_S2") (pintype "output"))
      (node (ref "B19") (pin "H1") (pinfunction "C_H1") (pintype "input"))
      (node (ref "B19") (pin "L2") (pinfunction "C_L2") (pintype "input"))
      (node (ref "B19") (pin "N1") (pinfunction "C_N1") (pintype "input"))
      (node (ref "B19") (pin "S2") (pinfunction "C_S2") (pintype "input"))
    )
    (net (code "752") (name "Net-(A21A-IN)") (class "Default")
      (node (ref "A21") (pin "E1") (pinfunction "IN_E1") (pintype "input"))
      (node (ref "A21") (pin "L2") (pinfunction "L2_L2") (pintype "output"))
    )
    (net (code "753") (name "Net-(A21A-OUT)") (class "Default")
      (node (ref "A21") (pin "F1") (pinfunction "OUT_F1") (pintype "output"))
      (node (ref "B30") (pin "M1") (pinfunction "IN1_M1") (pintype "input"))
    )
    (net (code "754") (name "Net-(A21E-IN)") (class "Default")
      (node (ref "A21") (pin "H1") (pinfunction "IN_H1") (pintype "input"))
      (node (ref "A21") (pin "N2") (pinfunction "N2_N2") (pintype "output"))
    )
    (net (code "755") (name "Net-(A21E-OUT)") (class "Default")
      (node (ref "A21") (pin "J1") (pinfunction "OUT_J1") (pintype "output"))
      (node (ref "A22") (pin "H2") (pinfunction "H2_H2") (pintype "input"))
      (node (ref "B23") (pin "P2") (pinfunction "P_P2") (pintype "input"))
      (node (ref "B24") (pin "P2") (pinfunction "P_P2") (pintype "input"))
    )
    (net (code "756") (name "Net-(A22A-IN)") (class "Default")
      (node (ref "A22") (pin "E1") (pinfunction "IN_E1") (pintype "input"))
      (node (ref "A22") (pin "R2") (pinfunction "R2_R2") (pintype "output"))
    )
    (net (code "757") (name "Net-(A22A-OUT)") (class "Default")
      (node (ref "A22") (pin "F1") (pinfunction "OUT_F1") (pintype "output"))
      (node (ref "B22") (pin "H1") (pinfunction "C_H1") (pintype "input"))
      (node (ref "D07") (pin "M1") (pinfunction "IN2_M1") (pintype "input"))
      (node (ref "E09") (pin "E2") (pinfunction "IN2_E2") (pintype "input"))
    )
    (net (code "758") (name "Net-(A23A-IN)") (class "Default")
      (node (ref "A23") (pin "E1") (pinfunction "IN_E1") (pintype "input"))
      (node (ref "A23") (pin "M2") (pinfunction "M2_M2") (pintype "output"))
    )
    (net (code "759") (name "Net-(A23A-OUT)") (class "Default")
      (node (ref "A23") (pin "F1") (pinfunction "OUT_F1") (pintype "output"))
      (node (ref "B21") (pin "D2") (pinfunction "IN1_D2") (pintype "input"))
    )
    (net (code "760") (name "Net-(A23E-IN)") (class "Default")
      (node (ref "A23") (pin "H1") (pinfunction "IN_H1") (pintype "input"))
      (node (ref "A23") (pin "N2") (pinfunction "N2_N2") (pintype "output"))
    )
    (net (code "761") (name "Net-(A23E-OUT)") (class "Default")
      (node (ref "A23") (pin "J1") (pinfunction "OUT_J1") (pintype "output"))
      (node (ref "A24") (pin "H2") (pinfunction "H2_H2") (pintype "input"))
      (node (ref "B21") (pin "J1") (pinfunction "IN2_J1") (pintype "input"))
    )
    (net (code "762") (name "Net-(A24A-IN)") (class "Default")
      (node (ref "A24") (pin "E1") (pinfunction "IN_E1") (pintype "input"))
      (node (ref "A24") (pin "T2") (pinfunction "T2_T2") (pintype "output"))
    )
    (net (code "763") (name "Net-(A25D-P$1)") (class "Default")
      (node (ref "A25") (pin "N2") (pinfunction "P$1_N2") (pintype "passive"))
      (node (ref "A27") (pin "F2") (pinfunction "F2_F2") (pintype "passive"))
    )
    (net (code "764") (name "Net-(A25D-P$2)") (class "Default")
      (node (ref "A25") (pin "P2") (pinfunction "P$2_P2") (pintype "passive"))
      (node (ref "A27") (pin "H2") (pinfunction "H_H2") (pintype "input"))
    )
    (net (code "765") (name "Net-(A25E-P$1)") (class "Default")
      (node (ref "A25") (pin "M2") (pinfunction "P$1_M2") (pintype "passive"))
      (node (ref "A27") (pin "E1") (pinfunction "E1_E1") (pintype "passive"))
    )
    (net (code "766") (name "Net-(A25E-P$2)") (class "Default")
      (node (ref "A25") (pin "R2") (pinfunction "P$2_R2") (pintype "passive"))
      (node (ref "A27") (pin "F1") (pinfunction "H_F1") (pintype "input"))
    )
    (net (code "767") (name "Net-(A25F-P$1)") (class "Default")
      (node (ref "A25") (pin "L2") (pinfunction "P$1_L2") (pintype "passive"))
      (node (ref "A27") (pin "P2") (pinfunction "P2_P2") (pintype "passive"))
    )
    (net (code "768") (name "Net-(A25F-P$2)") (class "Default")
      (node (ref "A25") (pin "S2") (pinfunction "P$2_S2") (pintype "passive"))
      (node (ref "A27") (pin "R2") (pinfunction "H_R2") (pintype "input"))
    )
    (net (code "769") (name "Net-(A25G-P$1)") (class "Default")
      (node (ref "A25") (pin "K2") (pinfunction "P$1_K2") (pintype "passive"))
      (node (ref "A27") (pin "M1") (pinfunction "M1_M1") (pintype "passive"))
    )
    (net (code "770") (name "Net-(A25G-P$2)") (class "Default")
      (node (ref "A25") (pin "T2") (pinfunction "P$2_T2") (pintype "passive"))
      (node (ref "A27") (pin "N1") (pinfunction "H_N1") (pintype "input"))
    )
    (net (code "771") (name "Net-(A26D-P$1)") (class "Default")
      (node (ref "A26") (pin "N2") (pinfunction "P$1_N2") (pintype "passive"))
      (node (ref "B26") (pin "F2") (pinfunction "F2_F2") (pintype "passive"))
    )
    (net (code "772") (name "Net-(A26D-P$2)") (class "Default")
      (node (ref "A26") (pin "P2") (pinfunction "P$2_P2") (pintype "passive"))
      (node (ref "B26") (pin "H2") (pinfunction "H_H2") (pintype "input"))
    )
    (net (code "773") (name "Net-(A26E-P$1)") (class "Default")
      (node (ref "A26") (pin "M2") (pinfunction "P$1_M2") (pintype "passive"))
      (node (ref "B26") (pin "E1") (pinfunction "E1_E1") (pintype "passive"))
    )
    (net (code "774") (name "Net-(A26E-P$2)") (class "Default")
      (node (ref "A26") (pin "R2") (pinfunction "P$2_R2") (pintype "passive"))
      (node (ref "B26") (pin "F1") (pinfunction "H_F1") (pintype "input"))
    )
    (net (code "775") (name "Net-(A26F-P$1)") (class "Default")
      (node (ref "A26") (pin "L2") (pinfunction "P$1_L2") (pintype "passive"))
      (node (ref "B26") (pin "P2") (pinfunction "P2_P2") (pintype "passive"))
    )
    (net (code "776") (name "Net-(A26F-P$2)") (class "Default")
      (node (ref "A26") (pin "S2") (pinfunction "P$2_S2") (pintype "passive"))
      (node (ref "B26") (pin "R2") (pinfunction "H_R2") (pintype "input"))
    )
    (net (code "777") (name "Net-(A26G-P$1)") (class "Default")
      (node (ref "A26") (pin "K2") (pinfunction "P$1_K2") (pintype "passive"))
      (node (ref "B26") (pin "M1") (pinfunction "M1_M1") (pintype "passive"))
    )
    (net (code "778") (name "Net-(A26G-P$2)") (class "Default")
      (node (ref "A26") (pin "T2") (pinfunction "P$2_T2") (pintype "passive"))
      (node (ref "B26") (pin "N1") (pinfunction "H_N1") (pintype "input"))
    )
    (net (code "779") (name "Net-(A27B-J)") (class "Default")
      (node (ref "A27") (pin "H1") (pinfunction "J_H1") (pintype "passive"))
      (node (ref "AB28") (pin "BE2") (pinfunction "P$2_BE2") (pintype "passive"))
    )
    (net (code "780") (name "Net-(A27B-K)") (class "Default")
      (node (ref "A27") (pin "J1") (pinfunction "K_J1") (pintype "passive"))
      (node (ref "AB28") (pin "BF2") (pinfunction "P$2_BF2") (pintype "passive"))
    )
    (net (code "781") (name "Net-(A27D-J)") (class "Default")
      (node (ref "A27") (pin "J2") (pinfunction "J_J2") (pintype "passive"))
      (node (ref "AB28") (pin "BC2") (pinfunction "P$2_BC2") (pintype "passive"))
    )
    (net (code "782") (name "Net-(A27D-K)") (class "Default")
      (node (ref "A27") (pin "K2") (pinfunction "K_K2") (pintype "passive"))
      (node (ref "AB28") (pin "BD2") (pinfunction "P$2_BD2") (pintype "passive"))
    )
    (net (code "783") (name "Net-(A27E-J)") (class "Default")
      (node (ref "A27") (pin "P1") (pinfunction "J_P1") (pintype "passive"))
      (node (ref "AB28") (pin "BK2") (pinfunction "P$2_BK2") (pintype "passive"))
    )
    (net (code "784") (name "Net-(A27E-K)") (class "Default")
      (node (ref "A27") (pin "R1") (pinfunction "K_R1") (pintype "passive"))
      (node (ref "AB28") (pin "BL2") (pinfunction "P$2_BL2") (pintype "passive"))
    )
    (net (code "785") (name "Net-(A27F-J)") (class "Default")
      (node (ref "A27") (pin "S2") (pinfunction "J_S2") (pintype "passive"))
      (node (ref "AB28") (pin "BH2") (pinfunction "P$2_BH2") (pintype "passive"))
    )
    (net (code "786") (name "Net-(A27F-K)") (class "Default")
      (node (ref "A27") (pin "T2") (pinfunction "K_T2") (pintype "passive"))
      (node (ref "AB28") (pin "BJ2") (pinfunction "P$2_BJ2") (pintype "passive"))
    )
    (net (code "787") (name "Net-(A36B-H)") (class "Default")
      (node (ref "A36") (pin "F1") (pinfunction "H_F1") (pintype "input"))
      (node (ref "A38") (pin "R2") (pinfunction "P$2_R2") (pintype "passive"))
    )
    (net (code "788") (name "Net-(A36B-J)") (class "Default")
      (node (ref "A36") (pin "H1") (pinfunction "J_H1") (pintype "passive"))
      (node (ref "AB35") (pin "AE2") (pinfunction "P$2_AE2") (pintype "passive"))
    )
    (net (code "789") (name "Net-(A36B-K)") (class "Default")
      (node (ref "A36") (pin "J1") (pinfunction "K_J1") (pintype "passive"))
      (node (ref "AB35") (pin "AF2") (pinfunction "P$2_AF2") (pintype "passive"))
    )
    (net (code "790") (name "Net-(A36D-H)") (class "Default")
      (node (ref "A36") (pin "H2") (pinfunction "H_H2") (pintype "input"))
      (node (ref "A38") (pin "P2") (pinfunction "P$2_P2") (pintype "passive"))
    )
    (net (code "791") (name "Net-(A36D-J)") (class "Default")
      (node (ref "A36") (pin "J2") (pinfunction "J_J2") (pintype "passive"))
      (node (ref "AB35") (pin "AC2") (pinfunction "P$2_AC2") (pintype "passive"))
    )
    (net (code "792") (name "Net-(A36D-K)") (class "Default")
      (node (ref "A36") (pin "K2") (pinfunction "K_K2") (pintype "passive"))
      (node (ref "AB35") (pin "AD2") (pinfunction "P$2_AD2") (pintype "passive"))
    )
    (net (code "793") (name "Net-(A36E-H)") (class "Default")
      (node (ref "A36") (pin "N1") (pinfunction "H_N1") (pintype "input"))
      (node (ref "A38") (pin "T2") (pinfunction "P$2_T2") (pintype "passive"))
    )
    (net (code "794") (name "Net-(A36E-J)") (class "Default")
      (node (ref "A36") (pin "P1") (pinfunction "J_P1") (pintype "passive"))
      (node (ref "AB35") (pin "AK2") (pinfunction "P$2_AK2") (pintype "passive"))
    )
    (net (code "795") (name "Net-(A36E-K)") (class "Default")
      (node (ref "A36") (pin "R1") (pinfunction "K_R1") (pintype "passive"))
      (node (ref "AB35") (pin "AL2") (pinfunction "P$2_AL2") (pintype "passive"))
    )
    (net (code "796") (name "Net-(A36F-H)") (class "Default")
      (node (ref "A36") (pin "R2") (pinfunction "H_R2") (pintype "input"))
      (node (ref "A38") (pin "S2") (pinfunction "P$2_S2") (pintype "passive"))
    )
    (net (code "797") (name "Net-(A36F-J)") (class "Default")
      (node (ref "A36") (pin "S2") (pinfunction "J_S2") (pintype "passive"))
      (node (ref "AB35") (pin "AH2") (pinfunction "P$2_AH2") (pintype "passive"))
    )
    (net (code "798") (name "Net-(A36F-K)") (class "Default")
      (node (ref "A36") (pin "T2") (pinfunction "K_T2") (pintype "passive"))
      (node (ref "AB35") (pin "AJ2") (pinfunction "P$2_AJ2") (pintype "passive"))
    )
    (net (code "799") (name "Net-(A37D-H)") (class "Default")
      (node (ref "A37") (pin "H2") (pinfunction "H_H2") (pintype "input"))
      (node (ref "A39") (pin "P2") (pinfunction "P$2_P2") (pintype "passive"))
    )
    (net (code "800") (name "Net-(A37D-J)") (class "Default")
      (node (ref "A37") (pin "J2") (pinfunction "J_J2") (pintype "passive"))
      (node (ref "AB35") (pin "AS2") (pinfunction "P$2_AS2") (pintype "passive"))
    )
    (net (code "801") (name "Net-(A37D-K)") (class "Default")
      (node (ref "A37") (pin "K2") (pinfunction "K_K2") (pintype "passive"))
      (node (ref "AB35") (pin "AT2") (pinfunction "P$2_AT2") (pintype "passive"))
    )
    (net (code "802") (name "Net-(A37F-H)") (class "Default")
      (node (ref "A37") (pin "R2") (pinfunction "H_R2") (pintype "input"))
      (node (ref "A39") (pin "S2") (pinfunction "P$2_S2") (pintype "passive"))
    )
    (net (code "803") (name "Net-(A37F-J)") (class "Default")
      (node (ref "A37") (pin "S2") (pinfunction "J_S2") (pintype "passive"))
      (node (ref "AB28") (pin "AS2") (pinfunction "P$2_AS2") (pintype "passive"))
    )
    (net (code "804") (name "Net-(A37F-K)") (class "Default")
      (node (ref "A37") (pin "T2") (pinfunction "K_T2") (pintype "passive"))
      (node (ref "AB28") (pin "AT2") (pinfunction "P$2_AT2") (pintype "passive"))
    )
    (net (code "805") (name "Net-(A38D-P$1)") (class "Default")
      (node (ref "A36") (pin "F2") (pinfunction "F2_F2") (pintype "passive"))
      (node (ref "A38") (pin "N2") (pinfunction "P$1_N2") (pintype "passive"))
    )
    (net (code "806") (name "Net-(A38E-P$1)") (class "Default")
      (node (ref "A36") (pin "E1") (pinfunction "E1_E1") (pintype "passive"))
      (node (ref "A38") (pin "M2") (pinfunction "P$1_M2") (pintype "passive"))
    )
    (net (code "807") (name "Net-(A38F-P$1)") (class "Default")
      (node (ref "A36") (pin "P2") (pinfunction "P2_P2") (pintype "passive"))
      (node (ref "A38") (pin "L2") (pinfunction "P$1_L2") (pintype "passive"))
    )
    (net (code "808") (name "Net-(A38G-P$1)") (class "Default")
      (node (ref "A36") (pin "M1") (pinfunction "M1_M1") (pintype "passive"))
      (node (ref "A38") (pin "K2") (pinfunction "P$1_K2") (pintype "passive"))
    )
    (net (code "809") (name "Net-(A38H-P$1)") (class "Default")
      (node (ref "A38") (pin "F2") (pinfunction "P$1_F2") (pintype "passive"))
      (node (ref "C39") (pin "U2") (pinfunction "U2_U2") (pintype "passive"))
      (node (ref "D39") (pin "U2") (pinfunction "U2_U2") (pintype "passive"))
    )
    (net (code "810") (name "Net-(A39D-P$1)") (class "Default")
      (node (ref "A37") (pin "F2") (pinfunction "F2_F2") (pintype "passive"))
      (node (ref "A39") (pin "N2") (pinfunction "P$1_N2") (pintype "passive"))
    )
    (net (code "811") (name "Net-(A39F-P$1)") (class "Default")
      (node (ref "A37") (pin "P2") (pinfunction "P2_P2") (pintype "passive"))
      (node (ref "A39") (pin "L2") (pinfunction "P$1_L2") (pintype "passive"))
    )
    (net (code "812") (name "Net-(A39H-P$1)") (class "Default")
      (node (ref "A39") (pin "F2") (pinfunction "P$1_F2") (pintype "passive"))
      (node (ref "C39") (pin "L2") (pinfunction "L2_L2") (pintype "passive"))
      (node (ref "D39") (pin "L2") (pinfunction "L2_L2") (pintype "passive"))
    )
    (net (code "813") (name "Net-(AB01-PadAV2)") (class "Default")
      (node (ref "AB01") (pin "AV2") (pinfunction "AV2_AV2") (pintype "input"))
      (node (ref "AB02") (pin "BJ2") (pinfunction "BJ2_BJ2") (pintype "output"))
      (node (ref "AB02") (pin "BK2") (pinfunction "BK2_BK2") (pintype "passive"))
    )
    (net (code "814") (name "Net-(AB28AC-P$2)") (class "Default")
      (node (ref "AB28") (pin "BM2") (pinfunction "P$2_BM2") (pintype "passive"))
      (node (ref "B26") (pin "J2") (pinfunction "J_J2") (pintype "passive"))
    )
    (net (code "815") (name "Net-(AB28AD-P$2)") (class "Default")
      (node (ref "AB28") (pin "BN2") (pinfunction "P$2_BN2") (pintype "passive"))
      (node (ref "B26") (pin "K2") (pinfunction "K_K2") (pintype "passive"))
    )
    (net (code "816") (name "Net-(AB28AE-P$2)") (class "Default")
      (node (ref "AB28") (pin "BP2") (pinfunction "P$2_BP2") (pintype "passive"))
      (node (ref "B26") (pin "H1") (pinfunction "J_H1") (pintype "passive"))
    )
    (net (code "817") (name "Net-(AB28AF-P$2)") (class "Default")
      (node (ref "AB28") (pin "BR2") (pinfunction "P$2_BR2") (pintype "passive"))
      (node (ref "B26") (pin "J1") (pinfunction "K_J1") (pintype "passive"))
    )
    (net (code "818") (name "Net-(AB28C-P$2)") (class "Default")
      (node (ref "AB28") (pin "AC2") (pinfunction "P$2_AC2") (pintype "passive"))
      (node (ref "B26") (pin "S2") (pinfunction "J_S2") (pintype "passive"))
    )
    (net (code "819") (name "Net-(AB28D-P$2)") (class "Default")
      (node (ref "AB28") (pin "AD2") (pinfunction "P$2_AD2") (pintype "passive"))
      (node (ref "B26") (pin "T2") (pinfunction "K_T2") (pintype "passive"))
    )
    (net (code "820") (name "Net-(AB28E-P$2)") (class "Default")
      (node (ref "AB28") (pin "AE2") (pinfunction "P$2_AE2") (pintype "passive"))
      (node (ref "B26") (pin "P1") (pinfunction "J_P1") (pintype "passive"))
    )
    (net (code "821") (name "Net-(AB28F-P$2)") (class "Default")
      (node (ref "AB28") (pin "AF2") (pinfunction "P$2_AF2") (pintype "passive"))
      (node (ref "B26") (pin "R1") (pinfunction "K_R1") (pintype "passive"))
    )
    (net (code "822") (name "Net-(AB28G-P$2)") (class "Default")
      (node (ref "AB28") (pin "AH2") (pinfunction "P$2_AH2") (pintype "passive"))
      (node (ref "B27") (pin "J2") (pinfunction "J_J2") (pintype "passive"))
    )
    (net (code "823") (name "Net-(AB28H-P$2)") (class "Default")
      (node (ref "AB28") (pin "AJ2") (pinfunction "P$2_AJ2") (pintype "passive"))
      (node (ref "B27") (pin "K2") (pinfunction "K_K2") (pintype "passive"))
    )
    (net (code "824") (name "Net-(AB28I-P$2)") (class "Default")
      (node (ref "AB28") (pin "AK2") (pinfunction "P$2_AK2") (pintype "passive"))
      (node (ref "B27") (pin "H1") (pinfunction "J_H1") (pintype "passive"))
    )
    (net (code "825") (name "Net-(AB28J-P$2)") (class "Default")
      (node (ref "AB28") (pin "AL2") (pinfunction "P$2_AL2") (pintype "passive"))
      (node (ref "B27") (pin "J1") (pinfunction "K_J1") (pintype "passive"))
    )
    (net (code "826") (name "Net-(AB28K-P$2)") (class "Default")
      (node (ref "AB28") (pin "AM2") (pinfunction "P$2_AM2") (pintype "passive"))
      (node (ref "B27") (pin "S2") (pinfunction "J_S2") (pintype "passive"))
    )
    (net (code "827") (name "Net-(AB28L-P$2)") (class "Default")
      (node (ref "AB28") (pin "AN2") (pinfunction "P$2_AN2") (pintype "passive"))
      (node (ref "B27") (pin "T2") (pinfunction "K_T2") (pintype "passive"))
    )
    (net (code "828") (name "Net-(AB28M-P$2)") (class "Default")
      (node (ref "AB28") (pin "AP2") (pinfunction "P$2_AP2") (pintype "passive"))
      (node (ref "B27") (pin "P1") (pinfunction "J_P1") (pintype "passive"))
    )
    (net (code "829") (name "Net-(AB28N-P$2)") (class "Default")
      (node (ref "AB28") (pin "AR2") (pinfunction "P$2_AR2") (pintype "passive"))
      (node (ref "B27") (pin "R1") (pinfunction "K_R1") (pintype "passive"))
    )
    (net (code "830") (name "Net-(AB29AA-P$2)") (class "Default")
      (node (ref "AB29") (pin "BK2") (pinfunction "P$2_BK2") (pintype "passive"))
      (node (ref "B32") (pin "N1") (pinfunction "N1_N1") (pintype "input"))
    )
    (net (code "831") (name "Net-(AB29AB-P$2)") (class "Default")
      (node (ref "AB29") (pin "BL2") (pinfunction "P$2_BL2") (pintype "passive"))
      (node (ref "B32") (pin "P1") (pinfunction "P1_P1") (pintype "input"))
    )
    (net (code "832") (name "Net-(AB29AC-P$2)") (class "Default")
      (node (ref "AB29") (pin "BM2") (pinfunction "P$2_BM2") (pintype "passive"))
      (node (ref "B33") (pin "F2") (pinfunction "F2_F2") (pintype "input"))
    )
    (net (code "833") (name "Net-(AB29AD-P$2)") (class "Default")
      (node (ref "AB29") (pin "BN2") (pinfunction "P$2_BN2") (pintype "passive"))
      (node (ref "B33") (pin "H2") (pinfunction "H2_H2") (pintype "input"))
    )
    (net (code "834") (name "Net-(AB29AE-P$2)") (class "Default")
      (node (ref "AB29") (pin "BP2") (pinfunction "P$2_BP2") (pintype "passive"))
      (node (ref "B33") (pin "N1") (pinfunction "N1_N1") (pintype "input"))
    )
    (net (code "835") (name "Net-(AB29AF-P$2)") (class "Default")
      (node (ref "AB29") (pin "BR2") (pinfunction "P$2_BR2") (pintype "passive"))
      (node (ref "B33") (pin "P1") (pinfunction "P1_P1") (pintype "input"))
    )
    (net (code "836") (name "Net-(AB29C-P$2)") (class "Default")
      (node (ref "A31") (pin "F2") (pinfunction "F2_F2") (pintype "input"))
      (node (ref "AB29") (pin "AC2") (pinfunction "P$2_AC2") (pintype "passive"))
    )
    (net (code "837") (name "Net-(AB29D-P$2)") (class "Default")
      (node (ref "A31") (pin "H2") (pinfunction "H2_H2") (pintype "input"))
      (node (ref "AB29") (pin "AD2") (pinfunction "P$2_AD2") (pintype "passive"))
    )
    (net (code "838") (name "Net-(AB29E-P$2)") (class "Default")
      (node (ref "A31") (pin "N1") (pinfunction "N1_N1") (pintype "input"))
      (node (ref "AB29") (pin "AE2") (pinfunction "P$2_AE2") (pintype "passive"))
    )
    (net (code "839") (name "Net-(AB29F-P$2)") (class "Default")
      (node (ref "A31") (pin "P1") (pinfunction "P1_P1") (pintype "input"))
      (node (ref "AB29") (pin "AF2") (pinfunction "P$2_AF2") (pintype "passive"))
    )
    (net (code "840") (name "Net-(AB29G-P$2)") (class "Default")
      (node (ref "A32") (pin "F2") (pinfunction "F2_F2") (pintype "input"))
      (node (ref "AB29") (pin "AH2") (pinfunction "P$2_AH2") (pintype "passive"))
    )
    (net (code "841") (name "Net-(AB29H-P$2)") (class "Default")
      (node (ref "A32") (pin "H2") (pinfunction "H2_H2") (pintype "input"))
      (node (ref "AB29") (pin "AJ2") (pinfunction "P$2_AJ2") (pintype "passive"))
    )
    (net (code "842") (name "Net-(AB29I-P$2)") (class "Default")
      (node (ref "A32") (pin "N1") (pinfunction "N1_N1") (pintype "input"))
      (node (ref "AB29") (pin "AK2") (pinfunction "P$2_AK2") (pintype "passive"))
    )
    (net (code "843") (name "Net-(AB29J-P$2)") (class "Default")
      (node (ref "A32") (pin "P1") (pinfunction "P1_P1") (pintype "input"))
      (node (ref "AB29") (pin "AL2") (pinfunction "P$2_AL2") (pintype "passive"))
    )
    (net (code "844") (name "Net-(AB29K-P$2)") (class "Default")
      (node (ref "A33") (pin "F2") (pinfunction "F2_F2") (pintype "input"))
      (node (ref "AB29") (pin "AM2") (pinfunction "P$2_AM2") (pintype "passive"))
    )
    (net (code "845") (name "Net-(AB29L-P$2)") (class "Default")
      (node (ref "A33") (pin "H2") (pinfunction "H2_H2") (pintype "input"))
      (node (ref "AB29") (pin "AN2") (pinfunction "P$2_AN2") (pintype "passive"))
    )
    (net (code "846") (name "Net-(AB29M-P$2)") (class "Default")
      (node (ref "A33") (pin "N1") (pinfunction "N1_N1") (pintype "input"))
      (node (ref "AB29") (pin "AP2") (pinfunction "P$2_AP2") (pintype "passive"))
    )
    (net (code "847") (name "Net-(AB29N-P$2)") (class "Default")
      (node (ref "A33") (pin "P1") (pinfunction "P1_P1") (pintype "input"))
      (node (ref "AB29") (pin "AR2") (pinfunction "P$2_AR2") (pintype "passive"))
    )
    (net (code "848") (name "Net-(AB29O-P$2)") (class "Default")
      (node (ref "A30") (pin "L1") (pinfunction "L1_L1") (pintype "input"))
      (node (ref "AB29") (pin "AS2") (pinfunction "P$2_AS2") (pintype "passive"))
    )
    (net (code "849") (name "Net-(AB29P-P$2)") (class "Default")
      (node (ref "A30") (pin "M1") (pinfunction "M1_M1") (pintype "input"))
      (node (ref "AB29") (pin "AT2") (pinfunction "P$2_AT2") (pintype "passive"))
    )
    (net (code "850") (name "Net-(AB29U-P$2)") (class "Default")
      (node (ref "AB29") (pin "BC2") (pinfunction "P$2_BC2") (pintype "passive"))
      (node (ref "B31") (pin "F2") (pinfunction "F2_F2") (pintype "input"))
    )
    (net (code "851") (name "Net-(AB29V-P$2)") (class "Default")
      (node (ref "AB29") (pin "BD2") (pinfunction "P$2_BD2") (pintype "passive"))
      (node (ref "B31") (pin "H2") (pinfunction "H2_H2") (pintype "input"))
    )
    (net (code "852") (name "Net-(AB29W-P$2)") (class "Default")
      (node (ref "AB29") (pin "BE2") (pinfunction "P$2_BE2") (pintype "passive"))
      (node (ref "B31") (pin "N1") (pinfunction "N1_N1") (pintype "input"))
    )
    (net (code "853") (name "Net-(AB29X-P$2)") (class "Default")
      (node (ref "AB29") (pin "BF2") (pinfunction "P$2_BF2") (pintype "passive"))
      (node (ref "B31") (pin "P1") (pinfunction "P1_P1") (pintype "input"))
    )
    (net (code "854") (name "Net-(AB29Y-P$2)") (class "Default")
      (node (ref "AB29") (pin "BH2") (pinfunction "P$2_BH2") (pintype "passive"))
      (node (ref "B32") (pin "F2") (pinfunction "F2_F2") (pintype "input"))
    )
    (net (code "855") (name "Net-(AB29Z-P$2)") (class "Default")
      (node (ref "AB29") (pin "BJ2") (pinfunction "P$2_BJ2") (pintype "passive"))
      (node (ref "B32") (pin "H2") (pinfunction "H2_H2") (pintype "input"))
    )
    (net (code "856") (name "Net-(AB34AA-P$2)") (class "Default")
      (node (ref "AB34") (pin "BK2") (pinfunction "P$2_BK2") (pintype "passive"))
      (node (ref "B32") (pin "L1") (pinfunction "L1_L1") (pintype "input"))
    )
    (net (code "857") (name "Net-(AB34AB-P$2)") (class "Default")
      (node (ref "AB34") (pin "BL2") (pinfunction "P$2_BL2") (pintype "passive"))
      (node (ref "B32") (pin "M1") (pinfunction "M1_M1") (pintype "input"))
    )
    (net (code "858") (name "Net-(AB34AC-P$2)") (class "Default")
      (node (ref "AB34") (pin "BM2") (pinfunction "P$2_BM2") (pintype "passive"))
      (node (ref "B33") (pin "D2") (pinfunction "D2_D2") (pintype "input"))
    )
    (net (code "859") (name "Net-(AB34AD-P$2)") (class "Default")
      (node (ref "AB34") (pin "BN2") (pinfunction "P$2_BN2") (pintype "passive"))
      (node (ref "B33") (pin "E2") (pinfunction "E2_E2") (pintype "input"))
    )
    (net (code "860") (name "Net-(AB34AE-P$2)") (class "Default")
      (node (ref "AB34") (pin "BP2") (pinfunction "P$2_BP2") (pintype "passive"))
      (node (ref "B33") (pin "L1") (pinfunction "L1_L1") (pintype "input"))
    )
    (net (code "861") (name "Net-(AB34AF-P$2)") (class "Default")
      (node (ref "AB34") (pin "BR2") (pinfunction "P$2_BR2") (pintype "passive"))
      (node (ref "B33") (pin "M1") (pinfunction "M1_M1") (pintype "input"))
    )
    (net (code "862") (name "Net-(AB34C-P$2)") (class "Default")
      (node (ref "A31") (pin "D2") (pinfunction "D2_D2") (pintype "input"))
      (node (ref "AB34") (pin "AC2") (pinfunction "P$2_AC2") (pintype "passive"))
    )
    (net (code "863") (name "Net-(AB34D-P$2)") (class "Default")
      (node (ref "A31") (pin "E2") (pinfunction "E2_E2") (pintype "input"))
      (node (ref "AB34") (pin "AD2") (pinfunction "P$2_AD2") (pintype "passive"))
    )
    (net (code "864") (name "Net-(AB34E-P$2)") (class "Default")
      (node (ref "A31") (pin "L1") (pinfunction "L1_L1") (pintype "input"))
      (node (ref "AB34") (pin "AE2") (pinfunction "P$2_AE2") (pintype "passive"))
    )
    (net (code "865") (name "Net-(AB34F-P$2)") (class "Default")
      (node (ref "A31") (pin "M1") (pinfunction "M1_M1") (pintype "input"))
      (node (ref "AB34") (pin "AF2") (pinfunction "P$2_AF2") (pintype "passive"))
    )
    (net (code "866") (name "Net-(AB34G-P$2)") (class "Default")
      (node (ref "A32") (pin "D2") (pinfunction "D2_D2") (pintype "input"))
      (node (ref "AB34") (pin "AH2") (pinfunction "P$2_AH2") (pintype "passive"))
    )
    (net (code "867") (name "Net-(AB34H-P$2)") (class "Default")
      (node (ref "A32") (pin "E2") (pinfunction "E2_E2") (pintype "input"))
      (node (ref "AB34") (pin "AJ2") (pinfunction "P$2_AJ2") (pintype "passive"))
    )
    (net (code "868") (name "Net-(AB34I-P$2)") (class "Default")
      (node (ref "A32") (pin "L1") (pinfunction "L1_L1") (pintype "input"))
      (node (ref "AB34") (pin "AK2") (pinfunction "P$2_AK2") (pintype "passive"))
    )
    (net (code "869") (name "Net-(AB34J-P$2)") (class "Default")
      (node (ref "A32") (pin "M1") (pinfunction "M1_M1") (pintype "input"))
      (node (ref "AB34") (pin "AL2") (pinfunction "P$2_AL2") (pintype "passive"))
    )
    (net (code "870") (name "Net-(AB34K-P$2)") (class "Default")
      (node (ref "A33") (pin "D2") (pinfunction "D2_D2") (pintype "input"))
      (node (ref "AB34") (pin "AM2") (pinfunction "P$2_AM2") (pintype "passive"))
    )
    (net (code "871") (name "Net-(AB34L-P$2)") (class "Default")
      (node (ref "A33") (pin "E2") (pinfunction "E2_E2") (pintype "input"))
      (node (ref "AB34") (pin "AN2") (pinfunction "P$2_AN2") (pintype "passive"))
    )
    (net (code "872") (name "Net-(AB34M-P$2)") (class "Default")
      (node (ref "A33") (pin "L1") (pinfunction "L1_L1") (pintype "input"))
      (node (ref "AB34") (pin "AP2") (pinfunction "P$2_AP2") (pintype "passive"))
    )
    (net (code "873") (name "Net-(AB34N-P$2)") (class "Default")
      (node (ref "A33") (pin "M1") (pinfunction "M1_M1") (pintype "input"))
      (node (ref "AB34") (pin "AR2") (pinfunction "P$2_AR2") (pintype "passive"))
    )
    (net (code "874") (name "Net-(AB34O-P$2)") (class "Default")
      (node (ref "A30") (pin "D2") (pinfunction "D2_D2") (pintype "input"))
      (node (ref "AB34") (pin "AS2") (pinfunction "P$2_AS2") (pintype "passive"))
    )
    (net (code "875") (name "Net-(AB34P-P$2)") (class "Default")
      (node (ref "A30") (pin "E2") (pinfunction "E2_E2") (pintype "input"))
      (node (ref "AB34") (pin "AT2") (pinfunction "P$2_AT2") (pintype "passive"))
    )
    (net (code "876") (name "Net-(AB34U-P$2)") (class "Default")
      (node (ref "AB34") (pin "BC2") (pinfunction "P$2_BC2") (pintype "passive"))
      (node (ref "B31") (pin "D2") (pinfunction "D2_D2") (pintype "input"))
    )
    (net (code "877") (name "Net-(AB34V-P$2)") (class "Default")
      (node (ref "AB34") (pin "BD2") (pinfunction "P$2_BD2") (pintype "passive"))
      (node (ref "B31") (pin "E2") (pinfunction "E2_E2") (pintype "input"))
    )
    (net (code "878") (name "Net-(AB34W-P$2)") (class "Default")
      (node (ref "AB34") (pin "BE2") (pinfunction "P$2_BE2") (pintype "passive"))
      (node (ref "B31") (pin "L1") (pinfunction "L1_L1") (pintype "input"))
    )
    (net (code "879") (name "Net-(AB34X-P$2)") (class "Default")
      (node (ref "AB34") (pin "BF2") (pinfunction "P$2_BF2") (pintype "passive"))
      (node (ref "B31") (pin "M1") (pinfunction "M1_M1") (pintype "input"))
    )
    (net (code "880") (name "Net-(AB34Y-P$2)") (class "Default")
      (node (ref "AB34") (pin "BH2") (pinfunction "P$2_BH2") (pintype "passive"))
      (node (ref "B32") (pin "D2") (pinfunction "D2_D2") (pintype "input"))
    )
    (net (code "881") (name "Net-(AB34Z-P$2)") (class "Default")
      (node (ref "AB34") (pin "BJ2") (pinfunction "P$2_BJ2") (pintype "passive"))
      (node (ref "B32") (pin "E2") (pinfunction "E2_E2") (pintype "input"))
    )
    (net (code "882") (name "Net-(AB35AA-P$2)") (class "Default")
      (node (ref "AB35") (pin "BK2") (pinfunction "P$2_BK2") (pintype "passive"))
      (node (ref "B37") (pin "H1") (pinfunction "J_H1") (pintype "passive"))
    )
    (net (code "883") (name "Net-(AB35AB-P$2)") (class "Default")
      (node (ref "AB35") (pin "BL2") (pinfunction "P$2_BL2") (pintype "passive"))
      (node (ref "B37") (pin "J1") (pinfunction "K_J1") (pintype "passive"))
    )
    (net (code "884") (name "Net-(AB35AC-P$2)") (class "Default")
      (node (ref "AB35") (pin "BM2") (pinfunction "P$2_BM2") (pintype "passive"))
      (node (ref "B37") (pin "S2") (pinfunction "J_S2") (pintype "passive"))
    )
    (net (code "885") (name "Net-(AB35AD-P$2)") (class "Default")
      (node (ref "AB35") (pin "BN2") (pinfunction "P$2_BN2") (pintype "passive"))
      (node (ref "B37") (pin "T2") (pinfunction "K_T2") (pintype "passive"))
    )
    (net (code "886") (name "Net-(AB35AE-P$2)") (class "Default")
      (node (ref "AB35") (pin "BP2") (pinfunction "P$2_BP2") (pintype "passive"))
      (node (ref "B37") (pin "P1") (pinfunction "J_P1") (pintype "passive"))
    )
    (net (code "887") (name "Net-(AB35AF-P$2)") (class "Default")
      (node (ref "AB35") (pin "BR2") (pinfunction "P$2_BR2") (pintype "passive"))
      (node (ref "B37") (pin "R1") (pinfunction "K_R1") (pintype "passive"))
    )
    (net (code "888") (name "Net-(AB35AG-P$2)") (class "Default")
      (node (ref "AB02") (pin "BR2") (pinfunction "BR2_BR2") (pintype "passive"))
      (node (ref "AB35") (pin "BS2") (pinfunction "P$2_BS2") (pintype "passive"))
    )
    (net (code "889") (name "Net-(AB35AH-P$2)") (class "Default")
      (node (ref "AB02") (pin "BS2") (pinfunction "BS2_BS2") (pintype "passive"))
      (node (ref "AB35") (pin "BT2") (pinfunction "P$2_BT2") (pintype "passive"))
    )
    (net (code "890") (name "Net-(AB35K-P$2)") (class "Default")
      (node (ref "AB35") (pin "AM2") (pinfunction "P$2_AM2") (pintype "passive"))
      (node (ref "B36") (pin "J2") (pinfunction "J_J2") (pintype "passive"))
    )
    (net (code "891") (name "Net-(AB35L-P$2)") (class "Default")
      (node (ref "AB35") (pin "AN2") (pinfunction "P$2_AN2") (pintype "passive"))
      (node (ref "B36") (pin "K2") (pinfunction "K_K2") (pintype "passive"))
    )
    (net (code "892") (name "Net-(AB35M-P$2)") (class "Default")
      (node (ref "AB35") (pin "AP2") (pinfunction "P$2_AP2") (pintype "passive"))
      (node (ref "B36") (pin "H1") (pinfunction "J_H1") (pintype "passive"))
    )
    (net (code "893") (name "Net-(AB35N-P$2)") (class "Default")
      (node (ref "AB35") (pin "AR2") (pinfunction "P$2_AR2") (pintype "passive"))
      (node (ref "B36") (pin "J1") (pinfunction "K_J1") (pintype "passive"))
    )
    (net (code "894") (name "Net-(AB35U-P$2)") (class "Default")
      (node (ref "AB35") (pin "BC2") (pinfunction "P$2_BC2") (pintype "passive"))
      (node (ref "B36") (pin "S2") (pinfunction "J_S2") (pintype "passive"))
    )
    (net (code "895") (name "Net-(AB35V-P$2)") (class "Default")
      (node (ref "AB35") (pin "BD2") (pinfunction "P$2_BD2") (pintype "passive"))
      (node (ref "B36") (pin "T2") (pinfunction "K_T2") (pintype "passive"))
    )
    (net (code "896") (name "Net-(AB35W-P$2)") (class "Default")
      (node (ref "AB35") (pin "BE2") (pinfunction "P$2_BE2") (pintype "passive"))
      (node (ref "B36") (pin "P1") (pinfunction "J_P1") (pintype "passive"))
    )
    (net (code "897") (name "Net-(AB35X-P$2)") (class "Default")
      (node (ref "AB35") (pin "BF2") (pinfunction "P$2_BF2") (pintype "passive"))
      (node (ref "B36") (pin "R1") (pinfunction "K_R1") (pintype "passive"))
    )
    (net (code "898") (name "Net-(AB35Y-P$2)") (class "Default")
      (node (ref "AB35") (pin "BH2") (pinfunction "P$2_BH2") (pintype "passive"))
      (node (ref "B37") (pin "J2") (pinfunction "J_J2") (pintype "passive"))
    )
    (net (code "899") (name "Net-(AB35Z-P$2)") (class "Default")
      (node (ref "AB35") (pin "BJ2") (pinfunction "P$2_BJ2") (pintype "passive"))
      (node (ref "B37") (pin "K2") (pinfunction "K_K2") (pintype "passive"))
    )
    (net (code "900") (name "Net-(B04F-OUT)") (class "Default")
      (node (ref "B04") (pin "M2") (pinfunction "OUT_M2") (pintype "output"))
      (node (ref "B05") (pin "U2") (pinfunction "S_U2") (pintype "input"))
    )
    (net (code "901") (name "Net-(B04G-OUT)") (class "Default")
      (node (ref "B04") (pin "N1") (pinfunction "OUT_N1") (pintype "output"))
      (node (ref "B05") (pin "S2") (pinfunction "C_S2") (pintype "input"))
    )
    (net (code "902") (name "Net-(B04I-IN3)") (class "Default")
      (node (ref "B04") (pin "S1") (pinfunction "IN3_S1") (pintype "input"))
      (node (ref "B05") (pin "R2") (pinfunction "0_R2") (pintype "output"))
    )
    (net (code "903") (name "Net-(B05A-C)") (class "Default")
      (node (ref "B05") (pin "B1") (pinfunction "C_B1") (pintype "input"))
      (node (ref "B06") (pin "K1") (pinfunction "OUT_K1") (pintype "output"))
    )
    (net (code "904") (name "Net-(B05A-D)") (class "Default")
      (node (ref "B05") (pin "C1") (pinfunction "D_C1") (pintype "input"))
      (node (ref "B06") (pin "N2") (pinfunction "OUT_N2") (pintype "output"))
    )
    (net (code "905") (name "Net-(B05D-D)") (class "Default")
      (node (ref "B05") (pin "E2") (pinfunction "D_E2") (pintype "input"))
      (node (ref "B06") (pin "V2") (pinfunction "OUT_V2") (pintype "output"))
    )
    (net (code "906") (name "Net-(B06B-OUT)") (class "Default")
      (node (ref "B06") (pin "E2") (pinfunction "IN2_E2") (pintype "input"))
      (node (ref "B06") (pin "F1") (pinfunction "OUT_F1") (pintype "output"))
    )
    (net (code "907") (name "Net-(B06C-OUT)") (class "Default")
      (node (ref "B06") (pin "F2") (pinfunction "OUT_F2") (pintype "output"))
      (node (ref "B06") (pin "J1") (pinfunction "IN2_J1") (pintype "input"))
    )
    (net (code "908") (name "Net-(B06H-OUT)") (class "Default")
      (node (ref "B06") (pin "L2") (pinfunction "IN1_L2") (pintype "input"))
      (node (ref "B06") (pin "N1") (pinfunction "OUT_N1") (pintype "output"))
    )
    (net (code "909") (name "Net-(B06I-IN2)") (class "Default")
      (node (ref "B06") (pin "M2") (pinfunction "IN2_M2") (pintype "input"))
      (node (ref "B06") (pin "S1") (pinfunction "OUT_S1") (pintype "output"))
    )
    (net (code "910") (name "Net-(B06K-OUT)") (class "Default")
      (node (ref "B06") (pin "S2") (pinfunction "OUT_S2") (pintype "output"))
      (node (ref "B06") (pin "T2") (pinfunction "IN1_T2") (pintype "input"))
    )
    (net (code "911") (name "Net-(B07A-OUT)") (class "Default")
      (node (ref "B07") (pin "D1") (pinfunction "OUT_D1") (pintype "output"))
      (node (ref "B09") (pin "H1") (pinfunction "IN1_H1") (pintype "input"))
    )
    (net (code "912") (name "Net-(B07D-OUT)") (class "Default")
      (node (ref "B07") (pin "H2") (pinfunction "OUT_H2") (pintype "output"))
      (node (ref "B09") (pin "J2") (pinfunction "IN2_J2") (pintype "input"))
    )
    (net (code "913") (name "Net-(B07E-IN3)") (class "Default")
      (node (ref "B07") (pin "H1") (pinfunction "IN3_H1") (pintype "input"))
      (node (ref "B07") (pin "J2") (pinfunction "IN1_J2") (pintype "input"))
      (node (ref "B09") (pin "N2") (pinfunction "OUT_N2") (pintype "output"))
    )
    (net (code "914") (name "Net-(B07E-OUT)") (class "Default")
      (node (ref "B07") (pin "J1") (pinfunction "OUT_J1") (pintype "output"))
      (node (ref "B07") (pin "M1") (pinfunction "IN3_M1") (pintype "input"))
    )
    (net (code "915") (name "Net-(B07G-OUT)") (class "Default")
      (node (ref "B07") (pin "N1") (pinfunction "OUT_N1") (pintype "output"))
      (node (ref "B07") (pin "N2") (pinfunction "IN1_N2") (pintype "input"))
    )
    (net (code "916") (name "Net-(B09F-OUT)") (class "Default")
      (node (ref "B09") (pin "K1") (pinfunction "OUT_K1") (pintype "output"))
      (node (ref "B09") (pin "L1") (pinfunction "IN1_L1") (pintype "input"))
    )
    (net (code "917") (name "Net-(B09G-OUT)") (class "Default")
      (node (ref "B09") (pin "K2") (pinfunction "OUT_K2") (pintype "output"))
      (node (ref "B09") (pin "M1") (pinfunction "IN2_M1") (pintype "input"))
    )
    (net (code "918") (name "Net-(B09H-OUT)") (class "Default")
      (node (ref "B09") (pin "L2") (pinfunction "IN1_L2") (pintype "input"))
      (node (ref "B09") (pin "N1") (pinfunction "OUT_N1") (pintype "output"))
    )
    (net (code "919") (name "Net-(B09K-IN2)") (class "Default")
      (node (ref "B09") (pin "R2") (pinfunction "IN2_R2") (pintype "input"))
      (node (ref "B09") (pin "V2") (pinfunction "OUT_V2") (pintype "output"))
    )
    (net (code "920") (name "Net-(B17F-D)") (class "Default")
      (node (ref "B17") (pin "M2") (pinfunction "D_M2") (pintype "input"))
      (node (ref "B20") (pin "J1") (pinfunction "OUT_J1") (pintype "output"))
    )
    (net (code "921") (name "Net-(B17G-D)") (class "Default")
      (node (ref "B17") (pin "P1") (pinfunction "D_P1") (pintype "input"))
      (node (ref "B20") (pin "M2") (pinfunction "OUT_M2") (pintype "output"))
    )
    (net (code "922") (name "Net-(B17H-D)") (class "Default")
      (node (ref "B17") (pin "T2") (pinfunction "D_T2") (pintype "input"))
      (node (ref "B20") (pin "N1") (pinfunction "OUT_N1") (pintype "output"))
    )
    (net (code "923") (name "Net-(B18A-D)") (class "Default")
      (node (ref "B18") (pin "C1") (pinfunction "D_C1") (pintype "input"))
      (node (ref "B20") (pin "S2") (pinfunction "OUT_S2") (pintype "output"))
    )
    (net (code "924") (name "Net-(B18D-D)") (class "Default")
      (node (ref "B18") (pin "E2") (pinfunction "D_E2") (pintype "input"))
      (node (ref "B20") (pin "U1") (pinfunction "OUT_U1") (pintype "output"))
    )
    (net (code "925") (name "Net-(B18E-D)") (class "Default")
      (node (ref "B18") (pin "J1") (pinfunction "D_J1") (pintype "input"))
      (node (ref "B20") (pin "V1") (pinfunction "OUT_V1") (pintype "output"))
    )
    (net (code "926") (name "Net-(B21A-IN1)") (class "Default")
      (node (ref "B21") (pin "A1") (pinfunction "IN1_A1") (pintype "input"))
      (node (ref "B21") (pin "F1") (pinfunction "OUT_F1") (pintype "output"))
    )
    (net (code "927") (name "Net-(B21A-OUT)") (class "Default")
      (node (ref "A21") (pin "H2") (pinfunction "H2_H2") (pintype "input"))
      (node (ref "B21") (pin "C1") (pinfunction "OUT_C1") (pintype "output"))
      (node (ref "B22") (pin "D2") (pinfunction "C_D2") (pintype "input"))
    )
    (net (code "928") (name "Net-(B21B-IN1)") (class "Default")
      (node (ref "B21") (pin "D1") (pinfunction "IN1_D1") (pintype "input"))
      (node (ref "B21") (pin "K2") (pinfunction "OUT_K2") (pintype "output"))
      (node (ref "B22") (pin "C1") (pinfunction "D_C1") (pintype "input"))
    )
    (net (code "929") (name "Net-(B21C-OUT)") (class "Default")
      (node (ref "B21") (pin "F2") (pinfunction "OUT_F2") (pintype "output"))
      (node (ref "B22") (pin "N2") (pinfunction "S_N2") (pintype "input"))
    )
    (net (code "930") (name "Net-(B21F-OUT)") (class "Default")
      (node (ref "B21") (pin "K1") (pinfunction "OUT_K1") (pintype "output"))
      (node (ref "B22") (pin "R1") (pinfunction "S_R1") (pintype "input"))
    )
    (net (code "931") (name "Net-(B21G-IN1)") (class "Default")
      (node (ref "B21") (pin "H2") (pinfunction "IN1_H2") (pintype "input"))
      (node (ref "B21") (pin "N1") (pinfunction "OUT_N1") (pintype "output"))
    )
    (net (code "932") (name "Net-(B21N-OUT)") (class "Default")
      (node (ref "B21") (pin "V2") (pinfunction "OUT_V2") (pintype "output"))
      (node (ref "C12") (pin "M1") (pinfunction "IN1_M1") (pintype "input"))
      (node (ref "C12") (pin "N1") (pinfunction "IN2_N1") (pintype "input"))
      (node (ref "C12") (pin "P1") (pinfunction "IN3_P1") (pintype "input"))
      (node (ref "C12") (pin "R1") (pinfunction "IN4_R1") (pintype "input"))
    )
    (net (code "933") (name "Net-(B25D-P$1)") (class "Default")
      (node (ref "B25") (pin "N2") (pinfunction "P$1_N2") (pintype "passive"))
      (node (ref "B27") (pin "F2") (pinfunction "F2_F2") (pintype "passive"))
    )
    (net (code "934") (name "Net-(B25D-P$2)") (class "Default")
      (node (ref "B25") (pin "P2") (pinfunction "P$2_P2") (pintype "passive"))
      (node (ref "B27") (pin "H2") (pinfunction "H_H2") (pintype "input"))
    )
    (net (code "935") (name "Net-(B25E-P$1)") (class "Default")
      (node (ref "B25") (pin "M2") (pinfunction "P$1_M2") (pintype "passive"))
      (node (ref "B27") (pin "E1") (pinfunction "E1_E1") (pintype "passive"))
    )
    (net (code "936") (name "Net-(B25E-P$2)") (class "Default")
      (node (ref "B25") (pin "R2") (pinfunction "P$2_R2") (pintype "passive"))
      (node (ref "B27") (pin "F1") (pinfunction "H_F1") (pintype "input"))
    )
    (net (code "937") (name "Net-(B25F-P$1)") (class "Default")
      (node (ref "B25") (pin "L2") (pinfunction "P$1_L2") (pintype "passive"))
      (node (ref "B27") (pin "P2") (pinfunction "P2_P2") (pintype "passive"))
    )
    (net (code "938") (name "Net-(B25F-P$2)") (class "Default")
      (node (ref "B25") (pin "S2") (pinfunction "P$2_S2") (pintype "passive"))
      (node (ref "B27") (pin "R2") (pinfunction "H_R2") (pintype "input"))
    )
    (net (code "939") (name "Net-(B25G-P$1)") (class "Default")
      (node (ref "B25") (pin "K2") (pinfunction "P$1_K2") (pintype "passive"))
      (node (ref "B27") (pin "M1") (pinfunction "M1_M1") (pintype "passive"))
    )
    (net (code "940") (name "Net-(B25G-P$2)") (class "Default")
      (node (ref "B25") (pin "T2") (pinfunction "P$2_T2") (pintype "passive"))
      (node (ref "B27") (pin "N1") (pinfunction "H_N1") (pintype "input"))
    )
    (net (code "941") (name "Net-(B36B-H)") (class "Default")
      (node (ref "B36") (pin "F1") (pinfunction "H_F1") (pintype "input"))
      (node (ref "B38") (pin "R2") (pinfunction "P$2_R2") (pintype "passive"))
    )
    (net (code "942") (name "Net-(B36D-H)") (class "Default")
      (node (ref "B36") (pin "H2") (pinfunction "H_H2") (pintype "input"))
      (node (ref "B38") (pin "P2") (pinfunction "P$2_P2") (pintype "passive"))
    )
    (net (code "943") (name "Net-(B36E-H)") (class "Default")
      (node (ref "B36") (pin "N1") (pinfunction "H_N1") (pintype "input"))
      (node (ref "B38") (pin "T2") (pinfunction "P$2_T2") (pintype "passive"))
    )
    (net (code "944") (name "Net-(B36F-H)") (class "Default")
      (node (ref "B36") (pin "R2") (pinfunction "H_R2") (pintype "input"))
      (node (ref "B38") (pin "S2") (pinfunction "P$2_S2") (pintype "passive"))
    )
    (net (code "945") (name "Net-(B37B-H)") (class "Default")
      (node (ref "B37") (pin "F1") (pinfunction "H_F1") (pintype "input"))
      (node (ref "B39") (pin "R2") (pinfunction "P$2_R2") (pintype "passive"))
    )
    (net (code "946") (name "Net-(B37D-H)") (class "Default")
      (node (ref "B37") (pin "H2") (pinfunction "H_H2") (pintype "input"))
      (node (ref "B39") (pin "P2") (pinfunction "P$2_P2") (pintype "passive"))
    )
    (net (code "947") (name "Net-(B37E-H)") (class "Default")
      (node (ref "B37") (pin "N1") (pinfunction "H_N1") (pintype "input"))
      (node (ref "B39") (pin "T2") (pinfunction "P$2_T2") (pintype "passive"))
    )
    (net (code "948") (name "Net-(B37F-H)") (class "Default")
      (node (ref "B37") (pin "R2") (pinfunction "H_R2") (pintype "input"))
      (node (ref "B39") (pin "S2") (pinfunction "P$2_S2") (pintype "passive"))
    )
    (net (code "949") (name "Net-(B38D-P$1)") (class "Default")
      (node (ref "B36") (pin "F2") (pinfunction "F2_F2") (pintype "passive"))
      (node (ref "B38") (pin "N2") (pinfunction "P$1_N2") (pintype "passive"))
    )
    (net (code "950") (name "Net-(B38E-P$1)") (class "Default")
      (node (ref "B36") (pin "E1") (pinfunction "E1_E1") (pintype "passive"))
      (node (ref "B38") (pin "M2") (pinfunction "P$1_M2") (pintype "passive"))
    )
    (net (code "951") (name "Net-(B38F-P$1)") (class "Default")
      (node (ref "B36") (pin "P2") (pinfunction "P2_P2") (pintype "passive"))
      (node (ref "B38") (pin "L2") (pinfunction "P$1_L2") (pintype "passive"))
    )
    (net (code "952") (name "Net-(B38G-P$1)") (class "Default")
      (node (ref "B36") (pin "M1") (pinfunction "M1_M1") (pintype "passive"))
      (node (ref "B38") (pin "K2") (pinfunction "P$1_K2") (pintype "passive"))
    )
    (net (code "953") (name "Net-(B38H-P$1)") (class "Default")
      (node (ref "B38") (pin "F2") (pinfunction "P$1_F2") (pintype "passive"))
      (node (ref "C39") (pin "E1") (pinfunction "E1_E1") (pintype "passive"))
      (node (ref "D39") (pin "E1") (pinfunction "E1_E1") (pintype "passive"))
    )
    (net (code "954") (name "Net-(B39D-P$1)") (class "Default")
      (node (ref "B37") (pin "F2") (pinfunction "F2_F2") (pintype "passive"))
      (node (ref "B39") (pin "N2") (pinfunction "P$1_N2") (pintype "passive"))
    )
    (net (code "955") (name "Net-(B39E-P$1)") (class "Default")
      (node (ref "B37") (pin "E1") (pinfunction "E1_E1") (pintype "passive"))
      (node (ref "B39") (pin "M2") (pinfunction "P$1_M2") (pintype "passive"))
    )
    (net (code "956") (name "Net-(B39F-P$1)") (class "Default")
      (node (ref "B37") (pin "P2") (pinfunction "P2_P2") (pintype "passive"))
      (node (ref "B39") (pin "L2") (pinfunction "P$1_L2") (pintype "passive"))
    )
    (net (code "957") (name "Net-(B39G-P$1)") (class "Default")
      (node (ref "B37") (pin "M1") (pinfunction "M1_M1") (pintype "passive"))
      (node (ref "B39") (pin "K2") (pinfunction "P$1_K2") (pintype "passive"))
    )
    (net (code "958") (name "Net-(B39H-P$1)") (class "Default")
      (node (ref "B39") (pin "F2") (pinfunction "P$1_F2") (pintype "passive"))
      (node (ref "C39") (pin "M1") (pinfunction "M1_M1") (pintype "passive"))
      (node (ref "D39") (pin "M1") (pinfunction "M1_M1") (pintype "passive"))
    )
    (net (code "959") (name "Net-(C01D-P$2)") (class "Default")
      (node (ref "C01") (pin "D2") (pinfunction "P$2_D2") (pintype "bidirectional"))
      (node (ref "C02") (pin "V2") (pinfunction "P$1_V2") (pintype "input"))
      (node (ref "C03") (pin "V2") (pinfunction "P$1_V2") (pintype "input"))
      (node (ref "C04") (pin "V2") (pinfunction "P$1_V2") (pintype "input"))
      (node (ref "C05") (pin "V2") (pinfunction "P$1_V2") (pintype "input"))
      (node (ref "C06") (pin "V2") (pinfunction "P$1_V2") (pintype "input"))
    )
    (net (code "960") (name "Net-(C02A-D)") (class "Default")
      (node (ref "C02") (pin "D2") (pinfunction "D_D2") (pintype "input"))
      (node (ref "C02") (pin "J2") (pinfunction "D_J2") (pintype "input"))
      (node (ref "C03") (pin "D2") (pinfunction "D_D2") (pintype "input"))
      (node (ref "C03") (pin "J2") (pinfunction "D_J2") (pintype "input"))
      (node (ref "C04") (pin "D2") (pinfunction "D_D2") (pintype "input"))
      (node (ref "C04") (pin "J2") (pinfunction "D_J2") (pintype "input"))
      (node (ref "C04") (pin "K2") (pinfunction "E_K2") (pintype "input"))
      (node (ref "C04") (pin "L2") (pinfunction "F_L2") (pintype "input"))
      (node (ref "C04") (pin "M2") (pinfunction "H_M2") (pintype "input"))
      (node (ref "C05") (pin "D2") (pinfunction "D_D2") (pintype "input"))
      (node (ref "C05") (pin "J2") (pinfunction "D_J2") (pintype "input"))
      (node (ref "C06") (pin "D2") (pinfunction "D_D2") (pintype "input"))
      (node (ref "HJ28") (pin "BH2") (pinfunction "BH2_BH2") (pintype "output"))
    )
    (net (code "961") (name "Net-(C02A-E)") (class "Default")
      (node (ref "C02") (pin "E2") (pinfunction "E_E2") (pintype "input"))
      (node (ref "C02") (pin "F2") (pinfunction "F_F2") (pintype "input"))
      (node (ref "C02") (pin "H2") (pinfunction "H_H2") (pintype "input"))
      (node (ref "HJ28") (pin "AK1") (pinfunction "AK1_AK1") (pintype "output"))
    )
    (net (code "962") (name "Net-(C02B-E)") (class "Default")
      (node (ref "C02") (pin "K2") (pinfunction "E_K2") (pintype "input"))
      (node (ref "C02") (pin "L2") (pinfunction "F_L2") (pintype "input"))
      (node (ref "C02") (pin "M2") (pinfunction "H_M2") (pintype "input"))
      (node (ref "HJ28") (pin "AL1") (pinfunction "AL1_AL1") (pintype "output"))
    )
    (net (code "963") (name "Net-(C03A-E)") (class "Default")
      (node (ref "C03") (pin "E2") (pinfunction "E_E2") (pintype "input"))
      (node (ref "C03") (pin "F2") (pinfunction "F_F2") (pintype "input"))
      (node (ref "C03") (pin "H2") (pinfunction "H_H2") (pintype "input"))
      (node (ref "HJ28") (pin "AM1") (pinfunction "AM1_AM1") (pintype "output"))
    )
    (net (code "964") (name "Net-(C03B-E)") (class "Default")
      (node (ref "C03") (pin "K2") (pinfunction "E_K2") (pintype "input"))
      (node (ref "C03") (pin "L2") (pinfunction "F_L2") (pintype "input"))
      (node (ref "C03") (pin "M2") (pinfunction "H_M2") (pintype "input"))
      (node (ref "HJ28") (pin "AN1") (pinfunction "AN1_AN1") (pintype "output"))
    )
    (net (code "965") (name "Net-(C04A-E)") (class "Default")
      (node (ref "C04") (pin "E2") (pinfunction "E_E2") (pintype "input"))
      (node (ref "C04") (pin "F2") (pinfunction "F_F2") (pintype "input"))
      (node (ref "C04") (pin "H2") (pinfunction "H_H2") (pintype "input"))
      (node (ref "HJ28") (pin "AK2") (pinfunction "AK2_AK2") (pintype "output"))
    )
    (net (code "966") (name "Net-(C05A-E)") (class "Default")
      (node (ref "C05") (pin "E2") (pinfunction "E_E2") (pintype "input"))
      (node (ref "C05") (pin "F2") (pinfunction "F_F2") (pintype "input"))
      (node (ref "C05") (pin "H2") (pinfunction "H_H2") (pintype "input"))
      (node (ref "HJ28") (pin "AL2") (pinfunction "AL2_AL2") (pintype "output"))
    )
    (net (code "967") (name "Net-(C05B-E)") (class "Default")
      (node (ref "C05") (pin "K2") (pinfunction "E_K2") (pintype "input"))
      (node (ref "C05") (pin "L2") (pinfunction "F_L2") (pintype "input"))
      (node (ref "C05") (pin "M2") (pinfunction "H_M2") (pintype "input"))
      (node (ref "HJ28") (pin "AM2") (pinfunction "AM2_AM2") (pintype "output"))
    )
    (net (code "968") (name "Net-(C06A-E)") (class "Default")
      (node (ref "C06") (pin "E2") (pinfunction "E_E2") (pintype "input"))
      (node (ref "C06") (pin "F2") (pinfunction "F_F2") (pintype "input"))
      (node (ref "C06") (pin "H2") (pinfunction "H_H2") (pintype "input"))
      (node (ref "HJ28") (pin "AN2") (pinfunction "AN2_AN2") (pintype "output"))
    )
    (net (code "969") (name "Net-(C09A-OUT)") (class "Default")
      (node (ref "C09") (pin "C1") (pinfunction "OUT_C1") (pintype "output"))
      (node (ref "C09") (pin "D1") (pinfunction "IN1_D1") (pintype "input"))
      (node (ref "C11") (pin "K2") (pinfunction "IN2_K2") (pintype "input"))
    )
    (net (code "970") (name "Net-(C09B-OUT)") (class "Default")
      (node (ref "C09") (pin "F1") (pinfunction "OUT_F1") (pintype "output"))
      (node (ref "C09") (pin "H2") (pinfunction "IN1_H2") (pintype "input"))
      (node (ref "D10") (pin "H1") (pinfunction "IN2_H1") (pintype "input"))
    )
    (net (code "971") (name "Net-(C09G-IN2)") (class "Default")
      (node (ref "C09") (pin "J2") (pinfunction "IN2_J2") (pintype "input"))
      (node (ref "C09") (pin "N1") (pinfunction "OUT_N1") (pintype "output"))
    )
    (net (code "972") (name "Net-(C09H-IN1)") (class "Default")
      (node (ref "C09") (pin "L1") (pinfunction "IN1_L1") (pintype "input"))
      (node (ref "D09") (pin "D1") (pinfunction "OUT_D1") (pintype "output"))
    )
    (net (code "973") (name "Net-(C10A-IN1)") (class "Default")
      (node (ref "C10") (pin "A1") (pinfunction "IN1_A1") (pintype "input"))
      (node (ref "C11") (pin "D1") (pinfunction "OUT_D1") (pintype "output"))
    )
    (net (code "974") (name "Net-(C10F-IN1)") (class "Default")
      (node (ref "C10") (pin "H1") (pinfunction "IN1_H1") (pintype "input"))
      (node (ref "C11") (pin "U1") (pinfunction "OUT_U1") (pintype "output"))
    )
    (net (code "975") (name "Net-(C10F-OUT)") (class "Default")
      (node (ref "C10") (pin "K1") (pinfunction "OUT_K1") (pintype "output"))
      (node (ref "D09") (pin "E1") (pinfunction "IN1_E1") (pintype "input"))
      (node (ref "D10") (pin "L2") (pinfunction "IN2_L2") (pintype "input"))
    )
    (net (code "976") (name "Net-(C10G-IN2)") (class "Default")
      (node (ref "C10") (pin "J2") (pinfunction "IN2_J2") (pintype "input"))
      (node (ref "C11") (pin "V1") (pinfunction "OUT_V1") (pintype "output"))
    )
    (net (code "977") (name "Net-(C10G-OUT)") (class "Default")
      (node (ref "C10") (pin "K2") (pinfunction "OUT_K2") (pintype "output"))
      (node (ref "D10") (pin "M2") (pinfunction "IN3_M2") (pintype "input"))
    )
    (net (code "978") (name "Net-(C10I-IN1)") (class "Default")
      (node (ref "C10") (pin "L2") (pinfunction "IN1_L2") (pintype "input"))
      (node (ref "C10") (pin "S1") (pinfunction "OUT_S1") (pintype "output"))
    )
    (net (code "979") (name "Net-(C10I-IN2)") (class "Default")
      (node (ref "C10") (pin "M2") (pinfunction "IN2_M2") (pintype "input"))
      (node (ref "C10") (pin "S2") (pinfunction "OUT_S2") (pintype "output"))
    )
    (net (code "980") (name "Net-(C10K-IN2)") (class "Default")
      (node (ref "C10") (pin "R2") (pinfunction "IN2_R2") (pintype "input"))
      (node (ref "C10") (pin "V2") (pinfunction "OUT_V2") (pintype "output"))
    )
    (net (code "981") (name "Net-(C11D-IN1)") (class "Default")
      (node (ref "C11") (pin "D2") (pinfunction "IN1_D2") (pintype "input"))
      (node (ref "C11") (pin "J1") (pinfunction "OUT_J1") (pintype "output"))
    )
    (net (code "982") (name "Net-(C13A-IN)") (class "Default")
      (node (ref "C13") (pin "E1") (pinfunction "IN_E1") (pintype "input"))
      (node (ref "C13") (pin "S2") (pinfunction "S2_S2") (pintype "output"))
    )
    (net (code "983") (name "Net-(C13A-OUT)") (class "Default")
      (node (ref "C13") (pin "F1") (pinfunction "OUT_F1") (pintype "output"))
      (node (ref "D12") (pin "L1") (pinfunction "IN1_L1") (pintype "input"))
      (node (ref "D24") (pin "N1") (pinfunction "C_N1") (pintype "input"))
    )
    (net (code "984") (name "Net-(C13E-IN)") (class "Default")
      (node (ref "C13") (pin "H1") (pinfunction "IN_H1") (pintype "input"))
      (node (ref "C13") (pin "P2") (pinfunction "P2_P2") (pintype "output"))
    )
    (net (code "985") (name "Net-(C14A-OUT)") (class "Default")
      (node (ref "C14") (pin "C1") (pinfunction "OUT_C1") (pintype "output"))
      (node (ref "C19") (pin "A1") (pinfunction "IN1_A1") (pintype "input"))
    )
    (net (code "986") (name "Net-(C14B-OUT)") (class "Default")
      (node (ref "C14") (pin "F1") (pinfunction "OUT_F1") (pintype "output"))
      (node (ref "C19") (pin "B1") (pinfunction "IN2_B1") (pintype "input"))
    )
    (net (code "987") (name "Net-(C14C-OUT)") (class "Default")
      (node (ref "C14") (pin "F2") (pinfunction "OUT_F2") (pintype "output"))
      (node (ref "C19") (pin "C1") (pinfunction "IN3_C1") (pintype "input"))
    )
    (net (code "988") (name "Net-(C14F-OUT)") (class "Default")
      (node (ref "C14") (pin "K1") (pinfunction "OUT_K1") (pintype "output"))
      (node (ref "C19") (pin "D2") (pinfunction "IN1_D2") (pintype "input"))
    )
    (net (code "989") (name "Net-(C14G-OUT)") (class "Default")
      (node (ref "C14") (pin "K2") (pinfunction "OUT_K2") (pintype "output"))
      (node (ref "C19") (pin "E2") (pinfunction "IN2_E2") (pintype "input"))
    )
    (net (code "990") (name "Net-(C14H-OUT)") (class "Default")
      (node (ref "C14") (pin "N1") (pinfunction "OUT_N1") (pintype "output"))
      (node (ref "C19") (pin "F2") (pinfunction "IN3_F2") (pintype "input"))
    )
    (net (code "991") (name "Net-(C14I-OUT)") (class "Default")
      (node (ref "C14") (pin "N2") (pinfunction "OUT_N2") (pintype "output"))
      (node (ref "C19") (pin "E1") (pinfunction "IN1_E1") (pintype "input"))
    )
    (net (code "992") (name "Net-(C14J-OUT)") (class "Default")
      (node (ref "C14") (pin "S1") (pinfunction "OUT_S1") (pintype "output"))
      (node (ref "C19") (pin "F1") (pinfunction "IN2_F1") (pintype "input"))
    )
    (net (code "993") (name "Net-(C14K-OUT)") (class "Default")
      (node (ref "C14") (pin "S2") (pinfunction "OUT_S2") (pintype "output"))
      (node (ref "C19") (pin "H1") (pinfunction "IN3_H1") (pintype "input"))
    )
    (net (code "994") (name "Net-(C14N-OUT)") (class "Default")
      (node (ref "C14") (pin "V2") (pinfunction "OUT_V2") (pintype "output"))
      (node (ref "C20") (pin "M1") (pinfunction "IN3_M1") (pintype "input"))
    )
    (net (code "995") (name "Net-(C15A-OUT)") (class "Default")
      (node (ref "C15") (pin "C1") (pinfunction "OUT_C1") (pintype "output"))
      (node (ref "C19") (pin "J2") (pinfunction "IN1_J2") (pintype "input"))
    )
    (net (code "996") (name "Net-(C15B-OUT)") (class "Default")
      (node (ref "C15") (pin "F1") (pinfunction "OUT_F1") (pintype "output"))
      (node (ref "C19") (pin "K2") (pinfunction "IN2_K2") (pintype "input"))
    )
    (net (code "997") (name "Net-(C15C-OUT)") (class "Default")
      (node (ref "C15") (pin "F2") (pinfunction "OUT_F2") (pintype "output"))
      (node (ref "C19") (pin "L2") (pinfunction "IN3_L2") (pintype "input"))
    )
    (net (code "998") (name "Net-(C15F-OUT)") (class "Default")
      (node (ref "C15") (pin "K1") (pinfunction "OUT_K1") (pintype "output"))
      (node (ref "C19") (pin "K1") (pinfunction "IN1_K1") (pintype "input"))
    )
    (net (code "999") (name "Net-(C15G-OUT)") (class "Default")
      (node (ref "C15") (pin "K2") (pinfunction "OUT_K2") (pintype "output"))
      (node (ref "C19") (pin "L1") (pinfunction "IN2_L1") (pintype "input"))
    )
    (net (code "1000") (name "Net-(C15H-OUT)") (class "Default")
      (node (ref "C15") (pin "N1") (pinfunction "OUT_N1") (pintype "output"))
      (node (ref "C19") (pin "M1") (pinfunction "IN3_M1") (pintype "input"))
    )
    (net (code "1001") (name "Net-(C15I-OUT)") (class "Default")
      (node (ref "C15") (pin "N2") (pinfunction "OUT_N2") (pintype "output"))
      (node (ref "C19") (pin "N2") (pinfunction "IN1_N2") (pintype "input"))
    )
    (net (code "1002") (name "Net-(C15J-OUT)") (class "Default")
      (node (ref "C15") (pin "S1") (pinfunction "OUT_S1") (pintype "output"))
      (node (ref "C19") (pin "P2") (pinfunction "IN2_P2") (pintype "input"))
    )
    (net (code "1003") (name "Net-(C15K-OUT)") (class "Default")
      (node (ref "C15") (pin "S2") (pinfunction "OUT_S2") (pintype "output"))
      (node (ref "C19") (pin "R2") (pinfunction "IN3_R2") (pintype "input"))
    )
    (net (code "1004") (name "Net-(C15N-OUT)") (class "Default")
      (node (ref "C15") (pin "V2") (pinfunction "OUT_V2") (pintype "output"))
      (node (ref "C20") (pin "R2") (pinfunction "IN3_R2") (pintype "input"))
    )
    (net (code "1005") (name "Net-(C16A-OUT)") (class "Default")
      (node (ref "C16") (pin "C1") (pinfunction "OUT_C1") (pintype "output"))
      (node (ref "C19") (pin "P1") (pinfunction "IN1_P1") (pintype "input"))
    )
    (net (code "1006") (name "Net-(C16B-OUT)") (class "Default")
      (node (ref "C16") (pin "F1") (pinfunction "OUT_F1") (pintype "output"))
      (node (ref "C19") (pin "R1") (pinfunction "IN2_R1") (pintype "input"))
    )
    (net (code "1007") (name "Net-(C16C-OUT)") (class "Default")
      (node (ref "C16") (pin "F2") (pinfunction "OUT_F2") (pintype "output"))
      (node (ref "C19") (pin "S1") (pinfunction "IN3_S1") (pintype "input"))
    )
    (net (code "1008") (name "Net-(C16F-OUT)") (class "Default")
      (node (ref "C16") (pin "K1") (pinfunction "OUT_K1") (pintype "output"))
      (node (ref "C19") (pin "T2") (pinfunction "IN1_T2") (pintype "input"))
    )
    (net (code "1009") (name "Net-(C16G-OUT)") (class "Default")
      (node (ref "C16") (pin "K2") (pinfunction "OUT_K2") (pintype "output"))
      (node (ref "C19") (pin "U2") (pinfunction "IN2_U2") (pintype "input"))
    )
    (net (code "1010") (name "Net-(C16H-OUT)") (class "Default")
      (node (ref "C16") (pin "N1") (pinfunction "OUT_N1") (pintype "output"))
      (node (ref "C19") (pin "V2") (pinfunction "IN3_V2") (pintype "input"))
    )
    (net (code "1011") (name "Net-(C16I-OUT)") (class "Default")
      (node (ref "C16") (pin "N2") (pinfunction "OUT_N2") (pintype "output"))
      (node (ref "C20") (pin "A1") (pinfunction "IN1_A1") (pintype "input"))
    )
    (net (code "1012") (name "Net-(C16J-OUT)") (class "Default")
      (node (ref "C16") (pin "S1") (pinfunction "OUT_S1") (pintype "output"))
      (node (ref "C20") (pin "B1") (pinfunction "IN2_B1") (pintype "input"))
    )
    (net (code "1013") (name "Net-(C16K-OUT)") (class "Default")
      (node (ref "C16") (pin "S2") (pinfunction "OUT_S2") (pintype "output"))
      (node (ref "C20") (pin "C1") (pinfunction "IN3_C1") (pintype "input"))
    )
    (net (code "1014") (name "Net-(C16N-OUT)") (class "Default")
      (node (ref "C16") (pin "V2") (pinfunction "OUT_V2") (pintype "output"))
      (node (ref "C20") (pin "S1") (pinfunction "IN3_S1") (pintype "input"))
    )
    (net (code "1015") (name "Net-(C17A-OUT)") (class "Default")
      (node (ref "C17") (pin "C1") (pinfunction "OUT_C1") (pintype "output"))
      (node (ref "C20") (pin "D2") (pinfunction "IN1_D2") (pintype "input"))
    )
    (net (code "1016") (name "Net-(C17B-OUT)") (class "Default")
      (node (ref "C17") (pin "F1") (pinfunction "OUT_F1") (pintype "output"))
      (node (ref "C20") (pin "E2") (pinfunction "IN2_E2") (pintype "input"))
    )
    (net (code "1017") (name "Net-(C17C-OUT)") (class "Default")
      (node (ref "C17") (pin "F2") (pinfunction "OUT_F2") (pintype "output"))
      (node (ref "C20") (pin "F2") (pinfunction "IN3_F2") (pintype "input"))
    )
    (net (code "1018") (name "Net-(C17F-OUT)") (class "Default")
      (node (ref "C17") (pin "K1") (pinfunction "OUT_K1") (pintype "output"))
      (node (ref "C20") (pin "E1") (pinfunction "IN1_E1") (pintype "input"))
    )
    (net (code "1019") (name "Net-(C17G-OUT)") (class "Default")
      (node (ref "C17") (pin "K2") (pinfunction "OUT_K2") (pintype "output"))
      (node (ref "C20") (pin "F1") (pinfunction "IN2_F1") (pintype "input"))
    )
    (net (code "1020") (name "Net-(C17H-OUT)") (class "Default")
      (node (ref "C17") (pin "N1") (pinfunction "OUT_N1") (pintype "output"))
      (node (ref "C20") (pin "H1") (pinfunction "IN3_H1") (pintype "input"))
    )
    (net (code "1021") (name "Net-(C17I-OUT)") (class "Default")
      (node (ref "C17") (pin "N2") (pinfunction "OUT_N2") (pintype "output"))
      (node (ref "C20") (pin "J2") (pinfunction "IN1_J2") (pintype "input"))
    )
    (net (code "1022") (name "Net-(C17J-OUT)") (class "Default")
      (node (ref "C17") (pin "S1") (pinfunction "OUT_S1") (pintype "output"))
      (node (ref "C20") (pin "K2") (pinfunction "IN2_K2") (pintype "input"))
    )
    (net (code "1023") (name "Net-(C17K-IN2)") (class "Default")
      (node (ref "C17") (pin "R2") (pinfunction "IN2_R2") (pintype "input"))
      (node (ref "D23") (pin "T2") (pinfunction "OUT_T2") (pintype "output"))
    )
    (net (code "1024") (name "Net-(C17K-OUT)") (class "Default")
      (node (ref "C17") (pin "S2") (pinfunction "OUT_S2") (pintype "output"))
      (node (ref "C20") (pin "L2") (pinfunction "IN3_L2") (pintype "input"))
    )
    (net (code "1025") (name "Net-(C17N-OUT)") (class "Default")
      (node (ref "C17") (pin "V2") (pinfunction "OUT_V2") (pintype "output"))
      (node (ref "C20") (pin "V2") (pinfunction "IN3_V2") (pintype "input"))
    )
    (net (code "1026") (name "Net-(C18A-IN2)") (class "Default")
      (node (ref "C18") (pin "B1") (pinfunction "IN2_B1") (pintype "input"))
      (node (ref "C21") (pin "E2") (pinfunction "IN2_E2") (pintype "input"))
      (node (ref "D22") (pin "E1") (pinfunction "OUT_E1") (pintype "open_collector"))
    )
    (net (code "1027") (name "Net-(C18B-IN2)") (class "Default")
      (node (ref "C18") (pin "E1") (pinfunction "IN2_E1") (pintype "input"))
      (node (ref "C21") (pin "K2") (pinfunction "IN2_K2") (pintype "input"))
      (node (ref "D19") (pin "D1") (pinfunction "OUT_D1") (pintype "output"))
    )
    (net (code "1028") (name "Net-(C18B-OUT)") (class "Default")
      (node (ref "C18") (pin "F1") (pinfunction "OUT_F1") (pintype "output"))
      (node (ref "C21") (pin "F1") (pinfunction "IN2_F1") (pintype "input"))
    )
    (net (code "1029") (name "Net-(C18C-IN2)") (class "Default")
      (node (ref "C18") (pin "E2") (pinfunction "IN2_E2") (pintype "input"))
      (node (ref "C18") (pin "K1") (pinfunction "OUT_K1") (pintype "output"))
      (node (ref "C21") (pin "P2") (pinfunction "IN2_P2") (pintype "input"))
    )
    (net (code "1030") (name "Net-(C18C-OUT)") (class "Default")
      (node (ref "C18") (pin "F2") (pinfunction "OUT_F2") (pintype "output"))
      (node (ref "C21") (pin "L1") (pinfunction "IN2_L1") (pintype "input"))
    )
    (net (code "1031") (name "Net-(C18H-IN1)") (class "Default")
      (node (ref "C18") (pin "L1") (pinfunction "IN1_L1") (pintype "input"))
      (node (ref "C18") (pin "N2") (pinfunction "OUT_N2") (pintype "output"))
    )
    (net (code "1032") (name "Net-(C18H-IN2)") (class "Default")
      (node (ref "C18") (pin "M1") (pinfunction "IN2_M1") (pintype "input"))
      (node (ref "C18") (pin "S1") (pinfunction "OUT_S1") (pintype "output"))
    )
    (net (code "1033") (name "Net-(C18H-OUT)") (class "Default")
      (node (ref "C18") (pin "N1") (pinfunction "OUT_N1") (pintype "output"))
      (node (ref "C22") (pin "P1") (pinfunction "D_P1") (pintype "input"))
    )
    (net (code "1034") (name "Net-(C19A-OUT)") (class "Default")
      (node (ref "C19") (pin "D1") (pinfunction "OUT_D1") (pintype "output"))
      (node (ref "C23") (pin "C1") (pinfunction "D_C1") (pintype "input"))
    )
    (net (code "1035") (name "Net-(C19D-OUT)") (class "Default")
      (node (ref "C19") (pin "H2") (pinfunction "OUT_H2") (pintype "output"))
      (node (ref "C23") (pin "E2") (pinfunction "D_E2") (pintype "input"))
    )
    (net (code "1036") (name "Net-(C19E-OUT)") (class "Default")
      (node (ref "C19") (pin "J1") (pinfunction "OUT_J1") (pintype "output"))
      (node (ref "C23") (pin "J1") (pinfunction "D_J1") (pintype "input"))
    )
    (net (code "1037") (name "Net-(C19F-OUT)") (class "Default")
      (node (ref "C19") (pin "M2") (pinfunction "OUT_M2") (pintype "output"))
      (node (ref "C23") (pin "M2") (pinfunction "D_M2") (pintype "input"))
    )
    (net (code "1038") (name "Net-(C19G-OUT)") (class "Default")
      (node (ref "C19") (pin "N1") (pinfunction "OUT_N1") (pintype "output"))
      (node (ref "C23") (pin "P1") (pinfunction "D_P1") (pintype "input"))
    )
    (net (code "1039") (name "Net-(C19H-OUT)") (class "Default")
      (node (ref "C19") (pin "S2") (pinfunction "OUT_S2") (pintype "output"))
      (node (ref "C23") (pin "T2") (pinfunction "D_T2") (pintype "input"))
    )
    (net (code "1040") (name "Net-(C19I-OUT)") (class "Default")
      (node (ref "C19") (pin "U1") (pinfunction "OUT_U1") (pintype "output"))
      (node (ref "C24") (pin "C1") (pinfunction "D_C1") (pintype "input"))
    )
    (net (code "1041") (name "Net-(C19J-OUT)") (class "Default")
      (node (ref "C19") (pin "V1") (pinfunction "OUT_V1") (pintype "output"))
      (node (ref "C24") (pin "E2") (pinfunction "D_E2") (pintype "input"))
    )
    (net (code "1042") (name "Net-(C20A-OUT)") (class "Default")
      (node (ref "C20") (pin "D1") (pinfunction "OUT_D1") (pintype "output"))
      (node (ref "C24") (pin "J1") (pinfunction "D_J1") (pintype "input"))
    )
    (net (code "1043") (name "Net-(C20D-OUT)") (class "Default")
      (node (ref "C20") (pin "H2") (pinfunction "OUT_H2") (pintype "output"))
      (node (ref "C24") (pin "M2") (pinfunction "D_M2") (pintype "input"))
    )
    (net (code "1044") (name "Net-(C20E-OUT)") (class "Default")
      (node (ref "C20") (pin "J1") (pinfunction "OUT_J1") (pintype "output"))
      (node (ref "C24") (pin "P1") (pinfunction "D_P1") (pintype "input"))
    )
    (net (code "1045") (name "Net-(C20F-OUT)") (class "Default")
      (node (ref "C20") (pin "M2") (pinfunction "OUT_M2") (pintype "output"))
      (node (ref "C24") (pin "T2") (pinfunction "D_T2") (pintype "input"))
    )
    (net (code "1046") (name "Net-(C20G-IN1)") (class "Default")
      (node (ref "C20") (pin "K1") (pinfunction "IN1_K1") (pintype "input"))
      (node (ref "C21") (pin "D1") (pinfunction "OUT_D1") (pintype "output"))
    )
    (net (code "1047") (name "Net-(C20G-IN2)") (class "Default")
      (node (ref "C20") (pin "L1") (pinfunction "IN2_L1") (pintype "input"))
      (node (ref "C21") (pin "H2") (pinfunction "OUT_H2") (pintype "output"))
    )
    (net (code "1048") (name "Net-(C20G-OUT)") (class "Default")
      (node (ref "C20") (pin "N1") (pinfunction "OUT_N1") (pintype "output"))
      (node (ref "C22") (pin "C1") (pinfunction "D_C1") (pintype "input"))
    )
    (net (code "1049") (name "Net-(C20H-IN1)") (class "Default")
      (node (ref "C20") (pin "N2") (pinfunction "IN1_N2") (pintype "input"))
      (node (ref "C21") (pin "J1") (pinfunction "OUT_J1") (pintype "output"))
    )
    (net (code "1050") (name "Net-(C20H-IN2)") (class "Default")
      (node (ref "C20") (pin "P2") (pinfunction "IN2_P2") (pintype "input"))
      (node (ref "C21") (pin "M2") (pinfunction "OUT_M2") (pintype "output"))
    )
    (net (code "1051") (name "Net-(C20H-OUT)") (class "Default")
      (node (ref "C20") (pin "S2") (pinfunction "OUT_S2") (pintype "output"))
      (node (ref "C22") (pin "E2") (pinfunction "D_E2") (pintype "input"))
    )
    (net (code "1052") (name "Net-(C20I-IN1)") (class "Default")
      (node (ref "C20") (pin "P1") (pinfunction "IN1_P1") (pintype "input"))
      (node (ref "C21") (pin "N1") (pinfunction "OUT_N1") (pintype "output"))
    )
    (net (code "1053") (name "Net-(C20I-IN2)") (class "Default")
      (node (ref "C20") (pin "R1") (pinfunction "IN2_R1") (pintype "input"))
      (node (ref "C21") (pin "S2") (pinfunction "OUT_S2") (pintype "output"))
    )
    (net (code "1054") (name "Net-(C20I-OUT)") (class "Default")
      (node (ref "C20") (pin "U1") (pinfunction "OUT_U1") (pintype "output"))
      (node (ref "C22") (pin "J1") (pinfunction "D_J1") (pintype "input"))
    )
    (net (code "1055") (name "Net-(C20J-IN1)") (class "Default")
      (node (ref "C20") (pin "T2") (pinfunction "IN1_T2") (pintype "input"))
      (node (ref "C21") (pin "U1") (pinfunction "OUT_U1") (pintype "output"))
    )
    (net (code "1056") (name "Net-(C20J-IN2)") (class "Default")
      (node (ref "C20") (pin "U2") (pinfunction "IN2_U2") (pintype "input"))
      (node (ref "C21") (pin "V1") (pinfunction "OUT_V1") (pintype "output"))
    )
    (net (code "1057") (name "Net-(C20J-OUT)") (class "Default")
      (node (ref "C20") (pin "V1") (pinfunction "OUT_V1") (pintype "output"))
      (node (ref "C22") (pin "M2") (pinfunction "D_M2") (pintype "input"))
    )
    (net (code "1058") (name "Net-(CD27A-C2)") (class "Default")
      (node (ref "C25") (pin "K2") (pinfunction "K2_K2") (pintype "passive"))
      (node (ref "CD27") (pin "AC2") (pinfunction "C2_AC2") (pintype "passive"))
    )
    (net (code "1059") (name "Net-(CD27A-D2)") (class "Default")
      (node (ref "C25") (pin "J2") (pinfunction "J2_J2") (pintype "passive"))
      (node (ref "CD27") (pin "AD2") (pinfunction "D2_AD2") (pintype "passive"))
    )
    (net (code "1060") (name "Net-(CD27A-E2)") (class "Default")
      (node (ref "C25") (pin "M2") (pinfunction "M2_M2") (pintype "passive"))
      (node (ref "CD27") (pin "AE2") (pinfunction "E2_AE2") (pintype "passive"))
    )
    (net (code "1061") (name "Net-(CD27A-F2)") (class "Default")
      (node (ref "C25") (pin "L2") (pinfunction "L2_L2") (pintype "passive"))
      (node (ref "CD27") (pin "AF2") (pinfunction "F2_AF2") (pintype "passive"))
    )
    (net (code "1062") (name "Net-(CD27A-H2)") (class "Default")
      (node (ref "C25") (pin "P2") (pinfunction "P2_P2") (pintype "passive"))
      (node (ref "CD27") (pin "AH2") (pinfunction "H2_AH2") (pintype "passive"))
    )
    (net (code "1063") (name "Net-(CD27A-J2)") (class "Default")
      (node (ref "C25") (pin "N2") (pinfunction "N2_N2") (pintype "passive"))
      (node (ref "CD27") (pin "AJ2") (pinfunction "J2_AJ2") (pintype "passive"))
    )
    (net (code "1064") (name "Net-(CD27A-K2)") (class "Default")
      (node (ref "C25") (pin "S2") (pinfunction "S2_S2") (pintype "passive"))
      (node (ref "CD27") (pin "AK2") (pinfunction "K2_AK2") (pintype "passive"))
    )
    (net (code "1065") (name "Net-(CD27A-L2)") (class "Default")
      (node (ref "C25") (pin "R2") (pinfunction "R2_R2") (pintype "passive"))
      (node (ref "CD27") (pin "AL2") (pinfunction "L2_AL2") (pintype "passive"))
    )
    (net (code "1066") (name "Net-(CD27A-M2)") (class "Default")
      (node (ref "C26") (pin "K2") (pinfunction "K2_K2") (pintype "passive"))
      (node (ref "CD27") (pin "AM2") (pinfunction "M2_AM2") (pintype "passive"))
    )
    (net (code "1067") (name "Net-(CD27A-N2)") (class "Default")
      (node (ref "C26") (pin "J2") (pinfunction "J2_J2") (pintype "passive"))
      (node (ref "CD27") (pin "AN2") (pinfunction "N2_AN2") (pintype "passive"))
    )
    (net (code "1068") (name "Net-(CD27A-P2)") (class "Default")
      (node (ref "C26") (pin "M2") (pinfunction "M2_M2") (pintype "passive"))
      (node (ref "CD27") (pin "AP2") (pinfunction "P2_AP2") (pintype "passive"))
    )
    (net (code "1069") (name "Net-(CD27A-R2)") (class "Default")
      (node (ref "C26") (pin "L2") (pinfunction "L2_L2") (pintype "passive"))
      (node (ref "CD27") (pin "AR2") (pinfunction "R2_AR2") (pintype "passive"))
    )
    (net (code "1070") (name "Net-(CD27A-S2)") (class "Default")
      (node (ref "C26") (pin "P2") (pinfunction "P2_P2") (pintype "passive"))
      (node (ref "CD27") (pin "AS2") (pinfunction "S2_AS2") (pintype "passive"))
    )
    (net (code "1071") (name "Net-(CD27A-T2)") (class "Default")
      (node (ref "C26") (pin "N2") (pinfunction "N2_N2") (pintype "passive"))
      (node (ref "CD27") (pin "AT2") (pinfunction "T2_AT2") (pintype "passive"))
    )
    (net (code "1072") (name "Net-(CD27A-U2)") (class "Default")
      (node (ref "C26") (pin "S2") (pinfunction "S2_S2") (pintype "passive"))
      (node (ref "CD27") (pin "AU2") (pinfunction "U2_AU2") (pintype "passive"))
    )
    (net (code "1073") (name "Net-(CD27A-V2)") (class "Default")
      (node (ref "C26") (pin "R2") (pinfunction "R2_R2") (pintype "passive"))
      (node (ref "CD27") (pin "AV2") (pinfunction "V2_AV2") (pintype "passive"))
    )
    (net (code "1074") (name "Net-(CD27B-C2)") (class "Default")
      (node (ref "CD27") (pin "BC2") (pinfunction "C2_BC2") (pintype "passive"))
      (node (ref "D25") (pin "R2") (pinfunction "R2_R2") (pintype "passive"))
    )
    (net (code "1075") (name "Net-(CD27B-D2)") (class "Default")
      (node (ref "CD27") (pin "BD2") (pinfunction "D2_BD2") (pintype "passive"))
      (node (ref "D25") (pin "S2") (pinfunction "S2_S2") (pintype "passive"))
    )
    (net (code "1076") (name "Net-(CD27B-E2)") (class "Default")
      (node (ref "CD27") (pin "BE2") (pinfunction "E2_BE2") (pintype "passive"))
      (node (ref "D25") (pin "N2") (pinfunction "N2_N2") (pintype "passive"))
    )
    (net (code "1077") (name "Net-(CD27B-F2)") (class "Default")
      (node (ref "CD27") (pin "BF2") (pinfunction "F2_BF2") (pintype "passive"))
      (node (ref "D25") (pin "P2") (pinfunction "P2_P2") (pintype "passive"))
    )
    (net (code "1078") (name "Net-(CD27B-H2)") (class "Default")
      (node (ref "CD27") (pin "BH2") (pinfunction "H2_BH2") (pintype "passive"))
      (node (ref "D25") (pin "L2") (pinfunction "L2_L2") (pintype "passive"))
    )
    (net (code "1079") (name "Net-(CD27B-J2)") (class "Default")
      (node (ref "CD27") (pin "BJ2") (pinfunction "J2_BJ2") (pintype "passive"))
      (node (ref "D25") (pin "M2") (pinfunction "M2_M2") (pintype "passive"))
    )
    (net (code "1080") (name "Net-(CD27B-K2)") (class "Default")
      (node (ref "CD27") (pin "BK2") (pinfunction "K2_BK2") (pintype "passive"))
      (node (ref "D25") (pin "J2") (pinfunction "J2_J2") (pintype "passive"))
    )
    (net (code "1081") (name "Net-(CD27B-L2)") (class "Default")
      (node (ref "CD27") (pin "BL2") (pinfunction "L2_BL2") (pintype "passive"))
      (node (ref "D25") (pin "K2") (pinfunction "K2_K2") (pintype "passive"))
    )
    (net (code "1082") (name "Net-(CD27B-M2)") (class "Default")
      (node (ref "CD27") (pin "BM2") (pinfunction "M2_BM2") (pintype "passive"))
      (node (ref "D26") (pin "R2") (pinfunction "R2_R2") (pintype "passive"))
    )
    (net (code "1083") (name "Net-(CD27B-N2)") (class "Default")
      (node (ref "CD27") (pin "BN2") (pinfunction "N2_BN2") (pintype "passive"))
      (node (ref "D26") (pin "S2") (pinfunction "S2_S2") (pintype "passive"))
    )
    (net (code "1084") (name "Net-(CD27B-P2)") (class "Default")
      (node (ref "CD27") (pin "BP2") (pinfunction "P2_BP2") (pintype "passive"))
      (node (ref "D26") (pin "N2") (pinfunction "N2_N2") (pintype "passive"))
    )
    (net (code "1085") (name "Net-(CD27B-R2)") (class "Default")
      (node (ref "CD27") (pin "BR2") (pinfunction "R2_BR2") (pintype "passive"))
      (node (ref "D26") (pin "P2") (pinfunction "P2_P2") (pintype "passive"))
    )
    (net (code "1086") (name "Net-(CD27B-S2)") (class "Default")
      (node (ref "CD27") (pin "BS2") (pinfunction "S2_BS2") (pintype "passive"))
      (node (ref "D26") (pin "L2") (pinfunction "L2_L2") (pintype "passive"))
    )
    (net (code "1087") (name "Net-(CD27B-T2)") (class "Default")
      (node (ref "CD27") (pin "BT2") (pinfunction "T2_BT2") (pintype "passive"))
      (node (ref "D26") (pin "M2") (pinfunction "M2_M2") (pintype "passive"))
    )
    (net (code "1088") (name "Net-(CD27B-U2)") (class "Default")
      (node (ref "CD27") (pin "BU2") (pinfunction "U2_BU2") (pintype "passive"))
      (node (ref "D26") (pin "J2") (pinfunction "J2_J2") (pintype "passive"))
    )
    (net (code "1089") (name "Net-(CD27B-V2)") (class "Default")
      (node (ref "CD27") (pin "BV2") (pinfunction "V2_BV2") (pintype "passive"))
      (node (ref "D26") (pin "K2") (pinfunction "K2_K2") (pintype "passive"))
    )
    (net (code "1090") (name "Net-(CD29A-C2)") (class "Default")
      (node (ref "C30") (pin "K2") (pinfunction "K2_K2") (pintype "passive"))
      (node (ref "CD29") (pin "AC2") (pinfunction "C2_AC2") (pintype "passive"))
    )
    (net (code "1091") (name "Net-(CD29A-D2)") (class "Default")
      (node (ref "C30") (pin "J2") (pinfunction "J2_J2") (pintype "passive"))
      (node (ref "CD29") (pin "AD2") (pinfunction "D2_AD2") (pintype "passive"))
    )
    (net (code "1092") (name "Net-(CD29A-E2)") (class "Default")
      (node (ref "C30") (pin "M2") (pinfunction "M2_M2") (pintype "passive"))
      (node (ref "CD29") (pin "AE2") (pinfunction "E2_AE2") (pintype "passive"))
    )
    (net (code "1093") (name "Net-(CD29A-F2)") (class "Default")
      (node (ref "C30") (pin "L2") (pinfunction "L2_L2") (pintype "passive"))
      (node (ref "CD29") (pin "AF2") (pinfunction "F2_AF2") (pintype "passive"))
    )
    (net (code "1094") (name "Net-(CD29A-H2)") (class "Default")
      (node (ref "C30") (pin "P2") (pinfunction "P2_P2") (pintype "passive"))
      (node (ref "CD29") (pin "AH2") (pinfunction "H2_AH2") (pintype "passive"))
    )
    (net (code "1095") (name "Net-(CD29A-J2)") (class "Default")
      (node (ref "C30") (pin "N2") (pinfunction "N2_N2") (pintype "passive"))
      (node (ref "CD29") (pin "AJ2") (pinfunction "J2_AJ2") (pintype "passive"))
    )
    (net (code "1096") (name "Net-(CD29A-K2)") (class "Default")
      (node (ref "C30") (pin "S2") (pinfunction "S2_S2") (pintype "passive"))
      (node (ref "CD29") (pin "AK2") (pinfunction "K2_AK2") (pintype "passive"))
    )
    (net (code "1097") (name "Net-(CD29A-L2)") (class "Default")
      (node (ref "C30") (pin "R2") (pinfunction "R2_R2") (pintype "passive"))
      (node (ref "CD29") (pin "AL2") (pinfunction "L2_AL2") (pintype "passive"))
    )
    (net (code "1098") (name "Net-(CD29A-M2)") (class "Default")
      (node (ref "C31") (pin "K2") (pinfunction "K2_K2") (pintype "passive"))
      (node (ref "CD29") (pin "AM2") (pinfunction "M2_AM2") (pintype "passive"))
    )
    (net (code "1099") (name "Net-(CD29A-N2)") (class "Default")
      (node (ref "C31") (pin "J2") (pinfunction "J2_J2") (pintype "passive"))
      (node (ref "CD29") (pin "AN2") (pinfunction "N2_AN2") (pintype "passive"))
    )
    (net (code "1100") (name "Net-(CD29A-P2)") (class "Default")
      (node (ref "C31") (pin "M2") (pinfunction "M2_M2") (pintype "passive"))
      (node (ref "CD29") (pin "AP2") (pinfunction "P2_AP2") (pintype "passive"))
    )
    (net (code "1101") (name "Net-(CD29A-R2)") (class "Default")
      (node (ref "C31") (pin "L2") (pinfunction "L2_L2") (pintype "passive"))
      (node (ref "CD29") (pin "AR2") (pinfunction "R2_AR2") (pintype "passive"))
    )
    (net (code "1102") (name "Net-(CD29A-S2)") (class "Default")
      (node (ref "C31") (pin "P2") (pinfunction "P2_P2") (pintype "passive"))
      (node (ref "CD29") (pin "AS2") (pinfunction "S2_AS2") (pintype "passive"))
    )
    (net (code "1103") (name "Net-(CD29A-T2)") (class "Default")
      (node (ref "C31") (pin "N2") (pinfunction "N2_N2") (pintype "passive"))
      (node (ref "CD29") (pin "AT2") (pinfunction "T2_AT2") (pintype "passive"))
    )
    (net (code "1104") (name "Net-(CD29A-U2)") (class "Default")
      (node (ref "C31") (pin "S2") (pinfunction "S2_S2") (pintype "passive"))
      (node (ref "CD29") (pin "AU2") (pinfunction "U2_AU2") (pintype "passive"))
    )
    (net (code "1105") (name "Net-(CD29A-V2)") (class "Default")
      (node (ref "C31") (pin "R2") (pinfunction "R2_R2") (pintype "passive"))
      (node (ref "CD29") (pin "AV2") (pinfunction "V2_AV2") (pintype "passive"))
    )
    (net (code "1106") (name "Net-(CD29B-C2)") (class "Default")
      (node (ref "CD29") (pin "BC2") (pinfunction "C2_BC2") (pintype "passive"))
      (node (ref "D30") (pin "R2") (pinfunction "R2_R2") (pintype "passive"))
    )
    (net (code "1107") (name "Net-(CD29B-D2)") (class "Default")
      (node (ref "CD29") (pin "BD2") (pinfunction "D2_BD2") (pintype "passive"))
      (node (ref "D30") (pin "S2") (pinfunction "S2_S2") (pintype "passive"))
    )
    (net (code "1108") (name "Net-(CD29B-E2)") (class "Default")
      (node (ref "CD29") (pin "BE2") (pinfunction "E2_BE2") (pintype "passive"))
      (node (ref "D30") (pin "N2") (pinfunction "N2_N2") (pintype "passive"))
    )
    (net (code "1109") (name "Net-(CD29B-F2)") (class "Default")
      (node (ref "CD29") (pin "BF2") (pinfunction "F2_BF2") (pintype "passive"))
      (node (ref "D30") (pin "P2") (pinfunction "P2_P2") (pintype "passive"))
    )
    (net (code "1110") (name "Net-(CD29B-H2)") (class "Default")
      (node (ref "CD29") (pin "BH2") (pinfunction "H2_BH2") (pintype "passive"))
      (node (ref "D30") (pin "L2") (pinfunction "L2_L2") (pintype "passive"))
    )
    (net (code "1111") (name "Net-(CD29B-J2)") (class "Default")
      (node (ref "CD29") (pin "BJ2") (pinfunction "J2_BJ2") (pintype "passive"))
      (node (ref "D30") (pin "M2") (pinfunction "M2_M2") (pintype "passive"))
    )
    (net (code "1112") (name "Net-(CD29B-K2)") (class "Default")
      (node (ref "CD29") (pin "BK2") (pinfunction "K2_BK2") (pintype "passive"))
      (node (ref "D30") (pin "J2") (pinfunction "J2_J2") (pintype "passive"))
    )
    (net (code "1113") (name "Net-(CD29B-L2)") (class "Default")
      (node (ref "CD29") (pin "BL2") (pinfunction "L2_BL2") (pintype "passive"))
      (node (ref "D30") (pin "K2") (pinfunction "K2_K2") (pintype "passive"))
    )
    (net (code "1114") (name "Net-(CD29B-M2)") (class "Default")
      (node (ref "CD29") (pin "BM2") (pinfunction "M2_BM2") (pintype "passive"))
      (node (ref "D31") (pin "R2") (pinfunction "R2_R2") (pintype "passive"))
    )
    (net (code "1115") (name "Net-(CD29B-N2)") (class "Default")
      (node (ref "CD29") (pin "BN2") (pinfunction "N2_BN2") (pintype "passive"))
      (node (ref "D31") (pin "S2") (pinfunction "S2_S2") (pintype "passive"))
    )
    (net (code "1116") (name "Net-(CD29B-P2)") (class "Default")
      (node (ref "CD29") (pin "BP2") (pinfunction "P2_BP2") (pintype "passive"))
      (node (ref "D31") (pin "N2") (pinfunction "N2_N2") (pintype "passive"))
    )
    (net (code "1117") (name "Net-(CD29B-R2)") (class "Default")
      (node (ref "CD29") (pin "BR2") (pinfunction "R2_BR2") (pintype "passive"))
      (node (ref "D31") (pin "P2") (pinfunction "P2_P2") (pintype "passive"))
    )
    (net (code "1118") (name "Net-(CD29B-S2)") (class "Default")
      (node (ref "CD29") (pin "BS2") (pinfunction "S2_BS2") (pintype "passive"))
      (node (ref "D31") (pin "L2") (pinfunction "L2_L2") (pintype "passive"))
    )
    (net (code "1119") (name "Net-(CD29B-T2)") (class "Default")
      (node (ref "CD29") (pin "BT2") (pinfunction "T2_BT2") (pintype "passive"))
      (node (ref "D31") (pin "M2") (pinfunction "M2_M2") (pintype "passive"))
    )
    (net (code "1120") (name "Net-(CD29B-U2)") (class "Default")
      (node (ref "CD29") (pin "BU2") (pinfunction "U2_BU2") (pintype "passive"))
      (node (ref "D31") (pin "J2") (pinfunction "J2_J2") (pintype "passive"))
    )
    (net (code "1121") (name "Net-(CD29B-V2)") (class "Default")
      (node (ref "CD29") (pin "BV2") (pinfunction "V2_BV2") (pintype "passive"))
      (node (ref "D31") (pin "K2") (pinfunction "K2_K2") (pintype "passive"))
    )
    (net (code "1122") (name "Net-(CD34A-C2)") (class "Default")
      (node (ref "C32") (pin "K2") (pinfunction "K2_K2") (pintype "passive"))
      (node (ref "CD34") (pin "AC2") (pinfunction "C2_AC2") (pintype "passive"))
    )
    (net (code "1123") (name "Net-(CD34A-D2)") (class "Default")
      (node (ref "C32") (pin "J2") (pinfunction "J2_J2") (pintype "passive"))
      (node (ref "CD34") (pin "AD2") (pinfunction "D2_AD2") (pintype "passive"))
    )
    (net (code "1124") (name "Net-(CD34A-E2)") (class "Default")
      (node (ref "C32") (pin "M2") (pinfunction "M2_M2") (pintype "passive"))
      (node (ref "CD34") (pin "AE2") (pinfunction "E2_AE2") (pintype "passive"))
    )
    (net (code "1125") (name "Net-(CD34A-F2)") (class "Default")
      (node (ref "C32") (pin "L2") (pinfunction "L2_L2") (pintype "passive"))
      (node (ref "CD34") (pin "AF2") (pinfunction "F2_AF2") (pintype "passive"))
    )
    (net (code "1126") (name "Net-(CD34A-H2)") (class "Default")
      (node (ref "C32") (pin "P2") (pinfunction "P2_P2") (pintype "passive"))
      (node (ref "CD34") (pin "AH2") (pinfunction "H2_AH2") (pintype "passive"))
    )
    (net (code "1127") (name "Net-(CD34A-J2)") (class "Default")
      (node (ref "C32") (pin "N2") (pinfunction "N2_N2") (pintype "passive"))
      (node (ref "CD34") (pin "AJ2") (pinfunction "J2_AJ2") (pintype "passive"))
    )
    (net (code "1128") (name "Net-(CD34A-K2)") (class "Default")
      (node (ref "C32") (pin "S2") (pinfunction "S2_S2") (pintype "passive"))
      (node (ref "CD34") (pin "AK2") (pinfunction "K2_AK2") (pintype "passive"))
    )
    (net (code "1129") (name "Net-(CD34A-L2)") (class "Default")
      (node (ref "C32") (pin "R2") (pinfunction "R2_R2") (pintype "passive"))
      (node (ref "CD34") (pin "AL2") (pinfunction "L2_AL2") (pintype "passive"))
    )
    (net (code "1130") (name "Net-(CD34A-M2)") (class "Default")
      (node (ref "C33") (pin "K2") (pinfunction "K2_K2") (pintype "passive"))
      (node (ref "CD34") (pin "AM2") (pinfunction "M2_AM2") (pintype "passive"))
    )
    (net (code "1131") (name "Net-(CD34A-N2)") (class "Default")
      (node (ref "C33") (pin "J2") (pinfunction "J2_J2") (pintype "passive"))
      (node (ref "CD34") (pin "AN2") (pinfunction "N2_AN2") (pintype "passive"))
    )
    (net (code "1132") (name "Net-(CD34A-P2)") (class "Default")
      (node (ref "C33") (pin "M2") (pinfunction "M2_M2") (pintype "passive"))
      (node (ref "CD34") (pin "AP2") (pinfunction "P2_AP2") (pintype "passive"))
    )
    (net (code "1133") (name "Net-(CD34A-R2)") (class "Default")
      (node (ref "C33") (pin "L2") (pinfunction "L2_L2") (pintype "passive"))
      (node (ref "CD34") (pin "AR2") (pinfunction "R2_AR2") (pintype "passive"))
    )
    (net (code "1134") (name "Net-(CD34A-S2)") (class "Default")
      (node (ref "C33") (pin "P2") (pinfunction "P2_P2") (pintype "passive"))
      (node (ref "CD34") (pin "AS2") (pinfunction "S2_AS2") (pintype "passive"))
    )
    (net (code "1135") (name "Net-(CD34A-T2)") (class "Default")
      (node (ref "C33") (pin "N2") (pinfunction "N2_N2") (pintype "passive"))
      (node (ref "CD34") (pin "AT2") (pinfunction "T2_AT2") (pintype "passive"))
    )
    (net (code "1136") (name "Net-(CD34A-U2)") (class "Default")
      (node (ref "C33") (pin "S2") (pinfunction "S2_S2") (pintype "passive"))
      (node (ref "CD34") (pin "AU2") (pinfunction "U2_AU2") (pintype "passive"))
    )
    (net (code "1137") (name "Net-(CD34A-V2)") (class "Default")
      (node (ref "C33") (pin "R2") (pinfunction "R2_R2") (pintype "passive"))
      (node (ref "CD34") (pin "AV2") (pinfunction "V2_AV2") (pintype "passive"))
    )
    (net (code "1138") (name "Net-(CD34B-C2)") (class "Default")
      (node (ref "CD34") (pin "BC2") (pinfunction "C2_BC2") (pintype "passive"))
      (node (ref "D32") (pin "R2") (pinfunction "R2_R2") (pintype "passive"))
    )
    (net (code "1139") (name "Net-(CD34B-D2)") (class "Default")
      (node (ref "CD34") (pin "BD2") (pinfunction "D2_BD2") (pintype "passive"))
      (node (ref "D32") (pin "S2") (pinfunction "S2_S2") (pintype "passive"))
    )
    (net (code "1140") (name "Net-(CD34B-E2)") (class "Default")
      (node (ref "CD34") (pin "BE2") (pinfunction "E2_BE2") (pintype "passive"))
      (node (ref "D32") (pin "N2") (pinfunction "N2_N2") (pintype "passive"))
    )
    (net (code "1141") (name "Net-(CD34B-F2)") (class "Default")
      (node (ref "CD34") (pin "BF2") (pinfunction "F2_BF2") (pintype "passive"))
      (node (ref "D32") (pin "P2") (pinfunction "P2_P2") (pintype "passive"))
    )
    (net (code "1142") (name "Net-(CD34B-H2)") (class "Default")
      (node (ref "CD34") (pin "BH2") (pinfunction "H2_BH2") (pintype "passive"))
      (node (ref "D32") (pin "L2") (pinfunction "L2_L2") (pintype "passive"))
    )
    (net (code "1143") (name "Net-(CD34B-J2)") (class "Default")
      (node (ref "CD34") (pin "BJ2") (pinfunction "J2_BJ2") (pintype "passive"))
      (node (ref "D32") (pin "M2") (pinfunction "M2_M2") (pintype "passive"))
    )
    (net (code "1144") (name "Net-(CD34B-K2)") (class "Default")
      (node (ref "CD34") (pin "BK2") (pinfunction "K2_BK2") (pintype "passive"))
      (node (ref "D32") (pin "J2") (pinfunction "J2_J2") (pintype "passive"))
    )
    (net (code "1145") (name "Net-(CD34B-L2)") (class "Default")
      (node (ref "CD34") (pin "BL2") (pinfunction "L2_BL2") (pintype "passive"))
      (node (ref "D32") (pin "K2") (pinfunction "K2_K2") (pintype "passive"))
    )
    (net (code "1146") (name "Net-(CD34B-M2)") (class "Default")
      (node (ref "CD34") (pin "BM2") (pinfunction "M2_BM2") (pintype "passive"))
      (node (ref "D33") (pin "R2") (pinfunction "R2_R2") (pintype "passive"))
    )
    (net (code "1147") (name "Net-(CD34B-N2)") (class "Default")
      (node (ref "CD34") (pin "BN2") (pinfunction "N2_BN2") (pintype "passive"))
      (node (ref "D33") (pin "S2") (pinfunction "S2_S2") (pintype "passive"))
    )
    (net (code "1148") (name "Net-(CD34B-P2)") (class "Default")
      (node (ref "CD34") (pin "BP2") (pinfunction "P2_BP2") (pintype "passive"))
      (node (ref "D33") (pin "N2") (pinfunction "N2_N2") (pintype "passive"))
    )
    (net (code "1149") (name "Net-(CD34B-R2)") (class "Default")
      (node (ref "CD34") (pin "BR2") (pinfunction "R2_BR2") (pintype "passive"))
      (node (ref "D33") (pin "P2") (pinfunction "P2_P2") (pintype "passive"))
    )
    (net (code "1150") (name "Net-(CD34B-S2)") (class "Default")
      (node (ref "CD34") (pin "BS2") (pinfunction "S2_BS2") (pintype "passive"))
      (node (ref "D33") (pin "L2") (pinfunction "L2_L2") (pintype "passive"))
    )
    (net (code "1151") (name "Net-(CD34B-T2)") (class "Default")
      (node (ref "CD34") (pin "BT2") (pinfunction "T2_BT2") (pintype "passive"))
      (node (ref "D33") (pin "M2") (pinfunction "M2_M2") (pintype "passive"))
    )
    (net (code "1152") (name "Net-(CD34B-U2)") (class "Default")
      (node (ref "CD34") (pin "BU2") (pinfunction "U2_BU2") (pintype "passive"))
      (node (ref "D33") (pin "J2") (pinfunction "J2_J2") (pintype "passive"))
    )
    (net (code "1153") (name "Net-(CD34B-V2)") (class "Default")
      (node (ref "CD34") (pin "BV2") (pinfunction "V2_BV2") (pintype "passive"))
      (node (ref "D33") (pin "K2") (pinfunction "K2_K2") (pintype "passive"))
    )
    (net (code "1154") (name "Net-(CD36A-C2)") (class "Default")
      (node (ref "C37") (pin "K2") (pinfunction "K2_K2") (pintype "passive"))
      (node (ref "CD36") (pin "AC2") (pinfunction "C2_AC2") (pintype "passive"))
    )
    (net (code "1155") (name "Net-(CD36A-D2)") (class "Default")
      (node (ref "C37") (pin "J2") (pinfunction "J2_J2") (pintype "passive"))
      (node (ref "CD36") (pin "AD2") (pinfunction "D2_AD2") (pintype "passive"))
    )
    (net (code "1156") (name "Net-(CD36A-E2)") (class "Default")
      (node (ref "C37") (pin "M2") (pinfunction "M2_M2") (pintype "passive"))
      (node (ref "CD36") (pin "AE2") (pinfunction "E2_AE2") (pintype "passive"))
    )
    (net (code "1157") (name "Net-(CD36A-F2)") (class "Default")
      (node (ref "C37") (pin "L2") (pinfunction "L2_L2") (pintype "passive"))
      (node (ref "CD36") (pin "AF2") (pinfunction "F2_AF2") (pintype "passive"))
    )
    (net (code "1158") (name "Net-(CD36A-H2)") (class "Default")
      (node (ref "C37") (pin "P2") (pinfunction "P2_P2") (pintype "passive"))
      (node (ref "CD36") (pin "AH2") (pinfunction "H2_AH2") (pintype "passive"))
    )
    (net (code "1159") (name "Net-(CD36A-J2)") (class "Default")
      (node (ref "C37") (pin "N2") (pinfunction "N2_N2") (pintype "passive"))
      (node (ref "CD36") (pin "AJ2") (pinfunction "J2_AJ2") (pintype "passive"))
    )
    (net (code "1160") (name "Net-(CD36A-K2)") (class "Default")
      (node (ref "C37") (pin "S2") (pinfunction "S2_S2") (pintype "passive"))
      (node (ref "CD36") (pin "AK2") (pinfunction "K2_AK2") (pintype "passive"))
    )
    (net (code "1161") (name "Net-(CD36A-L2)") (class "Default")
      (node (ref "C37") (pin "R2") (pinfunction "R2_R2") (pintype "passive"))
      (node (ref "CD36") (pin "AL2") (pinfunction "L2_AL2") (pintype "passive"))
    )
    (net (code "1162") (name "Net-(CD36A-M2)") (class "Default")
      (node (ref "C38") (pin "K2") (pinfunction "K2_K2") (pintype "passive"))
      (node (ref "CD36") (pin "AM2") (pinfunction "M2_AM2") (pintype "passive"))
    )
    (net (code "1163") (name "Net-(CD36A-N2)") (class "Default")
      (node (ref "C38") (pin "J2") (pinfunction "J2_J2") (pintype "passive"))
      (node (ref "CD36") (pin "AN2") (pinfunction "N2_AN2") (pintype "passive"))
    )
    (net (code "1164") (name "Net-(CD36A-P2)") (class "Default")
      (node (ref "C38") (pin "M2") (pinfunction "M2_M2") (pintype "passive"))
      (node (ref "CD36") (pin "AP2") (pinfunction "P2_AP2") (pintype "passive"))
    )
    (net (code "1165") (name "Net-(CD36A-R2)") (class "Default")
      (node (ref "C38") (pin "L2") (pinfunction "L2_L2") (pintype "passive"))
      (node (ref "CD36") (pin "AR2") (pinfunction "R2_AR2") (pintype "passive"))
    )
    (net (code "1166") (name "Net-(CD36A-S2)") (class "Default")
      (node (ref "C38") (pin "P2") (pinfunction "P2_P2") (pintype "passive"))
      (node (ref "CD36") (pin "AS2") (pinfunction "S2_AS2") (pintype "passive"))
    )
    (net (code "1167") (name "Net-(CD36A-T2)") (class "Default")
      (node (ref "C38") (pin "N2") (pinfunction "N2_N2") (pintype "passive"))
      (node (ref "CD36") (pin "AT2") (pinfunction "T2_AT2") (pintype "passive"))
    )
    (net (code "1168") (name "Net-(CD36A-U2)") (class "Default")
      (node (ref "C38") (pin "S2") (pinfunction "S2_S2") (pintype "passive"))
      (node (ref "CD36") (pin "AU2") (pinfunction "U2_AU2") (pintype "passive"))
    )
    (net (code "1169") (name "Net-(CD36A-V2)") (class "Default")
      (node (ref "C38") (pin "R2") (pinfunction "R2_R2") (pintype "passive"))
      (node (ref "CD36") (pin "AV2") (pinfunction "V2_AV2") (pintype "passive"))
    )
    (net (code "1170") (name "Net-(CD36B-C2)") (class "Default")
      (node (ref "CD36") (pin "BC2") (pinfunction "C2_BC2") (pintype "passive"))
      (node (ref "D37") (pin "R2") (pinfunction "R2_R2") (pintype "passive"))
    )
    (net (code "1171") (name "Net-(CD36B-D2)") (class "Default")
      (node (ref "CD36") (pin "BD2") (pinfunction "D2_BD2") (pintype "passive"))
      (node (ref "D37") (pin "S2") (pinfunction "S2_S2") (pintype "passive"))
    )
    (net (code "1172") (name "Net-(CD36B-E2)") (class "Default")
      (node (ref "CD36") (pin "BE2") (pinfunction "E2_BE2") (pintype "passive"))
      (node (ref "D37") (pin "N2") (pinfunction "N2_N2") (pintype "passive"))
    )
    (net (code "1173") (name "Net-(CD36B-F2)") (class "Default")
      (node (ref "CD36") (pin "BF2") (pinfunction "F2_BF2") (pintype "passive"))
      (node (ref "D37") (pin "P2") (pinfunction "P2_P2") (pintype "passive"))
    )
    (net (code "1174") (name "Net-(CD36B-H2)") (class "Default")
      (node (ref "CD36") (pin "BH2") (pinfunction "H2_BH2") (pintype "passive"))
      (node (ref "D37") (pin "L2") (pinfunction "L2_L2") (pintype "passive"))
    )
    (net (code "1175") (name "Net-(CD36B-J2)") (class "Default")
      (node (ref "CD36") (pin "BJ2") (pinfunction "J2_BJ2") (pintype "passive"))
      (node (ref "D37") (pin "M2") (pinfunction "M2_M2") (pintype "passive"))
    )
    (net (code "1176") (name "Net-(CD36B-K2)") (class "Default")
      (node (ref "CD36") (pin "BK2") (pinfunction "K2_BK2") (pintype "passive"))
      (node (ref "D37") (pin "J2") (pinfunction "J2_J2") (pintype "passive"))
    )
    (net (code "1177") (name "Net-(CD36B-L2)") (class "Default")
      (node (ref "CD36") (pin "BL2") (pinfunction "L2_BL2") (pintype "passive"))
      (node (ref "D37") (pin "K2") (pinfunction "K2_K2") (pintype "passive"))
    )
    (net (code "1178") (name "Net-(CD36B-M2)") (class "Default")
      (node (ref "CD36") (pin "BM2") (pinfunction "M2_BM2") (pintype "passive"))
      (node (ref "D38") (pin "R2") (pinfunction "R2_R2") (pintype "passive"))
    )
    (net (code "1179") (name "Net-(CD36B-N2)") (class "Default")
      (node (ref "CD36") (pin "BN2") (pinfunction "N2_BN2") (pintype "passive"))
      (node (ref "D38") (pin "S2") (pinfunction "S2_S2") (pintype "passive"))
    )
    (net (code "1180") (name "Net-(CD36B-P2)") (class "Default")
      (node (ref "CD36") (pin "BP2") (pinfunction "P2_BP2") (pintype "passive"))
      (node (ref "D38") (pin "N2") (pinfunction "N2_N2") (pintype "passive"))
    )
    (net (code "1181") (name "Net-(CD36B-R2)") (class "Default")
      (node (ref "CD36") (pin "BR2") (pinfunction "R2_BR2") (pintype "passive"))
      (node (ref "D38") (pin "P2") (pinfunction "P2_P2") (pintype "passive"))
    )
    (net (code "1182") (name "Net-(CD36B-S2)") (class "Default")
      (node (ref "CD36") (pin "BS2") (pinfunction "S2_BS2") (pintype "passive"))
      (node (ref "D38") (pin "L2") (pinfunction "L2_L2") (pintype "passive"))
    )
    (net (code "1183") (name "Net-(CD36B-T2)") (class "Default")
      (node (ref "CD36") (pin "BT2") (pinfunction "T2_BT2") (pintype "passive"))
      (node (ref "D38") (pin "M2") (pinfunction "M2_M2") (pintype "passive"))
    )
    (net (code "1184") (name "Net-(CD36B-U2)") (class "Default")
      (node (ref "CD36") (pin "BU2") (pinfunction "U2_BU2") (pintype "passive"))
      (node (ref "D38") (pin "J2") (pinfunction "J2_J2") (pintype "passive"))
    )
    (net (code "1185") (name "Net-(CD36B-V2)") (class "Default")
      (node (ref "CD36") (pin "BV2") (pinfunction "V2_BV2") (pintype "passive"))
      (node (ref "D38") (pin "K2") (pinfunction "K2_K2") (pintype "passive"))
    )
    (net (code "1186") (name "Net-(D06A-IN)") (class "Default")
      (node (ref "D06") (pin "E1") (pinfunction "IN_E1") (pintype "input"))
      (node (ref "D06") (pin "R2") (pinfunction "R2_R2") (pintype "output"))
    )
    (net (code "1187") (name "Net-(D07A-IN1)") (class "Default")
      (node (ref "D07") (pin "A1") (pinfunction "IN1_A1") (pintype "input"))
      (node (ref "D07") (pin "D1") (pinfunction "IN1_D1") (pintype "input"))
      (node (ref "D07") (pin "F2") (pinfunction "OUT_F2") (pintype "output"))
    )
    (net (code "1188") (name "Net-(D07F-IN2)") (class "Default")
      (node (ref "D06") (pin "H2") (pinfunction "H2_H2") (pintype "input"))
      (node (ref "D07") (pin "J1") (pinfunction "IN2_J1") (pintype "input"))
      (node (ref "D07") (pin "S2") (pinfunction "OUT_S2") (pintype "output"))
    )
    (net (code "1189") (name "Net-(D07G-IN2)") (class "Default")
      (node (ref "D07") (pin "J2") (pinfunction "IN2_J2") (pintype "input"))
      (node (ref "D08") (pin "F1") (pinfunction "OUT_F1") (pintype "output"))
    )
    (net (code "1190") (name "Net-(D07G-OUT)") (class "Default")
      (node (ref "D07") (pin "K2") (pinfunction "OUT_K2") (pintype "output"))
      (node (ref "E09") (pin "H1") (pinfunction "IN1_H1") (pintype "input"))
    )
    (net (code "1191") (name "Net-(D07H-OUT)") (class "Default")
      (node (ref "D07") (pin "M2") (pinfunction "IN2_M2") (pintype "input"))
      (node (ref "D07") (pin "N1") (pinfunction "OUT_N1") (pintype "output"))
    )
    (net (code "1192") (name "Net-(D07I-OUT)") (class "Default")
      (node (ref "D07") (pin "N2") (pinfunction "OUT_N2") (pintype "output"))
      (node (ref "D08") (pin "H2") (pinfunction "H2_H2") (pintype "input"))
    )
    (net (code "1193") (name "Net-(D07J-OUT)") (class "Default")
      (node (ref "D07") (pin "S1") (pinfunction "OUT_S1") (pintype "output"))
      (node (ref "E09") (pin "D1") (pinfunction "IN1_D1") (pintype "input"))
    )
    (net (code "1194") (name "Net-(D07K-IN2)") (class "Default")
      (node (ref "D07") (pin "R2") (pinfunction "IN2_R2") (pintype "input"))
      (node (ref "D07") (pin "V2") (pinfunction "OUT_V2") (pintype "output"))
    )
    (net (code "1195") (name "Net-(D08A-IN)") (class "Default")
      (node (ref "D08") (pin "E1") (pinfunction "IN_E1") (pintype "input"))
      (node (ref "D08") (pin "R2") (pinfunction "R2_R2") (pintype "output"))
    )
    (net (code "1196") (name "Net-(D09I-OUT)") (class "Default")
      (node (ref "D09") (pin "T2") (pinfunction "IN1_T2") (pintype "input"))
      (node (ref "D09") (pin "U1") (pinfunction "OUT_U1") (pintype "output"))
    )
    (net (code "1197") (name "Net-(D12B-IN1)") (class "Default")
      (node (ref "D12") (pin "D1") (pinfunction "IN1_D1") (pintype "input"))
      (node (ref "D12") (pin "F2") (pinfunction "OUT_F2") (pintype "output"))
    )
    (net (code "1198") (name "Net-(D12B-OUT)") (class "Default")
      (node (ref "D12") (pin "F1") (pinfunction "OUT_F1") (pintype "output"))
      (node (ref "D23") (pin "S1") (pinfunction "IN1A_S1") (pintype "input"))
    )
    (net (code "1199") (name "Net-(D12H-OUT)") (class "Default")
      (node (ref "D12") (pin "N1") (pinfunction "OUT_N1") (pintype "output"))
      (node (ref "D24") (pin "U2") (pinfunction "S_U2") (pintype "input"))
    )
    (net (code "1200") (name "Net-(D12I-OUT)") (class "Default")
      (node (ref "D12") (pin "N2") (pinfunction "OUT_N2") (pintype "output"))
      (node (ref "D24") (pin "T2") (pinfunction "D_T2") (pintype "input"))
    )
    (net (code "1201") (name "Net-(D12J-OUT)") (class "Default")
      (node (ref "D12") (pin "S1") (pinfunction "OUT_S1") (pintype "output"))
      (node (ref "D24") (pin "S2") (pinfunction "C_S2") (pintype "input"))
    )
    (net (code "1202") (name "Net-(D12K-OUT)") (class "Default")
      (node (ref "D12") (pin "S2") (pinfunction "OUT_S2") (pintype "output"))
      (node (ref "D22") (pin "U2") (pinfunction "IN4_U2") (pintype "input"))
    )
    (net (code "1203") (name "Net-(D13B-OUT)") (class "Default")
      (node (ref "D13") (pin "F1") (pinfunction "OUT_F1") (pintype "output"))
      (node (ref "D17") (pin "R1") (pinfunction "IN2_R1") (pintype "input"))
    )
    (net (code "1204") (name "Net-(D13C-OUT)") (class "Default")
      (node (ref "D13") (pin "F2") (pinfunction "OUT_F2") (pintype "output"))
      (node (ref "D17") (pin "R2") (pinfunction "IN3_R2") (pintype "input"))
    )
    (net (code "1205") (name "Net-(D13G-IN1)") (class "Default")
      (node (ref "D13") (pin "H2") (pinfunction "IN1_H2") (pintype "input"))
      (node (ref "D20") (pin "S1") (pinfunction "OUT_S1") (pintype "output"))
    )
    (net (code "1206") (name "Net-(D13H-IN1)") (class "Default")
      (node (ref "D13") (pin "L1") (pinfunction "IN1_L1") (pintype "input"))
      (node (ref "D13") (pin "S1") (pinfunction "OUT_S1") (pintype "output"))
    )
    (net (code "1207") (name "Net-(D13N-OUT)") (class "Default")
      (node (ref "D13") (pin "V2") (pinfunction "OUT_V2") (pintype "output"))
      (node (ref "D16") (pin "L1") (pinfunction "IN1_L1") (pintype "input"))
    )
    (net (code "1208") (name "Net-(D14B-OUT)") (class "Default")
      (node (ref "C13") (pin "H2") (pinfunction "H2_H2") (pintype "input"))
      (node (ref "D14") (pin "F1") (pinfunction "OUT_F1") (pintype "output"))
      (node (ref "D24") (pin "L2") (pinfunction "C_L2") (pintype "input"))
    )
    (net (code "1209") (name "Net-(D14C-OUT)") (class "Default")
      (node (ref "D14") (pin "F2") (pinfunction "OUT_F2") (pintype "output"))
      (node (ref "D14") (pin "J2") (pinfunction "IN2_J2") (pintype "input"))
    )
    (net (code "1210") (name "Net-(D14G-IN1)") (class "Default")
      (node (ref "D14") (pin "H2") (pinfunction "IN1_H2") (pintype "input"))
      (node (ref "D14") (pin "N2") (pinfunction "OUT_N2") (pintype "output"))
    )
    (net (code "1211") (name "Net-(D14H-OUT)") (class "Default")
      (node (ref "D14") (pin "N1") (pinfunction "OUT_N1") (pintype "output"))
      (node (ref "D19") (pin "F2") (pinfunction "IN3_F2") (pintype "input"))
    )
    (net (code "1212") (name "Net-(D14J-IN2)") (class "Default")
      (node (ref "D14") (pin "R1") (pinfunction "IN2_R1") (pintype "input"))
      (node (ref "D14") (pin "S2") (pinfunction "OUT_S2") (pintype "output"))
    )
    (net (code "1213") (name "Net-(D14J-OUT)") (class "Default")
      (node (ref "D14") (pin "S1") (pinfunction "OUT_S1") (pintype "output"))
      (node (ref "D24") (pin "B1") (pinfunction "C_B1") (pintype "input"))
      (node (ref "D24") (pin "D2") (pinfunction "C_D2") (pintype "input"))
      (node (ref "D24") (pin "H1") (pinfunction "C_H1") (pintype "input"))
    )
    (net (code "1214") (name "Net-(D14N-OUT)") (class "Default")
      (node (ref "D14") (pin "V2") (pinfunction "OUT_V2") (pintype "output"))
      (node (ref "D22") (pin "S2") (pinfunction "IN2_S2") (pintype "input"))
    )
    (net (code "1215") (name "Net-(D15A-OUT)") (class "Default")
      (node (ref "D15") (pin "C1") (pinfunction "OUT_C1") (pintype "output"))
      (node (ref "D17") (pin "D2") (pinfunction "IN1_D2") (pintype "input"))
    )
    (net (code "1216") (name "Net-(D15B-OUT)") (class "Default")
      (node (ref "D15") (pin "F1") (pinfunction "OUT_F1") (pintype "output"))
      (node (ref "D17") (pin "F2") (pinfunction "IN3_F2") (pintype "input"))
    )
    (net (code "1217") (name "Net-(D15C-IN2)") (class "Default")
      (node (ref "D15") (pin "E2") (pinfunction "IN2_E2") (pintype "input"))
      (node (ref "D21") (pin "E1") (pinfunction "OUT_E1") (pintype "output"))
    )
    (net (code "1218") (name "Net-(D15G-OUT)") (class "Default")
      (node (ref "D15") (pin "K2") (pinfunction "OUT_K2") (pintype "output"))
      (node (ref "D15") (pin "L1") (pinfunction "IN1_L1") (pintype "input"))
    )
    (net (code "1219") (name "Net-(D15H-OUT)") (class "Default")
      (node (ref "D15") (pin "N1") (pinfunction "OUT_N1") (pintype "output"))
      (node (ref "D24") (pin "M2") (pinfunction "D_M2") (pintype "input"))
    )
    (net (code "1220") (name "Net-(D15I-IN1)") (class "Default")
      (node (ref "D15") (pin "L2") (pinfunction "IN1_L2") (pintype "input"))
      (node (ref "D21") (pin "J2") (pinfunction "OUT_J2") (pintype "output"))
    )
    (net (code "1221") (name "Net-(D15K-OUT)") (class "Default")
      (node (ref "D15") (pin "S2") (pinfunction "OUT_S2") (pintype "output"))
      (node (ref "D20") (pin "K1") (pinfunction "IN4_K1") (pintype "input"))
    )
    (net (code "1222") (name "Net-(D15N-IN1)") (class "Default")
      (node (ref "D15") (pin "T2") (pinfunction "IN1_T2") (pintype "input"))
      (node (ref "D17") (pin "S1") (pinfunction "IN3_S1") (pintype "input"))
      (node (ref "D18") (pin "D1") (pinfunction "OUT_D1") (pintype "output"))
    )
    (net (code "1223") (name "Net-(D16A-IN2)") (class "Default")
      (node (ref "D16") (pin "B1") (pinfunction "IN2_B1") (pintype "input"))
      (node (ref "D21") (pin "P2") (pinfunction "OUT_P2") (pintype "output"))
    )
    (net (code "1224") (name "Net-(D16A-OUT)") (class "Default")
      (node (ref "D16") (pin "C1") (pinfunction "OUT_C1") (pintype "output"))
      (node (ref "D21") (pin "A1") (pinfunction "IN1_A1") (pintype "input"))
    )
    (net (code "1225") (name "Net-(D16B-IN2)") (class "Default")
      (node (ref "D16") (pin "E1") (pinfunction "IN2_E1") (pintype "input"))
      (node (ref "D21") (pin "S1") (pinfunction "OUT_S1") (pintype "output"))
    )
    (net (code "1226") (name "Net-(D16B-OUT)") (class "Default")
      (node (ref "D16") (pin "F1") (pinfunction "OUT_F1") (pintype "output"))
      (node (ref "D21") (pin "B1") (pinfunction "IN2_B1") (pintype "input"))
    )
    (net (code "1227") (name "Net-(D16C-IN2)") (class "Default")
      (node (ref "D16") (pin "E2") (pinfunction "IN2_E2") (pintype "input"))
      (node (ref "D21") (pin "V2") (pinfunction "OUT_V2") (pintype "output"))
    )
    (net (code "1228") (name "Net-(D16C-OUT)") (class "Default")
      (node (ref "D16") (pin "F2") (pinfunction "OUT_F2") (pintype "output"))
      (node (ref "D21") (pin "C1") (pinfunction "IN3_C1") (pintype "input"))
    )
    (net (code "1229") (name "Net-(D16F-IN1)") (class "Default")
      (node (ref "D16") (pin "H1") (pinfunction "IN1_H1") (pintype "input"))
      (node (ref "D19") (pin "J1") (pinfunction "OUT_J1") (pintype "output"))
    )
    (net (code "1230") (name "Net-(D16F-IN2)") (class "Default")
      (node (ref "D16") (pin "J1") (pinfunction "IN2_J1") (pintype "input"))
      (node (ref "D19") (pin "M2") (pinfunction "OUT_M2") (pintype "output"))
    )
    (net (code "1231") (name "Net-(D16G-OUT)") (class "Default")
      (node (ref "D16") (pin "K2") (pinfunction "OUT_K2") (pintype "output"))
      (node (ref "D19") (pin "D2") (pinfunction "IN1_D2") (pintype "input"))
    )
    (net (code "1232") (name "Net-(D16H-OUT)") (class "Default")
      (node (ref "D16") (pin "L2") (pinfunction "IN1_L2") (pintype "input"))
      (node (ref "D16") (pin "N1") (pinfunction "OUT_N1") (pintype "output"))
      (node (ref "D18") (pin "P2") (pinfunction "IN2_P2") (pintype "input"))
    )
    (net (code "1233") (name "Net-(D16I-OUT)") (class "Default")
      (node (ref "D16") (pin "N2") (pinfunction "OUT_N2") (pintype "output"))
      (node (ref "D18") (pin "R1") (pinfunction "IN2_R1") (pintype "input"))
    )
    (net (code "1234") (name "Net-(D17D-IN2)") (class "Default")
      (node (ref "D17") (pin "E2") (pinfunction "IN2_E2") (pintype "input"))
      (node (ref "D20") (pin "E1") (pinfunction "OUT_E1") (pintype "output"))
    )
    (net (code "1235") (name "Net-(D17E-OUT)") (class "Default")
      (node (ref "D17") (pin "J1") (pinfunction "OUT_J1") (pintype "output"))
      (node (ref "D17") (pin "K2") (pinfunction "IN2_K2") (pintype "input"))
      (node (ref "D20") (pin "F2") (pinfunction "IN3_F2") (pintype "input"))
    )
    (net (code "1236") (name "Net-(D17G-IN2)") (class "Default")
      (node (ref "D17") (pin "L1") (pinfunction "IN2_L1") (pintype "input"))
      (node (ref "D17") (pin "S2") (pinfunction "OUT_S2") (pintype "output"))
    )
    (net (code "1237") (name "Net-(D17H-IN2)") (class "Default")
      (node (ref "D17") (pin "P2") (pinfunction "IN2_P2") (pintype "input"))
      (node (ref "D23") (pin "V2") (pinfunction "OUT_V2") (pintype "output"))
    )
    (net (code "1238") (name "Net-(D18D-OUT)") (class "Default")
      (node (ref "D18") (pin "H2") (pinfunction "OUT_H2") (pintype "output"))
      (node (ref "D22") (pin "F1") (pinfunction "IN1_F1") (pintype "input"))
    )
    (net (code "1239") (name "Net-(D18E-OUT)") (class "Default")
      (node (ref "D18") (pin "J1") (pinfunction "OUT_J1") (pintype "output"))
      (node (ref "D22") (pin "K2") (pinfunction "IN1_K2") (pintype "input"))
    )
    (net (code "1240") (name "Net-(D18G-OUT)") (class "Default")
      (node (ref "D18") (pin "N1") (pinfunction "OUT_N1") (pintype "output"))
      (node (ref "D22") (pin "R1") (pinfunction "IN4_R1") (pintype "input"))
    )
    (net (code "1241") (name "Net-(D19D-IN2)") (class "Default")
      (node (ref "D19") (pin "E2") (pinfunction "IN2_E2") (pintype "input"))
      (node (ref "D19") (pin "N1") (pinfunction "OUT_N1") (pintype "output"))
    )
    (net (code "1242") (name "Net-(D19D-OUT)") (class "Default")
      (node (ref "D19") (pin "H2") (pinfunction "OUT_H2") (pintype "output"))
      (node (ref "D23") (pin "P1") (pinfunction "IN5C_P1") (pintype "input"))
    )
    (net (code "1243") (name "Net-(D20E-IN2)") (class "Default")
      (node (ref "D20") (pin "H1") (pinfunction "IN2_H1") (pintype "input"))
      (node (ref "D20") (pin "P2") (pinfunction "OUT_P2") (pintype "output"))
    )
    (net (code "1244") (name "Net-(E09A-OUT)") (class "Default")
      (node (ref "E09") (pin "C1") (pinfunction "OUT_C1") (pintype "output"))
      (node (ref "E09") (pin "E1") (pinfunction "IN2_E1") (pintype "input"))
    )
    (net (code "1245") (name "Net-(E09C-OUT)") (class "Default")
      (node (ref "E09") (pin "F2") (pinfunction "OUT_F2") (pintype "output"))
      (node (ref "E09") (pin "J1") (pinfunction "IN2_J1") (pintype "input"))
    )
    (net (code "1246") (name "Net-(E09F-OUT)") (class "Default")
      (node (ref "A23") (pin "H2") (pinfunction "H2_H2") (pintype "input"))
      (node (ref "E09") (pin "K1") (pinfunction "OUT_K1") (pintype "output"))
    )
    (net (code "1247") (name "Net-(E09G-OUT)") (class "Default")
      (node (ref "E09") (pin "K2") (pinfunction "OUT_K2") (pintype "output"))
      (node (ref "F11") (pin "K2") (pinfunction "IN1_K2") (pintype "input"))
    )
    (net (code "1248") (name "Net-(E11J-IN1)") (class "Default")
      (node (ref "E11") (pin "P1") (pinfunction "IN1_P1") (pintype "input"))
      (node (ref "F11") (pin "L1") (pinfunction "OUT_L1") (pintype "output"))
    )
    (net (code "1249") (name "Net-(E11N-OUT)") (class "Default")
      (node (ref "E11") (pin "V2") (pinfunction "OUT_V2") (pintype "output"))
      (node (ref "E12") (pin "R2") (pinfunction "IN2_R2") (pintype "input"))
    )
    (net (code "1250") (name "Net-(E12A-IN1)") (class "Default")
      (node (ref "E12") (pin "A1") (pinfunction "IN1_A1") (pintype "input"))
      (node (ref "E12") (pin "F1") (pinfunction "OUT_F1") (pintype "output"))
    )
    (net (code "1251") (name "Net-(E12A-OUT)") (class "Default")
      (node (ref "E12") (pin "C1") (pinfunction "OUT_C1") (pintype "output"))
      (node (ref "E18") (pin "K1") (pinfunction "S_K1") (pintype "input"))
    )
    (net (code "1252") (name "Net-(E12C-OUT)") (class "Default")
      (node (ref "E12") (pin "F2") (pinfunction "OUT_F2") (pintype "output"))
      (node (ref "E16") (pin "H2") (pinfunction "H2_H2") (pintype "input"))
    )
    (net (code "1253") (name "Net-(E12J-IN1)") (class "Default")
      (node (ref "E12") (pin "P1") (pinfunction "IN1_P1") (pintype "input"))
      (node (ref "F19") (pin "P2") (pinfunction "OUT_P2") (pintype "output"))
    )
    (net (code "1254") (name "Net-(E12K-OUT)") (class "Default")
      (node (ref "E12") (pin "S2") (pinfunction "OUT_S2") (pintype "output"))
      (node (ref "F21") (pin "A1") (pinfunction "IN1_A1") (pintype "input"))
    )
    (net (code "1255") (name "Net-(E12N-IN2)") (class "Default")
      (node (ref "E12") (pin "U2") (pinfunction "IN2_U2") (pintype "input"))
      (node (ref "F19") (pin "S1") (pinfunction "OUT_S1") (pintype "output"))
    )
    (net (code "1256") (name "Net-(E13C-OUT)") (class "Default")
      (node (ref "E13") (pin "R1") (pinfunction "OUT_R1") (pintype "output"))
      (node (ref "E18") (pin "M2") (pinfunction "D_M2") (pintype "input"))
    )
    (net (code "1257") (name "Net-(E14A-OUT)") (class "Default")
      (node (ref "E14") (pin "D1") (pinfunction "OUT_D1") (pintype "output"))
      (node (ref "E15") (pin "D2") (pinfunction "IN1_D2") (pintype "input"))
      (node (ref "E15") (pin "E1") (pinfunction "IN2_E1") (pintype "input"))
      (node (ref "F08") (pin "J2") (pinfunction "IN2_J2") (pintype "input"))
    )
    (net (code "1258") (name "Net-(E14D-OUT)") (class "Default")
      (node (ref "E14") (pin "H2") (pinfunction "OUT_H2") (pintype "output"))
      (node (ref "F09") (pin "K2") (pinfunction "IN5_K2") (pintype "input"))
    )
    (net (code "1259") (name "Net-(E14E-IN1)") (class "Default")
      (node (ref "E14") (pin "E1") (pinfunction "IN1_E1") (pintype "input"))
      (node (ref "F19") (pin "K1") (pinfunction "IN4_K1") (pintype "input"))
      (node (ref "F21") (pin "S2") (pinfunction "OUT_S2") (pintype "output"))
      (node (ref "F21") (pin "U2") (pinfunction "IN2_U2") (pintype "input"))
    )
    (net (code "1260") (name "Net-(E14E-IN2)") (class "Default")
      (node (ref "E14") (pin "F1") (pinfunction "IN2_F1") (pintype "input"))
      (node (ref "F19") (pin "J1") (pinfunction "IN3_J1") (pintype "input"))
      (node (ref "F21") (pin "S1") (pinfunction "OUT_S1") (pintype "output"))
      (node (ref "F21") (pin "T2") (pinfunction "IN1_T2") (pintype "input"))
    )
    (net (code "1261") (name "Net-(E14G-OUT)") (class "Default")
      (node (ref "E14") (pin "N1") (pinfunction "OUT_N1") (pintype "output"))
      (node (ref "E14") (pin "N2") (pinfunction "IN1_N2") (pintype "input"))
    )
    (net (code "1262") (name "Net-(E14I-OUT)") (class "Default")
      (node (ref "E14") (pin "U1") (pinfunction "OUT_U1") (pintype "output"))
      (node (ref "F12") (pin "H2") (pinfunction "H2_H2") (pintype "input"))
    )
    (net (code "1263") (name "Net-(E14J-OUT)") (class "Default")
      (node (ref "E14") (pin "V1") (pinfunction "OUT_V1") (pintype "output"))
      (node (ref "E15") (pin "T2") (pinfunction "IN1_T2") (pintype "input"))
    )
    (net (code "1264") (name "Net-(E15A-OUT)") (class "Default")
      (node (ref "E15") (pin "C1") (pinfunction "OUT_C1") (pintype "output"))
      (node (ref "E15") (pin "D1") (pinfunction "IN1_D1") (pintype "input"))
      (node (ref "F08") (pin "H2") (pinfunction "IN1_H2") (pintype "input"))
    )
    (net (code "1265") (name "Net-(E15C-IN2)") (class "Default")
      (node (ref "E15") (pin "E2") (pinfunction "IN2_E2") (pintype "input"))
      (node (ref "E15") (pin "K1") (pinfunction "OUT_K1") (pintype "output"))
    )
    (net (code "1266") (name "Net-(E15H-OUT)") (class "Default")
      (node (ref "E15") (pin "N1") (pinfunction "OUT_N1") (pintype "output"))
      (node (ref "E19") (pin "F2") (pinfunction "S_F2") (pintype "input"))
      (node (ref "F08") (pin "N2") (pinfunction "IN1_N2") (pintype "input"))
    )
    (net (code "1267") (name "Net-(E15K-OUT)") (class "Default")
      (node (ref "E15") (pin "S2") (pinfunction "OUT_S2") (pintype "output"))
      (node (ref "F13") (pin "H2") (pinfunction "H2_H2") (pintype "input"))
    )
    (net (code "1268") (name "Net-(E16A-IN)") (class "Default")
      (node (ref "E16") (pin "E1") (pinfunction "IN_E1") (pintype "input"))
      (node (ref "E16") (pin "R2") (pinfunction "R2_R2") (pintype "output"))
    )
    (net (code "1269") (name "Net-(E16A-OUT)") (class "Default")
      (node (ref "E16") (pin "F1") (pinfunction "OUT_F1") (pintype "output"))
      (node (ref "E18") (pin "H1") (pinfunction "C_H1") (pintype "input"))
    )
    (net (code "1270") (name "Net-(E17A-IN)") (class "Default")
      (node (ref "E17") (pin "E1") (pinfunction "IN_E1") (pintype "input"))
      (node (ref "E17") (pin "M2") (pinfunction "M2_M2") (pintype "output"))
    )
    (net (code "1271") (name "Net-(E17E-IN)") (class "Default")
      (node (ref "E17") (pin "H1") (pinfunction "IN_H1") (pintype "input"))
      (node (ref "E17") (pin "U2") (pinfunction "U2_U2") (pintype "output"))
    )
    (net (code "1272") (name "Net-(E18G-C)") (class "Default")
      (node (ref "E18") (pin "N1") (pinfunction "C_N1") (pintype "input"))
      (node (ref "E25") (pin "U1") (pinfunction "OUT_U1") (pintype "output"))
    )
    (net (code "1273") (name "Net-(E18G-D)") (class "Default")
      (node (ref "E18") (pin "P1") (pinfunction "D_P1") (pintype "input"))
      (node (ref "E28") (pin "T2") (pinfunction "OUT_T2") (pintype "output"))
    )
    (net (code "1274") (name "Net-(E20A-C)") (class "Default")
      (node (ref "E20") (pin "B1") (pinfunction "C_B1") (pintype "input"))
      (node (ref "E20") (pin "D2") (pinfunction "C_D2") (pintype "input"))
      (node (ref "E20") (pin "H1") (pinfunction "C_H1") (pintype "input"))
      (node (ref "E22") (pin "S1") (pinfunction "OUT_S1") (pintype "output"))
    )
    (net (code "1275") (name "Net-(E20A-D)") (class "Default")
      (node (ref "E20") (pin "C1") (pinfunction "D_C1") (pintype "input"))
      (node (ref "F22") (pin "C1") (pinfunction "OUT_C1") (pintype "output"))
    )
    (net (code "1276") (name "Net-(E20A-R)") (class "Default")
      (node (ref "E20") (pin "A1") (pinfunction "R_A1") (pintype "input"))
      (node (ref "E24") (pin "K2") (pinfunction "OUT_K2") (pintype "output"))
    )
    (net (code "1277") (name "Net-(E23A-S)") (class "Default")
      (node (ref "E23") (pin "D1") (pinfunction "S_D1") (pintype "input"))
      (node (ref "F22") (pin "F2") (pinfunction "OUT_F2") (pintype "output"))
    )
    (net (code "1278") (name "Net-(E24A-OUT)") (class "Default")
      (node (ref "E24") (pin "C1") (pinfunction "OUT_C1") (pintype "output"))
      (node (ref "E25") (pin "A1") (pinfunction "IN1_A1") (pintype "input"))
    )
    (net (code "1279") (name "Net-(E24B-OUT)") (class "Default")
      (node (ref "E24") (pin "F1") (pinfunction "OUT_F1") (pintype "output"))
      (node (ref "F23") (pin "E2") (pinfunction "IN2_E2") (pintype "input"))
    )
    (net (code "1280") (name "Net-(E24F-IN1)") (class "Default")
      (node (ref "E24") (pin "H1") (pinfunction "IN1_H1") (pintype "input"))
      (node (ref "E25") (pin "J1") (pinfunction "OUT_J1") (pintype "output"))
    )
    (net (code "1281") (name "Net-(E24H-OUT)") (class "Default")
      (node (ref "E24") (pin "N1") (pinfunction "OUT_N1") (pintype "output"))
      (node (ref "E25") (pin "K1") (pinfunction "IN1_K1") (pintype "input"))
    )
    (net (code "1282") (name "Net-(E24I-IN1)") (class "Default")
      (node (ref "E24") (pin "L2") (pinfunction "IN1_L2") (pintype "input"))
      (node (ref "F24") (pin "P2") (pinfunction "OUT_P2") (pintype "output"))
    )
    (net (code "1283") (name "Net-(E24I-OUT)") (class "Default")
      (node (ref "E24") (pin "N2") (pinfunction "OUT_N2") (pintype "output"))
      (node (ref "F23") (pin "A1") (pinfunction "IN1_A1") (pintype "input"))
    )
    (net (code "1284") (name "Net-(E24J-IN2)") (class "Default")
      (node (ref "E24") (pin "R1") (pinfunction "IN2_R1") (pintype "input"))
      (node (ref "F24") (pin "S1") (pinfunction "OUT_S1") (pintype "output"))
    )
    (net (code "1285") (name "Net-(E24K-IN2)") (class "Default")
      (node (ref "E24") (pin "R2") (pinfunction "IN2_R2") (pintype "input"))
      (node (ref "F24") (pin "V2") (pinfunction "OUT_V2") (pintype "output"))
    )
    (net (code "1286") (name "Net-(E24N-OUT)") (class "Default")
      (node (ref "E24") (pin "V2") (pinfunction "OUT_V2") (pintype "output"))
      (node (ref "E25") (pin "M1") (pinfunction "IN3_M1") (pintype "input"))
    )
    (net (code "1287") (name "Net-(E25G-IN2)") (class "Default")
      (node (ref "E25") (pin "L1") (pinfunction "IN2_L1") (pintype "input"))
      (node (ref "F23") (pin "E1") (pinfunction "OUT_E1") (pintype "output"))
    )
    (net (code "1288") (name "Net-(E25G-OUT)") (class "Default")
      (node (ref "E25") (pin "N1") (pinfunction "OUT_N1") (pintype "output"))
      (node (ref "E25") (pin "P2") (pinfunction "IN2_P2") (pintype "input"))
    )
    (net (code "1289") (name "Net-(E25H-OUT)") (class "Default")
      (node (ref "E25") (pin "S2") (pinfunction "OUT_S2") (pintype "output"))
      (node (ref "E28") (pin "N2") (pinfunction "IN4A_N2") (pintype "input"))
      (node (ref "F25") (pin "L2") (pinfunction "IN1_L2") (pintype "input"))
    )
    (net (code "1290") (name "Net-(E25I-IN1)") (class "Default")
      (node (ref "E25") (pin "P1") (pinfunction "IN1_P1") (pintype "input"))
      (node (ref "E25") (pin "V1") (pinfunction "OUT_V1") (pintype "output"))
    )
    (net (code "1291") (name "Net-(E25I-IN3)") (class "Default")
      (node (ref "E25") (pin "S1") (pinfunction "IN3_S1") (pintype "input"))
      (node (ref "F25") (pin "V2") (pinfunction "OUT_V2") (pintype "output"))
    )
    (net (code "1292") (name "Net-(E26C-OUT)") (class "Default")
      (node (ref "E26") (pin "R1") (pinfunction "OUT_R1") (pintype "output"))
      (node (ref "E32") (pin "F2") (pinfunction "IN3_F2") (pintype "input"))
    )
    (net (code "1293") (name "Net-(E26D-IN1C)") (class "Default")
      (node (ref "E26") (pin "F2") (pinfunction "IN1C_F2") (pintype "input"))
      (node (ref "F26") (pin "V1") (pinfunction "OUT_V1") (pintype "output"))
    )
    (net (code "1294") (name "Net-(E26D-OUT)") (class "Default")
      (node (ref "E26") (pin "T2") (pinfunction "OUT_T2") (pintype "output"))
      (node (ref "E32") (pin "L2") (pinfunction "IN2_L2") (pintype "input"))
    )
    (net (code "1295") (name "Net-(E27C-IN4A)") (class "Default")
      (node (ref "E27") (pin "K1") (pinfunction "IN4A_K1") (pintype "input"))
      (node (ref "F11") (pin "S1") (pinfunction "OUT_S1") (pintype "output"))
    )
    (net (code "1296") (name "Net-(E27C-OUT)") (class "Default")
      (node (ref "E27") (pin "R1") (pinfunction "OUT_R1") (pintype "output"))
      (node (ref "F27") (pin "L2") (pinfunction "IN2_L2") (pintype "input"))
    )
    (net (code "1297") (name "Net-(E27D-OUT)") (class "Default")
      (node (ref "E27") (pin "T2") (pinfunction "OUT_T2") (pintype "output"))
      (node (ref "F27") (pin "M2") (pinfunction "IN3_M2") (pintype "input"))
    )
    (net (code "1298") (name "Net-(E28D-IN3A)") (class "Default")
      (node (ref "E28") (pin "L2") (pinfunction "IN3A_L2") (pintype "input"))
      (node (ref "F25") (pin "N2") (pinfunction "OUT_N2") (pintype "output"))
    )
    (net (code "1299") (name "Net-(E29C-IN2B)") (class "Default")
      (node (ref "E29") (pin "F1") (pinfunction "IN2B_F1") (pintype "input"))
      (node (ref "E29") (pin "T2") (pinfunction "OUT_T2") (pintype "output"))
    )
    (net (code "1300") (name "Net-(E29C-OUT)") (class "Default")
      (node (ref "E29") (pin "R1") (pinfunction "OUT_R1") (pintype "output"))
      (node (ref "F31") (pin "B1") (pinfunction "IN2_B1") (pintype "input"))
    )
    (net (code "1301") (name "Net-(E30C-OUT)") (class "Default")
      (node (ref "E30") (pin "R1") (pinfunction "OUT_R1") (pintype "output"))
      (node (ref "F31") (pin "H1") (pinfunction "IN2_H1") (pintype "input"))
      (node (ref "F31") (pin "K2") (pinfunction "IN1_K2") (pintype "input"))
    )
    (net (code "1302") (name "Net-(E30D-IN3B)") (class "Default")
      (node (ref "E30") (pin "M2") (pinfunction "IN3B_M2") (pintype "input"))
      (node (ref "E30") (pin "V2") (pinfunction "OUT_V2") (pintype "output"))
    )
    (net (code "1303") (name "Net-(E30D-OUT)") (class "Default")
      (node (ref "E30") (pin "T2") (pinfunction "OUT_T2") (pintype "output"))
      (node (ref "E32") (pin "N1") (pinfunction "IN2_N1") (pintype "input"))
    )
    (net (code "1304") (name "Net-(E31A-IN1)") (class "Default")
      (node (ref "E31") (pin "A1") (pinfunction "IN1_A1") (pintype "input"))
      (node (ref "F26") (pin "H2") (pinfunction "OUT_H2") (pintype "output"))
    )
    (net (code "1305") (name "Net-(E31D-IN4)") (class "Default")
      (node (ref "E31") (pin "H2") (pinfunction "IN4_H2") (pintype "input"))
      (node (ref "F26") (pin "D1") (pinfunction "OUT_D1") (pintype "output"))
    )
    (net (code "1306") (name "Net-(E31E-IN3)") (class "Default")
      (node (ref "E31") (pin "J1") (pinfunction "IN3_J1") (pintype "input"))
      (node (ref "F26") (pin "J1") (pinfunction "OUT_J1") (pintype "output"))
    )
    (net (code "1307") (name "Net-(E31F-IN3)") (class "Default")
      (node (ref "E31") (pin "M2") (pinfunction "IN3_M2") (pintype "input"))
      (node (ref "F26") (pin "M2") (pinfunction "OUT_M2") (pintype "output"))
    )
    (net (code "1308") (name "Net-(E31G-IN1)") (class "Default")
      (node (ref "E31") (pin "M1") (pinfunction "IN1_M1") (pintype "input"))
      (node (ref "F26") (pin "N1") (pinfunction "OUT_N1") (pintype "output"))
    )
    (net (code "1309") (name "Net-(E31G-IN2)") (class "Default")
      (node (ref "E31") (pin "N1") (pinfunction "IN2_N1") (pintype "input"))
      (node (ref "F24") (pin "E1") (pinfunction "OUT_E1") (pintype "output"))
    )
    (net (code "1310") (name "Net-(E32A-IN1)") (class "Default")
      (node (ref "E32") (pin "A1") (pinfunction "IN1_A1") (pintype "input"))
      (node (ref "F32") (pin "F1") (pinfunction "OUT_F1") (pintype "output"))
    )
    (net (code "1311") (name "Net-(E32A-IN4)") (class "Default")
      (node (ref "E32") (pin "D1") (pinfunction "IN4_D1") (pintype "input"))
      (node (ref "F32") (pin "F2") (pinfunction "OUT_F2") (pintype "output"))
    )
    (net (code "1312") (name "Net-(E32D-IN2)") (class "Default")
      (node (ref "E32") (pin "E2") (pinfunction "IN2_E2") (pintype "input"))
      (node (ref "F32") (pin "N2") (pinfunction "OUT_N2") (pintype "output"))
    )
    (net (code "1313") (name "Net-(E32D-IN4)") (class "Default")
      (node (ref "E32") (pin "H2") (pinfunction "IN4_H2") (pintype "input"))
      (node (ref "F26") (pin "S2") (pinfunction "OUT_S2") (pintype "output"))
    )
    (net (code "1314") (name "Net-(E32E-IN4)") (class "Default")
      (node (ref "E32") (pin "K1") (pinfunction "IN4_K1") (pintype "input"))
      (node (ref "F32") (pin "K1") (pinfunction "OUT_K1") (pintype "output"))
    )
    (net (code "1315") (name "Net-(E32J-IN3)") (class "Default")
      (node (ref "E32") (pin "T2") (pinfunction "IN3_T2") (pintype "input"))
      (node (ref "F32") (pin "K2") (pinfunction "OUT_K2") (pintype "output"))
    )
    (net (code "1316") (name "Net-(E33A-S)") (class "Default")
      (node (ref "E33") (pin "D1") (pinfunction "S_D1") (pintype "input"))
      (node (ref "F20") (pin "C1") (pinfunction "OUT_C1") (pintype "output"))
    )
    (net (code "1317") (name "Net-(E33D-D)") (class "Default")
      (node (ref "E33") (pin "E2") (pinfunction "D_E2") (pintype "input"))
      (node (ref "F21") (pin "C1") (pinfunction "OUT_C1") (pintype "output"))
    )
    (net (code "1318") (name "Net-(E33E-D)") (class "Default")
      (node (ref "E33") (pin "J1") (pinfunction "D_J1") (pintype "input"))
      (node (ref "F11") (pin "V2") (pinfunction "OUT_V2") (pintype "output"))
    )
    (net (code "1319") (name "Net-(E33F-C)") (class "Default")
      (node (ref "E33") (pin "L2") (pinfunction "C_L2") (pintype "input"))
      (node (ref "F21") (pin "F2") (pinfunction "OUT_F2") (pintype "output"))
    )
    (net (code "1320") (name "Net-(E33G-C)") (class "Default")
      (node (ref "E33") (pin "N1") (pinfunction "C_N1") (pintype "input"))
      (node (ref "F21") (pin "K2") (pinfunction "OUT_K2") (pintype "output"))
    )
    (net (code "1321") (name "Net-(E33H-D)") (class "Default")
      (node (ref "E33") (pin "T2") (pinfunction "D_T2") (pintype "input"))
      (node (ref "F33") (pin "R1") (pinfunction "OUT_R1") (pintype "output"))
    )
    (net (code "1322") (name "Net-(EF10C-CS2)") (class "Default")
      (node (ref "EF10") (pin "AS2") (pinfunction "CS2_AS2") (pintype "input"))
      (node (ref "F19") (pin "J2") (pinfunction "OUT_J2") (pintype "output"))
    )
    (net (code "1323") (name "Net-(EF34-PadBJ1)") (class "Default")
      (node (ref "EF34") (pin "BJ1") (pinfunction "BJ1_BJ1") (pintype "input"))
      (node (ref "EF35") (pin "BK2") (pinfunction "BK2_BK2") (pintype "output"))
    )
    (net (code "1324") (name "Net-(EF35-PadBJ1)") (class "Default")
      (node (ref "EF35") (pin "BJ1") (pinfunction "BJ1_BJ1") (pintype "input"))
      (node (ref "EF36") (pin "BK2") (pinfunction "BK2_BK2") (pintype "output"))
    )
    (net (code "1325") (name "Net-(EF37-PadBJ1)") (class "Default")
      (node (ref "EF37") (pin "BJ1") (pinfunction "BJ1_BJ1") (pintype "input"))
      (node (ref "EF38") (pin "BK2") (pinfunction "BK2_BK2") (pintype "output"))
    )
    (net (code "1326") (name "Net-(EF38-PadBJ1)") (class "Default")
      (node (ref "EF38") (pin "BJ1") (pinfunction "BJ1_BJ1") (pintype "input"))
      (node (ref "EF39") (pin "BK2") (pinfunction "BK2_BK2") (pintype "output"))
    )
    (net (code "1327") (name "Net-(F11F-IN3)") (class "Default")
      (node (ref "F11") (pin "M2") (pinfunction "IN3_M2") (pintype "input"))
      (node (ref "F27") (pin "E1") (pinfunction "OUT_E1") (pintype "output"))
      (node (ref "F31") (pin "E2") (pinfunction "IN2_E2") (pintype "input"))
    )
    (net (code "1328") (name "Net-(F11F-IN4)") (class "Default")
      (node (ref "F11") (pin "N2") (pinfunction "IN4_N2") (pintype "input"))
      (node (ref "F27") (pin "J2") (pinfunction "OUT_J2") (pintype "output"))
      (node (ref "F31") (pin "H2") (pinfunction "IN4_H2") (pintype "input"))
    )
    (net (code "1329") (name "Net-(F12A-IN)") (class "Default")
      (node (ref "F12") (pin "E1") (pinfunction "IN_E1") (pintype "input"))
      (node (ref "F12") (pin "T2") (pinfunction "T2_T2") (pintype "output"))
    )
    (net (code "1330") (name "Net-(F13A-IN)") (class "Default")
      (node (ref "F13") (pin "E1") (pinfunction "IN_E1") (pintype "input"))
      (node (ref "F13") (pin "T2") (pinfunction "T2_T2") (pintype "output"))
    )
    (net (code "1331") (name "Net-(F13A-OUT)") (class "Default")
      (node (ref "F13") (pin "F1") (pinfunction "OUT_F1") (pintype "output"))
      (node (ref "F14") (pin "H2") (pinfunction "H2_H2") (pintype "input"))
    )
    (net (code "1332") (name "Net-(F13E-IN)") (class "Default")
      (node (ref "F13") (pin "H1") (pinfunction "IN_H1") (pintype "input"))
      (node (ref "F13") (pin "M2") (pinfunction "M2_M2") (pintype "output"))
    )
    (net (code "1333") (name "Net-(F13E-OUT)") (class "Default")
      (node (ref "F13") (pin "J1") (pinfunction "OUT_J1") (pintype "output"))
      (node (ref "F20") (pin "D2") (pinfunction "IN1_D2") (pintype "input"))
    )
    (net (code "1334") (name "Net-(F14A-IN)") (class "Default")
      (node (ref "F14") (pin "E1") (pinfunction "IN_E1") (pintype "input"))
      (node (ref "F14") (pin "T2") (pinfunction "T2_T2") (pintype "output"))
    )
    (net (code "1335") (name "Net-(F14A-OUT)") (class "Default")
      (node (ref "F14") (pin "F1") (pinfunction "OUT_F1") (pintype "output"))
      (node (ref "F15") (pin "H2") (pinfunction "H2_H2") (pintype "input"))
    )
    (net (code "1336") (name "Net-(F14E-IN)") (class "Default")
      (node (ref "F14") (pin "H1") (pinfunction "IN_H1") (pintype "input"))
      (node (ref "F14") (pin "S2") (pinfunction "S2_S2") (pintype "output"))
    )
    (net (code "1337") (name "Net-(F15A-IN)") (class "Default")
      (node (ref "F15") (pin "E1") (pinfunction "IN_E1") (pintype "input"))
      (node (ref "F15") (pin "T2") (pinfunction "T2_T2") (pintype "output"))
    )
    (net (code "1338") (name "Net-(F15E-IN)") (class "Default")
      (node (ref "F15") (pin "H1") (pinfunction "IN_H1") (pintype "input"))
      (node (ref "F15") (pin "M2") (pinfunction "M2_M2") (pintype "output"))
    )
    (net (code "1339") (name "Net-(F15E-OUT)") (class "Default")
      (node (ref "F15") (pin "J1") (pinfunction "OUT_J1") (pintype "output"))
      (node (ref "F20") (pin "H1") (pinfunction "IN1_H1") (pintype "input"))
    )
    (net (code "1340") (name "Net-(F16A-IN)") (class "Default")
      (node (ref "F16") (pin "E1") (pinfunction "IN_E1") (pintype "input"))
      (node (ref "F16") (pin "T2") (pinfunction "T2_T2") (pintype "output"))
    )
    (net (code "1341") (name "Net-(F16A-OUT)") (class "Default")
      (node (ref "F16") (pin "F1") (pinfunction "OUT_F1") (pintype "output"))
      (node (ref "F17") (pin "H2") (pinfunction "H2_H2") (pintype "input"))
    )
    (net (code "1342") (name "Net-(F16E-IN)") (class "Default")
      (node (ref "F16") (pin "H1") (pinfunction "IN_H1") (pintype "input"))
      (node (ref "F16") (pin "S2") (pinfunction "S2_S2") (pintype "output"))
    )
    (net (code "1343") (name "Net-(F17A-IN)") (class "Default")
      (node (ref "F17") (pin "E1") (pinfunction "IN_E1") (pintype "input"))
      (node (ref "F17") (pin "T2") (pinfunction "T2_T2") (pintype "output"))
    )
    (net (code "1344") (name "Net-(F17E-IN)") (class "Default")
      (node (ref "F17") (pin "H1") (pinfunction "IN_H1") (pintype "input"))
      (node (ref "F17") (pin "M2") (pinfunction "M2_M2") (pintype "output"))
    )
    (net (code "1345") (name "Net-(F17E-OUT)") (class "Default")
      (node (ref "F17") (pin "J1") (pinfunction "OUT_J1") (pintype "output"))
      (node (ref "F20") (pin "H2") (pinfunction "IN1_H2") (pintype "input"))
    )
    (net (code "1346") (name "Net-(F18A-IN)") (class "Default")
      (node (ref "F18") (pin "E1") (pinfunction "IN_E1") (pintype "input"))
      (node (ref "F18") (pin "T2") (pinfunction "T2_T2") (pintype "output"))
    )
    (net (code "1347") (name "Net-(F18E-IN)") (class "Default")
      (node (ref "F18") (pin "H1") (pinfunction "IN_H1") (pintype "input"))
      (node (ref "F18") (pin "S2") (pinfunction "S2_S2") (pintype "output"))
    )
    (net (code "1348") (name "Net-(F19A-IN1)") (class "Default")
      (node (ref "F19") (pin "A1") (pinfunction "IN1_A1") (pintype "input"))
      (node (ref "F20") (pin "N1") (pinfunction "OUT_N1") (pintype "output"))
    )
    (net (code "1349") (name "Net-(F19E-IN2)") (class "Default")
      (node (ref "F19") (pin "H1") (pinfunction "IN2_H1") (pintype "input"))
      (node (ref "F21") (pin "N2") (pinfunction "OUT_N2") (pintype "output"))
    )
    (net (code "1350") (name "Net-(F19E-OUT)") (class "Default")
      (node (ref "F19") (pin "L1") (pinfunction "OUT_L1") (pintype "output"))
      (node (ref "F21") (pin "H2") (pinfunction "IN1_H2") (pintype "input"))
    )
    (net (code "1351") (name "Net-(F19J-OUT)") (class "Default")
      (node (ref "F19") (pin "V2") (pinfunction "OUT_V2") (pintype "output"))
      (node (ref "F21") (pin "P1") (pinfunction "IN1_P1") (pintype "input"))
    )
    (net (code "1352") (name "Net-(F20A-IN2)") (class "Default")
      (node (ref "F20") (pin "B1") (pinfunction "IN2_B1") (pintype "input"))
      (node (ref "F20") (pin "F1") (pinfunction "OUT_F1") (pintype "output"))
    )
    (net (code "1353") (name "Net-(F20H-IN1)") (class "Default")
      (node (ref "F20") (pin "L1") (pinfunction "IN1_L1") (pintype "input"))
      (node (ref "F20") (pin "S1") (pinfunction "OUT_S1") (pintype "output"))
    )
    (net (code "1354") (name "Net-(F20I-OUT)") (class "Default")
      (node (ref "F20") (pin "N2") (pinfunction "OUT_N2") (pintype "output"))
      (node (ref "F30") (pin "A1") (pinfunction "IN1_A1") (pintype "input"))
    )
    (net (code "1355") (name "Net-(F20K-IN1)") (class "Default")
      (node (ref "F20") (pin "P2") (pinfunction "IN1_P2") (pintype "input"))
      (node (ref "F20") (pin "V2") (pinfunction "OUT_V2") (pintype "output"))
    )
    (net (code "1356") (name "Net-(F21C-IN1)") (class "Default")
      (node (ref "F21") (pin "D2") (pinfunction "IN1_D2") (pintype "input"))
      (node (ref "F21") (pin "K1") (pinfunction "OUT_K1") (pintype "output"))
    )
    (net (code "1357") (name "Net-(F21K-IN2)") (class "Default")
      (node (ref "F21") (pin "R2") (pinfunction "IN2_R2") (pintype "input"))
      (node (ref "F23") (pin "V2") (pinfunction "OUT_V2") (pintype "output"))
    )
    (net (code "1358") (name "Net-(F22J-OUT)") (class "Default")
      (node (ref "F22") (pin "P2") (pinfunction "IN1_P2") (pintype "input"))
      (node (ref "F22") (pin "S1") (pinfunction "OUT_S1") (pintype "output"))
    )
    (net (code "1359") (name "Net-(F23D-IN3)") (class "Default")
      (node (ref "F23") (pin "F2") (pinfunction "IN3_F2") (pintype "input"))
      (node (ref "F23") (pin "L1") (pinfunction "OUT_L1") (pintype "output"))
    )
    (net (code "1360") (name "Net-(F24D-OUT)") (class "Default")
      (node (ref "F24") (pin "J2") (pinfunction "OUT_J2") (pintype "output"))
      (node (ref "F25") (pin "D2") (pinfunction "IN1_D2") (pintype "input"))
    )
    (net (code "1361") (name "Net-(F24E-OUT)") (class "Default")
      (node (ref "F24") (pin "L1") (pinfunction "OUT_L1") (pintype "output"))
      (node (ref "F25") (pin "H1") (pinfunction "IN1_H1") (pintype "input"))
    )
    (net (code "1362") (name "Net-(F25C-OUT)") (class "Default")
      (node (ref "F25") (pin "F2") (pinfunction "OUT_F2") (pintype "output"))
      (node (ref "F27") (pin "M1") (pinfunction "IN1_M1") (pintype "input"))
    )
    (net (code "1363") (name "Net-(F25F-OUT)") (class "Default")
      (node (ref "F25") (pin "K1") (pinfunction "OUT_K1") (pintype "output"))
      (node (ref "F27") (pin "N1") (pinfunction "IN2_N1") (pintype "input"))
    )
    (net (code "1364") (name "Net-(F25G-IN1)") (class "Default")
      (node (ref "F25") (pin "H2") (pinfunction "IN1_H2") (pintype "input"))
      (node (ref "F25") (pin "N1") (pinfunction "OUT_N1") (pintype "output"))
    )
    (net (code "1365") (name "Net-(F25G-OUT)") (class "Default")
      (node (ref "F25") (pin "K2") (pinfunction "OUT_K2") (pintype "output"))
      (node (ref "F27") (pin "P1") (pinfunction "IN3_P1") (pintype "input"))
    )
    (net (code "1366") (name "Net-(F27D-IN2)") (class "Default")
      (node (ref "F27") (pin "E2") (pinfunction "IN2_E2") (pintype "input"))
      (node (ref "F29") (pin "F1") (pinfunction "OUT_F1") (pintype "output"))
    )
    (net (code "1367") (name "Net-(F27E-OUT)") (class "Default")
      (node (ref "F27") (pin "L1") (pinfunction "OUT_L1") (pintype "output"))
      (node (ref "F29") (pin "J1") (pinfunction "IN2_J1") (pintype "input"))
    )
    (net (code "1368") (name "Net-(F27F-OUT)") (class "Default")
      (node (ref "F27") (pin "P2") (pinfunction "OUT_P2") (pintype "output"))
      (node (ref "F32") (pin "A1") (pinfunction "IN1_A1") (pintype "input"))
    )
    (net (code "1369") (name "Net-(F28D-OUT)") (class "Default")
      (node (ref "F28") (pin "H2") (pinfunction "OUT_H2") (pintype "output"))
      (node (ref "F31") (pin "F1") (pinfunction "IN1_F1") (pintype "input"))
    )
    (net (code "1370") (name "Net-(F28F-OUT)") (class "Default")
      (node (ref "F28") (pin "M2") (pinfunction "OUT_M2") (pintype "output"))
      (node (ref "F32") (pin "M1") (pinfunction "IN2_M1") (pintype "input"))
    )
    (net (code "1371") (name "Net-(F28G-OUT)") (class "Default")
      (node (ref "F28") (pin "N1") (pinfunction "OUT_N1") (pintype "output"))
      (node (ref "F30") (pin "F1") (pinfunction "IN1_F1") (pintype "input"))
    )
    (net (code "1372") (name "Net-(F28I-OUT)") (class "Default")
      (node (ref "F28") (pin "U1") (pinfunction "OUT_U1") (pintype "output"))
      (node (ref "F33") (pin "A1") (pinfunction "IN1A_A1") (pintype "input"))
    )
    (net (code "1373") (name "Net-(F29H-OUT)") (class "Default")
      (node (ref "F29") (pin "N1") (pinfunction "OUT_N1") (pintype "output"))
      (node (ref "F30") (pin "K2") (pinfunction "IN1_K2") (pintype "input"))
    )
    (net (code "1374") (name "Net-(F29I-IN1)") (class "Default")
      (node (ref "F29") (pin "L2") (pinfunction "IN1_L2") (pintype "input"))
      (node (ref "F29") (pin "V2") (pinfunction "OUT_V2") (pintype "output"))
    )
    (net (code "1375") (name "Net-(F29J-OUT)") (class "Default")
      (node (ref "F29") (pin "S1") (pinfunction "OUT_S1") (pintype "output"))
      (node (ref "F30") (pin "M1") (pinfunction "IN1_M1") (pintype "input"))
    )
    (net (code "1376") (name "Net-(F32K-IN2)") (class "Default")
      (node (ref "F32") (pin "R2") (pinfunction "IN2_R2") (pintype "input"))
      (node (ref "F33") (pin "S1") (pinfunction "IN1A_S1") (pintype "input"))
      (node (ref "F33") (pin "T2") (pinfunction "OUT_T2") (pintype "output"))
    )
    (net (code "1377") (name "Net-(F32K-OUT)") (class "Default")
      (node (ref "F32") (pin "S2") (pinfunction "OUT_S2") (pintype "output"))
      (node (ref "F33") (pin "V1") (pinfunction "IN2A_V1") (pintype "input"))
    )
    (net (code "1378") (name "Net-(H07A-OUT)") (class "Default")
      (node (ref "H07") (pin "D2") (pinfunction "OUT_D2") (pintype "output"))
      (node (ref "J01") (pin "D2") (pinfunction "P$2_D2") (pintype "bidirectional"))
    )
    (net (code "1379") (name "Net-(H07B-OUT)") (class "Default")
      (node (ref "H07") (pin "K2") (pinfunction "OUT_K2") (pintype "output"))
      (node (ref "J01") (pin "E2") (pinfunction "P$2_E2") (pintype "bidirectional"))
    )
    (net (code "1380") (name "Net-(H07C-OUT)") (class "Default")
      (node (ref "H07") (pin "S2") (pinfunction "OUT_S2") (pintype "output"))
      (node (ref "J01") (pin "H2") (pinfunction "P$2_H2") (pintype "bidirectional"))
    )
    (net (code "1381") (name "Net-(H08A-OUT)") (class "Default")
      (node (ref "H08") (pin "D2") (pinfunction "OUT_D2") (pintype "output"))
      (node (ref "J01") (pin "K2") (pinfunction "P$2_K2") (pintype "bidirectional"))
    )
    (net (code "1382") (name "Net-(H08B-OUT)") (class "Default")
      (node (ref "H08") (pin "K2") (pinfunction "OUT_K2") (pintype "output"))
      (node (ref "J01") (pin "M2") (pinfunction "P$2_M2") (pintype "bidirectional"))
    )
    (net (code "1383") (name "Net-(H08C-OUT)") (class "Default")
      (node (ref "H08") (pin "S2") (pinfunction "OUT_S2") (pintype "output"))
      (node (ref "J01") (pin "P2") (pinfunction "P$2_P2") (pintype "bidirectional"))
    )
    (net (code "1384") (name "Net-(H09A-OUT)") (class "Default")
      (node (ref "H09") (pin "D2") (pinfunction "OUT_D2") (pintype "output"))
      (node (ref "J01") (pin "S2") (pinfunction "P$2_S2") (pintype "bidirectional"))
    )
    (net (code "1385") (name "Net-(H09B-OUT)") (class "Default")
      (node (ref "H09") (pin "K2") (pinfunction "OUT_K2") (pintype "output"))
      (node (ref "J01") (pin "T2") (pinfunction "P$2_T2") (pintype "bidirectional"))
    )
    (net (code "1386") (name "Net-(H09C-OUT)") (class "Default")
      (node (ref "H09") (pin "S2") (pinfunction "OUT_S2") (pintype "output"))
      (node (ref "J01") (pin "V2") (pinfunction "P$2_V2") (pintype "bidirectional"))
    )
    (net (code "1387") (name "Net-(H10A-OUT)") (class "Default")
      (node (ref "H10") (pin "D2") (pinfunction "OUT_D2") (pintype "output"))
      (node (ref "J02") (pin "D2") (pinfunction "P$2_D2") (pintype "bidirectional"))
    )
    (net (code "1388") (name "Net-(H10B-OUT)") (class "Default")
      (node (ref "H10") (pin "K2") (pinfunction "OUT_K2") (pintype "output"))
      (node (ref "J02") (pin "E2") (pinfunction "P$2_E2") (pintype "bidirectional"))
    )
    (net (code "1389") (name "Net-(H10C-OUT)") (class "Default")
      (node (ref "H10") (pin "S2") (pinfunction "OUT_S2") (pintype "output"))
      (node (ref "J02") (pin "H2") (pinfunction "P$2_H2") (pintype "bidirectional"))
    )
    (net (code "1390") (name "Net-(H11A-OUT)") (class "Default")
      (node (ref "H11") (pin "D2") (pinfunction "OUT_D2") (pintype "output"))
      (node (ref "J02") (pin "K2") (pinfunction "P$2_K2") (pintype "bidirectional"))
    )
    (net (code "1391") (name "Net-(H11B-OUT)") (class "Default")
      (node (ref "H11") (pin "K2") (pinfunction "OUT_K2") (pintype "output"))
      (node (ref "J02") (pin "M2") (pinfunction "P$2_M2") (pintype "bidirectional"))
    )
    (net (code "1392") (name "Net-(H11C-OUT)") (class "Default")
      (node (ref "H11") (pin "S2") (pinfunction "OUT_S2") (pintype "output"))
      (node (ref "J02") (pin "P2") (pinfunction "P$2_P2") (pintype "bidirectional"))
    )
    (net (code "1393") (name "Net-(H12A-OUT)") (class "Default")
      (node (ref "H12") (pin "D2") (pinfunction "OUT_D2") (pintype "output"))
      (node (ref "J02") (pin "S2") (pinfunction "P$2_S2") (pintype "bidirectional"))
    )
    (net (code "1394") (name "Net-(H12B-OUT)") (class "Default")
      (node (ref "H12") (pin "K2") (pinfunction "OUT_K2") (pintype "output"))
      (node (ref "J02") (pin "T2") (pinfunction "P$2_T2") (pintype "bidirectional"))
    )
    (net (code "1395") (name "Net-(H12C-OUT)") (class "Default")
      (node (ref "H12") (pin "S2") (pinfunction "OUT_S2") (pintype "output"))
      (node (ref "J02") (pin "V2") (pinfunction "P$2_V2") (pintype "bidirectional"))
    )
    (net (code "1396") (name "Net-(H13A-OUT)") (class "Default")
      (node (ref "H13") (pin "D2") (pinfunction "OUT_D2") (pintype "output"))
      (node (ref "J03") (pin "D2") (pinfunction "P$2_D2") (pintype "bidirectional"))
    )
    (net (code "1397") (name "Net-(H13B-OUT)") (class "Default")
      (node (ref "H13") (pin "K2") (pinfunction "OUT_K2") (pintype "output"))
      (node (ref "J03") (pin "E2") (pinfunction "P$2_E2") (pintype "bidirectional"))
    )
    (net (code "1398") (name "Net-(H13C-OUT)") (class "Default")
      (node (ref "H13") (pin "S2") (pinfunction "OUT_S2") (pintype "output"))
      (node (ref "J03") (pin "H2") (pinfunction "P$2_H2") (pintype "bidirectional"))
    )
    (net (code "1399") (name "Net-(H14A-OUT)") (class "Default")
      (node (ref "H14") (pin "D2") (pinfunction "OUT_D2") (pintype "output"))
      (node (ref "J03") (pin "K2") (pinfunction "P$2_K2") (pintype "bidirectional"))
    )
    (net (code "1400") (name "Net-(H14B-OUT)") (class "Default")
      (node (ref "H14") (pin "K2") (pinfunction "OUT_K2") (pintype "output"))
      (node (ref "J03") (pin "M2") (pinfunction "P$2_M2") (pintype "bidirectional"))
    )
    (net (code "1401") (name "Net-(H14C-OUT)") (class "Default")
      (node (ref "H14") (pin "S2") (pinfunction "OUT_S2") (pintype "output"))
      (node (ref "J03") (pin "P2") (pinfunction "P$2_P2") (pintype "bidirectional"))
    )
    (net (code "1402") (name "Net-(H15A-OUT)") (class "Default")
      (node (ref "H15") (pin "D2") (pinfunction "OUT_D2") (pintype "output"))
      (node (ref "J03") (pin "S2") (pinfunction "P$2_S2") (pintype "bidirectional"))
    )
    (net (code "1403") (name "Net-(H15B-OUT)") (class "Default")
      (node (ref "H15") (pin "K2") (pinfunction "OUT_K2") (pintype "output"))
      (node (ref "J03") (pin "T2") (pinfunction "P$2_T2") (pintype "bidirectional"))
    )
    (net (code "1404") (name "Net-(H15C-OUT)") (class "Default")
      (node (ref "H15") (pin "S2") (pinfunction "OUT_S2") (pintype "output"))
      (node (ref "J03") (pin "V2") (pinfunction "P$2_V2") (pintype "bidirectional"))
    )
    (net (code "1405") (name "Net-(H16A-OUT)") (class "Default")
      (node (ref "H16") (pin "D2") (pinfunction "OUT_D2") (pintype "output"))
      (node (ref "J04") (pin "D2") (pinfunction "P$2_D2") (pintype "bidirectional"))
    )
    (net (code "1406") (name "Net-(H16B-OUT)") (class "Default")
      (node (ref "H16") (pin "K2") (pinfunction "OUT_K2") (pintype "output"))
      (node (ref "J04") (pin "E2") (pinfunction "P$2_E2") (pintype "bidirectional"))
    )
    (net (code "1407") (name "Net-(H16C-OUT)") (class "Default")
      (node (ref "H16") (pin "S2") (pinfunction "OUT_S2") (pintype "output"))
      (node (ref "J04") (pin "H2") (pinfunction "P$2_H2") (pintype "bidirectional"))
    )
    (net (code "1408") (name "Net-(H17A-OUT)") (class "Default")
      (node (ref "H17") (pin "D2") (pinfunction "OUT_D2") (pintype "output"))
      (node (ref "J04") (pin "K2") (pinfunction "P$2_K2") (pintype "bidirectional"))
    )
    (net (code "1409") (name "Net-(H17B-OUT)") (class "Default")
      (node (ref "H17") (pin "K2") (pinfunction "OUT_K2") (pintype "output"))
      (node (ref "J04") (pin "M2") (pinfunction "P$2_M2") (pintype "bidirectional"))
    )
    (net (code "1410") (name "Net-(H17C-OUT)") (class "Default")
      (node (ref "H17") (pin "S2") (pinfunction "OUT_S2") (pintype "output"))
      (node (ref "J04") (pin "P2") (pinfunction "P$2_P2") (pintype "bidirectional"))
    )
    (net (code "1411") (name "Net-(H18A-OUT)") (class "Default")
      (node (ref "H18") (pin "D2") (pinfunction "OUT_D2") (pintype "output"))
      (node (ref "J04") (pin "S2") (pinfunction "P$2_S2") (pintype "bidirectional"))
    )
    (net (code "1412") (name "Net-(H18B-OUT)") (class "Default")
      (node (ref "H18") (pin "K2") (pinfunction "OUT_K2") (pintype "output"))
      (node (ref "J04") (pin "T2") (pinfunction "P$2_T2") (pintype "bidirectional"))
    )
    (net (code "1413") (name "Net-(H18C-OUT)") (class "Default")
      (node (ref "H18") (pin "S2") (pinfunction "OUT_S2") (pintype "output"))
      (node (ref "J04") (pin "V2") (pinfunction "P$2_V2") (pintype "bidirectional"))
    )
    (net (code "1414") (name "Net-(H19A-OUT)") (class "Default")
      (node (ref "H19") (pin "D2") (pinfunction "OUT_D2") (pintype "output"))
      (node (ref "J06") (pin "S2") (pinfunction "P$2_S2") (pintype "bidirectional"))
    )
    (net (code "1415") (name "Net-(H19B-OUT)") (class "Default")
      (node (ref "H19") (pin "K2") (pinfunction "OUT_K2") (pintype "output"))
      (node (ref "J06") (pin "T2") (pinfunction "P$2_T2") (pintype "bidirectional"))
    )
    (net (code "1416") (name "Net-(H19C-OUT)") (class "Default")
      (node (ref "H19") (pin "S2") (pinfunction "OUT_S2") (pintype "output"))
      (node (ref "J10") (pin "P2") (pinfunction "P$2_P2") (pintype "bidirectional"))
    )
    (net (code "1417") (name "Net-(H20A-OUT)") (class "Default")
      (node (ref "H20") (pin "D2") (pinfunction "OUT_D2") (pintype "output"))
      (node (ref "J08") (pin "P2") (pinfunction "P$2_P2") (pintype "bidirectional"))
    )
    (net (code "1418") (name "Net-(H20B-OUT)") (class "Default")
      (node (ref "H20") (pin "K2") (pinfunction "OUT_K2") (pintype "output"))
      (node (ref "J08") (pin "S2") (pinfunction "P$2_S2") (pintype "bidirectional"))
    )
    (net (code "1419") (name "Net-(HJ28-PadAU1)") (class "Default")
      (node (ref "HJ28") (pin "AU1") (pinfunction "AU1_AU1") (pintype "input"))
      (node (ref "HJ28") (pin "BV1") (pinfunction "BV1_BV1") (pintype "output"))
    )
    (net (code "1420") (name "Net-(J05A-P$2)") (class "Default")
      (node (ref "J05") (pin "D2") (pinfunction "P$2_D2") (pintype "bidirectional"))
      (node (ref "J13") (pin "A1") (pinfunction "IN_A1") (pintype "input"))
    )
    (net (code "1421") (name "Net-(J05B-P$2)") (class "Default")
      (node (ref "J05") (pin "E2") (pinfunction "P$2_E2") (pintype "bidirectional"))
      (node (ref "J13") (pin "D2") (pinfunction "IN_D2") (pintype "input"))
    )
    (net (code "1422") (name "Net-(J05J-P$2)") (class "Default")
      (node (ref "J05") (pin "H2") (pinfunction "P$2_H2") (pintype "bidirectional"))
      (node (ref "J13") (pin "F1") (pinfunction "IN_F1") (pintype "input"))
    )
    (net (code "1423") (name "Net-(J05K-P$2)") (class "Default")
      (node (ref "J05") (pin "K2") (pinfunction "P$2_K2") (pintype "bidirectional"))
      (node (ref "J13") (pin "K2") (pinfunction "IN_K2") (pintype "input"))
    )
    (net (code "1424") (name "Net-(J05L-P$2)") (class "Default")
      (node (ref "J05") (pin "M2") (pinfunction "P$2_M2") (pintype "bidirectional"))
      (node (ref "J13") (pin "M1") (pinfunction "IN_M1") (pintype "input"))
    )
    (net (code "1425") (name "Net-(J05M-P$2)") (class "Default")
      (node (ref "J05") (pin "P2") (pinfunction "P$2_P2") (pintype "bidirectional"))
      (node (ref "J13") (pin "R2") (pinfunction "IN_R2") (pintype "input"))
    )
    (net (code "1426") (name "Net-(J05N-P$2)") (class "Default")
      (node (ref "J05") (pin "S2") (pinfunction "P$2_S2") (pintype "bidirectional"))
      (node (ref "J14") (pin "A1") (pinfunction "IN_A1") (pintype "input"))
    )
    (net (code "1427") (name "Net-(J05O-P$2)") (class "Default")
      (node (ref "J05") (pin "T2") (pinfunction "P$2_T2") (pintype "bidirectional"))
      (node (ref "J14") (pin "D2") (pinfunction "IN_D2") (pintype "input"))
    )
    (net (code "1428") (name "Net-(J05P-P$2)") (class "Default")
      (node (ref "J05") (pin "V2") (pinfunction "P$2_V2") (pintype "bidirectional"))
      (node (ref "J14") (pin "F1") (pinfunction "IN_F1") (pintype "input"))
    )
    (net (code "1429") (name "Net-(J06A-P$2)") (class "Default")
      (node (ref "J06") (pin "D2") (pinfunction "P$2_D2") (pintype "bidirectional"))
      (node (ref "J14") (pin "K2") (pinfunction "IN_K2") (pintype "input"))
    )
    (net (code "1430") (name "Net-(J06B-P$2)") (class "Default")
      (node (ref "J06") (pin "E2") (pinfunction "P$2_E2") (pintype "bidirectional"))
      (node (ref "J14") (pin "M1") (pinfunction "IN_M1") (pintype "input"))
    )
    (net (code "1431") (name "Net-(J06J-P$2)") (class "Default")
      (node (ref "J06") (pin "H2") (pinfunction "P$2_H2") (pintype "bidirectional"))
      (node (ref "J14") (pin "R2") (pinfunction "IN_R2") (pintype "input"))
    )
    (net (code "1432") (name "Net-(J06K-P$2)") (class "Default")
      (node (ref "J06") (pin "K2") (pinfunction "P$2_K2") (pintype "bidirectional"))
      (node (ref "J15") (pin "A1") (pinfunction "IN_A1") (pintype "input"))
    )
    (net (code "1433") (name "Net-(J06L-P$2)") (class "Default")
      (node (ref "J06") (pin "M2") (pinfunction "P$2_M2") (pintype "bidirectional"))
      (node (ref "J15") (pin "D2") (pinfunction "IN_D2") (pintype "input"))
    )
    (net (code "1434") (name "Net-(J06M-P$2)") (class "Default")
      (node (ref "J06") (pin "P2") (pinfunction "P$2_P2") (pintype "bidirectional"))
      (node (ref "J15") (pin "F1") (pinfunction "IN_F1") (pintype "input"))
    )
    (net (code "1435") (name "Net-(J06P-P$2)") (class "Default")
      (node (ref "J06") (pin "V2") (pinfunction "P$2_V2") (pintype "bidirectional"))
      (node (ref "J15") (pin "K2") (pinfunction "IN_K2") (pintype "input"))
    )
    (net (code "1436") (name "Net-(J07A-P$2)") (class "Default")
      (node (ref "J07") (pin "D2") (pinfunction "P$2_D2") (pintype "bidirectional"))
      (node (ref "J16") (pin "A1") (pinfunction "IN_A1") (pintype "input"))
    )
    (net (code "1437") (name "Net-(J07B-P$2)") (class "Default")
      (node (ref "J07") (pin "E2") (pinfunction "P$2_E2") (pintype "bidirectional"))
      (node (ref "J16") (pin "D2") (pinfunction "IN_D2") (pintype "input"))
    )
    (net (code "1438") (name "Net-(J07J-P$2)") (class "Default")
      (node (ref "J07") (pin "H2") (pinfunction "P$2_H2") (pintype "bidirectional"))
      (node (ref "J16") (pin "F1") (pinfunction "IN_F1") (pintype "input"))
    )
    (net (code "1439") (name "Net-(J07K-P$2)") (class "Default")
      (node (ref "J07") (pin "K2") (pinfunction "P$2_K2") (pintype "bidirectional"))
      (node (ref "J16") (pin "K2") (pinfunction "IN_K2") (pintype "input"))
    )
    (net (code "1440") (name "Net-(J07L-P$2)") (class "Default")
      (node (ref "J07") (pin "M2") (pinfunction "P$2_M2") (pintype "bidirectional"))
      (node (ref "J16") (pin "M1") (pinfunction "IN_M1") (pintype "input"))
    )
    (net (code "1441") (name "Net-(J07M-P$2)") (class "Default")
      (node (ref "J07") (pin "P2") (pinfunction "P$2_P2") (pintype "bidirectional"))
      (node (ref "J16") (pin "R2") (pinfunction "IN_R2") (pintype "input"))
    )
    (net (code "1442") (name "Net-(J07N-P$2)") (class "Default")
      (node (ref "J07") (pin "S2") (pinfunction "P$2_S2") (pintype "bidirectional"))
      (node (ref "J17") (pin "A1") (pinfunction "IN_A1") (pintype "input"))
    )
    (net (code "1443") (name "Net-(J07O-P$2)") (class "Default")
      (node (ref "J07") (pin "T2") (pinfunction "P$2_T2") (pintype "bidirectional"))
      (node (ref "J17") (pin "D2") (pinfunction "IN_D2") (pintype "input"))
    )
    (net (code "1444") (name "Net-(J07P-P$2)") (class "Default")
      (node (ref "J07") (pin "V2") (pinfunction "P$2_V2") (pintype "bidirectional"))
      (node (ref "J17") (pin "F1") (pinfunction "IN_F1") (pintype "input"))
    )
    (net (code "1445") (name "Net-(J08A-P$2)") (class "Default")
      (node (ref "J08") (pin "D2") (pinfunction "P$2_D2") (pintype "bidirectional"))
      (node (ref "J17") (pin "K2") (pinfunction "IN_K2") (pintype "input"))
    )
    (net (code "1446") (name "Net-(J08B-P$2)") (class "Default")
      (node (ref "J08") (pin "E2") (pinfunction "P$2_E2") (pintype "bidirectional"))
      (node (ref "J17") (pin "M1") (pinfunction "IN_M1") (pintype "input"))
    )
    (net (code "1447") (name "Net-(J08J-P$2)") (class "Default")
      (node (ref "J08") (pin "H2") (pinfunction "P$2_H2") (pintype "bidirectional"))
      (node (ref "J17") (pin "R2") (pinfunction "IN_R2") (pintype "input"))
    )
    (net (code "1448") (name "Net-(J08K-P$2)") (class "Default")
      (node (ref "J08") (pin "K2") (pinfunction "P$2_K2") (pintype "bidirectional"))
      (node (ref "J15") (pin "M1") (pinfunction "IN_M1") (pintype "input"))
    )
    (net (code "1449") (name "Net-(J08L-P$2)") (class "Default")
      (node (ref "J08") (pin "M2") (pinfunction "P$2_M2") (pintype "bidirectional"))
      (node (ref "J15") (pin "R2") (pinfunction "IN_R2") (pintype "input"))
    )
    (net (code "1450") (name "Net-(J08O-P$2)") (class "Default")
      (node (ref "J08") (pin "T2") (pinfunction "P$2_T2") (pintype "bidirectional"))
      (node (ref "J20") (pin "A1") (pinfunction "IN_A1") (pintype "input"))
    )
    (net (code "1451") (name "Net-(J09A-P$2)") (class "Default")
      (node (ref "J09") (pin "D2") (pinfunction "P$2_D2") (pintype "bidirectional"))
      (node (ref "J18") (pin "A1") (pinfunction "IN_A1") (pintype "input"))
    )
    (net (code "1452") (name "Net-(J09B-P$2)") (class "Default")
      (node (ref "J09") (pin "E2") (pinfunction "P$2_E2") (pintype "bidirectional"))
      (node (ref "J18") (pin "D2") (pinfunction "IN_D2") (pintype "input"))
    )
    (net (code "1453") (name "Net-(J09J-P$2)") (class "Default")
      (node (ref "J09") (pin "H2") (pinfunction "P$2_H2") (pintype "bidirectional"))
      (node (ref "J18") (pin "F1") (pinfunction "IN_F1") (pintype "input"))
    )
    (net (code "1454") (name "Net-(J09K-P$2)") (class "Default")
      (node (ref "J09") (pin "K2") (pinfunction "P$2_K2") (pintype "bidirectional"))
      (node (ref "J18") (pin "K2") (pinfunction "IN_K2") (pintype "input"))
    )
    (net (code "1455") (name "Net-(J09L-P$2)") (class "Default")
      (node (ref "J09") (pin "M2") (pinfunction "P$2_M2") (pintype "bidirectional"))
      (node (ref "J18") (pin "M1") (pinfunction "IN_M1") (pintype "input"))
    )
    (net (code "1456") (name "Net-(J09M-P$2)") (class "Default")
      (node (ref "J09") (pin "P2") (pinfunction "P$2_P2") (pintype "bidirectional"))
      (node (ref "J18") (pin "R2") (pinfunction "IN_R2") (pintype "input"))
    )
    (net (code "1457") (name "Net-(J09N-P$2)") (class "Default")
      (node (ref "J09") (pin "S2") (pinfunction "P$2_S2") (pintype "bidirectional"))
      (node (ref "J19") (pin "A1") (pinfunction "IN_A1") (pintype "input"))
    )
    (net (code "1458") (name "Net-(J09O-P$2)") (class "Default")
      (node (ref "J09") (pin "T2") (pinfunction "P$2_T2") (pintype "bidirectional"))
      (node (ref "J19") (pin "D2") (pinfunction "IN_D2") (pintype "input"))
    )
    (net (code "1459") (name "Net-(J09P-P$2)") (class "Default")
      (node (ref "J09") (pin "V2") (pinfunction "P$2_V2") (pintype "bidirectional"))
      (node (ref "J19") (pin "F1") (pinfunction "IN_F1") (pintype "input"))
    )
    (net (code "1460") (name "Net-(J10A-P$2)") (class "Default")
      (node (ref "J10") (pin "D2") (pinfunction "P$2_D2") (pintype "bidirectional"))
      (node (ref "J19") (pin "K2") (pinfunction "IN_K2") (pintype "input"))
    )
    (net (code "1461") (name "Net-(J10B-P$2)") (class "Default")
      (node (ref "J10") (pin "E2") (pinfunction "P$2_E2") (pintype "bidirectional"))
      (node (ref "J19") (pin "M1") (pinfunction "IN_M1") (pintype "input"))
    )
    (net (code "1462") (name "Net-(J10J-P$2)") (class "Default")
      (node (ref "J10") (pin "H2") (pinfunction "P$2_H2") (pintype "bidirectional"))
      (node (ref "J19") (pin "R2") (pinfunction "IN_R2") (pintype "input"))
    )
    (net (code "1463") (name "Net-(J10K-P$2)") (class "Default")
      (node (ref "J10") (pin "K2") (pinfunction "P$2_K2") (pintype "bidirectional"))
      (node (ref "J20") (pin "D2") (pinfunction "IN_D2") (pintype "input"))
    )
    (net (code "1464") (name "Net-(J10L-P$2)") (class "Default")
      (node (ref "J10") (pin "M2") (pinfunction "P$2_M2") (pintype "bidirectional"))
      (node (ref "J20") (pin "F1") (pinfunction "IN_F1") (pintype "input"))
    )
    (net (code "1465") (name "Net-(J10N-P$2)") (class "Default")
      (node (ref "J10") (pin "S2") (pinfunction "P$2_S2") (pintype "bidirectional"))
      (node (ref "J11") (pin "D2") (pinfunction "P$2_D2") (pintype "bidirectional"))
      (node (ref "J20") (pin "R2") (pinfunction "IN_R2") (pintype "input"))
    )
    (net (code "1466") (name "Net-(J10O-P$2)") (class "Default")
      (node (ref "J10") (pin "T2") (pinfunction "P$2_T2") (pintype "bidirectional"))
      (node (ref "J11") (pin "E2") (pinfunction "P$2_E2") (pintype "bidirectional"))
      (node (ref "J20") (pin "M1") (pinfunction "IN_M1") (pintype "input"))
    )
    (net (code "1467") (name "Net-(J10P-P$2)") (class "Default")
      (node (ref "J10") (pin "V2") (pinfunction "P$2_V2") (pintype "bidirectional"))
      (node (ref "J11") (pin "H2") (pinfunction "P$2_H2") (pintype "bidirectional"))
      (node (ref "J20") (pin "K2") (pinfunction "IN_K2") (pintype "input"))
    )
    (net (code "1468") (name "Net-(J15G-IN2)") (class "Default")
      (node (ref "J15") (pin "L2") (pinfunction "IN2_L2") (pintype "passive"))
      (node (ref "J15") (pin "M2") (pinfunction "IN3_M2") (pintype "input"))
      (node (ref "J15") (pin "N2") (pinfunction "IN4_N2") (pintype "input"))
    )
    (net (code "1469") (name "Net-(J15H-IN2)") (class "Default")
      (node (ref "J15") (pin "N1") (pinfunction "IN2_N1") (pintype "passive"))
      (node (ref "J15") (pin "P1") (pinfunction "IN3_P1") (pintype "input"))
      (node (ref "J15") (pin "R1") (pinfunction "IN4_R1") (pintype "input"))
    )
    (net (code "1470") (name "Net-(J15I-IN2)") (class "Default")
      (node (ref "J15") (pin "S2") (pinfunction "IN2_S2") (pintype "passive"))
      (node (ref "J15") (pin "T2") (pinfunction "IN3_T2") (pintype "input"))
      (node (ref "J15") (pin "U2") (pinfunction "IN4_U2") (pintype "input"))
    )
    (net (code "1471") (name "Net-(J16A-IN2)") (class "Default")
      (node (ref "J16") (pin "B1") (pinfunction "IN2_B1") (pintype "passive"))
      (node (ref "J16") (pin "C1") (pinfunction "IN3_C1") (pintype "input"))
      (node (ref "J16") (pin "D1") (pinfunction "IN4_D1") (pintype "input"))
    )
    (net (code "1472") (name "Net-(J16E-IN2)") (class "Default")
      (node (ref "J16") (pin "E2") (pinfunction "IN2_E2") (pintype "passive"))
      (node (ref "J16") (pin "F2") (pinfunction "IN3_F2") (pintype "input"))
      (node (ref "J16") (pin "H2") (pinfunction "IN4_H2") (pintype "input"))
    )
    (net (code "1473") (name "Net-(J16F-IN2)") (class "Default")
      (node (ref "J16") (pin "H1") (pinfunction "IN2_H1") (pintype "passive"))
      (node (ref "J16") (pin "J1") (pinfunction "IN3_J1") (pintype "input"))
      (node (ref "J16") (pin "K1") (pinfunction "IN4_K1") (pintype "input"))
    )
    (net (code "1474") (name "Net-(J16G-IN2)") (class "Default")
      (node (ref "J16") (pin "L2") (pinfunction "IN2_L2") (pintype "passive"))
      (node (ref "J16") (pin "M2") (pinfunction "IN3_M2") (pintype "input"))
      (node (ref "J16") (pin "N2") (pinfunction "IN4_N2") (pintype "input"))
    )
    (net (code "1475") (name "Net-(J16H-IN2)") (class "Default")
      (node (ref "J16") (pin "N1") (pinfunction "IN2_N1") (pintype "passive"))
      (node (ref "J16") (pin "P1") (pinfunction "IN3_P1") (pintype "input"))
      (node (ref "J16") (pin "R1") (pinfunction "IN4_R1") (pintype "input"))
    )
    (net (code "1476") (name "Net-(J16I-IN2)") (class "Default")
      (node (ref "J16") (pin "S2") (pinfunction "IN2_S2") (pintype "passive"))
      (node (ref "J16") (pin "T2") (pinfunction "IN3_T2") (pintype "input"))
      (node (ref "J16") (pin "U2") (pinfunction "IN4_U2") (pintype "input"))
    )
    (net (code "1477") (name "Net-(J17A-IN2)") (class "Default")
      (node (ref "J17") (pin "B1") (pinfunction "IN2_B1") (pintype "passive"))
      (node (ref "J17") (pin "C1") (pinfunction "IN3_C1") (pintype "input"))
      (node (ref "J17") (pin "D1") (pinfunction "IN4_D1") (pintype "input"))
    )
    (net (code "1478") (name "Net-(J17E-IN2)") (class "Default")
      (node (ref "J17") (pin "E2") (pinfunction "IN2_E2") (pintype "passive"))
      (node (ref "J17") (pin "F2") (pinfunction "IN3_F2") (pintype "input"))
      (node (ref "J17") (pin "H2") (pinfunction "IN4_H2") (pintype "input"))
    )
    (net (code "1479") (name "Net-(J17F-IN2)") (class "Default")
      (node (ref "J17") (pin "H1") (pinfunction "IN2_H1") (pintype "passive"))
      (node (ref "J17") (pin "J1") (pinfunction "IN3_J1") (pintype "input"))
      (node (ref "J17") (pin "K1") (pinfunction "IN4_K1") (pintype "input"))
    )
    (net (code "1480") (name "Net-(J17G-IN2)") (class "Default")
      (node (ref "J17") (pin "L2") (pinfunction "IN2_L2") (pintype "passive"))
      (node (ref "J17") (pin "M2") (pinfunction "IN3_M2") (pintype "input"))
      (node (ref "J17") (pin "N2") (pinfunction "IN4_N2") (pintype "input"))
    )
    (net (code "1481") (name "Net-(J17H-IN2)") (class "Default")
      (node (ref "J17") (pin "N1") (pinfunction "IN2_N1") (pintype "passive"))
      (node (ref "J17") (pin "P1") (pinfunction "IN3_P1") (pintype "input"))
      (node (ref "J17") (pin "R1") (pinfunction "IN4_R1") (pintype "input"))
    )
    (net (code "1482") (name "Net-(J17I-IN2)") (class "Default")
      (node (ref "J17") (pin "S2") (pinfunction "IN2_S2") (pintype "passive"))
      (node (ref "J17") (pin "T2") (pinfunction "IN3_T2") (pintype "input"))
      (node (ref "J17") (pin "U2") (pinfunction "IN4_U2") (pintype "input"))
    )
    (net (code "1483") (name "Net-(J18A-IN2)") (class "Default")
      (node (ref "J18") (pin "B1") (pinfunction "IN2_B1") (pintype "passive"))
      (node (ref "J18") (pin "C1") (pinfunction "IN3_C1") (pintype "input"))
      (node (ref "J18") (pin "D1") (pinfunction "IN4_D1") (pintype "input"))
    )
    (net (code "1484") (name "Net-(J18E-IN2)") (class "Default")
      (node (ref "J18") (pin "E2") (pinfunction "IN2_E2") (pintype "passive"))
      (node (ref "J18") (pin "F2") (pinfunction "IN3_F2") (pintype "input"))
      (node (ref "J18") (pin "H2") (pinfunction "IN4_H2") (pintype "input"))
    )
    (net (code "1485") (name "Net-(J18F-IN2)") (class "Default")
      (node (ref "J18") (pin "H1") (pinfunction "IN2_H1") (pintype "passive"))
      (node (ref "J18") (pin "J1") (pinfunction "IN3_J1") (pintype "input"))
      (node (ref "J18") (pin "K1") (pinfunction "IN4_K1") (pintype "input"))
    )
    (net (code "1486") (name "Net-(J18G-IN2)") (class "Default")
      (node (ref "J18") (pin "L2") (pinfunction "IN2_L2") (pintype "passive"))
      (node (ref "J18") (pin "M2") (pinfunction "IN3_M2") (pintype "input"))
      (node (ref "J18") (pin "N2") (pinfunction "IN4_N2") (pintype "input"))
    )
    (net (code "1487") (name "Net-(J18H-IN2)") (class "Default")
      (node (ref "J18") (pin "N1") (pinfunction "IN2_N1") (pintype "passive"))
      (node (ref "J18") (pin "P1") (pinfunction "IN3_P1") (pintype "input"))
      (node (ref "J18") (pin "R1") (pinfunction "IN4_R1") (pintype "input"))
    )
    (net (code "1488") (name "Net-(J18I-IN2)") (class "Default")
      (node (ref "J18") (pin "S2") (pinfunction "IN2_S2") (pintype "passive"))
      (node (ref "J18") (pin "T2") (pinfunction "IN3_T2") (pintype "input"))
      (node (ref "J18") (pin "U2") (pinfunction "IN4_U2") (pintype "input"))
    )
    (net (code "1489") (name "Net-(J19A-IN2)") (class "Default")
      (node (ref "J19") (pin "B1") (pinfunction "IN2_B1") (pintype "passive"))
      (node (ref "J19") (pin "C1") (pinfunction "IN3_C1") (pintype "input"))
      (node (ref "J19") (pin "D1") (pinfunction "IN4_D1") (pintype "input"))
    )
    (net (code "1490") (name "Net-(J19E-IN2)") (class "Default")
      (node (ref "J19") (pin "E2") (pinfunction "IN2_E2") (pintype "passive"))
      (node (ref "J19") (pin "F2") (pinfunction "IN3_F2") (pintype "input"))
      (node (ref "J19") (pin "H2") (pinfunction "IN4_H2") (pintype "input"))
    )
    (net (code "1491") (name "Net-(J19F-IN2)") (class "Default")
      (node (ref "J19") (pin "H1") (pinfunction "IN2_H1") (pintype "passive"))
      (node (ref "J19") (pin "J1") (pinfunction "IN3_J1") (pintype "input"))
      (node (ref "J19") (pin "K1") (pinfunction "IN4_K1") (pintype "input"))
    )
    (net (code "1492") (name "Net-(J19G-IN2)") (class "Default")
      (node (ref "J19") (pin "L2") (pinfunction "IN2_L2") (pintype "passive"))
      (node (ref "J19") (pin "M2") (pinfunction "IN3_M2") (pintype "input"))
      (node (ref "J19") (pin "N2") (pinfunction "IN4_N2") (pintype "input"))
    )
    (net (code "1493") (name "Net-(J19H-IN2)") (class "Default")
      (node (ref "J19") (pin "N1") (pinfunction "IN2_N1") (pintype "passive"))
      (node (ref "J19") (pin "P1") (pinfunction "IN3_P1") (pintype "input"))
      (node (ref "J19") (pin "R1") (pinfunction "IN4_R1") (pintype "input"))
    )
    (net (code "1494") (name "Net-(J19I-IN2)") (class "Default")
      (node (ref "J19") (pin "S2") (pinfunction "IN2_S2") (pintype "passive"))
      (node (ref "J19") (pin "T2") (pinfunction "IN3_T2") (pintype "input"))
      (node (ref "J19") (pin "U2") (pinfunction "IN4_U2") (pintype "input"))
    )
    (net (code "1495") (name "Net-(J20A-IN2)") (class "Default")
      (node (ref "J20") (pin "B1") (pinfunction "IN2_B1") (pintype "passive"))
      (node (ref "J20") (pin "C1") (pinfunction "IN3_C1") (pintype "input"))
      (node (ref "J20") (pin "D1") (pinfunction "IN4_D1") (pintype "input"))
    )
    (net (code "1496") (name "Net-(J20E-IN2)") (class "Default")
      (node (ref "J20") (pin "E2") (pinfunction "IN2_E2") (pintype "passive"))
      (node (ref "J20") (pin "F2") (pinfunction "IN3_F2") (pintype "input"))
      (node (ref "J20") (pin "H2") (pinfunction "IN4_H2") (pintype "input"))
    )
    (net (code "1497") (name "Net-(J20F-IN2)") (class "Default")
      (node (ref "J20") (pin "H1") (pinfunction "IN2_H1") (pintype "passive"))
      (node (ref "J20") (pin "J1") (pinfunction "IN3_J1") (pintype "input"))
      (node (ref "J20") (pin "K1") (pinfunction "IN4_K1") (pintype "input"))
    )
    (net (code "1498") (name "Net-(J20G-IN2)") (class "Default")
      (node (ref "J20") (pin "L2") (pinfunction "IN2_L2") (pintype "passive"))
      (node (ref "J20") (pin "M2") (pinfunction "IN3_M2") (pintype "input"))
      (node (ref "J20") (pin "N2") (pinfunction "IN4_N2") (pintype "input"))
    )
    (net (code "1499") (name "Net-(J20H-IN2)") (class "Default")
      (node (ref "J20") (pin "N1") (pinfunction "IN2_N1") (pintype "passive"))
      (node (ref "J20") (pin "P1") (pinfunction "IN3_P1") (pintype "input"))
      (node (ref "J20") (pin "R1") (pinfunction "IN4_R1") (pintype "input"))
    )
    (net (code "1500") (name "Net-(J20I-IN2)") (class "Default")
      (node (ref "J20") (pin "S2") (pinfunction "IN2_S2") (pintype "passive"))
      (node (ref "J20") (pin "T2") (pinfunction "IN3_T2") (pintype "input"))
      (node (ref "J20") (pin "U2") (pinfunction "IN4_U2") (pintype "input"))
    )
    (net (code "1501") (name "OP1") (class "Default")
      (node (ref "E27") (pin "H1") (pinfunction "IN3A_H1") (pintype "input"))
      (node (ref "E28") (pin "C1") (pinfunction "IN1C_C1") (pintype "input"))
      (node (ref "E28") (pin "N1") (pinfunction "IN5B_N1") (pintype "input"))
      (node (ref "E30") (pin "L2") (pinfunction "IN3A_L2") (pintype "input"))
      (node (ref "F25") (pin "C1") (pinfunction "OUT_C1") (pintype "output"))
      (node (ref "F26") (pin "B1") (pinfunction "IN2_B1") (pintype "input"))
      (node (ref "F26") (pin "E2") (pinfunction "IN2_E2") (pintype "input"))
      (node (ref "F26") (pin "F1") (pinfunction "IN2_F1") (pintype "input"))
      (node (ref "F26") (pin "K2") (pinfunction "IN2_K2") (pintype "input"))
      (node (ref "F26") (pin "L1") (pinfunction "IN2_L1") (pintype "input"))
      (node (ref "F29") (pin "T2") (pinfunction "IN1_T2") (pintype "input"))
      (node (ref "F32") (pin "H2") (pinfunction "IN1_H2") (pintype "input"))
    )
    (net (code "1502") (name "OP1_") (class "Default")
      (node (ref "F24") (pin "A1") (pinfunction "IN1_A1") (pintype "input"))
      (node (ref "F25") (pin "A1") (pinfunction "IN1_A1") (pintype "input"))
      (node (ref "F27") (pin "V2") (pinfunction "OUT_V2") (pintype "output"))
    )
    (net (code "1503") (name "OP2") (class "Default")
      (node (ref "B04") (pin "E2") (pinfunction "IN2_E2") (pintype "input"))
      (node (ref "D18") (pin "E2") (pinfunction "IN2_E2") (pintype "input"))
      (node (ref "D18") (pin "F1") (pinfunction "IN2_F1") (pintype "input"))
      (node (ref "D21") (pin "K1") (pinfunction "IN4_K1") (pintype "input"))
      (node (ref "E13") (pin "C1") (pinfunction "IN1C_C1") (pintype "input"))
      (node (ref "E25") (pin "R2") (pinfunction "IN3_R2") (pintype "input"))
      (node (ref "E28") (pin "P2") (pinfunction "IN4B_P2") (pintype "input"))
      (node (ref "E30") (pin "D2") (pinfunction "IN1A_D2") (pintype "input"))
      (node (ref "F28") (pin "N2") (pinfunction "IN1_N2") (pintype "input"))
      (node (ref "F29") (pin "K1") (pinfunction "OUT_K1") (pintype "output"))
    )
    (net (code "1504") (name "OPR") (class "Default")
      (node (ref "D13") (pin "L2") (pinfunction "IN1_L2") (pintype "input"))
      (node (ref "D14") (pin "D2") (pinfunction "IN1_D2") (pintype "input"))
      (node (ref "D20") (pin "N1") (pinfunction "IN2_N1") (pintype "input"))
      (node (ref "D21") (pin "F2") (pinfunction "IN3_F2") (pintype "input"))
      (node (ref "E22") (pin "S2") (pinfunction "OUT_S2") (pintype "output"))
      (node (ref "E25") (pin "V2") (pinfunction "IN3_V2") (pintype "input"))
      (node (ref "E26") (pin "S2") (pinfunction "IN4D_S2") (pintype "input"))
      (node (ref "F27") (pin "F1") (pinfunction "IN1_F1") (pintype "input"))
      (node (ref "F27") (pin "R2") (pinfunction "IN1_R2") (pintype "input"))
    )
    (net (code "1505") (name "OPR_") (class "Default")
      (node (ref "D40") (pin "D2") (pinfunction "P$2_D2") (pintype "bidirectional"))
      (node (ref "E21") (pin "V1") (pinfunction "OUT_V1") (pintype "output"))
      (node (ref "E22") (pin "P2") (pinfunction "IN1_P2") (pintype "input"))
    )
    (net (code "1506") (name "OSR_") (class "Default")
      (node (ref "A06") (pin "E2") (pinfunction "IN2_E2") (pintype "input"))
      (node (ref "F28") (pin "S2") (pinfunction "OUT_S2") (pintype "output"))
    )
    (net (code "1507") (name "OUT_STOP2_") (class "Default")
      (node (ref "EF02") (pin "BN1") (pinfunction "BN1_BN1") (pintype "output"))
      (node (ref "EF02") (pin "BN2") (pinfunction "BN2_BN2") (pintype "input"))
    )
    (net (code "1508") (name "OVERFLOW") (class "Default")
      (node (ref "H30") (pin "V1") (pinfunction "V1_V1") (pintype "input"))
      (node (ref "HJ31") (pin "BS1") (pinfunction "BS1_BS1") (pintype "output"))
    )
    (net (code "1509") (name "PAUSE_") (class "Default")
      (node (ref "D40") (pin "M1") (pinfunction "P$2_M1") (pintype "bidirectional"))
      (node (ref "E14") (pin "B1") (pinfunction "IN2_B1") (pintype "input"))
      (node (ref "E18") (pin "M1") (pinfunction "0_M1") (pintype "output"))
    )
    (net (code "1510") (name "PC00_") (class "Default")
      (node (ref "E40") (pin "J2") (pinfunction "P$2_J2") (pintype "bidirectional"))
      (node (ref "EF34") (pin "AR2") (pinfunction "AR2_AR2") (pintype "output"))
    )
    (net (code "1511") (name "PC01_") (class "Default")
      (node (ref "E40") (pin "S1") (pinfunction "P$2_S1") (pintype "bidirectional"))
      (node (ref "EF34") (pin "AP2") (pinfunction "AP2_AP2") (pintype "output"))
    )
    (net (code "1512") (name "PC02_") (class "Default")
      (node (ref "E40") (pin "P2") (pinfunction "P$2_P2") (pintype "bidirectional"))
      (node (ref "EF35") (pin "AR2") (pinfunction "AR2_AR2") (pintype "output"))
    )
    (net (code "1513") (name "PC03_") (class "Default")
      (node (ref "E40") (pin "N1") (pinfunction "P$2_N1") (pintype "bidirectional"))
      (node (ref "EF35") (pin "AP2") (pinfunction "AP2_AP2") (pintype "output"))
    )
    (net (code "1514") (name "PC04_") (class "Default")
      (node (ref "E40") (pin "C1") (pinfunction "P$2_C1") (pintype "bidirectional"))
      (node (ref "EF36") (pin "AR2") (pinfunction "AR2_AR2") (pintype "output"))
    )
    (net (code "1515") (name "PC05_") (class "Default")
      (node (ref "E40") (pin "D1") (pinfunction "P$2_D1") (pintype "bidirectional"))
      (node (ref "EF36") (pin "AP2") (pinfunction "AP2_AP2") (pintype "output"))
    )
    (net (code "1516") (name "PC06_") (class "Default")
      (node (ref "EF37") (pin "AR2") (pinfunction "AR2_AR2") (pintype "output"))
      (node (ref "F40") (pin "J2") (pinfunction "P$2_J2") (pintype "bidirectional"))
    )
    (net (code "1517") (name "PC07_") (class "Default")
      (node (ref "EF37") (pin "AP2") (pinfunction "AP2_AP2") (pintype "output"))
      (node (ref "F40") (pin "S1") (pinfunction "P$2_S1") (pintype "bidirectional"))
    )
    (net (code "1518") (name "PC08_") (class "Default")
      (node (ref "EF38") (pin "AR2") (pinfunction "AR2_AR2") (pintype "output"))
      (node (ref "F40") (pin "P2") (pinfunction "P$2_P2") (pintype "bidirectional"))
    )
    (net (code "1519") (name "PC09_") (class "Default")
      (node (ref "EF38") (pin "AP2") (pinfunction "AP2_AP2") (pintype "output"))
      (node (ref "F40") (pin "N1") (pinfunction "P$2_N1") (pintype "bidirectional"))
    )
    (net (code "1520") (name "PC10_") (class "Default")
      (node (ref "EF39") (pin "AR2") (pinfunction "AR2_AR2") (pintype "output"))
      (node (ref "F40") (pin "C1") (pinfunction "P$2_C1") (pintype "bidirectional"))
    )
    (net (code "1521") (name "PC11_") (class "Default")
      (node (ref "EF39") (pin "AP2") (pinfunction "AP2_AP2") (pintype "output"))
      (node (ref "F40") (pin "D1") (pinfunction "P$2_D1") (pintype "bidirectional"))
    )
    (net (code "1522") (name "PC_ENABLE") (class "Default")
      (node (ref "EF34") (pin "BS2") (pinfunction "BS2_BS2") (pintype "input"))
      (node (ref "EF35") (pin "BS2") (pinfunction "BS2_BS2") (pintype "input"))
      (node (ref "EF36") (pin "BS2") (pinfunction "BS2_BS2") (pintype "input"))
      (node (ref "EF37") (pin "BS2") (pinfunction "BS2_BS2") (pintype "input"))
      (node (ref "EF38") (pin "BS2") (pinfunction "BS2_BS2") (pintype "input"))
      (node (ref "EF39") (pin "BS2") (pinfunction "BS2_BS2") (pintype "input"))
      (node (ref "F30") (pin "E1") (pinfunction "OUT_E1") (pintype "open_collector"))
    )
    (net (code "1523") (name "PC_ENABLE_") (class "Default")
      (node (ref "F09") (pin "M2") (pinfunction "IN7_M2") (pintype "input"))
      (node (ref "F11") (pin "P1") (pinfunction "IN3_P1") (pintype "input"))
      (node (ref "F27") (pin "H2") (pinfunction "IN4_H2") (pintype "input"))
      (node (ref "F32") (pin "N1") (pinfunction "OUT_N1") (pintype "output"))
    )
    (net (code "1524") (name "PC_INCREMENT") (class "Default")
      (node (ref "E26") (pin "F1") (pinfunction "IN2B_F1") (pintype "input"))
      (node (ref "E27") (pin "F1") (pinfunction "IN2B_F1") (pintype "input"))
      (node (ref "E30") (pin "F1") (pinfunction "IN2B_F1") (pintype "input"))
      (node (ref "F28") (pin "V1") (pinfunction "OUT_V1") (pintype "output"))
    )
    (net (code "1525") (name "PC_LOAD") (class "Default")
      (node (ref "A15") (pin "H1") (pinfunction "IN1_H1") (pintype "input"))
      (node (ref "E32") (pin "J2") (pinfunction "OUT_J2") (pintype "open_collector"))
      (node (ref "EF34") (pin "AN2") (pinfunction "AN2_AN2") (pintype "input"))
      (node (ref "EF35") (pin "AN2") (pinfunction "AN2_AN2") (pintype "input"))
      (node (ref "EF36") (pin "AN2") (pinfunction "AN2_AN2") (pintype "input"))
      (node (ref "EF37") (pin "AN2") (pinfunction "AN2_AN2") (pintype "input"))
      (node (ref "EF38") (pin "AN2") (pinfunction "AN2_AN2") (pintype "input"))
      (node (ref "EF39") (pin "AN2") (pinfunction "AN2_AN2") (pintype "input"))
      (node (ref "F25") (pin "P1") (pinfunction "IN1_P1") (pintype "input"))
    )
    (net (code "1526") (name "PC_LOADXSR_ENABLE_") (class "Default")
      (node (ref "A15") (pin "K1") (pinfunction "OUT_K1") (pintype "output"))
      (node (ref "A17") (pin "A1") (pinfunction "IN1_A1") (pintype "input"))
      (node (ref "A17") (pin "R2") (pinfunction "IN2_R2") (pintype "input"))
      (node (ref "A18") (pin "A1") (pinfunction "IN1_A1") (pintype "input"))
      (node (ref "B06") (pin "H1") (pinfunction "IN1_H1") (pintype "input"))
    )
    (net (code "1527") (name "PC_LOAD_") (class "Default")
      (node (ref "B04") (pin "M1") (pinfunction "IN3_M1") (pintype "input"))
      (node (ref "E18") (pin "R1") (pinfunction "S_R1") (pintype "input"))
      (node (ref "F25") (pin "S1") (pinfunction "OUT_S1") (pintype "output"))
    )
    (net (code "1528") (name "PEN_DOWN") (class "Default")
      (node (ref "D02") (pin "V2") (pinfunction "P$2_V2") (pintype "bidirectional"))
      (node (ref "HJ29") (pin "AV2") (pinfunction "AV2_AV2") (pintype "output"))
    )
    (net (code "1529") (name "PEN_LEFT") (class "Default")
      (node (ref "D02") (pin "R2") (pinfunction "P$2_R2") (pintype "bidirectional"))
      (node (ref "HJ29") (pin "AL2") (pinfunction "AL2_AL2") (pintype "output"))
    )
    (net (code "1530") (name "PEN_RIGHT") (class "Default")
      (node (ref "D02") (pin "P2") (pinfunction "P$2_P2") (pintype "bidirectional"))
      (node (ref "HJ29") (pin "AJ2") (pinfunction "AJ2_AJ2") (pintype "output"))
    )
    (net (code "1531") (name "PEN_STROBE") (class "Default")
      (node (ref "HJ23") (pin "AJ1") (pinfunction "AJ1_AJ1") (pintype "output"))
      (node (ref "HJ23") (pin "AK1") (pinfunction "AK1_AK1") (pintype "input"))
    )
    (net (code "1532") (name "PEN_UP") (class "Default")
      (node (ref "D02") (pin "U2") (pinfunction "P$2_U2") (pintype "bidirectional"))
      (node (ref "HJ29") (pin "AT2") (pinfunction "AT2_AT2") (pintype "output"))
    )
    (net (code "1533") (name "POWER_CLEAR_") (class "Default")
      (node (ref "AB02") (pin "AS2") (pinfunction "AS2_AS2") (pintype "bidirectional"))
      (node (ref "B21") (pin "T2") (pinfunction "IN1_T2") (pintype "input"))
      (node (ref "B21") (pin "U2") (pinfunction "IN2_U2") (pintype "input"))
    )
    (net (code "1534") (name "POWER_OK_") (class "Default")
      (node (ref "AB02") (pin "AJ2") (pinfunction "AJ2_AJ2") (pintype "bidirectional"))
      (node (ref "E13") (pin "L1") (pinfunction "IN4B_L1") (pintype "input"))
    )
    (net (code "1535") (name "PROCESSOR_IOT_") (class "Default")
      (node (ref "F19") (pin "D1") (pinfunction "IN4_D1") (pintype "input"))
      (node (ref "F21") (pin "V2") (pinfunction "OUT_V2") (pintype "output"))
    )
    (net (code "1536") (name "PUN_FEED_SWITCH_") (class "Default")
      (node (ref "C01") (pin "U2") (pinfunction "P$2_U2") (pintype "bidirectional"))
      (node (ref "HJ28") (pin "AT2") (pinfunction "AT2_AT2") (pintype "input"))
    )
    (net (code "1537") (name "PWR") (class "Default")
      (node (ref "D01") (pin "U2") (pinfunction "P$2_U2") (pintype "bidirectional"))
      (node (ref "HJ26") (pin "BR2") (pinfunction "BR2_BR2") (pintype "output"))
    )
    (net (code "1538") (name "PWR_LOW_") (class "Default")
      (node (ref "A04") (pin "R2") (pinfunction "R2_R2") (pintype "output"))
      (node (ref "F19") (pin "M1") (pinfunction "IN1_M1") (pintype "input"))
    )
    (net (code "1539") (name "PWR_SKIP_") (class "Default")
      (node (ref "A04") (pin "L2") (pinfunction "L2_L2") (pintype "output"))
      (node (ref "F19") (pin "M2") (pinfunction "IN3_M2") (pintype "input"))
    )
    (net (code "1540") (name "R0") (class "Default")
      (node (ref "C09") (pin "L2") (pinfunction "IN1_L2") (pintype "input"))
      (node (ref "D05") (pin "J2") (pinfunction "OUT_J2") (pintype "output"))
      (node (ref "D10") (pin "R2") (pinfunction "IN1_R2") (pintype "input"))
    )
    (net (code "1541") (name "R0_") (class "Default")
      (node (ref "C09") (pin "N2") (pinfunction "OUT_N2") (pintype "output"))
      (node (ref "D10") (pin "M1") (pinfunction "IN1_M1") (pintype "input"))
    )
    (net (code "1542") (name "RDR_ENABLE_") (class "Default")
      (node (ref "HJ26") (pin "BK2") (pinfunction "BK2_BK2") (pintype "output"))
      (node (ref "HJ27") (pin "AK2") (pinfunction "AK_AK2") (pintype "input"))
    )
    (net (code "1543") (name "RDR_FEED_SWITCH") (class "Default")
      (node (ref "D01") (pin "V2") (pinfunction "P$2_V2") (pintype "bidirectional"))
      (node (ref "HJ26") (pin "BM1") (pinfunction "BM1_BM1") (pintype "input"))
      (node (ref "HJ27") (pin "BP2") (pinfunction "BP_BP2") (pintype "input"))
    )
    (net (code "1544") (name "RDR_RUN_") (class "Default")
      (node (ref "HJ26") (pin "AK1") (pinfunction "AK1_AK1") (pintype "output"))
      (node (ref "HJ27") (pin "BS2") (pinfunction "BS_BS2") (pintype "input"))
    )
    (net (code "1545") (name "RDR_SHIFT") (class "Default")
      (node (ref "HJ26") (pin "BJ1") (pinfunction "BJ1_BJ1") (pintype "input"))
      (node (ref "HJ27") (pin "AS2") (pinfunction "AS_AS2") (pintype "output"))
    )
    (net (code "1546") (name "RDR_SHIFT_") (class "Default")
      (node (ref "HJ26") (pin "BD1") (pinfunction "BD1_BD1") (pintype "input"))
      (node (ref "HJ27") (pin "AT2") (pinfunction "AT_AT2") (pintype "output"))
    )
    (net (code "1547") (name "RD_HOLE1") (class "Default")
      (node (ref "D01") (pin "D2") (pinfunction "P$2_D2") (pintype "bidirectional"))
      (node (ref "HJ26") (pin "AD2") (pinfunction "AD2_AD2") (pintype "input"))
    )
    (net (code "1548") (name "RD_HOLE2") (class "Default")
      (node (ref "D01") (pin "E2") (pinfunction "P$2_E2") (pintype "bidirectional"))
      (node (ref "HJ26") (pin "AD1") (pinfunction "AD1_AD1") (pintype "input"))
    )
    (net (code "1549") (name "RD_HOLE3") (class "Default")
      (node (ref "D01") (pin "F2") (pinfunction "P$2_F2") (pintype "bidirectional"))
      (node (ref "HJ26") (pin "AE2") (pinfunction "AE2_AE2") (pintype "input"))
    )
    (net (code "1550") (name "RD_HOLE4") (class "Default")
      (node (ref "D01") (pin "H2") (pinfunction "P$2_H2") (pintype "bidirectional"))
      (node (ref "HJ26") (pin "AE1") (pinfunction "AE1_AE1") (pintype "input"))
    )
    (net (code "1551") (name "RD_HOLE5") (class "Default")
      (node (ref "D01") (pin "J2") (pinfunction "P$2_J2") (pintype "bidirectional"))
      (node (ref "HJ26") (pin "AH2") (pinfunction "AH2_AH2") (pintype "input"))
    )
    (net (code "1552") (name "RD_HOLE6") (class "Default")
      (node (ref "D01") (pin "K2") (pinfunction "P$2_K2") (pintype "bidirectional"))
      (node (ref "HJ26") (pin "AH1") (pinfunction "AH1_AH1") (pintype "input"))
    )
    (net (code "1553") (name "RD_HOLE7") (class "Default")
      (node (ref "D01") (pin "L2") (pinfunction "P$2_L2") (pintype "bidirectional"))
      (node (ref "HJ26") (pin "AF2") (pinfunction "AF2_AF2") (pintype "input"))
    )
    (net (code "1554") (name "RD_HOLE8") (class "Default")
      (node (ref "D01") (pin "M2") (pinfunction "P$2_M2") (pintype "bidirectional"))
      (node (ref "HJ26") (pin "AF1") (pinfunction "AF1_AF1") (pintype "input"))
    )
    (net (code "1555") (name "READ") (class "Default")
      (node (ref "B22") (pin "L1") (pinfunction "1_L1") (pintype "output"))
      (node (ref "C39") (pin "D2") (pinfunction "D2_D2") (pintype "input"))
      (node (ref "C39") (pin "M2") (pinfunction "M2_M2") (pintype "input"))
      (node (ref "D39") (pin "D2") (pinfunction "D2_D2") (pintype "input"))
      (node (ref "D39") (pin "M2") (pinfunction "M2_M2") (pintype "input"))
    )
    (net (code "1556") (name "READER_RUN_") (class "Default")
      (node (ref "EF01") (pin "AU2") (pinfunction "AU2_AU2") (pintype "output"))
      (node (ref "J12") (pin "M2") (pinfunction "P$2_M2") (pintype "bidirectional"))
    )
    (net (code "1557") (name "RESTART") (class "Default")
      (node (ref "A04") (pin "N2") (pinfunction "N2_N2") (pintype "output"))
      (node (ref "E12") (pin "L2") (pinfunction "IN1_L2") (pintype "input"))
    )
    (net (code "1558") (name "RESTART_") (class "Default")
      (node (ref "A04") (pin "U1") (pinfunction "U1_U1") (pintype "output"))
      (node (ref "E11") (pin "E1") (pinfunction "IN2_E1") (pintype "input"))
      (node (ref "E14") (pin "D2") (pinfunction "IN1_D2") (pintype "input"))
      (node (ref "E14") (pin "K2") (pinfunction "IN2_K2") (pintype "input"))
      (node (ref "EF10") (pin "AR2") (pinfunction "CR2_AR2") (pintype "input"))
    )
    (net (code "1559") (name "RIB") (class "Default")
      (node (ref "A05") (pin "H2") (pinfunction "IN1_H2") (pintype "input"))
      (node (ref "A11") (pin "D2") (pinfunction "IN1_D2") (pintype "input"))
      (node (ref "A11") (pin "L1") (pinfunction "IN1_L1") (pintype "input"))
      (node (ref "A11") (pin "P2") (pinfunction "IN1_P2") (pintype "input"))
      (node (ref "A13") (pin "H2") (pinfunction "IN1_H2") (pintype "input"))
      (node (ref "A13") (pin "L2") (pinfunction "IN1_L2") (pintype "input"))
      (node (ref "A13") (pin "P2") (pinfunction "IN1_P2") (pintype "input"))
      (node (ref "A14") (pin "N2") (pinfunction "OUT_N2") (pintype "output"))
    )
    (net (code "1560") (name "RIGHT_SHIFT") (class "Default")
      (node (ref "C14") (pin "A1") (pinfunction "IN1_A1") (pintype "input"))
      (node (ref "C14") (pin "H1") (pinfunction "IN1_H1") (pintype "input"))
      (node (ref "C14") (pin "L2") (pinfunction "IN1_L2") (pintype "input"))
      (node (ref "C15") (pin "A1") (pinfunction "IN1_A1") (pintype "input"))
      (node (ref "C15") (pin "H1") (pinfunction "IN1_H1") (pintype "input"))
      (node (ref "C15") (pin "L2") (pinfunction "IN1_L2") (pintype "input"))
      (node (ref "C16") (pin "A1") (pinfunction "IN1_A1") (pintype "input"))
      (node (ref "C16") (pin "H1") (pinfunction "IN1_H1") (pintype "input"))
      (node (ref "C16") (pin "L2") (pinfunction "IN1_L2") (pintype "input"))
      (node (ref "C17") (pin "A1") (pinfunction "IN1_A1") (pintype "input"))
      (node (ref "C17") (pin "H1") (pinfunction "IN1_H1") (pintype "input"))
      (node (ref "C17") (pin "L2") (pinfunction "IN1_L2") (pintype "input"))
      (node (ref "E31") (pin "L1") (pinfunction "OUT_L1") (pintype "open_collector"))
      (node (ref "EF34") (pin "AD2") (pinfunction "AD2_AD2") (pintype "input"))
      (node (ref "EF35") (pin "AD2") (pinfunction "AD2_AD2") (pintype "input"))
      (node (ref "EF36") (pin "AD2") (pinfunction "AD2_AD2") (pintype "input"))
      (node (ref "EF37") (pin "AD2") (pinfunction "AD2_AD2") (pintype "input"))
      (node (ref "EF38") (pin "AD2") (pinfunction "AD2_AD2") (pintype "input"))
      (node (ref "EF39") (pin "AD2") (pinfunction "AD2_AD2") (pintype "input"))
      (node (ref "F33") (pin "D1") (pinfunction "IN1D_D1") (pintype "input"))
    )
    (net (code "1561") (name "RMF_") (class "Default")
      (node (ref "A06") (pin "V2") (pinfunction "OUT_V2") (pintype "output"))
      (node (ref "A13") (pin "B1") (pinfunction "IN2_B1") (pintype "input"))
      (node (ref "A15") (pin "L2") (pinfunction "IN1_L2") (pintype "input"))
      (node (ref "A15") (pin "M1") (pinfunction "IN2_M1") (pintype "input"))
      (node (ref "B06") (pin "E1") (pinfunction "IN2_E1") (pintype "input"))
    )
    (net (code "1562") (name "RUN") (class "Default")
      (node (ref "B10") (pin "J2") (pinfunction "J2_J2") (pintype "input"))
      (node (ref "E14") (pin "C1") (pinfunction "IN3_C1") (pintype "input"))
      (node (ref "E18") (pin "P2") (pinfunction "1_P2") (pintype "output"))
    )
    (net (code "1563") (name "RUN_") (class "Default")
      (node (ref "D40") (pin "F1") (pinfunction "P$2_F1") (pintype "bidirectional"))
      (node (ref "E18") (pin "R2") (pinfunction "0_R2") (pintype "output"))
      (node (ref "EF10") (pin "AP2") (pinfunction "CP2_AP2") (pintype "input"))
      (node (ref "F21") (pin "E1") (pinfunction "IN2_E1") (pintype "input"))
      (node (ref "H19") (pin "H2") (pinfunction "IN2_H2") (pintype "input"))
    )
    (net (code "1564") (name "RX_DATA") (class "Default")
      (node (ref "EF01") (pin "BM2") (pinfunction "BM2_BM2") (pintype "input"))
      (node (ref "J12") (pin "E2") (pinfunction "P$2_E2") (pintype "bidirectional"))
    )
    (net (code "1565") (name "S") (class "Default")
      (node (ref "C07") (pin "U2") (pinfunction "IN2_U2") (pintype "input"))
      (node (ref "C10") (pin "R1") (pinfunction "IN2_R1") (pintype "input"))
      (node (ref "C11") (pin "L2") (pinfunction "IN3_L2") (pintype "input"))
      (node (ref "C11") (pin "P2") (pinfunction "IN2_P2") (pintype "input"))
      (node (ref "D07") (pin "L1") (pinfunction "IN1_L1") (pintype "input"))
      (node (ref "D07") (pin "T2") (pinfunction "IN1_T2") (pintype "input"))
      (node (ref "D09") (pin "A1") (pinfunction "IN1_A1") (pintype "input"))
      (node (ref "D10") (pin "D2") (pinfunction "IN1_D2") (pintype "input"))
      (node (ref "D10") (pin "K1") (pinfunction "IN4_K1") (pintype "input"))
      (node (ref "D11") (pin "F1") (pinfunction "0_F1") (pintype "output"))
    )
    (net (code "1566") (name "SC0") (class "Default")
      (node (ref "C21") (pin "F2") (pinfunction "IN3_F2") (pintype "input"))
      (node (ref "C22") (pin "E1") (pinfunction "1_E1") (pintype "output"))
      (node (ref "D23") (pin "L1") (pinfunction "IN4B_L1") (pintype "input"))
      (node (ref "EF37") (pin "BN1") (pinfunction "BN1_BN1") (pintype "input"))
    )
    (net (code "1567") (name "SC0_") (class "Default")
      (node (ref "C21") (pin "C1") (pinfunction "IN3_C1") (pintype "input"))
      (node (ref "C22") (pin "F1") (pinfunction "0_F1") (pintype "output"))
      (node (ref "C40") (pin "S2") (pinfunction "P$2_S2") (pintype "bidirectional"))
    )
    (net (code "1568") (name "SC0_3_0") (class "Default")
      (node (ref "C18") (pin "S2") (pinfunction "OUT_S2") (pintype "output"))
      (node (ref "D13") (pin "P2") (pinfunction "IN1_P2") (pintype "input"))
      (node (ref "D19") (pin "E1") (pinfunction "IN1_E1") (pintype "input"))
      (node (ref "D23") (pin "F2") (pinfunction "IN1C_F2") (pintype "input"))
    )
    (net (code "1569") (name "SC0_3_0_") (class "Default")
      (node (ref "C18") (pin "P2") (pinfunction "IN1_P2") (pintype "input"))
      (node (ref "D17") (pin "N2") (pinfunction "IN1_N2") (pintype "input"))
      (node (ref "D22") (pin "J2") (pinfunction "OUT_J2") (pintype "open_collector"))
    )
    (net (code "1570") (name "SC1") (class "Default")
      (node (ref "C21") (pin "L2") (pinfunction "IN3_L2") (pintype "input"))
      (node (ref "C22") (pin "H2") (pinfunction "1_H2") (pintype "output"))
      (node (ref "D17") (pin "E1") (pinfunction "IN1_E1") (pintype "input"))
      (node (ref "D19") (pin "J2") (pinfunction "IN1_J2") (pintype "input"))
      (node (ref "D20") (pin "L2") (pinfunction "IN2_L2") (pintype "input"))
      (node (ref "D22") (pin "A1") (pinfunction "IN1_A1") (pintype "input"))
      (node (ref "D23") (pin "B1") (pinfunction "IN1B_B1") (pintype "input"))
      (node (ref "EF38") (pin "BD1") (pinfunction "BD1_BD1") (pintype "input"))
    )
    (net (code "1571") (name "SC1_") (class "Default")
      (node (ref "C21") (pin "H1") (pinfunction "IN3_H1") (pintype "input"))
      (node (ref "C22") (pin "J2") (pinfunction "0_J2") (pintype "output"))
      (node (ref "C40") (pin "M2") (pinfunction "P$2_M2") (pintype "bidirectional"))
      (node (ref "D22") (pin "E2") (pinfunction "IN2_E2") (pintype "input"))
    )
    (net (code "1572") (name "SC2") (class "Default")
      (node (ref "C21") (pin "R2") (pinfunction "IN3_R2") (pintype "input"))
      (node (ref "C22") (pin "L1") (pinfunction "1_L1") (pintype "output"))
      (node (ref "D17") (pin "H1") (pinfunction "IN3_H1") (pintype "input"))
      (node (ref "D19") (pin "A1") (pinfunction "IN1_A1") (pintype "input"))
      (node (ref "D19") (pin "L2") (pinfunction "IN3_L2") (pintype "input"))
      (node (ref "D22") (pin "B1") (pinfunction "IN2_B1") (pintype "input"))
      (node (ref "EF38") (pin "BN1") (pinfunction "BN1_BN1") (pintype "input"))
    )
    (net (code "1573") (name "SC2_") (class "Default")
      (node (ref "C21") (pin "M1") (pinfunction "IN3_M1") (pintype "input"))
      (node (ref "C22") (pin "M1") (pinfunction "0_M1") (pintype "output"))
      (node (ref "C40") (pin "N2") (pinfunction "P$2_N2") (pintype "bidirectional"))
      (node (ref "D22") (pin "F2") (pinfunction "IN3_F2") (pintype "input"))
    )
    (net (code "1574") (name "SC3") (class "Default")
      (node (ref "C18") (pin "H1") (pinfunction "IN1_H1") (pintype "input"))
      (node (ref "C21") (pin "U2") (pinfunction "IN2_U2") (pintype "input"))
      (node (ref "C22") (pin "P2") (pinfunction "1_P2") (pintype "output"))
      (node (ref "D19") (pin "B1") (pinfunction "IN2_B1") (pintype "input"))
      (node (ref "D22") (pin "C1") (pinfunction "IN3_C1") (pintype "input"))
      (node (ref "D23") (pin "C1") (pinfunction "IN1C_C1") (pintype "input"))
      (node (ref "EF39") (pin "BD1") (pinfunction "BD1_BD1") (pintype "input"))
    )
    (net (code "1575") (name "SC3_") (class "Default")
      (node (ref "C21") (pin "P1") (pinfunction "IN1_P1") (pintype "input"))
      (node (ref "C22") (pin "R2") (pinfunction "0_R2") (pintype "output"))
      (node (ref "C40") (pin "L2") (pinfunction "P$2_L2") (pintype "bidirectional"))
      (node (ref "D22") (pin "H2") (pinfunction "IN4_H2") (pintype "input"))
    )
    (net (code "1576") (name "SC4") (class "Default")
      (node (ref "C18") (pin "J1") (pinfunction "IN2_J1") (pintype "input"))
      (node (ref "C21") (pin "S1") (pinfunction "IN3_S1") (pintype "input"))
      (node (ref "C22") (pin "S1") (pinfunction "1_S1") (pintype "output"))
      (node (ref "D19") (pin "C1") (pinfunction "IN3_C1") (pintype "input"))
      (node (ref "D19") (pin "K2") (pinfunction "IN2_K2") (pintype "input"))
      (node (ref "D22") (pin "D1") (pinfunction "IN4_D1") (pintype "input"))
      (node (ref "D23") (pin "D1") (pinfunction "IN1D_D1") (pintype "input"))
      (node (ref "EF39") (pin "BN1") (pinfunction "BN1_BN1") (pintype "input"))
    )
    (net (code "1577") (name "SC4_") (class "Default")
      (node (ref "C18") (pin "M2") (pinfunction "IN2_M2") (pintype "input"))
      (node (ref "C21") (pin "V2") (pinfunction "IN3_V2") (pintype "input"))
      (node (ref "C22") (pin "U1") (pinfunction "0_U1") (pintype "output"))
      (node (ref "C40") (pin "F1") (pinfunction "P$2_F1") (pintype "bidirectional"))
      (node (ref "D13") (pin "R2") (pinfunction "IN2_R2") (pintype "input"))
      (node (ref "D19") (pin "H1") (pinfunction "IN3_H1") (pintype "input"))
      (node (ref "D23") (pin "H2") (pinfunction "IN1D_H2") (pintype "input"))
    )
    (net (code "1578") (name "SCL_") (class "Default")
      (node (ref "D14") (pin "J1") (pinfunction "IN2_J1") (pintype "input"))
      (node (ref "D17") (pin "T2") (pinfunction "IN1_T2") (pintype "input"))
      (node (ref "D19") (pin "S2") (pinfunction "OUT_S2") (pintype "output"))
    )
    (net (code "1579") (name "SC_0_") (class "Default")
      (node (ref "D13") (pin "S2") (pinfunction "OUT_S2") (pintype "output"))
      (node (ref "D13") (pin "T2") (pinfunction "IN1_T2") (pintype "input"))
    )
    (net (code "1580") (name "SC_ENABLE") (class "Default")
      (node (ref "D22") (pin "P2") (pinfunction "OUT_P2") (pintype "open_collector"))
      (node (ref "EF34") (pin "BF2") (pinfunction "BF2_BF2") (pintype "input"))
      (node (ref "EF35") (pin "BF2") (pinfunction "BF2_BF2") (pintype "input"))
      (node (ref "EF36") (pin "BF2") (pinfunction "BF2_BF2") (pintype "input"))
      (node (ref "EF37") (pin "BF2") (pinfunction "BF2_BF2") (pintype "input"))
      (node (ref "EF38") (pin "BF2") (pinfunction "BF2_BF2") (pintype "input"))
      (node (ref "EF39") (pin "BF2") (pinfunction "BF2_BF2") (pintype "input"))
    )
    (net (code "1581") (name "SC_FULL") (class "Default")
      (node (ref "C18") (pin "C1") (pinfunction "OUT_C1") (pintype "output"))
      (node (ref "C21") (pin "B1") (pinfunction "IN2_B1") (pintype "input"))
      (node (ref "D23") (pin "K1") (pinfunction "IN4A_K1") (pintype "input"))
    )
    (net (code "1582") (name "SC_LOAD") (class "Default")
      (node (ref "C22") (pin "B1") (pinfunction "C_B1") (pintype "input"))
      (node (ref "C22") (pin "D2") (pinfunction "C_D2") (pintype "input"))
      (node (ref "C22") (pin "H1") (pinfunction "C_H1") (pintype "input"))
      (node (ref "C22") (pin "L2") (pinfunction "C_L2") (pintype "input"))
      (node (ref "C22") (pin "N1") (pinfunction "C_N1") (pintype "input"))
      (node (ref "D22") (pin "V2") (pinfunction "OUT_V2") (pintype "open_collector"))
    )
    (net (code "1583") (name "SF0") (class "Default")
      (node (ref "A11") (pin "E2") (pinfunction "IN2_E2") (pintype "input"))
      (node (ref "A18") (pin "J1") (pinfunction "IN2_J1") (pintype "input"))
      (node (ref "B19") (pin "E1") (pinfunction "1_E1") (pintype "output"))
    )
    (net (code "1584") (name "SF1") (class "Default")
      (node (ref "A11") (pin "M1") (pinfunction "IN2_M1") (pintype "input"))
      (node (ref "A18") (pin "M2") (pinfunction "IN2_M2") (pintype "input"))
      (node (ref "B19") (pin "H2") (pinfunction "1_H2") (pintype "output"))
    )
    (net (code "1585") (name "SF2") (class "Default")
      (node (ref "A11") (pin "R2") (pinfunction "IN2_R2") (pintype "input"))
      (node (ref "A18") (pin "U2") (pinfunction "IN2_U2") (pintype "input"))
      (node (ref "B19") (pin "L1") (pinfunction "1_L1") (pintype "output"))
    )
    (net (code "1586") (name "SF3") (class "Default")
      (node (ref "A12") (pin "J1") (pinfunction "IN2_J1") (pintype "input"))
      (node (ref "A13") (pin "J2") (pinfunction "IN2_J2") (pintype "input"))
      (node (ref "B19") (pin "P2") (pinfunction "1_P2") (pintype "output"))
    )
    (net (code "1587") (name "SF4") (class "Default")
      (node (ref "A12") (pin "M2") (pinfunction "IN2_M2") (pintype "input"))
      (node (ref "A13") (pin "M2") (pinfunction "IN2_M2") (pintype "input"))
      (node (ref "B19") (pin "S1") (pinfunction "1_S1") (pintype "output"))
    )
    (net (code "1588") (name "SF5") (class "Default")
      (node (ref "A12") (pin "U2") (pinfunction "IN2_U2") (pintype "input"))
      (node (ref "A13") (pin "R2") (pinfunction "IN2_R2") (pintype "input"))
      (node (ref "B19") (pin "V2") (pinfunction "1_V2") (pintype "output"))
    )
    (net (code "1589") (name "SF_ENABLE") (class "Default")
      (node (ref "A12") (pin "H1") (pinfunction "IN1_H1") (pintype "input"))
      (node (ref "A12") (pin "L2") (pinfunction "IN1_L2") (pintype "input"))
      (node (ref "A12") (pin "T2") (pinfunction "IN1_T2") (pintype "input"))
      (node (ref "A15") (pin "N2") (pinfunction "OUT_N2") (pintype "output"))
      (node (ref "A18") (pin "H1") (pinfunction "IN1_H1") (pintype "input"))
      (node (ref "A18") (pin "L2") (pinfunction "IN1_L2") (pintype "input"))
      (node (ref "A18") (pin "T2") (pinfunction "IN1_T2") (pintype "input"))
      (node (ref "B06") (pin "R1") (pinfunction "IN2_R1") (pintype "input"))
    )
    (net (code "1590") (name "SHUT_DOWN_") (class "Default")
      (node (ref "A04") (pin "U2") (pinfunction "U2_U2") (pintype "input"))
      (node (ref "AB02") (pin "AF2") (pinfunction "AF2_AF2") (pintype "output"))
    )
    (net (code "1591") (name "SINT") (class "Default")
      (node (ref "A05") (pin "V2") (pinfunction "OUT_V2") (pintype "output"))
      (node (ref "B04") (pin "L2") (pinfunction "IN3_L2") (pintype "input"))
    )
    (net (code "1592") (name "SKIP_") (class "Default")
      (node (ref "B04") (pin "U2") (pinfunction "IN2_U2") (pintype "input"))
      (node (ref "E18") (pin "S1") (pinfunction "1_S1") (pintype "output"))
      (node (ref "F25") (pin "U2") (pinfunction "IN2_U2") (pintype "input"))
    )
    (net (code "1593") (name "SKIP_OR") (class "Default")
      (node (ref "B04") (pin "V1") (pinfunction "OUT_V1") (pintype "output"))
      (node (ref "E27") (pin "L1") (pinfunction "IN4B_L1") (pintype "input"))
    )
    (net (code "1594") (name "SLICE") (class "Default")
      (node (ref "A30") (pin "S2") (pinfunction "S2_S2") (pintype "passive"))
      (node (ref "A31") (pin "S2") (pinfunction "S2_S2") (pintype "passive"))
      (node (ref "A32") (pin "S2") (pinfunction "S2_S2") (pintype "passive"))
      (node (ref "A33") (pin "S2") (pinfunction "S2_S2") (pintype "passive"))
      (node (ref "B31") (pin "S2") (pinfunction "S2_S2") (pintype "passive"))
      (node (ref "B32") (pin "S2") (pinfunction "S2_S2") (pintype "passive"))
      (node (ref "B33") (pin "S2") (pinfunction "S2_S2") (pintype "passive"))
    )
    (net (code "1595") (name "SLOW_CYCLE") (class "Default")
      (node (ref "E12") (pin "N1") (pinfunction "OUT_N1") (pintype "output"))
      (node (ref "E15") (pin "R1") (pinfunction "IN2_R1") (pintype "input"))
    )
    (net (code "1596") (name "SLOW_CYCLE_") (class "Default")
      (node (ref "E12") (pin "M1") (pinfunction "IN2_M1") (pintype "input"))
      (node (ref "E14") (pin "M1") (pinfunction "IN3_M1") (pintype "input"))
      (node (ref "F19") (pin "E1") (pinfunction "OUT_E1") (pintype "output"))
    )
    (net (code "1597") (name "SPECIAL_CYCLE_") (class "Default")
      (node (ref "E24") (pin "K1") (pinfunction "OUT_K1") (pintype "output"))
      (node (ref "F23") (pin "M1") (pinfunction "IN1_M1") (pintype "input"))
      (node (ref "F23") (pin "M2") (pinfunction "IN3_M2") (pintype "input"))
    )
    (net (code "1598") (name "SR00") (class "Default")
      (node (ref "A40") (pin "L2") (pinfunction "P$2_L2") (pintype "bidirectional"))
      (node (ref "EF34") (pin "BE1") (pinfunction "BE1_BE1") (pintype "input"))
    )
    (net (code "1599") (name "SR01") (class "Default")
      (node (ref "A40") (pin "M2") (pinfunction "P$2_M2") (pintype "bidirectional"))
      (node (ref "EF34") (pin "BD2") (pinfunction "BD2_BD2") (pintype "input"))
    )
    (net (code "1600") (name "SR02") (class "Default")
      (node (ref "A40") (pin "R2") (pinfunction "P$2_R2") (pintype "bidirectional"))
      (node (ref "EF35") (pin "BE1") (pinfunction "BE1_BE1") (pintype "input"))
    )
    (net (code "1601") (name "SR03") (class "Default")
      (node (ref "A40") (pin "S2") (pinfunction "P$2_S2") (pintype "bidirectional"))
      (node (ref "EF35") (pin "BD2") (pinfunction "BD2_BD2") (pintype "input"))
    )
    (net (code "1602") (name "SR04") (class "Default")
      (node (ref "A40") (pin "T2") (pinfunction "P$2_T2") (pintype "bidirectional"))
      (node (ref "EF36") (pin "BE1") (pinfunction "BE1_BE1") (pintype "input"))
    )
    (net (code "1603") (name "SR05") (class "Default")
      (node (ref "A40") (pin "U2") (pinfunction "P$2_U2") (pintype "bidirectional"))
      (node (ref "EF36") (pin "BD2") (pinfunction "BD2_BD2") (pintype "input"))
    )
    (net (code "1604") (name "SR06") (class "Default")
      (node (ref "A40") (pin "V2") (pinfunction "P$2_V2") (pintype "bidirectional"))
      (node (ref "EF37") (pin "BE1") (pinfunction "BE1_BE1") (pintype "input"))
    )
    (net (code "1605") (name "SR07") (class "Default")
      (node (ref "B40") (pin "D2") (pinfunction "P$2_D2") (pintype "bidirectional"))
      (node (ref "EF37") (pin "BD2") (pinfunction "BD2_BD2") (pintype "input"))
    )
    (net (code "1606") (name "SR08") (class "Default")
      (node (ref "B40") (pin "E2") (pinfunction "P$2_E2") (pintype "bidirectional"))
      (node (ref "EF38") (pin "BE1") (pinfunction "BE1_BE1") (pintype "input"))
    )
    (net (code "1607") (name "SR09") (class "Default")
      (node (ref "B40") (pin "F2") (pinfunction "P$2_F2") (pintype "bidirectional"))
      (node (ref "EF38") (pin "BD2") (pinfunction "BD2_BD2") (pintype "input"))
    )
    (net (code "1608") (name "SR10") (class "Default")
      (node (ref "B40") (pin "H2") (pinfunction "P$2_H2") (pintype "bidirectional"))
      (node (ref "EF39") (pin "BE1") (pinfunction "BE1_BE1") (pintype "input"))
    )
    (net (code "1609") (name "SR11") (class "Default")
      (node (ref "B40") (pin "J2") (pinfunction "P$2_J2") (pintype "bidirectional"))
      (node (ref "EF39") (pin "BD2") (pinfunction "BD2_BD2") (pintype "input"))
    )
    (net (code "1610") (name "SR_ENABLE") (class "Default")
      (node (ref "A12") (pin "D1") (pinfunction "IN1_D1") (pintype "input"))
      (node (ref "A12") (pin "H2") (pinfunction "IN1_H2") (pintype "input"))
      (node (ref "A12") (pin "P1") (pinfunction "IN1_P1") (pintype "input"))
      (node (ref "A18") (pin "D1") (pinfunction "IN1_D1") (pintype "input"))
      (node (ref "A18") (pin "H2") (pinfunction "IN1_H2") (pintype "input"))
      (node (ref "A18") (pin "P1") (pinfunction "IN1_P1") (pintype "input"))
      (node (ref "EF34") (pin "BC1") (pinfunction "BC1_BC1") (pintype "input"))
      (node (ref "EF35") (pin "BC1") (pinfunction "BC1_BC1") (pintype "input"))
      (node (ref "EF36") (pin "BC1") (pinfunction "BC1_BC1") (pintype "input"))
      (node (ref "EF37") (pin "BC1") (pinfunction "BC1_BC1") (pintype "input"))
      (node (ref "EF38") (pin "BC1") (pinfunction "BC1_BC1") (pintype "input"))
      (node (ref "EF39") (pin "BC1") (pinfunction "BC1_BC1") (pintype "input"))
      (node (ref "F30") (pin "S1") (pinfunction "OUT_S1") (pintype "open_collector"))
    )
    (net (code "1611") (name "STOP_COMPLETE") (class "Default")
      (node (ref "HJ26") (pin "BN2") (pinfunction "BN2_BN2") (pintype "input"))
      (node (ref "HJ27") (pin "BR2") (pinfunction "BR_BR2") (pintype "output"))
    )
    (net (code "1612") (name "STOP_OK") (class "Default")
      (node (ref "A04") (pin "P2") (pinfunction "P2_P2") (pintype "output"))
      (node (ref "AB02") (pin "AH2") (pinfunction "AH2_AH2") (pintype "input"))
      (node (ref "E13") (pin "K1") (pinfunction "IN4A_K1") (pintype "input"))
    )
    (net (code "1613") (name "STORE_") (class "Default")
      (node (ref "D07") (pin "D2") (pinfunction "IN1_D2") (pintype "input"))
      (node (ref "D09") (pin "P1") (pinfunction "IN1_P1") (pintype "input"))
      (node (ref "D10") (pin "S1") (pinfunction "OUT_S1") (pintype "output"))
      (node (ref "F31") (pin "C1") (pinfunction "IN3_C1") (pintype "input"))
    )
    (net (code "1614") (name "STROBE_") (class "Default")
      (node (ref "B10") (pin "E2") (pinfunction "E2_E2") (pintype "open_collector"))
      (node (ref "B23") (pin "T2") (pinfunction "T_T2") (pintype "open_collector"))
      (node (ref "B24") (pin "T2") (pinfunction "T_T2") (pintype "open_collector"))
      (node (ref "E15") (pin "H2") (pinfunction "IN1_H2") (pintype "input"))
      (node (ref "E18") (pin "A1") (pinfunction "R_A1") (pintype "input"))
      (node (ref "E19") (pin "D1") (pinfunction "S_D1") (pintype "input"))
      (node (ref "EF10") (pin "BE2") (pinfunction "P$1_BE2") (pintype "passive"))
      (node (ref "F20") (pin "D1") (pinfunction "IN1_D1") (pintype "input"))
      (node (ref "H05") (pin "P2") (pinfunction "P$2_P2") (pintype "bidirectional"))
    )
    (net (code "1615") (name "STROBE_FIELD0") (class "Default")
      (node (ref "A30") (pin "D1") (pinfunction "D1_D1") (pintype "input"))
      (node (ref "A31") (pin "D1") (pinfunction "D1_D1") (pintype "input"))
      (node (ref "A32") (pin "D1") (pinfunction "D1_D1") (pintype "input"))
      (node (ref "A33") (pin "D1") (pinfunction "D1_D1") (pintype "input"))
      (node (ref "B23") (pin "S2") (pinfunction "S_S2") (pintype "output"))
      (node (ref "B31") (pin "D1") (pinfunction "D1_D1") (pintype "input"))
      (node (ref "B32") (pin "D1") (pinfunction "D1_D1") (pintype "input"))
      (node (ref "B33") (pin "D1") (pinfunction "D1_D1") (pintype "input"))
    )
    (net (code "1616") (name "STROBE_FIELD1") (class "Default")
      (node (ref "A30") (pin "R1") (pinfunction "R1_R1") (pintype "input"))
      (node (ref "A31") (pin "R1") (pinfunction "R1_R1") (pintype "input"))
      (node (ref "A32") (pin "R1") (pinfunction "R1_R1") (pintype "input"))
      (node (ref "A33") (pin "R1") (pinfunction "R1_R1") (pintype "input"))
      (node (ref "B24") (pin "S2") (pinfunction "S_S2") (pintype "output"))
      (node (ref "B31") (pin "R1") (pinfunction "R1_R1") (pintype "input"))
      (node (ref "B32") (pin "R1") (pinfunction "R1_R1") (pintype "input"))
      (node (ref "B33") (pin "R1") (pinfunction "R1_R1") (pintype "input"))
    )
    (net (code "1617") (name "SYNC_PUN") (class "Default")
      (node (ref "C01") (pin "F2") (pinfunction "P$2_F2") (pintype "bidirectional"))
      (node (ref "HJ28") (pin "AV2") (pinfunction "AV2_AV2") (pintype "input"))
    )
    (net (code "1618") (name "S_") (class "Default")
      (node (ref "D09") (pin "R2") (pinfunction "IN3_R2") (pintype "input"))
      (node (ref "D11") (pin "E1") (pinfunction "1_E1") (pintype "output"))
      (node (ref "E09") (pin "A1") (pinfunction "IN1_A1") (pintype "input"))
      (node (ref "E09") (pin "D2") (pinfunction "IN1_D2") (pintype "input"))
    )
    (net (code "1619") (name "S_FEED_HOLE") (class "Default")
      (node (ref "D01") (pin "N2") (pinfunction "P$2_N2") (pintype "bidirectional"))
      (node (ref "HJ26") (pin "BM2") (pinfunction "BM2_BM2") (pintype "input"))
    )
    (net (code "1620") (name "S_SET_") (class "Default")
      (node (ref "C11") (pin "C1") (pinfunction "IN3_C1") (pintype "input"))
      (node (ref "D10") (pin "E1") (pinfunction "OUT_E1") (pintype "output"))
      (node (ref "D11") (pin "C1") (pinfunction "D_C1") (pintype "input"))
    )
    (net (code "1621") (name "S_UF") (class "Default")
      (node (ref "A05") (pin "J2") (pinfunction "IN2_J2") (pintype "input"))
      (node (ref "B05") (pin "S1") (pinfunction "1_S1") (pintype "output"))
      (node (ref "B06") (pin "P1") (pinfunction "IN1_P1") (pintype "input"))
    )
    (net (code "1622") (name "TAD") (class "Default")
      (node (ref "E22") (pin "F1") (pinfunction "OUT_F1") (pintype "output"))
      (node (ref "F28") (pin "A1") (pinfunction "IN1_A1") (pintype "input"))
    )
    (net (code "1623") (name "TAD_") (class "Default")
      (node (ref "D40") (pin "T2") (pinfunction "P$2_T2") (pintype "bidirectional"))
      (node (ref "E21") (pin "D1") (pinfunction "OUT_D1") (pintype "output"))
      (node (ref "E22") (pin "D1") (pinfunction "IN1_D1") (pintype "input"))
      (node (ref "F26") (pin "U2") (pinfunction "IN2_U2") (pintype "input"))
    )
    (net (code "1624") (name "TELEPRINTER_FLAG_") (class "Default")
      (node (ref "EF02") (pin "BK2") (pinfunction "BK2_BK2") (pintype "output"))
      (node (ref "F19") (pin "R1") (pinfunction "IN4_R1") (pintype "input"))
    )
    (net (code "1625") (name "TP1") (class "Default")
      (node (ref "D07") (pin "U2") (pinfunction "IN2_U2") (pintype "input"))
      (node (ref "E09") (pin "B1") (pinfunction "IN2_B1") (pintype "input"))
      (node (ref "E15") (pin "K2") (pinfunction "OUT_K2") (pintype "output"))
      (node (ref "E20") (pin "L2") (pinfunction "C_L2") (pintype "input"))
      (node (ref "E26") (pin "E1") (pinfunction "IN2A_E1") (pintype "input"))
      (node (ref "E26") (pin "S1") (pinfunction "IN1A_S1") (pintype "input"))
    )
    (net (code "1626") (name "TP2") (class "Default")
      (node (ref "E15") (pin "L1") (pinfunction "IN1_L1") (pintype "input"))
      (node (ref "E17") (pin "F1") (pinfunction "OUT_F1") (pintype "output"))
      (node (ref "E19") (pin "B1") (pinfunction "C_B1") (pintype "input"))
      (node (ref "E22") (pin "L1") (pinfunction "IN1_L1") (pintype "input"))
      (node (ref "E33") (pin "D2") (pinfunction "C_D2") (pintype "input"))
      (node (ref "F25") (pin "P2") (pinfunction "IN1_P2") (pintype "input"))
      (node (ref "F32") (pin "J1") (pinfunction "IN2_J1") (pintype "input"))
    )
    (net (code "1627") (name "TP2E_") (class "Default")
      (node (ref "B04") (pin "K1") (pinfunction "IN1_K1") (pintype "input"))
      (node (ref "B04") (pin "L1") (pinfunction "IN2_L1") (pintype "input"))
      (node (ref "E25") (pin "R1") (pinfunction "IN2_R1") (pintype "input"))
      (node (ref "F25") (pin "S2") (pinfunction "OUT_S2") (pintype "output"))
    )
    (net (code "1628") (name "TP3") (class "Default")
      (node (ref "A13") (pin "D2") (pinfunction "IN1_D2") (pintype "input"))
      (node (ref "A14") (pin "P2") (pinfunction "IN1_P2") (pintype "input"))
      (node (ref "A19") (pin "L1") (pinfunction "IN1_L1") (pintype "input"))
      (node (ref "A20") (pin "B1") (pinfunction "IN2_B1") (pintype "input"))
      (node (ref "B04") (pin "K2") (pinfunction "IN2_K2") (pintype "input"))
      (node (ref "B05") (pin "L2") (pinfunction "C_L2") (pintype "input"))
      (node (ref "B09") (pin "T2") (pinfunction "IN1_T2") (pintype "input"))
      (node (ref "B10") (pin "V2") (pinfunction "V2_V2") (pintype "input"))
      (node (ref "C08") (pin "J2") (pinfunction "IN2_J2") (pintype "input"))
      (node (ref "D09") (pin "U2") (pinfunction "IN2_U2") (pintype "input"))
      (node (ref "D12") (pin "P2") (pinfunction "IN1_P2") (pintype "input"))
      (node (ref "D14") (pin "P2") (pinfunction "IN1_P2") (pintype "input"))
      (node (ref "D14") (pin "T2") (pinfunction "IN1_T2") (pintype "input"))
      (node (ref "D17") (pin "U2") (pinfunction "IN2_U2") (pintype "input"))
      (node (ref "D18") (pin "M1") (pinfunction "IN3_M1") (pintype "input"))
      (node (ref "E14") (pin "K1") (pinfunction "IN1_K1") (pintype "input"))
      (node (ref "E15") (pin "P1") (pinfunction "IN1_P1") (pintype "input"))
      (node (ref "E17") (pin "J1") (pinfunction "OUT_J1") (pintype "output"))
      (node (ref "E18") (pin "L2") (pinfunction "C_L2") (pintype "input"))
      (node (ref "E19") (pin "D2") (pinfunction "C_D2") (pintype "input"))
      (node (ref "E25") (pin "T2") (pinfunction "IN1_T2") (pintype "input"))
      (node (ref "E26") (pin "A1") (pinfunction "IN1A_A1") (pintype "input"))
      (node (ref "E26") (pin "E2") (pinfunction "IN1B_E2") (pintype "input"))
      (node (ref "E26") (pin "H1") (pinfunction "IN3A_H1") (pintype "input"))
      (node (ref "E26") (pin "M1") (pinfunction "IN5A_M1") (pintype "input"))
      (node (ref "E26") (pin "P2") (pinfunction "IN4B_P2") (pintype "input"))
      (node (ref "F26") (pin "N2") (pinfunction "IN1_N2") (pintype "input"))
    )
    (net (code "1629") (name "TP4") (class "Default")
      (node (ref "D11") (pin "B1") (pinfunction "C_B1") (pintype "input"))
      (node (ref "D11") (pin "D2") (pinfunction "C_D2") (pintype "input"))
      (node (ref "E15") (pin "F2") (pinfunction "OUT_F2") (pintype "output"))
      (node (ref "E18") (pin "B1") (pinfunction "C_B1") (pintype "input"))
      (node (ref "E19") (pin "H1") (pinfunction "C_H1") (pintype "input"))
      (node (ref "E23") (pin "B1") (pinfunction "C_B1") (pintype "input"))
      (node (ref "E23") (pin "D2") (pinfunction "C_D2") (pintype "input"))
      (node (ref "E23") (pin "H1") (pinfunction "C_H1") (pintype "input"))
      (node (ref "E23") (pin "L2") (pinfunction "C_L2") (pintype "input"))
      (node (ref "E23") (pin "N1") (pinfunction "C_N1") (pintype "input"))
      (node (ref "E23") (pin "S2") (pinfunction "C_S2") (pintype "input"))
      (node (ref "E24") (pin "H2") (pinfunction "IN1_H2") (pintype "input"))
      (node (ref "E33") (pin "B1") (pinfunction "C_B1") (pintype "input"))
      (node (ref "F32") (pin "D2") (pinfunction "IN1_D2") (pintype "input"))
    )
    (net (code "1630") (name "TS1") (class "Default")
      (node (ref "C07") (pin "V2") (pinfunction "IN1_V2") (pintype "input"))
      (node (ref "E18") (pin "E1") (pinfunction "1_E1") (pintype "output"))
      (node (ref "E27") (pin "E1") (pinfunction "IN2A_E1") (pintype "input"))
      (node (ref "E30") (pin "E1") (pinfunction "IN2A_E1") (pintype "input"))
    )
    (net (code "1631") (name "TS1_") (class "Default")
      (node (ref "E18") (pin "F1") (pinfunction "0_F1") (pintype "output"))
      (node (ref "H12") (pin "N2") (pinfunction "IN2_N2") (pintype "input"))
    )
    (net (code "1632") (name "TS2") (class "Default")
      (node (ref "C11") (pin "H1") (pinfunction "IN3_H1") (pintype "input"))
      (node (ref "C11") (pin "J2") (pinfunction "IN1_J2") (pintype "input"))
      (node (ref "D09") (pin "B1") (pinfunction "IN2_B1") (pintype "input"))
      (node (ref "D10") (pin "F1") (pinfunction "IN1_F1") (pintype "input"))
      (node (ref "E19") (pin "E1") (pinfunction "1_E1") (pintype "output"))
      (node (ref "E27") (pin "A1") (pinfunction "IN1A_A1") (pintype "input"))
      (node (ref "E27") (pin "P2") (pinfunction "IN4B_P2") (pintype "input"))
      (node (ref "E28") (pin "D2") (pinfunction "IN1A_D2") (pintype "input"))
      (node (ref "E29") (pin "E1") (pinfunction "IN2A_E1") (pintype "input"))
      (node (ref "E30") (pin "P2") (pinfunction "IN4B_P2") (pintype "input"))
      (node (ref "F28") (pin "E1") (pinfunction "IN1_E1") (pintype "input"))
      (node (ref "F28") (pin "K1") (pinfunction "IN1_K1") (pintype "input"))
    )
    (net (code "1633") (name "TS3") (class "Default")
      (node (ref "C11") (pin "K1") (pinfunction "IN1_K1") (pintype "input"))
      (node (ref "C11") (pin "N2") (pinfunction "IN1_N2") (pintype "input"))
      (node (ref "C12") (pin "E2") (pinfunction "IN2_E2") (pintype "input"))
      (node (ref "D09") (pin "D2") (pinfunction "IN1_D2") (pintype "input"))
      (node (ref "D10") (pin "P1") (pinfunction "IN3_P1") (pintype "input"))
      (node (ref "D10") (pin "T2") (pinfunction "IN3_T2") (pintype "input"))
      (node (ref "E19") (pin "H2") (pinfunction "1_H2") (pintype "output"))
      (node (ref "E27") (pin "M1") (pinfunction "IN5A_M1") (pintype "input"))
      (node (ref "E29") (pin "A1") (pinfunction "IN1A_A1") (pintype "input"))
      (node (ref "E30") (pin "M1") (pinfunction "IN5A_M1") (pintype "input"))
      (node (ref "F26") (pin "R1") (pinfunction "IN2_R1") (pintype "input"))
      (node (ref "F27") (pin "A1") (pinfunction "IN1_A1") (pintype "input"))
      (node (ref "F27") (pin "H1") (pinfunction "IN2_H1") (pintype "input"))
      (node (ref "F27") (pin "S2") (pinfunction "IN2_S2") (pintype "input"))
      (node (ref "F28") (pin "B1") (pinfunction "IN2_B1") (pintype "input"))
    )
    (net (code "1634") (name "TS3_") (class "Default")
      (node (ref "E19") (pin "J2") (pinfunction "0_J2") (pintype "output"))
      (node (ref "H12") (pin "H2") (pinfunction "IN2_H2") (pintype "input"))
    )
    (net (code "1635") (name "TS4") (class "Default")
      (node (ref "C12") (pin "L2") (pinfunction "IN2_L2") (pintype "input"))
      (node (ref "E19") (pin "L1") (pinfunction "1_L1") (pintype "output"))
      (node (ref "E29") (pin "K1") (pinfunction "IN4A_K1") (pintype "input"))
      (node (ref "E29") (pin "M1") (pinfunction "IN5A_M1") (pintype "input"))
      (node (ref "E30") (pin "H1") (pinfunction "IN3A_H1") (pintype "input"))
      (node (ref "F27") (pin "D2") (pinfunction "IN1_D2") (pintype "input"))
      (node (ref "F29") (pin "L1") (pinfunction "IN1_L1") (pintype "input"))
      (node (ref "F32") (pin "L1") (pinfunction "IN1_L1") (pintype "input"))
    )
    (net (code "1636") (name "TS4_") (class "Default")
      (node (ref "A19") (pin "J1") (pinfunction "IN2_J1") (pintype "input"))
      (node (ref "E19") (pin "M1") (pinfunction "0_M1") (pintype "output"))
    )
    (net (code "1637") (name "TT0_") (class "Default")
      (node (ref "EF01") (pin "AK2") (pinfunction "AK2_AK2") (pintype "output"))
      (node (ref "J13") (pin "P1") (pinfunction "IN3_P1") (pintype "input"))
    )
    (net (code "1638") (name "TT1_") (class "Default")
      (node (ref "EF01") (pin "AR2") (pinfunction "AR2_AR2") (pintype "output"))
      (node (ref "J13") (pin "T2") (pinfunction "IN3_T2") (pintype "input"))
    )
    (net (code "1639") (name "TT2_") (class "Default")
      (node (ref "EF01") (pin "AS2") (pinfunction "AS2_AS2") (pintype "output"))
      (node (ref "J14") (pin "C1") (pinfunction "IN3_C1") (pintype "input"))
    )
    (net (code "1640") (name "TT3_") (class "Default")
      (node (ref "EF01") (pin "AL1") (pinfunction "AL1_AL1") (pintype "output"))
      (node (ref "J14") (pin "F2") (pinfunction "IN3_F2") (pintype "input"))
    )
    (net (code "1641") (name "TT4_") (class "Default")
      (node (ref "EF01") (pin "AM1") (pinfunction "AM1_AM1") (pintype "output"))
      (node (ref "J14") (pin "J1") (pinfunction "IN3_J1") (pintype "input"))
    )
    (net (code "1642") (name "TT5_") (class "Default")
      (node (ref "EF01") (pin "AP2") (pinfunction "AP2_AP2") (pintype "output"))
      (node (ref "J14") (pin "M2") (pinfunction "IN3_M2") (pintype "input"))
    )
    (net (code "1643") (name "TT6_") (class "Default")
      (node (ref "EF01") (pin "AT2") (pinfunction "AT2_AT2") (pintype "output"))
      (node (ref "J14") (pin "P1") (pinfunction "IN3_P1") (pintype "input"))
    )
    (net (code "1644") (name "TT7_") (class "Default")
      (node (ref "EF01") (pin "AN2") (pinfunction "AN2_AN2") (pintype "output"))
      (node (ref "J14") (pin "T2") (pinfunction "IN3_T2") (pintype "input"))
    )
    (net (code "1645") (name "TTI2") (class "Default")
      (node (ref "EF01") (pin "AJ2") (pinfunction "AJ2_AJ2") (pintype "output"))
      (node (ref "EF01") (pin "AK1") (pinfunction "AK1_AK1") (pintype "input"))
    )
    (net (code "1646") (name "TTI_CLOCK") (class "Default")
      (node (ref "EF01") (pin "AN1") (pinfunction "AN1_AN1") (pintype "input"))
      (node (ref "F03") (pin "R2") (pinfunction "R2_R2") (pintype "output"))
    )
    (net (code "1647") (name "TTI_DATA") (class "Default")
      (node (ref "EF01") (pin "AM2") (pinfunction "AM2_AM2") (pintype "output"))
      (node (ref "EF01") (pin "AR1") (pinfunction "AR1_AR1") (pintype "input"))
    )
    (net (code "1648") (name "TTI_SKIP_") (class "Default")
      (node (ref "EF01") (pin "BH2") (pinfunction "BH2_BH2") (pintype "output"))
      (node (ref "F19") (pin "K2") (pinfunction "IN1_K2") (pintype "input"))
    )
    (net (code "1649") (name "TTO_CLOCK_") (class "Default")
      (node (ref "EF02") (pin "BP2") (pinfunction "BP2_BP2") (pintype "input"))
      (node (ref "F03") (pin "K2") (pinfunction "K2_K2") (pintype "output"))
    )
    (net (code "1650") (name "TTO_SKIP_") (class "Default")
      (node (ref "EF02") (pin "BJ2") (pinfunction "BJ2_BJ2") (pintype "output"))
      (node (ref "F19") (pin "L2") (pinfunction "IN2_L2") (pintype "input"))
    )
    (net (code "1651") (name "TT_AC_CLR_") (class "Default")
      (node (ref "EF01") (pin "BE2") (pinfunction "BE2_BE2") (pintype "output"))
      (node (ref "J15") (pin "J1") (pinfunction "IN3_J1") (pintype "input"))
    )
    (net (code "1652") (name "TT_AC_LOAD_") (class "Default")
      (node (ref "D09") (pin "V1") (pinfunction "OUT_V1") (pintype "output"))
      (node (ref "E32") (pin "M2") (pinfunction "IN3_M2") (pintype "input"))
    )
    (net (code "1653") (name "TT_CARRY_INSERT") (class "Default")
      (node (ref "C09") (pin "P1") (pinfunction "IN1_P1") (pintype "input"))
      (node (ref "D09") (pin "N1") (pinfunction "OUT_N1") (pintype "output"))
      (node (ref "E26") (pin "J1") (pinfunction "IN3B_J1") (pintype "input"))
    )
    (net (code "1654") (name "TT_CARRY_INSERT_") (class "Default")
      (node (ref "C09") (pin "S1") (pinfunction "OUT_S1") (pintype "output"))
      (node (ref "E31") (pin "P1") (pinfunction "IN3_P1") (pintype "input"))
      (node (ref "F09") (pin "N2") (pinfunction "IN8_N2") (pintype "input"))
      (node (ref "F27") (pin "N2") (pinfunction "IN4_N2") (pintype "input"))
    )
    (net (code "1655") (name "TT_CARRY_INSERT_C_") (class "Default")
      (node (ref "D09") (pin "H2") (pinfunction "OUT_H2") (pintype "output"))
      (node (ref "D09") (pin "K1") (pinfunction "IN1_K1") (pintype "input"))
    )
    (net (code "1656") (name "TT_CARRY_INSERT_S") (class "Default")
      (node (ref "C09") (pin "S2") (pinfunction "OUT_S2") (pintype "output"))
      (node (ref "EF39") (pin "BE2") (pinfunction "BE2_BE2") (pintype "input"))
    )
    (net (code "1657") (name "TT_CARRY_INSERT_S_") (class "Default")
      (node (ref "C09") (pin "P2") (pinfunction "IN1_P2") (pintype "input"))
      (node (ref "C11") (pin "S2") (pinfunction "OUT_S2") (pintype "output"))
      (node (ref "D09") (pin "L1") (pinfunction "IN2_L1") (pintype "input"))
    )
    (net (code "1658") (name "TT_CYCLE_") (class "Default")
      (node (ref "C10") (pin "N1") (pinfunction "OUT_N1") (pintype "output"))
      (node (ref "F28") (pin "V2") (pinfunction "IN3_V2") (pintype "input"))
    )
    (net (code "1659") (name "TT_DATA") (class "Default")
      (node (ref "C10") (pin "N2") (pinfunction "OUT_N2") (pintype "output"))
      (node (ref "F33") (pin "H2") (pinfunction "IN1D_H2") (pintype "input"))
    )
    (net (code "1660") (name "TT_INCREMENT_") (class "Default")
      (node (ref "D10") (pin "L1") (pinfunction "OUT_L1") (pintype "output"))
      (node (ref "F25") (pin "E2") (pinfunction "IN2_E2") (pintype "input"))
      (node (ref "F25") (pin "J1") (pinfunction "IN2_J1") (pintype "input"))
      (node (ref "F25") (pin "J2") (pinfunction "IN2_J2") (pintype "input"))
    )
    (net (code "1661") (name "TT_INST") (class "Default")
      (node (ref "C10") (pin "F2") (pinfunction "OUT_F2") (pintype "output"))
      (node (ref "C11") (pin "M1") (pinfunction "IN3_M1") (pintype "input"))
      (node (ref "D10") (pin "A1") (pinfunction "IN1_A1") (pintype "input"))
    )
    (net (code "1662") (name "TT_INST_") (class "Default")
      (node (ref "C10") (pin "E2") (pinfunction "IN2_E2") (pintype "input"))
      (node (ref "C10") (pin "M1") (pinfunction "IN2_M1") (pintype "input"))
      (node (ref "D09") (pin "P2") (pinfunction "IN2_P2") (pintype "input"))
      (node (ref "D10") (pin "P2") (pinfunction "OUT_P2") (pintype "output"))
      (node (ref "F19") (pin "C1") (pinfunction "IN3_C1") (pintype "input"))
      (node (ref "F28") (pin "S1") (pinfunction "IN3_S1") (pintype "input"))
      (node (ref "F33") (pin "F2") (pinfunction "IN1C_F2") (pintype "input"))
      (node (ref "H19") (pin "N2") (pinfunction "IN2_N2") (pintype "input"))
    )
    (net (code "1663") (name "TT_INT_") (class "Default")
      (node (ref "E12") (pin "V2") (pinfunction "OUT_V2") (pintype "output"))
      (node (ref "J15") (pin "F2") (pinfunction "IN3_F2") (pintype "input"))
    )
    (net (code "1664") (name "TT_IO_ENABLE_") (class "Default")
      (node (ref "C11") (pin "F2") (pinfunction "IN3_F2") (pintype "input"))
      (node (ref "C11") (pin "N1") (pinfunction "OUT_N1") (pintype "output"))
      (node (ref "D09") (pin "S1") (pinfunction "IN3_S1") (pintype "input"))
      (node (ref "F30") (pin "H2") (pinfunction "IN4_H2") (pintype "input"))
    )
    (net (code "1665") (name "TT_LINE_SHIFT_") (class "Default")
      (node (ref "C09") (pin "D2") (pinfunction "IN1_D2") (pintype "input"))
      (node (ref "C11") (pin "M2") (pinfunction "OUT_M2") (pintype "output"))
      (node (ref "EF34") (pin "AB2") (pinfunction "AB2_AB2") (pintype "input"))
      (node (ref "EF35") (pin "AB2") (pinfunction "AB2_AB2") (pintype "input"))
      (node (ref "EF36") (pin "AB2") (pinfunction "AB2_AB2") (pintype "input"))
      (node (ref "EF37") (pin "AB2") (pinfunction "AB2_AB2") (pintype "input"))
      (node (ref "EF38") (pin "AB2") (pinfunction "AB2_AB2") (pintype "input"))
      (node (ref "EF39") (pin "AB2") (pinfunction "AB2_AB2") (pintype "input"))
    )
    (net (code "1666") (name "TT_L_DISABLE") (class "Default")
      (node (ref "C10") (pin "L1") (pinfunction "IN1_L1") (pintype "input"))
      (node (ref "D09") (pin "S2") (pinfunction "OUT_S2") (pintype "output"))
      (node (ref "E28") (pin "J1") (pinfunction "IN3B_J1") (pintype "input"))
    )
    (net (code "1667") (name "TT_RIGHT_SHIFT_ENABLE") (class "Default")
      (node (ref "C10") (pin "E1") (pinfunction "IN2_E1") (pintype "input"))
      (node (ref "C11") (pin "H2") (pinfunction "OUT_H2") (pintype "output"))
    )
    (net (code "1668") (name "TT_RIGHT_SHIFT_ENABLE_") (class "Default")
      (node (ref "C09") (pin "E2") (pinfunction "IN2_E2") (pintype "input"))
      (node (ref "C10") (pin "F1") (pinfunction "OUT_F1") (pintype "output"))
      (node (ref "E31") (pin "H1") (pinfunction "IN2_H1") (pintype "input"))
    )
    (net (code "1669") (name "TT_SET_") (class "Default")
      (node (ref "C10") (pin "C1") (pinfunction "OUT_C1") (pintype "output"))
      (node (ref "E25") (pin "E1") (pinfunction "IN1_E1") (pintype "input"))
      (node (ref "F28") (pin "L2") (pinfunction "IN3_L2") (pintype "input"))
    )
    (net (code "1670") (name "TT_SHIFT_ENABLE") (class "Default")
      (node (ref "C09") (pin "F2") (pinfunction "OUT_F2") (pintype "output"))
      (node (ref "C09") (pin "H1") (pinfunction "IN1_H1") (pintype "input"))
      (node (ref "F33") (pin "E2") (pinfunction "IN1B_E2") (pintype "input"))
    )
    (net (code "1671") (name "TT_SHIFT_ENABLE_") (class "Default")
      (node (ref "C09") (pin "K1") (pinfunction "OUT_K1") (pintype "output"))
      (node (ref "F24") (pin "B1") (pinfunction "IN2_B1") (pintype "input"))
    )
    (net (code "1672") (name "TT_SKIP_") (class "Default")
      (node (ref "E12") (pin "S1") (pinfunction "OUT_S1") (pintype "output"))
      (node (ref "J15") (pin "C1") (pinfunction "IN3_C1") (pintype "input"))
    )
    (net (code "1673") (name "TX_DATA") (class "Default")
      (node (ref "EF02") (pin "AV2") (pinfunction "AV2_AV2") (pintype "output"))
      (node (ref "J12") (pin "H2") (pinfunction "P$2_H2") (pintype "bidirectional"))
    )
    (net (code "1674") (name "UB") (class "Default")
      (node (ref "B05") (pin "E1") (pinfunction "1_E1") (pintype "output"))
      (node (ref "B06") (pin "P2") (pinfunction "IN1_P2") (pintype "input"))
    )
    (net (code "1675") (name "UF") (class "Default")
      (node (ref "A05") (pin "M1") (pinfunction "IN2_M1") (pintype "input"))
      (node (ref "B05") (pin "H2") (pinfunction "1_H2") (pintype "output"))
      (node (ref "B05") (pin "P1") (pinfunction "D_P1") (pintype "input"))
    )
    (net (code "1676") (name "UF_") (class "Default")
      (node (ref "A06") (pin "J1") (pinfunction "IN2_J1") (pintype "input"))
      (node (ref "B05") (pin "J2") (pinfunction "0_J2") (pintype "output"))
      (node (ref "E13") (pin "D1") (pinfunction "IN1D_D1") (pintype "input"))
      (node (ref "F11") (pin "D1") (pinfunction "IN4_D1") (pintype "input"))
    )
    (net (code "1677") (name "UINT") (class "Default")
      (node (ref "A05") (pin "M2") (pinfunction "IN2_M2") (pintype "input"))
      (node (ref "B04") (pin "J2") (pinfunction "IN1_J2") (pintype "input"))
      (node (ref "B05") (pin "P2") (pinfunction "1_P2") (pintype "output"))
    )
    (net (code "1678") (name "UINT_") (class "Default")
      (node (ref "A05") (pin "S2") (pinfunction "OUT_S2") (pintype "output"))
      (node (ref "F19") (pin "N1") (pinfunction "IN2_N1") (pintype "input"))
    )
    (net (code "1679") (name "USF_") (class "Default")
      (node (ref "B04") (pin "T2") (pinfunction "IN1_T2") (pintype "input"))
      (node (ref "B05") (pin "V1") (pinfunction "0_V1") (pintype "output"))
    )
    (net (code "1680") (name "VCC") (class "Default")
      (node (ref "A40") (pin "A2") (pinfunction "P$2_A2") (pintype "bidirectional"))
      (node (ref "B40") (pin "A2") (pinfunction "P$2_A2") (pintype "bidirectional"))
      (node (ref "C40") (pin "A2") (pinfunction "P$2_A2") (pintype "bidirectional"))
      (node (ref "D03") (pin "A2") (pinfunction "P$2_A2") (pintype "bidirectional"))
      (node (ref "E40") (pin "A2") (pinfunction "P$2_A2") (pintype "bidirectional"))
      (node (ref "F40") (pin "A2") (pinfunction "P$2_A2") (pintype "bidirectional"))
    )
    (net (code "1681") (name "WC_OVERFLOW_") (class "Default")
      (node (ref "E33") (pin "H2") (pinfunction "1_H2") (pintype "output"))
      (node (ref "H19") (pin "U2") (pinfunction "IN2_U2") (pintype "input"))
    )
    (net (code "1682") (name "WC_SET") (class "Default")
      (node (ref "E23") (pin "M2") (pinfunction "D_M2") (pintype "input"))
      (node (ref "F22") (pin "N2") (pinfunction "OUT_N2") (pintype "output"))
    )
    (net (code "1683") (name "WC_SET_") (class "Default")
      (node (ref "A19") (pin "A1") (pinfunction "IN1_A1") (pintype "input"))
      (node (ref "F22") (pin "L2") (pinfunction "IN1_L2") (pintype "input"))
      (node (ref "F22") (pin "R1") (pinfunction "IN2_R1") (pintype "input"))
      (node (ref "F22") (pin "V2") (pinfunction "OUT_V2") (pintype "output"))
    )
    (net (code "1684") (name "WORD_COUNT") (class "Default")
      (node (ref "E23") (pin "P1") (pinfunction "D_P1") (pintype "input"))
      (node (ref "E23") (pin "P2") (pinfunction "1_P2") (pintype "output"))
      (node (ref "E27") (pin "D2") (pinfunction "IN1A_D2") (pintype "input"))
      (node (ref "E30") (pin "J1") (pinfunction "IN3B_J1") (pintype "input"))
    )
    (net (code "1685") (name "WORD_COUNT_") (class "Default")
      (node (ref "A19") (pin "B1") (pinfunction "IN2_B1") (pintype "input"))
      (node (ref "D40") (pin "A1") (pinfunction "P$2_A1") (pintype "bidirectional"))
      (node (ref "E12") (pin "P2") (pinfunction "IN1_P2") (pintype "input"))
      (node (ref "E23") (pin "R2") (pinfunction "0_R2") (pintype "output"))
      (node (ref "E25") (pin "H1") (pinfunction "IN3_H1") (pintype "input"))
    )
    (net (code "1686") (name "WRITE") (class "Default")
      (node (ref "B22") (pin "S1") (pinfunction "1_S1") (pintype "output"))
      (node (ref "C39") (pin "A1") (pinfunction "A1_A1") (pintype "input"))
      (node (ref "C39") (pin "E2") (pinfunction "E2_E2") (pintype "input"))
      (node (ref "C39") (pin "N2") (pinfunction "N2_N2") (pintype "input"))
    )
    (net (code "1687") (name "X_AXIS") (class "Default")
      (node (ref "D03") (pin "D2") (pinfunction "P$2_D2") (pintype "bidirectional"))
      (node (ref "HJ24") (pin "BS2") (pinfunction "BS2_BS2") (pintype "output"))
    )
    (net (code "1688") (name "X_RW_RETURN") (class "Default")
      (node (ref "B39") (pin "D2") (pinfunction "P$2_D2") (pintype "passive"))
      (node (ref "D25") (pin "T2") (pinfunction "T2_T2") (pintype "input"))
      (node (ref "D26") (pin "T2") (pinfunction "T2_T2") (pintype "input"))
      (node (ref "D32") (pin "T2") (pinfunction "T2_T2") (pintype "input"))
      (node (ref "D33") (pin "T2") (pinfunction "T2_T2") (pintype "input"))
      (node (ref "D39") (pin "F2") (pinfunction "F2_F2") (pintype "passive"))
      (node (ref "D39") (pin "K1") (pinfunction "K1_K1") (pintype "passive"))
    )
    (net (code "1689") (name "X_RW_SOURCE") (class "Default")
      (node (ref "A39") (pin "D2") (pinfunction "P$2_D2") (pintype "passive"))
      (node (ref "C30") (pin "T2") (pinfunction "T2_T2") (pintype "input"))
      (node (ref "C31") (pin "T2") (pinfunction "T2_T2") (pintype "input"))
      (node (ref "C37") (pin "T2") (pinfunction "T2_T2") (pintype "input"))
      (node (ref "C38") (pin "T2") (pinfunction "T2_T2") (pintype "input"))
      (node (ref "C39") (pin "F2") (pinfunction "F2_F2") (pintype "passive"))
      (node (ref "C39") (pin "K1") (pinfunction "K1_K1") (pintype "passive"))
    )
    (net (code "1690") (name "X_STROBE") (class "Default")
      (node (ref "HJ23") (pin "AS1") (pinfunction "AS1_AS1") (pintype "output"))
      (node (ref "HJ24") (pin "AD2") (pinfunction "AD2_AD2") (pintype "bidirectional"))
    )
    (net (code "1691") (name "Y_AXIS") (class "Default")
      (node (ref "D03") (pin "E2") (pinfunction "P$2_E2") (pintype "bidirectional"))
      (node (ref "HJ25") (pin "BS2") (pinfunction "BS2_BS2") (pintype "output"))
    )
    (net (code "1692") (name "Y_RW_RETURN") (class "Default")
      (node (ref "A38") (pin "D2") (pinfunction "P$2_D2") (pintype "passive"))
      (node (ref "D30") (pin "T2") (pinfunction "T2_T2") (pintype "input"))
      (node (ref "D31") (pin "T2") (pinfunction "T2_T2") (pintype "input"))
      (node (ref "D37") (pin "T2") (pinfunction "T2_T2") (pintype "input"))
      (node (ref "D38") (pin "T2") (pinfunction "T2_T2") (pintype "input"))
      (node (ref "D39") (pin "P2") (pinfunction "P2_P2") (pintype "passive"))
      (node (ref "D39") (pin "S1") (pinfunction "S1_S1") (pintype "passive"))
    )
    (net (code "1693") (name "Y_RW_SOURCE") (class "Default")
      (node (ref "B38") (pin "D2") (pinfunction "P$2_D2") (pintype "passive"))
      (node (ref "C25") (pin "T2") (pinfunction "T2_T2") (pintype "input"))
      (node (ref "C26") (pin "T2") (pinfunction "T2_T2") (pintype "input"))
      (node (ref "C32") (pin "T2") (pinfunction "T2_T2") (pintype "input"))
      (node (ref "C33") (pin "T2") (pinfunction "T2_T2") (pintype "input"))
      (node (ref "C39") (pin "P2") (pinfunction "P2_P2") (pintype "passive"))
      (node (ref "C39") (pin "S1") (pinfunction "S1_S1") (pintype "passive"))
    )
    (net (code "1694") (name "Y_STROBE") (class "Default")
      (node (ref "HJ23") (pin "AP2") (pinfunction "AP2_AP2") (pintype "output"))
      (node (ref "HJ25") (pin "AD2") (pinfunction "AD2_AD2") (pintype "bidirectional"))
    )
    (net (code "1695") (name "ZONE01_INDEX") (class "Default")
      (node (ref "HJ32") (pin "AK2") (pinfunction "AK2_AK2") (pintype "input"))
      (node (ref "HJ34") (pin "BD2") (pinfunction "P$2_BD2") (pintype "bidirectional"))
    )
    (net (code "1696") (name "ZONE02_INDEX") (class "Default")
      (node (ref "HJ32") (pin "AR2") (pinfunction "AR2_AR2") (pintype "input"))
      (node (ref "HJ34") (pin "BE2") (pinfunction "P$2_BE2") (pintype "bidirectional"))
    )
    (net (code "1697") (name "ZONE03_INDEX") (class "Default")
      (node (ref "HJ32") (pin "AP2") (pinfunction "AP2_AP2") (pintype "input"))
      (node (ref "HJ34") (pin "BF2") (pinfunction "P$2_BF2") (pintype "bidirectional"))
    )
    (net (code "1698") (name "ZONE04_INDEX") (class "Default")
      (node (ref "HJ32") (pin "BE2") (pinfunction "BE2_BE2") (pintype "input"))
      (node (ref "HJ34") (pin "BJ2") (pinfunction "P$2_BJ2") (pintype "bidirectional"))
    )
    (net (code "1699") (name "ZONE05_INDEX") (class "Default")
      (node (ref "HJ32") (pin "AS2") (pinfunction "AS2_AS2") (pintype "input"))
      (node (ref "HJ34") (pin "BK2") (pinfunction "P$2_BK2") (pintype "bidirectional"))
    )
    (net (code "1700") (name "ZONE06_INDEX") (class "Default")
      (node (ref "HJ32") (pin "BS1") (pinfunction "BS1_BS1") (pintype "input"))
      (node (ref "HJ34") (pin "BL2") (pinfunction "P$2_BL2") (pintype "bidirectional"))
    )
    (net (code "1701") (name "ZONE07_INDEX") (class "Default")
      (node (ref "HJ32") (pin "BR1") (pinfunction "BR1_BR1") (pintype "input"))
      (node (ref "HJ34") (pin "BM2") (pinfunction "P$2_BM2") (pintype "bidirectional"))
    )
    (net (code "1702") (name "ZONE08_INDEX") (class "Default")
      (node (ref "HJ32") (pin "BK2") (pinfunction "BK2_BK2") (pintype "input"))
      (node (ref "HJ34") (pin "BN2") (pinfunction "P$2_BN2") (pintype "bidirectional"))
    )
    (net (code "1703") (name "ZONE09_INDEX") (class "Default")
      (node (ref "HJ32") (pin "BL2") (pinfunction "BL2_BL2") (pintype "input"))
      (node (ref "HJ34") (pin "BS2") (pinfunction "P$2_BS2") (pintype "bidirectional"))
    )
    (net (code "1704") (name "ZONE10_INDEX") (class "Default")
      (node (ref "HJ32") (pin "AL2") (pinfunction "AL2_AL2") (pintype "input"))
      (node (ref "HJ34") (pin "BT2") (pinfunction "P$2_BT2") (pintype "bidirectional"))
    )
    (net (code "1705") (name "ZONE11_INDEX") (class "Default")
      (node (ref "HJ32") (pin "AE1") (pinfunction "AE1_AE1") (pintype "input"))
      (node (ref "HJ34") (pin "BU2") (pinfunction "P$2_BU2") (pintype "bidirectional"))
    )
    (net (code "1706") (name "ZONE12_INDEX") (class "Default")
      (node (ref "HJ32") (pin "AE2") (pinfunction "AE2_AE2") (pintype "input"))
      (node (ref "HJ34") (pin "BV2") (pinfunction "P$2_BV2") (pintype "bidirectional"))
    )
    (net (code "1707") (name "Z_AXIS") (class "Default")
      (node (ref "D03") (pin "F2") (pinfunction "P$2_F2") (pintype "bidirectional"))
      (node (ref "HJ23") (pin "AE2") (pinfunction "AE2_AE2") (pintype "output"))
    )
    (net (code "1708") (name "unconnected-(A04-PadT2)") (class "Default")
      (node (ref "A04") (pin "T2") (pinfunction "T2_T2") (pintype "output"))
    )
    (net (code "1709") (name "unconnected-(A08C-ODD-PadK1)") (class "Default")
      (node (ref "A08") (pin "K1") (pinfunction "ODD_K1") (pintype "output"))
    )
    (net (code "1710") (name "unconnected-(A10C-EVEN-PadL1)") (class "Default")
      (node (ref "A10") (pin "L1") (pinfunction "EVEN_L1") (pintype "output"))
    )
    (net (code "1711") (name "unconnected-(A21-PadJ2)") (class "Default")
      (node (ref "A21") (pin "J2") (pinfunction "J2_J2") (pintype "output"))
    )
    (net (code "1712") (name "unconnected-(A21-PadK2)") (class "Default")
      (node (ref "A21") (pin "K2") (pinfunction "K2_K2") (pintype "output"))
    )
    (net (code "1713") (name "unconnected-(A21-PadM2)") (class "Default")
      (node (ref "A21") (pin "M2") (pinfunction "M2_M2") (pintype "output"))
    )
    (net (code "1714") (name "unconnected-(A21-PadP2)") (class "Default")
      (node (ref "A21") (pin "P2") (pinfunction "P2_P2") (pintype "output"))
    )
    (net (code "1715") (name "unconnected-(A21-PadR2)") (class "Default")
      (node (ref "A21") (pin "R2") (pinfunction "R2_R2") (pintype "output"))
    )
    (net (code "1716") (name "unconnected-(A21-PadS2)") (class "Default")
      (node (ref "A21") (pin "S2") (pinfunction "S2_S2") (pintype "output"))
    )
    (net (code "1717") (name "unconnected-(A21-PadT2)") (class "Default")
      (node (ref "A21") (pin "T2") (pinfunction "T2_T2") (pintype "output"))
    )
    (net (code "1718") (name "unconnected-(A21-PadU2)") (class "Default")
      (node (ref "A21") (pin "U2") (pinfunction "U2_U2") (pintype "output"))
    )
    (net (code "1719") (name "unconnected-(A21-PadV2)") (class "Default")
      (node (ref "A21") (pin "V2") (pinfunction "V2_V2") (pintype "output"))
    )
    (net (code "1720") (name "unconnected-(A22-PadJ2)") (class "Default")
      (node (ref "A22") (pin "J2") (pinfunction "J2_J2") (pintype "output"))
    )
    (net (code "1721") (name "unconnected-(A22-PadK2)") (class "Default")
      (node (ref "A22") (pin "K2") (pinfunction "K2_K2") (pintype "output"))
    )
    (net (code "1722") (name "unconnected-(A22-PadL2)") (class "Default")
      (node (ref "A22") (pin "L2") (pinfunction "L2_L2") (pintype "output"))
    )
    (net (code "1723") (name "unconnected-(A22-PadM2)") (class "Default")
      (node (ref "A22") (pin "M2") (pinfunction "M2_M2") (pintype "output"))
    )
    (net (code "1724") (name "unconnected-(A22-PadN2)") (class "Default")
      (node (ref "A22") (pin "N2") (pinfunction "N2_N2") (pintype "output"))
    )
    (net (code "1725") (name "unconnected-(A22-PadP2)") (class "Default")
      (node (ref "A22") (pin "P2") (pinfunction "P2_P2") (pintype "output"))
    )
    (net (code "1726") (name "unconnected-(A22-PadS2)") (class "Default")
      (node (ref "A22") (pin "S2") (pinfunction "S2_S2") (pintype "output"))
    )
    (net (code "1727") (name "unconnected-(A22-PadT2)") (class "Default")
      (node (ref "A22") (pin "T2") (pinfunction "T2_T2") (pintype "output"))
    )
    (net (code "1728") (name "unconnected-(A22-PadU2)") (class "Default")
      (node (ref "A22") (pin "U2") (pinfunction "U2_U2") (pintype "output"))
    )
    (net (code "1729") (name "unconnected-(A22-PadV2)") (class "Default")
      (node (ref "A22") (pin "V2") (pinfunction "V2_V2") (pintype "output"))
    )
    (net (code "1730") (name "unconnected-(A23-PadJ2)") (class "Default")
      (node (ref "A23") (pin "J2") (pinfunction "J2_J2") (pintype "output"))
    )
    (net (code "1731") (name "unconnected-(A23-PadK2)") (class "Default")
      (node (ref "A23") (pin "K2") (pinfunction "K2_K2") (pintype "output"))
    )
    (net (code "1732") (name "unconnected-(A23-PadL2)") (class "Default")
      (node (ref "A23") (pin "L2") (pinfunction "L2_L2") (pintype "output"))
    )
    (net (code "1733") (name "unconnected-(A23-PadP2)") (class "Default")
      (node (ref "A23") (pin "P2") (pinfunction "P2_P2") (pintype "output"))
    )
    (net (code "1734") (name "unconnected-(A23-PadR2)") (class "Default")
      (node (ref "A23") (pin "R2") (pinfunction "R2_R2") (pintype "output"))
    )
    (net (code "1735") (name "unconnected-(A23-PadS2)") (class "Default")
      (node (ref "A23") (pin "S2") (pinfunction "S2_S2") (pintype "output"))
    )
    (net (code "1736") (name "unconnected-(A23-PadT2)") (class "Default")
      (node (ref "A23") (pin "T2") (pinfunction "T2_T2") (pintype "output"))
    )
    (net (code "1737") (name "unconnected-(A23-PadU2)") (class "Default")
      (node (ref "A23") (pin "U2") (pinfunction "U2_U2") (pintype "output"))
    )
    (net (code "1738") (name "unconnected-(A23-PadV2)") (class "Default")
      (node (ref "A23") (pin "V2") (pinfunction "V2_V2") (pintype "output"))
    )
    (net (code "1739") (name "unconnected-(A24-PadJ2)") (class "Default")
      (node (ref "A24") (pin "J2") (pinfunction "J2_J2") (pintype "output"))
    )
    (net (code "1740") (name "unconnected-(A24-PadK2)") (class "Default")
      (node (ref "A24") (pin "K2") (pinfunction "K2_K2") (pintype "output"))
    )
    (net (code "1741") (name "unconnected-(A24-PadL2)") (class "Default")
      (node (ref "A24") (pin "L2") (pinfunction "L2_L2") (pintype "output"))
    )
    (net (code "1742") (name "unconnected-(A24-PadM2)") (class "Default")
      (node (ref "A24") (pin "M2") (pinfunction "M2_M2") (pintype "output"))
    )
    (net (code "1743") (name "unconnected-(A24-PadN2)") (class "Default")
      (node (ref "A24") (pin "N2") (pinfunction "N2_N2") (pintype "output"))
    )
    (net (code "1744") (name "unconnected-(A24-PadP2)") (class "Default")
      (node (ref "A24") (pin "P2") (pinfunction "P2_P2") (pintype "output"))
    )
    (net (code "1745") (name "unconnected-(A24-PadR2)") (class "Default")
      (node (ref "A24") (pin "R2") (pinfunction "R2_R2") (pintype "output"))
    )
    (net (code "1746") (name "unconnected-(A24-PadS2)") (class "Default")
      (node (ref "A24") (pin "S2") (pinfunction "S2_S2") (pintype "output"))
    )
    (net (code "1747") (name "unconnected-(A24-PadU2)") (class "Default")
      (node (ref "A24") (pin "U2") (pinfunction "U2_U2") (pintype "output"))
    )
    (net (code "1748") (name "unconnected-(A24-PadV2)") (class "Default")
      (node (ref "A24") (pin "V2") (pinfunction "V2_V2") (pintype "output"))
    )
    (net (code "1749") (name "unconnected-(A30-PadC1)") (class "Default")
      (node (ref "A30") (pin "C1") (pinfunction "C1_C1") (pintype "output"))
    )
    (net (code "1750") (name "unconnected-(A30-PadE1)") (class "Default")
      (node (ref "A30") (pin "E1") (pinfunction "E1_E1") (pintype "output"))
    )
    (net (code "1751") (name "unconnected-(A30-PadF2)") (class "Default")
      (node (ref "A30") (pin "F2") (pinfunction "F2_F2") (pintype "input"))
    )
    (net (code "1752") (name "unconnected-(A30-PadH2)") (class "Default")
      (node (ref "A30") (pin "H2") (pinfunction "H2_H2") (pintype "input"))
    )
    (net (code "1753") (name "unconnected-(A30-PadJ2)") (class "Default")
      (node (ref "A30") (pin "J2") (pinfunction "J2_J2") (pintype "output"))
    )
    (net (code "1754") (name "unconnected-(A30-PadK2)") (class "Default")
      (node (ref "A30") (pin "K2") (pinfunction "K2_K2") (pintype "output"))
    )
    (net (code "1755") (name "unconnected-(A30-PadN1)") (class "Default")
      (node (ref "A30") (pin "N1") (pinfunction "N1_N1") (pintype "input"))
    )
    (net (code "1756") (name "unconnected-(A30-PadP1)") (class "Default")
      (node (ref "A30") (pin "P1") (pinfunction "P1_P1") (pintype "input"))
    )
    (net (code "1757") (name "unconnected-(A30-PadR2)") (class "Default")
      (node (ref "A30") (pin "R2") (pinfunction "R2_R2") (pintype "output"))
    )
    (net (code "1758") (name "unconnected-(A30-PadS1)") (class "Default")
      (node (ref "A30") (pin "S1") (pinfunction "S1_S1") (pintype "output"))
    )
    (net (code "1759") (name "unconnected-(A30-PadU2)") (class "Default")
      (node (ref "A30") (pin "U2") (pinfunction "U2_U2") (pintype "open_collector"))
    )
    (net (code "1760") (name "unconnected-(A31-PadC1)") (class "Default")
      (node (ref "A31") (pin "C1") (pinfunction "C1_C1") (pintype "output"))
    )
    (net (code "1761") (name "unconnected-(A31-PadE1)") (class "Default")
      (node (ref "A31") (pin "E1") (pinfunction "E1_E1") (pintype "output"))
    )
    (net (code "1762") (name "unconnected-(A31-PadJ2)") (class "Default")
      (node (ref "A31") (pin "J2") (pinfunction "J2_J2") (pintype "output"))
    )
    (net (code "1763") (name "unconnected-(A31-PadK2)") (class "Default")
      (node (ref "A31") (pin "K2") (pinfunction "K2_K2") (pintype "output"))
    )
    (net (code "1764") (name "unconnected-(A31-PadR2)") (class "Default")
      (node (ref "A31") (pin "R2") (pinfunction "R2_R2") (pintype "output"))
    )
    (net (code "1765") (name "unconnected-(A31-PadS1)") (class "Default")
      (node (ref "A31") (pin "S1") (pinfunction "S1_S1") (pintype "output"))
    )
    (net (code "1766") (name "unconnected-(A32-PadC1)") (class "Default")
      (node (ref "A32") (pin "C1") (pinfunction "C1_C1") (pintype "output"))
    )
    (net (code "1767") (name "unconnected-(A32-PadE1)") (class "Default")
      (node (ref "A32") (pin "E1") (pinfunction "E1_E1") (pintype "output"))
    )
    (net (code "1768") (name "unconnected-(A32-PadJ2)") (class "Default")
      (node (ref "A32") (pin "J2") (pinfunction "J2_J2") (pintype "output"))
    )
    (net (code "1769") (name "unconnected-(A32-PadK2)") (class "Default")
      (node (ref "A32") (pin "K2") (pinfunction "K2_K2") (pintype "output"))
    )
    (net (code "1770") (name "unconnected-(A32-PadR2)") (class "Default")
      (node (ref "A32") (pin "R2") (pinfunction "R2_R2") (pintype "output"))
    )
    (net (code "1771") (name "unconnected-(A32-PadS1)") (class "Default")
      (node (ref "A32") (pin "S1") (pinfunction "S1_S1") (pintype "output"))
    )
    (net (code "1772") (name "unconnected-(A33-PadC1)") (class "Default")
      (node (ref "A33") (pin "C1") (pinfunction "C1_C1") (pintype "output"))
    )
    (net (code "1773") (name "unconnected-(A33-PadE1)") (class "Default")
      (node (ref "A33") (pin "E1") (pinfunction "E1_E1") (pintype "output"))
    )
    (net (code "1774") (name "unconnected-(A33-PadJ2)") (class "Default")
      (node (ref "A33") (pin "J2") (pinfunction "J2_J2") (pintype "output"))
    )
    (net (code "1775") (name "unconnected-(A33-PadK2)") (class "Default")
      (node (ref "A33") (pin "K2") (pinfunction "K2_K2") (pintype "output"))
    )
    (net (code "1776") (name "unconnected-(A33-PadR2)") (class "Default")
      (node (ref "A33") (pin "R2") (pinfunction "R2_R2") (pintype "output"))
    )
    (net (code "1777") (name "unconnected-(A33-PadS1)") (class "Default")
      (node (ref "A33") (pin "S1") (pinfunction "S1_S1") (pintype "output"))
    )
    (net (code "1778") (name "unconnected-(A37-PadD1)") (class "Default")
      (node (ref "A37") (pin "D1") (pinfunction "D1_D1") (pintype "input"))
    )
    (net (code "1779") (name "unconnected-(A37-PadE1)") (class "Default")
      (node (ref "A37") (pin "E1") (pinfunction "E1_E1") (pintype "passive"))
    )
    (net (code "1780") (name "unconnected-(A37-PadK1)") (class "Default")
      (node (ref "A37") (pin "K1") (pinfunction "K1_K1") (pintype "passive"))
    )
    (net (code "1781") (name "unconnected-(A37-PadL1)") (class "Default")
      (node (ref "A37") (pin "L1") (pinfunction "L1_L1") (pintype "input"))
    )
    (net (code "1782") (name "unconnected-(A37-PadM1)") (class "Default")
      (node (ref "A37") (pin "M1") (pinfunction "M1_M1") (pintype "passive"))
    )
    (net (code "1783") (name "unconnected-(A37-PadS1)") (class "Default")
      (node (ref "A37") (pin "S1") (pinfunction "S1_S1") (pintype "passive"))
    )
    (net (code "1784") (name "unconnected-(A37-PadU2)") (class "Default")
      (node (ref "A37") (pin "U2") (pinfunction "U2_U2") (pintype "passive"))
    )
    (net (code "1785") (name "unconnected-(B05A-0-PadF1)") (class "Default")
      (node (ref "B05") (pin "F1") (pinfunction "0_F1") (pintype "output"))
    )
    (net (code "1786") (name "unconnected-(B05G-0-PadU1)") (class "Default")
      (node (ref "B05") (pin "U1") (pinfunction "0_U1") (pintype "output"))
    )
    (net (code "1787") (name "unconnected-(B05H-1-PadV2)") (class "Default")
      (node (ref "B05") (pin "V2") (pinfunction "1_V2") (pintype "output"))
    )
    (net (code "1788") (name "unconnected-(B11A-1-PadE1)") (class "Default")
      (node (ref "B11") (pin "E1") (pinfunction "1_E1") (pintype "output"))
    )
    (net (code "1789") (name "unconnected-(B11D-1-PadH2)") (class "Default")
      (node (ref "B11") (pin "H2") (pinfunction "1_H2") (pintype "output"))
    )
    (net (code "1790") (name "unconnected-(B11E-1-PadL1)") (class "Default")
      (node (ref "B11") (pin "L1") (pinfunction "1_L1") (pintype "output"))
    )
    (net (code "1791") (name "unconnected-(B17F-0-PadR2)") (class "Default")
      (node (ref "B17") (pin "R2") (pinfunction "0_R2") (pintype "output"))
    )
    (net (code "1792") (name "unconnected-(B17G-0-PadU1)") (class "Default")
      (node (ref "B17") (pin "U1") (pinfunction "0_U1") (pintype "output"))
    )
    (net (code "1793") (name "unconnected-(B17H-0-PadV1)") (class "Default")
      (node (ref "B17") (pin "V1") (pinfunction "0_V1") (pintype "output"))
    )
    (net (code "1794") (name "unconnected-(B18F-0-PadR2)") (class "Default")
      (node (ref "B18") (pin "R2") (pinfunction "0_R2") (pintype "output"))
    )
    (net (code "1795") (name "unconnected-(B18G-0-PadU1)") (class "Default")
      (node (ref "B18") (pin "U1") (pinfunction "0_U1") (pintype "output"))
    )
    (net (code "1796") (name "unconnected-(B18H-0-PadV1)") (class "Default")
      (node (ref "B18") (pin "V1") (pinfunction "0_V1") (pintype "output"))
    )
    (net (code "1797") (name "unconnected-(B19A-0-PadF1)") (class "Default")
      (node (ref "B19") (pin "F1") (pinfunction "0_F1") (pintype "output"))
    )
    (net (code "1798") (name "unconnected-(B19D-0-PadJ2)") (class "Default")
      (node (ref "B19") (pin "J2") (pinfunction "0_J2") (pintype "output"))
    )
    (net (code "1799") (name "unconnected-(B19E-0-PadM1)") (class "Default")
      (node (ref "B19") (pin "M1") (pinfunction "0_M1") (pintype "output"))
    )
    (net (code "1800") (name "unconnected-(B19F-0-PadR2)") (class "Default")
      (node (ref "B19") (pin "R2") (pinfunction "0_R2") (pintype "output"))
    )
    (net (code "1801") (name "unconnected-(B19G-0-PadU1)") (class "Default")
      (node (ref "B19") (pin "U1") (pinfunction "0_U1") (pintype "output"))
    )
    (net (code "1802") (name "unconnected-(B19H-0-PadV1)") (class "Default")
      (node (ref "B19") (pin "V1") (pinfunction "0_V1") (pintype "output"))
    )
    (net (code "1803") (name "unconnected-(B22A-1-PadE1)") (class "Default")
      (node (ref "B22") (pin "E1") (pinfunction "1_E1") (pintype "output"))
    )
    (net (code "1804") (name "unconnected-(B22E-0-PadM1)") (class "Default")
      (node (ref "B22") (pin "M1") (pinfunction "0_M1") (pintype "output"))
    )
    (net (code "1805") (name "unconnected-(B22F-1-PadP2)") (class "Default")
      (node (ref "B22") (pin "P2") (pinfunction "1_P2") (pintype "output"))
    )
    (net (code "1806") (name "unconnected-(B22G-0-PadU1)") (class "Default")
      (node (ref "B22") (pin "U1") (pinfunction "0_U1") (pintype "output"))
    )
    (net (code "1807") (name "unconnected-(B31-PadC1)") (class "Default")
      (node (ref "B31") (pin "C1") (pinfunction "C1_C1") (pintype "output"))
    )
    (net (code "1808") (name "unconnected-(B31-PadE1)") (class "Default")
      (node (ref "B31") (pin "E1") (pinfunction "E1_E1") (pintype "output"))
    )
    (net (code "1809") (name "unconnected-(B31-PadJ2)") (class "Default")
      (node (ref "B31") (pin "J2") (pinfunction "J2_J2") (pintype "output"))
    )
    (net (code "1810") (name "unconnected-(B31-PadK2)") (class "Default")
      (node (ref "B31") (pin "K2") (pinfunction "K2_K2") (pintype "output"))
    )
    (net (code "1811") (name "unconnected-(B31-PadR2)") (class "Default")
      (node (ref "B31") (pin "R2") (pinfunction "R2_R2") (pintype "output"))
    )
    (net (code "1812") (name "unconnected-(B31-PadS1)") (class "Default")
      (node (ref "B31") (pin "S1") (pinfunction "S1_S1") (pintype "output"))
    )
    (net (code "1813") (name "unconnected-(B32-PadC1)") (class "Default")
      (node (ref "B32") (pin "C1") (pinfunction "C1_C1") (pintype "output"))
    )
    (net (code "1814") (name "unconnected-(B32-PadE1)") (class "Default")
      (node (ref "B32") (pin "E1") (pinfunction "E1_E1") (pintype "output"))
    )
    (net (code "1815") (name "unconnected-(B32-PadJ2)") (class "Default")
      (node (ref "B32") (pin "J2") (pinfunction "J2_J2") (pintype "output"))
    )
    (net (code "1816") (name "unconnected-(B32-PadK2)") (class "Default")
      (node (ref "B32") (pin "K2") (pinfunction "K2_K2") (pintype "output"))
    )
    (net (code "1817") (name "unconnected-(B32-PadR2)") (class "Default")
      (node (ref "B32") (pin "R2") (pinfunction "R2_R2") (pintype "output"))
    )
    (net (code "1818") (name "unconnected-(B32-PadS1)") (class "Default")
      (node (ref "B32") (pin "S1") (pinfunction "S1_S1") (pintype "output"))
    )
    (net (code "1819") (name "unconnected-(B33-PadC1)") (class "Default")
      (node (ref "B33") (pin "C1") (pinfunction "C1_C1") (pintype "output"))
    )
    (net (code "1820") (name "unconnected-(B33-PadE1)") (class "Default")
      (node (ref "B33") (pin "E1") (pinfunction "E1_E1") (pintype "output"))
    )
    (net (code "1821") (name "unconnected-(B33-PadJ2)") (class "Default")
      (node (ref "B33") (pin "J2") (pinfunction "J2_J2") (pintype "output"))
    )
    (net (code "1822") (name "unconnected-(B33-PadK2)") (class "Default")
      (node (ref "B33") (pin "K2") (pinfunction "K2_K2") (pintype "output"))
    )
    (net (code "1823") (name "unconnected-(B33-PadR2)") (class "Default")
      (node (ref "B33") (pin "R2") (pinfunction "R2_R2") (pintype "output"))
    )
    (net (code "1824") (name "unconnected-(B33-PadS1)") (class "Default")
      (node (ref "B33") (pin "S1") (pinfunction "S1_S1") (pintype "output"))
    )
    (net (code "1825") (name "unconnected-(C13-PadJ2)") (class "Default")
      (node (ref "C13") (pin "J2") (pinfunction "J2_J2") (pintype "output"))
    )
    (net (code "1826") (name "unconnected-(C13-PadK2)") (class "Default")
      (node (ref "C13") (pin "K2") (pinfunction "K2_K2") (pintype "output"))
    )
    (net (code "1827") (name "unconnected-(C13-PadL2)") (class "Default")
      (node (ref "C13") (pin "L2") (pinfunction "L2_L2") (pintype "output"))
    )
    (net (code "1828") (name "unconnected-(C13-PadM2)") (class "Default")
      (node (ref "C13") (pin "M2") (pinfunction "M2_M2") (pintype "output"))
    )
    (net (code "1829") (name "unconnected-(C13-PadN2)") (class "Default")
      (node (ref "C13") (pin "N2") (pinfunction "N2_N2") (pintype "output"))
    )
    (net (code "1830") (name "unconnected-(C13-PadR2)") (class "Default")
      (node (ref "C13") (pin "R2") (pinfunction "R2_R2") (pintype "output"))
    )
    (net (code "1831") (name "unconnected-(C13-PadT2)") (class "Default")
      (node (ref "C13") (pin "T2") (pinfunction "T2_T2") (pintype "output"))
    )
    (net (code "1832") (name "unconnected-(C13-PadU2)") (class "Default")
      (node (ref "C13") (pin "U2") (pinfunction "U2_U2") (pintype "output"))
    )
    (net (code "1833") (name "unconnected-(C13-PadV2)") (class "Default")
      (node (ref "C13") (pin "V2") (pinfunction "V2_V2") (pintype "output"))
    )
    (net (code "1834") (name "unconnected-(C22H-0-PadV1)") (class "Default")
      (node (ref "C22") (pin "V1") (pinfunction "0_V1") (pintype "output"))
    )
    (net (code "1835") (name "unconnected-(D06-PadJ2)") (class "Default")
      (node (ref "D06") (pin "J2") (pinfunction "J2_J2") (pintype "output"))
    )
    (net (code "1836") (name "unconnected-(D06-PadK2)") (class "Default")
      (node (ref "D06") (pin "K2") (pinfunction "K2_K2") (pintype "output"))
    )
    (net (code "1837") (name "unconnected-(D06-PadL2)") (class "Default")
      (node (ref "D06") (pin "L2") (pinfunction "L2_L2") (pintype "output"))
    )
    (net (code "1838") (name "unconnected-(D06-PadM2)") (class "Default")
      (node (ref "D06") (pin "M2") (pinfunction "M2_M2") (pintype "output"))
    )
    (net (code "1839") (name "unconnected-(D06-PadN2)") (class "Default")
      (node (ref "D06") (pin "N2") (pinfunction "N2_N2") (pintype "output"))
    )
    (net (code "1840") (name "unconnected-(D06-PadP2)") (class "Default")
      (node (ref "D06") (pin "P2") (pinfunction "P2_P2") (pintype "output"))
    )
    (net (code "1841") (name "unconnected-(D06-PadS2)") (class "Default")
      (node (ref "D06") (pin "S2") (pinfunction "S2_S2") (pintype "output"))
    )
    (net (code "1842") (name "unconnected-(D06-PadT2)") (class "Default")
      (node (ref "D06") (pin "T2") (pinfunction "T2_T2") (pintype "output"))
    )
    (net (code "1843") (name "unconnected-(D06-PadU2)") (class "Default")
      (node (ref "D06") (pin "U2") (pinfunction "U2_U2") (pintype "output"))
    )
    (net (code "1844") (name "unconnected-(D06-PadV2)") (class "Default")
      (node (ref "D06") (pin "V2") (pinfunction "V2_V2") (pintype "output"))
    )
    (net (code "1845") (name "unconnected-(D08-PadJ2)") (class "Default")
      (node (ref "D08") (pin "J2") (pinfunction "J2_J2") (pintype "output"))
    )
    (net (code "1846") (name "unconnected-(D08-PadK2)") (class "Default")
      (node (ref "D08") (pin "K2") (pinfunction "K2_K2") (pintype "output"))
    )
    (net (code "1847") (name "unconnected-(D08-PadL2)") (class "Default")
      (node (ref "D08") (pin "L2") (pinfunction "L2_L2") (pintype "output"))
    )
    (net (code "1848") (name "unconnected-(D08-PadM2)") (class "Default")
      (node (ref "D08") (pin "M2") (pinfunction "M2_M2") (pintype "output"))
    )
    (net (code "1849") (name "unconnected-(D08-PadN2)") (class "Default")
      (node (ref "D08") (pin "N2") (pinfunction "N2_N2") (pintype "output"))
    )
    (net (code "1850") (name "unconnected-(D08-PadP2)") (class "Default")
      (node (ref "D08") (pin "P2") (pinfunction "P2_P2") (pintype "output"))
    )
    (net (code "1851") (name "unconnected-(D08-PadS2)") (class "Default")
      (node (ref "D08") (pin "S2") (pinfunction "S2_S2") (pintype "output"))
    )
    (net (code "1852") (name "unconnected-(D08-PadT2)") (class "Default")
      (node (ref "D08") (pin "T2") (pinfunction "T2_T2") (pintype "output"))
    )
    (net (code "1853") (name "unconnected-(D08-PadU2)") (class "Default")
      (node (ref "D08") (pin "U2") (pinfunction "U2_U2") (pintype "output"))
    )
    (net (code "1854") (name "unconnected-(D08-PadV2)") (class "Default")
      (node (ref "D08") (pin "V2") (pinfunction "V2_V2") (pintype "output"))
    )
    (net (code "1855") (name "unconnected-(D24H-0-PadV1)") (class "Default")
      (node (ref "D24") (pin "V1") (pinfunction "0_V1") (pintype "output"))
    )
    (net (code "1856") (name "unconnected-(E16-PadJ2)") (class "Default")
      (node (ref "E16") (pin "J2") (pinfunction "J2_J2") (pintype "output"))
    )
    (net (code "1857") (name "unconnected-(E16-PadK2)") (class "Default")
      (node (ref "E16") (pin "K2") (pinfunction "K2_K2") (pintype "output"))
    )
    (net (code "1858") (name "unconnected-(E16-PadL2)") (class "Default")
      (node (ref "E16") (pin "L2") (pinfunction "L2_L2") (pintype "output"))
    )
    (net (code "1859") (name "unconnected-(E16-PadM2)") (class "Default")
      (node (ref "E16") (pin "M2") (pinfunction "M2_M2") (pintype "output"))
    )
    (net (code "1860") (name "unconnected-(E16-PadN2)") (class "Default")
      (node (ref "E16") (pin "N2") (pinfunction "N2_N2") (pintype "output"))
    )
    (net (code "1861") (name "unconnected-(E16-PadP2)") (class "Default")
      (node (ref "E16") (pin "P2") (pinfunction "P2_P2") (pintype "output"))
    )
    (net (code "1862") (name "unconnected-(E16-PadS2)") (class "Default")
      (node (ref "E16") (pin "S2") (pinfunction "S2_S2") (pintype "output"))
    )
    (net (code "1863") (name "unconnected-(E16-PadT2)") (class "Default")
      (node (ref "E16") (pin "T2") (pinfunction "T2_T2") (pintype "output"))
    )
    (net (code "1864") (name "unconnected-(E16-PadU2)") (class "Default")
      (node (ref "E16") (pin "U2") (pinfunction "U2_U2") (pintype "output"))
    )
    (net (code "1865") (name "unconnected-(E16-PadV2)") (class "Default")
      (node (ref "E16") (pin "V2") (pinfunction "V2_V2") (pintype "output"))
    )
    (net (code "1866") (name "unconnected-(E17-PadJ2)") (class "Default")
      (node (ref "E17") (pin "J2") (pinfunction "J2_J2") (pintype "output"))
    )
    (net (code "1867") (name "unconnected-(E17-PadK2)") (class "Default")
      (node (ref "E17") (pin "K2") (pinfunction "K2_K2") (pintype "output"))
    )
    (net (code "1868") (name "unconnected-(E17-PadL2)") (class "Default")
      (node (ref "E17") (pin "L2") (pinfunction "L2_L2") (pintype "output"))
    )
    (net (code "1869") (name "unconnected-(E17-PadN2)") (class "Default")
      (node (ref "E17") (pin "N2") (pinfunction "N2_N2") (pintype "output"))
    )
    (net (code "1870") (name "unconnected-(E17-PadP2)") (class "Default")
      (node (ref "E17") (pin "P2") (pinfunction "P2_P2") (pintype "output"))
    )
    (net (code "1871") (name "unconnected-(E17-PadR2)") (class "Default")
      (node (ref "E17") (pin "R2") (pinfunction "R2_R2") (pintype "output"))
    )
    (net (code "1872") (name "unconnected-(E17-PadS2)") (class "Default")
      (node (ref "E17") (pin "S2") (pinfunction "S2_S2") (pintype "output"))
    )
    (net (code "1873") (name "unconnected-(E17-PadT2)") (class "Default")
      (node (ref "E17") (pin "T2") (pinfunction "T2_T2") (pintype "output"))
    )
    (net (code "1874") (name "unconnected-(E17-PadV2)") (class "Default")
      (node (ref "E17") (pin "V2") (pinfunction "V2_V2") (pintype "output"))
    )
    (net (code "1875") (name "unconnected-(E18D-0-PadJ2)") (class "Default")
      (node (ref "E18") (pin "J2") (pinfunction "0_J2") (pintype "output"))
    )
    (net (code "1876") (name "unconnected-(E18E-1-PadL1)") (class "Default")
      (node (ref "E18") (pin "L1") (pinfunction "1_L1") (pintype "output"))
    )
    (net (code "1877") (name "unconnected-(E18G-0-PadU1)") (class "Default")
      (node (ref "E18") (pin "U1") (pinfunction "0_U1") (pintype "output"))
    )
    (net (code "1878") (name "unconnected-(E19A-0-PadF1)") (class "Default")
      (node (ref "E19") (pin "F1") (pinfunction "0_F1") (pintype "output"))
    )
    (net (code "1879") (name "unconnected-(E20F-0-PadR2)") (class "Default")
      (node (ref "E20") (pin "R2") (pinfunction "0_R2") (pintype "output"))
    )
    (net (code "1880") (name "unconnected-(E20G-0-PadU1)") (class "Default")
      (node (ref "E20") (pin "U1") (pinfunction "0_U1") (pintype "output"))
    )
    (net (code "1881") (name "unconnected-(E22N-OUT-PadV2)") (class "Default")
      (node (ref "E22") (pin "V2") (pinfunction "OUT_V2") (pintype "output"))
    )
    (net (code "1882") (name "unconnected-(E23A-1-PadE1)") (class "Default")
      (node (ref "E23") (pin "E1") (pinfunction "1_E1") (pintype "output"))
    )
    (net (code "1883") (name "unconnected-(E23E-1-PadL1)") (class "Default")
      (node (ref "E23") (pin "L1") (pinfunction "1_L1") (pintype "output"))
    )
    (net (code "1884") (name "unconnected-(E33A-0-PadF1)") (class "Default")
      (node (ref "E33") (pin "F1") (pinfunction "0_F1") (pintype "output"))
    )
    (net (code "1885") (name "unconnected-(E33D-0-PadJ2)") (class "Default")
      (node (ref "E33") (pin "J2") (pinfunction "0_J2") (pintype "output"))
    )
    (net (code "1886") (name "unconnected-(E33E-1-PadL1)") (class "Default")
      (node (ref "E33") (pin "L1") (pinfunction "1_L1") (pintype "output"))
    )
    (net (code "1887") (name "unconnected-(E33F-1-PadP2)") (class "Default")
      (node (ref "E33") (pin "P2") (pinfunction "1_P2") (pintype "output"))
    )
    (net (code "1888") (name "unconnected-(EF01-PadAD1)") (class "Default")
      (node (ref "EF01") (pin "AD1") (pinfunction "AD1_AD1") (pintype "output"))
    )
    (net (code "1889") (name "unconnected-(EF01-PadAS1)") (class "Default")
      (node (ref "EF01") (pin "AS1") (pinfunction "AS1_AS1") (pintype "output"))
    )
    (net (code "1890") (name "unconnected-(EF01-PadBK2)") (class "Default")
      (node (ref "EF01") (pin "BK2") (pinfunction "BK2_BK2") (pintype "output"))
    )
    (net (code "1891") (name "unconnected-(EF01-PadBN2)") (class "Default")
      (node (ref "EF01") (pin "BN2") (pinfunction "BN2_BN2") (pintype "output"))
    )
    (net (code "1892") (name "unconnected-(EF01-PadBS1)") (class "Default")
      (node (ref "EF01") (pin "BS1") (pinfunction "BS1_BS1") (pintype "output"))
    )
    (net (code "1893") (name "unconnected-(EF01-PadBS2)") (class "Default")
      (node (ref "EF01") (pin "BS2") (pinfunction "BS2_BS2") (pintype "output"))
    )
    (net (code "1894") (name "unconnected-(EF01-PadBU2)") (class "Default")
      (node (ref "EF01") (pin "BU2") (pinfunction "BU2_BU2") (pintype "output"))
    )
    (net (code "1895") (name "unconnected-(EF02-PadAD1)") (class "Default")
      (node (ref "EF02") (pin "AD1") (pinfunction "AD1_AD1") (pintype "output"))
    )
    (net (code "1896") (name "unconnected-(EF02-PadAD2)") (class "Default")
      (node (ref "EF02") (pin "AD2") (pinfunction "AD2_AD2") (pintype "output"))
    )
    (net (code "1897") (name "unconnected-(EF02-PadAJ1)") (class "Default")
      (node (ref "EF02") (pin "AJ1") (pinfunction "AJ1_AJ1") (pintype "output"))
    )
    (net (code "1898") (name "unconnected-(EF02-PadAR1)") (class "Default")
      (node (ref "EF02") (pin "AR1") (pinfunction "AR1_AR1") (pintype "output"))
    )
    (net (code "1899") (name "unconnected-(EF02-PadBP1)") (class "Default")
      (node (ref "EF02") (pin "BP1") (pinfunction "BP1_BP1") (pintype "output"))
    )
    (net (code "1900") (name "unconnected-(EF02-PadBR2)") (class "Default")
      (node (ref "EF02") (pin "BR2") (pinfunction "BR2_BR2") (pintype "output"))
    )
    (net (code "1901") (name "unconnected-(EF10C-CN2-PadAN2)") (class "Default")
      (node (ref "EF10") (pin "AN2") (pinfunction "CN2_AN2") (pintype "output"))
    )
    (net (code "1902") (name "unconnected-(EF34-PadAJ1)") (class "Default")
      (node (ref "EF34") (pin "AJ1") (pinfunction "AJ1_AJ1") (pintype "output"))
    )
    (net (code "1903") (name "unconnected-(EF34-PadAK2)") (class "Default")
      (node (ref "EF34") (pin "AK2") (pinfunction "AK2_AK2") (pintype "output"))
    )
    (net (code "1904") (name "unconnected-(EF34-PadAN1)") (class "Default")
      (node (ref "EF34") (pin "AN1") (pinfunction "AN1_AN1") (pintype "output"))
    )
    (net (code "1905") (name "unconnected-(EF34-PadAP1)") (class "Default")
      (node (ref "EF34") (pin "AP1") (pinfunction "AP1_AP1") (pintype "output"))
    )
    (net (code "1906") (name "unconnected-(EF35-PadAJ1)") (class "Default")
      (node (ref "EF35") (pin "AJ1") (pinfunction "AJ1_AJ1") (pintype "output"))
    )
    (net (code "1907") (name "unconnected-(EF35-PadAK2)") (class "Default")
      (node (ref "EF35") (pin "AK2") (pinfunction "AK2_AK2") (pintype "output"))
    )
    (net (code "1908") (name "unconnected-(EF35-PadAN1)") (class "Default")
      (node (ref "EF35") (pin "AN1") (pinfunction "AN1_AN1") (pintype "output"))
    )
    (net (code "1909") (name "unconnected-(EF35-PadAP1)") (class "Default")
      (node (ref "EF35") (pin "AP1") (pinfunction "AP1_AP1") (pintype "output"))
    )
    (net (code "1910") (name "unconnected-(EF36-PadAJ1)") (class "Default")
      (node (ref "EF36") (pin "AJ1") (pinfunction "AJ1_AJ1") (pintype "output"))
    )
    (net (code "1911") (name "unconnected-(EF36-PadAK2)") (class "Default")
      (node (ref "EF36") (pin "AK2") (pinfunction "AK2_AK2") (pintype "output"))
    )
    (net (code "1912") (name "unconnected-(EF36-PadAN1)") (class "Default")
      (node (ref "EF36") (pin "AN1") (pinfunction "AN1_AN1") (pintype "output"))
    )
    (net (code "1913") (name "unconnected-(EF36-PadAP1)") (class "Default")
      (node (ref "EF36") (pin "AP1") (pinfunction "AP1_AP1") (pintype "output"))
    )
    (net (code "1914") (name "unconnected-(EF37-PadAJ1)") (class "Default")
      (node (ref "EF37") (pin "AJ1") (pinfunction "AJ1_AJ1") (pintype "output"))
    )
    (net (code "1915") (name "unconnected-(EF37-PadAK2)") (class "Default")
      (node (ref "EF37") (pin "AK2") (pinfunction "AK2_AK2") (pintype "output"))
    )
    (net (code "1916") (name "unconnected-(EF37-PadAN1)") (class "Default")
      (node (ref "EF37") (pin "AN1") (pinfunction "AN1_AN1") (pintype "output"))
    )
    (net (code "1917") (name "unconnected-(EF37-PadAP1)") (class "Default")
      (node (ref "EF37") (pin "AP1") (pinfunction "AP1_AP1") (pintype "output"))
    )
    (net (code "1918") (name "unconnected-(EF38-PadAJ1)") (class "Default")
      (node (ref "EF38") (pin "AJ1") (pinfunction "AJ1_AJ1") (pintype "output"))
    )
    (net (code "1919") (name "unconnected-(EF38-PadAK2)") (class "Default")
      (node (ref "EF38") (pin "AK2") (pinfunction "AK2_AK2") (pintype "output"))
    )
    (net (code "1920") (name "unconnected-(EF38-PadAN1)") (class "Default")
      (node (ref "EF38") (pin "AN1") (pinfunction "AN1_AN1") (pintype "output"))
    )
    (net (code "1921") (name "unconnected-(EF38-PadAP1)") (class "Default")
      (node (ref "EF38") (pin "AP1") (pinfunction "AP1_AP1") (pintype "output"))
    )
    (net (code "1922") (name "unconnected-(EF39-PadAJ1)") (class "Default")
      (node (ref "EF39") (pin "AJ1") (pinfunction "AJ1_AJ1") (pintype "output"))
    )
    (net (code "1923") (name "unconnected-(EF39-PadAK2)") (class "Default")
      (node (ref "EF39") (pin "AK2") (pinfunction "AK2_AK2") (pintype "output"))
    )
    (net (code "1924") (name "unconnected-(EF39-PadAN1)") (class "Default")
      (node (ref "EF39") (pin "AN1") (pinfunction "AN1_AN1") (pintype "output"))
    )
    (net (code "1925") (name "unconnected-(EF39-PadAP1)") (class "Default")
      (node (ref "EF39") (pin "AP1") (pinfunction "AP1_AP1") (pintype "output"))
    )
    (net (code "1926") (name "unconnected-(F03-PadL2)") (class "Default")
      (node (ref "F03") (pin "L2") (pinfunction "L2_L2") (pintype "output"))
    )
    (net (code "1927") (name "unconnected-(F03-PadM2)") (class "Default")
      (node (ref "F03") (pin "M2") (pinfunction "M2_M2") (pintype "output"))
    )
    (net (code "1928") (name "unconnected-(F03-PadN2)") (class "Default")
      (node (ref "F03") (pin "N2") (pinfunction "N2_N2") (pintype "output"))
    )
    (net (code "1929") (name "unconnected-(F12-PadJ2)") (class "Default")
      (node (ref "F12") (pin "J2") (pinfunction "J2_J2") (pintype "output"))
    )
    (net (code "1930") (name "unconnected-(F12-PadK2)") (class "Default")
      (node (ref "F12") (pin "K2") (pinfunction "K2_K2") (pintype "output"))
    )
    (net (code "1931") (name "unconnected-(F12-PadL2)") (class "Default")
      (node (ref "F12") (pin "L2") (pinfunction "L2_L2") (pintype "output"))
    )
    (net (code "1932") (name "unconnected-(F12-PadM2)") (class "Default")
      (node (ref "F12") (pin "M2") (pinfunction "M2_M2") (pintype "output"))
    )
    (net (code "1933") (name "unconnected-(F12-PadN2)") (class "Default")
      (node (ref "F12") (pin "N2") (pinfunction "N2_N2") (pintype "output"))
    )
    (net (code "1934") (name "unconnected-(F12-PadP2)") (class "Default")
      (node (ref "F12") (pin "P2") (pinfunction "P2_P2") (pintype "output"))
    )
    (net (code "1935") (name "unconnected-(F12-PadR2)") (class "Default")
      (node (ref "F12") (pin "R2") (pinfunction "R2_R2") (pintype "output"))
    )
    (net (code "1936") (name "unconnected-(F12-PadS2)") (class "Default")
      (node (ref "F12") (pin "S2") (pinfunction "S2_S2") (pintype "output"))
    )
    (net (code "1937") (name "unconnected-(F12-PadU2)") (class "Default")
      (node (ref "F12") (pin "U2") (pinfunction "U2_U2") (pintype "output"))
    )
    (net (code "1938") (name "unconnected-(F12-PadV2)") (class "Default")
      (node (ref "F12") (pin "V2") (pinfunction "V2_V2") (pintype "output"))
    )
    (net (code "1939") (name "unconnected-(F13-PadJ2)") (class "Default")
      (node (ref "F13") (pin "J2") (pinfunction "J2_J2") (pintype "output"))
    )
    (net (code "1940") (name "unconnected-(F13-PadK2)") (class "Default")
      (node (ref "F13") (pin "K2") (pinfunction "K2_K2") (pintype "output"))
    )
    (net (code "1941") (name "unconnected-(F13-PadL2)") (class "Default")
      (node (ref "F13") (pin "L2") (pinfunction "L2_L2") (pintype "output"))
    )
    (net (code "1942") (name "unconnected-(F13-PadN2)") (class "Default")
      (node (ref "F13") (pin "N2") (pinfunction "N2_N2") (pintype "output"))
    )
    (net (code "1943") (name "unconnected-(F13-PadP2)") (class "Default")
      (node (ref "F13") (pin "P2") (pinfunction "P2_P2") (pintype "output"))
    )
    (net (code "1944") (name "unconnected-(F13-PadR2)") (class "Default")
      (node (ref "F13") (pin "R2") (pinfunction "R2_R2") (pintype "output"))
    )
    (net (code "1945") (name "unconnected-(F13-PadS2)") (class "Default")
      (node (ref "F13") (pin "S2") (pinfunction "S2_S2") (pintype "output"))
    )
    (net (code "1946") (name "unconnected-(F13-PadU2)") (class "Default")
      (node (ref "F13") (pin "U2") (pinfunction "U2_U2") (pintype "output"))
    )
    (net (code "1947") (name "unconnected-(F13-PadV2)") (class "Default")
      (node (ref "F13") (pin "V2") (pinfunction "V2_V2") (pintype "output"))
    )
    (net (code "1948") (name "unconnected-(F14-PadJ2)") (class "Default")
      (node (ref "F14") (pin "J2") (pinfunction "J2_J2") (pintype "output"))
    )
    (net (code "1949") (name "unconnected-(F14-PadK2)") (class "Default")
      (node (ref "F14") (pin "K2") (pinfunction "K2_K2") (pintype "output"))
    )
    (net (code "1950") (name "unconnected-(F14-PadL2)") (class "Default")
      (node (ref "F14") (pin "L2") (pinfunction "L2_L2") (pintype "output"))
    )
    (net (code "1951") (name "unconnected-(F14-PadM2)") (class "Default")
      (node (ref "F14") (pin "M2") (pinfunction "M2_M2") (pintype "output"))
    )
    (net (code "1952") (name "unconnected-(F14-PadN2)") (class "Default")
      (node (ref "F14") (pin "N2") (pinfunction "N2_N2") (pintype "output"))
    )
    (net (code "1953") (name "unconnected-(F14-PadP2)") (class "Default")
      (node (ref "F14") (pin "P2") (pinfunction "P2_P2") (pintype "output"))
    )
    (net (code "1954") (name "unconnected-(F14-PadR2)") (class "Default")
      (node (ref "F14") (pin "R2") (pinfunction "R2_R2") (pintype "output"))
    )
    (net (code "1955") (name "unconnected-(F14-PadU2)") (class "Default")
      (node (ref "F14") (pin "U2") (pinfunction "U2_U2") (pintype "output"))
    )
    (net (code "1956") (name "unconnected-(F14-PadV2)") (class "Default")
      (node (ref "F14") (pin "V2") (pinfunction "V2_V2") (pintype "output"))
    )
    (net (code "1957") (name "unconnected-(F15-PadJ2)") (class "Default")
      (node (ref "F15") (pin "J2") (pinfunction "J2_J2") (pintype "output"))
    )
    (net (code "1958") (name "unconnected-(F15-PadK2)") (class "Default")
      (node (ref "F15") (pin "K2") (pinfunction "K2_K2") (pintype "output"))
    )
    (net (code "1959") (name "unconnected-(F15-PadL2)") (class "Default")
      (node (ref "F15") (pin "L2") (pinfunction "L2_L2") (pintype "output"))
    )
    (net (code "1960") (name "unconnected-(F15-PadN2)") (class "Default")
      (node (ref "F15") (pin "N2") (pinfunction "N2_N2") (pintype "output"))
    )
    (net (code "1961") (name "unconnected-(F15-PadP2)") (class "Default")
      (node (ref "F15") (pin "P2") (pinfunction "P2_P2") (pintype "output"))
    )
    (net (code "1962") (name "unconnected-(F15-PadR2)") (class "Default")
      (node (ref "F15") (pin "R2") (pinfunction "R2_R2") (pintype "output"))
    )
    (net (code "1963") (name "unconnected-(F15-PadS2)") (class "Default")
      (node (ref "F15") (pin "S2") (pinfunction "S2_S2") (pintype "output"))
    )
    (net (code "1964") (name "unconnected-(F15-PadU2)") (class "Default")
      (node (ref "F15") (pin "U2") (pinfunction "U2_U2") (pintype "output"))
    )
    (net (code "1965") (name "unconnected-(F15-PadV2)") (class "Default")
      (node (ref "F15") (pin "V2") (pinfunction "V2_V2") (pintype "output"))
    )
    (net (code "1966") (name "unconnected-(F16-PadJ2)") (class "Default")
      (node (ref "F16") (pin "J2") (pinfunction "J2_J2") (pintype "output"))
    )
    (net (code "1967") (name "unconnected-(F16-PadK2)") (class "Default")
      (node (ref "F16") (pin "K2") (pinfunction "K2_K2") (pintype "output"))
    )
    (net (code "1968") (name "unconnected-(F16-PadL2)") (class "Default")
      (node (ref "F16") (pin "L2") (pinfunction "L2_L2") (pintype "output"))
    )
    (net (code "1969") (name "unconnected-(F16-PadM2)") (class "Default")
      (node (ref "F16") (pin "M2") (pinfunction "M2_M2") (pintype "output"))
    )
    (net (code "1970") (name "unconnected-(F16-PadN2)") (class "Default")
      (node (ref "F16") (pin "N2") (pinfunction "N2_N2") (pintype "output"))
    )
    (net (code "1971") (name "unconnected-(F16-PadP2)") (class "Default")
      (node (ref "F16") (pin "P2") (pinfunction "P2_P2") (pintype "output"))
    )
    (net (code "1972") (name "unconnected-(F16-PadR2)") (class "Default")
      (node (ref "F16") (pin "R2") (pinfunction "R2_R2") (pintype "output"))
    )
    (net (code "1973") (name "unconnected-(F16-PadU2)") (class "Default")
      (node (ref "F16") (pin "U2") (pinfunction "U2_U2") (pintype "output"))
    )
    (net (code "1974") (name "unconnected-(F16-PadV2)") (class "Default")
      (node (ref "F16") (pin "V2") (pinfunction "V2_V2") (pintype "output"))
    )
    (net (code "1975") (name "unconnected-(F17-PadJ2)") (class "Default")
      (node (ref "F17") (pin "J2") (pinfunction "J2_J2") (pintype "output"))
    )
    (net (code "1976") (name "unconnected-(F17-PadK2)") (class "Default")
      (node (ref "F17") (pin "K2") (pinfunction "K2_K2") (pintype "output"))
    )
    (net (code "1977") (name "unconnected-(F17-PadL2)") (class "Default")
      (node (ref "F17") (pin "L2") (pinfunction "L2_L2") (pintype "output"))
    )
    (net (code "1978") (name "unconnected-(F17-PadN2)") (class "Default")
      (node (ref "F17") (pin "N2") (pinfunction "N2_N2") (pintype "output"))
    )
    (net (code "1979") (name "unconnected-(F17-PadP2)") (class "Default")
      (node (ref "F17") (pin "P2") (pinfunction "P2_P2") (pintype "output"))
    )
    (net (code "1980") (name "unconnected-(F17-PadR2)") (class "Default")
      (node (ref "F17") (pin "R2") (pinfunction "R2_R2") (pintype "output"))
    )
    (net (code "1981") (name "unconnected-(F17-PadS2)") (class "Default")
      (node (ref "F17") (pin "S2") (pinfunction "S2_S2") (pintype "output"))
    )
    (net (code "1982") (name "unconnected-(F17-PadU2)") (class "Default")
      (node (ref "F17") (pin "U2") (pinfunction "U2_U2") (pintype "output"))
    )
    (net (code "1983") (name "unconnected-(F17-PadV2)") (class "Default")
      (node (ref "F17") (pin "V2") (pinfunction "V2_V2") (pintype "output"))
    )
    (net (code "1984") (name "unconnected-(F18-PadJ2)") (class "Default")
      (node (ref "F18") (pin "J2") (pinfunction "J2_J2") (pintype "output"))
    )
    (net (code "1985") (name "unconnected-(F18-PadK2)") (class "Default")
      (node (ref "F18") (pin "K2") (pinfunction "K2_K2") (pintype "output"))
    )
    (net (code "1986") (name "unconnected-(F18-PadL2)") (class "Default")
      (node (ref "F18") (pin "L2") (pinfunction "L2_L2") (pintype "output"))
    )
    (net (code "1987") (name "unconnected-(F18-PadM2)") (class "Default")
      (node (ref "F18") (pin "M2") (pinfunction "M2_M2") (pintype "output"))
    )
    (net (code "1988") (name "unconnected-(F18-PadN2)") (class "Default")
      (node (ref "F18") (pin "N2") (pinfunction "N2_N2") (pintype "output"))
    )
    (net (code "1989") (name "unconnected-(F18-PadP2)") (class "Default")
      (node (ref "F18") (pin "P2") (pinfunction "P2_P2") (pintype "output"))
    )
    (net (code "1990") (name "unconnected-(F18-PadR2)") (class "Default")
      (node (ref "F18") (pin "R2") (pinfunction "R2_R2") (pintype "output"))
    )
    (net (code "1991") (name "unconnected-(F18-PadU2)") (class "Default")
      (node (ref "F18") (pin "U2") (pinfunction "U2_U2") (pintype "output"))
    )
    (net (code "1992") (name "unconnected-(F18-PadV2)") (class "Default")
      (node (ref "F18") (pin "V2") (pinfunction "V2_V2") (pintype "output"))
    )
    (net (code "1993") (name "unconnected-(H30-PadD1)") (class "Default")
      (node (ref "H30") (pin "D1") (pinfunction "D1_D1") (pintype "output"))
    )
    (net (code "1994") (name "unconnected-(H30-PadE1)") (class "Default")
      (node (ref "H30") (pin "E1") (pinfunction "E1_E1") (pintype "output"))
    )
    (net (code "1995") (name "unconnected-(H30-PadK1)") (class "Default")
      (node (ref "H30") (pin "K1") (pinfunction "K1_K1") (pintype "output"))
    )
    (net (code "1996") (name "unconnected-(HJ26-PadAJ1)") (class "Default")
      (node (ref "HJ26") (pin "AJ1") (pinfunction "AJ1_AJ1") (pintype "output"))
    )
    (net (code "1997") (name "unconnected-(HJ26-PadAJ2)") (class "Default")
      (node (ref "HJ26") (pin "AJ2") (pinfunction "AJ2_AJ2") (pintype "output"))
    )
    (net (code "1998") (name "unconnected-(HJ26-PadAM2)") (class "Default")
      (node (ref "HJ26") (pin "AM2") (pinfunction "AM2_AM2") (pintype "output"))
    )
    (net (code "1999") (name "unconnected-(HJ26-PadAT2)") (class "Default")
      (node (ref "HJ26") (pin "AT2") (pinfunction "AT2_AT2") (pintype "output"))
    )
    (net (code "2000") (name "unconnected-(HJ27D-AM-PadAM2)") (class "Default")
      (node (ref "HJ27") (pin "AM2") (pinfunction "AM_AM2") (pintype "output"))
    )
    (net (code "2001") (name "unconnected-(HJ27D-AP-PadAP2)") (class "Default")
      (node (ref "HJ27") (pin "AP2") (pinfunction "AP_AP2") (pintype "output"))
    )
    (net (code "2002") (name "unconnected-(HJ28-PadAJ1)") (class "Default")
      (node (ref "HJ28") (pin "AJ1") (pinfunction "AJ1_AJ1") (pintype "output"))
    )
    (net (code "2003") (name "unconnected-(HJ28-PadAJ2)") (class "Default")
      (node (ref "HJ28") (pin "AJ2") (pinfunction "AJ2_AJ2") (pintype "output"))
    )
    (net (code "2004") (name "unconnected-(HJ28-PadAS1)") (class "Default")
      (node (ref "HJ28") (pin "AS1") (pinfunction "AS1_AS1") (pintype "output"))
    )
    (net (code "2005") (name "unconnected-(HJ28-PadAU2)") (class "Default")
      (node (ref "HJ28") (pin "AU2") (pinfunction "AU2_AU2") (pintype "output"))
    )
    (net (code "2006") (name "unconnected-(HJ29-PadAM2)") (class "Default")
      (node (ref "HJ29") (pin "AM2") (pinfunction "AM2_AM2") (pintype "output"))
    )
    (net (code "2007") (name "unconnected-(HJ29-PadAP2)") (class "Default")
      (node (ref "HJ29") (pin "AP2") (pinfunction "AP2_AP2") (pintype "output"))
    )
    (net (code "2008") (name "unconnected-(HJ29-PadAU2)") (class "Default")
      (node (ref "HJ29") (pin "AU2") (pinfunction "AU2_AU2") (pintype "output"))
    )
    (net (code "2009") (name "unconnected-(HJ29-PadBD2)") (class "Default")
      (node (ref "HJ29") (pin "BD2") (pinfunction "BD2_BD2") (pintype "output"))
    )
    (net (code "2010") (name "unconnected-(HJ29-PadBJ2)") (class "Default")
      (node (ref "HJ29") (pin "BJ2") (pinfunction "BJ2_BJ2") (pintype "output"))
    )
    (net (code "2011") (name "unconnected-(HJ29-PadBK2)") (class "Default")
      (node (ref "HJ29") (pin "BK2") (pinfunction "BK2_BK2") (pintype "output"))
    )
    (net (code "2012") (name "unconnected-(HJ29-PadBS2)") (class "Default")
      (node (ref "HJ29") (pin "BS2") (pinfunction "BS2_BS2") (pintype "output"))
    )
    (net (code "2013") (name "unconnected-(HJ31-PadAE2)") (class "Default")
      (node (ref "HJ31") (pin "AE2") (pinfunction "AE2_AE2") (pintype "output"))
    )
    (net (code "2014") (name "unconnected-(HJ31-PadBF1)") (class "Default")
      (node (ref "HJ31") (pin "BF1") (pinfunction "BF1_BF1") (pintype "output"))
    )
    (net (code "2015") (name "unconnected-(HJ31-PadBH1)") (class "Default")
      (node (ref "HJ31") (pin "BH1") (pinfunction "BH1_BH1") (pintype "output"))
    )
    (net (code "2016") (name "unconnected-(HJ31-PadBH2)") (class "Default")
      (node (ref "HJ31") (pin "BH2") (pinfunction "BH2_BH2") (pintype "output"))
    )
    (net (code "2017") (name "unconnected-(HJ31-PadBM1)") (class "Default")
      (node (ref "HJ31") (pin "BM1") (pinfunction "BM1_BM1") (pintype "output"))
    )
    (net (code "2018") (name "unconnected-(HJ31-PadBR1)") (class "Default")
      (node (ref "HJ31") (pin "BR1") (pinfunction "BR1_BR1") (pintype "output"))
    )
    (net (code "2019") (name "unconnected-(J33-PadH1)") (class "Default")
      (node (ref "J33") (pin "H1") (pinfunction "H1_H1") (pintype "output"))
    )
    (net (code "2020") (name "unconnected-(J33-PadJ2)") (class "Default")
      (node (ref "J33") (pin "J2") (pinfunction "J2_J2") (pintype "output"))
    )
    (net (code "2021") (name "unconnected-(J33-PadL1)") (class "Default")
      (node (ref "J33") (pin "L1") (pinfunction "L1_L1") (pintype "output"))
    )
    (net (code "2022") (name "unconnected-(J33-PadM1)") (class "Default")
      (node (ref "J33") (pin "M1") (pinfunction "M1_M1") (pintype "output"))
    )
    (net (code "2023") (name "unconnected-(J33-PadS1)") (class "Default")
      (node (ref "J33") (pin "S1") (pinfunction "S1_S1") (pintype "output"))
    )
    (net (code "2024") (name "unconnected-(J33-PadT2)") (class "Default")
      (node (ref "J33") (pin "T2") (pinfunction "T2_T2") (pintype "output"))
    )
    (net (code "2025") (name "unconnected-(J33-PadU1)") (class "Default")
      (node (ref "J33") (pin "U1") (pinfunction "U1_U1") (pintype "output"))
    )
  )
)
